# BEP32_12nutzen.net
KiCad netlist of a schematic drawn in EAGLE
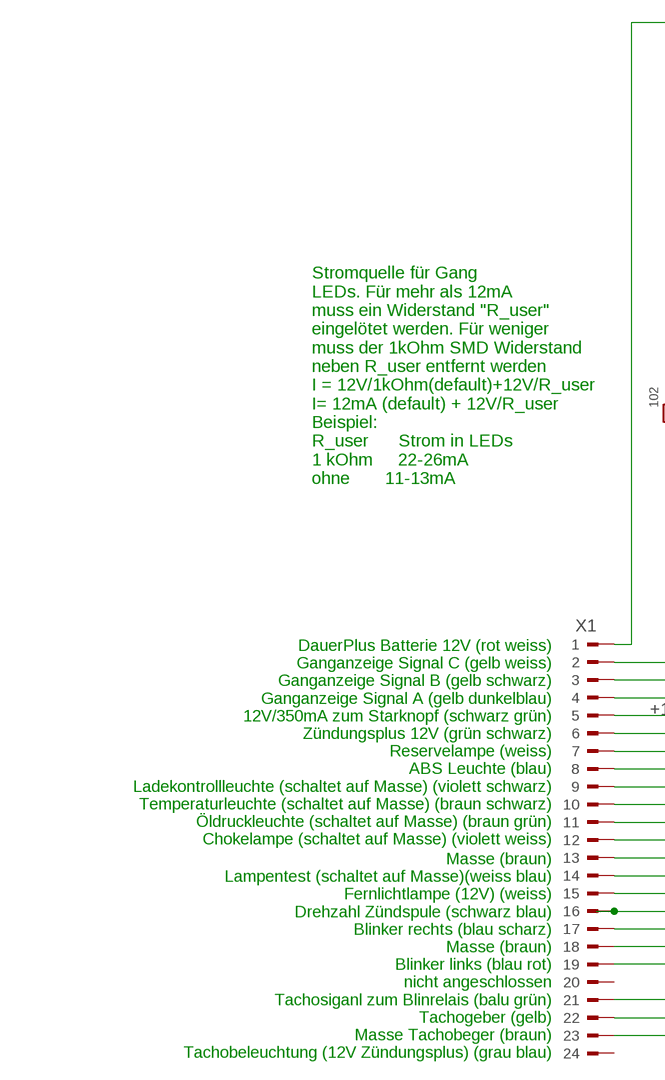
[diagram p0: schematic, sheet 1, part 1 of 2]
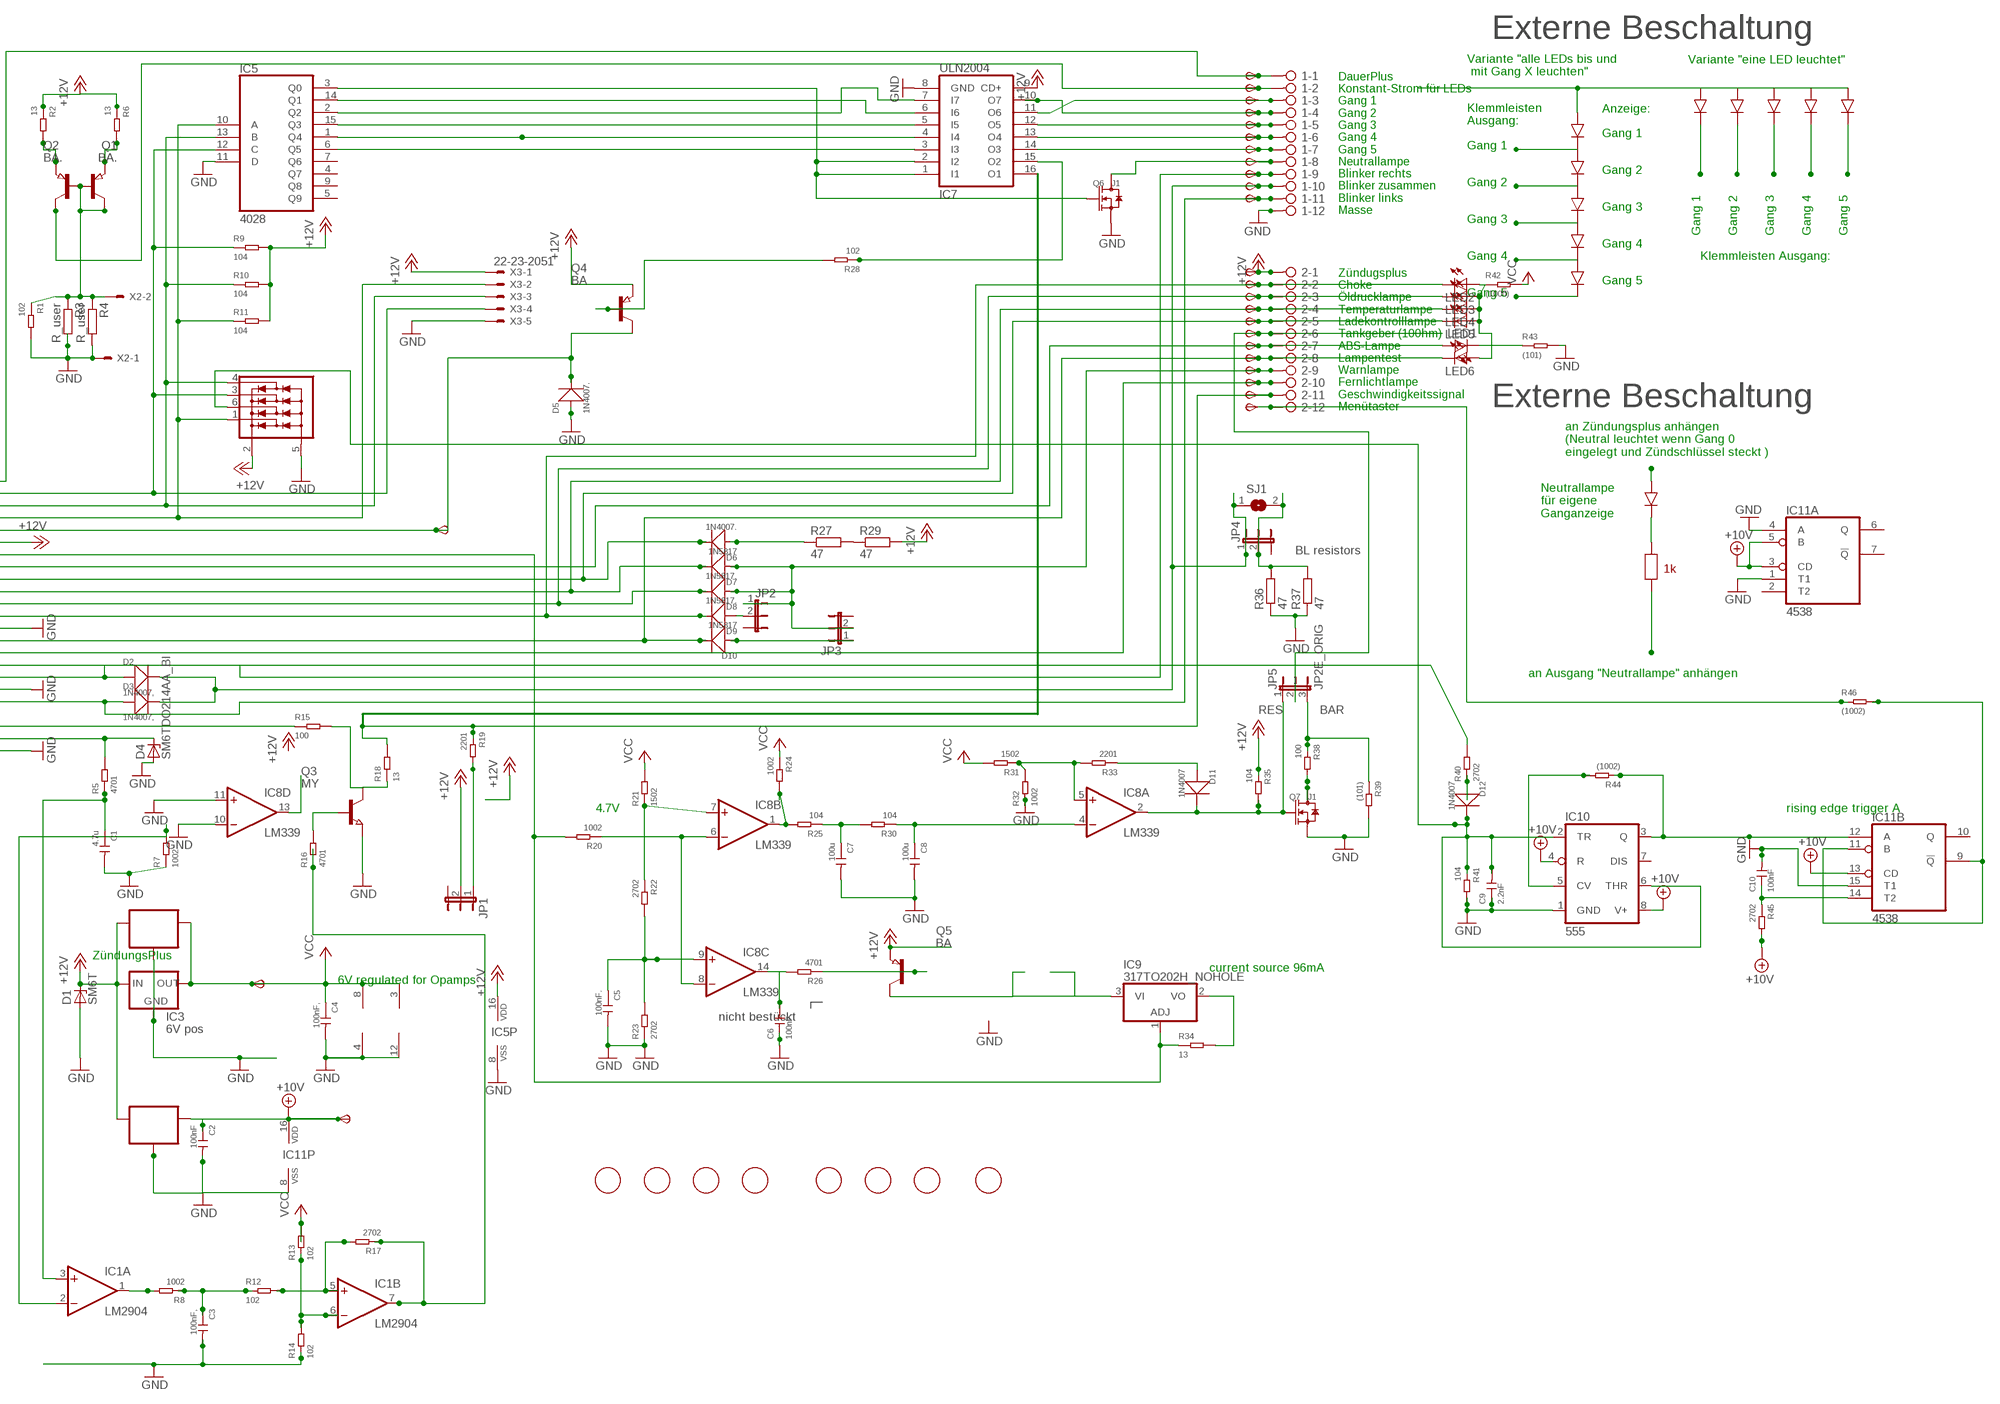
[diagram p1: schematic, sheet 1, part 2 of 2]
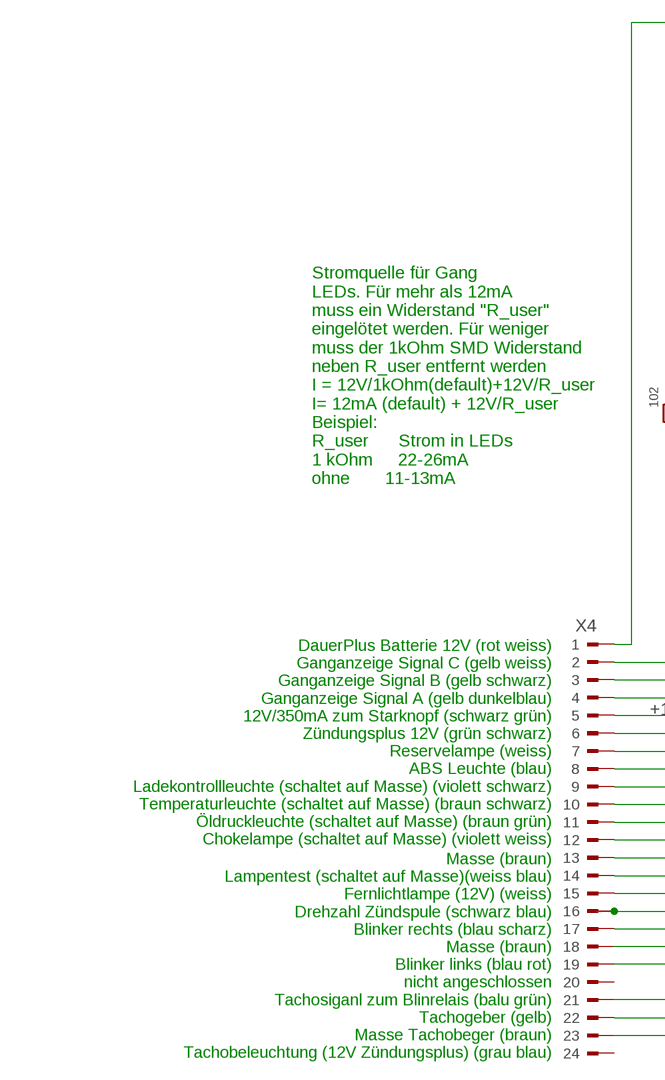
[diagram p2: schematic, sheet 2, part 1 of 2]
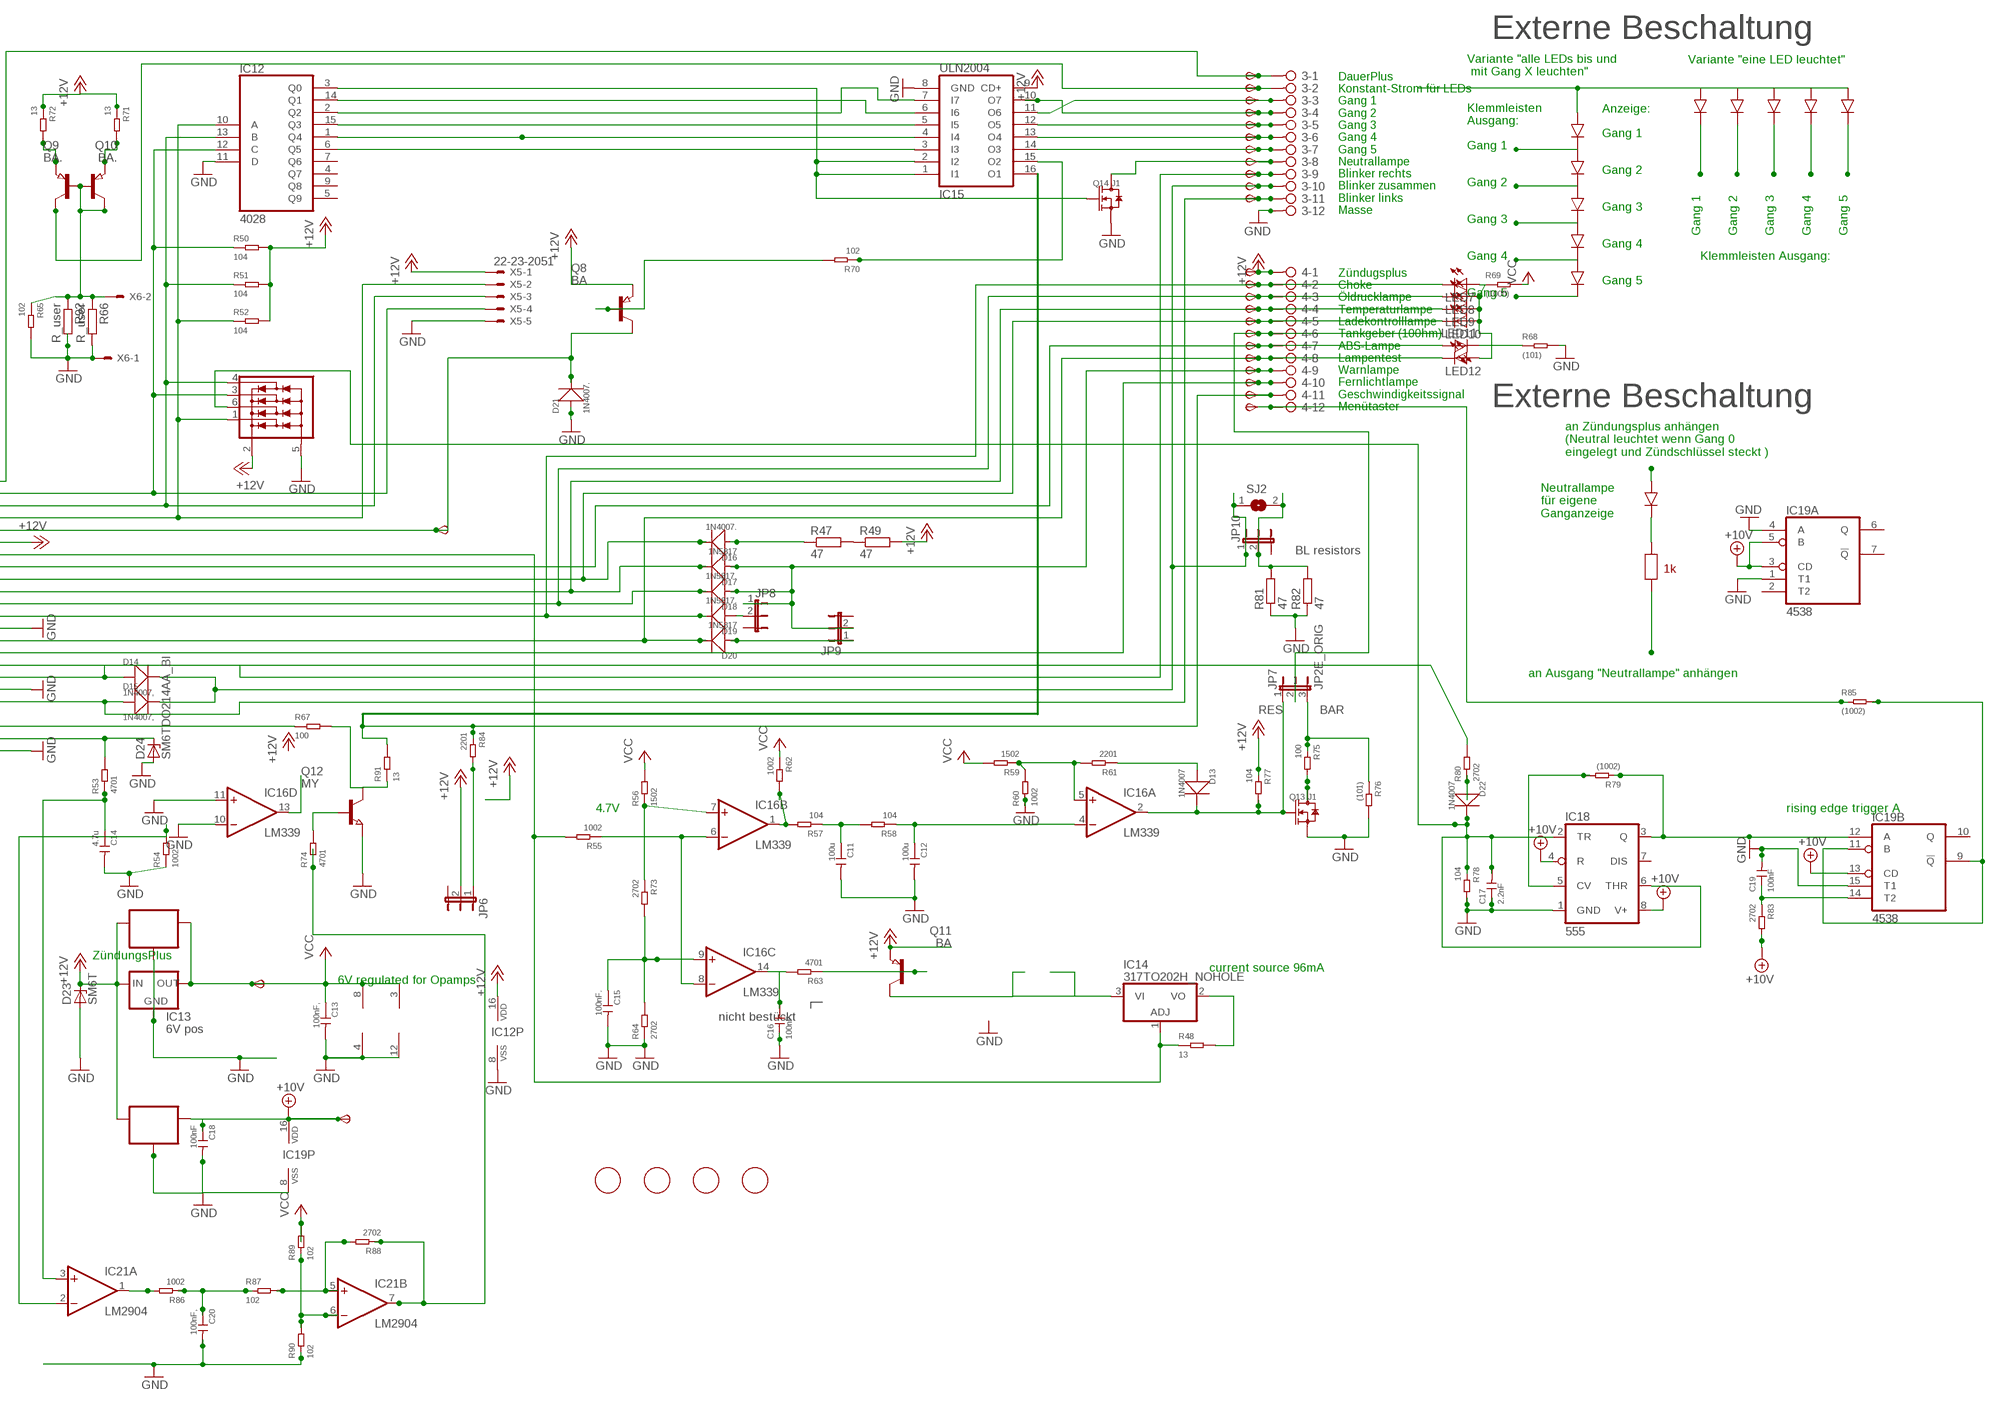
[diagram p3: schematic, sheet 2, part 2 of 2]
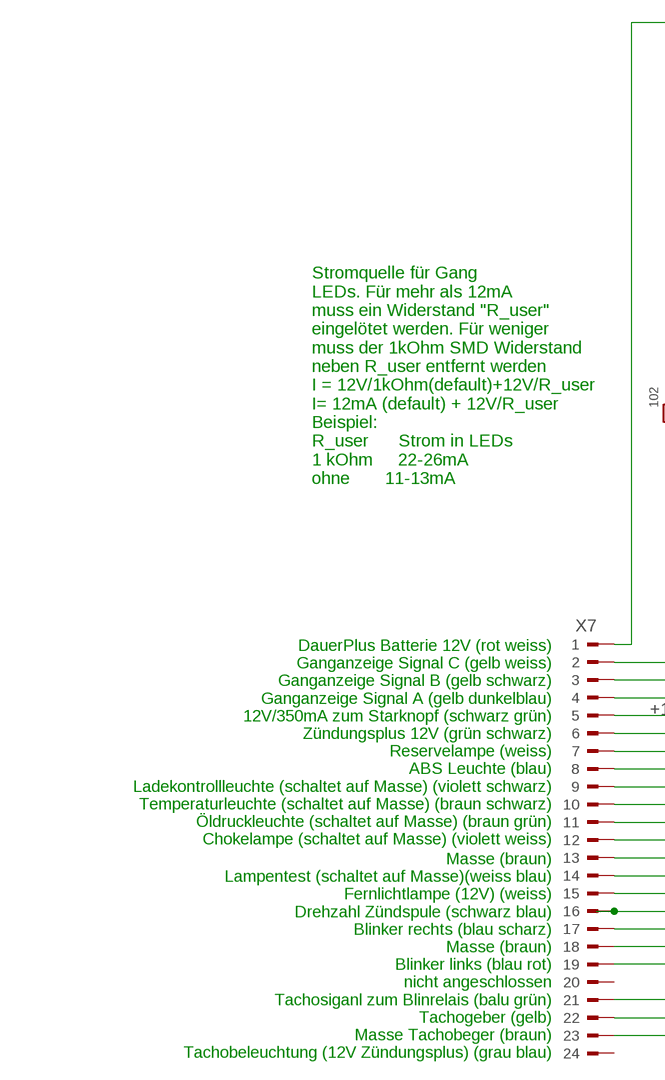
[diagram p4: schematic, sheet 3, part 1 of 2]
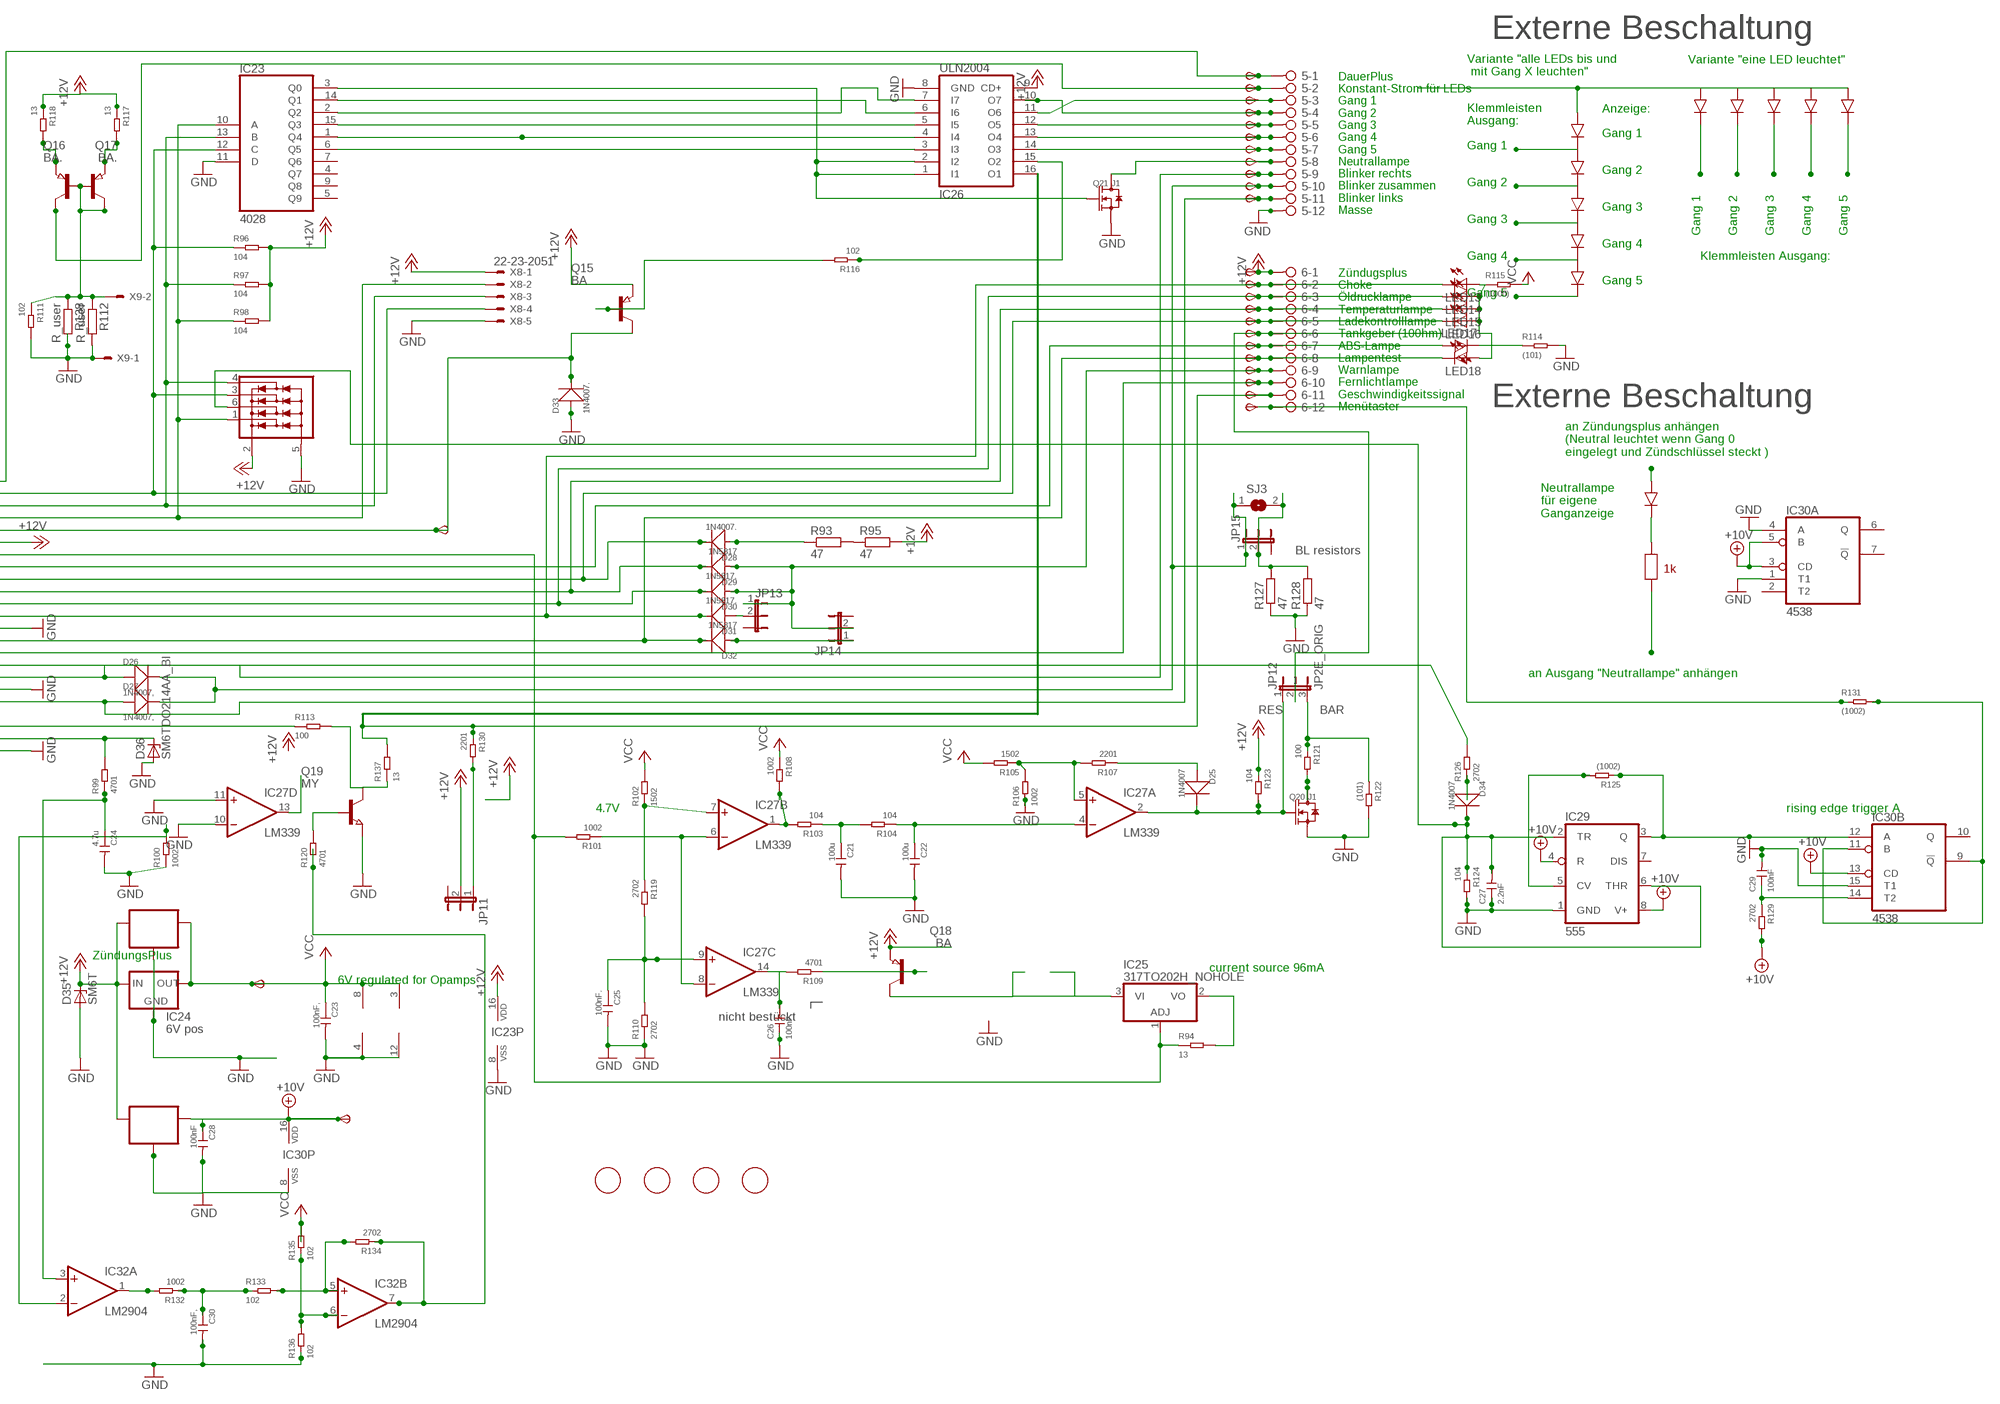
[diagram p5: schematic, sheet 3, part 2 of 2]
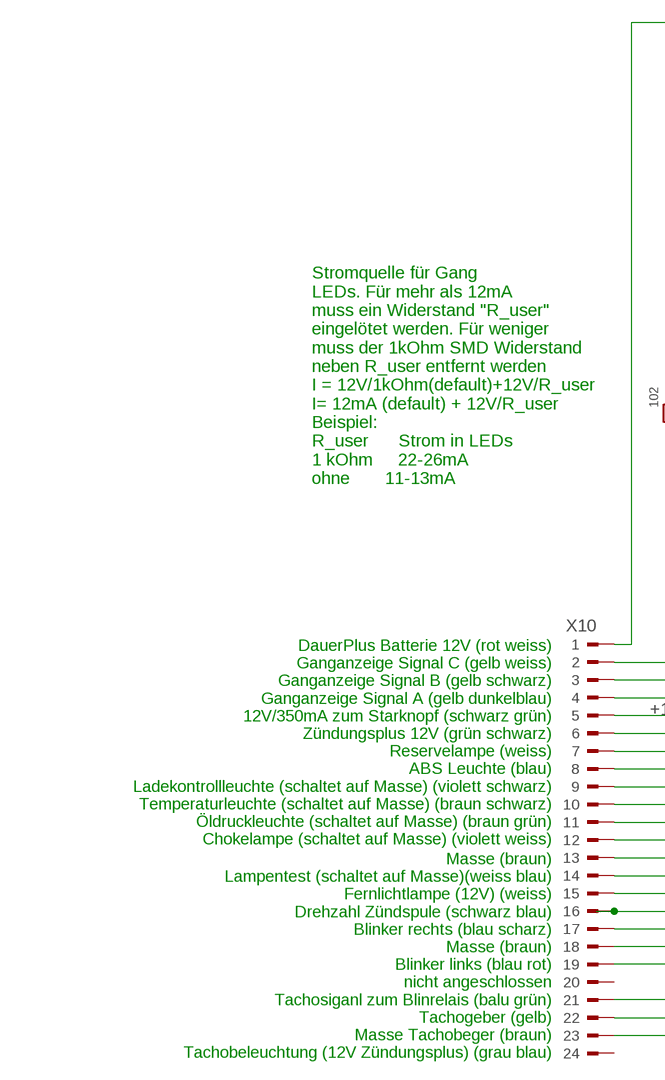
[diagram p6: schematic, sheet 4, part 1 of 2]
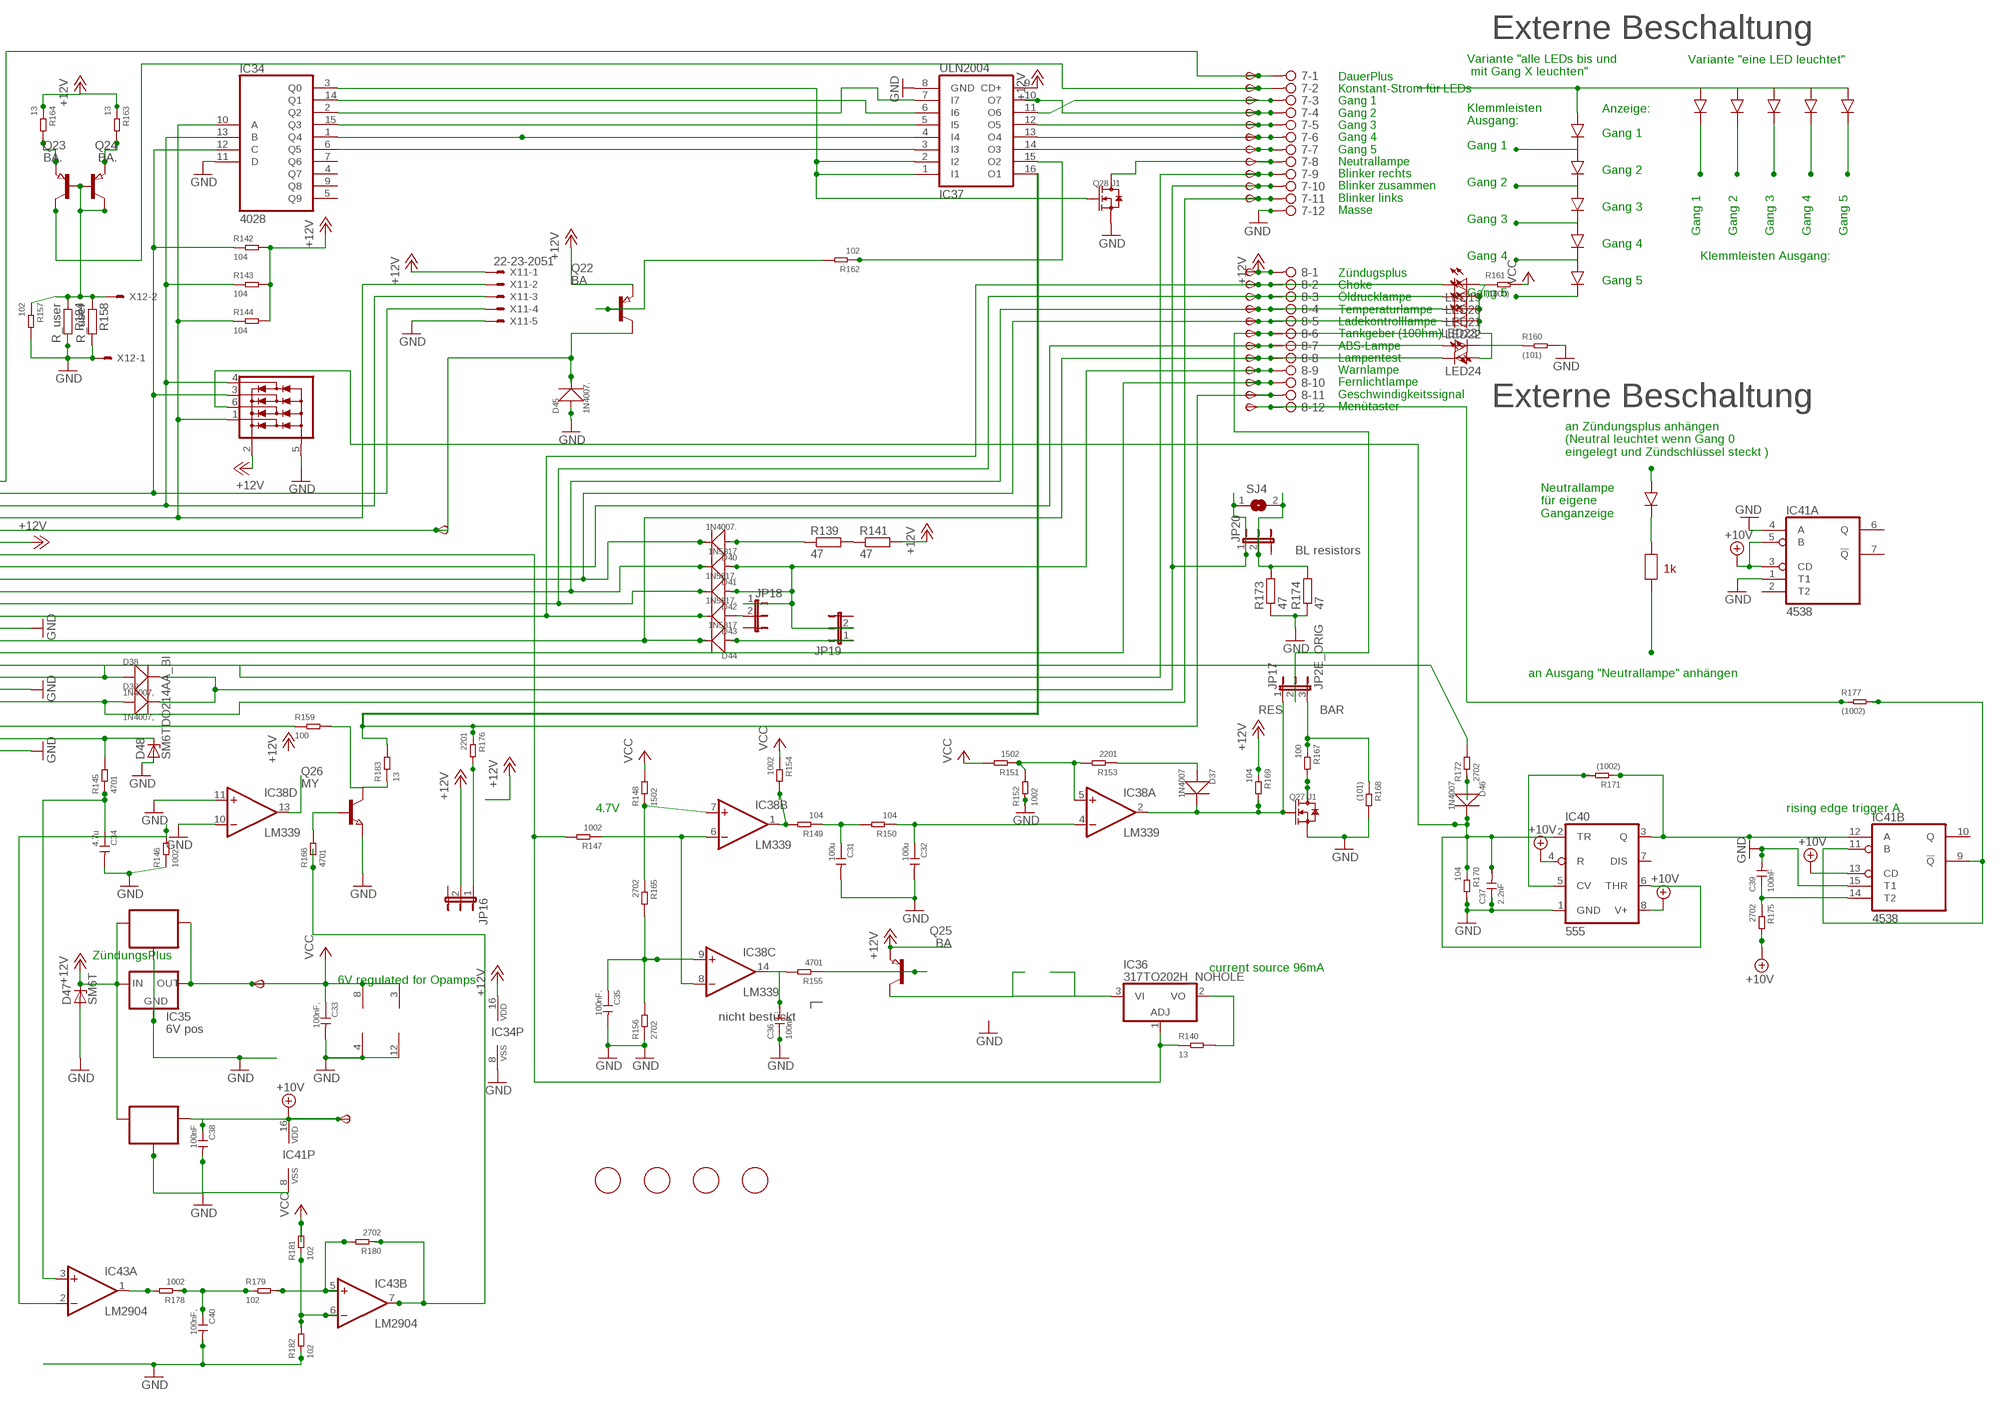
[diagram p7: schematic, sheet 4, part 2 of 2]
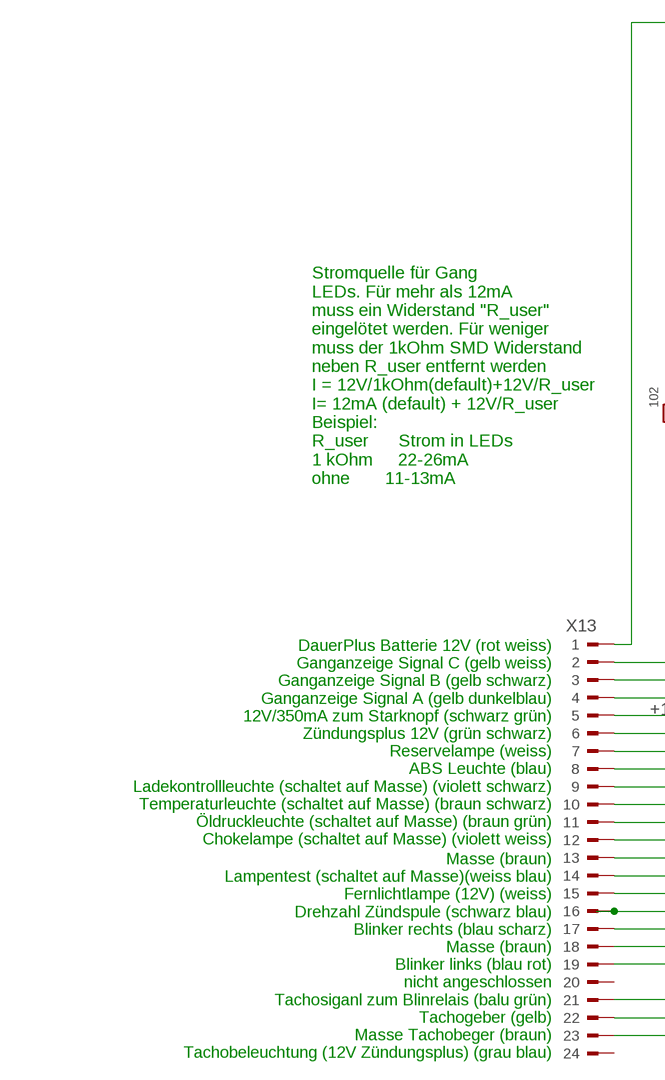
[diagram p8: schematic, sheet 5, part 1 of 2]
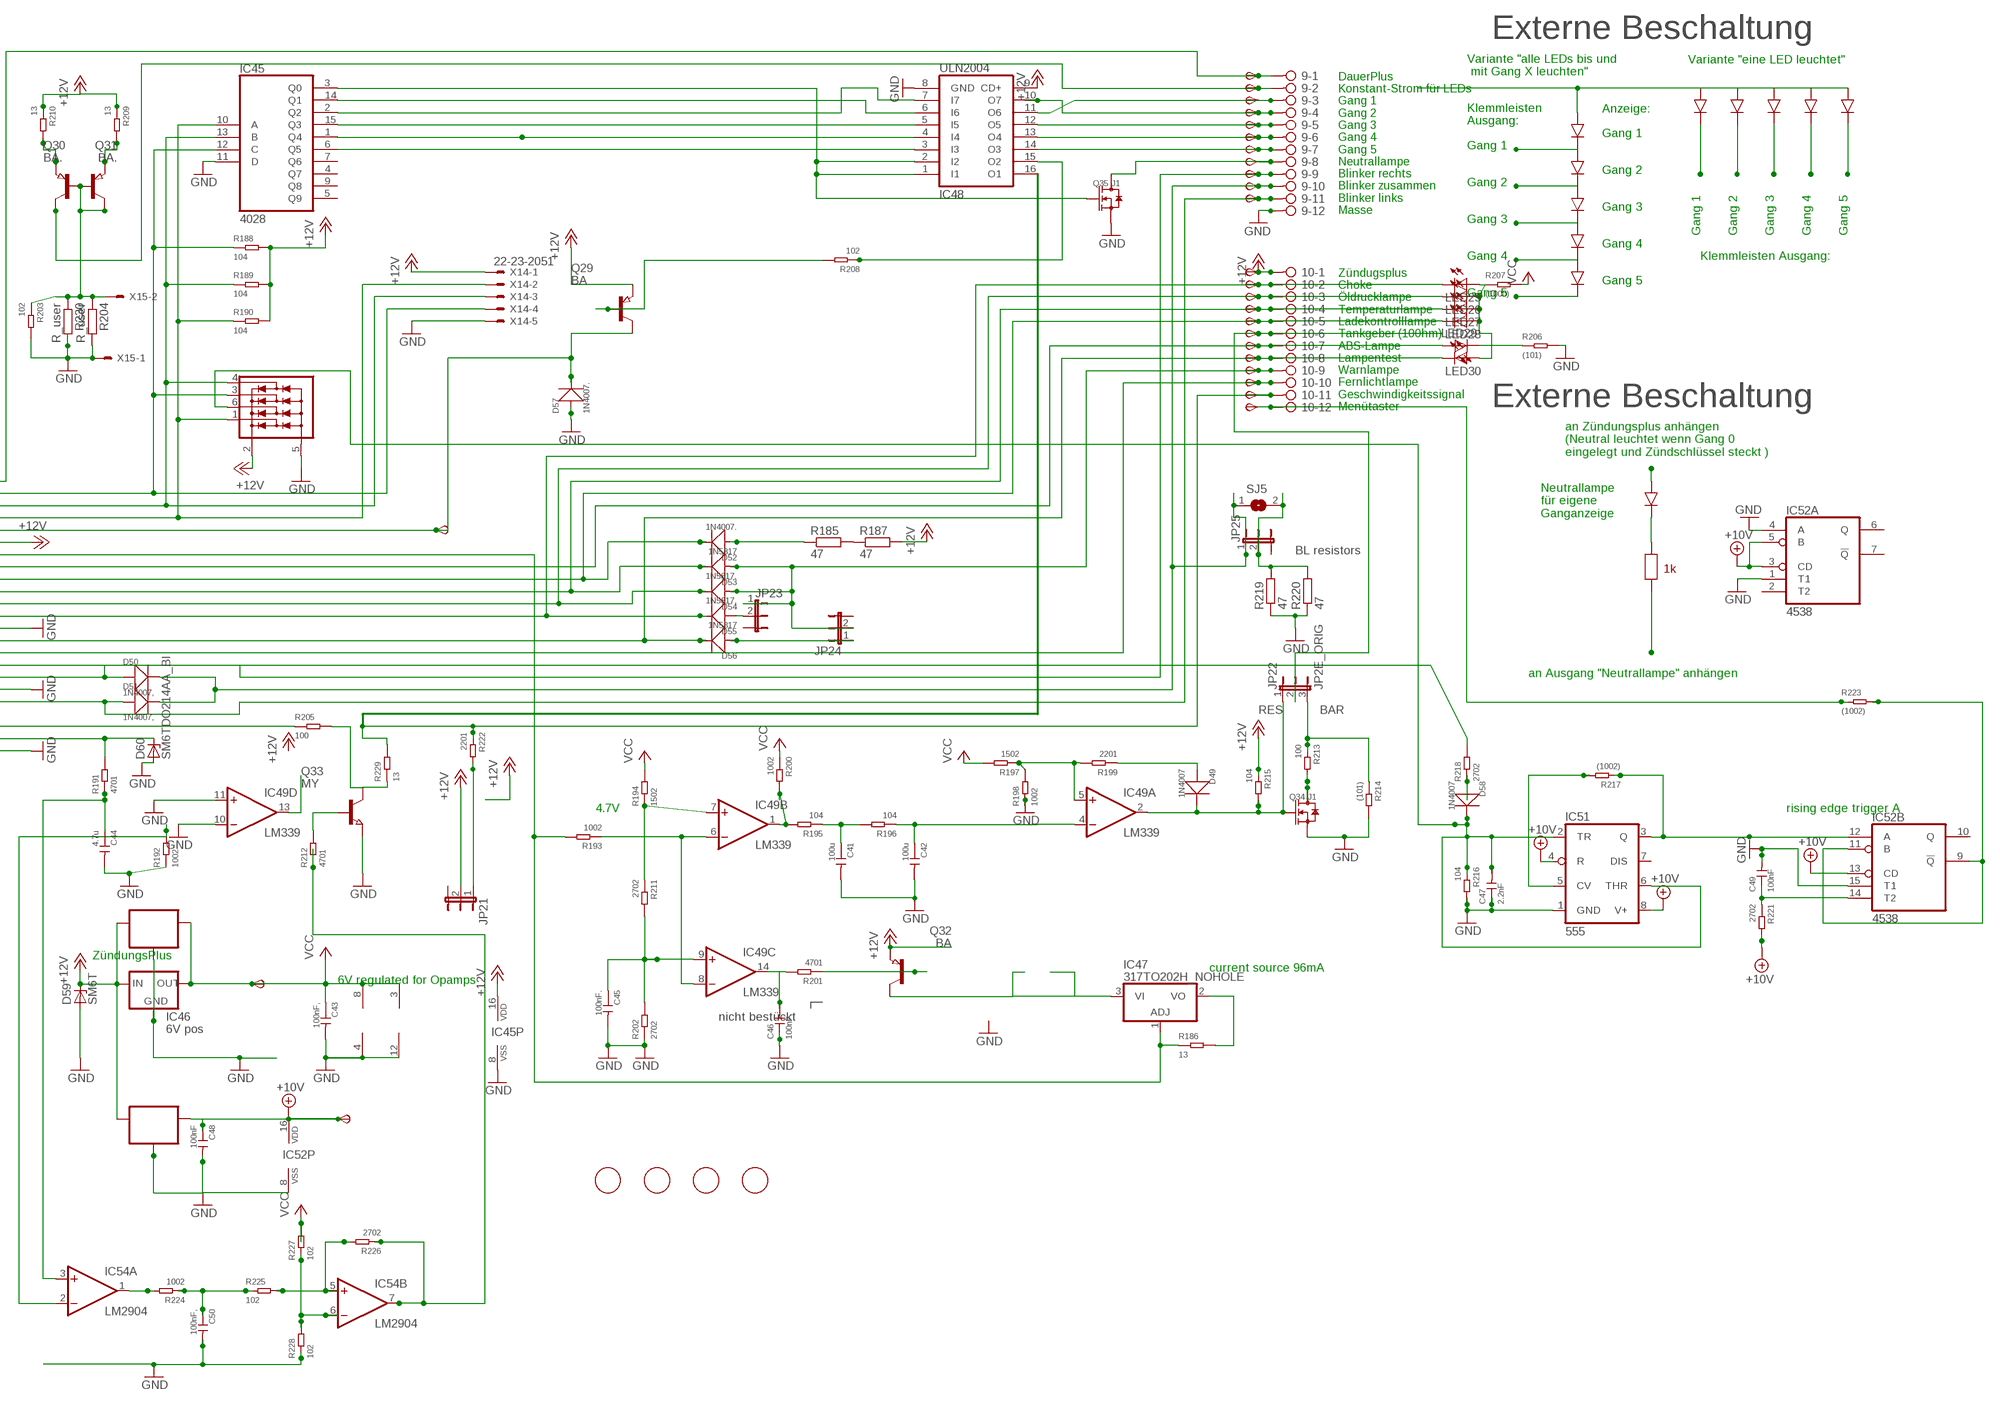
[diagram p9: schematic, sheet 5, part 2 of 2]
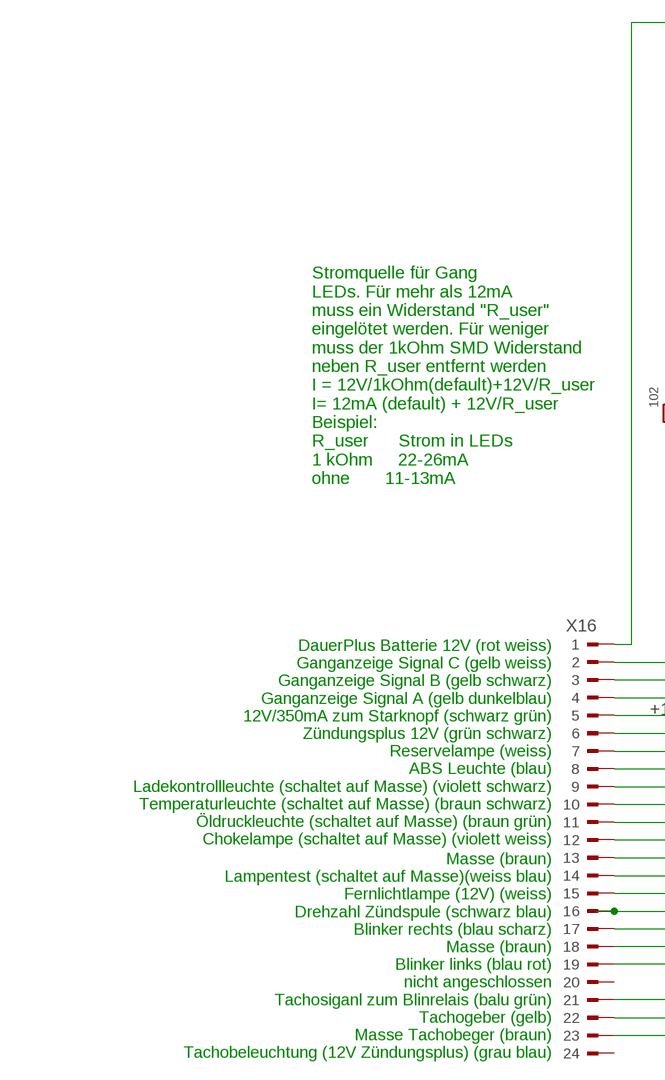
[diagram p10: schematic, sheet 6, part 1 of 2]
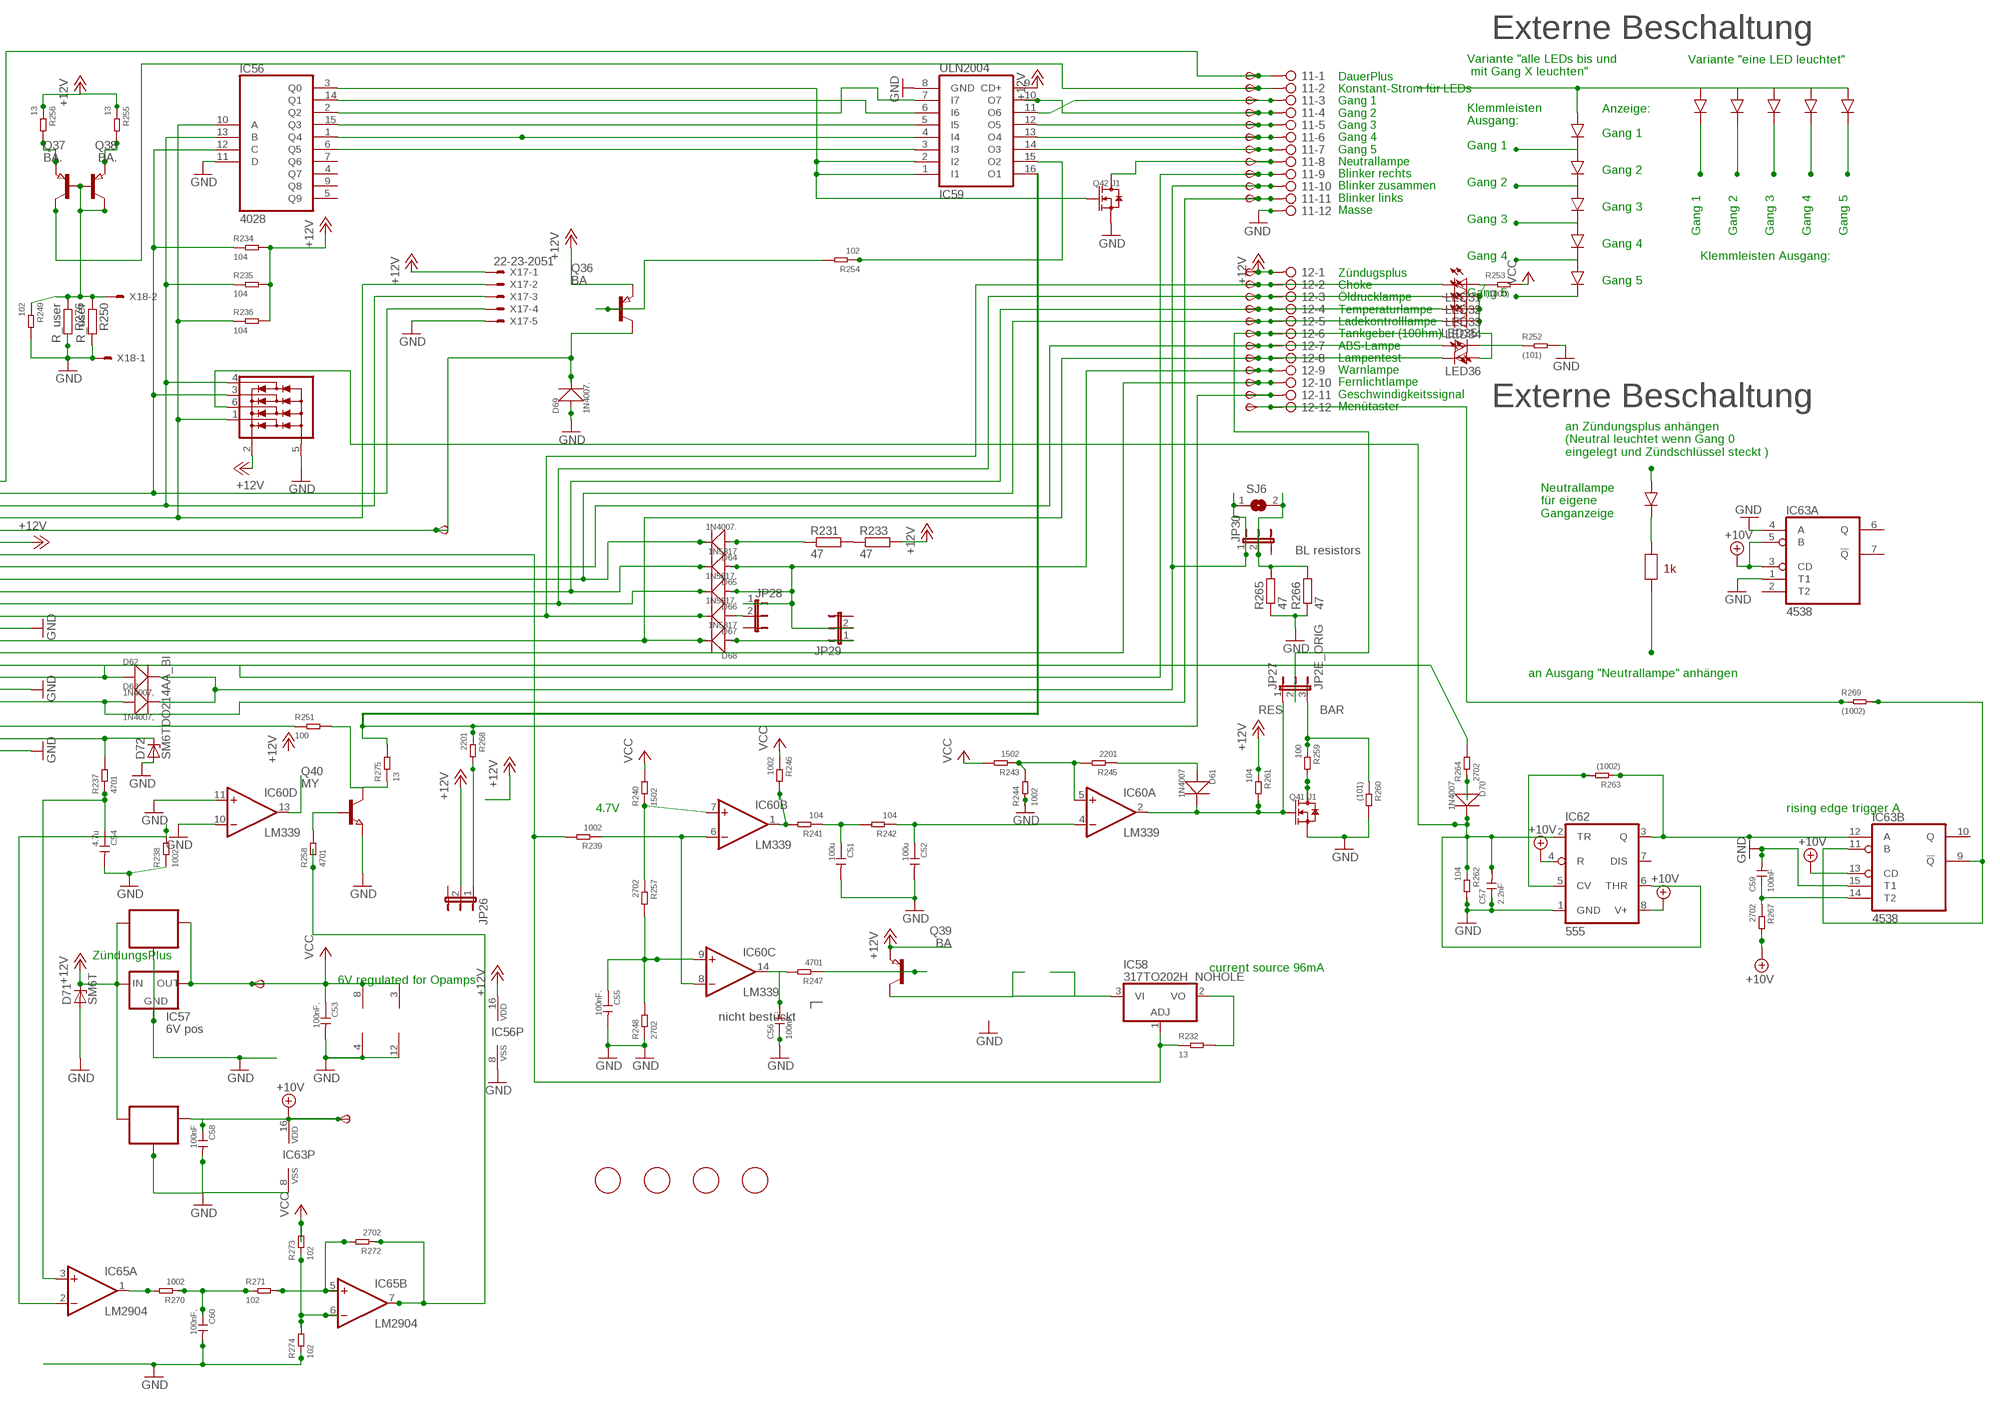
[diagram p11: schematic, sheet 6, part 2 of 2]
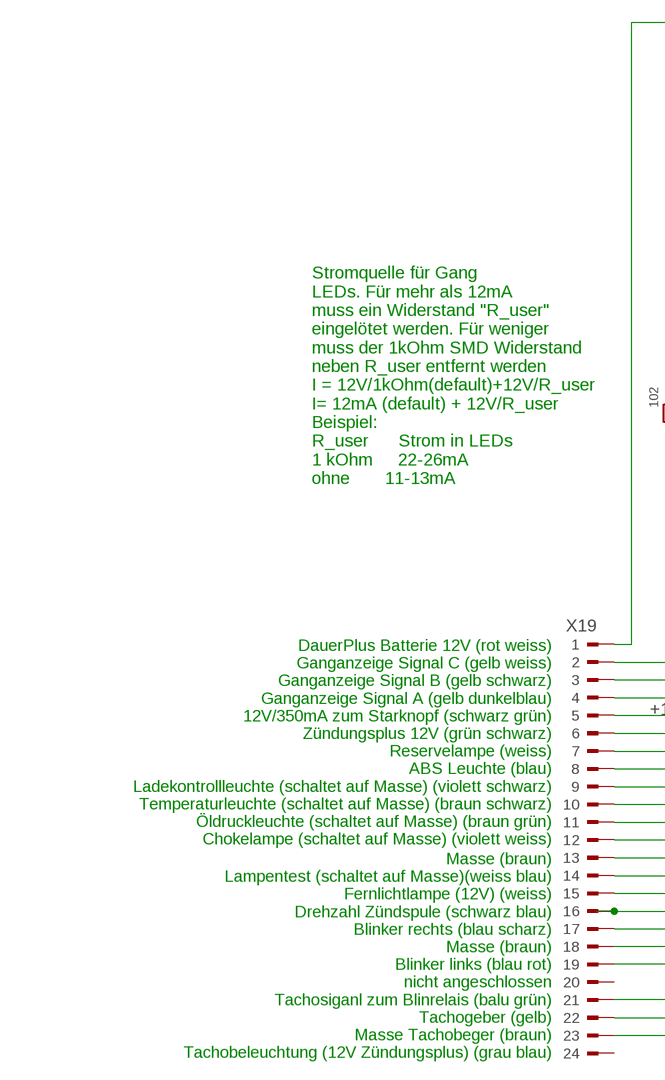
[diagram p12: schematic, sheet 7, part 1 of 2]
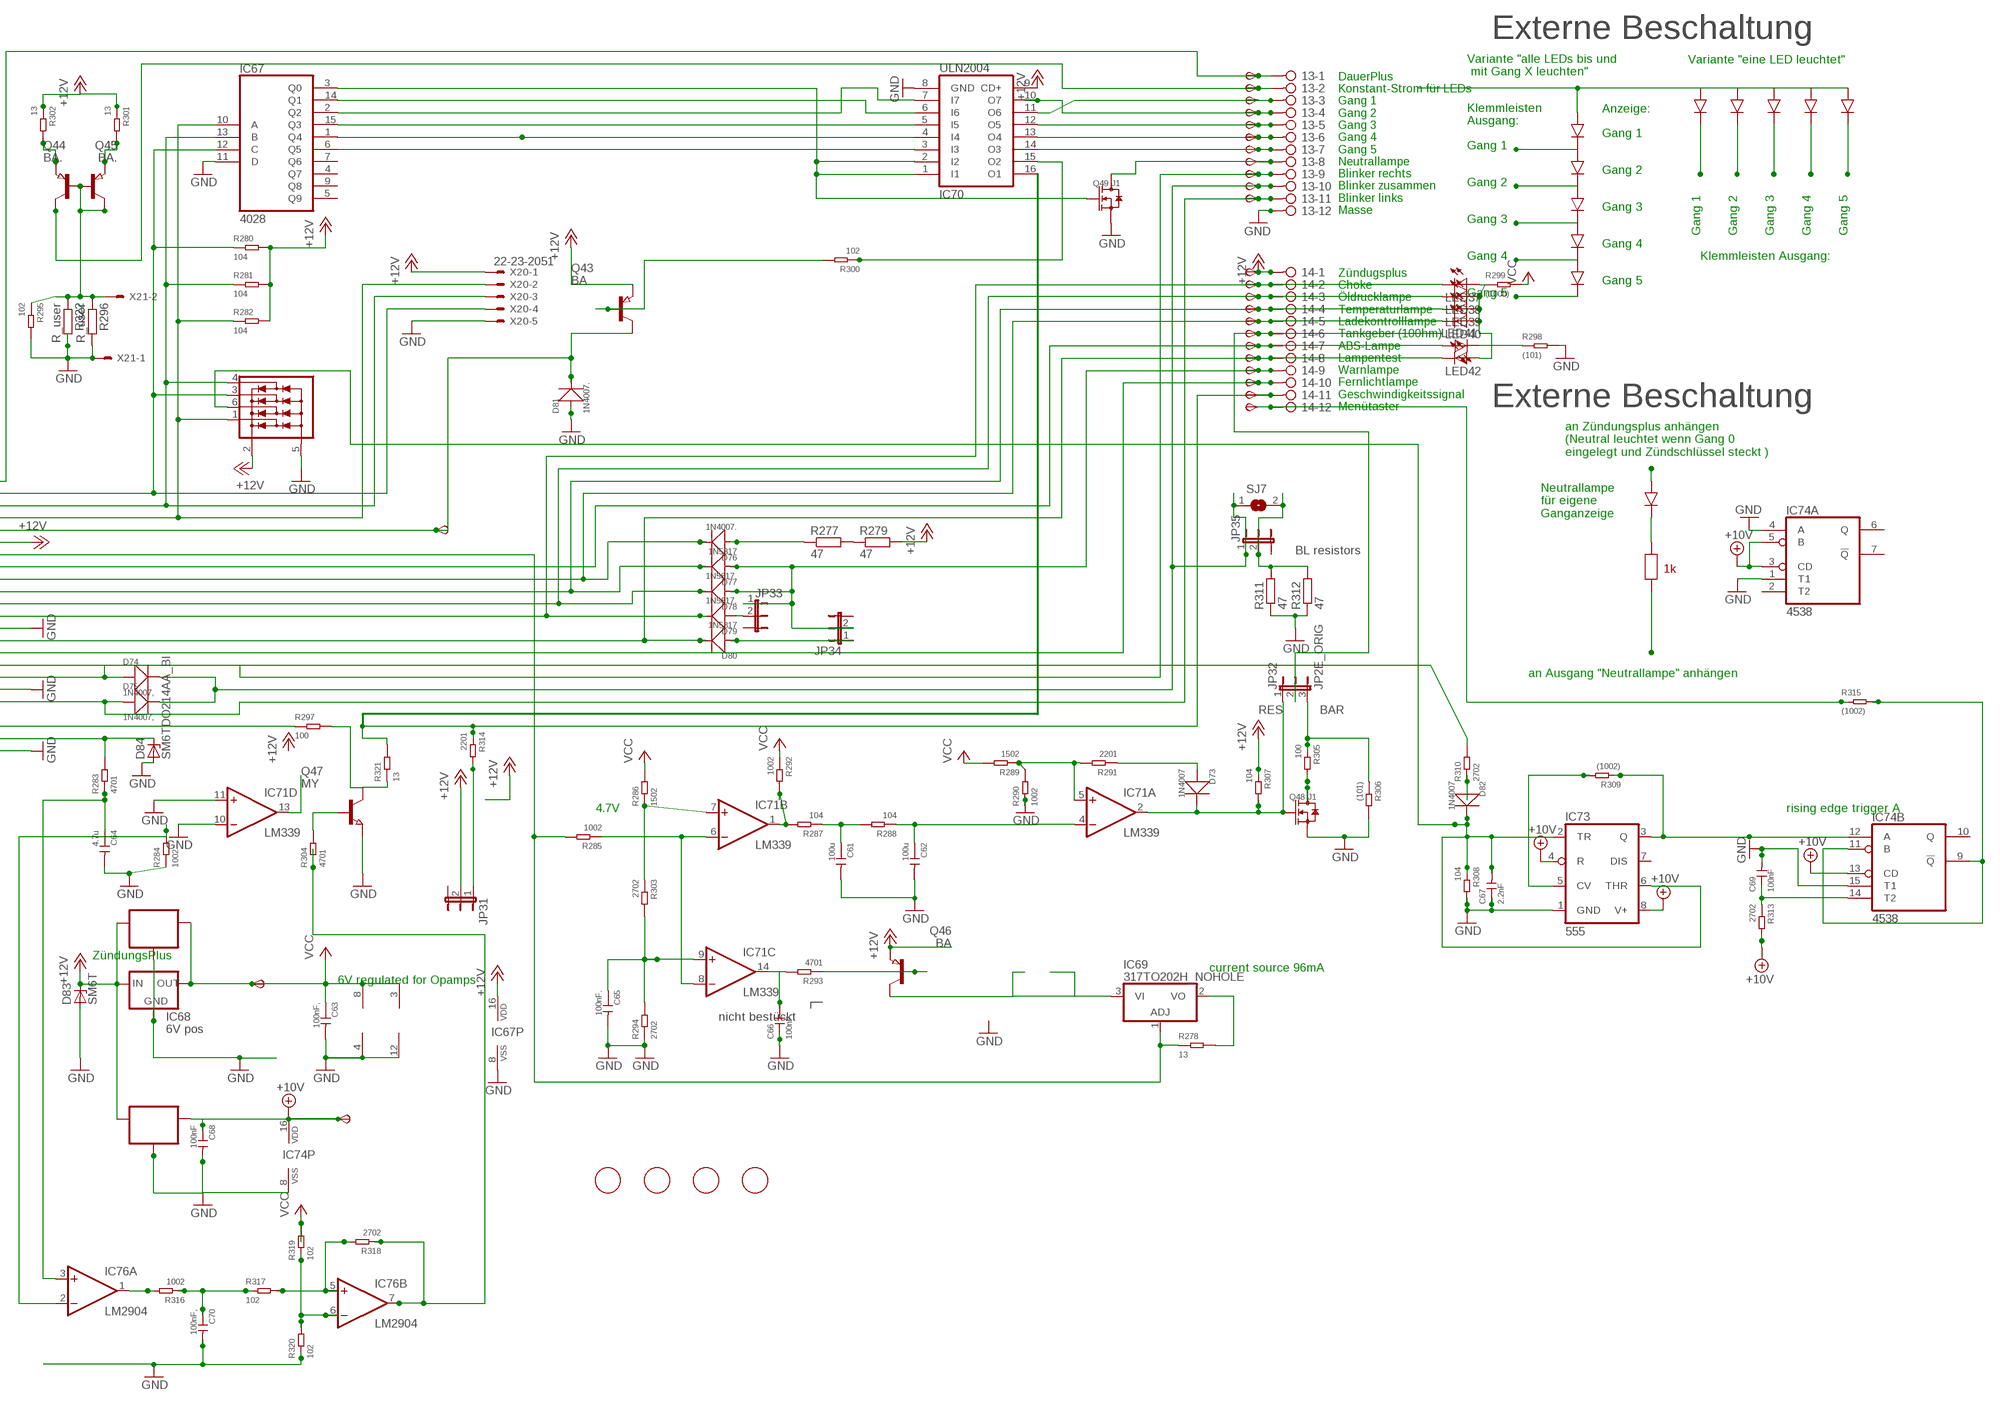
[diagram p13: schematic, sheet 7, part 2 of 2]
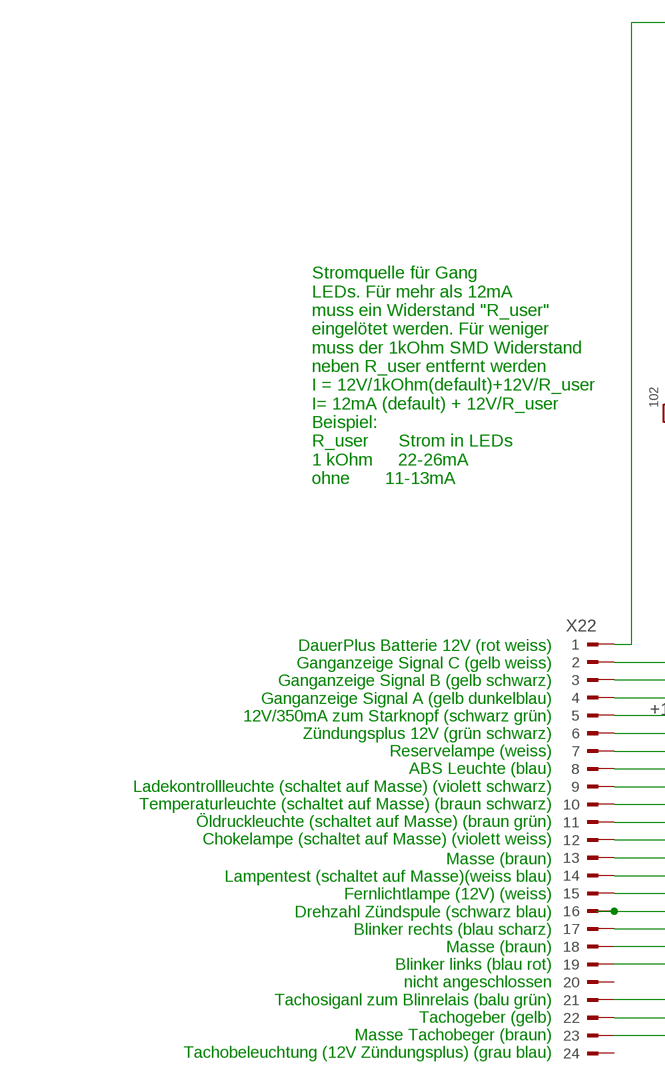
[diagram p14: schematic, sheet 8, part 1 of 2]
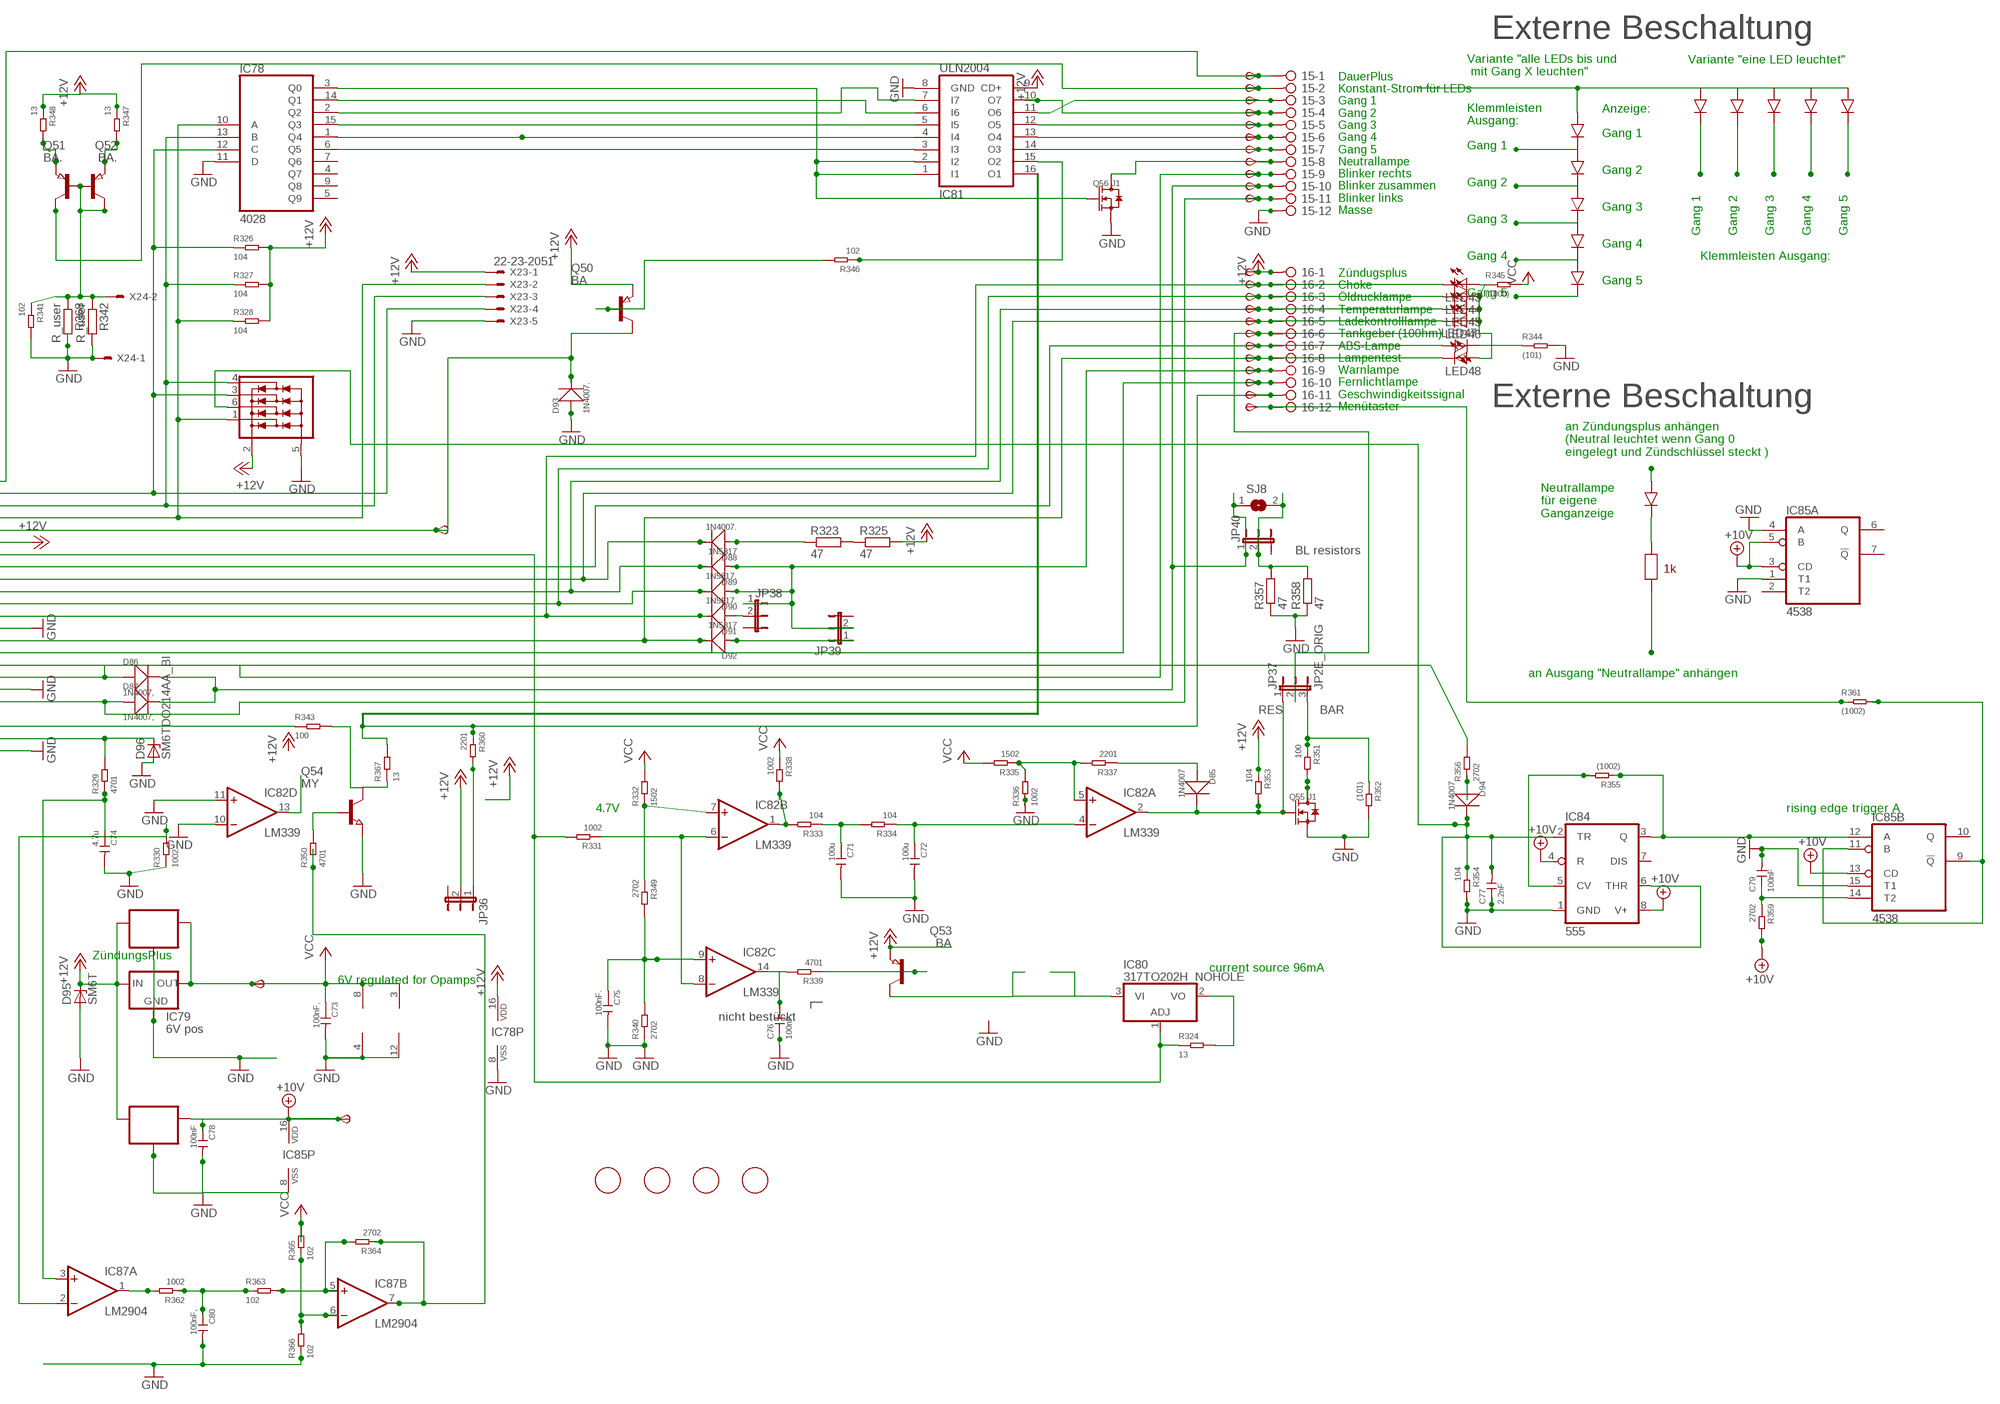
[diagram p15: schematic, sheet 8, part 2 of 2]
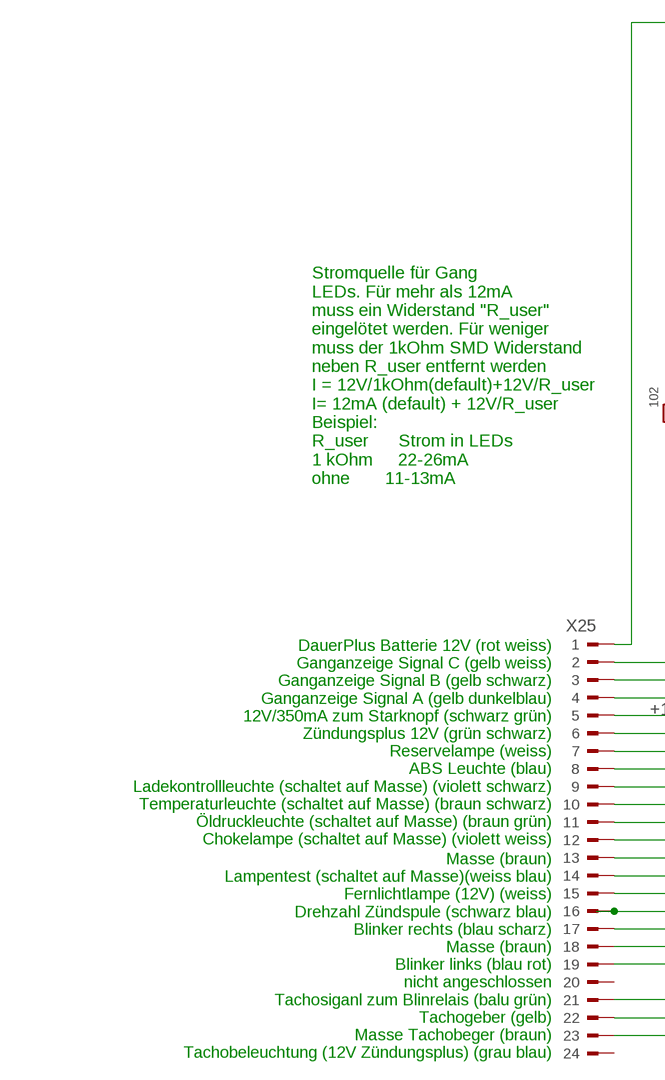
[diagram p16: schematic, sheet 9, part 1 of 2]
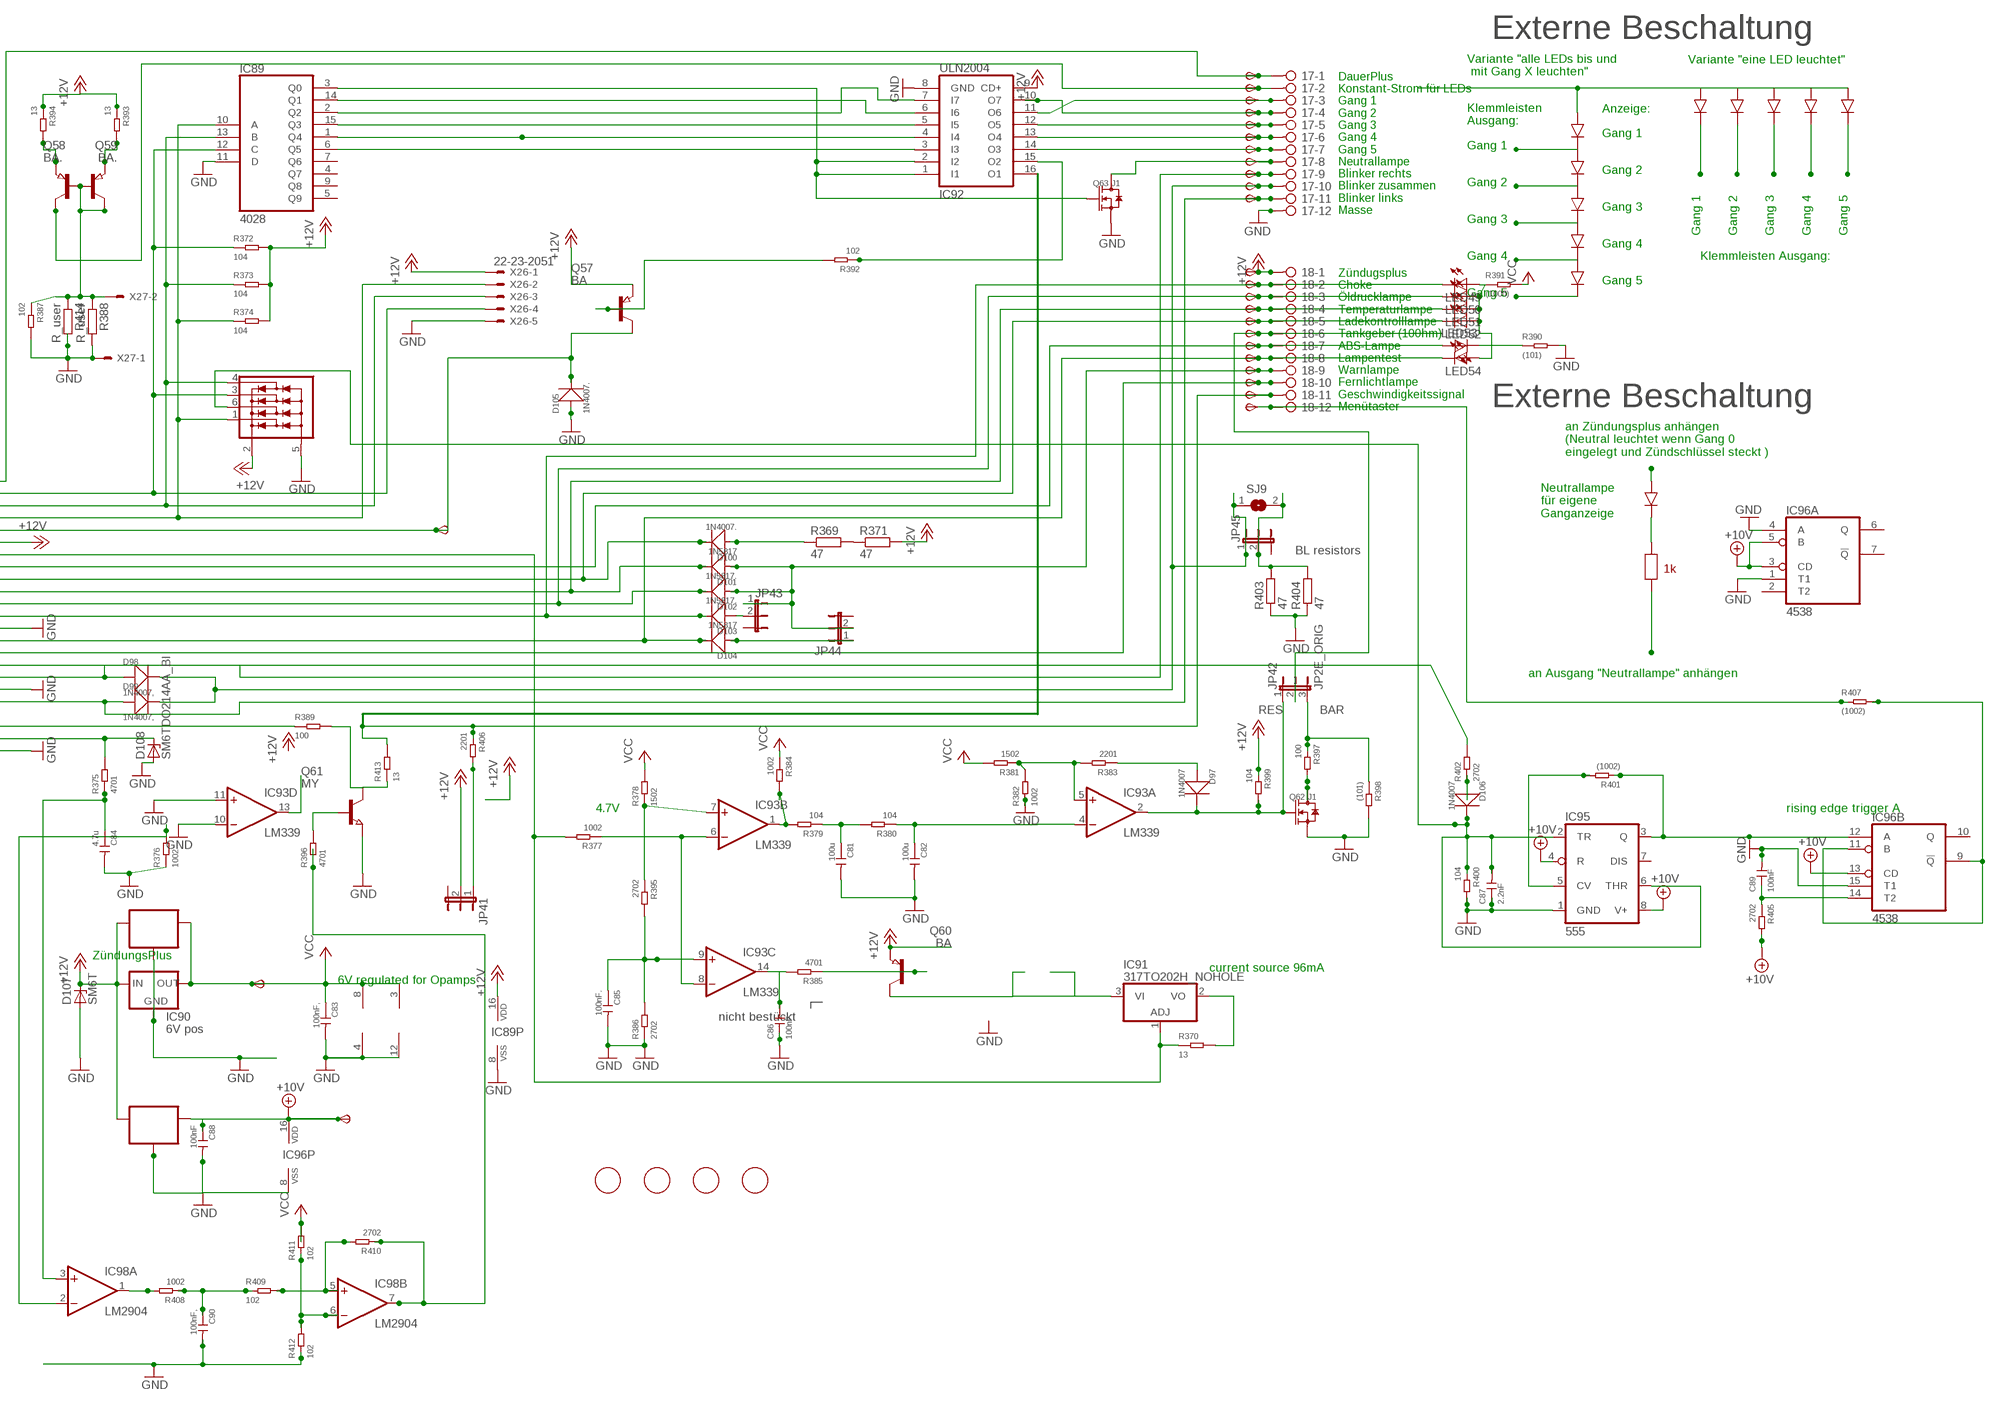
[diagram p17: schematic, sheet 9, part 2 of 2]
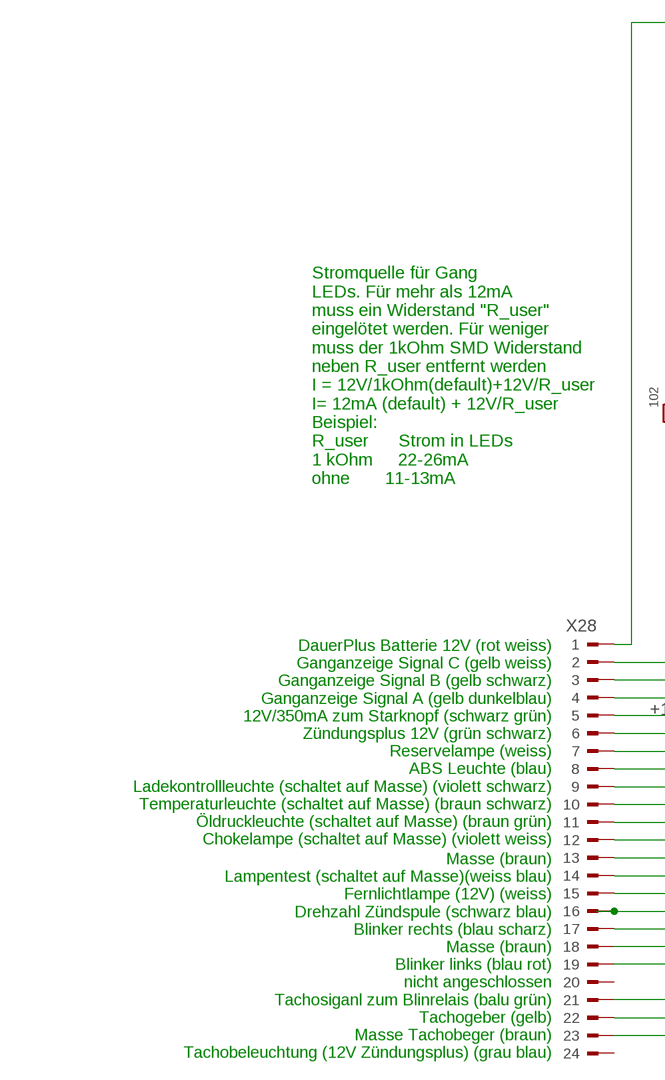
[diagram p18: schematic, sheet 10, part 1 of 2]
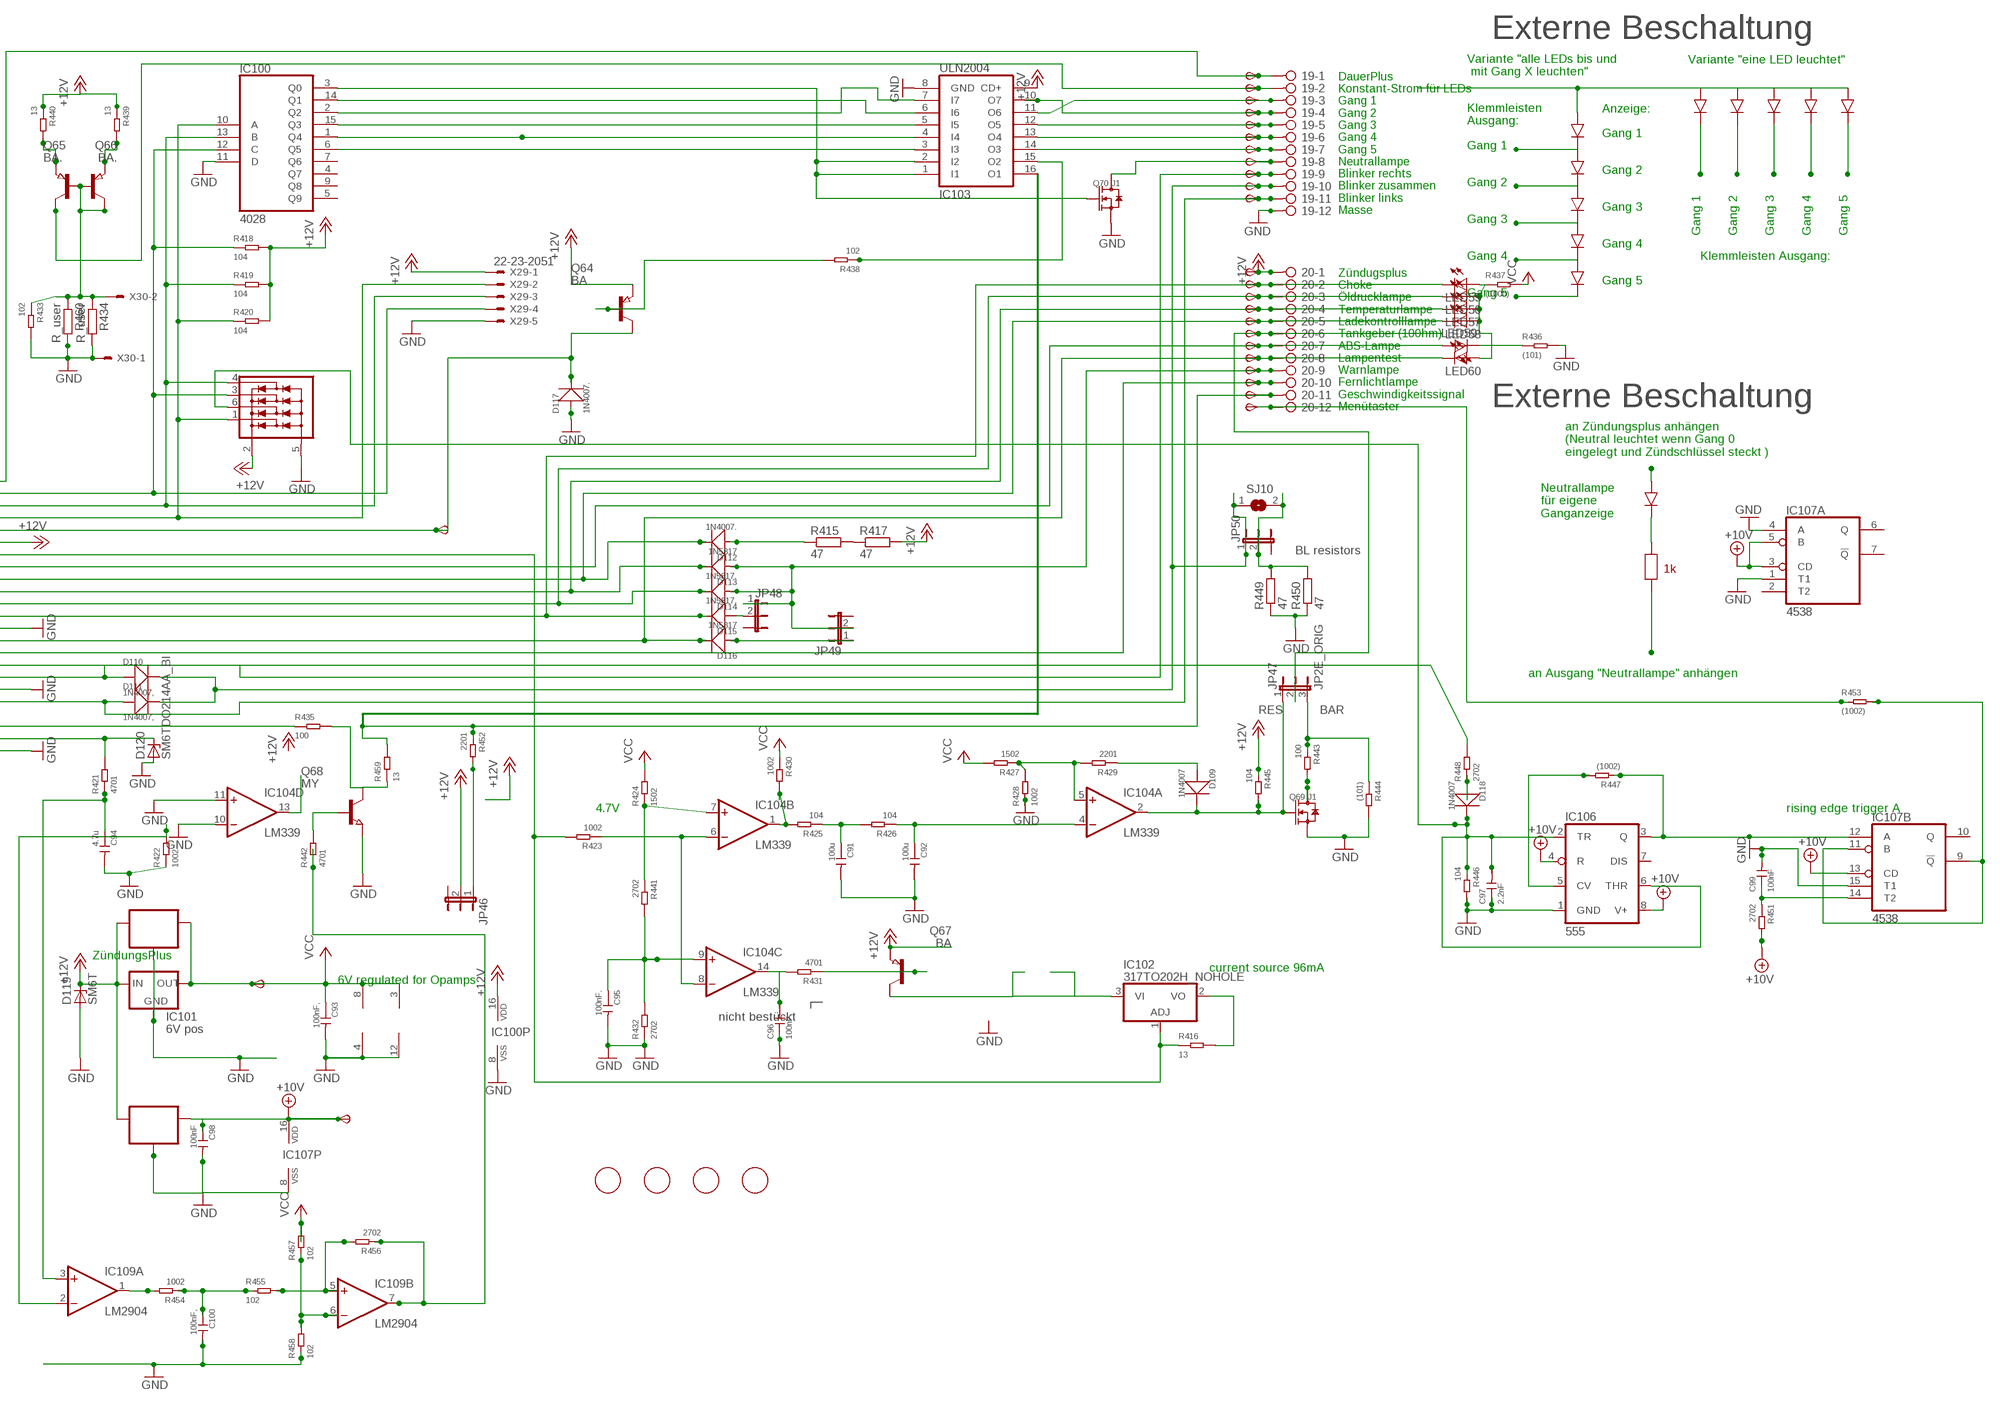
[diagram p19: schematic, sheet 10, part 2 of 2]
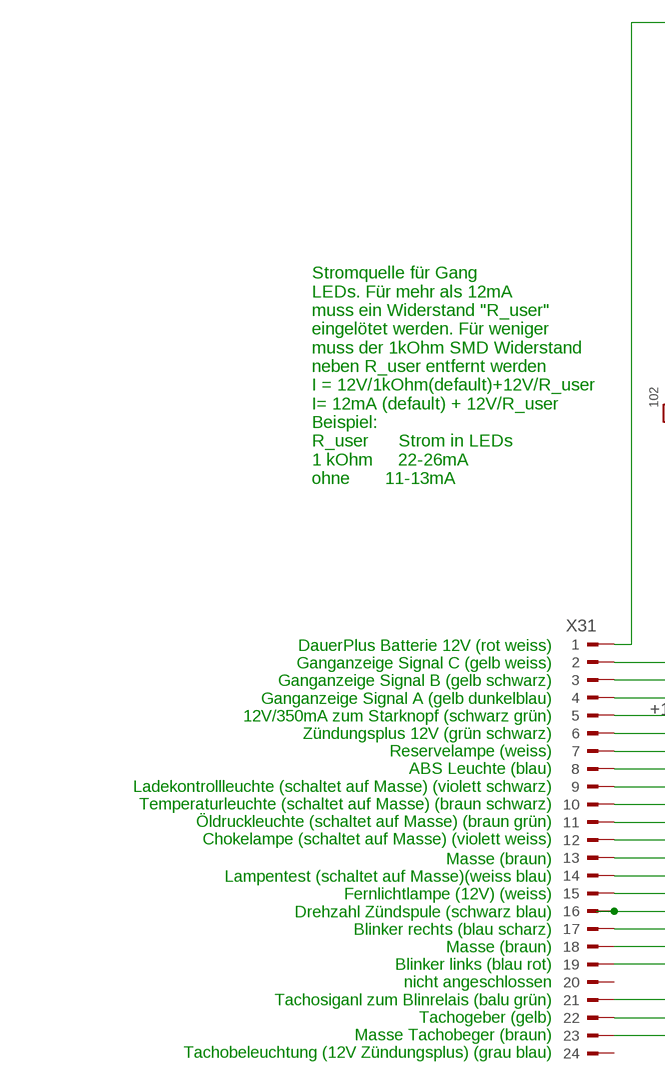
[diagram p20: schematic, sheet 11, part 1 of 2]
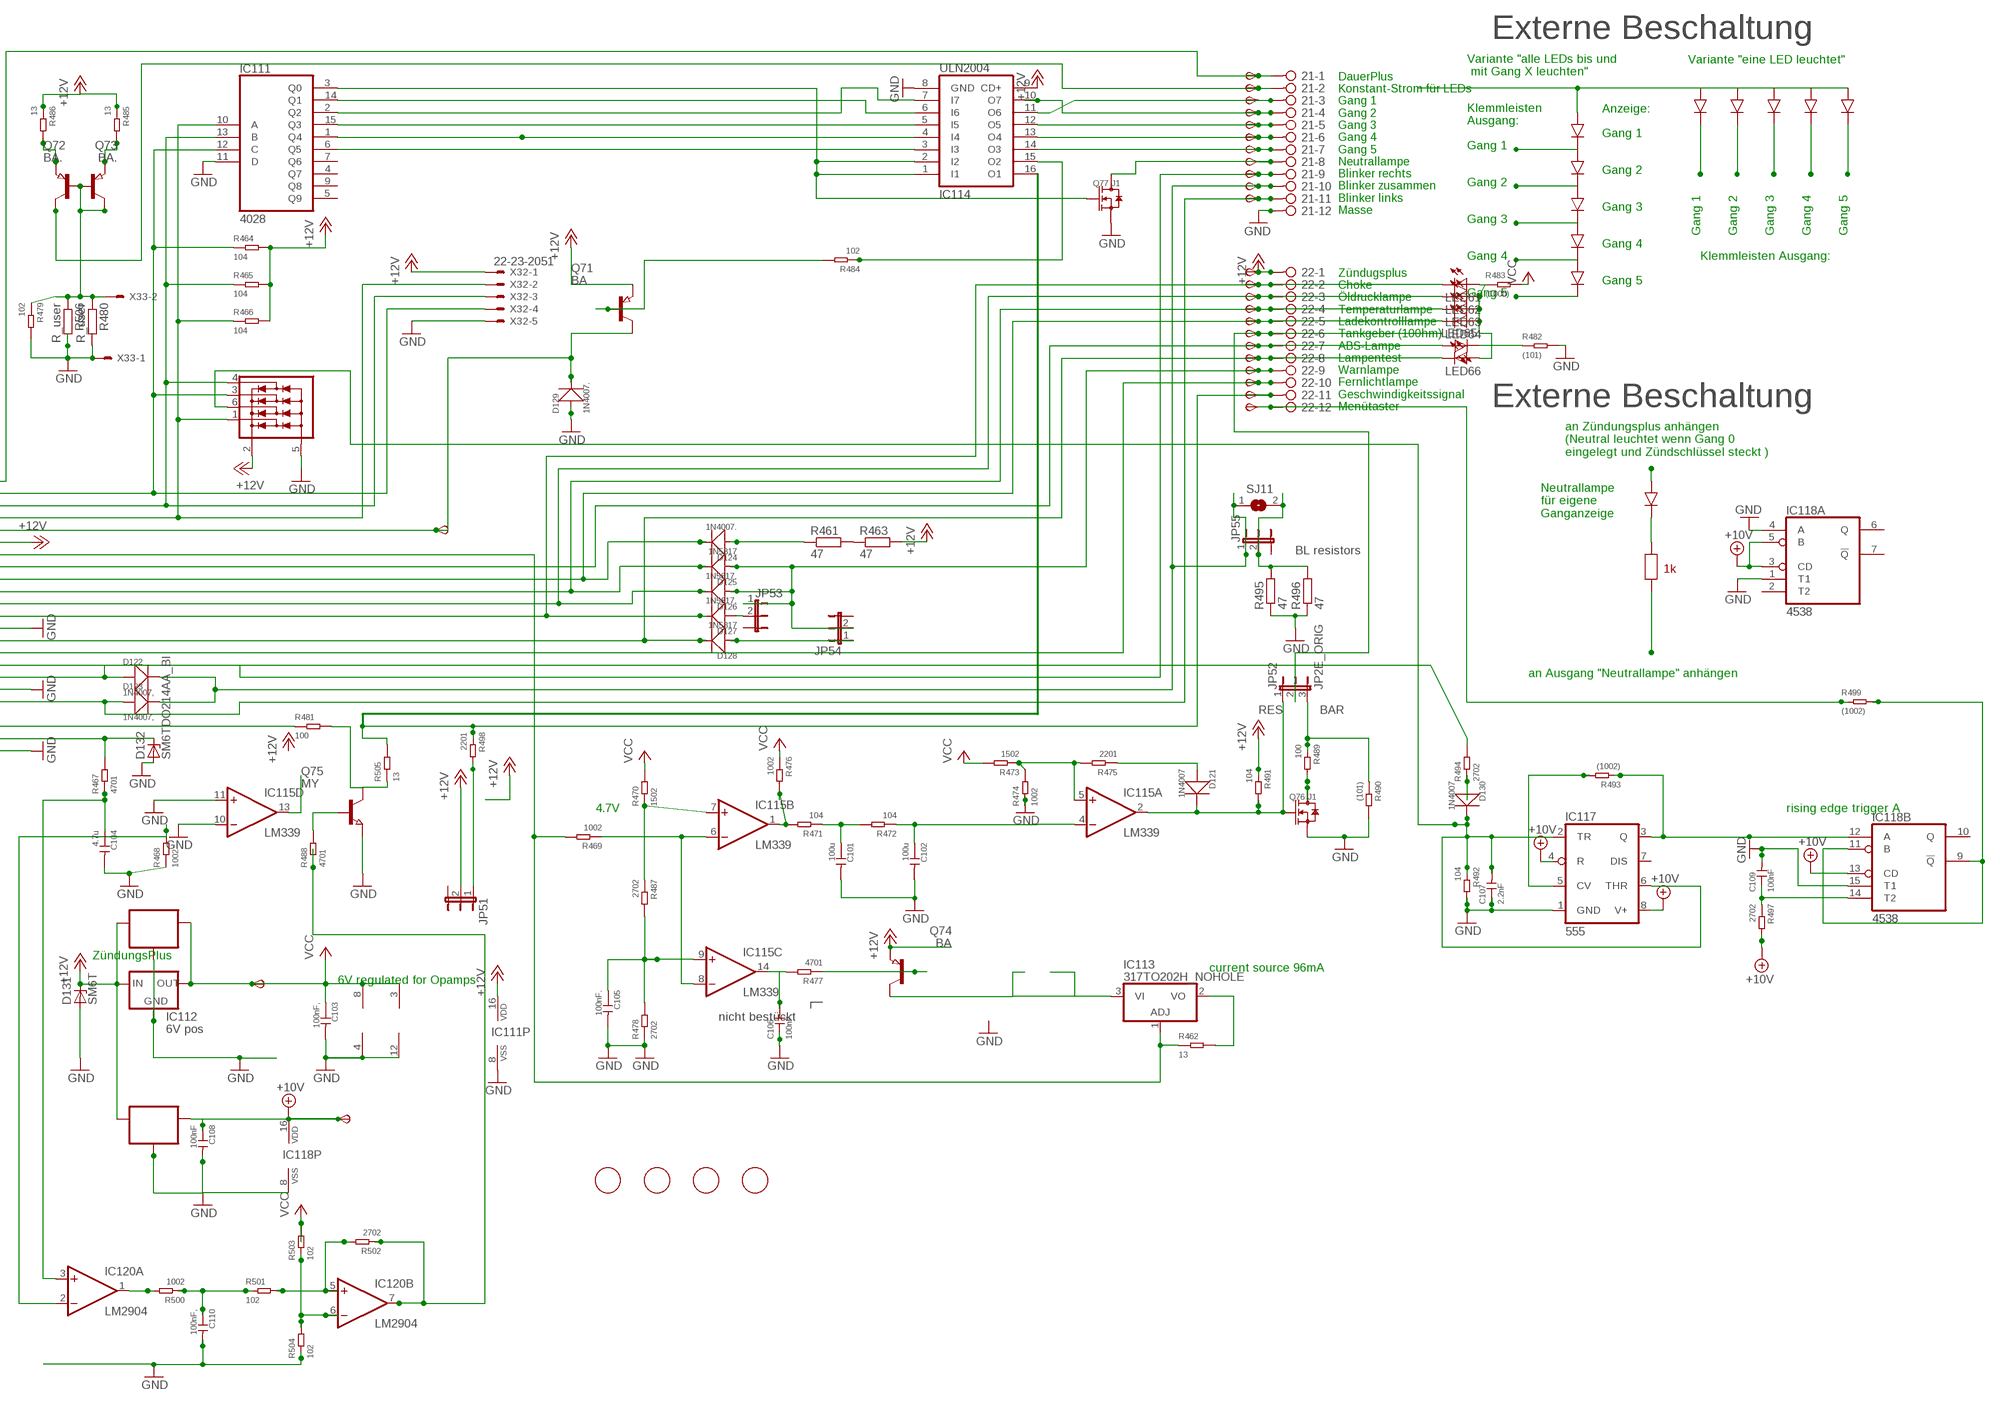
[diagram p21: schematic, sheet 11, part 2 of 2]
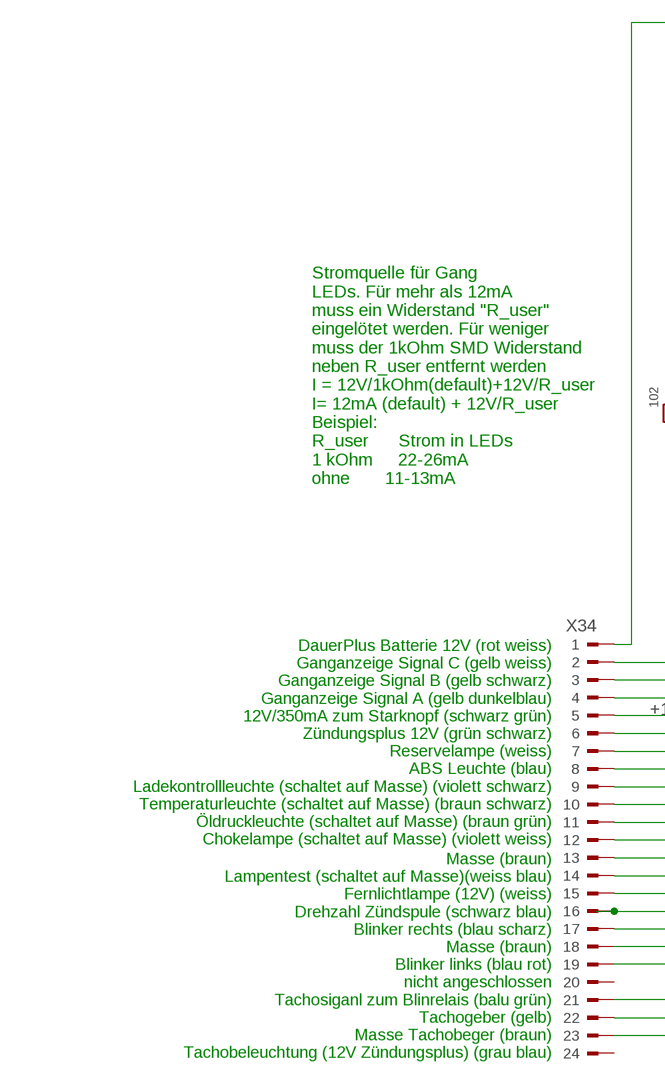
[diagram p22: schematic, sheet 12, part 1 of 2]
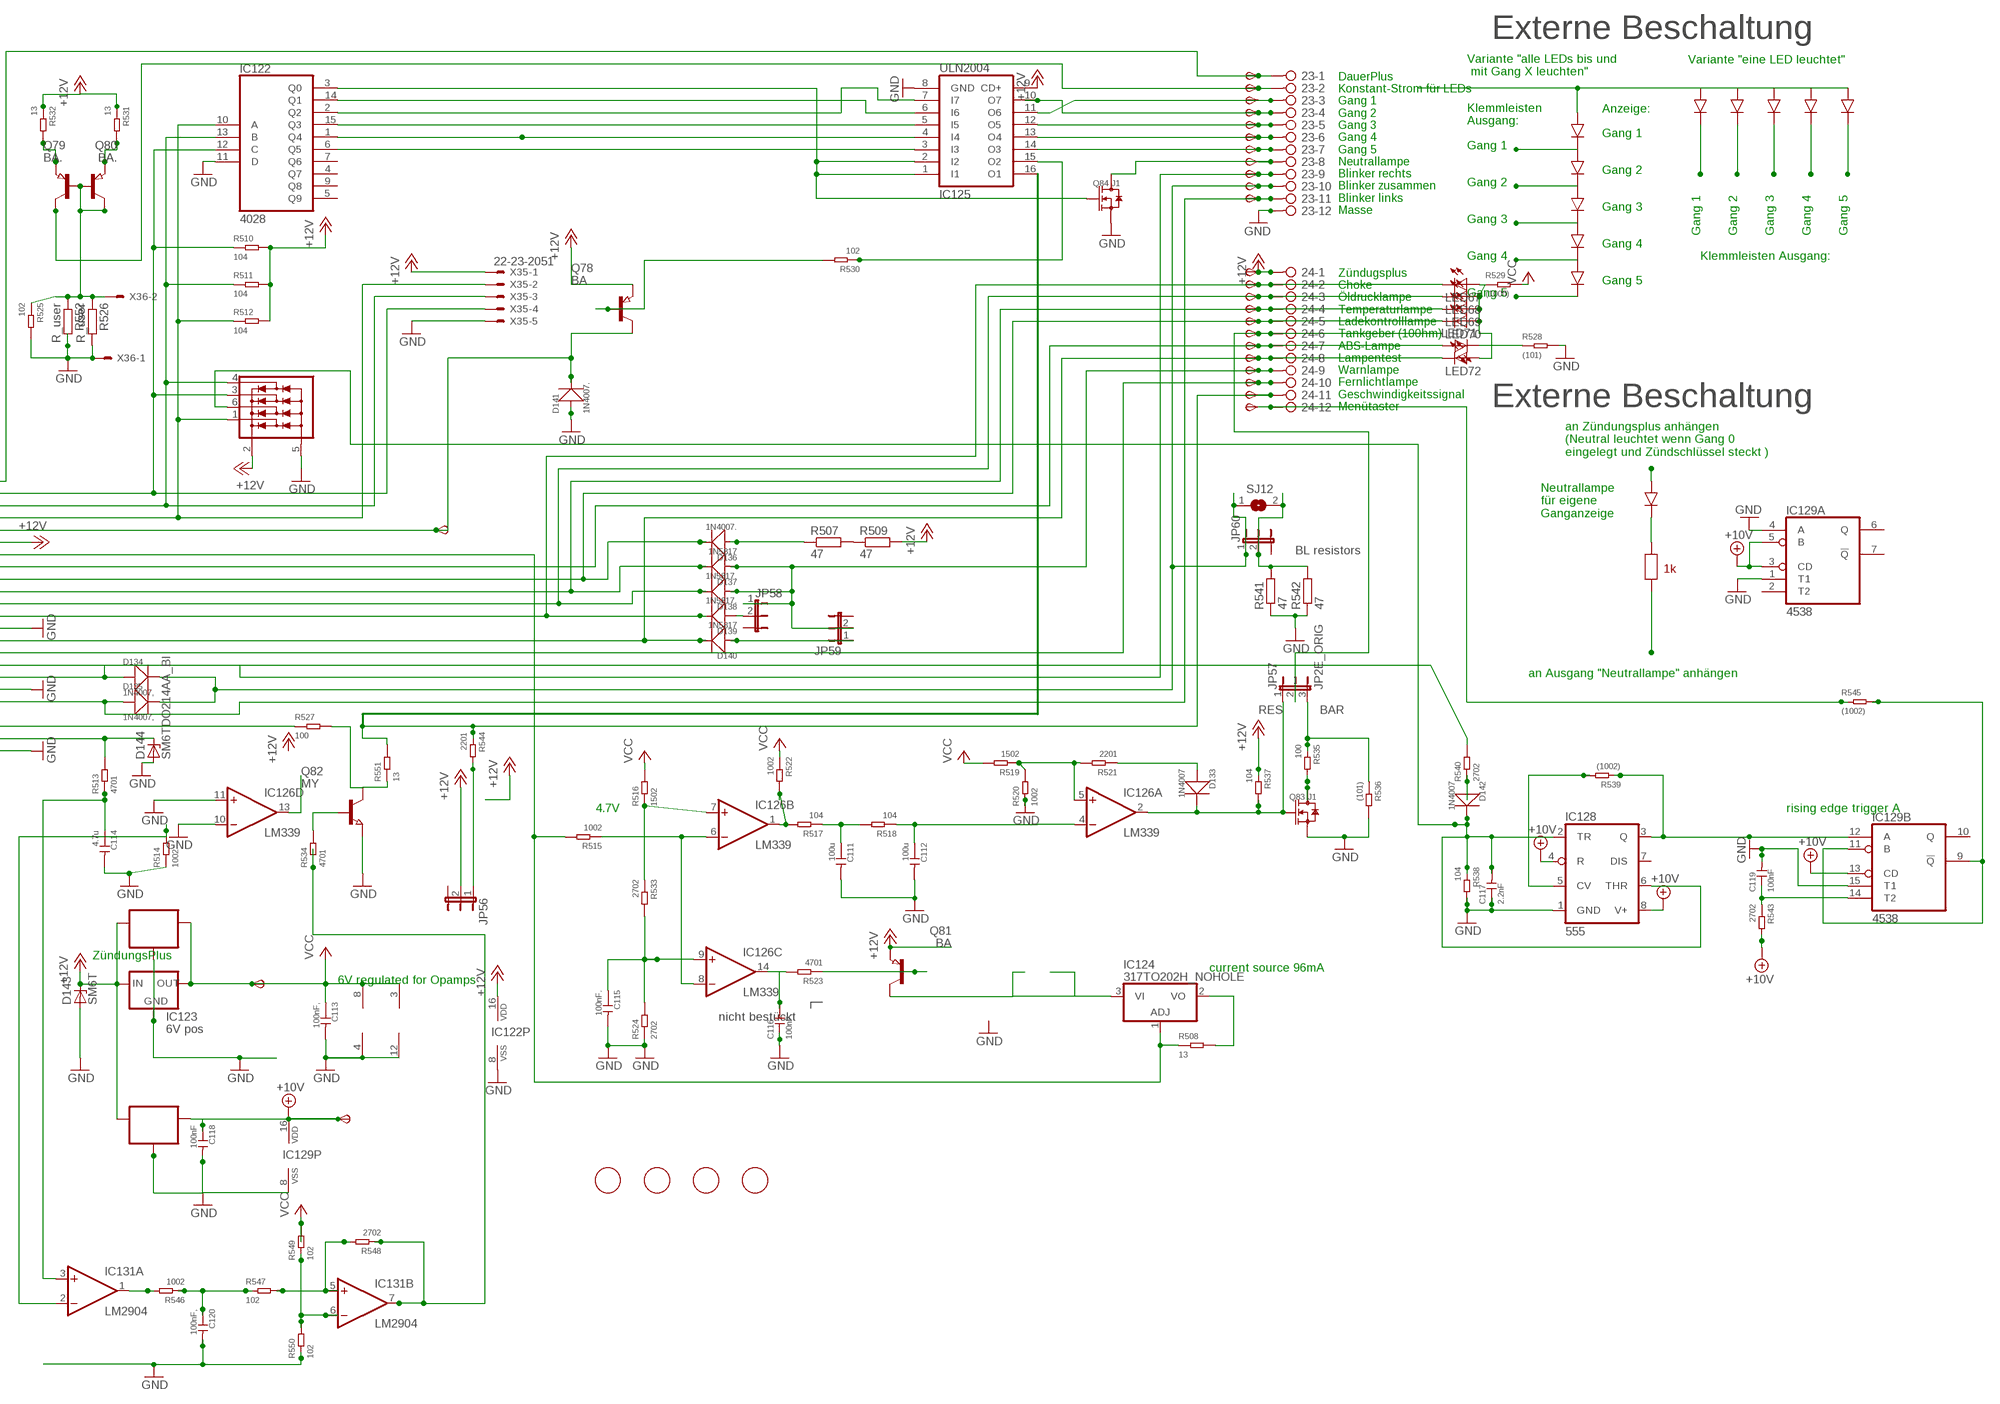
[diagram p23: schematic, sheet 12, part 2 of 2]

(export (version "E")
  (design (tool "Eeschema 10.0.6"))
  (components
    (comp (ref "6V11")
      (value "TPSB2.0")
      (footprint "eagle-import:B2.0")
      (libsource (lib "eagle-import") (part "TPSB2.0"))
    )
    (comp (ref "10V11")
      (value "TPSB2.0")
      (footprint "eagle-import:B2.0")
      (libsource (lib "eagle-import") (part "TPSB2.0"))
    )
    (comp (ref "23")
      (value "2081-1132")
      (footprint "eagle-import:12-PIN")
      (libsource (lib "eagle-import") (part "2081-1132"))
    )
    (comp (ref "24")
      (value "2081-1132")
      (footprint "eagle-import:12-PIN")
      (libsource (lib "eagle-import") (part "2081-1132"))
    )
    (comp (ref "C111")
      (value "100u")
      (footprint "eagle-import:C1206")
      (fields (field (name "MPN") "GRM31CR60J107ME39L"))
      (libsource (lib "eagle-import") (part "CERAMIC-100UF-6.3V-20%-X5R(1206)"))
    )
    (comp (ref "C112")
      (value "100u")
      (footprint "eagle-import:C1206")
      (fields (field (name "MPN") "GRM31CR60J107ME39L"))
      (libsource (lib "eagle-import") (part "CERAMIC-100UF-6.3V-20%-X5R(1206)"))
    )
    (comp (ref "C113")
      (value "100nF,")
      (footprint "eagle-import:C0805")
      (fields (field (name "MPN") "CC0805KRX7R9BB104"))
      (libsource (lib "eagle-import") (part "CERAMIC-100NF-50V-10%-X7R(0805)"))
    )
    (comp (ref "C114")
      (value "4.7u")
      (footprint "eagle-import:C0805")
      (fields (field (name "MPN") "CC0805KKX5R8BB475"))
      (libsource (lib "eagle-import") (part "CERAMIC-4.7UF-25V-10%-X5R(0805)"))
    )
    (comp (ref "C115")
      (value "100nF.")
      (footprint "eagle-import:C0805")
      (fields (field (name "MPN") "CC0805KRX7R9BB104"))
      (libsource (lib "eagle-import") (part "CERAMIC-100NF-50V-10%-X7R(0805)"))
    )
    (comp (ref "C116")
      (value "100nF.")
      (footprint "eagle-import:C0805")
      (fields (field (name "MPN") "CC0805KRX7R9BB104"))
      (libsource (lib "eagle-import") (part "CERAMIC-100NF-50V-10%-X7R(0805)"))
    )
    (comp (ref "C117")
      (value "2.2nF")
      (footprint "eagle-import:C0805")
      (fields (field (name "MPN") "CC0805KRX7R9BB104"))
      (libsource (lib "eagle-import") (part "CERAMIC-100NF-50V-10%-X7R(0805)"))
    )
    (comp (ref "C118")
      (value "100nF")
      (footprint "eagle-import:C0805")
      (fields (field (name "MPN") "CC0805KRX7R9BB104"))
      (libsource (lib "eagle-import") (part "CERAMIC-100NF-50V-10%-X7R(0805)"))
    )
    (comp (ref "C119")
      (value "100nF")
      (footprint "eagle-import:C0805")
      (fields (field (name "MPN") "CC0805KRX7R9BB104"))
      (libsource (lib "eagle-import") (part "CERAMIC-100NF-50V-10%-X7R(0805)"))
    )
    (comp (ref "C120")
      (value "100nF,")
      (footprint "eagle-import:C0805")
      (fields (field (name "MPN") "CC0805KRX7R9BB104"))
      (libsource (lib "eagle-import") (part "CERAMIC-100NF-50V-10%-X7R(0805)"))
    )
    (comp (ref "D133")
      (value "1N4007")
      (footprint "eagle-import:DO-214AC")
      (libsource (lib "eagle-import") (part "DIODE-GEN-PURPOSE-1KV-1A(DO-214AC)"))
    )
    (comp (ref "D134")
      (value "1N4007,")
      (footprint "eagle-import:DO-214AC")
      (fields (field (name "MPN") "1N4007"))
      (libsource (lib "eagle-import") (part "DIODE-GEN-PURPOSE-1KV-1A(DO-214AC)"))
    )
    (comp (ref "D135")
      (value "1N4007,")
      (footprint "eagle-import:DO-214AC")
      (fields (field (name "MPN") "1N4007"))
      (libsource (lib "eagle-import") (part "DIODE-GEN-PURPOSE-1KV-1A(DO-214AC)"))
    )
    (comp (ref "D136")
      (value "1N4007.")
      (footprint "eagle-import:DO-214AC")
      (fields (field (name "MPN") "1N4007"))
      (libsource (lib "eagle-import") (part "DIODE-GEN-PURPOSE-1KV-1A(DO-214AC)"))
    )
    (comp (ref "D137")
      (value "1N5817")
      (footprint "eagle-import:DO-214AC_SLIM")
      (libsource (lib "eagle-import") (part "DIODE-GEN-PURPOSE-1KV-1A(DO-214AC)DO-214AC/1206"))
    )
    (comp (ref "D138")
      (value "1N5817.")
      (footprint "eagle-import:DO-214AC_SLIM")
      (libsource (lib "eagle-import") (part "DIODE-GEN-PURPOSE-1KV-1A(DO-214AC)DO-214AC/1206"))
    )
    (comp (ref "D139")
      (value "1N5817.")
      (footprint "eagle-import:DO-214AC_SLIM")
      (libsource (lib "eagle-import") (part "DIODE-GEN-PURPOSE-1KV-1A(DO-214AC)DO-214AC/1206"))
    )
    (comp (ref "D140")
      (value "1N5817")
      (footprint "eagle-import:DO-214AC_SLIM")
      (libsource (lib "eagle-import") (part "DIODE-GEN-PURPOSE-1KV-1A(DO-214AC)DO-214AC/1206"))
    )
    (comp (ref "D141")
      (value "1N4007.")
      (footprint "eagle-import:DO-214AC")
      (fields (field (name "MPN") "1N4007"))
      (libsource (lib "eagle-import") (part "DIODE-GEN-PURPOSE-1KV-1A(DO-214AC)"))
    )
    (comp (ref "D142")
      (value "1N4007")
      (footprint "eagle-import:DO-214AC")
      (libsource (lib "eagle-import") (part "DIODE-GEN-PURPOSE-1KV-1A(DO-214AC)"))
    )
    (comp (ref "D143")
      (value "SM6T")
      (footprint "eagle-import:DO214AA")
      (libsource (lib "eagle-import") (part "SM6T"))
    )
    (comp (ref "D144")
      (value "SM6TDO214AA_BI")
      (footprint "eagle-import:DO214AA_BI")
      (libsource (lib "eagle-import") (part "SM6TDO214AA_BI"))
    )
    (comp (ref "FID45")
      (value "FIDUCIAL")
      (footprint "eagle-import:FIDUCIAL_1MM")
      (libsource (lib "eagle-import") (part "FIDUCIAL"))
    )
    (comp (ref "FID46")
      (value "FIDUCIAL")
      (footprint "eagle-import:FIDUCIAL_1MM")
      (libsource (lib "eagle-import") (part "FIDUCIAL"))
    )
    (comp (ref "FID47")
      (value "FIDUCIAL")
      (footprint "eagle-import:FIDUCIAL_1MM")
      (libsource (lib "eagle-import") (part "FIDUCIAL"))
    )
    (comp (ref "FID48")
      (value "FIDUCIAL")
      (footprint "eagle-import:FIDUCIAL_1MM")
      (libsource (lib "eagle-import") (part "FIDUCIAL"))
    )
    (comp (ref "IC122")
      (value "4028")
      (footprint "eagle-import:SO16")
      (libsource (lib "eagle-import") (part "4028D"))
    )
    (comp (ref "IC123")
      (value "6V pos")
      (footprint "eagle-import:78LXX")
      (libsource (lib "eagle-import") (part "v-reg_78LXX"))
    )
    (comp (ref "IC124")
      (value "317TO202H_NOHOLE")
      (footprint "eagle-import:TO220H_NOHOLE")
      (libsource (lib "eagle-import") (part "317TO202H_NOHOLE"))
    )
    (comp (ref "IC125")
      (value "ULN2004")
      (footprint "eagle-import:SO16")
      (libsource (lib "eagle-import") (part "ULN2004AD"))
    )
    (comp (ref "IC126")
      (value "LM339")
      (footprint "eagle-import:SO14")
      (libsource (lib "eagle-import") (part "LM339D"))
    )
    (comp (ref "IC127")
      (value "78L06")
      (footprint "eagle-import:SOT89_ROUND")
      (libsource (lib "eagle-import") (part "78LXXSOT89_ROUND"))
    )
    (comp (ref "IC128")
      (value "555")
      (footprint "eagle-import:SO08")
      (libsource (lib "eagle-import") (part "555DNE"))
    )
    (comp (ref "IC129")
      (value "4538")
      (footprint "eagle-import:SO16")
      (libsource (lib "eagle-import") (part "4538D"))
    )
    (comp (ref "IC130")
      (value "78L10")
      (footprint "eagle-import:SOT89_ROUND")
      (libsource (lib "eagle-import") (part "78LXXSOT89_ROUND"))
    )
    (comp (ref "IC131")
      (value "LM2904")
      (footprint "eagle-import:SO08")
      (libsource (lib "eagle-import") (part "LM358D"))
    )
    (comp (ref "IC132")
      (value "NUP4304SOT457_R")
      (footprint "eagle-import:SOT457R_PHILIPS")
      (libsource (lib "eagle-import") (part "NUP4304SOT457_R"))
    )
    (comp (ref "JP56")
      (value "JP2EJP2_SMALLPADS")
      (footprint "eagle-import:JP2_SMALLPADS")
      (libsource (lib "eagle-import") (part "JP2EJP2_SMALLPADS"))
    )
    (comp (ref "JP57")
      (value "JP2E_ORIG")
      (footprint "eagle-import:JP2_ORIG_SMALLPADS")
      (libsource (lib "eagle-import") (part "JP2E_ORIG"))
    )
    (comp (ref "JP58")
      (value "JP2EJP2_SMALLPADS")
      (footprint "eagle-import:JP2_SMALLPADS")
      (libsource (lib "eagle-import") (part "JP2EJP2_SMALLPADS"))
    )
    (comp (ref "JP59")
      (value "JP2EJP2_SMALLPADS")
      (footprint "eagle-import:JP2_SMALLPADS")
      (libsource (lib "eagle-import") (part "JP2EJP2_SMALLPADS"))
    )
    (comp (ref "JP60")
      (value "JP2EJP2_SMALLPADS")
      (footprint "eagle-import:JP2_SMALLPADS")
      (libsource (lib "eagle-import") (part "JP2EJP2_SMALLPADS"))
    )
    (comp (ref "LED67")
      (value "LEDLD260")
      (footprint "eagle-import:LD260")
      (libsource (lib "eagle-import") (part "LEDLD260"))
    )
    (comp (ref "LED68")
      (value "LEDLD260")
      (footprint "eagle-import:LD260")
      (libsource (lib "eagle-import") (part "LEDLD260"))
    )
    (comp (ref "LED69")
      (value "LEDLD260")
      (footprint "eagle-import:LD260")
      (libsource (lib "eagle-import") (part "LEDLD260"))
    )
    (comp (ref "LED70")
      (value "LEDLD260")
      (footprint "eagle-import:LD260")
      (libsource (lib "eagle-import") (part "LEDLD260"))
    )
    (comp (ref "LED71")
      (value "LEDLD260")
      (footprint "eagle-import:LD260")
      (libsource (lib "eagle-import") (part "LEDLD260"))
    )
    (comp (ref "LED72")
      (value "LEDLD260")
      (footprint "eagle-import:LD260")
      (libsource (lib "eagle-import") (part "LEDLD260"))
    )
    (comp (ref "Q78")
      (value "BA")
      (footprint "eagle-import:SOT89")
      (libsource (lib "eagle-import") (part "PNP-TRANSISTOR_SOT89"))
    )
    (comp (ref "Q79")
      (value "BA.")
      (footprint "eagle-import:SOT89")
      (libsource (lib "eagle-import") (part "PNP-TRANSISTOR_SOT89"))
    )
    (comp (ref "Q80")
      (value "BA.")
      (footprint "eagle-import:SOT89")
      (libsource (lib "eagle-import") (part "PNP-TRANSISTOR_SOT89"))
    )
    (comp (ref "Q81")
      (value "BA")
      (footprint "eagle-import:SOT89")
      (libsource (lib "eagle-import") (part "PNP-TRANSISTOR_SOT89"))
    )
    (comp (ref "Q82")
      (value "MY")
      (footprint "eagle-import:SOT89")
      (libsource (lib "eagle-import") (part "NPN-TRANSISTOR_SOT89"))
    )
    (comp (ref "Q83")
      (value "J1")
      (footprint "eagle-import:SOT-23")
      (fields (field (name "MPN") "BSS138W-7-F"))
      (libsource (lib "eagle-import") (part "SMD-MOSFET-N-CH-50V-200MA-BSS138W-7-F(SOT-23)"))
    )
    (comp (ref "Q84")
      (value "J1")
      (footprint "eagle-import:SOT-23")
      (fields (field (name "MPN") "BSS138W-7-F"))
      (libsource (lib "eagle-import") (part "SMD-MOSFET-N-CH-50V-200MA-BSS138W-7-F(SOT-23)"))
    )
    (comp (ref "R507")
      (value "47")
      (footprint "eagle-import:V235_17_1MM")
      (libsource (lib "eagle-import") (part "R-EU_V235/17_1MM"))
    )
    (comp (ref "R508")
      (value "13")
      (footprint "eagle-import:R1206")
      (fields (field (name "MPN") "RC1206JR-0713RL"))
      (libsource (lib "eagle-import") (part "SMD-RES-13R-5%-1/4W(1206)"))
    )
    (comp (ref "R509")
      (value "47")
      (footprint "eagle-import:V235_17_1MM")
      (libsource (lib "eagle-import") (part "R-EU_V235/17_1MM"))
    )
    (comp (ref "R510")
      (value "104")
      (footprint "eagle-import:R0805")
      (fields (field (name "MPN") "RC0805FR-0710KL"))
      (libsource (lib "eagle-import") (part "SMD-RES-10K-1%-1/8W(0805)"))
    )
    (comp (ref "R511")
      (value "104")
      (footprint "eagle-import:R0805")
      (fields (field (name "MPN") "RC0805FR-0710KL"))
      (libsource (lib "eagle-import") (part "SMD-RES-10K-1%-1/8W(0805)"))
    )
    (comp (ref "R512")
      (value "104")
      (footprint "eagle-import:R0805")
      (fields (field (name "MPN") "RC0805FR-0710KL"))
      (libsource (lib "eagle-import") (part "SMD-RES-10K-1%-1/8W(0805)"))
    )
    (comp (ref "R513")
      (value "4701")
      (footprint "eagle-import:R0805")
      (fields (field (name "MPN") "RC0805JR-074K7L"))
      (libsource (lib "eagle-import") (part "SMD-RES-4.7K-5%-1/8W(0805)"))
    )
    (comp (ref "R514")
      (value "1002")
      (footprint "eagle-import:R0805")
      (fields (field (name "MPN") "RC0805FR-0710KL"))
      (libsource (lib "eagle-import") (part "SMD-RES-10K-1%-1/8W(0805)"))
    )
    (comp (ref "R515")
      (value "1002")
      (footprint "eagle-import:R0805")
      (fields (field (name "MPN") "RC0805FR-0710KL"))
      (libsource (lib "eagle-import") (part "SMD-RES-10K-1%-1/8W(0805)"))
    )
    (comp (ref "R516")
      (value "1502")
      (footprint "eagle-import:R0805")
      (fields (field (name "MPN") "RC0805FR-0710KL"))
      (libsource (lib "eagle-import") (part "SMD-RES-10K-1%-1/8W(0805)"))
    )
    (comp (ref "R517")
      (value "104")
      (footprint "eagle-import:R0805")
      (fields (field (name "MPN") "RC0805FR-0710KL"))
      (libsource (lib "eagle-import") (part "SMD-RES-10K-1%-1/8W(0805)"))
    )
    (comp (ref "R518")
      (value "104")
      (footprint "eagle-import:R0805")
      (fields (field (name "MPN") "RC0805FR-0710KL"))
      (libsource (lib "eagle-import") (part "SMD-RES-10K-1%-1/8W(0805)"))
    )
    (comp (ref "R519")
      (value "1502")
      (footprint "eagle-import:R0805")
      (fields (field (name "MPN") "RC0805FR-0710KL"))
      (libsource (lib "eagle-import") (part "SMD-RES-10K-1%-1/8W(0805)"))
    )
    (comp (ref "R520")
      (value "1002")
      (footprint "eagle-import:R0805")
      (fields (field (name "MPN") "RC0805FR-0710KL"))
      (libsource (lib "eagle-import") (part "SMD-RES-10K-1%-1/8W(0805)"))
    )
    (comp (ref "R521")
      (value "2201")
      (footprint "eagle-import:R0805")
      (fields (field (name "MPN") "RC0805JR-072K2L"))
      (libsource (lib "eagle-import") (part "SMD-RES-2.2K-5%-1/8W(0805)"))
    )
    (comp (ref "R522")
      (value "1002")
      (footprint "eagle-import:R0805")
      (fields (field (name "MPN") "RC0805FR-0710KL"))
      (libsource (lib "eagle-import") (part "SMD-RES-10K-1%-1/8W(0805)"))
    )
    (comp (ref "R523")
      (value "4701")
      (footprint "eagle-import:R0805")
      (fields (field (name "MPN") "RC0805JR-074K7L"))
      (libsource (lib "eagle-import") (part "SMD-RES-4.7K-5%-1/8W(0805)"))
    )
    (comp (ref "R524")
      (value "2702")
      (footprint "eagle-import:R0805")
      (fields (field (name "MPN") "RC0805JR-074K7L"))
      (libsource (lib "eagle-import") (part "SMD-RES-4.7K-5%-1/8W(0805)"))
    )
    (comp (ref "R525")
      (value "102")
      (footprint "eagle-import:R0805")
      (fields (field (name "MPN") "RC0805JR-071KL"))
      (libsource (lib "eagle-import") (part "SMD-RES-1K-5%-1/8W(0805)"))
    )
    (comp (ref "R526")
      (value "R_user")
      (footprint "eagle-import:R0805")
      (libsource (lib "eagle-import") (part "R-EU_R0805"))
    )
    (comp (ref "R527")
      (value "100")
      (footprint "eagle-import:R0805")
      (fields (field (name "MPN") "RC0805JR-07220RL"))
      (libsource (lib "eagle-import") (part "SMD-RES-220R-5%-1/8W(0805)"))
    )
    (comp (ref "R528")
      (value "(101)")
      (footprint "eagle-import:R0805")
      (fields (field (name "MPN") "RC0805JR-07100RL"))
      (libsource (lib "eagle-import") (part "SMD-RES-100R-5%-1/8W(0805)"))
    )
    (comp (ref "R529")
      (value "(1000)")
      (footprint "eagle-import:R0805")
      (fields (field (name "MPN") "RC0805JR-07100RL"))
      (libsource (lib "eagle-import") (part "SMD-RES-100R-5%-1/8W(0805)"))
    )
    (comp (ref "R530")
      (value "102")
      (footprint "eagle-import:R0805")
      (fields (field (name "MPN") "RC0805JR-071KL"))
      (libsource (lib "eagle-import") (part "SMD-RES-1K-5%-1/8W(0805)"))
    )
    (comp (ref "R531")
      (value "13")
      (footprint "eagle-import:R1206")
      (fields (field (name "MPN") "RC1206JR-0713RL"))
      (libsource (lib "eagle-import") (part "SMD-RES-13R-5%-1/4W(1206)"))
    )
    (comp (ref "R532")
      (value "13")
      (footprint "eagle-import:R1206")
      (fields (field (name "MPN") "RC1206JR-0713RL"))
      (libsource (lib "eagle-import") (part "SMD-RES-13R-5%-1/4W(1206)"))
    )
    (comp (ref "R533")
      (value "2702")
      (footprint "eagle-import:R0805")
      (fields (field (name "MPN") "RC0805JR-074K7L"))
      (libsource (lib "eagle-import") (part "SMD-RES-4.7K-5%-1/8W(0805)"))
    )
    (comp (ref "R534")
      (value "4701")
      (footprint "eagle-import:R0805")
      (fields (field (name "MPN") "RC0805JR-074K7L"))
      (libsource (lib "eagle-import") (part "SMD-RES-4.7K-5%-1/8W(0805)"))
    )
    (comp (ref "R535")
      (value "100")
      (footprint "eagle-import:R0805")
      (fields (field (name "MPN") "RC0805JR-072K2L"))
      (libsource (lib "eagle-import") (part "SMD-RES-2.2K-5%-1/8W(0805)"))
    )
    (comp (ref "R536")
      (value "(101)")
      (footprint "eagle-import:R0805")
      (fields (field (name "MPN") "RC0805JR-072K2L"))
      (libsource (lib "eagle-import") (part "SMD-RES-2.2K-5%-1/8W(0805)"))
    )
    (comp (ref "R537")
      (value "104")
      (footprint "eagle-import:R0805")
      (fields (field (name "MPN") "RC0805FR-0710KL"))
      (libsource (lib "eagle-import") (part "SMD-RES-10K-1%-1/8W(0805)"))
    )
    (comp (ref "R538")
      (value "104")
      (footprint "eagle-import:R0805")
      (fields (field (name "MPN") "RC0805FR-0710KL"))
      (libsource (lib "eagle-import") (part "SMD-RES-10K-1%-1/8W(0805)"))
    )
    (comp (ref "R539")
      (value "(1002)")
      (footprint "eagle-import:R0805")
      (fields (field (name "MPN") "RC0805FR-0710KL"))
      (libsource (lib "eagle-import") (part "SMD-RES-10K-1%-1/8W(0805)"))
    )
    (comp (ref "R540")
      (value "2702")
      (footprint "eagle-import:R0805")
      (fields (field (name "MPN") "RC0805FR-0710KL"))
      (libsource (lib "eagle-import") (part "SMD-RES-10K-1%-1/8W(0805)"))
    )
    (comp (ref "R541")
      (value "47")
      (footprint "eagle-import:V235_17_1MM")
      (libsource (lib "eagle-import") (part "R-EU_V235/17_1MM"))
    )
    (comp (ref "R542")
      (value "47")
      (footprint "eagle-import:V235_17_1MM")
      (libsource (lib "eagle-import") (part "R-EU_V235/17_1MM"))
    )
    (comp (ref "R543")
      (value "2702")
      (footprint "eagle-import:R0805")
      (fields (field (name "MPN") "RC0805JR-074K7L"))
      (libsource (lib "eagle-import") (part "SMD-RES-4.7K-5%-1/8W(0805)"))
    )
    (comp (ref "R544")
      (value "2201")
      (footprint "eagle-import:R0805")
      (fields (field (name "MPN") "RC0805JR-072K2L"))
      (libsource (lib "eagle-import") (part "SMD-RES-2.2K-5%-1/8W(0805)"))
    )
    (comp (ref "R545")
      (value "(1002)")
      (footprint "eagle-import:R0805")
      (fields (field (name "MPN") "RC0805JR-074K7L"))
      (libsource (lib "eagle-import") (part "SMD-RES-4.7K-5%-1/8W(0805)"))
    )
    (comp (ref "R546")
      (value "1002")
      (footprint "eagle-import:R0805")
      (fields (field (name "MPN") "RC0805FR-0710KL"))
      (libsource (lib "eagle-import") (part "SMD-RES-10K-1%-1/8W(0805)"))
    )
    (comp (ref "R547")
      (value "102")
      (footprint "eagle-import:R0805")
      (fields (field (name "MPN") "RC0805JR-071KL"))
      (libsource (lib "eagle-import") (part "SMD-RES-1K-5%-1/8W(0805)"))
    )
    (comp (ref "R548")
      (value "2702")
      (footprint "eagle-import:R0805")
      (fields (field (name "MPN") "RC0805JR-074K7L"))
      (libsource (lib "eagle-import") (part "SMD-RES-4.7K-5%-1/8W(0805)"))
    )
    (comp (ref "R549")
      (value "102")
      (footprint "eagle-import:R0805")
      (fields (field (name "MPN") "RC0805JR-071KL"))
      (libsource (lib "eagle-import") (part "SMD-RES-1K-5%-1/8W(0805)"))
    )
    (comp (ref "R550")
      (value "102")
      (footprint "eagle-import:R0805")
      (fields (field (name "MPN") "RC0805JR-071KL"))
      (libsource (lib "eagle-import") (part "SMD-RES-1K-5%-1/8W(0805)"))
    )
    (comp (ref "R551")
      (value "13")
      (footprint "eagle-import:R1206")
      (fields (field (name "MPN") "RC1206JR-0713RL"))
      (libsource (lib "eagle-import") (part "SMD-RES-13R-5%-1/4W(1206)"))
    )
    (comp (ref "R552")
      (value "R_user")
      (footprint "eagle-import:R0805")
      (libsource (lib "eagle-import") (part "R-EU_R0805"))
    )
    (comp (ref "SJ12")
      (value "SJ")
      (footprint "eagle-import:SJ")
      (libsource (lib "eagle-import") (part "SJ"))
    )
    (comp (ref "START11")
      (value "TPSB2.0")
      (footprint "eagle-import:B2.0")
      (libsource (lib "eagle-import") (part "TPSB2.0"))
    )
    (comp (ref "TP254")
      (value "TPSB2.0")
      (footprint "eagle-import:B2.0")
      (libsource (lib "eagle-import") (part "TPSB2.0"))
    )
    (comp (ref "TP255")
      (value "TPSB2.0")
      (footprint "eagle-import:B2.0")
      (libsource (lib "eagle-import") (part "TPSB2.0"))
    )
    (comp (ref "TP256")
      (value "TPSB2.0")
      (footprint "eagle-import:B2.0")
      (libsource (lib "eagle-import") (part "TPSB2.0"))
    )
    (comp (ref "TP257")
      (value "TPSB2.0")
      (footprint "eagle-import:B2.0")
      (libsource (lib "eagle-import") (part "TPSB2.0"))
    )
    (comp (ref "TP258")
      (value "TPSB2.0")
      (footprint "eagle-import:B2.0")
      (libsource (lib "eagle-import") (part "TPSB2.0"))
    )
    (comp (ref "TP259")
      (value "TPSB2.0")
      (footprint "eagle-import:B2.0")
      (libsource (lib "eagle-import") (part "TPSB2.0"))
    )
    (comp (ref "TP260")
      (value "TPSB2.0")
      (footprint "eagle-import:B2.0")
      (libsource (lib "eagle-import") (part "TPSB2.0"))
    )
    (comp (ref "TP261")
      (value "TPSB2.0")
      (footprint "eagle-import:B2.0")
      (libsource (lib "eagle-import") (part "TPSB2.0"))
    )
    (comp (ref "TP262")
      (value "TPSB2.0")
      (footprint "eagle-import:B2.0")
      (libsource (lib "eagle-import") (part "TPSB2.0"))
    )
    (comp (ref "TP263")
      (value "TPSB2.0")
      (footprint "eagle-import:B2.0")
      (libsource (lib "eagle-import") (part "TPSB2.0"))
    )
    (comp (ref "TP264")
      (value "TPSB2.0")
      (footprint "eagle-import:B2.0")
      (libsource (lib "eagle-import") (part "TPSB2.0"))
    )
    (comp (ref "TP265")
      (value "TPSB2.0")
      (footprint "eagle-import:B2.0")
      (libsource (lib "eagle-import") (part "TPSB2.0"))
    )
    (comp (ref "TP266")
      (value "TPSB2.0")
      (footprint "eagle-import:B2.0")
      (libsource (lib "eagle-import") (part "TPSB2.0"))
    )
    (comp (ref "TP267")
      (value "TPSB2.0")
      (footprint "eagle-import:B2.0")
      (libsource (lib "eagle-import") (part "TPSB2.0"))
    )
    (comp (ref "TP268")
      (value "TPSB2.0")
      (footprint "eagle-import:B2.0")
      (libsource (lib "eagle-import") (part "TPSB2.0"))
    )
    (comp (ref "TP269")
      (value "TPSB2.0")
      (footprint "eagle-import:B2.0")
      (libsource (lib "eagle-import") (part "TPSB2.0"))
    )
    (comp (ref "TP270")
      (value "TPSB2.0")
      (footprint "eagle-import:B2.0")
      (libsource (lib "eagle-import") (part "TPSB2.0"))
    )
    (comp (ref "TP271")
      (value "TPSB2.0")
      (footprint "eagle-import:B2.0")
      (libsource (lib "eagle-import") (part "TPSB2.0"))
    )
    (comp (ref "TP272")
      (value "TPSB1,27")
      (footprint "eagle-import:B1,27")
      (libsource (lib "eagle-import") (part "TPSB1,27"))
    )
    (comp (ref "TP273")
      (value "TPSB2.0")
      (footprint "eagle-import:B2.0")
      (libsource (lib "eagle-import") (part "TPSB2.0"))
    )
    (comp (ref "TP274")
      (value "TPSB2.0")
      (footprint "eagle-import:B2.0")
      (libsource (lib "eagle-import") (part "TPSB2.0"))
    )
    (comp (ref "TP275")
      (value "TPSB2.0")
      (footprint "eagle-import:B2.0")
      (libsource (lib "eagle-import") (part "TPSB2.0"))
    )
    (comp (ref "TP276")
      (value "TPSB2.0")
      (footprint "eagle-import:B2.0")
      (libsource (lib "eagle-import") (part "TPSB2.0"))
    )
    (comp (ref "X34")
      (value "CON_BMWV2")
      (footprint "eagle-import:24-PIN_V2")
      (libsource (lib "eagle-import") (part "CON_BMWV2"))
    )
    (comp (ref "X35")
      (value "22-23-2051")
      (footprint "eagle-import:22-23-2051")
      (fields (field (name "MF") "MOLEX"))
      (libsource (lib "eagle-import") (part "22-23-2051"))
    )
    (comp (ref "X36")
      (value "22-23-2021")
      (footprint "eagle-import:22-23-2021")
      (fields (field (name "MF") "MOLEX"))
      (libsource (lib "eagle-import") (part "22-23-2021"))
    )
    (comp (ref "6V3")
      (value "TPSB2.0")
      (footprint "eagle-import:B2.0")
      (libsource (lib "eagle-import") (part "TPSB2.0"))
    )
    (comp (ref "7")
      (value "2081-1132")
      (footprint "eagle-import:12-PIN")
      (libsource (lib "eagle-import") (part "2081-1132"))
    )
    (comp (ref "8")
      (value "2081-1132")
      (footprint "eagle-import:12-PIN")
      (libsource (lib "eagle-import") (part "2081-1132"))
    )
    (comp (ref "10V3")
      (value "TPSB2.0")
      (footprint "eagle-import:B2.0")
      (libsource (lib "eagle-import") (part "TPSB2.0"))
    )
    (comp (ref "C31")
      (value "100u")
      (footprint "eagle-import:C1206")
      (fields (field (name "MPN") "GRM31CR60J107ME39L"))
      (libsource (lib "eagle-import") (part "CERAMIC-100UF-6.3V-20%-X5R(1206)"))
    )
    (comp (ref "C32")
      (value "100u")
      (footprint "eagle-import:C1206")
      (fields (field (name "MPN") "GRM31CR60J107ME39L"))
      (libsource (lib "eagle-import") (part "CERAMIC-100UF-6.3V-20%-X5R(1206)"))
    )
    (comp (ref "C33")
      (value "100nF,")
      (footprint "eagle-import:C0805")
      (fields (field (name "MPN") "CC0805KRX7R9BB104"))
      (libsource (lib "eagle-import") (part "CERAMIC-100NF-50V-10%-X7R(0805)"))
    )
    (comp (ref "C34")
      (value "4.7u")
      (footprint "eagle-import:C0805")
      (fields (field (name "MPN") "CC0805KKX5R8BB475"))
      (libsource (lib "eagle-import") (part "CERAMIC-4.7UF-25V-10%-X5R(0805)"))
    )
    (comp (ref "C35")
      (value "100nF.")
      (footprint "eagle-import:C0805")
      (fields (field (name "MPN") "CC0805KRX7R9BB104"))
      (libsource (lib "eagle-import") (part "CERAMIC-100NF-50V-10%-X7R(0805)"))
    )
    (comp (ref "C36")
      (value "100nF.")
      (footprint "eagle-import:C0805")
      (fields (field (name "MPN") "CC0805KRX7R9BB104"))
      (libsource (lib "eagle-import") (part "CERAMIC-100NF-50V-10%-X7R(0805)"))
    )
    (comp (ref "C37")
      (value "2.2nF")
      (footprint "eagle-import:C0805")
      (fields (field (name "MPN") "CC0805KRX7R9BB104"))
      (libsource (lib "eagle-import") (part "CERAMIC-100NF-50V-10%-X7R(0805)"))
    )
    (comp (ref "C38")
      (value "100nF")
      (footprint "eagle-import:C0805")
      (fields (field (name "MPN") "CC0805KRX7R9BB104"))
      (libsource (lib "eagle-import") (part "CERAMIC-100NF-50V-10%-X7R(0805)"))
    )
    (comp (ref "C39")
      (value "100nF")
      (footprint "eagle-import:C0805")
      (fields (field (name "MPN") "CC0805KRX7R9BB104"))
      (libsource (lib "eagle-import") (part "CERAMIC-100NF-50V-10%-X7R(0805)"))
    )
    (comp (ref "C40")
      (value "100nF,")
      (footprint "eagle-import:C0805")
      (fields (field (name "MPN") "CC0805KRX7R9BB104"))
      (libsource (lib "eagle-import") (part "CERAMIC-100NF-50V-10%-X7R(0805)"))
    )
    (comp (ref "D37")
      (value "1N4007")
      (footprint "eagle-import:DO-214AC")
      (libsource (lib "eagle-import") (part "DIODE-GEN-PURPOSE-1KV-1A(DO-214AC)"))
    )
    (comp (ref "D38")
      (value "1N4007,")
      (footprint "eagle-import:DO-214AC")
      (fields (field (name "MPN") "1N4007"))
      (libsource (lib "eagle-import") (part "DIODE-GEN-PURPOSE-1KV-1A(DO-214AC)"))
    )
    (comp (ref "D39")
      (value "1N4007,")
      (footprint "eagle-import:DO-214AC")
      (fields (field (name "MPN") "1N4007"))
      (libsource (lib "eagle-import") (part "DIODE-GEN-PURPOSE-1KV-1A(DO-214AC)"))
    )
    (comp (ref "D40")
      (value "1N4007.")
      (footprint "eagle-import:DO-214AC")
      (fields (field (name "MPN") "1N4007"))
      (libsource (lib "eagle-import") (part "DIODE-GEN-PURPOSE-1KV-1A(DO-214AC)"))
    )
    (comp (ref "D41")
      (value "1N5817")
      (footprint "eagle-import:DO-214AC_SLIM")
      (libsource (lib "eagle-import") (part "DIODE-GEN-PURPOSE-1KV-1A(DO-214AC)DO-214AC/1206"))
    )
    (comp (ref "D42")
      (value "1N5817.")
      (footprint "eagle-import:DO-214AC_SLIM")
      (libsource (lib "eagle-import") (part "DIODE-GEN-PURPOSE-1KV-1A(DO-214AC)DO-214AC/1206"))
    )
    (comp (ref "D43")
      (value "1N5817.")
      (footprint "eagle-import:DO-214AC_SLIM")
      (libsource (lib "eagle-import") (part "DIODE-GEN-PURPOSE-1KV-1A(DO-214AC)DO-214AC/1206"))
    )
    (comp (ref "D44")
      (value "1N5817")
      (footprint "eagle-import:DO-214AC_SLIM")
      (libsource (lib "eagle-import") (part "DIODE-GEN-PURPOSE-1KV-1A(DO-214AC)DO-214AC/1206"))
    )
    (comp (ref "D45")
      (value "1N4007.")
      (footprint "eagle-import:DO-214AC")
      (fields (field (name "MPN") "1N4007"))
      (libsource (lib "eagle-import") (part "DIODE-GEN-PURPOSE-1KV-1A(DO-214AC)"))
    )
    (comp (ref "D46")
      (value "1N4007")
      (footprint "eagle-import:DO-214AC")
      (libsource (lib "eagle-import") (part "DIODE-GEN-PURPOSE-1KV-1A(DO-214AC)"))
    )
    (comp (ref "D47")
      (value "SM6T")
      (footprint "eagle-import:DO214AA")
      (libsource (lib "eagle-import") (part "SM6T"))
    )
    (comp (ref "D48")
      (value "SM6TDO214AA_BI")
      (footprint "eagle-import:DO214AA_BI")
      (libsource (lib "eagle-import") (part "SM6TDO214AA_BI"))
    )
    (comp (ref "FID13")
      (value "FIDUCIAL")
      (footprint "eagle-import:FIDUCIAL_1MM")
      (libsource (lib "eagle-import") (part "FIDUCIAL"))
    )
    (comp (ref "FID14")
      (value "FIDUCIAL")
      (footprint "eagle-import:FIDUCIAL_1MM")
      (libsource (lib "eagle-import") (part "FIDUCIAL"))
    )
    (comp (ref "FID15")
      (value "FIDUCIAL")
      (footprint "eagle-import:FIDUCIAL_1MM")
      (libsource (lib "eagle-import") (part "FIDUCIAL"))
    )
    (comp (ref "FID16")
      (value "FIDUCIAL")
      (footprint "eagle-import:FIDUCIAL_1MM")
      (libsource (lib "eagle-import") (part "FIDUCIAL"))
    )
    (comp (ref "IC34")
      (value "4028")
      (footprint "eagle-import:SO16")
      (libsource (lib "eagle-import") (part "4028D"))
    )
    (comp (ref "IC35")
      (value "6V pos")
      (footprint "eagle-import:78LXX")
      (libsource (lib "eagle-import") (part "v-reg_78LXX"))
    )
    (comp (ref "IC36")
      (value "317TO202H_NOHOLE")
      (footprint "eagle-import:TO220H_NOHOLE")
      (libsource (lib "eagle-import") (part "317TO202H_NOHOLE"))
    )
    (comp (ref "IC37")
      (value "ULN2004")
      (footprint "eagle-import:SO16")
      (libsource (lib "eagle-import") (part "ULN2004AD"))
    )
    (comp (ref "IC38")
      (value "LM339")
      (footprint "eagle-import:SO14")
      (libsource (lib "eagle-import") (part "LM339D"))
    )
    (comp (ref "IC39")
      (value "78L06")
      (footprint "eagle-import:SOT89_ROUND")
      (libsource (lib "eagle-import") (part "78LXXSOT89_ROUND"))
    )
    (comp (ref "IC40")
      (value "555")
      (footprint "eagle-import:SO08")
      (libsource (lib "eagle-import") (part "555DNE"))
    )
    (comp (ref "IC41")
      (value "4538")
      (footprint "eagle-import:SO16")
      (libsource (lib "eagle-import") (part "4538D"))
    )
    (comp (ref "IC42")
      (value "78L10")
      (footprint "eagle-import:SOT89_ROUND")
      (libsource (lib "eagle-import") (part "78LXXSOT89_ROUND"))
    )
    (comp (ref "IC43")
      (value "LM2904")
      (footprint "eagle-import:SO08")
      (libsource (lib "eagle-import") (part "LM358D"))
    )
    (comp (ref "IC44")
      (value "NUP4304SOT457_R")
      (footprint "eagle-import:SOT457R_PHILIPS")
      (libsource (lib "eagle-import") (part "NUP4304SOT457_R"))
    )
    (comp (ref "JP16")
      (value "JP2EJP2_SMALLPADS")
      (footprint "eagle-import:JP2_SMALLPADS")
      (libsource (lib "eagle-import") (part "JP2EJP2_SMALLPADS"))
    )
    (comp (ref "JP17")
      (value "JP2E_ORIG")
      (footprint "eagle-import:JP2_ORIG_SMALLPADS")
      (libsource (lib "eagle-import") (part "JP2E_ORIG"))
    )
    (comp (ref "JP18")
      (value "JP2EJP2_SMALLPADS")
      (footprint "eagle-import:JP2_SMALLPADS")
      (libsource (lib "eagle-import") (part "JP2EJP2_SMALLPADS"))
    )
    (comp (ref "JP19")
      (value "JP2EJP2_SMALLPADS")
      (footprint "eagle-import:JP2_SMALLPADS")
      (libsource (lib "eagle-import") (part "JP2EJP2_SMALLPADS"))
    )
    (comp (ref "JP20")
      (value "JP2EJP2_SMALLPADS")
      (footprint "eagle-import:JP2_SMALLPADS")
      (libsource (lib "eagle-import") (part "JP2EJP2_SMALLPADS"))
    )
    (comp (ref "LED19")
      (value "LEDLD260")
      (footprint "eagle-import:LD260")
      (libsource (lib "eagle-import") (part "LEDLD260"))
    )
    (comp (ref "LED20")
      (value "LEDLD260")
      (footprint "eagle-import:LD260")
      (libsource (lib "eagle-import") (part "LEDLD260"))
    )
    (comp (ref "LED21")
      (value "LEDLD260")
      (footprint "eagle-import:LD260")
      (libsource (lib "eagle-import") (part "LEDLD260"))
    )
    (comp (ref "LED22")
      (value "LEDLD260")
      (footprint "eagle-import:LD260")
      (libsource (lib "eagle-import") (part "LEDLD260"))
    )
    (comp (ref "LED23")
      (value "LEDLD260")
      (footprint "eagle-import:LD260")
      (libsource (lib "eagle-import") (part "LEDLD260"))
    )
    (comp (ref "LED24")
      (value "LEDLD260")
      (footprint "eagle-import:LD260")
      (libsource (lib "eagle-import") (part "LEDLD260"))
    )
    (comp (ref "Q22")
      (value "BA")
      (footprint "eagle-import:SOT89")
      (libsource (lib "eagle-import") (part "PNP-TRANSISTOR_SOT89"))
    )
    (comp (ref "Q23")
      (value "BA.")
      (footprint "eagle-import:SOT89")
      (libsource (lib "eagle-import") (part "PNP-TRANSISTOR_SOT89"))
    )
    (comp (ref "Q24")
      (value "BA.")
      (footprint "eagle-import:SOT89")
      (libsource (lib "eagle-import") (part "PNP-TRANSISTOR_SOT89"))
    )
    (comp (ref "Q25")
      (value "BA")
      (footprint "eagle-import:SOT89")
      (libsource (lib "eagle-import") (part "PNP-TRANSISTOR_SOT89"))
    )
    (comp (ref "Q26")
      (value "MY")
      (footprint "eagle-import:SOT89")
      (libsource (lib "eagle-import") (part "NPN-TRANSISTOR_SOT89"))
    )
    (comp (ref "Q27")
      (value "J1")
      (footprint "eagle-import:SOT-23")
      (fields (field (name "MPN") "BSS138W-7-F"))
      (libsource (lib "eagle-import") (part "SMD-MOSFET-N-CH-50V-200MA-BSS138W-7-F(SOT-23)"))
    )
    (comp (ref "Q28")
      (value "J1")
      (footprint "eagle-import:SOT-23")
      (fields (field (name "MPN") "BSS138W-7-F"))
      (libsource (lib "eagle-import") (part "SMD-MOSFET-N-CH-50V-200MA-BSS138W-7-F(SOT-23)"))
    )
    (comp (ref "R139")
      (value "47")
      (footprint "eagle-import:V235_17_1MM")
      (libsource (lib "eagle-import") (part "R-EU_V235/17_1MM"))
    )
    (comp (ref "R140")
      (value "13")
      (footprint "eagle-import:R1206")
      (fields (field (name "MPN") "RC1206JR-0713RL"))
      (libsource (lib "eagle-import") (part "SMD-RES-13R-5%-1/4W(1206)"))
    )
    (comp (ref "R141")
      (value "47")
      (footprint "eagle-import:V235_17_1MM")
      (libsource (lib "eagle-import") (part "R-EU_V235/17_1MM"))
    )
    (comp (ref "R142")
      (value "104")
      (footprint "eagle-import:R0805")
      (fields (field (name "MPN") "RC0805FR-0710KL"))
      (libsource (lib "eagle-import") (part "SMD-RES-10K-1%-1/8W(0805)"))
    )
    (comp (ref "R143")
      (value "104")
      (footprint "eagle-import:R0805")
      (fields (field (name "MPN") "RC0805FR-0710KL"))
      (libsource (lib "eagle-import") (part "SMD-RES-10K-1%-1/8W(0805)"))
    )
    (comp (ref "R144")
      (value "104")
      (footprint "eagle-import:R0805")
      (fields (field (name "MPN") "RC0805FR-0710KL"))
      (libsource (lib "eagle-import") (part "SMD-RES-10K-1%-1/8W(0805)"))
    )
    (comp (ref "R145")
      (value "4701")
      (footprint "eagle-import:R0805")
      (fields (field (name "MPN") "RC0805JR-074K7L"))
      (libsource (lib "eagle-import") (part "SMD-RES-4.7K-5%-1/8W(0805)"))
    )
    (comp (ref "R146")
      (value "1002")
      (footprint "eagle-import:R0805")
      (fields (field (name "MPN") "RC0805FR-0710KL"))
      (libsource (lib "eagle-import") (part "SMD-RES-10K-1%-1/8W(0805)"))
    )
    (comp (ref "R147")
      (value "1002")
      (footprint "eagle-import:R0805")
      (fields (field (name "MPN") "RC0805FR-0710KL"))
      (libsource (lib "eagle-import") (part "SMD-RES-10K-1%-1/8W(0805)"))
    )
    (comp (ref "R148")
      (value "1502")
      (footprint "eagle-import:R0805")
      (fields (field (name "MPN") "RC0805FR-0710KL"))
      (libsource (lib "eagle-import") (part "SMD-RES-10K-1%-1/8W(0805)"))
    )
    (comp (ref "R149")
      (value "104")
      (footprint "eagle-import:R0805")
      (fields (field (name "MPN") "RC0805FR-0710KL"))
      (libsource (lib "eagle-import") (part "SMD-RES-10K-1%-1/8W(0805)"))
    )
    (comp (ref "R150")
      (value "104")
      (footprint "eagle-import:R0805")
      (fields (field (name "MPN") "RC0805FR-0710KL"))
      (libsource (lib "eagle-import") (part "SMD-RES-10K-1%-1/8W(0805)"))
    )
    (comp (ref "R151")
      (value "1502")
      (footprint "eagle-import:R0805")
      (fields (field (name "MPN") "RC0805FR-0710KL"))
      (libsource (lib "eagle-import") (part "SMD-RES-10K-1%-1/8W(0805)"))
    )
    (comp (ref "R152")
      (value "1002")
      (footprint "eagle-import:R0805")
      (fields (field (name "MPN") "RC0805FR-0710KL"))
      (libsource (lib "eagle-import") (part "SMD-RES-10K-1%-1/8W(0805)"))
    )
    (comp (ref "R153")
      (value "2201")
      (footprint "eagle-import:R0805")
      (fields (field (name "MPN") "RC0805JR-072K2L"))
      (libsource (lib "eagle-import") (part "SMD-RES-2.2K-5%-1/8W(0805)"))
    )
    (comp (ref "R154")
      (value "1002")
      (footprint "eagle-import:R0805")
      (fields (field (name "MPN") "RC0805FR-0710KL"))
      (libsource (lib "eagle-import") (part "SMD-RES-10K-1%-1/8W(0805)"))
    )
    (comp (ref "R155")
      (value "4701")
      (footprint "eagle-import:R0805")
      (fields (field (name "MPN") "RC0805JR-074K7L"))
      (libsource (lib "eagle-import") (part "SMD-RES-4.7K-5%-1/8W(0805)"))
    )
    (comp (ref "R156")
      (value "2702")
      (footprint "eagle-import:R0805")
      (fields (field (name "MPN") "RC0805JR-074K7L"))
      (libsource (lib "eagle-import") (part "SMD-RES-4.7K-5%-1/8W(0805)"))
    )
    (comp (ref "R157")
      (value "102")
      (footprint "eagle-import:R0805")
      (fields (field (name "MPN") "RC0805JR-071KL"))
      (libsource (lib "eagle-import") (part "SMD-RES-1K-5%-1/8W(0805)"))
    )
    (comp (ref "R158")
      (value "R_user")
      (footprint "eagle-import:R0805")
      (libsource (lib "eagle-import") (part "R-EU_R0805"))
    )
    (comp (ref "R159")
      (value "100")
      (footprint "eagle-import:R0805")
      (fields (field (name "MPN") "RC0805JR-07220RL"))
      (libsource (lib "eagle-import") (part "SMD-RES-220R-5%-1/8W(0805)"))
    )
    (comp (ref "R160")
      (value "(101)")
      (footprint "eagle-import:R0805")
      (fields (field (name "MPN") "RC0805JR-07100RL"))
      (libsource (lib "eagle-import") (part "SMD-RES-100R-5%-1/8W(0805)"))
    )
    (comp (ref "R161")
      (value "(1000)")
      (footprint "eagle-import:R0805")
      (fields (field (name "MPN") "RC0805JR-07100RL"))
      (libsource (lib "eagle-import") (part "SMD-RES-100R-5%-1/8W(0805)"))
    )
    (comp (ref "R162")
      (value "102")
      (footprint "eagle-import:R0805")
      (fields (field (name "MPN") "RC0805JR-071KL"))
      (libsource (lib "eagle-import") (part "SMD-RES-1K-5%-1/8W(0805)"))
    )
    (comp (ref "R163")
      (value "13")
      (footprint "eagle-import:R1206")
      (fields (field (name "MPN") "RC1206JR-0713RL"))
      (libsource (lib "eagle-import") (part "SMD-RES-13R-5%-1/4W(1206)"))
    )
    (comp (ref "R164")
      (value "13")
      (footprint "eagle-import:R1206")
      (fields (field (name "MPN") "RC1206JR-0713RL"))
      (libsource (lib "eagle-import") (part "SMD-RES-13R-5%-1/4W(1206)"))
    )
    (comp (ref "R165")
      (value "2702")
      (footprint "eagle-import:R0805")
      (fields (field (name "MPN") "RC0805JR-074K7L"))
      (libsource (lib "eagle-import") (part "SMD-RES-4.7K-5%-1/8W(0805)"))
    )
    (comp (ref "R166")
      (value "4701")
      (footprint "eagle-import:R0805")
      (fields (field (name "MPN") "RC0805JR-074K7L"))
      (libsource (lib "eagle-import") (part "SMD-RES-4.7K-5%-1/8W(0805)"))
    )
    (comp (ref "R167")
      (value "100")
      (footprint "eagle-import:R0805")
      (fields (field (name "MPN") "RC0805JR-072K2L"))
      (libsource (lib "eagle-import") (part "SMD-RES-2.2K-5%-1/8W(0805)"))
    )
    (comp (ref "R168")
      (value "(101)")
      (footprint "eagle-import:R0805")
      (fields (field (name "MPN") "RC0805JR-072K2L"))
      (libsource (lib "eagle-import") (part "SMD-RES-2.2K-5%-1/8W(0805)"))
    )
    (comp (ref "R169")
      (value "104")
      (footprint "eagle-import:R0805")
      (fields (field (name "MPN") "RC0805FR-0710KL"))
      (libsource (lib "eagle-import") (part "SMD-RES-10K-1%-1/8W(0805)"))
    )
    (comp (ref "R170")
      (value "104")
      (footprint "eagle-import:R0805")
      (fields (field (name "MPN") "RC0805FR-0710KL"))
      (libsource (lib "eagle-import") (part "SMD-RES-10K-1%-1/8W(0805)"))
    )
    (comp (ref "R171")
      (value "(1002)")
      (footprint "eagle-import:R0805")
      (fields (field (name "MPN") "RC0805FR-0710KL"))
      (libsource (lib "eagle-import") (part "SMD-RES-10K-1%-1/8W(0805)"))
    )
    (comp (ref "R172")
      (value "2702")
      (footprint "eagle-import:R0805")
      (fields (field (name "MPN") "RC0805FR-0710KL"))
      (libsource (lib "eagle-import") (part "SMD-RES-10K-1%-1/8W(0805)"))
    )
    (comp (ref "R173")
      (value "47")
      (footprint "eagle-import:V235_17_1MM")
      (libsource (lib "eagle-import") (part "R-EU_V235/17_1MM"))
    )
    (comp (ref "R174")
      (value "47")
      (footprint "eagle-import:V235_17_1MM")
      (libsource (lib "eagle-import") (part "R-EU_V235/17_1MM"))
    )
    (comp (ref "R175")
      (value "2702")
      (footprint "eagle-import:R0805")
      (fields (field (name "MPN") "RC0805JR-074K7L"))
      (libsource (lib "eagle-import") (part "SMD-RES-4.7K-5%-1/8W(0805)"))
    )
    (comp (ref "R176")
      (value "2201")
      (footprint "eagle-import:R0805")
      (fields (field (name "MPN") "RC0805JR-072K2L"))
      (libsource (lib "eagle-import") (part "SMD-RES-2.2K-5%-1/8W(0805)"))
    )
    (comp (ref "R177")
      (value "(1002)")
      (footprint "eagle-import:R0805")
      (fields (field (name "MPN") "RC0805JR-074K7L"))
      (libsource (lib "eagle-import") (part "SMD-RES-4.7K-5%-1/8W(0805)"))
    )
    (comp (ref "R178")
      (value "1002")
      (footprint "eagle-import:R0805")
      (fields (field (name "MPN") "RC0805FR-0710KL"))
      (libsource (lib "eagle-import") (part "SMD-RES-10K-1%-1/8W(0805)"))
    )
    (comp (ref "R179")
      (value "102")
      (footprint "eagle-import:R0805")
      (fields (field (name "MPN") "RC0805JR-071KL"))
      (libsource (lib "eagle-import") (part "SMD-RES-1K-5%-1/8W(0805)"))
    )
    (comp (ref "R180")
      (value "2702")
      (footprint "eagle-import:R0805")
      (fields (field (name "MPN") "RC0805JR-074K7L"))
      (libsource (lib "eagle-import") (part "SMD-RES-4.7K-5%-1/8W(0805)"))
    )
    (comp (ref "R181")
      (value "102")
      (footprint "eagle-import:R0805")
      (fields (field (name "MPN") "RC0805JR-071KL"))
      (libsource (lib "eagle-import") (part "SMD-RES-1K-5%-1/8W(0805)"))
    )
    (comp (ref "R182")
      (value "102")
      (footprint "eagle-import:R0805")
      (fields (field (name "MPN") "RC0805JR-071KL"))
      (libsource (lib "eagle-import") (part "SMD-RES-1K-5%-1/8W(0805)"))
    )
    (comp (ref "R183")
      (value "13")
      (footprint "eagle-import:R1206")
      (fields (field (name "MPN") "RC1206JR-0713RL"))
      (libsource (lib "eagle-import") (part "SMD-RES-13R-5%-1/4W(1206)"))
    )
    (comp (ref "R184")
      (value "R_user")
      (footprint "eagle-import:R0805")
      (libsource (lib "eagle-import") (part "R-EU_R0805"))
    )
    (comp (ref "SJ4") (value "SJ") (footprint "eagle-import:SJ") (libsource (lib "eagle-import") (part "SJ")))
    (comp (ref "START3")
      (value "TPSB2.0")
      (footprint "eagle-import:B2.0")
      (libsource (lib "eagle-import") (part "TPSB2.0"))
    )
    (comp (ref "TP70")
      (value "TPSB2.0")
      (footprint "eagle-import:B2.0")
      (libsource (lib "eagle-import") (part "TPSB2.0"))
    )
    (comp (ref "TP71")
      (value "TPSB2.0")
      (footprint "eagle-import:B2.0")
      (libsource (lib "eagle-import") (part "TPSB2.0"))
    )
    (comp (ref "TP72")
      (value "TPSB2.0")
      (footprint "eagle-import:B2.0")
      (libsource (lib "eagle-import") (part "TPSB2.0"))
    )
    (comp (ref "TP73")
      (value "TPSB2.0")
      (footprint "eagle-import:B2.0")
      (libsource (lib "eagle-import") (part "TPSB2.0"))
    )
    (comp (ref "TP74")
      (value "TPSB2.0")
      (footprint "eagle-import:B2.0")
      (libsource (lib "eagle-import") (part "TPSB2.0"))
    )
    (comp (ref "TP75")
      (value "TPSB2.0")
      (footprint "eagle-import:B2.0")
      (libsource (lib "eagle-import") (part "TPSB2.0"))
    )
    (comp (ref "TP76")
      (value "TPSB2.0")
      (footprint "eagle-import:B2.0")
      (libsource (lib "eagle-import") (part "TPSB2.0"))
    )
    (comp (ref "TP77")
      (value "TPSB2.0")
      (footprint "eagle-import:B2.0")
      (libsource (lib "eagle-import") (part "TPSB2.0"))
    )
    (comp (ref "TP78")
      (value "TPSB2.0")
      (footprint "eagle-import:B2.0")
      (libsource (lib "eagle-import") (part "TPSB2.0"))
    )
    (comp (ref "TP79")
      (value "TPSB2.0")
      (footprint "eagle-import:B2.0")
      (libsource (lib "eagle-import") (part "TPSB2.0"))
    )
    (comp (ref "TP80")
      (value "TPSB2.0")
      (footprint "eagle-import:B2.0")
      (libsource (lib "eagle-import") (part "TPSB2.0"))
    )
    (comp (ref "TP81")
      (value "TPSB2.0")
      (footprint "eagle-import:B2.0")
      (libsource (lib "eagle-import") (part "TPSB2.0"))
    )
    (comp (ref "TP82")
      (value "TPSB2.0")
      (footprint "eagle-import:B2.0")
      (libsource (lib "eagle-import") (part "TPSB2.0"))
    )
    (comp (ref "TP83")
      (value "TPSB2.0")
      (footprint "eagle-import:B2.0")
      (libsource (lib "eagle-import") (part "TPSB2.0"))
    )
    (comp (ref "TP84")
      (value "TPSB2.0")
      (footprint "eagle-import:B2.0")
      (libsource (lib "eagle-import") (part "TPSB2.0"))
    )
    (comp (ref "TP85")
      (value "TPSB2.0")
      (footprint "eagle-import:B2.0")
      (libsource (lib "eagle-import") (part "TPSB2.0"))
    )
    (comp (ref "TP86")
      (value "TPSB2.0")
      (footprint "eagle-import:B2.0")
      (libsource (lib "eagle-import") (part "TPSB2.0"))
    )
    (comp (ref "TP87")
      (value "TPSB2.0")
      (footprint "eagle-import:B2.0")
      (libsource (lib "eagle-import") (part "TPSB2.0"))
    )
    (comp (ref "TP88")
      (value "TPSB1,27")
      (footprint "eagle-import:B1,27")
      (libsource (lib "eagle-import") (part "TPSB1,27"))
    )
    (comp (ref "TP89")
      (value "TPSB2.0")
      (footprint "eagle-import:B2.0")
      (libsource (lib "eagle-import") (part "TPSB2.0"))
    )
    (comp (ref "TP90")
      (value "TPSB2.0")
      (footprint "eagle-import:B2.0")
      (libsource (lib "eagle-import") (part "TPSB2.0"))
    )
    (comp (ref "TP91")
      (value "TPSB2.0")
      (footprint "eagle-import:B2.0")
      (libsource (lib "eagle-import") (part "TPSB2.0"))
    )
    (comp (ref "TP92")
      (value "TPSB2.0")
      (footprint "eagle-import:B2.0")
      (libsource (lib "eagle-import") (part "TPSB2.0"))
    )
    (comp (ref "X10")
      (value "CON_BMWV2")
      (footprint "eagle-import:24-PIN_V2")
      (libsource (lib "eagle-import") (part "CON_BMWV2"))
    )
    (comp (ref "X11")
      (value "22-23-2051")
      (footprint "eagle-import:22-23-2051")
      (fields (field (name "MF") "MOLEX"))
      (libsource (lib "eagle-import") (part "22-23-2051"))
    )
    (comp (ref "X12")
      (value "22-23-2021")
      (footprint "eagle-import:22-23-2021")
      (fields (field (name "MF") "MOLEX"))
      (libsource (lib "eagle-import") (part "22-23-2021"))
    )
    (comp (ref "6V8")
      (value "TPSB2.0")
      (footprint "eagle-import:B2.0")
      (libsource (lib "eagle-import") (part "TPSB2.0"))
    )
    (comp (ref "10V8")
      (value "TPSB2.0")
      (footprint "eagle-import:B2.0")
      (libsource (lib "eagle-import") (part "TPSB2.0"))
    )
    (comp (ref "17")
      (value "2081-1132")
      (footprint "eagle-import:12-PIN")
      (libsource (lib "eagle-import") (part "2081-1132"))
    )
    (comp (ref "18")
      (value "2081-1132")
      (footprint "eagle-import:12-PIN")
      (libsource (lib "eagle-import") (part "2081-1132"))
    )
    (comp (ref "C81")
      (value "100u")
      (footprint "eagle-import:C1206")
      (fields (field (name "MPN") "GRM31CR60J107ME39L"))
      (libsource (lib "eagle-import") (part "CERAMIC-100UF-6.3V-20%-X5R(1206)"))
    )
    (comp (ref "C82")
      (value "100u")
      (footprint "eagle-import:C1206")
      (fields (field (name "MPN") "GRM31CR60J107ME39L"))
      (libsource (lib "eagle-import") (part "CERAMIC-100UF-6.3V-20%-X5R(1206)"))
    )
    (comp (ref "C83")
      (value "100nF,")
      (footprint "eagle-import:C0805")
      (fields (field (name "MPN") "CC0805KRX7R9BB104"))
      (libsource (lib "eagle-import") (part "CERAMIC-100NF-50V-10%-X7R(0805)"))
    )
    (comp (ref "C84")
      (value "4.7u")
      (footprint "eagle-import:C0805")
      (fields (field (name "MPN") "CC0805KKX5R8BB475"))
      (libsource (lib "eagle-import") (part "CERAMIC-4.7UF-25V-10%-X5R(0805)"))
    )
    (comp (ref "C85")
      (value "100nF.")
      (footprint "eagle-import:C0805")
      (fields (field (name "MPN") "CC0805KRX7R9BB104"))
      (libsource (lib "eagle-import") (part "CERAMIC-100NF-50V-10%-X7R(0805)"))
    )
    (comp (ref "C86")
      (value "100nF.")
      (footprint "eagle-import:C0805")
      (fields (field (name "MPN") "CC0805KRX7R9BB104"))
      (libsource (lib "eagle-import") (part "CERAMIC-100NF-50V-10%-X7R(0805)"))
    )
    (comp (ref "C87")
      (value "2.2nF")
      (footprint "eagle-import:C0805")
      (fields (field (name "MPN") "CC0805KRX7R9BB104"))
      (libsource (lib "eagle-import") (part "CERAMIC-100NF-50V-10%-X7R(0805)"))
    )
    (comp (ref "C88")
      (value "100nF")
      (footprint "eagle-import:C0805")
      (fields (field (name "MPN") "CC0805KRX7R9BB104"))
      (libsource (lib "eagle-import") (part "CERAMIC-100NF-50V-10%-X7R(0805)"))
    )
    (comp (ref "C89")
      (value "100nF")
      (footprint "eagle-import:C0805")
      (fields (field (name "MPN") "CC0805KRX7R9BB104"))
      (libsource (lib "eagle-import") (part "CERAMIC-100NF-50V-10%-X7R(0805)"))
    )
    (comp (ref "C90")
      (value "100nF,")
      (footprint "eagle-import:C0805")
      (fields (field (name "MPN") "CC0805KRX7R9BB104"))
      (libsource (lib "eagle-import") (part "CERAMIC-100NF-50V-10%-X7R(0805)"))
    )
    (comp (ref "D97")
      (value "1N4007")
      (footprint "eagle-import:DO-214AC")
      (libsource (lib "eagle-import") (part "DIODE-GEN-PURPOSE-1KV-1A(DO-214AC)"))
    )
    (comp (ref "D98")
      (value "1N4007,")
      (footprint "eagle-import:DO-214AC")
      (fields (field (name "MPN") "1N4007"))
      (libsource (lib "eagle-import") (part "DIODE-GEN-PURPOSE-1KV-1A(DO-214AC)"))
    )
    (comp (ref "D99")
      (value "1N4007,")
      (footprint "eagle-import:DO-214AC")
      (fields (field (name "MPN") "1N4007"))
      (libsource (lib "eagle-import") (part "DIODE-GEN-PURPOSE-1KV-1A(DO-214AC)"))
    )
    (comp (ref "D100")
      (value "1N4007.")
      (footprint "eagle-import:DO-214AC")
      (fields (field (name "MPN") "1N4007"))
      (libsource (lib "eagle-import") (part "DIODE-GEN-PURPOSE-1KV-1A(DO-214AC)"))
    )
    (comp (ref "D101")
      (value "1N5817")
      (footprint "eagle-import:DO-214AC_SLIM")
      (libsource (lib "eagle-import") (part "DIODE-GEN-PURPOSE-1KV-1A(DO-214AC)DO-214AC/1206"))
    )
    (comp (ref "D102")
      (value "1N5817.")
      (footprint "eagle-import:DO-214AC_SLIM")
      (libsource (lib "eagle-import") (part "DIODE-GEN-PURPOSE-1KV-1A(DO-214AC)DO-214AC/1206"))
    )
    (comp (ref "D103")
      (value "1N5817.")
      (footprint "eagle-import:DO-214AC_SLIM")
      (libsource (lib "eagle-import") (part "DIODE-GEN-PURPOSE-1KV-1A(DO-214AC)DO-214AC/1206"))
    )
    (comp (ref "D104")
      (value "1N5817")
      (footprint "eagle-import:DO-214AC_SLIM")
      (libsource (lib "eagle-import") (part "DIODE-GEN-PURPOSE-1KV-1A(DO-214AC)DO-214AC/1206"))
    )
    (comp (ref "D105")
      (value "1N4007.")
      (footprint "eagle-import:DO-214AC")
      (fields (field (name "MPN") "1N4007"))
      (libsource (lib "eagle-import") (part "DIODE-GEN-PURPOSE-1KV-1A(DO-214AC)"))
    )
    (comp (ref "D106")
      (value "1N4007")
      (footprint "eagle-import:DO-214AC")
      (libsource (lib "eagle-import") (part "DIODE-GEN-PURPOSE-1KV-1A(DO-214AC)"))
    )
    (comp (ref "D107")
      (value "SM6T")
      (footprint "eagle-import:DO214AA")
      (libsource (lib "eagle-import") (part "SM6T"))
    )
    (comp (ref "D108")
      (value "SM6TDO214AA_BI")
      (footprint "eagle-import:DO214AA_BI")
      (libsource (lib "eagle-import") (part "SM6TDO214AA_BI"))
    )
    (comp (ref "FID33")
      (value "FIDUCIAL")
      (footprint "eagle-import:FIDUCIAL_1MM")
      (libsource (lib "eagle-import") (part "FIDUCIAL"))
    )
    (comp (ref "FID34")
      (value "FIDUCIAL")
      (footprint "eagle-import:FIDUCIAL_1MM")
      (libsource (lib "eagle-import") (part "FIDUCIAL"))
    )
    (comp (ref "FID35")
      (value "FIDUCIAL")
      (footprint "eagle-import:FIDUCIAL_1MM")
      (libsource (lib "eagle-import") (part "FIDUCIAL"))
    )
    (comp (ref "FID36")
      (value "FIDUCIAL")
      (footprint "eagle-import:FIDUCIAL_1MM")
      (libsource (lib "eagle-import") (part "FIDUCIAL"))
    )
    (comp (ref "IC89")
      (value "4028")
      (footprint "eagle-import:SO16")
      (libsource (lib "eagle-import") (part "4028D"))
    )
    (comp (ref "IC90")
      (value "6V pos")
      (footprint "eagle-import:78LXX")
      (libsource (lib "eagle-import") (part "v-reg_78LXX"))
    )
    (comp (ref "IC91")
      (value "317TO202H_NOHOLE")
      (footprint "eagle-import:TO220H_NOHOLE")
      (libsource (lib "eagle-import") (part "317TO202H_NOHOLE"))
    )
    (comp (ref "IC92")
      (value "ULN2004")
      (footprint "eagle-import:SO16")
      (libsource (lib "eagle-import") (part "ULN2004AD"))
    )
    (comp (ref "IC93")
      (value "LM339")
      (footprint "eagle-import:SO14")
      (libsource (lib "eagle-import") (part "LM339D"))
    )
    (comp (ref "IC94")
      (value "78L06")
      (footprint "eagle-import:SOT89_ROUND")
      (libsource (lib "eagle-import") (part "78LXXSOT89_ROUND"))
    )
    (comp (ref "IC95")
      (value "555")
      (footprint "eagle-import:SO08")
      (libsource (lib "eagle-import") (part "555DNE"))
    )
    (comp (ref "IC96")
      (value "4538")
      (footprint "eagle-import:SO16")
      (libsource (lib "eagle-import") (part "4538D"))
    )
    (comp (ref "IC97")
      (value "78L10")
      (footprint "eagle-import:SOT89_ROUND")
      (libsource (lib "eagle-import") (part "78LXXSOT89_ROUND"))
    )
    (comp (ref "IC98")
      (value "LM2904")
      (footprint "eagle-import:SO08")
      (libsource (lib "eagle-import") (part "LM358D"))
    )
    (comp (ref "IC99")
      (value "NUP4304SOT457_R")
      (footprint "eagle-import:SOT457R_PHILIPS")
      (libsource (lib "eagle-import") (part "NUP4304SOT457_R"))
    )
    (comp (ref "JP41")
      (value "JP2EJP2_SMALLPADS")
      (footprint "eagle-import:JP2_SMALLPADS")
      (libsource (lib "eagle-import") (part "JP2EJP2_SMALLPADS"))
    )
    (comp (ref "JP42")
      (value "JP2E_ORIG")
      (footprint "eagle-import:JP2_ORIG_SMALLPADS")
      (libsource (lib "eagle-import") (part "JP2E_ORIG"))
    )
    (comp (ref "JP43")
      (value "JP2EJP2_SMALLPADS")
      (footprint "eagle-import:JP2_SMALLPADS")
      (libsource (lib "eagle-import") (part "JP2EJP2_SMALLPADS"))
    )
    (comp (ref "JP44")
      (value "JP2EJP2_SMALLPADS")
      (footprint "eagle-import:JP2_SMALLPADS")
      (libsource (lib "eagle-import") (part "JP2EJP2_SMALLPADS"))
    )
    (comp (ref "JP45")
      (value "JP2EJP2_SMALLPADS")
      (footprint "eagle-import:JP2_SMALLPADS")
      (libsource (lib "eagle-import") (part "JP2EJP2_SMALLPADS"))
    )
    (comp (ref "LED49")
      (value "LEDLD260")
      (footprint "eagle-import:LD260")
      (libsource (lib "eagle-import") (part "LEDLD260"))
    )
    (comp (ref "LED50")
      (value "LEDLD260")
      (footprint "eagle-import:LD260")
      (libsource (lib "eagle-import") (part "LEDLD260"))
    )
    (comp (ref "LED51")
      (value "LEDLD260")
      (footprint "eagle-import:LD260")
      (libsource (lib "eagle-import") (part "LEDLD260"))
    )
    (comp (ref "LED52")
      (value "LEDLD260")
      (footprint "eagle-import:LD260")
      (libsource (lib "eagle-import") (part "LEDLD260"))
    )
    (comp (ref "LED53")
      (value "LEDLD260")
      (footprint "eagle-import:LD260")
      (libsource (lib "eagle-import") (part "LEDLD260"))
    )
    (comp (ref "LED54")
      (value "LEDLD260")
      (footprint "eagle-import:LD260")
      (libsource (lib "eagle-import") (part "LEDLD260"))
    )
    (comp (ref "Q57")
      (value "BA")
      (footprint "eagle-import:SOT89")
      (libsource (lib "eagle-import") (part "PNP-TRANSISTOR_SOT89"))
    )
    (comp (ref "Q58")
      (value "BA.")
      (footprint "eagle-import:SOT89")
      (libsource (lib "eagle-import") (part "PNP-TRANSISTOR_SOT89"))
    )
    (comp (ref "Q59")
      (value "BA.")
      (footprint "eagle-import:SOT89")
      (libsource (lib "eagle-import") (part "PNP-TRANSISTOR_SOT89"))
    )
    (comp (ref "Q60")
      (value "BA")
      (footprint "eagle-import:SOT89")
      (libsource (lib "eagle-import") (part "PNP-TRANSISTOR_SOT89"))
    )
    (comp (ref "Q61")
      (value "MY")
      (footprint "eagle-import:SOT89")
      (libsource (lib "eagle-import") (part "NPN-TRANSISTOR_SOT89"))
    )
    (comp (ref "Q62")
      (value "J1")
      (footprint "eagle-import:SOT-23")
      (fields (field (name "MPN") "BSS138W-7-F"))
      (libsource (lib "eagle-import") (part "SMD-MOSFET-N-CH-50V-200MA-BSS138W-7-F(SOT-23)"))
    )
    (comp (ref "Q63")
      (value "J1")
      (footprint "eagle-import:SOT-23")
      (fields (field (name "MPN") "BSS138W-7-F"))
      (libsource (lib "eagle-import") (part "SMD-MOSFET-N-CH-50V-200MA-BSS138W-7-F(SOT-23)"))
    )
    (comp (ref "R369")
      (value "47")
      (footprint "eagle-import:V235_17_1MM")
      (libsource (lib "eagle-import") (part "R-EU_V235/17_1MM"))
    )
    (comp (ref "R370")
      (value "13")
      (footprint "eagle-import:R1206")
      (fields (field (name "MPN") "RC1206JR-0713RL"))
      (libsource (lib "eagle-import") (part "SMD-RES-13R-5%-1/4W(1206)"))
    )
    (comp (ref "R371")
      (value "47")
      (footprint "eagle-import:V235_17_1MM")
      (libsource (lib "eagle-import") (part "R-EU_V235/17_1MM"))
    )
    (comp (ref "R372")
      (value "104")
      (footprint "eagle-import:R0805")
      (fields (field (name "MPN") "RC0805FR-0710KL"))
      (libsource (lib "eagle-import") (part "SMD-RES-10K-1%-1/8W(0805)"))
    )
    (comp (ref "R373")
      (value "104")
      (footprint "eagle-import:R0805")
      (fields (field (name "MPN") "RC0805FR-0710KL"))
      (libsource (lib "eagle-import") (part "SMD-RES-10K-1%-1/8W(0805)"))
    )
    (comp (ref "R374")
      (value "104")
      (footprint "eagle-import:R0805")
      (fields (field (name "MPN") "RC0805FR-0710KL"))
      (libsource (lib "eagle-import") (part "SMD-RES-10K-1%-1/8W(0805)"))
    )
    (comp (ref "R375")
      (value "4701")
      (footprint "eagle-import:R0805")
      (fields (field (name "MPN") "RC0805JR-074K7L"))
      (libsource (lib "eagle-import") (part "SMD-RES-4.7K-5%-1/8W(0805)"))
    )
    (comp (ref "R376")
      (value "1002")
      (footprint "eagle-import:R0805")
      (fields (field (name "MPN") "RC0805FR-0710KL"))
      (libsource (lib "eagle-import") (part "SMD-RES-10K-1%-1/8W(0805)"))
    )
    (comp (ref "R377")
      (value "1002")
      (footprint "eagle-import:R0805")
      (fields (field (name "MPN") "RC0805FR-0710KL"))
      (libsource (lib "eagle-import") (part "SMD-RES-10K-1%-1/8W(0805)"))
    )
    (comp (ref "R378")
      (value "1502")
      (footprint "eagle-import:R0805")
      (fields (field (name "MPN") "RC0805FR-0710KL"))
      (libsource (lib "eagle-import") (part "SMD-RES-10K-1%-1/8W(0805)"))
    )
    (comp (ref "R379")
      (value "104")
      (footprint "eagle-import:R0805")
      (fields (field (name "MPN") "RC0805FR-0710KL"))
      (libsource (lib "eagle-import") (part "SMD-RES-10K-1%-1/8W(0805)"))
    )
    (comp (ref "R380")
      (value "104")
      (footprint "eagle-import:R0805")
      (fields (field (name "MPN") "RC0805FR-0710KL"))
      (libsource (lib "eagle-import") (part "SMD-RES-10K-1%-1/8W(0805)"))
    )
    (comp (ref "R381")
      (value "1502")
      (footprint "eagle-import:R0805")
      (fields (field (name "MPN") "RC0805FR-0710KL"))
      (libsource (lib "eagle-import") (part "SMD-RES-10K-1%-1/8W(0805)"))
    )
    (comp (ref "R382")
      (value "1002")
      (footprint "eagle-import:R0805")
      (fields (field (name "MPN") "RC0805FR-0710KL"))
      (libsource (lib "eagle-import") (part "SMD-RES-10K-1%-1/8W(0805)"))
    )
    (comp (ref "R383")
      (value "2201")
      (footprint "eagle-import:R0805")
      (fields (field (name "MPN") "RC0805JR-072K2L"))
      (libsource (lib "eagle-import") (part "SMD-RES-2.2K-5%-1/8W(0805)"))
    )
    (comp (ref "R384")
      (value "1002")
      (footprint "eagle-import:R0805")
      (fields (field (name "MPN") "RC0805FR-0710KL"))
      (libsource (lib "eagle-import") (part "SMD-RES-10K-1%-1/8W(0805)"))
    )
    (comp (ref "R385")
      (value "4701")
      (footprint "eagle-import:R0805")
      (fields (field (name "MPN") "RC0805JR-074K7L"))
      (libsource (lib "eagle-import") (part "SMD-RES-4.7K-5%-1/8W(0805)"))
    )
    (comp (ref "R386")
      (value "2702")
      (footprint "eagle-import:R0805")
      (fields (field (name "MPN") "RC0805JR-074K7L"))
      (libsource (lib "eagle-import") (part "SMD-RES-4.7K-5%-1/8W(0805)"))
    )
    (comp (ref "R387")
      (value "102")
      (footprint "eagle-import:R0805")
      (fields (field (name "MPN") "RC0805JR-071KL"))
      (libsource (lib "eagle-import") (part "SMD-RES-1K-5%-1/8W(0805)"))
    )
    (comp (ref "R388")
      (value "R_user")
      (footprint "eagle-import:R0805")
      (libsource (lib "eagle-import") (part "R-EU_R0805"))
    )
    (comp (ref "R389")
      (value "100")
      (footprint "eagle-import:R0805")
      (fields (field (name "MPN") "RC0805JR-07220RL"))
      (libsource (lib "eagle-import") (part "SMD-RES-220R-5%-1/8W(0805)"))
    )
    (comp (ref "R390")
      (value "(101)")
      (footprint "eagle-import:R0805")
      (fields (field (name "MPN") "RC0805JR-07100RL"))
      (libsource (lib "eagle-import") (part "SMD-RES-100R-5%-1/8W(0805)"))
    )
    (comp (ref "R391")
      (value "(1000)")
      (footprint "eagle-import:R0805")
      (fields (field (name "MPN") "RC0805JR-07100RL"))
      (libsource (lib "eagle-import") (part "SMD-RES-100R-5%-1/8W(0805)"))
    )
    (comp (ref "R392")
      (value "102")
      (footprint "eagle-import:R0805")
      (fields (field (name "MPN") "RC0805JR-071KL"))
      (libsource (lib "eagle-import") (part "SMD-RES-1K-5%-1/8W(0805)"))
    )
    (comp (ref "R393")
      (value "13")
      (footprint "eagle-import:R1206")
      (fields (field (name "MPN") "RC1206JR-0713RL"))
      (libsource (lib "eagle-import") (part "SMD-RES-13R-5%-1/4W(1206)"))
    )
    (comp (ref "R394")
      (value "13")
      (footprint "eagle-import:R1206")
      (fields (field (name "MPN") "RC1206JR-0713RL"))
      (libsource (lib "eagle-import") (part "SMD-RES-13R-5%-1/4W(1206)"))
    )
    (comp (ref "R395")
      (value "2702")
      (footprint "eagle-import:R0805")
      (fields (field (name "MPN") "RC0805JR-074K7L"))
      (libsource (lib "eagle-import") (part "SMD-RES-4.7K-5%-1/8W(0805)"))
    )
    (comp (ref "R396")
      (value "4701")
      (footprint "eagle-import:R0805")
      (fields (field (name "MPN") "RC0805JR-074K7L"))
      (libsource (lib "eagle-import") (part "SMD-RES-4.7K-5%-1/8W(0805)"))
    )
    (comp (ref "R397")
      (value "100")
      (footprint "eagle-import:R0805")
      (fields (field (name "MPN") "RC0805JR-072K2L"))
      (libsource (lib "eagle-import") (part "SMD-RES-2.2K-5%-1/8W(0805)"))
    )
    (comp (ref "R398")
      (value "(101)")
      (footprint "eagle-import:R0805")
      (fields (field (name "MPN") "RC0805JR-072K2L"))
      (libsource (lib "eagle-import") (part "SMD-RES-2.2K-5%-1/8W(0805)"))
    )
    (comp (ref "R399")
      (value "104")
      (footprint "eagle-import:R0805")
      (fields (field (name "MPN") "RC0805FR-0710KL"))
      (libsource (lib "eagle-import") (part "SMD-RES-10K-1%-1/8W(0805)"))
    )
    (comp (ref "R400")
      (value "104")
      (footprint "eagle-import:R0805")
      (fields (field (name "MPN") "RC0805FR-0710KL"))
      (libsource (lib "eagle-import") (part "SMD-RES-10K-1%-1/8W(0805)"))
    )
    (comp (ref "R401")
      (value "(1002)")
      (footprint "eagle-import:R0805")
      (fields (field (name "MPN") "RC0805FR-0710KL"))
      (libsource (lib "eagle-import") (part "SMD-RES-10K-1%-1/8W(0805)"))
    )
    (comp (ref "R402")
      (value "2702")
      (footprint "eagle-import:R0805")
      (fields (field (name "MPN") "RC0805FR-0710KL"))
      (libsource (lib "eagle-import") (part "SMD-RES-10K-1%-1/8W(0805)"))
    )
    (comp (ref "R403")
      (value "47")
      (footprint "eagle-import:V235_17_1MM")
      (libsource (lib "eagle-import") (part "R-EU_V235/17_1MM"))
    )
    (comp (ref "R404")
      (value "47")
      (footprint "eagle-import:V235_17_1MM")
      (libsource (lib "eagle-import") (part "R-EU_V235/17_1MM"))
    )
    (comp (ref "R405")
      (value "2702")
      (footprint "eagle-import:R0805")
      (fields (field (name "MPN") "RC0805JR-074K7L"))
      (libsource (lib "eagle-import") (part "SMD-RES-4.7K-5%-1/8W(0805)"))
    )
    (comp (ref "R406")
      (value "2201")
      (footprint "eagle-import:R0805")
      (fields (field (name "MPN") "RC0805JR-072K2L"))
      (libsource (lib "eagle-import") (part "SMD-RES-2.2K-5%-1/8W(0805)"))
    )
    (comp (ref "R407")
      (value "(1002)")
      (footprint "eagle-import:R0805")
      (fields (field (name "MPN") "RC0805JR-074K7L"))
      (libsource (lib "eagle-import") (part "SMD-RES-4.7K-5%-1/8W(0805)"))
    )
    (comp (ref "R408")
      (value "1002")
      (footprint "eagle-import:R0805")
      (fields (field (name "MPN") "RC0805FR-0710KL"))
      (libsource (lib "eagle-import") (part "SMD-RES-10K-1%-1/8W(0805)"))
    )
    (comp (ref "R409")
      (value "102")
      (footprint "eagle-import:R0805")
      (fields (field (name "MPN") "RC0805JR-071KL"))
      (libsource (lib "eagle-import") (part "SMD-RES-1K-5%-1/8W(0805)"))
    )
    (comp (ref "R410")
      (value "2702")
      (footprint "eagle-import:R0805")
      (fields (field (name "MPN") "RC0805JR-074K7L"))
      (libsource (lib "eagle-import") (part "SMD-RES-4.7K-5%-1/8W(0805)"))
    )
    (comp (ref "R411")
      (value "102")
      (footprint "eagle-import:R0805")
      (fields (field (name "MPN") "RC0805JR-071KL"))
      (libsource (lib "eagle-import") (part "SMD-RES-1K-5%-1/8W(0805)"))
    )
    (comp (ref "R412")
      (value "102")
      (footprint "eagle-import:R0805")
      (fields (field (name "MPN") "RC0805JR-071KL"))
      (libsource (lib "eagle-import") (part "SMD-RES-1K-5%-1/8W(0805)"))
    )
    (comp (ref "R413")
      (value "13")
      (footprint "eagle-import:R1206")
      (fields (field (name "MPN") "RC1206JR-0713RL"))
      (libsource (lib "eagle-import") (part "SMD-RES-13R-5%-1/4W(1206)"))
    )
    (comp (ref "R414")
      (value "R_user")
      (footprint "eagle-import:R0805")
      (libsource (lib "eagle-import") (part "R-EU_R0805"))
    )
    (comp (ref "SJ9") (value "SJ") (footprint "eagle-import:SJ") (libsource (lib "eagle-import") (part "SJ")))
    (comp (ref "START8")
      (value "TPSB2.0")
      (footprint "eagle-import:B2.0")
      (libsource (lib "eagle-import") (part "TPSB2.0"))
    )
    (comp (ref "TP185")
      (value "TPSB2.0")
      (footprint "eagle-import:B2.0")
      (libsource (lib "eagle-import") (part "TPSB2.0"))
    )
    (comp (ref "TP186")
      (value "TPSB2.0")
      (footprint "eagle-import:B2.0")
      (libsource (lib "eagle-import") (part "TPSB2.0"))
    )
    (comp (ref "TP187")
      (value "TPSB2.0")
      (footprint "eagle-import:B2.0")
      (libsource (lib "eagle-import") (part "TPSB2.0"))
    )
    (comp (ref "TP188")
      (value "TPSB2.0")
      (footprint "eagle-import:B2.0")
      (libsource (lib "eagle-import") (part "TPSB2.0"))
    )
    (comp (ref "TP189")
      (value "TPSB2.0")
      (footprint "eagle-import:B2.0")
      (libsource (lib "eagle-import") (part "TPSB2.0"))
    )
    (comp (ref "TP190")
      (value "TPSB2.0")
      (footprint "eagle-import:B2.0")
      (libsource (lib "eagle-import") (part "TPSB2.0"))
    )
    (comp (ref "TP191")
      (value "TPSB2.0")
      (footprint "eagle-import:B2.0")
      (libsource (lib "eagle-import") (part "TPSB2.0"))
    )
    (comp (ref "TP192")
      (value "TPSB2.0")
      (footprint "eagle-import:B2.0")
      (libsource (lib "eagle-import") (part "TPSB2.0"))
    )
    (comp (ref "TP193")
      (value "TPSB2.0")
      (footprint "eagle-import:B2.0")
      (libsource (lib "eagle-import") (part "TPSB2.0"))
    )
    (comp (ref "TP194")
      (value "TPSB2.0")
      (footprint "eagle-import:B2.0")
      (libsource (lib "eagle-import") (part "TPSB2.0"))
    )
    (comp (ref "TP195")
      (value "TPSB2.0")
      (footprint "eagle-import:B2.0")
      (libsource (lib "eagle-import") (part "TPSB2.0"))
    )
    (comp (ref "TP196")
      (value "TPSB2.0")
      (footprint "eagle-import:B2.0")
      (libsource (lib "eagle-import") (part "TPSB2.0"))
    )
    (comp (ref "TP197")
      (value "TPSB2.0")
      (footprint "eagle-import:B2.0")
      (libsource (lib "eagle-import") (part "TPSB2.0"))
    )
    (comp (ref "TP198")
      (value "TPSB2.0")
      (footprint "eagle-import:B2.0")
      (libsource (lib "eagle-import") (part "TPSB2.0"))
    )
    (comp (ref "TP199")
      (value "TPSB2.0")
      (footprint "eagle-import:B2.0")
      (libsource (lib "eagle-import") (part "TPSB2.0"))
    )
    (comp (ref "TP200")
      (value "TPSB2.0")
      (footprint "eagle-import:B2.0")
      (libsource (lib "eagle-import") (part "TPSB2.0"))
    )
    (comp (ref "TP201")
      (value "TPSB2.0")
      (footprint "eagle-import:B2.0")
      (libsource (lib "eagle-import") (part "TPSB2.0"))
    )
    (comp (ref "TP202")
      (value "TPSB2.0")
      (footprint "eagle-import:B2.0")
      (libsource (lib "eagle-import") (part "TPSB2.0"))
    )
    (comp (ref "TP203")
      (value "TPSB1,27")
      (footprint "eagle-import:B1,27")
      (libsource (lib "eagle-import") (part "TPSB1,27"))
    )
    (comp (ref "TP204")
      (value "TPSB2.0")
      (footprint "eagle-import:B2.0")
      (libsource (lib "eagle-import") (part "TPSB2.0"))
    )
    (comp (ref "TP205")
      (value "TPSB2.0")
      (footprint "eagle-import:B2.0")
      (libsource (lib "eagle-import") (part "TPSB2.0"))
    )
    (comp (ref "TP206")
      (value "TPSB2.0")
      (footprint "eagle-import:B2.0")
      (libsource (lib "eagle-import") (part "TPSB2.0"))
    )
    (comp (ref "TP207")
      (value "TPSB2.0")
      (footprint "eagle-import:B2.0")
      (libsource (lib "eagle-import") (part "TPSB2.0"))
    )
    (comp (ref "X25")
      (value "CON_BMWV2")
      (footprint "eagle-import:24-PIN_V2")
      (libsource (lib "eagle-import") (part "CON_BMWV2"))
    )
    (comp (ref "X26")
      (value "22-23-2051")
      (footprint "eagle-import:22-23-2051")
      (fields (field (name "MF") "MOLEX"))
      (libsource (lib "eagle-import") (part "22-23-2051"))
    )
    (comp (ref "X27")
      (value "22-23-2021")
      (footprint "eagle-import:22-23-2021")
      (fields (field (name "MF") "MOLEX"))
      (libsource (lib "eagle-import") (part "22-23-2021"))
    )
    (comp (ref "6V9")
      (value "TPSB2.0")
      (footprint "eagle-import:B2.0")
      (libsource (lib "eagle-import") (part "TPSB2.0"))
    )
    (comp (ref "10V9")
      (value "TPSB2.0")
      (footprint "eagle-import:B2.0")
      (libsource (lib "eagle-import") (part "TPSB2.0"))
    )
    (comp (ref "19")
      (value "2081-1132")
      (footprint "eagle-import:12-PIN")
      (libsource (lib "eagle-import") (part "2081-1132"))
    )
    (comp (ref "20")
      (value "2081-1132")
      (footprint "eagle-import:12-PIN")
      (libsource (lib "eagle-import") (part "2081-1132"))
    )
    (comp (ref "C91")
      (value "100u")
      (footprint "eagle-import:C1206")
      (fields (field (name "MPN") "GRM31CR60J107ME39L"))
      (libsource (lib "eagle-import") (part "CERAMIC-100UF-6.3V-20%-X5R(1206)"))
    )
    (comp (ref "C92")
      (value "100u")
      (footprint "eagle-import:C1206")
      (fields (field (name "MPN") "GRM31CR60J107ME39L"))
      (libsource (lib "eagle-import") (part "CERAMIC-100UF-6.3V-20%-X5R(1206)"))
    )
    (comp (ref "C93")
      (value "100nF,")
      (footprint "eagle-import:C0805")
      (fields (field (name "MPN") "CC0805KRX7R9BB104"))
      (libsource (lib "eagle-import") (part "CERAMIC-100NF-50V-10%-X7R(0805)"))
    )
    (comp (ref "C94")
      (value "4.7u")
      (footprint "eagle-import:C0805")
      (fields (field (name "MPN") "CC0805KKX5R8BB475"))
      (libsource (lib "eagle-import") (part "CERAMIC-4.7UF-25V-10%-X5R(0805)"))
    )
    (comp (ref "C95")
      (value "100nF.")
      (footprint "eagle-import:C0805")
      (fields (field (name "MPN") "CC0805KRX7R9BB104"))
      (libsource (lib "eagle-import") (part "CERAMIC-100NF-50V-10%-X7R(0805)"))
    )
    (comp (ref "C96")
      (value "100nF.")
      (footprint "eagle-import:C0805")
      (fields (field (name "MPN") "CC0805KRX7R9BB104"))
      (libsource (lib "eagle-import") (part "CERAMIC-100NF-50V-10%-X7R(0805)"))
    )
    (comp (ref "C97")
      (value "2.2nF")
      (footprint "eagle-import:C0805")
      (fields (field (name "MPN") "CC0805KRX7R9BB104"))
      (libsource (lib "eagle-import") (part "CERAMIC-100NF-50V-10%-X7R(0805)"))
    )
    (comp (ref "C98")
      (value "100nF")
      (footprint "eagle-import:C0805")
      (fields (field (name "MPN") "CC0805KRX7R9BB104"))
      (libsource (lib "eagle-import") (part "CERAMIC-100NF-50V-10%-X7R(0805)"))
    )
    (comp (ref "C99")
      (value "100nF")
      (footprint "eagle-import:C0805")
      (fields (field (name "MPN") "CC0805KRX7R9BB104"))
      (libsource (lib "eagle-import") (part "CERAMIC-100NF-50V-10%-X7R(0805)"))
    )
    (comp (ref "C100")
      (value "100nF,")
      (footprint "eagle-import:C0805")
      (fields (field (name "MPN") "CC0805KRX7R9BB104"))
      (libsource (lib "eagle-import") (part "CERAMIC-100NF-50V-10%-X7R(0805)"))
    )
    (comp (ref "D109")
      (value "1N4007")
      (footprint "eagle-import:DO-214AC")
      (libsource (lib "eagle-import") (part "DIODE-GEN-PURPOSE-1KV-1A(DO-214AC)"))
    )
    (comp (ref "D110")
      (value "1N4007,")
      (footprint "eagle-import:DO-214AC")
      (fields (field (name "MPN") "1N4007"))
      (libsource (lib "eagle-import") (part "DIODE-GEN-PURPOSE-1KV-1A(DO-214AC)"))
    )
    (comp (ref "D111")
      (value "1N4007,")
      (footprint "eagle-import:DO-214AC")
      (fields (field (name "MPN") "1N4007"))
      (libsource (lib "eagle-import") (part "DIODE-GEN-PURPOSE-1KV-1A(DO-214AC)"))
    )
    (comp (ref "D112")
      (value "1N4007.")
      (footprint "eagle-import:DO-214AC")
      (fields (field (name "MPN") "1N4007"))
      (libsource (lib "eagle-import") (part "DIODE-GEN-PURPOSE-1KV-1A(DO-214AC)"))
    )
    (comp (ref "D113")
      (value "1N5817")
      (footprint "eagle-import:DO-214AC_SLIM")
      (libsource (lib "eagle-import") (part "DIODE-GEN-PURPOSE-1KV-1A(DO-214AC)DO-214AC/1206"))
    )
    (comp (ref "D114")
      (value "1N5817.")
      (footprint "eagle-import:DO-214AC_SLIM")
      (libsource (lib "eagle-import") (part "DIODE-GEN-PURPOSE-1KV-1A(DO-214AC)DO-214AC/1206"))
    )
    (comp (ref "D115")
      (value "1N5817.")
      (footprint "eagle-import:DO-214AC_SLIM")
      (libsource (lib "eagle-import") (part "DIODE-GEN-PURPOSE-1KV-1A(DO-214AC)DO-214AC/1206"))
    )
    (comp (ref "D116")
      (value "1N5817")
      (footprint "eagle-import:DO-214AC_SLIM")
      (libsource (lib "eagle-import") (part "DIODE-GEN-PURPOSE-1KV-1A(DO-214AC)DO-214AC/1206"))
    )
    (comp (ref "D117")
      (value "1N4007.")
      (footprint "eagle-import:DO-214AC")
      (fields (field (name "MPN") "1N4007"))
      (libsource (lib "eagle-import") (part "DIODE-GEN-PURPOSE-1KV-1A(DO-214AC)"))
    )
    (comp (ref "D118")
      (value "1N4007")
      (footprint "eagle-import:DO-214AC")
      (libsource (lib "eagle-import") (part "DIODE-GEN-PURPOSE-1KV-1A(DO-214AC)"))
    )
    (comp (ref "D119")
      (value "SM6T")
      (footprint "eagle-import:DO214AA")
      (libsource (lib "eagle-import") (part "SM6T"))
    )
    (comp (ref "D120")
      (value "SM6TDO214AA_BI")
      (footprint "eagle-import:DO214AA_BI")
      (libsource (lib "eagle-import") (part "SM6TDO214AA_BI"))
    )
    (comp (ref "FID37")
      (value "FIDUCIAL")
      (footprint "eagle-import:FIDUCIAL_1MM")
      (libsource (lib "eagle-import") (part "FIDUCIAL"))
    )
    (comp (ref "FID38")
      (value "FIDUCIAL")
      (footprint "eagle-import:FIDUCIAL_1MM")
      (libsource (lib "eagle-import") (part "FIDUCIAL"))
    )
    (comp (ref "FID39")
      (value "FIDUCIAL")
      (footprint "eagle-import:FIDUCIAL_1MM")
      (libsource (lib "eagle-import") (part "FIDUCIAL"))
    )
    (comp (ref "FID40")
      (value "FIDUCIAL")
      (footprint "eagle-import:FIDUCIAL_1MM")
      (libsource (lib "eagle-import") (part "FIDUCIAL"))
    )
    (comp (ref "IC100")
      (value "4028")
      (footprint "eagle-import:SO16")
      (libsource (lib "eagle-import") (part "4028D"))
    )
    (comp (ref "IC101")
      (value "6V pos")
      (footprint "eagle-import:78LXX")
      (libsource (lib "eagle-import") (part "v-reg_78LXX"))
    )
    (comp (ref "IC102")
      (value "317TO202H_NOHOLE")
      (footprint "eagle-import:TO220H_NOHOLE")
      (libsource (lib "eagle-import") (part "317TO202H_NOHOLE"))
    )
    (comp (ref "IC103")
      (value "ULN2004")
      (footprint "eagle-import:SO16")
      (libsource (lib "eagle-import") (part "ULN2004AD"))
    )
    (comp (ref "IC104")
      (value "LM339")
      (footprint "eagle-import:SO14")
      (libsource (lib "eagle-import") (part "LM339D"))
    )
    (comp (ref "IC105")
      (value "78L06")
      (footprint "eagle-import:SOT89_ROUND")
      (libsource (lib "eagle-import") (part "78LXXSOT89_ROUND"))
    )
    (comp (ref "IC106")
      (value "555")
      (footprint "eagle-import:SO08")
      (libsource (lib "eagle-import") (part "555DNE"))
    )
    (comp (ref "IC107")
      (value "4538")
      (footprint "eagle-import:SO16")
      (libsource (lib "eagle-import") (part "4538D"))
    )
    (comp (ref "IC108")
      (value "78L10")
      (footprint "eagle-import:SOT89_ROUND")
      (libsource (lib "eagle-import") (part "78LXXSOT89_ROUND"))
    )
    (comp (ref "IC109")
      (value "LM2904")
      (footprint "eagle-import:SO08")
      (libsource (lib "eagle-import") (part "LM358D"))
    )
    (comp (ref "IC110")
      (value "NUP4304SOT457_R")
      (footprint "eagle-import:SOT457R_PHILIPS")
      (libsource (lib "eagle-import") (part "NUP4304SOT457_R"))
    )
    (comp (ref "JP46")
      (value "JP2EJP2_SMALLPADS")
      (footprint "eagle-import:JP2_SMALLPADS")
      (libsource (lib "eagle-import") (part "JP2EJP2_SMALLPADS"))
    )
    (comp (ref "JP47")
      (value "JP2E_ORIG")
      (footprint "eagle-import:JP2_ORIG_SMALLPADS")
      (libsource (lib "eagle-import") (part "JP2E_ORIG"))
    )
    (comp (ref "JP48")
      (value "JP2EJP2_SMALLPADS")
      (footprint "eagle-import:JP2_SMALLPADS")
      (libsource (lib "eagle-import") (part "JP2EJP2_SMALLPADS"))
    )
    (comp (ref "JP49")
      (value "JP2EJP2_SMALLPADS")
      (footprint "eagle-import:JP2_SMALLPADS")
      (libsource (lib "eagle-import") (part "JP2EJP2_SMALLPADS"))
    )
    (comp (ref "JP50")
      (value "JP2EJP2_SMALLPADS")
      (footprint "eagle-import:JP2_SMALLPADS")
      (libsource (lib "eagle-import") (part "JP2EJP2_SMALLPADS"))
    )
    (comp (ref "LED55")
      (value "LEDLD260")
      (footprint "eagle-import:LD260")
      (libsource (lib "eagle-import") (part "LEDLD260"))
    )
    (comp (ref "LED56")
      (value "LEDLD260")
      (footprint "eagle-import:LD260")
      (libsource (lib "eagle-import") (part "LEDLD260"))
    )
    (comp (ref "LED57")
      (value "LEDLD260")
      (footprint "eagle-import:LD260")
      (libsource (lib "eagle-import") (part "LEDLD260"))
    )
    (comp (ref "LED58")
      (value "LEDLD260")
      (footprint "eagle-import:LD260")
      (libsource (lib "eagle-import") (part "LEDLD260"))
    )
    (comp (ref "LED59")
      (value "LEDLD260")
      (footprint "eagle-import:LD260")
      (libsource (lib "eagle-import") (part "LEDLD260"))
    )
    (comp (ref "LED60")
      (value "LEDLD260")
      (footprint "eagle-import:LD260")
      (libsource (lib "eagle-import") (part "LEDLD260"))
    )
    (comp (ref "Q64")
      (value "BA")
      (footprint "eagle-import:SOT89")
      (libsource (lib "eagle-import") (part "PNP-TRANSISTOR_SOT89"))
    )
    (comp (ref "Q65")
      (value "BA.")
      (footprint "eagle-import:SOT89")
      (libsource (lib "eagle-import") (part "PNP-TRANSISTOR_SOT89"))
    )
    (comp (ref "Q66")
      (value "BA.")
      (footprint "eagle-import:SOT89")
      (libsource (lib "eagle-import") (part "PNP-TRANSISTOR_SOT89"))
    )
    (comp (ref "Q67")
      (value "BA")
      (footprint "eagle-import:SOT89")
      (libsource (lib "eagle-import") (part "PNP-TRANSISTOR_SOT89"))
    )
    (comp (ref "Q68")
      (value "MY")
      (footprint "eagle-import:SOT89")
      (libsource (lib "eagle-import") (part "NPN-TRANSISTOR_SOT89"))
    )
    (comp (ref "Q69")
      (value "J1")
      (footprint "eagle-import:SOT-23")
      (fields (field (name "MPN") "BSS138W-7-F"))
      (libsource (lib "eagle-import") (part "SMD-MOSFET-N-CH-50V-200MA-BSS138W-7-F(SOT-23)"))
    )
    (comp (ref "Q70")
      (value "J1")
      (footprint "eagle-import:SOT-23")
      (fields (field (name "MPN") "BSS138W-7-F"))
      (libsource (lib "eagle-import") (part "SMD-MOSFET-N-CH-50V-200MA-BSS138W-7-F(SOT-23)"))
    )
    (comp (ref "R415")
      (value "47")
      (footprint "eagle-import:V235_17_1MM")
      (libsource (lib "eagle-import") (part "R-EU_V235/17_1MM"))
    )
    (comp (ref "R416")
      (value "13")
      (footprint "eagle-import:R1206")
      (fields (field (name "MPN") "RC1206JR-0713RL"))
      (libsource (lib "eagle-import") (part "SMD-RES-13R-5%-1/4W(1206)"))
    )
    (comp (ref "R417")
      (value "47")
      (footprint "eagle-import:V235_17_1MM")
      (libsource (lib "eagle-import") (part "R-EU_V235/17_1MM"))
    )
    (comp (ref "R418")
      (value "104")
      (footprint "eagle-import:R0805")
      (fields (field (name "MPN") "RC0805FR-0710KL"))
      (libsource (lib "eagle-import") (part "SMD-RES-10K-1%-1/8W(0805)"))
    )
    (comp (ref "R419")
      (value "104")
      (footprint "eagle-import:R0805")
      (fields (field (name "MPN") "RC0805FR-0710KL"))
      (libsource (lib "eagle-import") (part "SMD-RES-10K-1%-1/8W(0805)"))
    )
    (comp (ref "R420")
      (value "104")
      (footprint "eagle-import:R0805")
      (fields (field (name "MPN") "RC0805FR-0710KL"))
      (libsource (lib "eagle-import") (part "SMD-RES-10K-1%-1/8W(0805)"))
    )
    (comp (ref "R421")
      (value "4701")
      (footprint "eagle-import:R0805")
      (fields (field (name "MPN") "RC0805JR-074K7L"))
      (libsource (lib "eagle-import") (part "SMD-RES-4.7K-5%-1/8W(0805)"))
    )
    (comp (ref "R422")
      (value "1002")
      (footprint "eagle-import:R0805")
      (fields (field (name "MPN") "RC0805FR-0710KL"))
      (libsource (lib "eagle-import") (part "SMD-RES-10K-1%-1/8W(0805)"))
    )
    (comp (ref "R423")
      (value "1002")
      (footprint "eagle-import:R0805")
      (fields (field (name "MPN") "RC0805FR-0710KL"))
      (libsource (lib "eagle-import") (part "SMD-RES-10K-1%-1/8W(0805)"))
    )
    (comp (ref "R424")
      (value "1502")
      (footprint "eagle-import:R0805")
      (fields (field (name "MPN") "RC0805FR-0710KL"))
      (libsource (lib "eagle-import") (part "SMD-RES-10K-1%-1/8W(0805)"))
    )
    (comp (ref "R425")
      (value "104")
      (footprint "eagle-import:R0805")
      (fields (field (name "MPN") "RC0805FR-0710KL"))
      (libsource (lib "eagle-import") (part "SMD-RES-10K-1%-1/8W(0805)"))
    )
    (comp (ref "R426")
      (value "104")
      (footprint "eagle-import:R0805")
      (fields (field (name "MPN") "RC0805FR-0710KL"))
      (libsource (lib "eagle-import") (part "SMD-RES-10K-1%-1/8W(0805)"))
    )
    (comp (ref "R427")
      (value "1502")
      (footprint "eagle-import:R0805")
      (fields (field (name "MPN") "RC0805FR-0710KL"))
      (libsource (lib "eagle-import") (part "SMD-RES-10K-1%-1/8W(0805)"))
    )
    (comp (ref "R428")
      (value "1002")
      (footprint "eagle-import:R0805")
      (fields (field (name "MPN") "RC0805FR-0710KL"))
      (libsource (lib "eagle-import") (part "SMD-RES-10K-1%-1/8W(0805)"))
    )
    (comp (ref "R429")
      (value "2201")
      (footprint "eagle-import:R0805")
      (fields (field (name "MPN") "RC0805JR-072K2L"))
      (libsource (lib "eagle-import") (part "SMD-RES-2.2K-5%-1/8W(0805)"))
    )
    (comp (ref "R430")
      (value "1002")
      (footprint "eagle-import:R0805")
      (fields (field (name "MPN") "RC0805FR-0710KL"))
      (libsource (lib "eagle-import") (part "SMD-RES-10K-1%-1/8W(0805)"))
    )
    (comp (ref "R431")
      (value "4701")
      (footprint "eagle-import:R0805")
      (fields (field (name "MPN") "RC0805JR-074K7L"))
      (libsource (lib "eagle-import") (part "SMD-RES-4.7K-5%-1/8W(0805)"))
    )
    (comp (ref "R432")
      (value "2702")
      (footprint "eagle-import:R0805")
      (fields (field (name "MPN") "RC0805JR-074K7L"))
      (libsource (lib "eagle-import") (part "SMD-RES-4.7K-5%-1/8W(0805)"))
    )
    (comp (ref "R433")
      (value "102")
      (footprint "eagle-import:R0805")
      (fields (field (name "MPN") "RC0805JR-071KL"))
      (libsource (lib "eagle-import") (part "SMD-RES-1K-5%-1/8W(0805)"))
    )
    (comp (ref "R434")
      (value "R_user")
      (footprint "eagle-import:R0805")
      (libsource (lib "eagle-import") (part "R-EU_R0805"))
    )
    (comp (ref "R435")
      (value "100")
      (footprint "eagle-import:R0805")
      (fields (field (name "MPN") "RC0805JR-07220RL"))
      (libsource (lib "eagle-import") (part "SMD-RES-220R-5%-1/8W(0805)"))
    )
    (comp (ref "R436")
      (value "(101)")
      (footprint "eagle-import:R0805")
      (fields (field (name "MPN") "RC0805JR-07100RL"))
      (libsource (lib "eagle-import") (part "SMD-RES-100R-5%-1/8W(0805)"))
    )
    (comp (ref "R437")
      (value "(1000)")
      (footprint "eagle-import:R0805")
      (fields (field (name "MPN") "RC0805JR-07100RL"))
      (libsource (lib "eagle-import") (part "SMD-RES-100R-5%-1/8W(0805)"))
    )
    (comp (ref "R438")
      (value "102")
      (footprint "eagle-import:R0805")
      (fields (field (name "MPN") "RC0805JR-071KL"))
      (libsource (lib "eagle-import") (part "SMD-RES-1K-5%-1/8W(0805)"))
    )
    (comp (ref "R439")
      (value "13")
      (footprint "eagle-import:R1206")
      (fields (field (name "MPN") "RC1206JR-0713RL"))
      (libsource (lib "eagle-import") (part "SMD-RES-13R-5%-1/4W(1206)"))
    )
    (comp (ref "R440")
      (value "13")
      (footprint "eagle-import:R1206")
      (fields (field (name "MPN") "RC1206JR-0713RL"))
      (libsource (lib "eagle-import") (part "SMD-RES-13R-5%-1/4W(1206)"))
    )
    (comp (ref "R441")
      (value "2702")
      (footprint "eagle-import:R0805")
      (fields (field (name "MPN") "RC0805JR-074K7L"))
      (libsource (lib "eagle-import") (part "SMD-RES-4.7K-5%-1/8W(0805)"))
    )
    (comp (ref "R442")
      (value "4701")
      (footprint "eagle-import:R0805")
      (fields (field (name "MPN") "RC0805JR-074K7L"))
      (libsource (lib "eagle-import") (part "SMD-RES-4.7K-5%-1/8W(0805)"))
    )
    (comp (ref "R443")
      (value "100")
      (footprint "eagle-import:R0805")
      (fields (field (name "MPN") "RC0805JR-072K2L"))
      (libsource (lib "eagle-import") (part "SMD-RES-2.2K-5%-1/8W(0805)"))
    )
    (comp (ref "R444")
      (value "(101)")
      (footprint "eagle-import:R0805")
      (fields (field (name "MPN") "RC0805JR-072K2L"))
      (libsource (lib "eagle-import") (part "SMD-RES-2.2K-5%-1/8W(0805)"))
    )
    (comp (ref "R445")
      (value "104")
      (footprint "eagle-import:R0805")
      (fields (field (name "MPN") "RC0805FR-0710KL"))
      (libsource (lib "eagle-import") (part "SMD-RES-10K-1%-1/8W(0805)"))
    )
    (comp (ref "R446")
      (value "104")
      (footprint "eagle-import:R0805")
      (fields (field (name "MPN") "RC0805FR-0710KL"))
      (libsource (lib "eagle-import") (part "SMD-RES-10K-1%-1/8W(0805)"))
    )
    (comp (ref "R447")
      (value "(1002)")
      (footprint "eagle-import:R0805")
      (fields (field (name "MPN") "RC0805FR-0710KL"))
      (libsource (lib "eagle-import") (part "SMD-RES-10K-1%-1/8W(0805)"))
    )
    (comp (ref "R448")
      (value "2702")
      (footprint "eagle-import:R0805")
      (fields (field (name "MPN") "RC0805FR-0710KL"))
      (libsource (lib "eagle-import") (part "SMD-RES-10K-1%-1/8W(0805)"))
    )
    (comp (ref "R449")
      (value "47")
      (footprint "eagle-import:V235_17_1MM")
      (libsource (lib "eagle-import") (part "R-EU_V235/17_1MM"))
    )
    (comp (ref "R450")
      (value "47")
      (footprint "eagle-import:V235_17_1MM")
      (libsource (lib "eagle-import") (part "R-EU_V235/17_1MM"))
    )
    (comp (ref "R451")
      (value "2702")
      (footprint "eagle-import:R0805")
      (fields (field (name "MPN") "RC0805JR-074K7L"))
      (libsource (lib "eagle-import") (part "SMD-RES-4.7K-5%-1/8W(0805)"))
    )
    (comp (ref "R452")
      (value "2201")
      (footprint "eagle-import:R0805")
      (fields (field (name "MPN") "RC0805JR-072K2L"))
      (libsource (lib "eagle-import") (part "SMD-RES-2.2K-5%-1/8W(0805)"))
    )
    (comp (ref "R453")
      (value "(1002)")
      (footprint "eagle-import:R0805")
      (fields (field (name "MPN") "RC0805JR-074K7L"))
      (libsource (lib "eagle-import") (part "SMD-RES-4.7K-5%-1/8W(0805)"))
    )
    (comp (ref "R454")
      (value "1002")
      (footprint "eagle-import:R0805")
      (fields (field (name "MPN") "RC0805FR-0710KL"))
      (libsource (lib "eagle-import") (part "SMD-RES-10K-1%-1/8W(0805)"))
    )
    (comp (ref "R455")
      (value "102")
      (footprint "eagle-import:R0805")
      (fields (field (name "MPN") "RC0805JR-071KL"))
      (libsource (lib "eagle-import") (part "SMD-RES-1K-5%-1/8W(0805)"))
    )
    (comp (ref "R456")
      (value "2702")
      (footprint "eagle-import:R0805")
      (fields (field (name "MPN") "RC0805JR-074K7L"))
      (libsource (lib "eagle-import") (part "SMD-RES-4.7K-5%-1/8W(0805)"))
    )
    (comp (ref "R457")
      (value "102")
      (footprint "eagle-import:R0805")
      (fields (field (name "MPN") "RC0805JR-071KL"))
      (libsource (lib "eagle-import") (part "SMD-RES-1K-5%-1/8W(0805)"))
    )
    (comp (ref "R458")
      (value "102")
      (footprint "eagle-import:R0805")
      (fields (field (name "MPN") "RC0805JR-071KL"))
      (libsource (lib "eagle-import") (part "SMD-RES-1K-5%-1/8W(0805)"))
    )
    (comp (ref "R459")
      (value "13")
      (footprint "eagle-import:R1206")
      (fields (field (name "MPN") "RC1206JR-0713RL"))
      (libsource (lib "eagle-import") (part "SMD-RES-13R-5%-1/4W(1206)"))
    )
    (comp (ref "R460")
      (value "R_user")
      (footprint "eagle-import:R0805")
      (libsource (lib "eagle-import") (part "R-EU_R0805"))
    )
    (comp (ref "SJ10")
      (value "SJ")
      (footprint "eagle-import:SJ")
      (libsource (lib "eagle-import") (part "SJ"))
    )
    (comp (ref "START9")
      (value "TPSB2.0")
      (footprint "eagle-import:B2.0")
      (libsource (lib "eagle-import") (part "TPSB2.0"))
    )
    (comp (ref "TP208")
      (value "TPSB2.0")
      (footprint "eagle-import:B2.0")
      (libsource (lib "eagle-import") (part "TPSB2.0"))
    )
    (comp (ref "TP209")
      (value "TPSB2.0")
      (footprint "eagle-import:B2.0")
      (libsource (lib "eagle-import") (part "TPSB2.0"))
    )
    (comp (ref "TP210")
      (value "TPSB2.0")
      (footprint "eagle-import:B2.0")
      (libsource (lib "eagle-import") (part "TPSB2.0"))
    )
    (comp (ref "TP211")
      (value "TPSB2.0")
      (footprint "eagle-import:B2.0")
      (libsource (lib "eagle-import") (part "TPSB2.0"))
    )
    (comp (ref "TP212")
      (value "TPSB2.0")
      (footprint "eagle-import:B2.0")
      (libsource (lib "eagle-import") (part "TPSB2.0"))
    )
    (comp (ref "TP213")
      (value "TPSB2.0")
      (footprint "eagle-import:B2.0")
      (libsource (lib "eagle-import") (part "TPSB2.0"))
    )
    (comp (ref "TP214")
      (value "TPSB2.0")
      (footprint "eagle-import:B2.0")
      (libsource (lib "eagle-import") (part "TPSB2.0"))
    )
    (comp (ref "TP215")
      (value "TPSB2.0")
      (footprint "eagle-import:B2.0")
      (libsource (lib "eagle-import") (part "TPSB2.0"))
    )
    (comp (ref "TP216")
      (value "TPSB2.0")
      (footprint "eagle-import:B2.0")
      (libsource (lib "eagle-import") (part "TPSB2.0"))
    )
    (comp (ref "TP217")
      (value "TPSB2.0")
      (footprint "eagle-import:B2.0")
      (libsource (lib "eagle-import") (part "TPSB2.0"))
    )
    (comp (ref "TP218")
      (value "TPSB2.0")
      (footprint "eagle-import:B2.0")
      (libsource (lib "eagle-import") (part "TPSB2.0"))
    )
    (comp (ref "TP219")
      (value "TPSB2.0")
      (footprint "eagle-import:B2.0")
      (libsource (lib "eagle-import") (part "TPSB2.0"))
    )
    (comp (ref "TP220")
      (value "TPSB2.0")
      (footprint "eagle-import:B2.0")
      (libsource (lib "eagle-import") (part "TPSB2.0"))
    )
    (comp (ref "TP221")
      (value "TPSB2.0")
      (footprint "eagle-import:B2.0")
      (libsource (lib "eagle-import") (part "TPSB2.0"))
    )
    (comp (ref "TP222")
      (value "TPSB2.0")
      (footprint "eagle-import:B2.0")
      (libsource (lib "eagle-import") (part "TPSB2.0"))
    )
    (comp (ref "TP223")
      (value "TPSB2.0")
      (footprint "eagle-import:B2.0")
      (libsource (lib "eagle-import") (part "TPSB2.0"))
    )
    (comp (ref "TP224")
      (value "TPSB2.0")
      (footprint "eagle-import:B2.0")
      (libsource (lib "eagle-import") (part "TPSB2.0"))
    )
    (comp (ref "TP225")
      (value "TPSB2.0")
      (footprint "eagle-import:B2.0")
      (libsource (lib "eagle-import") (part "TPSB2.0"))
    )
    (comp (ref "TP226")
      (value "TPSB1,27")
      (footprint "eagle-import:B1,27")
      (libsource (lib "eagle-import") (part "TPSB1,27"))
    )
    (comp (ref "TP227")
      (value "TPSB2.0")
      (footprint "eagle-import:B2.0")
      (libsource (lib "eagle-import") (part "TPSB2.0"))
    )
    (comp (ref "TP228")
      (value "TPSB2.0")
      (footprint "eagle-import:B2.0")
      (libsource (lib "eagle-import") (part "TPSB2.0"))
    )
    (comp (ref "TP229")
      (value "TPSB2.0")
      (footprint "eagle-import:B2.0")
      (libsource (lib "eagle-import") (part "TPSB2.0"))
    )
    (comp (ref "TP230")
      (value "TPSB2.0")
      (footprint "eagle-import:B2.0")
      (libsource (lib "eagle-import") (part "TPSB2.0"))
    )
    (comp (ref "X28")
      (value "CON_BMWV2")
      (footprint "eagle-import:24-PIN_V2")
      (libsource (lib "eagle-import") (part "CON_BMWV2"))
    )
    (comp (ref "X29")
      (value "22-23-2051")
      (footprint "eagle-import:22-23-2051")
      (fields (field (name "MF") "MOLEX"))
      (libsource (lib "eagle-import") (part "22-23-2051"))
    )
    (comp (ref "X30")
      (value "22-23-2021")
      (footprint "eagle-import:22-23-2021")
      (fields (field (name "MF") "MOLEX"))
      (libsource (lib "eagle-import") (part "22-23-2021"))
    )
    (comp (ref "6V6")
      (value "TPSB2.0")
      (footprint "eagle-import:B2.0")
      (libsource (lib "eagle-import") (part "TPSB2.0"))
    )
    (comp (ref "10V6")
      (value "TPSB2.0")
      (footprint "eagle-import:B2.0")
      (libsource (lib "eagle-import") (part "TPSB2.0"))
    )
    (comp (ref "13")
      (value "2081-1132")
      (footprint "eagle-import:12-PIN")
      (libsource (lib "eagle-import") (part "2081-1132"))
    )
    (comp (ref "14")
      (value "2081-1132")
      (footprint "eagle-import:12-PIN")
      (libsource (lib "eagle-import") (part "2081-1132"))
    )
    (comp (ref "C61")
      (value "100u")
      (footprint "eagle-import:C1206")
      (fields (field (name "MPN") "GRM31CR60J107ME39L"))
      (libsource (lib "eagle-import") (part "CERAMIC-100UF-6.3V-20%-X5R(1206)"))
    )
    (comp (ref "C62")
      (value "100u")
      (footprint "eagle-import:C1206")
      (fields (field (name "MPN") "GRM31CR60J107ME39L"))
      (libsource (lib "eagle-import") (part "CERAMIC-100UF-6.3V-20%-X5R(1206)"))
    )
    (comp (ref "C63")
      (value "100nF,")
      (footprint "eagle-import:C0805")
      (fields (field (name "MPN") "CC0805KRX7R9BB104"))
      (libsource (lib "eagle-import") (part "CERAMIC-100NF-50V-10%-X7R(0805)"))
    )
    (comp (ref "C64")
      (value "4.7u")
      (footprint "eagle-import:C0805")
      (fields (field (name "MPN") "CC0805KKX5R8BB475"))
      (libsource (lib "eagle-import") (part "CERAMIC-4.7UF-25V-10%-X5R(0805)"))
    )
    (comp (ref "C65")
      (value "100nF.")
      (footprint "eagle-import:C0805")
      (fields (field (name "MPN") "CC0805KRX7R9BB104"))
      (libsource (lib "eagle-import") (part "CERAMIC-100NF-50V-10%-X7R(0805)"))
    )
    (comp (ref "C66")
      (value "100nF.")
      (footprint "eagle-import:C0805")
      (fields (field (name "MPN") "CC0805KRX7R9BB104"))
      (libsource (lib "eagle-import") (part "CERAMIC-100NF-50V-10%-X7R(0805)"))
    )
    (comp (ref "C67")
      (value "2.2nF")
      (footprint "eagle-import:C0805")
      (fields (field (name "MPN") "CC0805KRX7R9BB104"))
      (libsource (lib "eagle-import") (part "CERAMIC-100NF-50V-10%-X7R(0805)"))
    )
    (comp (ref "C68")
      (value "100nF")
      (footprint "eagle-import:C0805")
      (fields (field (name "MPN") "CC0805KRX7R9BB104"))
      (libsource (lib "eagle-import") (part "CERAMIC-100NF-50V-10%-X7R(0805)"))
    )
    (comp (ref "C69")
      (value "100nF")
      (footprint "eagle-import:C0805")
      (fields (field (name "MPN") "CC0805KRX7R9BB104"))
      (libsource (lib "eagle-import") (part "CERAMIC-100NF-50V-10%-X7R(0805)"))
    )
    (comp (ref "C70")
      (value "100nF,")
      (footprint "eagle-import:C0805")
      (fields (field (name "MPN") "CC0805KRX7R9BB104"))
      (libsource (lib "eagle-import") (part "CERAMIC-100NF-50V-10%-X7R(0805)"))
    )
    (comp (ref "D73")
      (value "1N4007")
      (footprint "eagle-import:DO-214AC")
      (libsource (lib "eagle-import") (part "DIODE-GEN-PURPOSE-1KV-1A(DO-214AC)"))
    )
    (comp (ref "D74")
      (value "1N4007,")
      (footprint "eagle-import:DO-214AC")
      (fields (field (name "MPN") "1N4007"))
      (libsource (lib "eagle-import") (part "DIODE-GEN-PURPOSE-1KV-1A(DO-214AC)"))
    )
    (comp (ref "D75")
      (value "1N4007,")
      (footprint "eagle-import:DO-214AC")
      (fields (field (name "MPN") "1N4007"))
      (libsource (lib "eagle-import") (part "DIODE-GEN-PURPOSE-1KV-1A(DO-214AC)"))
    )
    (comp (ref "D76")
      (value "1N4007.")
      (footprint "eagle-import:DO-214AC")
      (fields (field (name "MPN") "1N4007"))
      (libsource (lib "eagle-import") (part "DIODE-GEN-PURPOSE-1KV-1A(DO-214AC)"))
    )
    (comp (ref "D77")
      (value "1N5817")
      (footprint "eagle-import:DO-214AC_SLIM")
      (libsource (lib "eagle-import") (part "DIODE-GEN-PURPOSE-1KV-1A(DO-214AC)DO-214AC/1206"))
    )
    (comp (ref "D78")
      (value "1N5817.")
      (footprint "eagle-import:DO-214AC_SLIM")
      (libsource (lib "eagle-import") (part "DIODE-GEN-PURPOSE-1KV-1A(DO-214AC)DO-214AC/1206"))
    )
    (comp (ref "D79")
      (value "1N5817.")
      (footprint "eagle-import:DO-214AC_SLIM")
      (libsource (lib "eagle-import") (part "DIODE-GEN-PURPOSE-1KV-1A(DO-214AC)DO-214AC/1206"))
    )
    (comp (ref "D80")
      (value "1N5817")
      (footprint "eagle-import:DO-214AC_SLIM")
      (libsource (lib "eagle-import") (part "DIODE-GEN-PURPOSE-1KV-1A(DO-214AC)DO-214AC/1206"))
    )
    (comp (ref "D81")
      (value "1N4007.")
      (footprint "eagle-import:DO-214AC")
      (fields (field (name "MPN") "1N4007"))
      (libsource (lib "eagle-import") (part "DIODE-GEN-PURPOSE-1KV-1A(DO-214AC)"))
    )
    (comp (ref "D82")
      (value "1N4007")
      (footprint "eagle-import:DO-214AC")
      (libsource (lib "eagle-import") (part "DIODE-GEN-PURPOSE-1KV-1A(DO-214AC)"))
    )
    (comp (ref "D83")
      (value "SM6T")
      (footprint "eagle-import:DO214AA")
      (libsource (lib "eagle-import") (part "SM6T"))
    )
    (comp (ref "D84")
      (value "SM6TDO214AA_BI")
      (footprint "eagle-import:DO214AA_BI")
      (libsource (lib "eagle-import") (part "SM6TDO214AA_BI"))
    )
    (comp (ref "FID25")
      (value "FIDUCIAL")
      (footprint "eagle-import:FIDUCIAL_1MM")
      (libsource (lib "eagle-import") (part "FIDUCIAL"))
    )
    (comp (ref "FID26")
      (value "FIDUCIAL")
      (footprint "eagle-import:FIDUCIAL_1MM")
      (libsource (lib "eagle-import") (part "FIDUCIAL"))
    )
    (comp (ref "FID27")
      (value "FIDUCIAL")
      (footprint "eagle-import:FIDUCIAL_1MM")
      (libsource (lib "eagle-import") (part "FIDUCIAL"))
    )
    (comp (ref "FID28")
      (value "FIDUCIAL")
      (footprint "eagle-import:FIDUCIAL_1MM")
      (libsource (lib "eagle-import") (part "FIDUCIAL"))
    )
    (comp (ref "IC67")
      (value "4028")
      (footprint "eagle-import:SO16")
      (libsource (lib "eagle-import") (part "4028D"))
    )
    (comp (ref "IC68")
      (value "6V pos")
      (footprint "eagle-import:78LXX")
      (libsource (lib "eagle-import") (part "v-reg_78LXX"))
    )
    (comp (ref "IC69")
      (value "317TO202H_NOHOLE")
      (footprint "eagle-import:TO220H_NOHOLE")
      (libsource (lib "eagle-import") (part "317TO202H_NOHOLE"))
    )
    (comp (ref "IC70")
      (value "ULN2004")
      (footprint "eagle-import:SO16")
      (libsource (lib "eagle-import") (part "ULN2004AD"))
    )
    (comp (ref "IC71")
      (value "LM339")
      (footprint "eagle-import:SO14")
      (libsource (lib "eagle-import") (part "LM339D"))
    )
    (comp (ref "IC72")
      (value "78L06")
      (footprint "eagle-import:SOT89_ROUND")
      (libsource (lib "eagle-import") (part "78LXXSOT89_ROUND"))
    )
    (comp (ref "IC73")
      (value "555")
      (footprint "eagle-import:SO08")
      (libsource (lib "eagle-import") (part "555DNE"))
    )
    (comp (ref "IC74")
      (value "4538")
      (footprint "eagle-import:SO16")
      (libsource (lib "eagle-import") (part "4538D"))
    )
    (comp (ref "IC75")
      (value "78L10")
      (footprint "eagle-import:SOT89_ROUND")
      (libsource (lib "eagle-import") (part "78LXXSOT89_ROUND"))
    )
    (comp (ref "IC76")
      (value "LM2904")
      (footprint "eagle-import:SO08")
      (libsource (lib "eagle-import") (part "LM358D"))
    )
    (comp (ref "IC77")
      (value "NUP4304SOT457_R")
      (footprint "eagle-import:SOT457R_PHILIPS")
      (libsource (lib "eagle-import") (part "NUP4304SOT457_R"))
    )
    (comp (ref "JP31")
      (value "JP2EJP2_SMALLPADS")
      (footprint "eagle-import:JP2_SMALLPADS")
      (libsource (lib "eagle-import") (part "JP2EJP2_SMALLPADS"))
    )
    (comp (ref "JP32")
      (value "JP2E_ORIG")
      (footprint "eagle-import:JP2_ORIG_SMALLPADS")
      (libsource (lib "eagle-import") (part "JP2E_ORIG"))
    )
    (comp (ref "JP33")
      (value "JP2EJP2_SMALLPADS")
      (footprint "eagle-import:JP2_SMALLPADS")
      (libsource (lib "eagle-import") (part "JP2EJP2_SMALLPADS"))
    )
    (comp (ref "JP34")
      (value "JP2EJP2_SMALLPADS")
      (footprint "eagle-import:JP2_SMALLPADS")
      (libsource (lib "eagle-import") (part "JP2EJP2_SMALLPADS"))
    )
    (comp (ref "JP35")
      (value "JP2EJP2_SMALLPADS")
      (footprint "eagle-import:JP2_SMALLPADS")
      (libsource (lib "eagle-import") (part "JP2EJP2_SMALLPADS"))
    )
    (comp (ref "LED37")
      (value "LEDLD260")
      (footprint "eagle-import:LD260")
      (libsource (lib "eagle-import") (part "LEDLD260"))
    )
    (comp (ref "LED38")
      (value "LEDLD260")
      (footprint "eagle-import:LD260")
      (libsource (lib "eagle-import") (part "LEDLD260"))
    )
    (comp (ref "LED39")
      (value "LEDLD260")
      (footprint "eagle-import:LD260")
      (libsource (lib "eagle-import") (part "LEDLD260"))
    )
    (comp (ref "LED40")
      (value "LEDLD260")
      (footprint "eagle-import:LD260")
      (libsource (lib "eagle-import") (part "LEDLD260"))
    )
    (comp (ref "LED41")
      (value "LEDLD260")
      (footprint "eagle-import:LD260")
      (libsource (lib "eagle-import") (part "LEDLD260"))
    )
    (comp (ref "LED42")
      (value "LEDLD260")
      (footprint "eagle-import:LD260")
      (libsource (lib "eagle-import") (part "LEDLD260"))
    )
    (comp (ref "Q43")
      (value "BA")
      (footprint "eagle-import:SOT89")
      (libsource (lib "eagle-import") (part "PNP-TRANSISTOR_SOT89"))
    )
    (comp (ref "Q44")
      (value "BA.")
      (footprint "eagle-import:SOT89")
      (libsource (lib "eagle-import") (part "PNP-TRANSISTOR_SOT89"))
    )
    (comp (ref "Q45")
      (value "BA.")
      (footprint "eagle-import:SOT89")
      (libsource (lib "eagle-import") (part "PNP-TRANSISTOR_SOT89"))
    )
    (comp (ref "Q46")
      (value "BA")
      (footprint "eagle-import:SOT89")
      (libsource (lib "eagle-import") (part "PNP-TRANSISTOR_SOT89"))
    )
    (comp (ref "Q47")
      (value "MY")
      (footprint "eagle-import:SOT89")
      (libsource (lib "eagle-import") (part "NPN-TRANSISTOR_SOT89"))
    )
    (comp (ref "Q48")
      (value "J1")
      (footprint "eagle-import:SOT-23")
      (fields (field (name "MPN") "BSS138W-7-F"))
      (libsource (lib "eagle-import") (part "SMD-MOSFET-N-CH-50V-200MA-BSS138W-7-F(SOT-23)"))
    )
    (comp (ref "Q49")
      (value "J1")
      (footprint "eagle-import:SOT-23")
      (fields (field (name "MPN") "BSS138W-7-F"))
      (libsource (lib "eagle-import") (part "SMD-MOSFET-N-CH-50V-200MA-BSS138W-7-F(SOT-23)"))
    )
    (comp (ref "R277")
      (value "47")
      (footprint "eagle-import:V235_17_1MM")
      (libsource (lib "eagle-import") (part "R-EU_V235/17_1MM"))
    )
    (comp (ref "R278")
      (value "13")
      (footprint "eagle-import:R1206")
      (fields (field (name "MPN") "RC1206JR-0713RL"))
      (libsource (lib "eagle-import") (part "SMD-RES-13R-5%-1/4W(1206)"))
    )
    (comp (ref "R279")
      (value "47")
      (footprint "eagle-import:V235_17_1MM")
      (libsource (lib "eagle-import") (part "R-EU_V235/17_1MM"))
    )
    (comp (ref "R280")
      (value "104")
      (footprint "eagle-import:R0805")
      (fields (field (name "MPN") "RC0805FR-0710KL"))
      (libsource (lib "eagle-import") (part "SMD-RES-10K-1%-1/8W(0805)"))
    )
    (comp (ref "R281")
      (value "104")
      (footprint "eagle-import:R0805")
      (fields (field (name "MPN") "RC0805FR-0710KL"))
      (libsource (lib "eagle-import") (part "SMD-RES-10K-1%-1/8W(0805)"))
    )
    (comp (ref "R282")
      (value "104")
      (footprint "eagle-import:R0805")
      (fields (field (name "MPN") "RC0805FR-0710KL"))
      (libsource (lib "eagle-import") (part "SMD-RES-10K-1%-1/8W(0805)"))
    )
    (comp (ref "R283")
      (value "4701")
      (footprint "eagle-import:R0805")
      (fields (field (name "MPN") "RC0805JR-074K7L"))
      (libsource (lib "eagle-import") (part "SMD-RES-4.7K-5%-1/8W(0805)"))
    )
    (comp (ref "R284")
      (value "1002")
      (footprint "eagle-import:R0805")
      (fields (field (name "MPN") "RC0805FR-0710KL"))
      (libsource (lib "eagle-import") (part "SMD-RES-10K-1%-1/8W(0805)"))
    )
    (comp (ref "R285")
      (value "1002")
      (footprint "eagle-import:R0805")
      (fields (field (name "MPN") "RC0805FR-0710KL"))
      (libsource (lib "eagle-import") (part "SMD-RES-10K-1%-1/8W(0805)"))
    )
    (comp (ref "R286")
      (value "1502")
      (footprint "eagle-import:R0805")
      (fields (field (name "MPN") "RC0805FR-0710KL"))
      (libsource (lib "eagle-import") (part "SMD-RES-10K-1%-1/8W(0805)"))
    )
    (comp (ref "R287")
      (value "104")
      (footprint "eagle-import:R0805")
      (fields (field (name "MPN") "RC0805FR-0710KL"))
      (libsource (lib "eagle-import") (part "SMD-RES-10K-1%-1/8W(0805)"))
    )
    (comp (ref "R288")
      (value "104")
      (footprint "eagle-import:R0805")
      (fields (field (name "MPN") "RC0805FR-0710KL"))
      (libsource (lib "eagle-import") (part "SMD-RES-10K-1%-1/8W(0805)"))
    )
    (comp (ref "R289")
      (value "1502")
      (footprint "eagle-import:R0805")
      (fields (field (name "MPN") "RC0805FR-0710KL"))
      (libsource (lib "eagle-import") (part "SMD-RES-10K-1%-1/8W(0805)"))
    )
    (comp (ref "R290")
      (value "1002")
      (footprint "eagle-import:R0805")
      (fields (field (name "MPN") "RC0805FR-0710KL"))
      (libsource (lib "eagle-import") (part "SMD-RES-10K-1%-1/8W(0805)"))
    )
    (comp (ref "R291")
      (value "2201")
      (footprint "eagle-import:R0805")
      (fields (field (name "MPN") "RC0805JR-072K2L"))
      (libsource (lib "eagle-import") (part "SMD-RES-2.2K-5%-1/8W(0805)"))
    )
    (comp (ref "R292")
      (value "1002")
      (footprint "eagle-import:R0805")
      (fields (field (name "MPN") "RC0805FR-0710KL"))
      (libsource (lib "eagle-import") (part "SMD-RES-10K-1%-1/8W(0805)"))
    )
    (comp (ref "R293")
      (value "4701")
      (footprint "eagle-import:R0805")
      (fields (field (name "MPN") "RC0805JR-074K7L"))
      (libsource (lib "eagle-import") (part "SMD-RES-4.7K-5%-1/8W(0805)"))
    )
    (comp (ref "R294")
      (value "2702")
      (footprint "eagle-import:R0805")
      (fields (field (name "MPN") "RC0805JR-074K7L"))
      (libsource (lib "eagle-import") (part "SMD-RES-4.7K-5%-1/8W(0805)"))
    )
    (comp (ref "R295")
      (value "102")
      (footprint "eagle-import:R0805")
      (fields (field (name "MPN") "RC0805JR-071KL"))
      (libsource (lib "eagle-import") (part "SMD-RES-1K-5%-1/8W(0805)"))
    )
    (comp (ref "R296")
      (value "R_user")
      (footprint "eagle-import:R0805")
      (libsource (lib "eagle-import") (part "R-EU_R0805"))
    )
    (comp (ref "R297")
      (value "100")
      (footprint "eagle-import:R0805")
      (fields (field (name "MPN") "RC0805JR-07220RL"))
      (libsource (lib "eagle-import") (part "SMD-RES-220R-5%-1/8W(0805)"))
    )
    (comp (ref "R298")
      (value "(101)")
      (footprint "eagle-import:R0805")
      (fields (field (name "MPN") "RC0805JR-07100RL"))
      (libsource (lib "eagle-import") (part "SMD-RES-100R-5%-1/8W(0805)"))
    )
    (comp (ref "R299")
      (value "(1000)")
      (footprint "eagle-import:R0805")
      (fields (field (name "MPN") "RC0805JR-07100RL"))
      (libsource (lib "eagle-import") (part "SMD-RES-100R-5%-1/8W(0805)"))
    )
    (comp (ref "R300")
      (value "102")
      (footprint "eagle-import:R0805")
      (fields (field (name "MPN") "RC0805JR-071KL"))
      (libsource (lib "eagle-import") (part "SMD-RES-1K-5%-1/8W(0805)"))
    )
    (comp (ref "R301")
      (value "13")
      (footprint "eagle-import:R1206")
      (fields (field (name "MPN") "RC1206JR-0713RL"))
      (libsource (lib "eagle-import") (part "SMD-RES-13R-5%-1/4W(1206)"))
    )
    (comp (ref "R302")
      (value "13")
      (footprint "eagle-import:R1206")
      (fields (field (name "MPN") "RC1206JR-0713RL"))
      (libsource (lib "eagle-import") (part "SMD-RES-13R-5%-1/4W(1206)"))
    )
    (comp (ref "R303")
      (value "2702")
      (footprint "eagle-import:R0805")
      (fields (field (name "MPN") "RC0805JR-074K7L"))
      (libsource (lib "eagle-import") (part "SMD-RES-4.7K-5%-1/8W(0805)"))
    )
    (comp (ref "R304")
      (value "4701")
      (footprint "eagle-import:R0805")
      (fields (field (name "MPN") "RC0805JR-074K7L"))
      (libsource (lib "eagle-import") (part "SMD-RES-4.7K-5%-1/8W(0805)"))
    )
    (comp (ref "R305")
      (value "100")
      (footprint "eagle-import:R0805")
      (fields (field (name "MPN") "RC0805JR-072K2L"))
      (libsource (lib "eagle-import") (part "SMD-RES-2.2K-5%-1/8W(0805)"))
    )
    (comp (ref "R306")
      (value "(101)")
      (footprint "eagle-import:R0805")
      (fields (field (name "MPN") "RC0805JR-072K2L"))
      (libsource (lib "eagle-import") (part "SMD-RES-2.2K-5%-1/8W(0805)"))
    )
    (comp (ref "R307")
      (value "104")
      (footprint "eagle-import:R0805")
      (fields (field (name "MPN") "RC0805FR-0710KL"))
      (libsource (lib "eagle-import") (part "SMD-RES-10K-1%-1/8W(0805)"))
    )
    (comp (ref "R308")
      (value "104")
      (footprint "eagle-import:R0805")
      (fields (field (name "MPN") "RC0805FR-0710KL"))
      (libsource (lib "eagle-import") (part "SMD-RES-10K-1%-1/8W(0805)"))
    )
    (comp (ref "R309")
      (value "(1002)")
      (footprint "eagle-import:R0805")
      (fields (field (name "MPN") "RC0805FR-0710KL"))
      (libsource (lib "eagle-import") (part "SMD-RES-10K-1%-1/8W(0805)"))
    )
    (comp (ref "R310")
      (value "2702")
      (footprint "eagle-import:R0805")
      (fields (field (name "MPN") "RC0805FR-0710KL"))
      (libsource (lib "eagle-import") (part "SMD-RES-10K-1%-1/8W(0805)"))
    )
    (comp (ref "R311")
      (value "47")
      (footprint "eagle-import:V235_17_1MM")
      (libsource (lib "eagle-import") (part "R-EU_V235/17_1MM"))
    )
    (comp (ref "R312")
      (value "47")
      (footprint "eagle-import:V235_17_1MM")
      (libsource (lib "eagle-import") (part "R-EU_V235/17_1MM"))
    )
    (comp (ref "R313")
      (value "2702")
      (footprint "eagle-import:R0805")
      (fields (field (name "MPN") "RC0805JR-074K7L"))
      (libsource (lib "eagle-import") (part "SMD-RES-4.7K-5%-1/8W(0805)"))
    )
    (comp (ref "R314")
      (value "2201")
      (footprint "eagle-import:R0805")
      (fields (field (name "MPN") "RC0805JR-072K2L"))
      (libsource (lib "eagle-import") (part "SMD-RES-2.2K-5%-1/8W(0805)"))
    )
    (comp (ref "R315")
      (value "(1002)")
      (footprint "eagle-import:R0805")
      (fields (field (name "MPN") "RC0805JR-074K7L"))
      (libsource (lib "eagle-import") (part "SMD-RES-4.7K-5%-1/8W(0805)"))
    )
    (comp (ref "R316")
      (value "1002")
      (footprint "eagle-import:R0805")
      (fields (field (name "MPN") "RC0805FR-0710KL"))
      (libsource (lib "eagle-import") (part "SMD-RES-10K-1%-1/8W(0805)"))
    )
    (comp (ref "R317")
      (value "102")
      (footprint "eagle-import:R0805")
      (fields (field (name "MPN") "RC0805JR-071KL"))
      (libsource (lib "eagle-import") (part "SMD-RES-1K-5%-1/8W(0805)"))
    )
    (comp (ref "R318")
      (value "2702")
      (footprint "eagle-import:R0805")
      (fields (field (name "MPN") "RC0805JR-074K7L"))
      (libsource (lib "eagle-import") (part "SMD-RES-4.7K-5%-1/8W(0805)"))
    )
    (comp (ref "R319")
      (value "102")
      (footprint "eagle-import:R0805")
      (fields (field (name "MPN") "RC0805JR-071KL"))
      (libsource (lib "eagle-import") (part "SMD-RES-1K-5%-1/8W(0805)"))
    )
    (comp (ref "R320")
      (value "102")
      (footprint "eagle-import:R0805")
      (fields (field (name "MPN") "RC0805JR-071KL"))
      (libsource (lib "eagle-import") (part "SMD-RES-1K-5%-1/8W(0805)"))
    )
    (comp (ref "R321")
      (value "13")
      (footprint "eagle-import:R1206")
      (fields (field (name "MPN") "RC1206JR-0713RL"))
      (libsource (lib "eagle-import") (part "SMD-RES-13R-5%-1/4W(1206)"))
    )
    (comp (ref "R322")
      (value "R_user")
      (footprint "eagle-import:R0805")
      (libsource (lib "eagle-import") (part "R-EU_R0805"))
    )
    (comp (ref "SJ7") (value "SJ") (footprint "eagle-import:SJ") (libsource (lib "eagle-import") (part "SJ")))
    (comp (ref "START6")
      (value "TPSB2.0")
      (footprint "eagle-import:B2.0")
      (libsource (lib "eagle-import") (part "TPSB2.0"))
    )
    (comp (ref "TP139")
      (value "TPSB2.0")
      (footprint "eagle-import:B2.0")
      (libsource (lib "eagle-import") (part "TPSB2.0"))
    )
    (comp (ref "TP140")
      (value "TPSB2.0")
      (footprint "eagle-import:B2.0")
      (libsource (lib "eagle-import") (part "TPSB2.0"))
    )
    (comp (ref "TP141")
      (value "TPSB2.0")
      (footprint "eagle-import:B2.0")
      (libsource (lib "eagle-import") (part "TPSB2.0"))
    )
    (comp (ref "TP142")
      (value "TPSB2.0")
      (footprint "eagle-import:B2.0")
      (libsource (lib "eagle-import") (part "TPSB2.0"))
    )
    (comp (ref "TP143")
      (value "TPSB2.0")
      (footprint "eagle-import:B2.0")
      (libsource (lib "eagle-import") (part "TPSB2.0"))
    )
    (comp (ref "TP144")
      (value "TPSB2.0")
      (footprint "eagle-import:B2.0")
      (libsource (lib "eagle-import") (part "TPSB2.0"))
    )
    (comp (ref "TP145")
      (value "TPSB2.0")
      (footprint "eagle-import:B2.0")
      (libsource (lib "eagle-import") (part "TPSB2.0"))
    )
    (comp (ref "TP146")
      (value "TPSB2.0")
      (footprint "eagle-import:B2.0")
      (libsource (lib "eagle-import") (part "TPSB2.0"))
    )
    (comp (ref "TP147")
      (value "TPSB2.0")
      (footprint "eagle-import:B2.0")
      (libsource (lib "eagle-import") (part "TPSB2.0"))
    )
    (comp (ref "TP148")
      (value "TPSB2.0")
      (footprint "eagle-import:B2.0")
      (libsource (lib "eagle-import") (part "TPSB2.0"))
    )
    (comp (ref "TP149")
      (value "TPSB2.0")
      (footprint "eagle-import:B2.0")
      (libsource (lib "eagle-import") (part "TPSB2.0"))
    )
    (comp (ref "TP150")
      (value "TPSB2.0")
      (footprint "eagle-import:B2.0")
      (libsource (lib "eagle-import") (part "TPSB2.0"))
    )
    (comp (ref "TP151")
      (value "TPSB2.0")
      (footprint "eagle-import:B2.0")
      (libsource (lib "eagle-import") (part "TPSB2.0"))
    )
    (comp (ref "TP152")
      (value "TPSB2.0")
      (footprint "eagle-import:B2.0")
      (libsource (lib "eagle-import") (part "TPSB2.0"))
    )
    (comp (ref "TP153")
      (value "TPSB2.0")
      (footprint "eagle-import:B2.0")
      (libsource (lib "eagle-import") (part "TPSB2.0"))
    )
    (comp (ref "TP154")
      (value "TPSB2.0")
      (footprint "eagle-import:B2.0")
      (libsource (lib "eagle-import") (part "TPSB2.0"))
    )
    (comp (ref "TP155")
      (value "TPSB2.0")
      (footprint "eagle-import:B2.0")
      (libsource (lib "eagle-import") (part "TPSB2.0"))
    )
    (comp (ref "TP156")
      (value "TPSB2.0")
      (footprint "eagle-import:B2.0")
      (libsource (lib "eagle-import") (part "TPSB2.0"))
    )
    (comp (ref "TP157")
      (value "TPSB1,27")
      (footprint "eagle-import:B1,27")
      (libsource (lib "eagle-import") (part "TPSB1,27"))
    )
    (comp (ref "TP158")
      (value "TPSB2.0")
      (footprint "eagle-import:B2.0")
      (libsource (lib "eagle-import") (part "TPSB2.0"))
    )
    (comp (ref "TP159")
      (value "TPSB2.0")
      (footprint "eagle-import:B2.0")
      (libsource (lib "eagle-import") (part "TPSB2.0"))
    )
    (comp (ref "TP160")
      (value "TPSB2.0")
      (footprint "eagle-import:B2.0")
      (libsource (lib "eagle-import") (part "TPSB2.0"))
    )
    (comp (ref "TP161")
      (value "TPSB2.0")
      (footprint "eagle-import:B2.0")
      (libsource (lib "eagle-import") (part "TPSB2.0"))
    )
    (comp (ref "X19")
      (value "CON_BMWV2")
      (footprint "eagle-import:24-PIN_V2")
      (libsource (lib "eagle-import") (part "CON_BMWV2"))
    )
    (comp (ref "X20")
      (value "22-23-2051")
      (footprint "eagle-import:22-23-2051")
      (fields (field (name "MF") "MOLEX"))
      (libsource (lib "eagle-import") (part "22-23-2051"))
    )
    (comp (ref "X21")
      (value "22-23-2021")
      (footprint "eagle-import:22-23-2021")
      (fields (field (name "MF") "MOLEX"))
      (libsource (lib "eagle-import") (part "22-23-2021"))
    )
    (comp (ref "1")
      (value "2081-1132")
      (footprint "eagle-import:12-PIN")
      (libsource (lib "eagle-import") (part "2081-1132"))
    )
    (comp (ref "2")
      (value "2081-1132")
      (footprint "eagle-import:12-PIN")
      (libsource (lib "eagle-import") (part "2081-1132"))
    )
    (comp (ref "6V")
      (value "TPSB2.0")
      (footprint "eagle-import:B2.0")
      (libsource (lib "eagle-import") (part "TPSB2.0"))
    )
    (comp (ref "10V")
      (value "TPSB2.0")
      (footprint "eagle-import:B2.0")
      (libsource (lib "eagle-import") (part "TPSB2.0"))
    )
    (comp (ref "C1")
      (value "4.7u")
      (footprint "eagle-import:C0805")
      (fields (field (name "MPN") "CC0805KKX5R8BB475"))
      (libsource (lib "eagle-import") (part "CERAMIC-4.7UF-25V-10%-X5R(0805)"))
    )
    (comp (ref "C2")
      (value "100nF")
      (footprint "eagle-import:C0805")
      (fields (field (name "MPN") "CC0805KRX7R9BB104"))
      (libsource (lib "eagle-import") (part "CERAMIC-100NF-50V-10%-X7R(0805)"))
    )
    (comp (ref "C3")
      (value "100nF,")
      (footprint "eagle-import:C0805")
      (fields (field (name "MPN") "CC0805KRX7R9BB104"))
      (libsource (lib "eagle-import") (part "CERAMIC-100NF-50V-10%-X7R(0805)"))
    )
    (comp (ref "C4")
      (value "100nF,")
      (footprint "eagle-import:C0805")
      (fields (field (name "MPN") "CC0805KRX7R9BB104"))
      (libsource (lib "eagle-import") (part "CERAMIC-100NF-50V-10%-X7R(0805)"))
    )
    (comp (ref "C5")
      (value "100nF.")
      (footprint "eagle-import:C0805")
      (fields (field (name "MPN") "CC0805KRX7R9BB104"))
      (libsource (lib "eagle-import") (part "CERAMIC-100NF-50V-10%-X7R(0805)"))
    )
    (comp (ref "C6")
      (value "100nF.")
      (footprint "eagle-import:C0805")
      (fields (field (name "MPN") "CC0805KRX7R9BB104"))
      (libsource (lib "eagle-import") (part "CERAMIC-100NF-50V-10%-X7R(0805)"))
    )
    (comp (ref "C7")
      (value "100u")
      (footprint "eagle-import:C1206")
      (fields (field (name "MPN") "GRM31CR60J107ME39L"))
      (libsource (lib "eagle-import") (part "CERAMIC-100UF-6.3V-20%-X5R(1206)"))
    )
    (comp (ref "C8")
      (value "100u")
      (footprint "eagle-import:C1206")
      (fields (field (name "MPN") "GRM31CR60J107ME39L"))
      (libsource (lib "eagle-import") (part "CERAMIC-100UF-6.3V-20%-X5R(1206)"))
    )
    (comp (ref "C9")
      (value "2.2nF")
      (footprint "eagle-import:C0805")
      (fields (field (name "MPN") "CC0805KRX7R9BB104"))
      (libsource (lib "eagle-import") (part "CERAMIC-100NF-50V-10%-X7R(0805)"))
    )
    (comp (ref "C10")
      (value "100nF")
      (footprint "eagle-import:C0805")
      (fields (field (name "MPN") "CC0805KRX7R9BB104"))
      (libsource (lib "eagle-import") (part "CERAMIC-100NF-50V-10%-X7R(0805)"))
    )
    (comp (ref "D1")
      (value "SM6T")
      (footprint "eagle-import:DO214AA")
      (libsource (lib "eagle-import") (part "SM6T"))
    )
    (comp (ref "D2")
      (value "1N4007,")
      (footprint "eagle-import:DO-214AC")
      (fields (field (name "MPN") "1N4007"))
      (libsource (lib "eagle-import") (part "DIODE-GEN-PURPOSE-1KV-1A(DO-214AC)"))
    )
    (comp (ref "D3")
      (value "1N4007,")
      (footprint "eagle-import:DO-214AC")
      (fields (field (name "MPN") "1N4007"))
      (libsource (lib "eagle-import") (part "DIODE-GEN-PURPOSE-1KV-1A(DO-214AC)"))
    )
    (comp (ref "D4")
      (value "SM6TDO214AA_BI")
      (footprint "eagle-import:DO214AA_BI")
      (libsource (lib "eagle-import") (part "SM6TDO214AA_BI"))
    )
    (comp (ref "D5")
      (value "1N4007.")
      (footprint "eagle-import:DO-214AC")
      (fields (field (name "MPN") "1N4007"))
      (libsource (lib "eagle-import") (part "DIODE-GEN-PURPOSE-1KV-1A(DO-214AC)"))
    )
    (comp (ref "D6")
      (value "1N4007.")
      (footprint "eagle-import:DO-214AC")
      (fields (field (name "MPN") "1N4007"))
      (libsource (lib "eagle-import") (part "DIODE-GEN-PURPOSE-1KV-1A(DO-214AC)"))
    )
    (comp (ref "D7")
      (value "1N5817")
      (footprint "eagle-import:DO-214AC_SLIM")
      (libsource (lib "eagle-import") (part "DIODE-GEN-PURPOSE-1KV-1A(DO-214AC)DO-214AC/1206"))
    )
    (comp (ref "D8")
      (value "1N5817.")
      (footprint "eagle-import:DO-214AC_SLIM")
      (libsource (lib "eagle-import") (part "DIODE-GEN-PURPOSE-1KV-1A(DO-214AC)DO-214AC/1206"))
    )
    (comp (ref "D9")
      (value "1N5817.")
      (footprint "eagle-import:DO-214AC_SLIM")
      (libsource (lib "eagle-import") (part "DIODE-GEN-PURPOSE-1KV-1A(DO-214AC)DO-214AC/1206"))
    )
    (comp (ref "D10")
      (value "1N5817")
      (footprint "eagle-import:DO-214AC_SLIM")
      (libsource (lib "eagle-import") (part "DIODE-GEN-PURPOSE-1KV-1A(DO-214AC)DO-214AC/1206"))
    )
    (comp (ref "D11")
      (value "1N4007")
      (footprint "eagle-import:DO-214AC")
      (libsource (lib "eagle-import") (part "DIODE-GEN-PURPOSE-1KV-1A(DO-214AC)"))
    )
    (comp (ref "D12")
      (value "1N4007")
      (footprint "eagle-import:DO-214AC")
      (libsource (lib "eagle-import") (part "DIODE-GEN-PURPOSE-1KV-1A(DO-214AC)"))
    )
    (comp (ref "FID1")
      (value "FIDUCIAL")
      (footprint "eagle-import:FIDUCIAL_1MM")
      (libsource (lib "eagle-import") (part "FIDUCIAL"))
    )
    (comp (ref "FID2")
      (value "FIDUCIAL")
      (footprint "eagle-import:FIDUCIAL_1MM")
      (libsource (lib "eagle-import") (part "FIDUCIAL"))
    )
    (comp (ref "FID3")
      (value "FIDUCIAL")
      (footprint "eagle-import:FIDUCIAL_1MM")
      (libsource (lib "eagle-import") (part "FIDUCIAL"))
    )
    (comp (ref "FID4")
      (value "FIDUCIAL")
      (footprint "eagle-import:FIDUCIAL_1MM")
      (libsource (lib "eagle-import") (part "FIDUCIAL"))
    )
    (comp (ref "FID49")
      (value "FIDUCIAL")
      (footprint "eagle-import:FIDUCIAL_1MM")
      (libsource (lib "eagle-import") (part "FIDUCIAL"))
    )
    (comp (ref "FID50")
      (value "FIDUCIAL")
      (footprint "eagle-import:FIDUCIAL_1MM")
      (libsource (lib "eagle-import") (part "FIDUCIAL"))
    )
    (comp (ref "FID51")
      (value "FIDUCIAL")
      (footprint "eagle-import:FIDUCIAL_1MM")
      (libsource (lib "eagle-import") (part "FIDUCIAL"))
    )
    (comp (ref "FID52")
      (value "FIDUCIAL")
      (footprint "eagle-import:FIDUCIAL_1MM")
      (libsource (lib "eagle-import") (part "FIDUCIAL"))
    )
    (comp (ref "IC1")
      (value "LM2904")
      (footprint "eagle-import:SO08")
      (libsource (lib "eagle-import") (part "LM358D"))
    )
    (comp (ref "IC2")
      (value "78L06")
      (footprint "eagle-import:SOT89_ROUND")
      (libsource (lib "eagle-import") (part "78LXXSOT89_ROUND"))
    )
    (comp (ref "IC3")
      (value "6V pos")
      (footprint "eagle-import:78LXX")
      (libsource (lib "eagle-import") (part "v-reg_78LXX"))
    )
    (comp (ref "IC4")
      (value "78L10")
      (footprint "eagle-import:SOT89_ROUND")
      (libsource (lib "eagle-import") (part "78LXXSOT89_ROUND"))
    )
    (comp (ref "IC5")
      (value "4028")
      (footprint "eagle-import:SO16")
      (libsource (lib "eagle-import") (part "4028D"))
    )
    (comp (ref "IC6")
      (value "NUP4304SOT457_R")
      (footprint "eagle-import:SOT457R_PHILIPS")
      (libsource (lib "eagle-import") (part "NUP4304SOT457_R"))
    )
    (comp (ref "IC7")
      (value "ULN2004")
      (footprint "eagle-import:SO16")
      (libsource (lib "eagle-import") (part "ULN2004AD"))
    )
    (comp (ref "IC8")
      (value "LM339")
      (footprint "eagle-import:SO14")
      (libsource (lib "eagle-import") (part "LM339D"))
    )
    (comp (ref "IC9")
      (value "317TO202H_NOHOLE")
      (footprint "eagle-import:TO220H_NOHOLE")
      (libsource (lib "eagle-import") (part "317TO202H_NOHOLE"))
    )
    (comp (ref "IC10")
      (value "555")
      (footprint "eagle-import:SO08")
      (libsource (lib "eagle-import") (part "555DNE"))
    )
    (comp (ref "IC11")
      (value "4538")
      (footprint "eagle-import:SO16")
      (libsource (lib "eagle-import") (part "4538D"))
    )
    (comp (ref "JP1")
      (value "JP2EJP2_SMALLPADS")
      (footprint "eagle-import:JP2_SMALLPADS")
      (libsource (lib "eagle-import") (part "JP2EJP2_SMALLPADS"))
    )
    (comp (ref "JP2")
      (value "JP2EJP2_SMALLPADS")
      (footprint "eagle-import:JP2_SMALLPADS")
      (libsource (lib "eagle-import") (part "JP2EJP2_SMALLPADS"))
    )
    (comp (ref "JP3")
      (value "JP2EJP2_SMALLPADS")
      (footprint "eagle-import:JP2_SMALLPADS")
      (libsource (lib "eagle-import") (part "JP2EJP2_SMALLPADS"))
    )
    (comp (ref "JP4")
      (value "JP2EJP2_SMALLPADS")
      (footprint "eagle-import:JP2_SMALLPADS")
      (libsource (lib "eagle-import") (part "JP2EJP2_SMALLPADS"))
    )
    (comp (ref "JP5")
      (value "JP2E_ORIG")
      (footprint "eagle-import:JP2_ORIG_SMALLPADS")
      (libsource (lib "eagle-import") (part "JP2E_ORIG"))
    )
    (comp (ref "LED1")
      (value "LEDLD260")
      (footprint "eagle-import:LD260")
      (libsource (lib "eagle-import") (part "LEDLD260"))
    )
    (comp (ref "LED2")
      (value "LEDLD260")
      (footprint "eagle-import:LD260")
      (libsource (lib "eagle-import") (part "LEDLD260"))
    )
    (comp (ref "LED3")
      (value "LEDLD260")
      (footprint "eagle-import:LD260")
      (libsource (lib "eagle-import") (part "LEDLD260"))
    )
    (comp (ref "LED4")
      (value "LEDLD260")
      (footprint "eagle-import:LD260")
      (libsource (lib "eagle-import") (part "LEDLD260"))
    )
    (comp (ref "LED5")
      (value "LEDLD260")
      (footprint "eagle-import:LD260")
      (libsource (lib "eagle-import") (part "LEDLD260"))
    )
    (comp (ref "LED6")
      (value "LEDLD260")
      (footprint "eagle-import:LD260")
      (libsource (lib "eagle-import") (part "LEDLD260"))
    )
    (comp (ref "Q1")
      (value "BA.")
      (footprint "eagle-import:SOT89")
      (libsource (lib "eagle-import") (part "PNP-TRANSISTOR_SOT89"))
    )
    (comp (ref "Q2")
      (value "BA.")
      (footprint "eagle-import:SOT89")
      (libsource (lib "eagle-import") (part "PNP-TRANSISTOR_SOT89"))
    )
    (comp (ref "Q3")
      (value "MY")
      (footprint "eagle-import:SOT89")
      (libsource (lib "eagle-import") (part "NPN-TRANSISTOR_SOT89"))
    )
    (comp (ref "Q4")
      (value "BA")
      (footprint "eagle-import:SOT89")
      (libsource (lib "eagle-import") (part "PNP-TRANSISTOR_SOT89"))
    )
    (comp (ref "Q5")
      (value "BA")
      (footprint "eagle-import:SOT89")
      (libsource (lib "eagle-import") (part "PNP-TRANSISTOR_SOT89"))
    )
    (comp (ref "Q6")
      (value "J1")
      (footprint "eagle-import:SOT-23")
      (fields (field (name "MPN") "BSS138W-7-F"))
      (libsource (lib "eagle-import") (part "SMD-MOSFET-N-CH-50V-200MA-BSS138W-7-F(SOT-23)"))
    )
    (comp (ref "Q7")
      (value "J1")
      (footprint "eagle-import:SOT-23")
      (fields (field (name "MPN") "BSS138W-7-F"))
      (libsource (lib "eagle-import") (part "SMD-MOSFET-N-CH-50V-200MA-BSS138W-7-F(SOT-23)"))
    )
    (comp (ref "R1")
      (value "102")
      (footprint "eagle-import:R0805")
      (fields (field (name "MPN") "RC0805JR-071KL"))
      (libsource (lib "eagle-import") (part "SMD-RES-1K-5%-1/8W(0805)"))
    )
    (comp (ref "R2")
      (value "13")
      (footprint "eagle-import:R1206")
      (fields (field (name "MPN") "RC1206JR-0713RL"))
      (libsource (lib "eagle-import") (part "SMD-RES-13R-5%-1/4W(1206)"))
    )
    (comp (ref "R3")
      (value "R_user")
      (footprint "eagle-import:R0805")
      (libsource (lib "eagle-import") (part "R-EU_R0805"))
    )
    (comp (ref "R4")
      (value "R_user")
      (footprint "eagle-import:R0805")
      (libsource (lib "eagle-import") (part "R-EU_R0805"))
    )
    (comp (ref "R5")
      (value "4701")
      (footprint "eagle-import:R0805")
      (fields (field (name "MPN") "RC0805JR-074K7L"))
      (libsource (lib "eagle-import") (part "SMD-RES-4.7K-5%-1/8W(0805)"))
    )
    (comp (ref "R6")
      (value "13")
      (footprint "eagle-import:R1206")
      (fields (field (name "MPN") "RC1206JR-0713RL"))
      (libsource (lib "eagle-import") (part "SMD-RES-13R-5%-1/4W(1206)"))
    )
    (comp (ref "R7")
      (value "1002")
      (footprint "eagle-import:R0805")
      (fields (field (name "MPN") "RC0805FR-0710KL"))
      (libsource (lib "eagle-import") (part "SMD-RES-10K-1%-1/8W(0805)"))
    )
    (comp (ref "R8")
      (value "1002")
      (footprint "eagle-import:R0805")
      (fields (field (name "MPN") "RC0805FR-0710KL"))
      (libsource (lib "eagle-import") (part "SMD-RES-10K-1%-1/8W(0805)"))
    )
    (comp (ref "R9")
      (value "104")
      (footprint "eagle-import:R0805")
      (fields (field (name "MPN") "RC0805FR-0710KL"))
      (libsource (lib "eagle-import") (part "SMD-RES-10K-1%-1/8W(0805)"))
    )
    (comp (ref "R10")
      (value "104")
      (footprint "eagle-import:R0805")
      (fields (field (name "MPN") "RC0805FR-0710KL"))
      (libsource (lib "eagle-import") (part "SMD-RES-10K-1%-1/8W(0805)"))
    )
    (comp (ref "R11")
      (value "104")
      (footprint "eagle-import:R0805")
      (fields (field (name "MPN") "RC0805FR-0710KL"))
      (libsource (lib "eagle-import") (part "SMD-RES-10K-1%-1/8W(0805)"))
    )
    (comp (ref "R12")
      (value "102")
      (footprint "eagle-import:R0805")
      (fields (field (name "MPN") "RC0805JR-071KL"))
      (libsource (lib "eagle-import") (part "SMD-RES-1K-5%-1/8W(0805)"))
    )
    (comp (ref "R13")
      (value "102")
      (footprint "eagle-import:R0805")
      (fields (field (name "MPN") "RC0805JR-071KL"))
      (libsource (lib "eagle-import") (part "SMD-RES-1K-5%-1/8W(0805)"))
    )
    (comp (ref "R14")
      (value "102")
      (footprint "eagle-import:R0805")
      (fields (field (name "MPN") "RC0805JR-071KL"))
      (libsource (lib "eagle-import") (part "SMD-RES-1K-5%-1/8W(0805)"))
    )
    (comp (ref "R15")
      (value "100")
      (footprint "eagle-import:R0805")
      (fields (field (name "MPN") "RC0805JR-07220RL"))
      (libsource (lib "eagle-import") (part "SMD-RES-220R-5%-1/8W(0805)"))
    )
    (comp (ref "R16")
      (value "4701")
      (footprint "eagle-import:R0805")
      (fields (field (name "MPN") "RC0805JR-074K7L"))
      (libsource (lib "eagle-import") (part "SMD-RES-4.7K-5%-1/8W(0805)"))
    )
    (comp (ref "R17")
      (value "2702")
      (footprint "eagle-import:R0805")
      (fields (field (name "MPN") "RC0805JR-074K7L"))
      (libsource (lib "eagle-import") (part "SMD-RES-4.7K-5%-1/8W(0805)"))
    )
    (comp (ref "R18")
      (value "13")
      (footprint "eagle-import:R1206")
      (fields (field (name "MPN") "RC1206JR-0713RL"))
      (libsource (lib "eagle-import") (part "SMD-RES-13R-5%-1/4W(1206)"))
    )
    (comp (ref "R19")
      (value "2201")
      (footprint "eagle-import:R0805")
      (fields (field (name "MPN") "RC0805JR-072K2L"))
      (libsource (lib "eagle-import") (part "SMD-RES-2.2K-5%-1/8W(0805)"))
    )
    (comp (ref "R20")
      (value "1002")
      (footprint "eagle-import:R0805")
      (fields (field (name "MPN") "RC0805FR-0710KL"))
      (libsource (lib "eagle-import") (part "SMD-RES-10K-1%-1/8W(0805)"))
    )
    (comp (ref "R21")
      (value "1502")
      (footprint "eagle-import:R0805")
      (fields (field (name "MPN") "RC0805FR-0710KL"))
      (libsource (lib "eagle-import") (part "SMD-RES-10K-1%-1/8W(0805)"))
    )
    (comp (ref "R22")
      (value "2702")
      (footprint "eagle-import:R0805")
      (fields (field (name "MPN") "RC0805JR-074K7L"))
      (libsource (lib "eagle-import") (part "SMD-RES-4.7K-5%-1/8W(0805)"))
    )
    (comp (ref "R23")
      (value "2702")
      (footprint "eagle-import:R0805")
      (fields (field (name "MPN") "RC0805JR-074K7L"))
      (libsource (lib "eagle-import") (part "SMD-RES-4.7K-5%-1/8W(0805)"))
    )
    (comp (ref "R24")
      (value "1002")
      (footprint "eagle-import:R0805")
      (fields (field (name "MPN") "RC0805FR-0710KL"))
      (libsource (lib "eagle-import") (part "SMD-RES-10K-1%-1/8W(0805)"))
    )
    (comp (ref "R25")
      (value "104")
      (footprint "eagle-import:R0805")
      (fields (field (name "MPN") "RC0805FR-0710KL"))
      (libsource (lib "eagle-import") (part "SMD-RES-10K-1%-1/8W(0805)"))
    )
    (comp (ref "R26")
      (value "4701")
      (footprint "eagle-import:R0805")
      (fields (field (name "MPN") "RC0805JR-074K7L"))
      (libsource (lib "eagle-import") (part "SMD-RES-4.7K-5%-1/8W(0805)"))
    )
    (comp (ref "R27")
      (value "47")
      (footprint "eagle-import:V235_17_1MM")
      (libsource (lib "eagle-import") (part "R-EU_V235/17_1MM"))
    )
    (comp (ref "R28")
      (value "102")
      (footprint "eagle-import:R0805")
      (fields (field (name "MPN") "RC0805JR-071KL"))
      (libsource (lib "eagle-import") (part "SMD-RES-1K-5%-1/8W(0805)"))
    )
    (comp (ref "R29")
      (value "47")
      (footprint "eagle-import:V235_17_1MM")
      (libsource (lib "eagle-import") (part "R-EU_V235/17_1MM"))
    )
    (comp (ref "R30")
      (value "104")
      (footprint "eagle-import:R0805")
      (fields (field (name "MPN") "RC0805FR-0710KL"))
      (libsource (lib "eagle-import") (part "SMD-RES-10K-1%-1/8W(0805)"))
    )
    (comp (ref "R31")
      (value "1502")
      (footprint "eagle-import:R0805")
      (fields (field (name "MPN") "RC0805FR-0710KL"))
      (libsource (lib "eagle-import") (part "SMD-RES-10K-1%-1/8W(0805)"))
    )
    (comp (ref "R32")
      (value "1002")
      (footprint "eagle-import:R0805")
      (fields (field (name "MPN") "RC0805FR-0710KL"))
      (libsource (lib "eagle-import") (part "SMD-RES-10K-1%-1/8W(0805)"))
    )
    (comp (ref "R33")
      (value "2201")
      (footprint "eagle-import:R0805")
      (fields (field (name "MPN") "RC0805JR-072K2L"))
      (libsource (lib "eagle-import") (part "SMD-RES-2.2K-5%-1/8W(0805)"))
    )
    (comp (ref "R34")
      (value "13")
      (footprint "eagle-import:R1206")
      (fields (field (name "MPN") "RC1206JR-0713RL"))
      (libsource (lib "eagle-import") (part "SMD-RES-13R-5%-1/4W(1206)"))
    )
    (comp (ref "R35")
      (value "104")
      (footprint "eagle-import:R0805")
      (fields (field (name "MPN") "RC0805FR-0710KL"))
      (libsource (lib "eagle-import") (part "SMD-RES-10K-1%-1/8W(0805)"))
    )
    (comp (ref "R36")
      (value "47")
      (footprint "eagle-import:V235_17_1MM")
      (libsource (lib "eagle-import") (part "R-EU_V235/17_1MM"))
    )
    (comp (ref "R37")
      (value "47")
      (footprint "eagle-import:V235_17_1MM")
      (libsource (lib "eagle-import") (part "R-EU_V235/17_1MM"))
    )
    (comp (ref "R38")
      (value "100")
      (footprint "eagle-import:R0805")
      (fields (field (name "MPN") "RC0805JR-072K2L"))
      (libsource (lib "eagle-import") (part "SMD-RES-2.2K-5%-1/8W(0805)"))
    )
    (comp (ref "R39")
      (value "(101)")
      (footprint "eagle-import:R0805")
      (fields (field (name "MPN") "RC0805JR-072K2L"))
      (libsource (lib "eagle-import") (part "SMD-RES-2.2K-5%-1/8W(0805)"))
    )
    (comp (ref "R40")
      (value "2702")
      (footprint "eagle-import:R0805")
      (fields (field (name "MPN") "RC0805FR-0710KL"))
      (libsource (lib "eagle-import") (part "SMD-RES-10K-1%-1/8W(0805)"))
    )
    (comp (ref "R41")
      (value "104")
      (footprint "eagle-import:R0805")
      (fields (field (name "MPN") "RC0805FR-0710KL"))
      (libsource (lib "eagle-import") (part "SMD-RES-10K-1%-1/8W(0805)"))
    )
    (comp (ref "R42")
      (value "(1000)")
      (footprint "eagle-import:R0805")
      (fields (field (name "MPN") "RC0805JR-07100RL"))
      (libsource (lib "eagle-import") (part "SMD-RES-100R-5%-1/8W(0805)"))
    )
    (comp (ref "R43")
      (value "(101)")
      (footprint "eagle-import:R0805")
      (fields (field (name "MPN") "RC0805JR-07100RL"))
      (libsource (lib "eagle-import") (part "SMD-RES-100R-5%-1/8W(0805)"))
    )
    (comp (ref "R44")
      (value "(1002)")
      (footprint "eagle-import:R0805")
      (fields (field (name "MPN") "RC0805FR-0710KL"))
      (libsource (lib "eagle-import") (part "SMD-RES-10K-1%-1/8W(0805)"))
    )
    (comp (ref "R45")
      (value "2702")
      (footprint "eagle-import:R0805")
      (fields (field (name "MPN") "RC0805JR-074K7L"))
      (libsource (lib "eagle-import") (part "SMD-RES-4.7K-5%-1/8W(0805)"))
    )
    (comp (ref "R46")
      (value "(1002)")
      (footprint "eagle-import:R0805")
      (fields (field (name "MPN") "RC0805JR-074K7L"))
      (libsource (lib "eagle-import") (part "SMD-RES-4.7K-5%-1/8W(0805)"))
    )
    (comp (ref "SJ1") (value "SJ") (footprint "eagle-import:SJ") (libsource (lib "eagle-import") (part "SJ")))
    (comp (ref "START")
      (value "TPSB2.0")
      (footprint "eagle-import:B2.0")
      (libsource (lib "eagle-import") (part "TPSB2.0"))
    )
    (comp (ref "TP1")
      (value "TPSB2.0")
      (footprint "eagle-import:B2.0")
      (libsource (lib "eagle-import") (part "TPSB2.0"))
    )
    (comp (ref "TP2")
      (value "TPSB2.0")
      (footprint "eagle-import:B2.0")
      (libsource (lib "eagle-import") (part "TPSB2.0"))
    )
    (comp (ref "TP3")
      (value "TPSB2.0")
      (footprint "eagle-import:B2.0")
      (libsource (lib "eagle-import") (part "TPSB2.0"))
    )
    (comp (ref "TP4")
      (value "TPSB2.0")
      (footprint "eagle-import:B2.0")
      (libsource (lib "eagle-import") (part "TPSB2.0"))
    )
    (comp (ref "TP5")
      (value "TPSB2.0")
      (footprint "eagle-import:B2.0")
      (libsource (lib "eagle-import") (part "TPSB2.0"))
    )
    (comp (ref "TP6")
      (value "TPSB2.0")
      (footprint "eagle-import:B2.0")
      (libsource (lib "eagle-import") (part "TPSB2.0"))
    )
    (comp (ref "TP7")
      (value "TPSB2.0")
      (footprint "eagle-import:B2.0")
      (libsource (lib "eagle-import") (part "TPSB2.0"))
    )
    (comp (ref "TP8")
      (value "TPSB2.0")
      (footprint "eagle-import:B2.0")
      (libsource (lib "eagle-import") (part "TPSB2.0"))
    )
    (comp (ref "TP9")
      (value "TPSB2.0")
      (footprint "eagle-import:B2.0")
      (libsource (lib "eagle-import") (part "TPSB2.0"))
    )
    (comp (ref "TP10")
      (value "TPSB2.0")
      (footprint "eagle-import:B2.0")
      (libsource (lib "eagle-import") (part "TPSB2.0"))
    )
    (comp (ref "TP11")
      (value "TPSB2.0")
      (footprint "eagle-import:B2.0")
      (libsource (lib "eagle-import") (part "TPSB2.0"))
    )
    (comp (ref "TP12")
      (value "TPSB2.0")
      (footprint "eagle-import:B2.0")
      (libsource (lib "eagle-import") (part "TPSB2.0"))
    )
    (comp (ref "TP13")
      (value "TPSB2.0")
      (footprint "eagle-import:B2.0")
      (libsource (lib "eagle-import") (part "TPSB2.0"))
    )
    (comp (ref "TP16")
      (value "TPSB2.0")
      (footprint "eagle-import:B2.0")
      (libsource (lib "eagle-import") (part "TPSB2.0"))
    )
    (comp (ref "TP17")
      (value "TPSB2.0")
      (footprint "eagle-import:B2.0")
      (libsource (lib "eagle-import") (part "TPSB2.0"))
    )
    (comp (ref "TP18")
      (value "TPSB2.0")
      (footprint "eagle-import:B2.0")
      (libsource (lib "eagle-import") (part "TPSB2.0"))
    )
    (comp (ref "TP19")
      (value "TPSB2.0")
      (footprint "eagle-import:B2.0")
      (libsource (lib "eagle-import") (part "TPSB2.0"))
    )
    (comp (ref "TP21")
      (value "TPSB2.0")
      (footprint "eagle-import:B2.0")
      (libsource (lib "eagle-import") (part "TPSB2.0"))
    )
    (comp (ref "TP22")
      (value "TPSB2.0")
      (footprint "eagle-import:B2.0")
      (libsource (lib "eagle-import") (part "TPSB2.0"))
    )
    (comp (ref "TP23")
      (value "TPSB2.0")
      (footprint "eagle-import:B2.0")
      (libsource (lib "eagle-import") (part "TPSB2.0"))
    )
    (comp (ref "TP24")
      (value "TPSB1,27")
      (footprint "eagle-import:B1,27")
      (libsource (lib "eagle-import") (part "TPSB1,27"))
    )
    (comp (ref "TP25")
      (value "TPSB2.0")
      (footprint "eagle-import:B2.0")
      (libsource (lib "eagle-import") (part "TPSB2.0"))
    )
    (comp (ref "TP26")
      (value "TPSB2.0")
      (footprint "eagle-import:B2.0")
      (libsource (lib "eagle-import") (part "TPSB2.0"))
    )
    (comp (ref "X1")
      (value "CON_BMWV2")
      (footprint "eagle-import:24-PIN_V2")
      (libsource (lib "eagle-import") (part "CON_BMWV2"))
    )
    (comp (ref "X2")
      (value "22-23-2021")
      (footprint "eagle-import:22-23-2021")
      (fields (field (name "MF") "MOLEX"))
      (libsource (lib "eagle-import") (part "22-23-2021"))
    )
    (comp (ref "X3")
      (value "22-23-2051")
      (footprint "eagle-import:22-23-2051")
      (fields (field (name "MF") "MOLEX"))
      (libsource (lib "eagle-import") (part "22-23-2051"))
    )
    (comp (ref "3")
      (value "2081-1132")
      (footprint "eagle-import:12-PIN")
      (libsource (lib "eagle-import") (part "2081-1132"))
    )
    (comp (ref "4")
      (value "2081-1132")
      (footprint "eagle-import:12-PIN")
      (libsource (lib "eagle-import") (part "2081-1132"))
    )
    (comp (ref "6V1")
      (value "TPSB2.0")
      (footprint "eagle-import:B2.0")
      (libsource (lib "eagle-import") (part "TPSB2.0"))
    )
    (comp (ref "10V1")
      (value "TPSB2.0")
      (footprint "eagle-import:B2.0")
      (libsource (lib "eagle-import") (part "TPSB2.0"))
    )
    (comp (ref "C11")
      (value "100u")
      (footprint "eagle-import:C1206")
      (fields (field (name "MPN") "GRM31CR60J107ME39L"))
      (libsource (lib "eagle-import") (part "CERAMIC-100UF-6.3V-20%-X5R(1206)"))
    )
    (comp (ref "C12")
      (value "100u")
      (footprint "eagle-import:C1206")
      (fields (field (name "MPN") "GRM31CR60J107ME39L"))
      (libsource (lib "eagle-import") (part "CERAMIC-100UF-6.3V-20%-X5R(1206)"))
    )
    (comp (ref "C13")
      (value "100nF,")
      (footprint "eagle-import:C0805")
      (fields (field (name "MPN") "CC0805KRX7R9BB104"))
      (libsource (lib "eagle-import") (part "CERAMIC-100NF-50V-10%-X7R(0805)"))
    )
    (comp (ref "C14")
      (value "4.7u")
      (footprint "eagle-import:C0805")
      (fields (field (name "MPN") "CC0805KKX5R8BB475"))
      (libsource (lib "eagle-import") (part "CERAMIC-4.7UF-25V-10%-X5R(0805)"))
    )
    (comp (ref "C15")
      (value "100nF.")
      (footprint "eagle-import:C0805")
      (fields (field (name "MPN") "CC0805KRX7R9BB104"))
      (libsource (lib "eagle-import") (part "CERAMIC-100NF-50V-10%-X7R(0805)"))
    )
    (comp (ref "C16")
      (value "100nF.")
      (footprint "eagle-import:C0805")
      (fields (field (name "MPN") "CC0805KRX7R9BB104"))
      (libsource (lib "eagle-import") (part "CERAMIC-100NF-50V-10%-X7R(0805)"))
    )
    (comp (ref "C17")
      (value "2.2nF")
      (footprint "eagle-import:C0805")
      (fields (field (name "MPN") "CC0805KRX7R9BB104"))
      (libsource (lib "eagle-import") (part "CERAMIC-100NF-50V-10%-X7R(0805)"))
    )
    (comp (ref "C18")
      (value "100nF")
      (footprint "eagle-import:C0805")
      (fields (field (name "MPN") "CC0805KRX7R9BB104"))
      (libsource (lib "eagle-import") (part "CERAMIC-100NF-50V-10%-X7R(0805)"))
    )
    (comp (ref "C19")
      (value "100nF")
      (footprint "eagle-import:C0805")
      (fields (field (name "MPN") "CC0805KRX7R9BB104"))
      (libsource (lib "eagle-import") (part "CERAMIC-100NF-50V-10%-X7R(0805)"))
    )
    (comp (ref "C20")
      (value "100nF,")
      (footprint "eagle-import:C0805")
      (fields (field (name "MPN") "CC0805KRX7R9BB104"))
      (libsource (lib "eagle-import") (part "CERAMIC-100NF-50V-10%-X7R(0805)"))
    )
    (comp (ref "D13")
      (value "1N4007")
      (footprint "eagle-import:DO-214AC")
      (libsource (lib "eagle-import") (part "DIODE-GEN-PURPOSE-1KV-1A(DO-214AC)"))
    )
    (comp (ref "D14")
      (value "1N4007,")
      (footprint "eagle-import:DO-214AC")
      (fields (field (name "MPN") "1N4007"))
      (libsource (lib "eagle-import") (part "DIODE-GEN-PURPOSE-1KV-1A(DO-214AC)"))
    )
    (comp (ref "D15")
      (value "1N4007,")
      (footprint "eagle-import:DO-214AC")
      (fields (field (name "MPN") "1N4007"))
      (libsource (lib "eagle-import") (part "DIODE-GEN-PURPOSE-1KV-1A(DO-214AC)"))
    )
    (comp (ref "D16")
      (value "1N4007.")
      (footprint "eagle-import:DO-214AC")
      (fields (field (name "MPN") "1N4007"))
      (libsource (lib "eagle-import") (part "DIODE-GEN-PURPOSE-1KV-1A(DO-214AC)"))
    )
    (comp (ref "D17")
      (value "1N5817")
      (footprint "eagle-import:DO-214AC_SLIM")
      (libsource (lib "eagle-import") (part "DIODE-GEN-PURPOSE-1KV-1A(DO-214AC)DO-214AC/1206"))
    )
    (comp (ref "D18")
      (value "1N5817.")
      (footprint "eagle-import:DO-214AC_SLIM")
      (libsource (lib "eagle-import") (part "DIODE-GEN-PURPOSE-1KV-1A(DO-214AC)DO-214AC/1206"))
    )
    (comp (ref "D19")
      (value "1N5817.")
      (footprint "eagle-import:DO-214AC_SLIM")
      (libsource (lib "eagle-import") (part "DIODE-GEN-PURPOSE-1KV-1A(DO-214AC)DO-214AC/1206"))
    )
    (comp (ref "D20")
      (value "1N5817")
      (footprint "eagle-import:DO-214AC_SLIM")
      (libsource (lib "eagle-import") (part "DIODE-GEN-PURPOSE-1KV-1A(DO-214AC)DO-214AC/1206"))
    )
    (comp (ref "D21")
      (value "1N4007.")
      (footprint "eagle-import:DO-214AC")
      (fields (field (name "MPN") "1N4007"))
      (libsource (lib "eagle-import") (part "DIODE-GEN-PURPOSE-1KV-1A(DO-214AC)"))
    )
    (comp (ref "D22")
      (value "1N4007")
      (footprint "eagle-import:DO-214AC")
      (libsource (lib "eagle-import") (part "DIODE-GEN-PURPOSE-1KV-1A(DO-214AC)"))
    )
    (comp (ref "D23")
      (value "SM6T")
      (footprint "eagle-import:DO214AA")
      (libsource (lib "eagle-import") (part "SM6T"))
    )
    (comp (ref "D24")
      (value "SM6TDO214AA_BI")
      (footprint "eagle-import:DO214AA_BI")
      (libsource (lib "eagle-import") (part "SM6TDO214AA_BI"))
    )
    (comp (ref "FID5")
      (value "FIDUCIAL")
      (footprint "eagle-import:FIDUCIAL_1MM")
      (libsource (lib "eagle-import") (part "FIDUCIAL"))
    )
    (comp (ref "FID6")
      (value "FIDUCIAL")
      (footprint "eagle-import:FIDUCIAL_1MM")
      (libsource (lib "eagle-import") (part "FIDUCIAL"))
    )
    (comp (ref "FID7")
      (value "FIDUCIAL")
      (footprint "eagle-import:FIDUCIAL_1MM")
      (libsource (lib "eagle-import") (part "FIDUCIAL"))
    )
    (comp (ref "FID8")
      (value "FIDUCIAL")
      (footprint "eagle-import:FIDUCIAL_1MM")
      (libsource (lib "eagle-import") (part "FIDUCIAL"))
    )
    (comp (ref "IC12")
      (value "4028")
      (footprint "eagle-import:SO16")
      (libsource (lib "eagle-import") (part "4028D"))
    )
    (comp (ref "IC13")
      (value "6V pos")
      (footprint "eagle-import:78LXX")
      (libsource (lib "eagle-import") (part "v-reg_78LXX"))
    )
    (comp (ref "IC14")
      (value "317TO202H_NOHOLE")
      (footprint "eagle-import:TO220H_NOHOLE")
      (libsource (lib "eagle-import") (part "317TO202H_NOHOLE"))
    )
    (comp (ref "IC15")
      (value "ULN2004")
      (footprint "eagle-import:SO16")
      (libsource (lib "eagle-import") (part "ULN2004AD"))
    )
    (comp (ref "IC16")
      (value "LM339")
      (footprint "eagle-import:SO14")
      (libsource (lib "eagle-import") (part "LM339D"))
    )
    (comp (ref "IC17")
      (value "78L06")
      (footprint "eagle-import:SOT89_ROUND")
      (libsource (lib "eagle-import") (part "78LXXSOT89_ROUND"))
    )
    (comp (ref "IC18")
      (value "555")
      (footprint "eagle-import:SO08")
      (libsource (lib "eagle-import") (part "555DNE"))
    )
    (comp (ref "IC19")
      (value "4538")
      (footprint "eagle-import:SO16")
      (libsource (lib "eagle-import") (part "4538D"))
    )
    (comp (ref "IC20")
      (value "78L10")
      (footprint "eagle-import:SOT89_ROUND")
      (libsource (lib "eagle-import") (part "78LXXSOT89_ROUND"))
    )
    (comp (ref "IC21")
      (value "LM2904")
      (footprint "eagle-import:SO08")
      (libsource (lib "eagle-import") (part "LM358D"))
    )
    (comp (ref "IC22")
      (value "NUP4304SOT457_R")
      (footprint "eagle-import:SOT457R_PHILIPS")
      (libsource (lib "eagle-import") (part "NUP4304SOT457_R"))
    )
    (comp (ref "JP6")
      (value "JP2EJP2_SMALLPADS")
      (footprint "eagle-import:JP2_SMALLPADS")
      (libsource (lib "eagle-import") (part "JP2EJP2_SMALLPADS"))
    )
    (comp (ref "JP7")
      (value "JP2E_ORIG")
      (footprint "eagle-import:JP2_ORIG_SMALLPADS")
      (libsource (lib "eagle-import") (part "JP2E_ORIG"))
    )
    (comp (ref "JP8")
      (value "JP2EJP2_SMALLPADS")
      (footprint "eagle-import:JP2_SMALLPADS")
      (libsource (lib "eagle-import") (part "JP2EJP2_SMALLPADS"))
    )
    (comp (ref "JP9")
      (value "JP2EJP2_SMALLPADS")
      (footprint "eagle-import:JP2_SMALLPADS")
      (libsource (lib "eagle-import") (part "JP2EJP2_SMALLPADS"))
    )
    (comp (ref "JP10")
      (value "JP2EJP2_SMALLPADS")
      (footprint "eagle-import:JP2_SMALLPADS")
      (libsource (lib "eagle-import") (part "JP2EJP2_SMALLPADS"))
    )
    (comp (ref "LED7")
      (value "LEDLD260")
      (footprint "eagle-import:LD260")
      (libsource (lib "eagle-import") (part "LEDLD260"))
    )
    (comp (ref "LED8")
      (value "LEDLD260")
      (footprint "eagle-import:LD260")
      (libsource (lib "eagle-import") (part "LEDLD260"))
    )
    (comp (ref "LED9")
      (value "LEDLD260")
      (footprint "eagle-import:LD260")
      (libsource (lib "eagle-import") (part "LEDLD260"))
    )
    (comp (ref "LED10")
      (value "LEDLD260")
      (footprint "eagle-import:LD260")
      (libsource (lib "eagle-import") (part "LEDLD260"))
    )
    (comp (ref "LED11")
      (value "LEDLD260")
      (footprint "eagle-import:LD260")
      (libsource (lib "eagle-import") (part "LEDLD260"))
    )
    (comp (ref "LED12")
      (value "LEDLD260")
      (footprint "eagle-import:LD260")
      (libsource (lib "eagle-import") (part "LEDLD260"))
    )
    (comp (ref "Q8")
      (value "BA")
      (footprint "eagle-import:SOT89")
      (libsource (lib "eagle-import") (part "PNP-TRANSISTOR_SOT89"))
    )
    (comp (ref "Q9")
      (value "BA.")
      (footprint "eagle-import:SOT89")
      (libsource (lib "eagle-import") (part "PNP-TRANSISTOR_SOT89"))
    )
    (comp (ref "Q10")
      (value "BA.")
      (footprint "eagle-import:SOT89")
      (libsource (lib "eagle-import") (part "PNP-TRANSISTOR_SOT89"))
    )
    (comp (ref "Q11")
      (value "BA")
      (footprint "eagle-import:SOT89")
      (libsource (lib "eagle-import") (part "PNP-TRANSISTOR_SOT89"))
    )
    (comp (ref "Q12")
      (value "MY")
      (footprint "eagle-import:SOT89")
      (libsource (lib "eagle-import") (part "NPN-TRANSISTOR_SOT89"))
    )
    (comp (ref "Q13")
      (value "J1")
      (footprint "eagle-import:SOT-23")
      (fields (field (name "MPN") "BSS138W-7-F"))
      (libsource (lib "eagle-import") (part "SMD-MOSFET-N-CH-50V-200MA-BSS138W-7-F(SOT-23)"))
    )
    (comp (ref "Q14")
      (value "J1")
      (footprint "eagle-import:SOT-23")
      (fields (field (name "MPN") "BSS138W-7-F"))
      (libsource (lib "eagle-import") (part "SMD-MOSFET-N-CH-50V-200MA-BSS138W-7-F(SOT-23)"))
    )
    (comp (ref "R47")
      (value "47")
      (footprint "eagle-import:V235_17_1MM")
      (libsource (lib "eagle-import") (part "R-EU_V235/17_1MM"))
    )
    (comp (ref "R48")
      (value "13")
      (footprint "eagle-import:R1206")
      (fields (field (name "MPN") "RC1206JR-0713RL"))
      (libsource (lib "eagle-import") (part "SMD-RES-13R-5%-1/4W(1206)"))
    )
    (comp (ref "R49")
      (value "47")
      (footprint "eagle-import:V235_17_1MM")
      (libsource (lib "eagle-import") (part "R-EU_V235/17_1MM"))
    )
    (comp (ref "R50")
      (value "104")
      (footprint "eagle-import:R0805")
      (fields (field (name "MPN") "RC0805FR-0710KL"))
      (libsource (lib "eagle-import") (part "SMD-RES-10K-1%-1/8W(0805)"))
    )
    (comp (ref "R51")
      (value "104")
      (footprint "eagle-import:R0805")
      (fields (field (name "MPN") "RC0805FR-0710KL"))
      (libsource (lib "eagle-import") (part "SMD-RES-10K-1%-1/8W(0805)"))
    )
    (comp (ref "R52")
      (value "104")
      (footprint "eagle-import:R0805")
      (fields (field (name "MPN") "RC0805FR-0710KL"))
      (libsource (lib "eagle-import") (part "SMD-RES-10K-1%-1/8W(0805)"))
    )
    (comp (ref "R53")
      (value "4701")
      (footprint "eagle-import:R0805")
      (fields (field (name "MPN") "RC0805JR-074K7L"))
      (libsource (lib "eagle-import") (part "SMD-RES-4.7K-5%-1/8W(0805)"))
    )
    (comp (ref "R54")
      (value "1002")
      (footprint "eagle-import:R0805")
      (fields (field (name "MPN") "RC0805FR-0710KL"))
      (libsource (lib "eagle-import") (part "SMD-RES-10K-1%-1/8W(0805)"))
    )
    (comp (ref "R55")
      (value "1002")
      (footprint "eagle-import:R0805")
      (fields (field (name "MPN") "RC0805FR-0710KL"))
      (libsource (lib "eagle-import") (part "SMD-RES-10K-1%-1/8W(0805)"))
    )
    (comp (ref "R56")
      (value "1502")
      (footprint "eagle-import:R0805")
      (fields (field (name "MPN") "RC0805FR-0710KL"))
      (libsource (lib "eagle-import") (part "SMD-RES-10K-1%-1/8W(0805)"))
    )
    (comp (ref "R57")
      (value "104")
      (footprint "eagle-import:R0805")
      (fields (field (name "MPN") "RC0805FR-0710KL"))
      (libsource (lib "eagle-import") (part "SMD-RES-10K-1%-1/8W(0805)"))
    )
    (comp (ref "R58")
      (value "104")
      (footprint "eagle-import:R0805")
      (fields (field (name "MPN") "RC0805FR-0710KL"))
      (libsource (lib "eagle-import") (part "SMD-RES-10K-1%-1/8W(0805)"))
    )
    (comp (ref "R59")
      (value "1502")
      (footprint "eagle-import:R0805")
      (fields (field (name "MPN") "RC0805FR-0710KL"))
      (libsource (lib "eagle-import") (part "SMD-RES-10K-1%-1/8W(0805)"))
    )
    (comp (ref "R60")
      (value "1002")
      (footprint "eagle-import:R0805")
      (fields (field (name "MPN") "RC0805FR-0710KL"))
      (libsource (lib "eagle-import") (part "SMD-RES-10K-1%-1/8W(0805)"))
    )
    (comp (ref "R61")
      (value "2201")
      (footprint "eagle-import:R0805")
      (fields (field (name "MPN") "RC0805JR-072K2L"))
      (libsource (lib "eagle-import") (part "SMD-RES-2.2K-5%-1/8W(0805)"))
    )
    (comp (ref "R62")
      (value "1002")
      (footprint "eagle-import:R0805")
      (fields (field (name "MPN") "RC0805FR-0710KL"))
      (libsource (lib "eagle-import") (part "SMD-RES-10K-1%-1/8W(0805)"))
    )
    (comp (ref "R63")
      (value "4701")
      (footprint "eagle-import:R0805")
      (fields (field (name "MPN") "RC0805JR-074K7L"))
      (libsource (lib "eagle-import") (part "SMD-RES-4.7K-5%-1/8W(0805)"))
    )
    (comp (ref "R64")
      (value "2702")
      (footprint "eagle-import:R0805")
      (fields (field (name "MPN") "RC0805JR-074K7L"))
      (libsource (lib "eagle-import") (part "SMD-RES-4.7K-5%-1/8W(0805)"))
    )
    (comp (ref "R65")
      (value "102")
      (footprint "eagle-import:R0805")
      (fields (field (name "MPN") "RC0805JR-071KL"))
      (libsource (lib "eagle-import") (part "SMD-RES-1K-5%-1/8W(0805)"))
    )
    (comp (ref "R66")
      (value "R_user")
      (footprint "eagle-import:R0805")
      (libsource (lib "eagle-import") (part "R-EU_R0805"))
    )
    (comp (ref "R67")
      (value "100")
      (footprint "eagle-import:R0805")
      (fields (field (name "MPN") "RC0805JR-07220RL"))
      (libsource (lib "eagle-import") (part "SMD-RES-220R-5%-1/8W(0805)"))
    )
    (comp (ref "R68")
      (value "(101)")
      (footprint "eagle-import:R0805")
      (fields (field (name "MPN") "RC0805JR-07100RL"))
      (libsource (lib "eagle-import") (part "SMD-RES-100R-5%-1/8W(0805)"))
    )
    (comp (ref "R69")
      (value "(1000)")
      (footprint "eagle-import:R0805")
      (fields (field (name "MPN") "RC0805JR-07100RL"))
      (libsource (lib "eagle-import") (part "SMD-RES-100R-5%-1/8W(0805)"))
    )
    (comp (ref "R70")
      (value "102")
      (footprint "eagle-import:R0805")
      (fields (field (name "MPN") "RC0805JR-071KL"))
      (libsource (lib "eagle-import") (part "SMD-RES-1K-5%-1/8W(0805)"))
    )
    (comp (ref "R71")
      (value "13")
      (footprint "eagle-import:R1206")
      (fields (field (name "MPN") "RC1206JR-0713RL"))
      (libsource (lib "eagle-import") (part "SMD-RES-13R-5%-1/4W(1206)"))
    )
    (comp (ref "R72")
      (value "13")
      (footprint "eagle-import:R1206")
      (fields (field (name "MPN") "RC1206JR-0713RL"))
      (libsource (lib "eagle-import") (part "SMD-RES-13R-5%-1/4W(1206)"))
    )
    (comp (ref "R73")
      (value "2702")
      (footprint "eagle-import:R0805")
      (fields (field (name "MPN") "RC0805JR-074K7L"))
      (libsource (lib "eagle-import") (part "SMD-RES-4.7K-5%-1/8W(0805)"))
    )
    (comp (ref "R74")
      (value "4701")
      (footprint "eagle-import:R0805")
      (fields (field (name "MPN") "RC0805JR-074K7L"))
      (libsource (lib "eagle-import") (part "SMD-RES-4.7K-5%-1/8W(0805)"))
    )
    (comp (ref "R75")
      (value "100")
      (footprint "eagle-import:R0805")
      (fields (field (name "MPN") "RC0805JR-072K2L"))
      (libsource (lib "eagle-import") (part "SMD-RES-2.2K-5%-1/8W(0805)"))
    )
    (comp (ref "R76")
      (value "(101)")
      (footprint "eagle-import:R0805")
      (fields (field (name "MPN") "RC0805JR-072K2L"))
      (libsource (lib "eagle-import") (part "SMD-RES-2.2K-5%-1/8W(0805)"))
    )
    (comp (ref "R77")
      (value "104")
      (footprint "eagle-import:R0805")
      (fields (field (name "MPN") "RC0805FR-0710KL"))
      (libsource (lib "eagle-import") (part "SMD-RES-10K-1%-1/8W(0805)"))
    )
    (comp (ref "R78")
      (value "104")
      (footprint "eagle-import:R0805")
      (fields (field (name "MPN") "RC0805FR-0710KL"))
      (libsource (lib "eagle-import") (part "SMD-RES-10K-1%-1/8W(0805)"))
    )
    (comp (ref "R79")
      (value "(1002)")
      (footprint "eagle-import:R0805")
      (fields (field (name "MPN") "RC0805FR-0710KL"))
      (libsource (lib "eagle-import") (part "SMD-RES-10K-1%-1/8W(0805)"))
    )
    (comp (ref "R80")
      (value "2702")
      (footprint "eagle-import:R0805")
      (fields (field (name "MPN") "RC0805FR-0710KL"))
      (libsource (lib "eagle-import") (part "SMD-RES-10K-1%-1/8W(0805)"))
    )
    (comp (ref "R81")
      (value "47")
      (footprint "eagle-import:V235_17_1MM")
      (libsource (lib "eagle-import") (part "R-EU_V235/17_1MM"))
    )
    (comp (ref "R82")
      (value "47")
      (footprint "eagle-import:V235_17_1MM")
      (libsource (lib "eagle-import") (part "R-EU_V235/17_1MM"))
    )
    (comp (ref "R83")
      (value "2702")
      (footprint "eagle-import:R0805")
      (fields (field (name "MPN") "RC0805JR-074K7L"))
      (libsource (lib "eagle-import") (part "SMD-RES-4.7K-5%-1/8W(0805)"))
    )
    (comp (ref "R84")
      (value "2201")
      (footprint "eagle-import:R0805")
      (fields (field (name "MPN") "RC0805JR-072K2L"))
      (libsource (lib "eagle-import") (part "SMD-RES-2.2K-5%-1/8W(0805)"))
    )
    (comp (ref "R85")
      (value "(1002)")
      (footprint "eagle-import:R0805")
      (fields (field (name "MPN") "RC0805JR-074K7L"))
      (libsource (lib "eagle-import") (part "SMD-RES-4.7K-5%-1/8W(0805)"))
    )
    (comp (ref "R86")
      (value "1002")
      (footprint "eagle-import:R0805")
      (fields (field (name "MPN") "RC0805FR-0710KL"))
      (libsource (lib "eagle-import") (part "SMD-RES-10K-1%-1/8W(0805)"))
    )
    (comp (ref "R87")
      (value "102")
      (footprint "eagle-import:R0805")
      (fields (field (name "MPN") "RC0805JR-071KL"))
      (libsource (lib "eagle-import") (part "SMD-RES-1K-5%-1/8W(0805)"))
    )
    (comp (ref "R88")
      (value "2702")
      (footprint "eagle-import:R0805")
      (fields (field (name "MPN") "RC0805JR-074K7L"))
      (libsource (lib "eagle-import") (part "SMD-RES-4.7K-5%-1/8W(0805)"))
    )
    (comp (ref "R89")
      (value "102")
      (footprint "eagle-import:R0805")
      (fields (field (name "MPN") "RC0805JR-071KL"))
      (libsource (lib "eagle-import") (part "SMD-RES-1K-5%-1/8W(0805)"))
    )
    (comp (ref "R90")
      (value "102")
      (footprint "eagle-import:R0805")
      (fields (field (name "MPN") "RC0805JR-071KL"))
      (libsource (lib "eagle-import") (part "SMD-RES-1K-5%-1/8W(0805)"))
    )
    (comp (ref "R91")
      (value "13")
      (footprint "eagle-import:R1206")
      (fields (field (name "MPN") "RC1206JR-0713RL"))
      (libsource (lib "eagle-import") (part "SMD-RES-13R-5%-1/4W(1206)"))
    )
    (comp (ref "R92")
      (value "R_user")
      (footprint "eagle-import:R0805")
      (libsource (lib "eagle-import") (part "R-EU_R0805"))
    )
    (comp (ref "SJ2") (value "SJ") (footprint "eagle-import:SJ") (libsource (lib "eagle-import") (part "SJ")))
    (comp (ref "START1")
      (value "TPSB2.0")
      (footprint "eagle-import:B2.0")
      (libsource (lib "eagle-import") (part "TPSB2.0"))
    )
    (comp (ref "TP14")
      (value "TPSB2.0")
      (footprint "eagle-import:B2.0")
      (libsource (lib "eagle-import") (part "TPSB2.0"))
    )
    (comp (ref "TP15")
      (value "TPSB2.0")
      (footprint "eagle-import:B2.0")
      (libsource (lib "eagle-import") (part "TPSB2.0"))
    )
    (comp (ref "TP20")
      (value "TPSB2.0")
      (footprint "eagle-import:B2.0")
      (libsource (lib "eagle-import") (part "TPSB2.0"))
    )
    (comp (ref "TP27")
      (value "TPSB2.0")
      (footprint "eagle-import:B2.0")
      (libsource (lib "eagle-import") (part "TPSB2.0"))
    )
    (comp (ref "TP28")
      (value "TPSB2.0")
      (footprint "eagle-import:B2.0")
      (libsource (lib "eagle-import") (part "TPSB2.0"))
    )
    (comp (ref "TP29")
      (value "TPSB2.0")
      (footprint "eagle-import:B2.0")
      (libsource (lib "eagle-import") (part "TPSB2.0"))
    )
    (comp (ref "TP30")
      (value "TPSB2.0")
      (footprint "eagle-import:B2.0")
      (libsource (lib "eagle-import") (part "TPSB2.0"))
    )
    (comp (ref "TP31")
      (value "TPSB2.0")
      (footprint "eagle-import:B2.0")
      (libsource (lib "eagle-import") (part "TPSB2.0"))
    )
    (comp (ref "TP32")
      (value "TPSB2.0")
      (footprint "eagle-import:B2.0")
      (libsource (lib "eagle-import") (part "TPSB2.0"))
    )
    (comp (ref "TP33")
      (value "TPSB2.0")
      (footprint "eagle-import:B2.0")
      (libsource (lib "eagle-import") (part "TPSB2.0"))
    )
    (comp (ref "TP34")
      (value "TPSB2.0")
      (footprint "eagle-import:B2.0")
      (libsource (lib "eagle-import") (part "TPSB2.0"))
    )
    (comp (ref "TP35")
      (value "TPSB2.0")
      (footprint "eagle-import:B2.0")
      (libsource (lib "eagle-import") (part "TPSB2.0"))
    )
    (comp (ref "TP36")
      (value "TPSB2.0")
      (footprint "eagle-import:B2.0")
      (libsource (lib "eagle-import") (part "TPSB2.0"))
    )
    (comp (ref "TP37")
      (value "TPSB2.0")
      (footprint "eagle-import:B2.0")
      (libsource (lib "eagle-import") (part "TPSB2.0"))
    )
    (comp (ref "TP38")
      (value "TPSB2.0")
      (footprint "eagle-import:B2.0")
      (libsource (lib "eagle-import") (part "TPSB2.0"))
    )
    (comp (ref "TP39")
      (value "TPSB2.0")
      (footprint "eagle-import:B2.0")
      (libsource (lib "eagle-import") (part "TPSB2.0"))
    )
    (comp (ref "TP40")
      (value "TPSB2.0")
      (footprint "eagle-import:B2.0")
      (libsource (lib "eagle-import") (part "TPSB2.0"))
    )
    (comp (ref "TP41")
      (value "TPSB2.0")
      (footprint "eagle-import:B2.0")
      (libsource (lib "eagle-import") (part "TPSB2.0"))
    )
    (comp (ref "TP42")
      (value "TPSB1,27")
      (footprint "eagle-import:B1,27")
      (libsource (lib "eagle-import") (part "TPSB1,27"))
    )
    (comp (ref "TP43")
      (value "TPSB2.0")
      (footprint "eagle-import:B2.0")
      (libsource (lib "eagle-import") (part "TPSB2.0"))
    )
    (comp (ref "TP44")
      (value "TPSB2.0")
      (footprint "eagle-import:B2.0")
      (libsource (lib "eagle-import") (part "TPSB2.0"))
    )
    (comp (ref "TP45")
      (value "TPSB2.0")
      (footprint "eagle-import:B2.0")
      (libsource (lib "eagle-import") (part "TPSB2.0"))
    )
    (comp (ref "TP46")
      (value "TPSB2.0")
      (footprint "eagle-import:B2.0")
      (libsource (lib "eagle-import") (part "TPSB2.0"))
    )
    (comp (ref "X4")
      (value "CON_BMWV2")
      (footprint "eagle-import:24-PIN_V2")
      (libsource (lib "eagle-import") (part "CON_BMWV2"))
    )
    (comp (ref "X5")
      (value "22-23-2051")
      (footprint "eagle-import:22-23-2051")
      (fields (field (name "MF") "MOLEX"))
      (libsource (lib "eagle-import") (part "22-23-2051"))
    )
    (comp (ref "X6")
      (value "22-23-2021")
      (footprint "eagle-import:22-23-2021")
      (fields (field (name "MF") "MOLEX"))
      (libsource (lib "eagle-import") (part "22-23-2021"))
    )
    (comp (ref "5")
      (value "2081-1132")
      (footprint "eagle-import:12-PIN")
      (libsource (lib "eagle-import") (part "2081-1132"))
    )
    (comp (ref "6")
      (value "2081-1132")
      (footprint "eagle-import:12-PIN")
      (libsource (lib "eagle-import") (part "2081-1132"))
    )
    (comp (ref "6V2")
      (value "TPSB2.0")
      (footprint "eagle-import:B2.0")
      (libsource (lib "eagle-import") (part "TPSB2.0"))
    )
    (comp (ref "10V2")
      (value "TPSB2.0")
      (footprint "eagle-import:B2.0")
      (libsource (lib "eagle-import") (part "TPSB2.0"))
    )
    (comp (ref "C21")
      (value "100u")
      (footprint "eagle-import:C1206")
      (fields (field (name "MPN") "GRM31CR60J107ME39L"))
      (libsource (lib "eagle-import") (part "CERAMIC-100UF-6.3V-20%-X5R(1206)"))
    )
    (comp (ref "C22")
      (value "100u")
      (footprint "eagle-import:C1206")
      (fields (field (name "MPN") "GRM31CR60J107ME39L"))
      (libsource (lib "eagle-import") (part "CERAMIC-100UF-6.3V-20%-X5R(1206)"))
    )
    (comp (ref "C23")
      (value "100nF,")
      (footprint "eagle-import:C0805")
      (fields (field (name "MPN") "CC0805KRX7R9BB104"))
      (libsource (lib "eagle-import") (part "CERAMIC-100NF-50V-10%-X7R(0805)"))
    )
    (comp (ref "C24")
      (value "4.7u")
      (footprint "eagle-import:C0805")
      (fields (field (name "MPN") "CC0805KKX5R8BB475"))
      (libsource (lib "eagle-import") (part "CERAMIC-4.7UF-25V-10%-X5R(0805)"))
    )
    (comp (ref "C25")
      (value "100nF.")
      (footprint "eagle-import:C0805")
      (fields (field (name "MPN") "CC0805KRX7R9BB104"))
      (libsource (lib "eagle-import") (part "CERAMIC-100NF-50V-10%-X7R(0805)"))
    )
    (comp (ref "C26")
      (value "100nF.")
      (footprint "eagle-import:C0805")
      (fields (field (name "MPN") "CC0805KRX7R9BB104"))
      (libsource (lib "eagle-import") (part "CERAMIC-100NF-50V-10%-X7R(0805)"))
    )
    (comp (ref "C27")
      (value "2.2nF")
      (footprint "eagle-import:C0805")
      (fields (field (name "MPN") "CC0805KRX7R9BB104"))
      (libsource (lib "eagle-import") (part "CERAMIC-100NF-50V-10%-X7R(0805)"))
    )
    (comp (ref "C28")
      (value "100nF")
      (footprint "eagle-import:C0805")
      (fields (field (name "MPN") "CC0805KRX7R9BB104"))
      (libsource (lib "eagle-import") (part "CERAMIC-100NF-50V-10%-X7R(0805)"))
    )
    (comp (ref "C29")
      (value "100nF")
      (footprint "eagle-import:C0805")
      (fields (field (name "MPN") "CC0805KRX7R9BB104"))
      (libsource (lib "eagle-import") (part "CERAMIC-100NF-50V-10%-X7R(0805)"))
    )
    (comp (ref "C30")
      (value "100nF,")
      (footprint "eagle-import:C0805")
      (fields (field (name "MPN") "CC0805KRX7R9BB104"))
      (libsource (lib "eagle-import") (part "CERAMIC-100NF-50V-10%-X7R(0805)"))
    )
    (comp (ref "D25")
      (value "1N4007")
      (footprint "eagle-import:DO-214AC")
      (libsource (lib "eagle-import") (part "DIODE-GEN-PURPOSE-1KV-1A(DO-214AC)"))
    )
    (comp (ref "D26")
      (value "1N4007,")
      (footprint "eagle-import:DO-214AC")
      (fields (field (name "MPN") "1N4007"))
      (libsource (lib "eagle-import") (part "DIODE-GEN-PURPOSE-1KV-1A(DO-214AC)"))
    )
    (comp (ref "D27")
      (value "1N4007,")
      (footprint "eagle-import:DO-214AC")
      (fields (field (name "MPN") "1N4007"))
      (libsource (lib "eagle-import") (part "DIODE-GEN-PURPOSE-1KV-1A(DO-214AC)"))
    )
    (comp (ref "D28")
      (value "1N4007.")
      (footprint "eagle-import:DO-214AC")
      (fields (field (name "MPN") "1N4007"))
      (libsource (lib "eagle-import") (part "DIODE-GEN-PURPOSE-1KV-1A(DO-214AC)"))
    )
    (comp (ref "D29")
      (value "1N5817")
      (footprint "eagle-import:DO-214AC_SLIM")
      (libsource (lib "eagle-import") (part "DIODE-GEN-PURPOSE-1KV-1A(DO-214AC)DO-214AC/1206"))
    )
    (comp (ref "D30")
      (value "1N5817.")
      (footprint "eagle-import:DO-214AC_SLIM")
      (libsource (lib "eagle-import") (part "DIODE-GEN-PURPOSE-1KV-1A(DO-214AC)DO-214AC/1206"))
    )
    (comp (ref "D31")
      (value "1N5817.")
      (footprint "eagle-import:DO-214AC_SLIM")
      (libsource (lib "eagle-import") (part "DIODE-GEN-PURPOSE-1KV-1A(DO-214AC)DO-214AC/1206"))
    )
    (comp (ref "D32")
      (value "1N5817")
      (footprint "eagle-import:DO-214AC_SLIM")
      (libsource (lib "eagle-import") (part "DIODE-GEN-PURPOSE-1KV-1A(DO-214AC)DO-214AC/1206"))
    )
    (comp (ref "D33")
      (value "1N4007.")
      (footprint "eagle-import:DO-214AC")
      (fields (field (name "MPN") "1N4007"))
      (libsource (lib "eagle-import") (part "DIODE-GEN-PURPOSE-1KV-1A(DO-214AC)"))
    )
    (comp (ref "D34")
      (value "1N4007")
      (footprint "eagle-import:DO-214AC")
      (libsource (lib "eagle-import") (part "DIODE-GEN-PURPOSE-1KV-1A(DO-214AC)"))
    )
    (comp (ref "D35")
      (value "SM6T")
      (footprint "eagle-import:DO214AA")
      (libsource (lib "eagle-import") (part "SM6T"))
    )
    (comp (ref "D36")
      (value "SM6TDO214AA_BI")
      (footprint "eagle-import:DO214AA_BI")
      (libsource (lib "eagle-import") (part "SM6TDO214AA_BI"))
    )
    (comp (ref "FID9")
      (value "FIDUCIAL")
      (footprint "eagle-import:FIDUCIAL_1MM")
      (libsource (lib "eagle-import") (part "FIDUCIAL"))
    )
    (comp (ref "FID10")
      (value "FIDUCIAL")
      (footprint "eagle-import:FIDUCIAL_1MM")
      (libsource (lib "eagle-import") (part "FIDUCIAL"))
    )
    (comp (ref "FID11")
      (value "FIDUCIAL")
      (footprint "eagle-import:FIDUCIAL_1MM")
      (libsource (lib "eagle-import") (part "FIDUCIAL"))
    )
    (comp (ref "FID12")
      (value "FIDUCIAL")
      (footprint "eagle-import:FIDUCIAL_1MM")
      (libsource (lib "eagle-import") (part "FIDUCIAL"))
    )
    (comp (ref "IC23")
      (value "4028")
      (footprint "eagle-import:SO16")
      (libsource (lib "eagle-import") (part "4028D"))
    )
    (comp (ref "IC24")
      (value "6V pos")
      (footprint "eagle-import:78LXX")
      (libsource (lib "eagle-import") (part "v-reg_78LXX"))
    )
    (comp (ref "IC25")
      (value "317TO202H_NOHOLE")
      (footprint "eagle-import:TO220H_NOHOLE")
      (libsource (lib "eagle-import") (part "317TO202H_NOHOLE"))
    )
    (comp (ref "IC26")
      (value "ULN2004")
      (footprint "eagle-import:SO16")
      (libsource (lib "eagle-import") (part "ULN2004AD"))
    )
    (comp (ref "IC27")
      (value "LM339")
      (footprint "eagle-import:SO14")
      (libsource (lib "eagle-import") (part "LM339D"))
    )
    (comp (ref "IC28")
      (value "78L06")
      (footprint "eagle-import:SOT89_ROUND")
      (libsource (lib "eagle-import") (part "78LXXSOT89_ROUND"))
    )
    (comp (ref "IC29")
      (value "555")
      (footprint "eagle-import:SO08")
      (libsource (lib "eagle-import") (part "555DNE"))
    )
    (comp (ref "IC30")
      (value "4538")
      (footprint "eagle-import:SO16")
      (libsource (lib "eagle-import") (part "4538D"))
    )
    (comp (ref "IC31")
      (value "78L10")
      (footprint "eagle-import:SOT89_ROUND")
      (libsource (lib "eagle-import") (part "78LXXSOT89_ROUND"))
    )
    (comp (ref "IC32")
      (value "LM2904")
      (footprint "eagle-import:SO08")
      (libsource (lib "eagle-import") (part "LM358D"))
    )
    (comp (ref "IC33")
      (value "NUP4304SOT457_R")
      (footprint "eagle-import:SOT457R_PHILIPS")
      (libsource (lib "eagle-import") (part "NUP4304SOT457_R"))
    )
    (comp (ref "JP11")
      (value "JP2EJP2_SMALLPADS")
      (footprint "eagle-import:JP2_SMALLPADS")
      (libsource (lib "eagle-import") (part "JP2EJP2_SMALLPADS"))
    )
    (comp (ref "JP12")
      (value "JP2E_ORIG")
      (footprint "eagle-import:JP2_ORIG_SMALLPADS")
      (libsource (lib "eagle-import") (part "JP2E_ORIG"))
    )
    (comp (ref "JP13")
      (value "JP2EJP2_SMALLPADS")
      (footprint "eagle-import:JP2_SMALLPADS")
      (libsource (lib "eagle-import") (part "JP2EJP2_SMALLPADS"))
    )
    (comp (ref "JP14")
      (value "JP2EJP2_SMALLPADS")
      (footprint "eagle-import:JP2_SMALLPADS")
      (libsource (lib "eagle-import") (part "JP2EJP2_SMALLPADS"))
    )
    (comp (ref "JP15")
      (value "JP2EJP2_SMALLPADS")
      (footprint "eagle-import:JP2_SMALLPADS")
      (libsource (lib "eagle-import") (part "JP2EJP2_SMALLPADS"))
    )
    (comp (ref "LED13")
      (value "LEDLD260")
      (footprint "eagle-import:LD260")
      (libsource (lib "eagle-import") (part "LEDLD260"))
    )
    (comp (ref "LED14")
      (value "LEDLD260")
      (footprint "eagle-import:LD260")
      (libsource (lib "eagle-import") (part "LEDLD260"))
    )
    (comp (ref "LED15")
      (value "LEDLD260")
      (footprint "eagle-import:LD260")
      (libsource (lib "eagle-import") (part "LEDLD260"))
    )
    (comp (ref "LED16")
      (value "LEDLD260")
      (footprint "eagle-import:LD260")
      (libsource (lib "eagle-import") (part "LEDLD260"))
    )
    (comp (ref "LED17")
      (value "LEDLD260")
      (footprint "eagle-import:LD260")
      (libsource (lib "eagle-import") (part "LEDLD260"))
    )
    (comp (ref "LED18")
      (value "LEDLD260")
      (footprint "eagle-import:LD260")
      (libsource (lib "eagle-import") (part "LEDLD260"))
    )
    (comp (ref "Q15")
      (value "BA")
      (footprint "eagle-import:SOT89")
      (libsource (lib "eagle-import") (part "PNP-TRANSISTOR_SOT89"))
    )
    (comp (ref "Q16")
      (value "BA.")
      (footprint "eagle-import:SOT89")
      (libsource (lib "eagle-import") (part "PNP-TRANSISTOR_SOT89"))
    )
    (comp (ref "Q17")
      (value "BA.")
      (footprint "eagle-import:SOT89")
      (libsource (lib "eagle-import") (part "PNP-TRANSISTOR_SOT89"))
    )
    (comp (ref "Q18")
      (value "BA")
      (footprint "eagle-import:SOT89")
      (libsource (lib "eagle-import") (part "PNP-TRANSISTOR_SOT89"))
    )
    (comp (ref "Q19")
      (value "MY")
      (footprint "eagle-import:SOT89")
      (libsource (lib "eagle-import") (part "NPN-TRANSISTOR_SOT89"))
    )
    (comp (ref "Q20")
      (value "J1")
      (footprint "eagle-import:SOT-23")
      (fields (field (name "MPN") "BSS138W-7-F"))
      (libsource (lib "eagle-import") (part "SMD-MOSFET-N-CH-50V-200MA-BSS138W-7-F(SOT-23)"))
    )
    (comp (ref "Q21")
      (value "J1")
      (footprint "eagle-import:SOT-23")
      (fields (field (name "MPN") "BSS138W-7-F"))
      (libsource (lib "eagle-import") (part "SMD-MOSFET-N-CH-50V-200MA-BSS138W-7-F(SOT-23)"))
    )
    (comp (ref "R93")
      (value "47")
      (footprint "eagle-import:V235_17_1MM")
      (libsource (lib "eagle-import") (part "R-EU_V235/17_1MM"))
    )
    (comp (ref "R94")
      (value "13")
      (footprint "eagle-import:R1206")
      (fields (field (name "MPN") "RC1206JR-0713RL"))
      (libsource (lib "eagle-import") (part "SMD-RES-13R-5%-1/4W(1206)"))
    )
    (comp (ref "R95")
      (value "47")
      (footprint "eagle-import:V235_17_1MM")
      (libsource (lib "eagle-import") (part "R-EU_V235/17_1MM"))
    )
    (comp (ref "R96")
      (value "104")
      (footprint "eagle-import:R0805")
      (fields (field (name "MPN") "RC0805FR-0710KL"))
      (libsource (lib "eagle-import") (part "SMD-RES-10K-1%-1/8W(0805)"))
    )
    (comp (ref "R97")
      (value "104")
      (footprint "eagle-import:R0805")
      (fields (field (name "MPN") "RC0805FR-0710KL"))
      (libsource (lib "eagle-import") (part "SMD-RES-10K-1%-1/8W(0805)"))
    )
    (comp (ref "R98")
      (value "104")
      (footprint "eagle-import:R0805")
      (fields (field (name "MPN") "RC0805FR-0710KL"))
      (libsource (lib "eagle-import") (part "SMD-RES-10K-1%-1/8W(0805)"))
    )
    (comp (ref "R99")
      (value "4701")
      (footprint "eagle-import:R0805")
      (fields (field (name "MPN") "RC0805JR-074K7L"))
      (libsource (lib "eagle-import") (part "SMD-RES-4.7K-5%-1/8W(0805)"))
    )
    (comp (ref "R100")
      (value "1002")
      (footprint "eagle-import:R0805")
      (fields (field (name "MPN") "RC0805FR-0710KL"))
      (libsource (lib "eagle-import") (part "SMD-RES-10K-1%-1/8W(0805)"))
    )
    (comp (ref "R101")
      (value "1002")
      (footprint "eagle-import:R0805")
      (fields (field (name "MPN") "RC0805FR-0710KL"))
      (libsource (lib "eagle-import") (part "SMD-RES-10K-1%-1/8W(0805)"))
    )
    (comp (ref "R102")
      (value "1502")
      (footprint "eagle-import:R0805")
      (fields (field (name "MPN") "RC0805FR-0710KL"))
      (libsource (lib "eagle-import") (part "SMD-RES-10K-1%-1/8W(0805)"))
    )
    (comp (ref "R103")
      (value "104")
      (footprint "eagle-import:R0805")
      (fields (field (name "MPN") "RC0805FR-0710KL"))
      (libsource (lib "eagle-import") (part "SMD-RES-10K-1%-1/8W(0805)"))
    )
    (comp (ref "R104")
      (value "104")
      (footprint "eagle-import:R0805")
      (fields (field (name "MPN") "RC0805FR-0710KL"))
      (libsource (lib "eagle-import") (part "SMD-RES-10K-1%-1/8W(0805)"))
    )
    (comp (ref "R105")
      (value "1502")
      (footprint "eagle-import:R0805")
      (fields (field (name "MPN") "RC0805FR-0710KL"))
      (libsource (lib "eagle-import") (part "SMD-RES-10K-1%-1/8W(0805)"))
    )
    (comp (ref "R106")
      (value "1002")
      (footprint "eagle-import:R0805")
      (fields (field (name "MPN") "RC0805FR-0710KL"))
      (libsource (lib "eagle-import") (part "SMD-RES-10K-1%-1/8W(0805)"))
    )
    (comp (ref "R107")
      (value "2201")
      (footprint "eagle-import:R0805")
      (fields (field (name "MPN") "RC0805JR-072K2L"))
      (libsource (lib "eagle-import") (part "SMD-RES-2.2K-5%-1/8W(0805)"))
    )
    (comp (ref "R108")
      (value "1002")
      (footprint "eagle-import:R0805")
      (fields (field (name "MPN") "RC0805FR-0710KL"))
      (libsource (lib "eagle-import") (part "SMD-RES-10K-1%-1/8W(0805)"))
    )
    (comp (ref "R109")
      (value "4701")
      (footprint "eagle-import:R0805")
      (fields (field (name "MPN") "RC0805JR-074K7L"))
      (libsource (lib "eagle-import") (part "SMD-RES-4.7K-5%-1/8W(0805)"))
    )
    (comp (ref "R110")
      (value "2702")
      (footprint "eagle-import:R0805")
      (fields (field (name "MPN") "RC0805JR-074K7L"))
      (libsource (lib "eagle-import") (part "SMD-RES-4.7K-5%-1/8W(0805)"))
    )
    (comp (ref "R111")
      (value "102")
      (footprint "eagle-import:R0805")
      (fields (field (name "MPN") "RC0805JR-071KL"))
      (libsource (lib "eagle-import") (part "SMD-RES-1K-5%-1/8W(0805)"))
    )
    (comp (ref "R112")
      (value "R_user")
      (footprint "eagle-import:R0805")
      (libsource (lib "eagle-import") (part "R-EU_R0805"))
    )
    (comp (ref "R113")
      (value "100")
      (footprint "eagle-import:R0805")
      (fields (field (name "MPN") "RC0805JR-07220RL"))
      (libsource (lib "eagle-import") (part "SMD-RES-220R-5%-1/8W(0805)"))
    )
    (comp (ref "R114")
      (value "(101)")
      (footprint "eagle-import:R0805")
      (fields (field (name "MPN") "RC0805JR-07100RL"))
      (libsource (lib "eagle-import") (part "SMD-RES-100R-5%-1/8W(0805)"))
    )
    (comp (ref "R115")
      (value "(1000)")
      (footprint "eagle-import:R0805")
      (fields (field (name "MPN") "RC0805JR-07100RL"))
      (libsource (lib "eagle-import") (part "SMD-RES-100R-5%-1/8W(0805)"))
    )
    (comp (ref "R116")
      (value "102")
      (footprint "eagle-import:R0805")
      (fields (field (name "MPN") "RC0805JR-071KL"))
      (libsource (lib "eagle-import") (part "SMD-RES-1K-5%-1/8W(0805)"))
    )
    (comp (ref "R117")
      (value "13")
      (footprint "eagle-import:R1206")
      (fields (field (name "MPN") "RC1206JR-0713RL"))
      (libsource (lib "eagle-import") (part "SMD-RES-13R-5%-1/4W(1206)"))
    )
    (comp (ref "R118")
      (value "13")
      (footprint "eagle-import:R1206")
      (fields (field (name "MPN") "RC1206JR-0713RL"))
      (libsource (lib "eagle-import") (part "SMD-RES-13R-5%-1/4W(1206)"))
    )
    (comp (ref "R119")
      (value "2702")
      (footprint "eagle-import:R0805")
      (fields (field (name "MPN") "RC0805JR-074K7L"))
      (libsource (lib "eagle-import") (part "SMD-RES-4.7K-5%-1/8W(0805)"))
    )
    (comp (ref "R120")
      (value "4701")
      (footprint "eagle-import:R0805")
      (fields (field (name "MPN") "RC0805JR-074K7L"))
      (libsource (lib "eagle-import") (part "SMD-RES-4.7K-5%-1/8W(0805)"))
    )
    (comp (ref "R121")
      (value "100")
      (footprint "eagle-import:R0805")
      (fields (field (name "MPN") "RC0805JR-072K2L"))
      (libsource (lib "eagle-import") (part "SMD-RES-2.2K-5%-1/8W(0805)"))
    )
    (comp (ref "R122")
      (value "(101)")
      (footprint "eagle-import:R0805")
      (fields (field (name "MPN") "RC0805JR-072K2L"))
      (libsource (lib "eagle-import") (part "SMD-RES-2.2K-5%-1/8W(0805)"))
    )
    (comp (ref "R123")
      (value "104")
      (footprint "eagle-import:R0805")
      (fields (field (name "MPN") "RC0805FR-0710KL"))
      (libsource (lib "eagle-import") (part "SMD-RES-10K-1%-1/8W(0805)"))
    )
    (comp (ref "R124")
      (value "104")
      (footprint "eagle-import:R0805")
      (fields (field (name "MPN") "RC0805FR-0710KL"))
      (libsource (lib "eagle-import") (part "SMD-RES-10K-1%-1/8W(0805)"))
    )
    (comp (ref "R125")
      (value "(1002)")
      (footprint "eagle-import:R0805")
      (fields (field (name "MPN") "RC0805FR-0710KL"))
      (libsource (lib "eagle-import") (part "SMD-RES-10K-1%-1/8W(0805)"))
    )
    (comp (ref "R126")
      (value "2702")
      (footprint "eagle-import:R0805")
      (fields (field (name "MPN") "RC0805FR-0710KL"))
      (libsource (lib "eagle-import") (part "SMD-RES-10K-1%-1/8W(0805)"))
    )
    (comp (ref "R127")
      (value "47")
      (footprint "eagle-import:V235_17_1MM")
      (libsource (lib "eagle-import") (part "R-EU_V235/17_1MM"))
    )
    (comp (ref "R128")
      (value "47")
      (footprint "eagle-import:V235_17_1MM")
      (libsource (lib "eagle-import") (part "R-EU_V235/17_1MM"))
    )
    (comp (ref "R129")
      (value "2702")
      (footprint "eagle-import:R0805")
      (fields (field (name "MPN") "RC0805JR-074K7L"))
      (libsource (lib "eagle-import") (part "SMD-RES-4.7K-5%-1/8W(0805)"))
    )
    (comp (ref "R130")
      (value "2201")
      (footprint "eagle-import:R0805")
      (fields (field (name "MPN") "RC0805JR-072K2L"))
      (libsource (lib "eagle-import") (part "SMD-RES-2.2K-5%-1/8W(0805)"))
    )
    (comp (ref "R131")
      (value "(1002)")
      (footprint "eagle-import:R0805")
      (fields (field (name "MPN") "RC0805JR-074K7L"))
      (libsource (lib "eagle-import") (part "SMD-RES-4.7K-5%-1/8W(0805)"))
    )
    (comp (ref "R132")
      (value "1002")
      (footprint "eagle-import:R0805")
      (fields (field (name "MPN") "RC0805FR-0710KL"))
      (libsource (lib "eagle-import") (part "SMD-RES-10K-1%-1/8W(0805)"))
    )
    (comp (ref "R133")
      (value "102")
      (footprint "eagle-import:R0805")
      (fields (field (name "MPN") "RC0805JR-071KL"))
      (libsource (lib "eagle-import") (part "SMD-RES-1K-5%-1/8W(0805)"))
    )
    (comp (ref "R134")
      (value "2702")
      (footprint "eagle-import:R0805")
      (fields (field (name "MPN") "RC0805JR-074K7L"))
      (libsource (lib "eagle-import") (part "SMD-RES-4.7K-5%-1/8W(0805)"))
    )
    (comp (ref "R135")
      (value "102")
      (footprint "eagle-import:R0805")
      (fields (field (name "MPN") "RC0805JR-071KL"))
      (libsource (lib "eagle-import") (part "SMD-RES-1K-5%-1/8W(0805)"))
    )
    (comp (ref "R136")
      (value "102")
      (footprint "eagle-import:R0805")
      (fields (field (name "MPN") "RC0805JR-071KL"))
      (libsource (lib "eagle-import") (part "SMD-RES-1K-5%-1/8W(0805)"))
    )
    (comp (ref "R137")
      (value "13")
      (footprint "eagle-import:R1206")
      (fields (field (name "MPN") "RC1206JR-0713RL"))
      (libsource (lib "eagle-import") (part "SMD-RES-13R-5%-1/4W(1206)"))
    )
    (comp (ref "R138")
      (value "R_user")
      (footprint "eagle-import:R0805")
      (libsource (lib "eagle-import") (part "R-EU_R0805"))
    )
    (comp (ref "SJ3") (value "SJ") (footprint "eagle-import:SJ") (libsource (lib "eagle-import") (part "SJ")))
    (comp (ref "START2")
      (value "TPSB2.0")
      (footprint "eagle-import:B2.0")
      (libsource (lib "eagle-import") (part "TPSB2.0"))
    )
    (comp (ref "TP47")
      (value "TPSB2.0")
      (footprint "eagle-import:B2.0")
      (libsource (lib "eagle-import") (part "TPSB2.0"))
    )
    (comp (ref "TP48")
      (value "TPSB2.0")
      (footprint "eagle-import:B2.0")
      (libsource (lib "eagle-import") (part "TPSB2.0"))
    )
    (comp (ref "TP49")
      (value "TPSB2.0")
      (footprint "eagle-import:B2.0")
      (libsource (lib "eagle-import") (part "TPSB2.0"))
    )
    (comp (ref "TP50")
      (value "TPSB2.0")
      (footprint "eagle-import:B2.0")
      (libsource (lib "eagle-import") (part "TPSB2.0"))
    )
    (comp (ref "TP51")
      (value "TPSB2.0")
      (footprint "eagle-import:B2.0")
      (libsource (lib "eagle-import") (part "TPSB2.0"))
    )
    (comp (ref "TP52")
      (value "TPSB2.0")
      (footprint "eagle-import:B2.0")
      (libsource (lib "eagle-import") (part "TPSB2.0"))
    )
    (comp (ref "TP53")
      (value "TPSB2.0")
      (footprint "eagle-import:B2.0")
      (libsource (lib "eagle-import") (part "TPSB2.0"))
    )
    (comp (ref "TP54")
      (value "TPSB2.0")
      (footprint "eagle-import:B2.0")
      (libsource (lib "eagle-import") (part "TPSB2.0"))
    )
    (comp (ref "TP55")
      (value "TPSB2.0")
      (footprint "eagle-import:B2.0")
      (libsource (lib "eagle-import") (part "TPSB2.0"))
    )
    (comp (ref "TP56")
      (value "TPSB2.0")
      (footprint "eagle-import:B2.0")
      (libsource (lib "eagle-import") (part "TPSB2.0"))
    )
    (comp (ref "TP57")
      (value "TPSB2.0")
      (footprint "eagle-import:B2.0")
      (libsource (lib "eagle-import") (part "TPSB2.0"))
    )
    (comp (ref "TP58")
      (value "TPSB2.0")
      (footprint "eagle-import:B2.0")
      (libsource (lib "eagle-import") (part "TPSB2.0"))
    )
    (comp (ref "TP59")
      (value "TPSB2.0")
      (footprint "eagle-import:B2.0")
      (libsource (lib "eagle-import") (part "TPSB2.0"))
    )
    (comp (ref "TP60")
      (value "TPSB2.0")
      (footprint "eagle-import:B2.0")
      (libsource (lib "eagle-import") (part "TPSB2.0"))
    )
    (comp (ref "TP61")
      (value "TPSB2.0")
      (footprint "eagle-import:B2.0")
      (libsource (lib "eagle-import") (part "TPSB2.0"))
    )
    (comp (ref "TP62")
      (value "TPSB2.0")
      (footprint "eagle-import:B2.0")
      (libsource (lib "eagle-import") (part "TPSB2.0"))
    )
    (comp (ref "TP63")
      (value "TPSB2.0")
      (footprint "eagle-import:B2.0")
      (libsource (lib "eagle-import") (part "TPSB2.0"))
    )
    (comp (ref "TP64")
      (value "TPSB2.0")
      (footprint "eagle-import:B2.0")
      (libsource (lib "eagle-import") (part "TPSB2.0"))
    )
    (comp (ref "TP65")
      (value "TPSB1,27")
      (footprint "eagle-import:B1,27")
      (libsource (lib "eagle-import") (part "TPSB1,27"))
    )
    (comp (ref "TP66")
      (value "TPSB2.0")
      (footprint "eagle-import:B2.0")
      (libsource (lib "eagle-import") (part "TPSB2.0"))
    )
    (comp (ref "TP67")
      (value "TPSB2.0")
      (footprint "eagle-import:B2.0")
      (libsource (lib "eagle-import") (part "TPSB2.0"))
    )
    (comp (ref "TP68")
      (value "TPSB2.0")
      (footprint "eagle-import:B2.0")
      (libsource (lib "eagle-import") (part "TPSB2.0"))
    )
    (comp (ref "TP69")
      (value "TPSB2.0")
      (footprint "eagle-import:B2.0")
      (libsource (lib "eagle-import") (part "TPSB2.0"))
    )
    (comp (ref "X7")
      (value "CON_BMWV2")
      (footprint "eagle-import:24-PIN_V2")
      (libsource (lib "eagle-import") (part "CON_BMWV2"))
    )
    (comp (ref "X8")
      (value "22-23-2051")
      (footprint "eagle-import:22-23-2051")
      (fields (field (name "MF") "MOLEX"))
      (libsource (lib "eagle-import") (part "22-23-2051"))
    )
    (comp (ref "X9")
      (value "22-23-2021")
      (footprint "eagle-import:22-23-2021")
      (fields (field (name "MF") "MOLEX"))
      (libsource (lib "eagle-import") (part "22-23-2021"))
    )
    (comp (ref "6V10")
      (value "TPSB2.0")
      (footprint "eagle-import:B2.0")
      (libsource (lib "eagle-import") (part "TPSB2.0"))
    )
    (comp (ref "10V10")
      (value "TPSB2.0")
      (footprint "eagle-import:B2.0")
      (libsource (lib "eagle-import") (part "TPSB2.0"))
    )
    (comp (ref "21")
      (value "2081-1132")
      (footprint "eagle-import:12-PIN")
      (libsource (lib "eagle-import") (part "2081-1132"))
    )
    (comp (ref "22")
      (value "2081-1132")
      (footprint "eagle-import:12-PIN")
      (libsource (lib "eagle-import") (part "2081-1132"))
    )
    (comp (ref "C101")
      (value "100u")
      (footprint "eagle-import:C1206")
      (fields (field (name "MPN") "GRM31CR60J107ME39L"))
      (libsource (lib "eagle-import") (part "CERAMIC-100UF-6.3V-20%-X5R(1206)"))
    )
    (comp (ref "C102")
      (value "100u")
      (footprint "eagle-import:C1206")
      (fields (field (name "MPN") "GRM31CR60J107ME39L"))
      (libsource (lib "eagle-import") (part "CERAMIC-100UF-6.3V-20%-X5R(1206)"))
    )
    (comp (ref "C103")
      (value "100nF,")
      (footprint "eagle-import:C0805")
      (fields (field (name "MPN") "CC0805KRX7R9BB104"))
      (libsource (lib "eagle-import") (part "CERAMIC-100NF-50V-10%-X7R(0805)"))
    )
    (comp (ref "C104")
      (value "4.7u")
      (footprint "eagle-import:C0805")
      (fields (field (name "MPN") "CC0805KKX5R8BB475"))
      (libsource (lib "eagle-import") (part "CERAMIC-4.7UF-25V-10%-X5R(0805)"))
    )
    (comp (ref "C105")
      (value "100nF.")
      (footprint "eagle-import:C0805")
      (fields (field (name "MPN") "CC0805KRX7R9BB104"))
      (libsource (lib "eagle-import") (part "CERAMIC-100NF-50V-10%-X7R(0805)"))
    )
    (comp (ref "C106")
      (value "100nF.")
      (footprint "eagle-import:C0805")
      (fields (field (name "MPN") "CC0805KRX7R9BB104"))
      (libsource (lib "eagle-import") (part "CERAMIC-100NF-50V-10%-X7R(0805)"))
    )
    (comp (ref "C107")
      (value "2.2nF")
      (footprint "eagle-import:C0805")
      (fields (field (name "MPN") "CC0805KRX7R9BB104"))
      (libsource (lib "eagle-import") (part "CERAMIC-100NF-50V-10%-X7R(0805)"))
    )
    (comp (ref "C108")
      (value "100nF")
      (footprint "eagle-import:C0805")
      (fields (field (name "MPN") "CC0805KRX7R9BB104"))
      (libsource (lib "eagle-import") (part "CERAMIC-100NF-50V-10%-X7R(0805)"))
    )
    (comp (ref "C109")
      (value "100nF")
      (footprint "eagle-import:C0805")
      (fields (field (name "MPN") "CC0805KRX7R9BB104"))
      (libsource (lib "eagle-import") (part "CERAMIC-100NF-50V-10%-X7R(0805)"))
    )
    (comp (ref "C110")
      (value "100nF,")
      (footprint "eagle-import:C0805")
      (fields (field (name "MPN") "CC0805KRX7R9BB104"))
      (libsource (lib "eagle-import") (part "CERAMIC-100NF-50V-10%-X7R(0805)"))
    )
    (comp (ref "D121")
      (value "1N4007")
      (footprint "eagle-import:DO-214AC")
      (libsource (lib "eagle-import") (part "DIODE-GEN-PURPOSE-1KV-1A(DO-214AC)"))
    )
    (comp (ref "D122")
      (value "1N4007,")
      (footprint "eagle-import:DO-214AC")
      (fields (field (name "MPN") "1N4007"))
      (libsource (lib "eagle-import") (part "DIODE-GEN-PURPOSE-1KV-1A(DO-214AC)"))
    )
    (comp (ref "D123")
      (value "1N4007,")
      (footprint "eagle-import:DO-214AC")
      (fields (field (name "MPN") "1N4007"))
      (libsource (lib "eagle-import") (part "DIODE-GEN-PURPOSE-1KV-1A(DO-214AC)"))
    )
    (comp (ref "D124")
      (value "1N4007.")
      (footprint "eagle-import:DO-214AC")
      (fields (field (name "MPN") "1N4007"))
      (libsource (lib "eagle-import") (part "DIODE-GEN-PURPOSE-1KV-1A(DO-214AC)"))
    )
    (comp (ref "D125")
      (value "1N5817")
      (footprint "eagle-import:DO-214AC_SLIM")
      (libsource (lib "eagle-import") (part "DIODE-GEN-PURPOSE-1KV-1A(DO-214AC)DO-214AC/1206"))
    )
    (comp (ref "D126")
      (value "1N5817.")
      (footprint "eagle-import:DO-214AC_SLIM")
      (libsource (lib "eagle-import") (part "DIODE-GEN-PURPOSE-1KV-1A(DO-214AC)DO-214AC/1206"))
    )
    (comp (ref "D127")
      (value "1N5817.")
      (footprint "eagle-import:DO-214AC_SLIM")
      (libsource (lib "eagle-import") (part "DIODE-GEN-PURPOSE-1KV-1A(DO-214AC)DO-214AC/1206"))
    )
    (comp (ref "D128")
      (value "1N5817")
      (footprint "eagle-import:DO-214AC_SLIM")
      (libsource (lib "eagle-import") (part "DIODE-GEN-PURPOSE-1KV-1A(DO-214AC)DO-214AC/1206"))
    )
    (comp (ref "D129")
      (value "1N4007.")
      (footprint "eagle-import:DO-214AC")
      (fields (field (name "MPN") "1N4007"))
      (libsource (lib "eagle-import") (part "DIODE-GEN-PURPOSE-1KV-1A(DO-214AC)"))
    )
    (comp (ref "D130")
      (value "1N4007")
      (footprint "eagle-import:DO-214AC")
      (libsource (lib "eagle-import") (part "DIODE-GEN-PURPOSE-1KV-1A(DO-214AC)"))
    )
    (comp (ref "D131")
      (value "SM6T")
      (footprint "eagle-import:DO214AA")
      (libsource (lib "eagle-import") (part "SM6T"))
    )
    (comp (ref "D132")
      (value "SM6TDO214AA_BI")
      (footprint "eagle-import:DO214AA_BI")
      (libsource (lib "eagle-import") (part "SM6TDO214AA_BI"))
    )
    (comp (ref "FID41")
      (value "FIDUCIAL")
      (footprint "eagle-import:FIDUCIAL_1MM")
      (libsource (lib "eagle-import") (part "FIDUCIAL"))
    )
    (comp (ref "FID42")
      (value "FIDUCIAL")
      (footprint "eagle-import:FIDUCIAL_1MM")
      (libsource (lib "eagle-import") (part "FIDUCIAL"))
    )
    (comp (ref "FID43")
      (value "FIDUCIAL")
      (footprint "eagle-import:FIDUCIAL_1MM")
      (libsource (lib "eagle-import") (part "FIDUCIAL"))
    )
    (comp (ref "FID44")
      (value "FIDUCIAL")
      (footprint "eagle-import:FIDUCIAL_1MM")
      (libsource (lib "eagle-import") (part "FIDUCIAL"))
    )
    (comp (ref "IC111")
      (value "4028")
      (footprint "eagle-import:SO16")
      (libsource (lib "eagle-import") (part "4028D"))
    )
    (comp (ref "IC112")
      (value "6V pos")
      (footprint "eagle-import:78LXX")
      (libsource (lib "eagle-import") (part "v-reg_78LXX"))
    )
    (comp (ref "IC113")
      (value "317TO202H_NOHOLE")
      (footprint "eagle-import:TO220H_NOHOLE")
      (libsource (lib "eagle-import") (part "317TO202H_NOHOLE"))
    )
    (comp (ref "IC114")
      (value "ULN2004")
      (footprint "eagle-import:SO16")
      (libsource (lib "eagle-import") (part "ULN2004AD"))
    )
    (comp (ref "IC115")
      (value "LM339")
      (footprint "eagle-import:SO14")
      (libsource (lib "eagle-import") (part "LM339D"))
    )
    (comp (ref "IC116")
      (value "78L06")
      (footprint "eagle-import:SOT89_ROUND")
      (libsource (lib "eagle-import") (part "78LXXSOT89_ROUND"))
    )
    (comp (ref "IC117")
      (value "555")
      (footprint "eagle-import:SO08")
      (libsource (lib "eagle-import") (part "555DNE"))
    )
    (comp (ref "IC118")
      (value "4538")
      (footprint "eagle-import:SO16")
      (libsource (lib "eagle-import") (part "4538D"))
    )
    (comp (ref "IC119")
      (value "78L10")
      (footprint "eagle-import:SOT89_ROUND")
      (libsource (lib "eagle-import") (part "78LXXSOT89_ROUND"))
    )
    (comp (ref "IC120")
      (value "LM2904")
      (footprint "eagle-import:SO08")
      (libsource (lib "eagle-import") (part "LM358D"))
    )
    (comp (ref "IC121")
      (value "NUP4304SOT457_R")
      (footprint "eagle-import:SOT457R_PHILIPS")
      (libsource (lib "eagle-import") (part "NUP4304SOT457_R"))
    )
    (comp (ref "JP51")
      (value "JP2EJP2_SMALLPADS")
      (footprint "eagle-import:JP2_SMALLPADS")
      (libsource (lib "eagle-import") (part "JP2EJP2_SMALLPADS"))
    )
    (comp (ref "JP52")
      (value "JP2E_ORIG")
      (footprint "eagle-import:JP2_ORIG_SMALLPADS")
      (libsource (lib "eagle-import") (part "JP2E_ORIG"))
    )
    (comp (ref "JP53")
      (value "JP2EJP2_SMALLPADS")
      (footprint "eagle-import:JP2_SMALLPADS")
      (libsource (lib "eagle-import") (part "JP2EJP2_SMALLPADS"))
    )
    (comp (ref "JP54")
      (value "JP2EJP2_SMALLPADS")
      (footprint "eagle-import:JP2_SMALLPADS")
      (libsource (lib "eagle-import") (part "JP2EJP2_SMALLPADS"))
    )
    (comp (ref "JP55")
      (value "JP2EJP2_SMALLPADS")
      (footprint "eagle-import:JP2_SMALLPADS")
      (libsource (lib "eagle-import") (part "JP2EJP2_SMALLPADS"))
    )
    (comp (ref "LED61")
      (value "LEDLD260")
      (footprint "eagle-import:LD260")
      (libsource (lib "eagle-import") (part "LEDLD260"))
    )
    (comp (ref "LED62")
      (value "LEDLD260")
      (footprint "eagle-import:LD260")
      (libsource (lib "eagle-import") (part "LEDLD260"))
    )
    (comp (ref "LED63")
      (value "LEDLD260")
      (footprint "eagle-import:LD260")
      (libsource (lib "eagle-import") (part "LEDLD260"))
    )
    (comp (ref "LED64")
      (value "LEDLD260")
      (footprint "eagle-import:LD260")
      (libsource (lib "eagle-import") (part "LEDLD260"))
    )
    (comp (ref "LED65")
      (value "LEDLD260")
      (footprint "eagle-import:LD260")
      (libsource (lib "eagle-import") (part "LEDLD260"))
    )
    (comp (ref "LED66")
      (value "LEDLD260")
      (footprint "eagle-import:LD260")
      (libsource (lib "eagle-import") (part "LEDLD260"))
    )
    (comp (ref "Q71")
      (value "BA")
      (footprint "eagle-import:SOT89")
      (libsource (lib "eagle-import") (part "PNP-TRANSISTOR_SOT89"))
    )
    (comp (ref "Q72")
      (value "BA.")
      (footprint "eagle-import:SOT89")
      (libsource (lib "eagle-import") (part "PNP-TRANSISTOR_SOT89"))
    )
    (comp (ref "Q73")
      (value "BA.")
      (footprint "eagle-import:SOT89")
      (libsource (lib "eagle-import") (part "PNP-TRANSISTOR_SOT89"))
    )
    (comp (ref "Q74")
      (value "BA")
      (footprint "eagle-import:SOT89")
      (libsource (lib "eagle-import") (part "PNP-TRANSISTOR_SOT89"))
    )
    (comp (ref "Q75")
      (value "MY")
      (footprint "eagle-import:SOT89")
      (libsource (lib "eagle-import") (part "NPN-TRANSISTOR_SOT89"))
    )
    (comp (ref "Q76")
      (value "J1")
      (footprint "eagle-import:SOT-23")
      (fields (field (name "MPN") "BSS138W-7-F"))
      (libsource (lib "eagle-import") (part "SMD-MOSFET-N-CH-50V-200MA-BSS138W-7-F(SOT-23)"))
    )
    (comp (ref "Q77")
      (value "J1")
      (footprint "eagle-import:SOT-23")
      (fields (field (name "MPN") "BSS138W-7-F"))
      (libsource (lib "eagle-import") (part "SMD-MOSFET-N-CH-50V-200MA-BSS138W-7-F(SOT-23)"))
    )
    (comp (ref "R461")
      (value "47")
      (footprint "eagle-import:V235_17_1MM")
      (libsource (lib "eagle-import") (part "R-EU_V235/17_1MM"))
    )
    (comp (ref "R462")
      (value "13")
      (footprint "eagle-import:R1206")
      (fields (field (name "MPN") "RC1206JR-0713RL"))
      (libsource (lib "eagle-import") (part "SMD-RES-13R-5%-1/4W(1206)"))
    )
    (comp (ref "R463")
      (value "47")
      (footprint "eagle-import:V235_17_1MM")
      (libsource (lib "eagle-import") (part "R-EU_V235/17_1MM"))
    )
    (comp (ref "R464")
      (value "104")
      (footprint "eagle-import:R0805")
      (fields (field (name "MPN") "RC0805FR-0710KL"))
      (libsource (lib "eagle-import") (part "SMD-RES-10K-1%-1/8W(0805)"))
    )
    (comp (ref "R465")
      (value "104")
      (footprint "eagle-import:R0805")
      (fields (field (name "MPN") "RC0805FR-0710KL"))
      (libsource (lib "eagle-import") (part "SMD-RES-10K-1%-1/8W(0805)"))
    )
    (comp (ref "R466")
      (value "104")
      (footprint "eagle-import:R0805")
      (fields (field (name "MPN") "RC0805FR-0710KL"))
      (libsource (lib "eagle-import") (part "SMD-RES-10K-1%-1/8W(0805)"))
    )
    (comp (ref "R467")
      (value "4701")
      (footprint "eagle-import:R0805")
      (fields (field (name "MPN") "RC0805JR-074K7L"))
      (libsource (lib "eagle-import") (part "SMD-RES-4.7K-5%-1/8W(0805)"))
    )
    (comp (ref "R468")
      (value "1002")
      (footprint "eagle-import:R0805")
      (fields (field (name "MPN") "RC0805FR-0710KL"))
      (libsource (lib "eagle-import") (part "SMD-RES-10K-1%-1/8W(0805)"))
    )
    (comp (ref "R469")
      (value "1002")
      (footprint "eagle-import:R0805")
      (fields (field (name "MPN") "RC0805FR-0710KL"))
      (libsource (lib "eagle-import") (part "SMD-RES-10K-1%-1/8W(0805)"))
    )
    (comp (ref "R470")
      (value "1502")
      (footprint "eagle-import:R0805")
      (fields (field (name "MPN") "RC0805FR-0710KL"))
      (libsource (lib "eagle-import") (part "SMD-RES-10K-1%-1/8W(0805)"))
    )
    (comp (ref "R471")
      (value "104")
      (footprint "eagle-import:R0805")
      (fields (field (name "MPN") "RC0805FR-0710KL"))
      (libsource (lib "eagle-import") (part "SMD-RES-10K-1%-1/8W(0805)"))
    )
    (comp (ref "R472")
      (value "104")
      (footprint "eagle-import:R0805")
      (fields (field (name "MPN") "RC0805FR-0710KL"))
      (libsource (lib "eagle-import") (part "SMD-RES-10K-1%-1/8W(0805)"))
    )
    (comp (ref "R473")
      (value "1502")
      (footprint "eagle-import:R0805")
      (fields (field (name "MPN") "RC0805FR-0710KL"))
      (libsource (lib "eagle-import") (part "SMD-RES-10K-1%-1/8W(0805)"))
    )
    (comp (ref "R474")
      (value "1002")
      (footprint "eagle-import:R0805")
      (fields (field (name "MPN") "RC0805FR-0710KL"))
      (libsource (lib "eagle-import") (part "SMD-RES-10K-1%-1/8W(0805)"))
    )
    (comp (ref "R475")
      (value "2201")
      (footprint "eagle-import:R0805")
      (fields (field (name "MPN") "RC0805JR-072K2L"))
      (libsource (lib "eagle-import") (part "SMD-RES-2.2K-5%-1/8W(0805)"))
    )
    (comp (ref "R476")
      (value "1002")
      (footprint "eagle-import:R0805")
      (fields (field (name "MPN") "RC0805FR-0710KL"))
      (libsource (lib "eagle-import") (part "SMD-RES-10K-1%-1/8W(0805)"))
    )
    (comp (ref "R477")
      (value "4701")
      (footprint "eagle-import:R0805")
      (fields (field (name "MPN") "RC0805JR-074K7L"))
      (libsource (lib "eagle-import") (part "SMD-RES-4.7K-5%-1/8W(0805)"))
    )
    (comp (ref "R478")
      (value "2702")
      (footprint "eagle-import:R0805")
      (fields (field (name "MPN") "RC0805JR-074K7L"))
      (libsource (lib "eagle-import") (part "SMD-RES-4.7K-5%-1/8W(0805)"))
    )
    (comp (ref "R479")
      (value "102")
      (footprint "eagle-import:R0805")
      (fields (field (name "MPN") "RC0805JR-071KL"))
      (libsource (lib "eagle-import") (part "SMD-RES-1K-5%-1/8W(0805)"))
    )
    (comp (ref "R480")
      (value "R_user")
      (footprint "eagle-import:R0805")
      (libsource (lib "eagle-import") (part "R-EU_R0805"))
    )
    (comp (ref "R481")
      (value "100")
      (footprint "eagle-import:R0805")
      (fields (field (name "MPN") "RC0805JR-07220RL"))
      (libsource (lib "eagle-import") (part "SMD-RES-220R-5%-1/8W(0805)"))
    )
    (comp (ref "R482")
      (value "(101)")
      (footprint "eagle-import:R0805")
      (fields (field (name "MPN") "RC0805JR-07100RL"))
      (libsource (lib "eagle-import") (part "SMD-RES-100R-5%-1/8W(0805)"))
    )
    (comp (ref "R483")
      (value "(1000)")
      (footprint "eagle-import:R0805")
      (fields (field (name "MPN") "RC0805JR-07100RL"))
      (libsource (lib "eagle-import") (part "SMD-RES-100R-5%-1/8W(0805)"))
    )
    (comp (ref "R484")
      (value "102")
      (footprint "eagle-import:R0805")
      (fields (field (name "MPN") "RC0805JR-071KL"))
      (libsource (lib "eagle-import") (part "SMD-RES-1K-5%-1/8W(0805)"))
    )
    (comp (ref "R485")
      (value "13")
      (footprint "eagle-import:R1206")
      (fields (field (name "MPN") "RC1206JR-0713RL"))
      (libsource (lib "eagle-import") (part "SMD-RES-13R-5%-1/4W(1206)"))
    )
    (comp (ref "R486")
      (value "13")
      (footprint "eagle-import:R1206")
      (fields (field (name "MPN") "RC1206JR-0713RL"))
      (libsource (lib "eagle-import") (part "SMD-RES-13R-5%-1/4W(1206)"))
    )
    (comp (ref "R487")
      (value "2702")
      (footprint "eagle-import:R0805")
      (fields (field (name "MPN") "RC0805JR-074K7L"))
      (libsource (lib "eagle-import") (part "SMD-RES-4.7K-5%-1/8W(0805)"))
    )
    (comp (ref "R488")
      (value "4701")
      (footprint "eagle-import:R0805")
      (fields (field (name "MPN") "RC0805JR-074K7L"))
      (libsource (lib "eagle-import") (part "SMD-RES-4.7K-5%-1/8W(0805)"))
    )
    (comp (ref "R489")
      (value "100")
      (footprint "eagle-import:R0805")
      (fields (field (name "MPN") "RC0805JR-072K2L"))
      (libsource (lib "eagle-import") (part "SMD-RES-2.2K-5%-1/8W(0805)"))
    )
    (comp (ref "R490")
      (value "(101)")
      (footprint "eagle-import:R0805")
      (fields (field (name "MPN") "RC0805JR-072K2L"))
      (libsource (lib "eagle-import") (part "SMD-RES-2.2K-5%-1/8W(0805)"))
    )
    (comp (ref "R491")
      (value "104")
      (footprint "eagle-import:R0805")
      (fields (field (name "MPN") "RC0805FR-0710KL"))
      (libsource (lib "eagle-import") (part "SMD-RES-10K-1%-1/8W(0805)"))
    )
    (comp (ref "R492")
      (value "104")
      (footprint "eagle-import:R0805")
      (fields (field (name "MPN") "RC0805FR-0710KL"))
      (libsource (lib "eagle-import") (part "SMD-RES-10K-1%-1/8W(0805)"))
    )
    (comp (ref "R493")
      (value "(1002)")
      (footprint "eagle-import:R0805")
      (fields (field (name "MPN") "RC0805FR-0710KL"))
      (libsource (lib "eagle-import") (part "SMD-RES-10K-1%-1/8W(0805)"))
    )
    (comp (ref "R494")
      (value "2702")
      (footprint "eagle-import:R0805")
      (fields (field (name "MPN") "RC0805FR-0710KL"))
      (libsource (lib "eagle-import") (part "SMD-RES-10K-1%-1/8W(0805)"))
    )
    (comp (ref "R495")
      (value "47")
      (footprint "eagle-import:V235_17_1MM")
      (libsource (lib "eagle-import") (part "R-EU_V235/17_1MM"))
    )
    (comp (ref "R496")
      (value "47")
      (footprint "eagle-import:V235_17_1MM")
      (libsource (lib "eagle-import") (part "R-EU_V235/17_1MM"))
    )
    (comp (ref "R497")
      (value "2702")
      (footprint "eagle-import:R0805")
      (fields (field (name "MPN") "RC0805JR-074K7L"))
      (libsource (lib "eagle-import") (part "SMD-RES-4.7K-5%-1/8W(0805)"))
    )
    (comp (ref "R498")
      (value "2201")
      (footprint "eagle-import:R0805")
      (fields (field (name "MPN") "RC0805JR-072K2L"))
      (libsource (lib "eagle-import") (part "SMD-RES-2.2K-5%-1/8W(0805)"))
    )
    (comp (ref "R499")
      (value "(1002)")
      (footprint "eagle-import:R0805")
      (fields (field (name "MPN") "RC0805JR-074K7L"))
      (libsource (lib "eagle-import") (part "SMD-RES-4.7K-5%-1/8W(0805)"))
    )
    (comp (ref "R500")
      (value "1002")
      (footprint "eagle-import:R0805")
      (fields (field (name "MPN") "RC0805FR-0710KL"))
      (libsource (lib "eagle-import") (part "SMD-RES-10K-1%-1/8W(0805)"))
    )
    (comp (ref "R501")
      (value "102")
      (footprint "eagle-import:R0805")
      (fields (field (name "MPN") "RC0805JR-071KL"))
      (libsource (lib "eagle-import") (part "SMD-RES-1K-5%-1/8W(0805)"))
    )
    (comp (ref "R502")
      (value "2702")
      (footprint "eagle-import:R0805")
      (fields (field (name "MPN") "RC0805JR-074K7L"))
      (libsource (lib "eagle-import") (part "SMD-RES-4.7K-5%-1/8W(0805)"))
    )
    (comp (ref "R503")
      (value "102")
      (footprint "eagle-import:R0805")
      (fields (field (name "MPN") "RC0805JR-071KL"))
      (libsource (lib "eagle-import") (part "SMD-RES-1K-5%-1/8W(0805)"))
    )
    (comp (ref "R504")
      (value "102")
      (footprint "eagle-import:R0805")
      (fields (field (name "MPN") "RC0805JR-071KL"))
      (libsource (lib "eagle-import") (part "SMD-RES-1K-5%-1/8W(0805)"))
    )
    (comp (ref "R505")
      (value "13")
      (footprint "eagle-import:R1206")
      (fields (field (name "MPN") "RC1206JR-0713RL"))
      (libsource (lib "eagle-import") (part "SMD-RES-13R-5%-1/4W(1206)"))
    )
    (comp (ref "R506")
      (value "R_user")
      (footprint "eagle-import:R0805")
      (libsource (lib "eagle-import") (part "R-EU_R0805"))
    )
    (comp (ref "SJ11")
      (value "SJ")
      (footprint "eagle-import:SJ")
      (libsource (lib "eagle-import") (part "SJ"))
    )
    (comp (ref "START10")
      (value "TPSB2.0")
      (footprint "eagle-import:B2.0")
      (libsource (lib "eagle-import") (part "TPSB2.0"))
    )
    (comp (ref "TP231")
      (value "TPSB2.0")
      (footprint "eagle-import:B2.0")
      (libsource (lib "eagle-import") (part "TPSB2.0"))
    )
    (comp (ref "TP232")
      (value "TPSB2.0")
      (footprint "eagle-import:B2.0")
      (libsource (lib "eagle-import") (part "TPSB2.0"))
    )
    (comp (ref "TP233")
      (value "TPSB2.0")
      (footprint "eagle-import:B2.0")
      (libsource (lib "eagle-import") (part "TPSB2.0"))
    )
    (comp (ref "TP234")
      (value "TPSB2.0")
      (footprint "eagle-import:B2.0")
      (libsource (lib "eagle-import") (part "TPSB2.0"))
    )
    (comp (ref "TP235")
      (value "TPSB2.0")
      (footprint "eagle-import:B2.0")
      (libsource (lib "eagle-import") (part "TPSB2.0"))
    )
    (comp (ref "TP236")
      (value "TPSB2.0")
      (footprint "eagle-import:B2.0")
      (libsource (lib "eagle-import") (part "TPSB2.0"))
    )
    (comp (ref "TP237")
      (value "TPSB2.0")
      (footprint "eagle-import:B2.0")
      (libsource (lib "eagle-import") (part "TPSB2.0"))
    )
    (comp (ref "TP238")
      (value "TPSB2.0")
      (footprint "eagle-import:B2.0")
      (libsource (lib "eagle-import") (part "TPSB2.0"))
    )
    (comp (ref "TP239")
      (value "TPSB2.0")
      (footprint "eagle-import:B2.0")
      (libsource (lib "eagle-import") (part "TPSB2.0"))
    )
    (comp (ref "TP240")
      (value "TPSB2.0")
      (footprint "eagle-import:B2.0")
      (libsource (lib "eagle-import") (part "TPSB2.0"))
    )
    (comp (ref "TP241")
      (value "TPSB2.0")
      (footprint "eagle-import:B2.0")
      (libsource (lib "eagle-import") (part "TPSB2.0"))
    )
    (comp (ref "TP242")
      (value "TPSB2.0")
      (footprint "eagle-import:B2.0")
      (libsource (lib "eagle-import") (part "TPSB2.0"))
    )
    (comp (ref "TP243")
      (value "TPSB2.0")
      (footprint "eagle-import:B2.0")
      (libsource (lib "eagle-import") (part "TPSB2.0"))
    )
    (comp (ref "TP244")
      (value "TPSB2.0")
      (footprint "eagle-import:B2.0")
      (libsource (lib "eagle-import") (part "TPSB2.0"))
    )
    (comp (ref "TP245")
      (value "TPSB2.0")
      (footprint "eagle-import:B2.0")
      (libsource (lib "eagle-import") (part "TPSB2.0"))
    )
    (comp (ref "TP246")
      (value "TPSB2.0")
      (footprint "eagle-import:B2.0")
      (libsource (lib "eagle-import") (part "TPSB2.0"))
    )
    (comp (ref "TP247")
      (value "TPSB2.0")
      (footprint "eagle-import:B2.0")
      (libsource (lib "eagle-import") (part "TPSB2.0"))
    )
    (comp (ref "TP248")
      (value "TPSB2.0")
      (footprint "eagle-import:B2.0")
      (libsource (lib "eagle-import") (part "TPSB2.0"))
    )
    (comp (ref "TP249")
      (value "TPSB1,27")
      (footprint "eagle-import:B1,27")
      (libsource (lib "eagle-import") (part "TPSB1,27"))
    )
    (comp (ref "TP250")
      (value "TPSB2.0")
      (footprint "eagle-import:B2.0")
      (libsource (lib "eagle-import") (part "TPSB2.0"))
    )
    (comp (ref "TP251")
      (value "TPSB2.0")
      (footprint "eagle-import:B2.0")
      (libsource (lib "eagle-import") (part "TPSB2.0"))
    )
    (comp (ref "TP252")
      (value "TPSB2.0")
      (footprint "eagle-import:B2.0")
      (libsource (lib "eagle-import") (part "TPSB2.0"))
    )
    (comp (ref "TP253")
      (value "TPSB2.0")
      (footprint "eagle-import:B2.0")
      (libsource (lib "eagle-import") (part "TPSB2.0"))
    )
    (comp (ref "X31")
      (value "CON_BMWV2")
      (footprint "eagle-import:24-PIN_V2")
      (libsource (lib "eagle-import") (part "CON_BMWV2"))
    )
    (comp (ref "X32")
      (value "22-23-2051")
      (footprint "eagle-import:22-23-2051")
      (fields (field (name "MF") "MOLEX"))
      (libsource (lib "eagle-import") (part "22-23-2051"))
    )
    (comp (ref "X33")
      (value "22-23-2021")
      (footprint "eagle-import:22-23-2021")
      (fields (field (name "MF") "MOLEX"))
      (libsource (lib "eagle-import") (part "22-23-2021"))
    )
    (comp (ref "6V4")
      (value "TPSB2.0")
      (footprint "eagle-import:B2.0")
      (libsource (lib "eagle-import") (part "TPSB2.0"))
    )
    (comp (ref "9")
      (value "2081-1132")
      (footprint "eagle-import:12-PIN")
      (libsource (lib "eagle-import") (part "2081-1132"))
    )
    (comp (ref "10")
      (value "2081-1132")
      (footprint "eagle-import:12-PIN")
      (libsource (lib "eagle-import") (part "2081-1132"))
    )
    (comp (ref "10V4")
      (value "TPSB2.0")
      (footprint "eagle-import:B2.0")
      (libsource (lib "eagle-import") (part "TPSB2.0"))
    )
    (comp (ref "C41")
      (value "100u")
      (footprint "eagle-import:C1206")
      (fields (field (name "MPN") "GRM31CR60J107ME39L"))
      (libsource (lib "eagle-import") (part "CERAMIC-100UF-6.3V-20%-X5R(1206)"))
    )
    (comp (ref "C42")
      (value "100u")
      (footprint "eagle-import:C1206")
      (fields (field (name "MPN") "GRM31CR60J107ME39L"))
      (libsource (lib "eagle-import") (part "CERAMIC-100UF-6.3V-20%-X5R(1206)"))
    )
    (comp (ref "C43")
      (value "100nF,")
      (footprint "eagle-import:C0805")
      (fields (field (name "MPN") "CC0805KRX7R9BB104"))
      (libsource (lib "eagle-import") (part "CERAMIC-100NF-50V-10%-X7R(0805)"))
    )
    (comp (ref "C44")
      (value "4.7u")
      (footprint "eagle-import:C0805")
      (fields (field (name "MPN") "CC0805KKX5R8BB475"))
      (libsource (lib "eagle-import") (part "CERAMIC-4.7UF-25V-10%-X5R(0805)"))
    )
    (comp (ref "C45")
      (value "100nF.")
      (footprint "eagle-import:C0805")
      (fields (field (name "MPN") "CC0805KRX7R9BB104"))
      (libsource (lib "eagle-import") (part "CERAMIC-100NF-50V-10%-X7R(0805)"))
    )
    (comp (ref "C46")
      (value "100nF.")
      (footprint "eagle-import:C0805")
      (fields (field (name "MPN") "CC0805KRX7R9BB104"))
      (libsource (lib "eagle-import") (part "CERAMIC-100NF-50V-10%-X7R(0805)"))
    )
    (comp (ref "C47")
      (value "2.2nF")
      (footprint "eagle-import:C0805")
      (fields (field (name "MPN") "CC0805KRX7R9BB104"))
      (libsource (lib "eagle-import") (part "CERAMIC-100NF-50V-10%-X7R(0805)"))
    )
    (comp (ref "C48")
      (value "100nF")
      (footprint "eagle-import:C0805")
      (fields (field (name "MPN") "CC0805KRX7R9BB104"))
      (libsource (lib "eagle-import") (part "CERAMIC-100NF-50V-10%-X7R(0805)"))
    )
    (comp (ref "C49")
      (value "100nF")
      (footprint "eagle-import:C0805")
      (fields (field (name "MPN") "CC0805KRX7R9BB104"))
      (libsource (lib "eagle-import") (part "CERAMIC-100NF-50V-10%-X7R(0805)"))
    )
    (comp (ref "C50")
      (value "100nF,")
      (footprint "eagle-import:C0805")
      (fields (field (name "MPN") "CC0805KRX7R9BB104"))
      (libsource (lib "eagle-import") (part "CERAMIC-100NF-50V-10%-X7R(0805)"))
    )
    (comp (ref "D49")
      (value "1N4007")
      (footprint "eagle-import:DO-214AC")
      (libsource (lib "eagle-import") (part "DIODE-GEN-PURPOSE-1KV-1A(DO-214AC)"))
    )
    (comp (ref "D50")
      (value "1N4007,")
      (footprint "eagle-import:DO-214AC")
      (fields (field (name "MPN") "1N4007"))
      (libsource (lib "eagle-import") (part "DIODE-GEN-PURPOSE-1KV-1A(DO-214AC)"))
    )
    (comp (ref "D51")
      (value "1N4007,")
      (footprint "eagle-import:DO-214AC")
      (fields (field (name "MPN") "1N4007"))
      (libsource (lib "eagle-import") (part "DIODE-GEN-PURPOSE-1KV-1A(DO-214AC)"))
    )
    (comp (ref "D52")
      (value "1N4007.")
      (footprint "eagle-import:DO-214AC")
      (fields (field (name "MPN") "1N4007"))
      (libsource (lib "eagle-import") (part "DIODE-GEN-PURPOSE-1KV-1A(DO-214AC)"))
    )
    (comp (ref "D53")
      (value "1N5817")
      (footprint "eagle-import:DO-214AC_SLIM")
      (libsource (lib "eagle-import") (part "DIODE-GEN-PURPOSE-1KV-1A(DO-214AC)DO-214AC/1206"))
    )
    (comp (ref "D54")
      (value "1N5817.")
      (footprint "eagle-import:DO-214AC_SLIM")
      (libsource (lib "eagle-import") (part "DIODE-GEN-PURPOSE-1KV-1A(DO-214AC)DO-214AC/1206"))
    )
    (comp (ref "D55")
      (value "1N5817.")
      (footprint "eagle-import:DO-214AC_SLIM")
      (libsource (lib "eagle-import") (part "DIODE-GEN-PURPOSE-1KV-1A(DO-214AC)DO-214AC/1206"))
    )
    (comp (ref "D56")
      (value "1N5817")
      (footprint "eagle-import:DO-214AC_SLIM")
      (libsource (lib "eagle-import") (part "DIODE-GEN-PURPOSE-1KV-1A(DO-214AC)DO-214AC/1206"))
    )
    (comp (ref "D57")
      (value "1N4007.")
      (footprint "eagle-import:DO-214AC")
      (fields (field (name "MPN") "1N4007"))
      (libsource (lib "eagle-import") (part "DIODE-GEN-PURPOSE-1KV-1A(DO-214AC)"))
    )
    (comp (ref "D58")
      (value "1N4007")
      (footprint "eagle-import:DO-214AC")
      (libsource (lib "eagle-import") (part "DIODE-GEN-PURPOSE-1KV-1A(DO-214AC)"))
    )
    (comp (ref "D59")
      (value "SM6T")
      (footprint "eagle-import:DO214AA")
      (libsource (lib "eagle-import") (part "SM6T"))
    )
    (comp (ref "D60")
      (value "SM6TDO214AA_BI")
      (footprint "eagle-import:DO214AA_BI")
      (libsource (lib "eagle-import") (part "SM6TDO214AA_BI"))
    )
    (comp (ref "FID17")
      (value "FIDUCIAL")
      (footprint "eagle-import:FIDUCIAL_1MM")
      (libsource (lib "eagle-import") (part "FIDUCIAL"))
    )
    (comp (ref "FID18")
      (value "FIDUCIAL")
      (footprint "eagle-import:FIDUCIAL_1MM")
      (libsource (lib "eagle-import") (part "FIDUCIAL"))
    )
    (comp (ref "FID19")
      (value "FIDUCIAL")
      (footprint "eagle-import:FIDUCIAL_1MM")
      (libsource (lib "eagle-import") (part "FIDUCIAL"))
    )
    (comp (ref "FID20")
      (value "FIDUCIAL")
      (footprint "eagle-import:FIDUCIAL_1MM")
      (libsource (lib "eagle-import") (part "FIDUCIAL"))
    )
    (comp (ref "IC45")
      (value "4028")
      (footprint "eagle-import:SO16")
      (libsource (lib "eagle-import") (part "4028D"))
    )
    (comp (ref "IC46")
      (value "6V pos")
      (footprint "eagle-import:78LXX")
      (libsource (lib "eagle-import") (part "v-reg_78LXX"))
    )
    (comp (ref "IC47")
      (value "317TO202H_NOHOLE")
      (footprint "eagle-import:TO220H_NOHOLE")
      (libsource (lib "eagle-import") (part "317TO202H_NOHOLE"))
    )
    (comp (ref "IC48")
      (value "ULN2004")
      (footprint "eagle-import:SO16")
      (libsource (lib "eagle-import") (part "ULN2004AD"))
    )
    (comp (ref "IC49")
      (value "LM339")
      (footprint "eagle-import:SO14")
      (libsource (lib "eagle-import") (part "LM339D"))
    )
    (comp (ref "IC50")
      (value "78L06")
      (footprint "eagle-import:SOT89_ROUND")
      (libsource (lib "eagle-import") (part "78LXXSOT89_ROUND"))
    )
    (comp (ref "IC51")
      (value "555")
      (footprint "eagle-import:SO08")
      (libsource (lib "eagle-import") (part "555DNE"))
    )
    (comp (ref "IC52")
      (value "4538")
      (footprint "eagle-import:SO16")
      (libsource (lib "eagle-import") (part "4538D"))
    )
    (comp (ref "IC53")
      (value "78L10")
      (footprint "eagle-import:SOT89_ROUND")
      (libsource (lib "eagle-import") (part "78LXXSOT89_ROUND"))
    )
    (comp (ref "IC54")
      (value "LM2904")
      (footprint "eagle-import:SO08")
      (libsource (lib "eagle-import") (part "LM358D"))
    )
    (comp (ref "IC55")
      (value "NUP4304SOT457_R")
      (footprint "eagle-import:SOT457R_PHILIPS")
      (libsource (lib "eagle-import") (part "NUP4304SOT457_R"))
    )
    (comp (ref "JP21")
      (value "JP2EJP2_SMALLPADS")
      (footprint "eagle-import:JP2_SMALLPADS")
      (libsource (lib "eagle-import") (part "JP2EJP2_SMALLPADS"))
    )
    (comp (ref "JP22")
      (value "JP2E_ORIG")
      (footprint "eagle-import:JP2_ORIG_SMALLPADS")
      (libsource (lib "eagle-import") (part "JP2E_ORIG"))
    )
    (comp (ref "JP23")
      (value "JP2EJP2_SMALLPADS")
      (footprint "eagle-import:JP2_SMALLPADS")
      (libsource (lib "eagle-import") (part "JP2EJP2_SMALLPADS"))
    )
    (comp (ref "JP24")
      (value "JP2EJP2_SMALLPADS")
      (footprint "eagle-import:JP2_SMALLPADS")
      (libsource (lib "eagle-import") (part "JP2EJP2_SMALLPADS"))
    )
    (comp (ref "JP25")
      (value "JP2EJP2_SMALLPADS")
      (footprint "eagle-import:JP2_SMALLPADS")
      (libsource (lib "eagle-import") (part "JP2EJP2_SMALLPADS"))
    )
    (comp (ref "LED25")
      (value "LEDLD260")
      (footprint "eagle-import:LD260")
      (libsource (lib "eagle-import") (part "LEDLD260"))
    )
    (comp (ref "LED26")
      (value "LEDLD260")
      (footprint "eagle-import:LD260")
      (libsource (lib "eagle-import") (part "LEDLD260"))
    )
    (comp (ref "LED27")
      (value "LEDLD260")
      (footprint "eagle-import:LD260")
      (libsource (lib "eagle-import") (part "LEDLD260"))
    )
    (comp (ref "LED28")
      (value "LEDLD260")
      (footprint "eagle-import:LD260")
      (libsource (lib "eagle-import") (part "LEDLD260"))
    )
    (comp (ref "LED29")
      (value "LEDLD260")
      (footprint "eagle-import:LD260")
      (libsource (lib "eagle-import") (part "LEDLD260"))
    )
    (comp (ref "LED30")
      (value "LEDLD260")
      (footprint "eagle-import:LD260")
      (libsource (lib "eagle-import") (part "LEDLD260"))
    )
    (comp (ref "Q29")
      (value "BA")
      (footprint "eagle-import:SOT89")
      (libsource (lib "eagle-import") (part "PNP-TRANSISTOR_SOT89"))
    )
    (comp (ref "Q30")
      (value "BA.")
      (footprint "eagle-import:SOT89")
      (libsource (lib "eagle-import") (part "PNP-TRANSISTOR_SOT89"))
    )
    (comp (ref "Q31")
      (value "BA.")
      (footprint "eagle-import:SOT89")
      (libsource (lib "eagle-import") (part "PNP-TRANSISTOR_SOT89"))
    )
    (comp (ref "Q32")
      (value "BA")
      (footprint "eagle-import:SOT89")
      (libsource (lib "eagle-import") (part "PNP-TRANSISTOR_SOT89"))
    )
    (comp (ref "Q33")
      (value "MY")
      (footprint "eagle-import:SOT89")
      (libsource (lib "eagle-import") (part "NPN-TRANSISTOR_SOT89"))
    )
    (comp (ref "Q34")
      (value "J1")
      (footprint "eagle-import:SOT-23")
      (fields (field (name "MPN") "BSS138W-7-F"))
      (libsource (lib "eagle-import") (part "SMD-MOSFET-N-CH-50V-200MA-BSS138W-7-F(SOT-23)"))
    )
    (comp (ref "Q35")
      (value "J1")
      (footprint "eagle-import:SOT-23")
      (fields (field (name "MPN") "BSS138W-7-F"))
      (libsource (lib "eagle-import") (part "SMD-MOSFET-N-CH-50V-200MA-BSS138W-7-F(SOT-23)"))
    )
    (comp (ref "R185")
      (value "47")
      (footprint "eagle-import:V235_17_1MM")
      (libsource (lib "eagle-import") (part "R-EU_V235/17_1MM"))
    )
    (comp (ref "R186")
      (value "13")
      (footprint "eagle-import:R1206")
      (fields (field (name "MPN") "RC1206JR-0713RL"))
      (libsource (lib "eagle-import") (part "SMD-RES-13R-5%-1/4W(1206)"))
    )
    (comp (ref "R187")
      (value "47")
      (footprint "eagle-import:V235_17_1MM")
      (libsource (lib "eagle-import") (part "R-EU_V235/17_1MM"))
    )
    (comp (ref "R188")
      (value "104")
      (footprint "eagle-import:R0805")
      (fields (field (name "MPN") "RC0805FR-0710KL"))
      (libsource (lib "eagle-import") (part "SMD-RES-10K-1%-1/8W(0805)"))
    )
    (comp (ref "R189")
      (value "104")
      (footprint "eagle-import:R0805")
      (fields (field (name "MPN") "RC0805FR-0710KL"))
      (libsource (lib "eagle-import") (part "SMD-RES-10K-1%-1/8W(0805)"))
    )
    (comp (ref "R190")
      (value "104")
      (footprint "eagle-import:R0805")
      (fields (field (name "MPN") "RC0805FR-0710KL"))
      (libsource (lib "eagle-import") (part "SMD-RES-10K-1%-1/8W(0805)"))
    )
    (comp (ref "R191")
      (value "4701")
      (footprint "eagle-import:R0805")
      (fields (field (name "MPN") "RC0805JR-074K7L"))
      (libsource (lib "eagle-import") (part "SMD-RES-4.7K-5%-1/8W(0805)"))
    )
    (comp (ref "R192")
      (value "1002")
      (footprint "eagle-import:R0805")
      (fields (field (name "MPN") "RC0805FR-0710KL"))
      (libsource (lib "eagle-import") (part "SMD-RES-10K-1%-1/8W(0805)"))
    )
    (comp (ref "R193")
      (value "1002")
      (footprint "eagle-import:R0805")
      (fields (field (name "MPN") "RC0805FR-0710KL"))
      (libsource (lib "eagle-import") (part "SMD-RES-10K-1%-1/8W(0805)"))
    )
    (comp (ref "R194")
      (value "1502")
      (footprint "eagle-import:R0805")
      (fields (field (name "MPN") "RC0805FR-0710KL"))
      (libsource (lib "eagle-import") (part "SMD-RES-10K-1%-1/8W(0805)"))
    )
    (comp (ref "R195")
      (value "104")
      (footprint "eagle-import:R0805")
      (fields (field (name "MPN") "RC0805FR-0710KL"))
      (libsource (lib "eagle-import") (part "SMD-RES-10K-1%-1/8W(0805)"))
    )
    (comp (ref "R196")
      (value "104")
      (footprint "eagle-import:R0805")
      (fields (field (name "MPN") "RC0805FR-0710KL"))
      (libsource (lib "eagle-import") (part "SMD-RES-10K-1%-1/8W(0805)"))
    )
    (comp (ref "R197")
      (value "1502")
      (footprint "eagle-import:R0805")
      (fields (field (name "MPN") "RC0805FR-0710KL"))
      (libsource (lib "eagle-import") (part "SMD-RES-10K-1%-1/8W(0805)"))
    )
    (comp (ref "R198")
      (value "1002")
      (footprint "eagle-import:R0805")
      (fields (field (name "MPN") "RC0805FR-0710KL"))
      (libsource (lib "eagle-import") (part "SMD-RES-10K-1%-1/8W(0805)"))
    )
    (comp (ref "R199")
      (value "2201")
      (footprint "eagle-import:R0805")
      (fields (field (name "MPN") "RC0805JR-072K2L"))
      (libsource (lib "eagle-import") (part "SMD-RES-2.2K-5%-1/8W(0805)"))
    )
    (comp (ref "R200")
      (value "1002")
      (footprint "eagle-import:R0805")
      (fields (field (name "MPN") "RC0805FR-0710KL"))
      (libsource (lib "eagle-import") (part "SMD-RES-10K-1%-1/8W(0805)"))
    )
    (comp (ref "R201")
      (value "4701")
      (footprint "eagle-import:R0805")
      (fields (field (name "MPN") "RC0805JR-074K7L"))
      (libsource (lib "eagle-import") (part "SMD-RES-4.7K-5%-1/8W(0805)"))
    )
    (comp (ref "R202")
      (value "2702")
      (footprint "eagle-import:R0805")
      (fields (field (name "MPN") "RC0805JR-074K7L"))
      (libsource (lib "eagle-import") (part "SMD-RES-4.7K-5%-1/8W(0805)"))
    )
    (comp (ref "R203")
      (value "102")
      (footprint "eagle-import:R0805")
      (fields (field (name "MPN") "RC0805JR-071KL"))
      (libsource (lib "eagle-import") (part "SMD-RES-1K-5%-1/8W(0805)"))
    )
    (comp (ref "R204")
      (value "R_user")
      (footprint "eagle-import:R0805")
      (libsource (lib "eagle-import") (part "R-EU_R0805"))
    )
    (comp (ref "R205")
      (value "100")
      (footprint "eagle-import:R0805")
      (fields (field (name "MPN") "RC0805JR-07220RL"))
      (libsource (lib "eagle-import") (part "SMD-RES-220R-5%-1/8W(0805)"))
    )
    (comp (ref "R206")
      (value "(101)")
      (footprint "eagle-import:R0805")
      (fields (field (name "MPN") "RC0805JR-07100RL"))
      (libsource (lib "eagle-import") (part "SMD-RES-100R-5%-1/8W(0805)"))
    )
    (comp (ref "R207")
      (value "(1000)")
      (footprint "eagle-import:R0805")
      (fields (field (name "MPN") "RC0805JR-07100RL"))
      (libsource (lib "eagle-import") (part "SMD-RES-100R-5%-1/8W(0805)"))
    )
    (comp (ref "R208")
      (value "102")
      (footprint "eagle-import:R0805")
      (fields (field (name "MPN") "RC0805JR-071KL"))
      (libsource (lib "eagle-import") (part "SMD-RES-1K-5%-1/8W(0805)"))
    )
    (comp (ref "R209")
      (value "13")
      (footprint "eagle-import:R1206")
      (fields (field (name "MPN") "RC1206JR-0713RL"))
      (libsource (lib "eagle-import") (part "SMD-RES-13R-5%-1/4W(1206)"))
    )
    (comp (ref "R210")
      (value "13")
      (footprint "eagle-import:R1206")
      (fields (field (name "MPN") "RC1206JR-0713RL"))
      (libsource (lib "eagle-import") (part "SMD-RES-13R-5%-1/4W(1206)"))
    )
    (comp (ref "R211")
      (value "2702")
      (footprint "eagle-import:R0805")
      (fields (field (name "MPN") "RC0805JR-074K7L"))
      (libsource (lib "eagle-import") (part "SMD-RES-4.7K-5%-1/8W(0805)"))
    )
    (comp (ref "R212")
      (value "4701")
      (footprint "eagle-import:R0805")
      (fields (field (name "MPN") "RC0805JR-074K7L"))
      (libsource (lib "eagle-import") (part "SMD-RES-4.7K-5%-1/8W(0805)"))
    )
    (comp (ref "R213")
      (value "100")
      (footprint "eagle-import:R0805")
      (fields (field (name "MPN") "RC0805JR-072K2L"))
      (libsource (lib "eagle-import") (part "SMD-RES-2.2K-5%-1/8W(0805)"))
    )
    (comp (ref "R214")
      (value "(101)")
      (footprint "eagle-import:R0805")
      (fields (field (name "MPN") "RC0805JR-072K2L"))
      (libsource (lib "eagle-import") (part "SMD-RES-2.2K-5%-1/8W(0805)"))
    )
    (comp (ref "R215")
      (value "104")
      (footprint "eagle-import:R0805")
      (fields (field (name "MPN") "RC0805FR-0710KL"))
      (libsource (lib "eagle-import") (part "SMD-RES-10K-1%-1/8W(0805)"))
    )
    (comp (ref "R216")
      (value "104")
      (footprint "eagle-import:R0805")
      (fields (field (name "MPN") "RC0805FR-0710KL"))
      (libsource (lib "eagle-import") (part "SMD-RES-10K-1%-1/8W(0805)"))
    )
    (comp (ref "R217")
      (value "(1002)")
      (footprint "eagle-import:R0805")
      (fields (field (name "MPN") "RC0805FR-0710KL"))
      (libsource (lib "eagle-import") (part "SMD-RES-10K-1%-1/8W(0805)"))
    )
    (comp (ref "R218")
      (value "2702")
      (footprint "eagle-import:R0805")
      (fields (field (name "MPN") "RC0805FR-0710KL"))
      (libsource (lib "eagle-import") (part "SMD-RES-10K-1%-1/8W(0805)"))
    )
    (comp (ref "R219")
      (value "47")
      (footprint "eagle-import:V235_17_1MM")
      (libsource (lib "eagle-import") (part "R-EU_V235/17_1MM"))
    )
    (comp (ref "R220")
      (value "47")
      (footprint "eagle-import:V235_17_1MM")
      (libsource (lib "eagle-import") (part "R-EU_V235/17_1MM"))
    )
    (comp (ref "R221")
      (value "2702")
      (footprint "eagle-import:R0805")
      (fields (field (name "MPN") "RC0805JR-074K7L"))
      (libsource (lib "eagle-import") (part "SMD-RES-4.7K-5%-1/8W(0805)"))
    )
    (comp (ref "R222")
      (value "2201")
      (footprint "eagle-import:R0805")
      (fields (field (name "MPN") "RC0805JR-072K2L"))
      (libsource (lib "eagle-import") (part "SMD-RES-2.2K-5%-1/8W(0805)"))
    )
    (comp (ref "R223")
      (value "(1002)")
      (footprint "eagle-import:R0805")
      (fields (field (name "MPN") "RC0805JR-074K7L"))
      (libsource (lib "eagle-import") (part "SMD-RES-4.7K-5%-1/8W(0805)"))
    )
    (comp (ref "R224")
      (value "1002")
      (footprint "eagle-import:R0805")
      (fields (field (name "MPN") "RC0805FR-0710KL"))
      (libsource (lib "eagle-import") (part "SMD-RES-10K-1%-1/8W(0805)"))
    )
    (comp (ref "R225")
      (value "102")
      (footprint "eagle-import:R0805")
      (fields (field (name "MPN") "RC0805JR-071KL"))
      (libsource (lib "eagle-import") (part "SMD-RES-1K-5%-1/8W(0805)"))
    )
    (comp (ref "R226")
      (value "2702")
      (footprint "eagle-import:R0805")
      (fields (field (name "MPN") "RC0805JR-074K7L"))
      (libsource (lib "eagle-import") (part "SMD-RES-4.7K-5%-1/8W(0805)"))
    )
    (comp (ref "R227")
      (value "102")
      (footprint "eagle-import:R0805")
      (fields (field (name "MPN") "RC0805JR-071KL"))
      (libsource (lib "eagle-import") (part "SMD-RES-1K-5%-1/8W(0805)"))
    )
    (comp (ref "R228")
      (value "102")
      (footprint "eagle-import:R0805")
      (fields (field (name "MPN") "RC0805JR-071KL"))
      (libsource (lib "eagle-import") (part "SMD-RES-1K-5%-1/8W(0805)"))
    )
    (comp (ref "R229")
      (value "13")
      (footprint "eagle-import:R1206")
      (fields (field (name "MPN") "RC1206JR-0713RL"))
      (libsource (lib "eagle-import") (part "SMD-RES-13R-5%-1/4W(1206)"))
    )
    (comp (ref "R230")
      (value "R_user")
      (footprint "eagle-import:R0805")
      (libsource (lib "eagle-import") (part "R-EU_R0805"))
    )
    (comp (ref "SJ5") (value "SJ") (footprint "eagle-import:SJ") (libsource (lib "eagle-import") (part "SJ")))
    (comp (ref "START4")
      (value "TPSB2.0")
      (footprint "eagle-import:B2.0")
      (libsource (lib "eagle-import") (part "TPSB2.0"))
    )
    (comp (ref "TP93")
      (value "TPSB2.0")
      (footprint "eagle-import:B2.0")
      (libsource (lib "eagle-import") (part "TPSB2.0"))
    )
    (comp (ref "TP94")
      (value "TPSB2.0")
      (footprint "eagle-import:B2.0")
      (libsource (lib "eagle-import") (part "TPSB2.0"))
    )
    (comp (ref "TP95")
      (value "TPSB2.0")
      (footprint "eagle-import:B2.0")
      (libsource (lib "eagle-import") (part "TPSB2.0"))
    )
    (comp (ref "TP96")
      (value "TPSB2.0")
      (footprint "eagle-import:B2.0")
      (libsource (lib "eagle-import") (part "TPSB2.0"))
    )
    (comp (ref "TP97")
      (value "TPSB2.0")
      (footprint "eagle-import:B2.0")
      (libsource (lib "eagle-import") (part "TPSB2.0"))
    )
    (comp (ref "TP98")
      (value "TPSB2.0")
      (footprint "eagle-import:B2.0")
      (libsource (lib "eagle-import") (part "TPSB2.0"))
    )
    (comp (ref "TP99")
      (value "TPSB2.0")
      (footprint "eagle-import:B2.0")
      (libsource (lib "eagle-import") (part "TPSB2.0"))
    )
    (comp (ref "TP100")
      (value "TPSB2.0")
      (footprint "eagle-import:B2.0")
      (libsource (lib "eagle-import") (part "TPSB2.0"))
    )
    (comp (ref "TP101")
      (value "TPSB2.0")
      (footprint "eagle-import:B2.0")
      (libsource (lib "eagle-import") (part "TPSB2.0"))
    )
    (comp (ref "TP102")
      (value "TPSB2.0")
      (footprint "eagle-import:B2.0")
      (libsource (lib "eagle-import") (part "TPSB2.0"))
    )
    (comp (ref "TP103")
      (value "TPSB2.0")
      (footprint "eagle-import:B2.0")
      (libsource (lib "eagle-import") (part "TPSB2.0"))
    )
    (comp (ref "TP104")
      (value "TPSB2.0")
      (footprint "eagle-import:B2.0")
      (libsource (lib "eagle-import") (part "TPSB2.0"))
    )
    (comp (ref "TP105")
      (value "TPSB2.0")
      (footprint "eagle-import:B2.0")
      (libsource (lib "eagle-import") (part "TPSB2.0"))
    )
    (comp (ref "TP106")
      (value "TPSB2.0")
      (footprint "eagle-import:B2.0")
      (libsource (lib "eagle-import") (part "TPSB2.0"))
    )
    (comp (ref "TP107")
      (value "TPSB2.0")
      (footprint "eagle-import:B2.0")
      (libsource (lib "eagle-import") (part "TPSB2.0"))
    )
    (comp (ref "TP108")
      (value "TPSB2.0")
      (footprint "eagle-import:B2.0")
      (libsource (lib "eagle-import") (part "TPSB2.0"))
    )
    (comp (ref "TP109")
      (value "TPSB2.0")
      (footprint "eagle-import:B2.0")
      (libsource (lib "eagle-import") (part "TPSB2.0"))
    )
    (comp (ref "TP110")
      (value "TPSB2.0")
      (footprint "eagle-import:B2.0")
      (libsource (lib "eagle-import") (part "TPSB2.0"))
    )
    (comp (ref "TP111")
      (value "TPSB1,27")
      (footprint "eagle-import:B1,27")
      (libsource (lib "eagle-import") (part "TPSB1,27"))
    )
    (comp (ref "TP112")
      (value "TPSB2.0")
      (footprint "eagle-import:B2.0")
      (libsource (lib "eagle-import") (part "TPSB2.0"))
    )
    (comp (ref "TP113")
      (value "TPSB2.0")
      (footprint "eagle-import:B2.0")
      (libsource (lib "eagle-import") (part "TPSB2.0"))
    )
    (comp (ref "TP114")
      (value "TPSB2.0")
      (footprint "eagle-import:B2.0")
      (libsource (lib "eagle-import") (part "TPSB2.0"))
    )
    (comp (ref "TP115")
      (value "TPSB2.0")
      (footprint "eagle-import:B2.0")
      (libsource (lib "eagle-import") (part "TPSB2.0"))
    )
    (comp (ref "X13")
      (value "CON_BMWV2")
      (footprint "eagle-import:24-PIN_V2")
      (libsource (lib "eagle-import") (part "CON_BMWV2"))
    )
    (comp (ref "X14")
      (value "22-23-2051")
      (footprint "eagle-import:22-23-2051")
      (fields (field (name "MF") "MOLEX"))
      (libsource (lib "eagle-import") (part "22-23-2051"))
    )
    (comp (ref "X15")
      (value "22-23-2021")
      (footprint "eagle-import:22-23-2021")
      (fields (field (name "MF") "MOLEX"))
      (libsource (lib "eagle-import") (part "22-23-2021"))
    )
    (comp (ref "6V7")
      (value "TPSB2.0")
      (footprint "eagle-import:B2.0")
      (libsource (lib "eagle-import") (part "TPSB2.0"))
    )
    (comp (ref "10V7")
      (value "TPSB2.0")
      (footprint "eagle-import:B2.0")
      (libsource (lib "eagle-import") (part "TPSB2.0"))
    )
    (comp (ref "15")
      (value "2081-1132")
      (footprint "eagle-import:12-PIN")
      (libsource (lib "eagle-import") (part "2081-1132"))
    )
    (comp (ref "16")
      (value "2081-1132")
      (footprint "eagle-import:12-PIN")
      (libsource (lib "eagle-import") (part "2081-1132"))
    )
    (comp (ref "C71")
      (value "100u")
      (footprint "eagle-import:C1206")
      (fields (field (name "MPN") "GRM31CR60J107ME39L"))
      (libsource (lib "eagle-import") (part "CERAMIC-100UF-6.3V-20%-X5R(1206)"))
    )
    (comp (ref "C72")
      (value "100u")
      (footprint "eagle-import:C1206")
      (fields (field (name "MPN") "GRM31CR60J107ME39L"))
      (libsource (lib "eagle-import") (part "CERAMIC-100UF-6.3V-20%-X5R(1206)"))
    )
    (comp (ref "C73")
      (value "100nF,")
      (footprint "eagle-import:C0805")
      (fields (field (name "MPN") "CC0805KRX7R9BB104"))
      (libsource (lib "eagle-import") (part "CERAMIC-100NF-50V-10%-X7R(0805)"))
    )
    (comp (ref "C74")
      (value "4.7u")
      (footprint "eagle-import:C0805")
      (fields (field (name "MPN") "CC0805KKX5R8BB475"))
      (libsource (lib "eagle-import") (part "CERAMIC-4.7UF-25V-10%-X5R(0805)"))
    )
    (comp (ref "C75")
      (value "100nF.")
      (footprint "eagle-import:C0805")
      (fields (field (name "MPN") "CC0805KRX7R9BB104"))
      (libsource (lib "eagle-import") (part "CERAMIC-100NF-50V-10%-X7R(0805)"))
    )
    (comp (ref "C76")
      (value "100nF.")
      (footprint "eagle-import:C0805")
      (fields (field (name "MPN") "CC0805KRX7R9BB104"))
      (libsource (lib "eagle-import") (part "CERAMIC-100NF-50V-10%-X7R(0805)"))
    )
    (comp (ref "C77")
      (value "2.2nF")
      (footprint "eagle-import:C0805")
      (fields (field (name "MPN") "CC0805KRX7R9BB104"))
      (libsource (lib "eagle-import") (part "CERAMIC-100NF-50V-10%-X7R(0805)"))
    )
    (comp (ref "C78")
      (value "100nF")
      (footprint "eagle-import:C0805")
      (fields (field (name "MPN") "CC0805KRX7R9BB104"))
      (libsource (lib "eagle-import") (part "CERAMIC-100NF-50V-10%-X7R(0805)"))
    )
    (comp (ref "C79")
      (value "100nF")
      (footprint "eagle-import:C0805")
      (fields (field (name "MPN") "CC0805KRX7R9BB104"))
      (libsource (lib "eagle-import") (part "CERAMIC-100NF-50V-10%-X7R(0805)"))
    )
    (comp (ref "C80")
      (value "100nF,")
      (footprint "eagle-import:C0805")
      (fields (field (name "MPN") "CC0805KRX7R9BB104"))
      (libsource (lib "eagle-import") (part "CERAMIC-100NF-50V-10%-X7R(0805)"))
    )
    (comp (ref "D85")
      (value "1N4007")
      (footprint "eagle-import:DO-214AC")
      (libsource (lib "eagle-import") (part "DIODE-GEN-PURPOSE-1KV-1A(DO-214AC)"))
    )
    (comp (ref "D86")
      (value "1N4007,")
      (footprint "eagle-import:DO-214AC")
      (fields (field (name "MPN") "1N4007"))
      (libsource (lib "eagle-import") (part "DIODE-GEN-PURPOSE-1KV-1A(DO-214AC)"))
    )
    (comp (ref "D87")
      (value "1N4007,")
      (footprint "eagle-import:DO-214AC")
      (fields (field (name "MPN") "1N4007"))
      (libsource (lib "eagle-import") (part "DIODE-GEN-PURPOSE-1KV-1A(DO-214AC)"))
    )
    (comp (ref "D88")
      (value "1N4007.")
      (footprint "eagle-import:DO-214AC")
      (fields (field (name "MPN") "1N4007"))
      (libsource (lib "eagle-import") (part "DIODE-GEN-PURPOSE-1KV-1A(DO-214AC)"))
    )
    (comp (ref "D89")
      (value "1N5817")
      (footprint "eagle-import:DO-214AC_SLIM")
      (libsource (lib "eagle-import") (part "DIODE-GEN-PURPOSE-1KV-1A(DO-214AC)DO-214AC/1206"))
    )
    (comp (ref "D90")
      (value "1N5817.")
      (footprint "eagle-import:DO-214AC_SLIM")
      (libsource (lib "eagle-import") (part "DIODE-GEN-PURPOSE-1KV-1A(DO-214AC)DO-214AC/1206"))
    )
    (comp (ref "D91")
      (value "1N5817.")
      (footprint "eagle-import:DO-214AC_SLIM")
      (libsource (lib "eagle-import") (part "DIODE-GEN-PURPOSE-1KV-1A(DO-214AC)DO-214AC/1206"))
    )
    (comp (ref "D92")
      (value "1N5817")
      (footprint "eagle-import:DO-214AC_SLIM")
      (libsource (lib "eagle-import") (part "DIODE-GEN-PURPOSE-1KV-1A(DO-214AC)DO-214AC/1206"))
    )
    (comp (ref "D93")
      (value "1N4007.")
      (footprint "eagle-import:DO-214AC")
      (fields (field (name "MPN") "1N4007"))
      (libsource (lib "eagle-import") (part "DIODE-GEN-PURPOSE-1KV-1A(DO-214AC)"))
    )
    (comp (ref "D94")
      (value "1N4007")
      (footprint "eagle-import:DO-214AC")
      (libsource (lib "eagle-import") (part "DIODE-GEN-PURPOSE-1KV-1A(DO-214AC)"))
    )
    (comp (ref "D95")
      (value "SM6T")
      (footprint "eagle-import:DO214AA")
      (libsource (lib "eagle-import") (part "SM6T"))
    )
    (comp (ref "D96")
      (value "SM6TDO214AA_BI")
      (footprint "eagle-import:DO214AA_BI")
      (libsource (lib "eagle-import") (part "SM6TDO214AA_BI"))
    )
    (comp (ref "FID29")
      (value "FIDUCIAL")
      (footprint "eagle-import:FIDUCIAL_1MM")
      (libsource (lib "eagle-import") (part "FIDUCIAL"))
    )
    (comp (ref "FID30")
      (value "FIDUCIAL")
      (footprint "eagle-import:FIDUCIAL_1MM")
      (libsource (lib "eagle-import") (part "FIDUCIAL"))
    )
    (comp (ref "FID31")
      (value "FIDUCIAL")
      (footprint "eagle-import:FIDUCIAL_1MM")
      (libsource (lib "eagle-import") (part "FIDUCIAL"))
    )
    (comp (ref "FID32")
      (value "FIDUCIAL")
      (footprint "eagle-import:FIDUCIAL_1MM")
      (libsource (lib "eagle-import") (part "FIDUCIAL"))
    )
    (comp (ref "IC78")
      (value "4028")
      (footprint "eagle-import:SO16")
      (libsource (lib "eagle-import") (part "4028D"))
    )
    (comp (ref "IC79")
      (value "6V pos")
      (footprint "eagle-import:78LXX")
      (libsource (lib "eagle-import") (part "v-reg_78LXX"))
    )
    (comp (ref "IC80")
      (value "317TO202H_NOHOLE")
      (footprint "eagle-import:TO220H_NOHOLE")
      (libsource (lib "eagle-import") (part "317TO202H_NOHOLE"))
    )
    (comp (ref "IC81")
      (value "ULN2004")
      (footprint "eagle-import:SO16")
      (libsource (lib "eagle-import") (part "ULN2004AD"))
    )
    (comp (ref "IC82")
      (value "LM339")
      (footprint "eagle-import:SO14")
      (libsource (lib "eagle-import") (part "LM339D"))
    )
    (comp (ref "IC83")
      (value "78L06")
      (footprint "eagle-import:SOT89_ROUND")
      (libsource (lib "eagle-import") (part "78LXXSOT89_ROUND"))
    )
    (comp (ref "IC84")
      (value "555")
      (footprint "eagle-import:SO08")
      (libsource (lib "eagle-import") (part "555DNE"))
    )
    (comp (ref "IC85")
      (value "4538")
      (footprint "eagle-import:SO16")
      (libsource (lib "eagle-import") (part "4538D"))
    )
    (comp (ref "IC86")
      (value "78L10")
      (footprint "eagle-import:SOT89_ROUND")
      (libsource (lib "eagle-import") (part "78LXXSOT89_ROUND"))
    )
    (comp (ref "IC87")
      (value "LM2904")
      (footprint "eagle-import:SO08")
      (libsource (lib "eagle-import") (part "LM358D"))
    )
    (comp (ref "IC88")
      (value "NUP4304SOT457_R")
      (footprint "eagle-import:SOT457R_PHILIPS")
      (libsource (lib "eagle-import") (part "NUP4304SOT457_R"))
    )
    (comp (ref "JP36")
      (value "JP2EJP2_SMALLPADS")
      (footprint "eagle-import:JP2_SMALLPADS")
      (libsource (lib "eagle-import") (part "JP2EJP2_SMALLPADS"))
    )
    (comp (ref "JP37")
      (value "JP2E_ORIG")
      (footprint "eagle-import:JP2_ORIG_SMALLPADS")
      (libsource (lib "eagle-import") (part "JP2E_ORIG"))
    )
    (comp (ref "JP38")
      (value "JP2EJP2_SMALLPADS")
      (footprint "eagle-import:JP2_SMALLPADS")
      (libsource (lib "eagle-import") (part "JP2EJP2_SMALLPADS"))
    )
    (comp (ref "JP39")
      (value "JP2EJP2_SMALLPADS")
      (footprint "eagle-import:JP2_SMALLPADS")
      (libsource (lib "eagle-import") (part "JP2EJP2_SMALLPADS"))
    )
    (comp (ref "JP40")
      (value "JP2EJP2_SMALLPADS")
      (footprint "eagle-import:JP2_SMALLPADS")
      (libsource (lib "eagle-import") (part "JP2EJP2_SMALLPADS"))
    )
    (comp (ref "LED43")
      (value "LEDLD260")
      (footprint "eagle-import:LD260")
      (libsource (lib "eagle-import") (part "LEDLD260"))
    )
    (comp (ref "LED44")
      (value "LEDLD260")
      (footprint "eagle-import:LD260")
      (libsource (lib "eagle-import") (part "LEDLD260"))
    )
    (comp (ref "LED45")
      (value "LEDLD260")
      (footprint "eagle-import:LD260")
      (libsource (lib "eagle-import") (part "LEDLD260"))
    )
    (comp (ref "LED46")
      (value "LEDLD260")
      (footprint "eagle-import:LD260")
      (libsource (lib "eagle-import") (part "LEDLD260"))
    )
    (comp (ref "LED47")
      (value "LEDLD260")
      (footprint "eagle-import:LD260")
      (libsource (lib "eagle-import") (part "LEDLD260"))
    )
    (comp (ref "LED48")
      (value "LEDLD260")
      (footprint "eagle-import:LD260")
      (libsource (lib "eagle-import") (part "LEDLD260"))
    )
    (comp (ref "Q50")
      (value "BA")
      (footprint "eagle-import:SOT89")
      (libsource (lib "eagle-import") (part "PNP-TRANSISTOR_SOT89"))
    )
    (comp (ref "Q51")
      (value "BA.")
      (footprint "eagle-import:SOT89")
      (libsource (lib "eagle-import") (part "PNP-TRANSISTOR_SOT89"))
    )
    (comp (ref "Q52")
      (value "BA.")
      (footprint "eagle-import:SOT89")
      (libsource (lib "eagle-import") (part "PNP-TRANSISTOR_SOT89"))
    )
    (comp (ref "Q53")
      (value "BA")
      (footprint "eagle-import:SOT89")
      (libsource (lib "eagle-import") (part "PNP-TRANSISTOR_SOT89"))
    )
    (comp (ref "Q54")
      (value "MY")
      (footprint "eagle-import:SOT89")
      (libsource (lib "eagle-import") (part "NPN-TRANSISTOR_SOT89"))
    )
    (comp (ref "Q55")
      (value "J1")
      (footprint "eagle-import:SOT-23")
      (fields (field (name "MPN") "BSS138W-7-F"))
      (libsource (lib "eagle-import") (part "SMD-MOSFET-N-CH-50V-200MA-BSS138W-7-F(SOT-23)"))
    )
    (comp (ref "Q56")
      (value "J1")
      (footprint "eagle-import:SOT-23")
      (fields (field (name "MPN") "BSS138W-7-F"))
      (libsource (lib "eagle-import") (part "SMD-MOSFET-N-CH-50V-200MA-BSS138W-7-F(SOT-23)"))
    )
    (comp (ref "R323")
      (value "47")
      (footprint "eagle-import:V235_17_1MM")
      (libsource (lib "eagle-import") (part "R-EU_V235/17_1MM"))
    )
    (comp (ref "R324")
      (value "13")
      (footprint "eagle-import:R1206")
      (fields (field (name "MPN") "RC1206JR-0713RL"))
      (libsource (lib "eagle-import") (part "SMD-RES-13R-5%-1/4W(1206)"))
    )
    (comp (ref "R325")
      (value "47")
      (footprint "eagle-import:V235_17_1MM")
      (libsource (lib "eagle-import") (part "R-EU_V235/17_1MM"))
    )
    (comp (ref "R326")
      (value "104")
      (footprint "eagle-import:R0805")
      (fields (field (name "MPN") "RC0805FR-0710KL"))
      (libsource (lib "eagle-import") (part "SMD-RES-10K-1%-1/8W(0805)"))
    )
    (comp (ref "R327")
      (value "104")
      (footprint "eagle-import:R0805")
      (fields (field (name "MPN") "RC0805FR-0710KL"))
      (libsource (lib "eagle-import") (part "SMD-RES-10K-1%-1/8W(0805)"))
    )
    (comp (ref "R328")
      (value "104")
      (footprint "eagle-import:R0805")
      (fields (field (name "MPN") "RC0805FR-0710KL"))
      (libsource (lib "eagle-import") (part "SMD-RES-10K-1%-1/8W(0805)"))
    )
    (comp (ref "R329")
      (value "4701")
      (footprint "eagle-import:R0805")
      (fields (field (name "MPN") "RC0805JR-074K7L"))
      (libsource (lib "eagle-import") (part "SMD-RES-4.7K-5%-1/8W(0805)"))
    )
    (comp (ref "R330")
      (value "1002")
      (footprint "eagle-import:R0805")
      (fields (field (name "MPN") "RC0805FR-0710KL"))
      (libsource (lib "eagle-import") (part "SMD-RES-10K-1%-1/8W(0805)"))
    )
    (comp (ref "R331")
      (value "1002")
      (footprint "eagle-import:R0805")
      (fields (field (name "MPN") "RC0805FR-0710KL"))
      (libsource (lib "eagle-import") (part "SMD-RES-10K-1%-1/8W(0805)"))
    )
    (comp (ref "R332")
      (value "1502")
      (footprint "eagle-import:R0805")
      (fields (field (name "MPN") "RC0805FR-0710KL"))
      (libsource (lib "eagle-import") (part "SMD-RES-10K-1%-1/8W(0805)"))
    )
    (comp (ref "R333")
      (value "104")
      (footprint "eagle-import:R0805")
      (fields (field (name "MPN") "RC0805FR-0710KL"))
      (libsource (lib "eagle-import") (part "SMD-RES-10K-1%-1/8W(0805)"))
    )
    (comp (ref "R334")
      (value "104")
      (footprint "eagle-import:R0805")
      (fields (field (name "MPN") "RC0805FR-0710KL"))
      (libsource (lib "eagle-import") (part "SMD-RES-10K-1%-1/8W(0805)"))
    )
    (comp (ref "R335")
      (value "1502")
      (footprint "eagle-import:R0805")
      (fields (field (name "MPN") "RC0805FR-0710KL"))
      (libsource (lib "eagle-import") (part "SMD-RES-10K-1%-1/8W(0805)"))
    )
    (comp (ref "R336")
      (value "1002")
      (footprint "eagle-import:R0805")
      (fields (field (name "MPN") "RC0805FR-0710KL"))
      (libsource (lib "eagle-import") (part "SMD-RES-10K-1%-1/8W(0805)"))
    )
    (comp (ref "R337")
      (value "2201")
      (footprint "eagle-import:R0805")
      (fields (field (name "MPN") "RC0805JR-072K2L"))
      (libsource (lib "eagle-import") (part "SMD-RES-2.2K-5%-1/8W(0805)"))
    )
    (comp (ref "R338")
      (value "1002")
      (footprint "eagle-import:R0805")
      (fields (field (name "MPN") "RC0805FR-0710KL"))
      (libsource (lib "eagle-import") (part "SMD-RES-10K-1%-1/8W(0805)"))
    )
    (comp (ref "R339")
      (value "4701")
      (footprint "eagle-import:R0805")
      (fields (field (name "MPN") "RC0805JR-074K7L"))
      (libsource (lib "eagle-import") (part "SMD-RES-4.7K-5%-1/8W(0805)"))
    )
    (comp (ref "R340")
      (value "2702")
      (footprint "eagle-import:R0805")
      (fields (field (name "MPN") "RC0805JR-074K7L"))
      (libsource (lib "eagle-import") (part "SMD-RES-4.7K-5%-1/8W(0805)"))
    )
    (comp (ref "R341")
      (value "102")
      (footprint "eagle-import:R0805")
      (fields (field (name "MPN") "RC0805JR-071KL"))
      (libsource (lib "eagle-import") (part "SMD-RES-1K-5%-1/8W(0805)"))
    )
    (comp (ref "R342")
      (value "R_user")
      (footprint "eagle-import:R0805")
      (libsource (lib "eagle-import") (part "R-EU_R0805"))
    )
    (comp (ref "R343")
      (value "100")
      (footprint "eagle-import:R0805")
      (fields (field (name "MPN") "RC0805JR-07220RL"))
      (libsource (lib "eagle-import") (part "SMD-RES-220R-5%-1/8W(0805)"))
    )
    (comp (ref "R344")
      (value "(101)")
      (footprint "eagle-import:R0805")
      (fields (field (name "MPN") "RC0805JR-07100RL"))
      (libsource (lib "eagle-import") (part "SMD-RES-100R-5%-1/8W(0805)"))
    )
    (comp (ref "R345")
      (value "(1000)")
      (footprint "eagle-import:R0805")
      (fields (field (name "MPN") "RC0805JR-07100RL"))
      (libsource (lib "eagle-import") (part "SMD-RES-100R-5%-1/8W(0805)"))
    )
    (comp (ref "R346")
      (value "102")
      (footprint "eagle-import:R0805")
      (fields (field (name "MPN") "RC0805JR-071KL"))
      (libsource (lib "eagle-import") (part "SMD-RES-1K-5%-1/8W(0805)"))
    )
    (comp (ref "R347")
      (value "13")
      (footprint "eagle-import:R1206")
      (fields (field (name "MPN") "RC1206JR-0713RL"))
      (libsource (lib "eagle-import") (part "SMD-RES-13R-5%-1/4W(1206)"))
    )
    (comp (ref "R348")
      (value "13")
      (footprint "eagle-import:R1206")
      (fields (field (name "MPN") "RC1206JR-0713RL"))
      (libsource (lib "eagle-import") (part "SMD-RES-13R-5%-1/4W(1206)"))
    )
    (comp (ref "R349")
      (value "2702")
      (footprint "eagle-import:R0805")
      (fields (field (name "MPN") "RC0805JR-074K7L"))
      (libsource (lib "eagle-import") (part "SMD-RES-4.7K-5%-1/8W(0805)"))
    )
    (comp (ref "R350")
      (value "4701")
      (footprint "eagle-import:R0805")
      (fields (field (name "MPN") "RC0805JR-074K7L"))
      (libsource (lib "eagle-import") (part "SMD-RES-4.7K-5%-1/8W(0805)"))
    )
    (comp (ref "R351")
      (value "100")
      (footprint "eagle-import:R0805")
      (fields (field (name "MPN") "RC0805JR-072K2L"))
      (libsource (lib "eagle-import") (part "SMD-RES-2.2K-5%-1/8W(0805)"))
    )
    (comp (ref "R352")
      (value "(101)")
      (footprint "eagle-import:R0805")
      (fields (field (name "MPN") "RC0805JR-072K2L"))
      (libsource (lib "eagle-import") (part "SMD-RES-2.2K-5%-1/8W(0805)"))
    )
    (comp (ref "R353")
      (value "104")
      (footprint "eagle-import:R0805")
      (fields (field (name "MPN") "RC0805FR-0710KL"))
      (libsource (lib "eagle-import") (part "SMD-RES-10K-1%-1/8W(0805)"))
    )
    (comp (ref "R354")
      (value "104")
      (footprint "eagle-import:R0805")
      (fields (field (name "MPN") "RC0805FR-0710KL"))
      (libsource (lib "eagle-import") (part "SMD-RES-10K-1%-1/8W(0805)"))
    )
    (comp (ref "R355")
      (value "(1002)")
      (footprint "eagle-import:R0805")
      (fields (field (name "MPN") "RC0805FR-0710KL"))
      (libsource (lib "eagle-import") (part "SMD-RES-10K-1%-1/8W(0805)"))
    )
    (comp (ref "R356")
      (value "2702")
      (footprint "eagle-import:R0805")
      (fields (field (name "MPN") "RC0805FR-0710KL"))
      (libsource (lib "eagle-import") (part "SMD-RES-10K-1%-1/8W(0805)"))
    )
    (comp (ref "R357")
      (value "47")
      (footprint "eagle-import:V235_17_1MM")
      (libsource (lib "eagle-import") (part "R-EU_V235/17_1MM"))
    )
    (comp (ref "R358")
      (value "47")
      (footprint "eagle-import:V235_17_1MM")
      (libsource (lib "eagle-import") (part "R-EU_V235/17_1MM"))
    )
    (comp (ref "R359")
      (value "2702")
      (footprint "eagle-import:R0805")
      (fields (field (name "MPN") "RC0805JR-074K7L"))
      (libsource (lib "eagle-import") (part "SMD-RES-4.7K-5%-1/8W(0805)"))
    )
    (comp (ref "R360")
      (value "2201")
      (footprint "eagle-import:R0805")
      (fields (field (name "MPN") "RC0805JR-072K2L"))
      (libsource (lib "eagle-import") (part "SMD-RES-2.2K-5%-1/8W(0805)"))
    )
    (comp (ref "R361")
      (value "(1002)")
      (footprint "eagle-import:R0805")
      (fields (field (name "MPN") "RC0805JR-074K7L"))
      (libsource (lib "eagle-import") (part "SMD-RES-4.7K-5%-1/8W(0805)"))
    )
    (comp (ref "R362")
      (value "1002")
      (footprint "eagle-import:R0805")
      (fields (field (name "MPN") "RC0805FR-0710KL"))
      (libsource (lib "eagle-import") (part "SMD-RES-10K-1%-1/8W(0805)"))
    )
    (comp (ref "R363")
      (value "102")
      (footprint "eagle-import:R0805")
      (fields (field (name "MPN") "RC0805JR-071KL"))
      (libsource (lib "eagle-import") (part "SMD-RES-1K-5%-1/8W(0805)"))
    )
    (comp (ref "R364")
      (value "2702")
      (footprint "eagle-import:R0805")
      (fields (field (name "MPN") "RC0805JR-074K7L"))
      (libsource (lib "eagle-import") (part "SMD-RES-4.7K-5%-1/8W(0805)"))
    )
    (comp (ref "R365")
      (value "102")
      (footprint "eagle-import:R0805")
      (fields (field (name "MPN") "RC0805JR-071KL"))
      (libsource (lib "eagle-import") (part "SMD-RES-1K-5%-1/8W(0805)"))
    )
    (comp (ref "R366")
      (value "102")
      (footprint "eagle-import:R0805")
      (fields (field (name "MPN") "RC0805JR-071KL"))
      (libsource (lib "eagle-import") (part "SMD-RES-1K-5%-1/8W(0805)"))
    )
    (comp (ref "R367")
      (value "13")
      (footprint "eagle-import:R1206")
      (fields (field (name "MPN") "RC1206JR-0713RL"))
      (libsource (lib "eagle-import") (part "SMD-RES-13R-5%-1/4W(1206)"))
    )
    (comp (ref "R368")
      (value "R_user")
      (footprint "eagle-import:R0805")
      (libsource (lib "eagle-import") (part "R-EU_R0805"))
    )
    (comp (ref "SJ8") (value "SJ") (footprint "eagle-import:SJ") (libsource (lib "eagle-import") (part "SJ")))
    (comp (ref "START7")
      (value "TPSB2.0")
      (footprint "eagle-import:B2.0")
      (libsource (lib "eagle-import") (part "TPSB2.0"))
    )
    (comp (ref "TP162")
      (value "TPSB2.0")
      (footprint "eagle-import:B2.0")
      (libsource (lib "eagle-import") (part "TPSB2.0"))
    )
    (comp (ref "TP163")
      (value "TPSB2.0")
      (footprint "eagle-import:B2.0")
      (libsource (lib "eagle-import") (part "TPSB2.0"))
    )
    (comp (ref "TP164")
      (value "TPSB2.0")
      (footprint "eagle-import:B2.0")
      (libsource (lib "eagle-import") (part "TPSB2.0"))
    )
    (comp (ref "TP165")
      (value "TPSB2.0")
      (footprint "eagle-import:B2.0")
      (libsource (lib "eagle-import") (part "TPSB2.0"))
    )
    (comp (ref "TP166")
      (value "TPSB2.0")
      (footprint "eagle-import:B2.0")
      (libsource (lib "eagle-import") (part "TPSB2.0"))
    )
    (comp (ref "TP167")
      (value "TPSB2.0")
      (footprint "eagle-import:B2.0")
      (libsource (lib "eagle-import") (part "TPSB2.0"))
    )
    (comp (ref "TP168")
      (value "TPSB2.0")
      (footprint "eagle-import:B2.0")
      (libsource (lib "eagle-import") (part "TPSB2.0"))
    )
    (comp (ref "TP169")
      (value "TPSB2.0")
      (footprint "eagle-import:B2.0")
      (libsource (lib "eagle-import") (part "TPSB2.0"))
    )
    (comp (ref "TP170")
      (value "TPSB2.0")
      (footprint "eagle-import:B2.0")
      (libsource (lib "eagle-import") (part "TPSB2.0"))
    )
    (comp (ref "TP171")
      (value "TPSB2.0")
      (footprint "eagle-import:B2.0")
      (libsource (lib "eagle-import") (part "TPSB2.0"))
    )
    (comp (ref "TP172")
      (value "TPSB2.0")
      (footprint "eagle-import:B2.0")
      (libsource (lib "eagle-import") (part "TPSB2.0"))
    )
    (comp (ref "TP173")
      (value "TPSB2.0")
      (footprint "eagle-import:B2.0")
      (libsource (lib "eagle-import") (part "TPSB2.0"))
    )
    (comp (ref "TP174")
      (value "TPSB2.0")
      (footprint "eagle-import:B2.0")
      (libsource (lib "eagle-import") (part "TPSB2.0"))
    )
    (comp (ref "TP175")
      (value "TPSB2.0")
      (footprint "eagle-import:B2.0")
      (libsource (lib "eagle-import") (part "TPSB2.0"))
    )
    (comp (ref "TP176")
      (value "TPSB2.0")
      (footprint "eagle-import:B2.0")
      (libsource (lib "eagle-import") (part "TPSB2.0"))
    )
    (comp (ref "TP177")
      (value "TPSB2.0")
      (footprint "eagle-import:B2.0")
      (libsource (lib "eagle-import") (part "TPSB2.0"))
    )
    (comp (ref "TP178")
      (value "TPSB2.0")
      (footprint "eagle-import:B2.0")
      (libsource (lib "eagle-import") (part "TPSB2.0"))
    )
    (comp (ref "TP179")
      (value "TPSB2.0")
      (footprint "eagle-import:B2.0")
      (libsource (lib "eagle-import") (part "TPSB2.0"))
    )
    (comp (ref "TP180")
      (value "TPSB1,27")
      (footprint "eagle-import:B1,27")
      (libsource (lib "eagle-import") (part "TPSB1,27"))
    )
    (comp (ref "TP181")
      (value "TPSB2.0")
      (footprint "eagle-import:B2.0")
      (libsource (lib "eagle-import") (part "TPSB2.0"))
    )
    (comp (ref "TP182")
      (value "TPSB2.0")
      (footprint "eagle-import:B2.0")
      (libsource (lib "eagle-import") (part "TPSB2.0"))
    )
    (comp (ref "TP183")
      (value "TPSB2.0")
      (footprint "eagle-import:B2.0")
      (libsource (lib "eagle-import") (part "TPSB2.0"))
    )
    (comp (ref "TP184")
      (value "TPSB2.0")
      (footprint "eagle-import:B2.0")
      (libsource (lib "eagle-import") (part "TPSB2.0"))
    )
    (comp (ref "X22")
      (value "CON_BMWV2")
      (footprint "eagle-import:24-PIN_V2")
      (libsource (lib "eagle-import") (part "CON_BMWV2"))
    )
    (comp (ref "X23")
      (value "22-23-2051")
      (footprint "eagle-import:22-23-2051")
      (fields (field (name "MF") "MOLEX"))
      (libsource (lib "eagle-import") (part "22-23-2051"))
    )
    (comp (ref "X24")
      (value "22-23-2021")
      (footprint "eagle-import:22-23-2021")
      (fields (field (name "MF") "MOLEX"))
      (libsource (lib "eagle-import") (part "22-23-2021"))
    )
    (comp (ref "6V5")
      (value "TPSB2.0")
      (footprint "eagle-import:B2.0")
      (libsource (lib "eagle-import") (part "TPSB2.0"))
    )
    (comp (ref "10V5")
      (value "TPSB2.0")
      (footprint "eagle-import:B2.0")
      (libsource (lib "eagle-import") (part "TPSB2.0"))
    )
    (comp (ref "11")
      (value "2081-1132")
      (footprint "eagle-import:12-PIN")
      (libsource (lib "eagle-import") (part "2081-1132"))
    )
    (comp (ref "12")
      (value "2081-1132")
      (footprint "eagle-import:12-PIN")
      (libsource (lib "eagle-import") (part "2081-1132"))
    )
    (comp (ref "C51")
      (value "100u")
      (footprint "eagle-import:C1206")
      (fields (field (name "MPN") "GRM31CR60J107ME39L"))
      (libsource (lib "eagle-import") (part "CERAMIC-100UF-6.3V-20%-X5R(1206)"))
    )
    (comp (ref "C52")
      (value "100u")
      (footprint "eagle-import:C1206")
      (fields (field (name "MPN") "GRM31CR60J107ME39L"))
      (libsource (lib "eagle-import") (part "CERAMIC-100UF-6.3V-20%-X5R(1206)"))
    )
    (comp (ref "C53")
      (value "100nF,")
      (footprint "eagle-import:C0805")
      (fields (field (name "MPN") "CC0805KRX7R9BB104"))
      (libsource (lib "eagle-import") (part "CERAMIC-100NF-50V-10%-X7R(0805)"))
    )
    (comp (ref "C54")
      (value "4.7u")
      (footprint "eagle-import:C0805")
      (fields (field (name "MPN") "CC0805KKX5R8BB475"))
      (libsource (lib "eagle-import") (part "CERAMIC-4.7UF-25V-10%-X5R(0805)"))
    )
    (comp (ref "C55")
      (value "100nF.")
      (footprint "eagle-import:C0805")
      (fields (field (name "MPN") "CC0805KRX7R9BB104"))
      (libsource (lib "eagle-import") (part "CERAMIC-100NF-50V-10%-X7R(0805)"))
    )
    (comp (ref "C56")
      (value "100nF.")
      (footprint "eagle-import:C0805")
      (fields (field (name "MPN") "CC0805KRX7R9BB104"))
      (libsource (lib "eagle-import") (part "CERAMIC-100NF-50V-10%-X7R(0805)"))
    )
    (comp (ref "C57")
      (value "2.2nF")
      (footprint "eagle-import:C0805")
      (fields (field (name "MPN") "CC0805KRX7R9BB104"))
      (libsource (lib "eagle-import") (part "CERAMIC-100NF-50V-10%-X7R(0805)"))
    )
    (comp (ref "C58")
      (value "100nF")
      (footprint "eagle-import:C0805")
      (fields (field (name "MPN") "CC0805KRX7R9BB104"))
      (libsource (lib "eagle-import") (part "CERAMIC-100NF-50V-10%-X7R(0805)"))
    )
    (comp (ref "C59")
      (value "100nF")
      (footprint "eagle-import:C0805")
      (fields (field (name "MPN") "CC0805KRX7R9BB104"))
      (libsource (lib "eagle-import") (part "CERAMIC-100NF-50V-10%-X7R(0805)"))
    )
    (comp (ref "C60")
      (value "100nF,")
      (footprint "eagle-import:C0805")
      (fields (field (name "MPN") "CC0805KRX7R9BB104"))
      (libsource (lib "eagle-import") (part "CERAMIC-100NF-50V-10%-X7R(0805)"))
    )
    (comp (ref "D61")
      (value "1N4007")
      (footprint "eagle-import:DO-214AC")
      (libsource (lib "eagle-import") (part "DIODE-GEN-PURPOSE-1KV-1A(DO-214AC)"))
    )
    (comp (ref "D62")
      (value "1N4007,")
      (footprint "eagle-import:DO-214AC")
      (fields (field (name "MPN") "1N4007"))
      (libsource (lib "eagle-import") (part "DIODE-GEN-PURPOSE-1KV-1A(DO-214AC)"))
    )
    (comp (ref "D63")
      (value "1N4007,")
      (footprint "eagle-import:DO-214AC")
      (fields (field (name "MPN") "1N4007"))
      (libsource (lib "eagle-import") (part "DIODE-GEN-PURPOSE-1KV-1A(DO-214AC)"))
    )
    (comp (ref "D64")
      (value "1N4007.")
      (footprint "eagle-import:DO-214AC")
      (fields (field (name "MPN") "1N4007"))
      (libsource (lib "eagle-import") (part "DIODE-GEN-PURPOSE-1KV-1A(DO-214AC)"))
    )
    (comp (ref "D65")
      (value "1N5817")
      (footprint "eagle-import:DO-214AC_SLIM")
      (libsource (lib "eagle-import") (part "DIODE-GEN-PURPOSE-1KV-1A(DO-214AC)DO-214AC/1206"))
    )
    (comp (ref "D66")
      (value "1N5817.")
      (footprint "eagle-import:DO-214AC_SLIM")
      (libsource (lib "eagle-import") (part "DIODE-GEN-PURPOSE-1KV-1A(DO-214AC)DO-214AC/1206"))
    )
    (comp (ref "D67")
      (value "1N5817.")
      (footprint "eagle-import:DO-214AC_SLIM")
      (libsource (lib "eagle-import") (part "DIODE-GEN-PURPOSE-1KV-1A(DO-214AC)DO-214AC/1206"))
    )
    (comp (ref "D68")
      (value "1N5817")
      (footprint "eagle-import:DO-214AC_SLIM")
      (libsource (lib "eagle-import") (part "DIODE-GEN-PURPOSE-1KV-1A(DO-214AC)DO-214AC/1206"))
    )
    (comp (ref "D69")
      (value "1N4007.")
      (footprint "eagle-import:DO-214AC")
      (fields (field (name "MPN") "1N4007"))
      (libsource (lib "eagle-import") (part "DIODE-GEN-PURPOSE-1KV-1A(DO-214AC)"))
    )
    (comp (ref "D70")
      (value "1N4007")
      (footprint "eagle-import:DO-214AC")
      (libsource (lib "eagle-import") (part "DIODE-GEN-PURPOSE-1KV-1A(DO-214AC)"))
    )
    (comp (ref "D71")
      (value "SM6T")
      (footprint "eagle-import:DO214AA")
      (libsource (lib "eagle-import") (part "SM6T"))
    )
    (comp (ref "D72")
      (value "SM6TDO214AA_BI")
      (footprint "eagle-import:DO214AA_BI")
      (libsource (lib "eagle-import") (part "SM6TDO214AA_BI"))
    )
    (comp (ref "FID21")
      (value "FIDUCIAL")
      (footprint "eagle-import:FIDUCIAL_1MM")
      (libsource (lib "eagle-import") (part "FIDUCIAL"))
    )
    (comp (ref "FID22")
      (value "FIDUCIAL")
      (footprint "eagle-import:FIDUCIAL_1MM")
      (libsource (lib "eagle-import") (part "FIDUCIAL"))
    )
    (comp (ref "FID23")
      (value "FIDUCIAL")
      (footprint "eagle-import:FIDUCIAL_1MM")
      (libsource (lib "eagle-import") (part "FIDUCIAL"))
    )
    (comp (ref "FID24")
      (value "FIDUCIAL")
      (footprint "eagle-import:FIDUCIAL_1MM")
      (libsource (lib "eagle-import") (part "FIDUCIAL"))
    )
    (comp (ref "IC56")
      (value "4028")
      (footprint "eagle-import:SO16")
      (libsource (lib "eagle-import") (part "4028D"))
    )
    (comp (ref "IC57")
      (value "6V pos")
      (footprint "eagle-import:78LXX")
      (libsource (lib "eagle-import") (part "v-reg_78LXX"))
    )
    (comp (ref "IC58")
      (value "317TO202H_NOHOLE")
      (footprint "eagle-import:TO220H_NOHOLE")
      (libsource (lib "eagle-import") (part "317TO202H_NOHOLE"))
    )
    (comp (ref "IC59")
      (value "ULN2004")
      (footprint "eagle-import:SO16")
      (libsource (lib "eagle-import") (part "ULN2004AD"))
    )
    (comp (ref "IC60")
      (value "LM339")
      (footprint "eagle-import:SO14")
      (libsource (lib "eagle-import") (part "LM339D"))
    )
    (comp (ref "IC61")
      (value "78L06")
      (footprint "eagle-import:SOT89_ROUND")
      (libsource (lib "eagle-import") (part "78LXXSOT89_ROUND"))
    )
    (comp (ref "IC62")
      (value "555")
      (footprint "eagle-import:SO08")
      (libsource (lib "eagle-import") (part "555DNE"))
    )
    (comp (ref "IC63")
      (value "4538")
      (footprint "eagle-import:SO16")
      (libsource (lib "eagle-import") (part "4538D"))
    )
    (comp (ref "IC64")
      (value "78L10")
      (footprint "eagle-import:SOT89_ROUND")
      (libsource (lib "eagle-import") (part "78LXXSOT89_ROUND"))
    )
    (comp (ref "IC65")
      (value "LM2904")
      (footprint "eagle-import:SO08")
      (libsource (lib "eagle-import") (part "LM358D"))
    )
    (comp (ref "IC66")
      (value "NUP4304SOT457_R")
      (footprint "eagle-import:SOT457R_PHILIPS")
      (libsource (lib "eagle-import") (part "NUP4304SOT457_R"))
    )
    (comp (ref "JP26")
      (value "JP2EJP2_SMALLPADS")
      (footprint "eagle-import:JP2_SMALLPADS")
      (libsource (lib "eagle-import") (part "JP2EJP2_SMALLPADS"))
    )
    (comp (ref "JP27")
      (value "JP2E_ORIG")
      (footprint "eagle-import:JP2_ORIG_SMALLPADS")
      (libsource (lib "eagle-import") (part "JP2E_ORIG"))
    )
    (comp (ref "JP28")
      (value "JP2EJP2_SMALLPADS")
      (footprint "eagle-import:JP2_SMALLPADS")
      (libsource (lib "eagle-import") (part "JP2EJP2_SMALLPADS"))
    )
    (comp (ref "JP29")
      (value "JP2EJP2_SMALLPADS")
      (footprint "eagle-import:JP2_SMALLPADS")
      (libsource (lib "eagle-import") (part "JP2EJP2_SMALLPADS"))
    )
    (comp (ref "JP30")
      (value "JP2EJP2_SMALLPADS")
      (footprint "eagle-import:JP2_SMALLPADS")
      (libsource (lib "eagle-import") (part "JP2EJP2_SMALLPADS"))
    )
    (comp (ref "LED31")
      (value "LEDLD260")
      (footprint "eagle-import:LD260")
      (libsource (lib "eagle-import") (part "LEDLD260"))
    )
    (comp (ref "LED32")
      (value "LEDLD260")
      (footprint "eagle-import:LD260")
      (libsource (lib "eagle-import") (part "LEDLD260"))
    )
    (comp (ref "LED33")
      (value "LEDLD260")
      (footprint "eagle-import:LD260")
      (libsource (lib "eagle-import") (part "LEDLD260"))
    )
    (comp (ref "LED34")
      (value "LEDLD260")
      (footprint "eagle-import:LD260")
      (libsource (lib "eagle-import") (part "LEDLD260"))
    )
    (comp (ref "LED35")
      (value "LEDLD260")
      (footprint "eagle-import:LD260")
      (libsource (lib "eagle-import") (part "LEDLD260"))
    )
    (comp (ref "LED36")
      (value "LEDLD260")
      (footprint "eagle-import:LD260")
      (libsource (lib "eagle-import") (part "LEDLD260"))
    )
    (comp (ref "Q36")
      (value "BA")
      (footprint "eagle-import:SOT89")
      (libsource (lib "eagle-import") (part "PNP-TRANSISTOR_SOT89"))
    )
    (comp (ref "Q37")
      (value "BA.")
      (footprint "eagle-import:SOT89")
      (libsource (lib "eagle-import") (part "PNP-TRANSISTOR_SOT89"))
    )
    (comp (ref "Q38")
      (value "BA.")
      (footprint "eagle-import:SOT89")
      (libsource (lib "eagle-import") (part "PNP-TRANSISTOR_SOT89"))
    )
    (comp (ref "Q39")
      (value "BA")
      (footprint "eagle-import:SOT89")
      (libsource (lib "eagle-import") (part "PNP-TRANSISTOR_SOT89"))
    )
    (comp (ref "Q40")
      (value "MY")
      (footprint "eagle-import:SOT89")
      (libsource (lib "eagle-import") (part "NPN-TRANSISTOR_SOT89"))
    )
    (comp (ref "Q41")
      (value "J1")
      (footprint "eagle-import:SOT-23")
      (fields (field (name "MPN") "BSS138W-7-F"))
      (libsource (lib "eagle-import") (part "SMD-MOSFET-N-CH-50V-200MA-BSS138W-7-F(SOT-23)"))
    )
    (comp (ref "Q42")
      (value "J1")
      (footprint "eagle-import:SOT-23")
      (fields (field (name "MPN") "BSS138W-7-F"))
      (libsource (lib "eagle-import") (part "SMD-MOSFET-N-CH-50V-200MA-BSS138W-7-F(SOT-23)"))
    )
    (comp (ref "R231")
      (value "47")
      (footprint "eagle-import:V235_17_1MM")
      (libsource (lib "eagle-import") (part "R-EU_V235/17_1MM"))
    )
    (comp (ref "R232")
      (value "13")
      (footprint "eagle-import:R1206")
      (fields (field (name "MPN") "RC1206JR-0713RL"))
      (libsource (lib "eagle-import") (part "SMD-RES-13R-5%-1/4W(1206)"))
    )
    (comp (ref "R233")
      (value "47")
      (footprint "eagle-import:V235_17_1MM")
      (libsource (lib "eagle-import") (part "R-EU_V235/17_1MM"))
    )
    (comp (ref "R234")
      (value "104")
      (footprint "eagle-import:R0805")
      (fields (field (name "MPN") "RC0805FR-0710KL"))
      (libsource (lib "eagle-import") (part "SMD-RES-10K-1%-1/8W(0805)"))
    )
    (comp (ref "R235")
      (value "104")
      (footprint "eagle-import:R0805")
      (fields (field (name "MPN") "RC0805FR-0710KL"))
      (libsource (lib "eagle-import") (part "SMD-RES-10K-1%-1/8W(0805)"))
    )
    (comp (ref "R236")
      (value "104")
      (footprint "eagle-import:R0805")
      (fields (field (name "MPN") "RC0805FR-0710KL"))
      (libsource (lib "eagle-import") (part "SMD-RES-10K-1%-1/8W(0805)"))
    )
    (comp (ref "R237")
      (value "4701")
      (footprint "eagle-import:R0805")
      (fields (field (name "MPN") "RC0805JR-074K7L"))
      (libsource (lib "eagle-import") (part "SMD-RES-4.7K-5%-1/8W(0805)"))
    )
    (comp (ref "R238")
      (value "1002")
      (footprint "eagle-import:R0805")
      (fields (field (name "MPN") "RC0805FR-0710KL"))
      (libsource (lib "eagle-import") (part "SMD-RES-10K-1%-1/8W(0805)"))
    )
    (comp (ref "R239")
      (value "1002")
      (footprint "eagle-import:R0805")
      (fields (field (name "MPN") "RC0805FR-0710KL"))
      (libsource (lib "eagle-import") (part "SMD-RES-10K-1%-1/8W(0805)"))
    )
    (comp (ref "R240")
      (value "1502")
      (footprint "eagle-import:R0805")
      (fields (field (name "MPN") "RC0805FR-0710KL"))
      (libsource (lib "eagle-import") (part "SMD-RES-10K-1%-1/8W(0805)"))
    )
    (comp (ref "R241")
      (value "104")
      (footprint "eagle-import:R0805")
      (fields (field (name "MPN") "RC0805FR-0710KL"))
      (libsource (lib "eagle-import") (part "SMD-RES-10K-1%-1/8W(0805)"))
    )
    (comp (ref "R242")
      (value "104")
      (footprint "eagle-import:R0805")
      (fields (field (name "MPN") "RC0805FR-0710KL"))
      (libsource (lib "eagle-import") (part "SMD-RES-10K-1%-1/8W(0805)"))
    )
    (comp (ref "R243")
      (value "1502")
      (footprint "eagle-import:R0805")
      (fields (field (name "MPN") "RC0805FR-0710KL"))
      (libsource (lib "eagle-import") (part "SMD-RES-10K-1%-1/8W(0805)"))
    )
    (comp (ref "R244")
      (value "1002")
      (footprint "eagle-import:R0805")
      (fields (field (name "MPN") "RC0805FR-0710KL"))
      (libsource (lib "eagle-import") (part "SMD-RES-10K-1%-1/8W(0805)"))
    )
    (comp (ref "R245")
      (value "2201")
      (footprint "eagle-import:R0805")
      (fields (field (name "MPN") "RC0805JR-072K2L"))
      (libsource (lib "eagle-import") (part "SMD-RES-2.2K-5%-1/8W(0805)"))
    )
    (comp (ref "R246")
      (value "1002")
      (footprint "eagle-import:R0805")
      (fields (field (name "MPN") "RC0805FR-0710KL"))
      (libsource (lib "eagle-import") (part "SMD-RES-10K-1%-1/8W(0805)"))
    )
    (comp (ref "R247")
      (value "4701")
      (footprint "eagle-import:R0805")
      (fields (field (name "MPN") "RC0805JR-074K7L"))
      (libsource (lib "eagle-import") (part "SMD-RES-4.7K-5%-1/8W(0805)"))
    )
    (comp (ref "R248")
      (value "2702")
      (footprint "eagle-import:R0805")
      (fields (field (name "MPN") "RC0805JR-074K7L"))
      (libsource (lib "eagle-import") (part "SMD-RES-4.7K-5%-1/8W(0805)"))
    )
    (comp (ref "R249")
      (value "102")
      (footprint "eagle-import:R0805")
      (fields (field (name "MPN") "RC0805JR-071KL"))
      (libsource (lib "eagle-import") (part "SMD-RES-1K-5%-1/8W(0805)"))
    )
    (comp (ref "R250")
      (value "R_user")
      (footprint "eagle-import:R0805")
      (libsource (lib "eagle-import") (part "R-EU_R0805"))
    )
    (comp (ref "R251")
      (value "100")
      (footprint "eagle-import:R0805")
      (fields (field (name "MPN") "RC0805JR-07220RL"))
      (libsource (lib "eagle-import") (part "SMD-RES-220R-5%-1/8W(0805)"))
    )
    (comp (ref "R252")
      (value "(101)")
      (footprint "eagle-import:R0805")
      (fields (field (name "MPN") "RC0805JR-07100RL"))
      (libsource (lib "eagle-import") (part "SMD-RES-100R-5%-1/8W(0805)"))
    )
    (comp (ref "R253")
      (value "(1000)")
      (footprint "eagle-import:R0805")
      (fields (field (name "MPN") "RC0805JR-07100RL"))
      (libsource (lib "eagle-import") (part "SMD-RES-100R-5%-1/8W(0805)"))
    )
    (comp (ref "R254")
      (value "102")
      (footprint "eagle-import:R0805")
      (fields (field (name "MPN") "RC0805JR-071KL"))
      (libsource (lib "eagle-import") (part "SMD-RES-1K-5%-1/8W(0805)"))
    )
    (comp (ref "R255")
      (value "13")
      (footprint "eagle-import:R1206")
      (fields (field (name "MPN") "RC1206JR-0713RL"))
      (libsource (lib "eagle-import") (part "SMD-RES-13R-5%-1/4W(1206)"))
    )
    (comp (ref "R256")
      (value "13")
      (footprint "eagle-import:R1206")
      (fields (field (name "MPN") "RC1206JR-0713RL"))
      (libsource (lib "eagle-import") (part "SMD-RES-13R-5%-1/4W(1206)"))
    )
    (comp (ref "R257")
      (value "2702")
      (footprint "eagle-import:R0805")
      (fields (field (name "MPN") "RC0805JR-074K7L"))
      (libsource (lib "eagle-import") (part "SMD-RES-4.7K-5%-1/8W(0805)"))
    )
    (comp (ref "R258")
      (value "4701")
      (footprint "eagle-import:R0805")
      (fields (field (name "MPN") "RC0805JR-074K7L"))
      (libsource (lib "eagle-import") (part "SMD-RES-4.7K-5%-1/8W(0805)"))
    )
    (comp (ref "R259")
      (value "100")
      (footprint "eagle-import:R0805")
      (fields (field (name "MPN") "RC0805JR-072K2L"))
      (libsource (lib "eagle-import") (part "SMD-RES-2.2K-5%-1/8W(0805)"))
    )
    (comp (ref "R260")
      (value "(101)")
      (footprint "eagle-import:R0805")
      (fields (field (name "MPN") "RC0805JR-072K2L"))
      (libsource (lib "eagle-import") (part "SMD-RES-2.2K-5%-1/8W(0805)"))
    )
    (comp (ref "R261")
      (value "104")
      (footprint "eagle-import:R0805")
      (fields (field (name "MPN") "RC0805FR-0710KL"))
      (libsource (lib "eagle-import") (part "SMD-RES-10K-1%-1/8W(0805)"))
    )
    (comp (ref "R262")
      (value "104")
      (footprint "eagle-import:R0805")
      (fields (field (name "MPN") "RC0805FR-0710KL"))
      (libsource (lib "eagle-import") (part "SMD-RES-10K-1%-1/8W(0805)"))
    )
    (comp (ref "R263")
      (value "(1002)")
      (footprint "eagle-import:R0805")
      (fields (field (name "MPN") "RC0805FR-0710KL"))
      (libsource (lib "eagle-import") (part "SMD-RES-10K-1%-1/8W(0805)"))
    )
    (comp (ref "R264")
      (value "2702")
      (footprint "eagle-import:R0805")
      (fields (field (name "MPN") "RC0805FR-0710KL"))
      (libsource (lib "eagle-import") (part "SMD-RES-10K-1%-1/8W(0805)"))
    )
    (comp (ref "R265")
      (value "47")
      (footprint "eagle-import:V235_17_1MM")
      (libsource (lib "eagle-import") (part "R-EU_V235/17_1MM"))
    )
    (comp (ref "R266")
      (value "47")
      (footprint "eagle-import:V235_17_1MM")
      (libsource (lib "eagle-import") (part "R-EU_V235/17_1MM"))
    )
    (comp (ref "R267")
      (value "2702")
      (footprint "eagle-import:R0805")
      (fields (field (name "MPN") "RC0805JR-074K7L"))
      (libsource (lib "eagle-import") (part "SMD-RES-4.7K-5%-1/8W(0805)"))
    )
    (comp (ref "R268")
      (value "2201")
      (footprint "eagle-import:R0805")
      (fields (field (name "MPN") "RC0805JR-072K2L"))
      (libsource (lib "eagle-import") (part "SMD-RES-2.2K-5%-1/8W(0805)"))
    )
    (comp (ref "R269")
      (value "(1002)")
      (footprint "eagle-import:R0805")
      (fields (field (name "MPN") "RC0805JR-074K7L"))
      (libsource (lib "eagle-import") (part "SMD-RES-4.7K-5%-1/8W(0805)"))
    )
    (comp (ref "R270")
      (value "1002")
      (footprint "eagle-import:R0805")
      (fields (field (name "MPN") "RC0805FR-0710KL"))
      (libsource (lib "eagle-import") (part "SMD-RES-10K-1%-1/8W(0805)"))
    )
    (comp (ref "R271")
      (value "102")
      (footprint "eagle-import:R0805")
      (fields (field (name "MPN") "RC0805JR-071KL"))
      (libsource (lib "eagle-import") (part "SMD-RES-1K-5%-1/8W(0805)"))
    )
    (comp (ref "R272")
      (value "2702")
      (footprint "eagle-import:R0805")
      (fields (field (name "MPN") "RC0805JR-074K7L"))
      (libsource (lib "eagle-import") (part "SMD-RES-4.7K-5%-1/8W(0805)"))
    )
    (comp (ref "R273")
      (value "102")
      (footprint "eagle-import:R0805")
      (fields (field (name "MPN") "RC0805JR-071KL"))
      (libsource (lib "eagle-import") (part "SMD-RES-1K-5%-1/8W(0805)"))
    )
    (comp (ref "R274")
      (value "102")
      (footprint "eagle-import:R0805")
      (fields (field (name "MPN") "RC0805JR-071KL"))
      (libsource (lib "eagle-import") (part "SMD-RES-1K-5%-1/8W(0805)"))
    )
    (comp (ref "R275")
      (value "13")
      (footprint "eagle-import:R1206")
      (fields (field (name "MPN") "RC1206JR-0713RL"))
      (libsource (lib "eagle-import") (part "SMD-RES-13R-5%-1/4W(1206)"))
    )
    (comp (ref "R276")
      (value "R_user")
      (footprint "eagle-import:R0805")
      (libsource (lib "eagle-import") (part "R-EU_R0805"))
    )
    (comp (ref "SJ6") (value "SJ") (footprint "eagle-import:SJ") (libsource (lib "eagle-import") (part "SJ")))
    (comp (ref "START5")
      (value "TPSB2.0")
      (footprint "eagle-import:B2.0")
      (libsource (lib "eagle-import") (part "TPSB2.0"))
    )
    (comp (ref "TP116")
      (value "TPSB2.0")
      (footprint "eagle-import:B2.0")
      (libsource (lib "eagle-import") (part "TPSB2.0"))
    )
    (comp (ref "TP117")
      (value "TPSB2.0")
      (footprint "eagle-import:B2.0")
      (libsource (lib "eagle-import") (part "TPSB2.0"))
    )
    (comp (ref "TP118")
      (value "TPSB2.0")
      (footprint "eagle-import:B2.0")
      (libsource (lib "eagle-import") (part "TPSB2.0"))
    )
    (comp (ref "TP119")
      (value "TPSB2.0")
      (footprint "eagle-import:B2.0")
      (libsource (lib "eagle-import") (part "TPSB2.0"))
    )
    (comp (ref "TP120")
      (value "TPSB2.0")
      (footprint "eagle-import:B2.0")
      (libsource (lib "eagle-import") (part "TPSB2.0"))
    )
    (comp (ref "TP121")
      (value "TPSB2.0")
      (footprint "eagle-import:B2.0")
      (libsource (lib "eagle-import") (part "TPSB2.0"))
    )
    (comp (ref "TP122")
      (value "TPSB2.0")
      (footprint "eagle-import:B2.0")
      (libsource (lib "eagle-import") (part "TPSB2.0"))
    )
    (comp (ref "TP123")
      (value "TPSB2.0")
      (footprint "eagle-import:B2.0")
      (libsource (lib "eagle-import") (part "TPSB2.0"))
    )
    (comp (ref "TP124")
      (value "TPSB2.0")
      (footprint "eagle-import:B2.0")
      (libsource (lib "eagle-import") (part "TPSB2.0"))
    )
    (comp (ref "TP125")
      (value "TPSB2.0")
      (footprint "eagle-import:B2.0")
      (libsource (lib "eagle-import") (part "TPSB2.0"))
    )
    (comp (ref "TP126")
      (value "TPSB2.0")
      (footprint "eagle-import:B2.0")
      (libsource (lib "eagle-import") (part "TPSB2.0"))
    )
    (comp (ref "TP127")
      (value "TPSB2.0")
      (footprint "eagle-import:B2.0")
      (libsource (lib "eagle-import") (part "TPSB2.0"))
    )
    (comp (ref "TP128")
      (value "TPSB2.0")
      (footprint "eagle-import:B2.0")
      (libsource (lib "eagle-import") (part "TPSB2.0"))
    )
    (comp (ref "TP129")
      (value "TPSB2.0")
      (footprint "eagle-import:B2.0")
      (libsource (lib "eagle-import") (part "TPSB2.0"))
    )
    (comp (ref "TP130")
      (value "TPSB2.0")
      (footprint "eagle-import:B2.0")
      (libsource (lib "eagle-import") (part "TPSB2.0"))
    )
    (comp (ref "TP131")
      (value "TPSB2.0")
      (footprint "eagle-import:B2.0")
      (libsource (lib "eagle-import") (part "TPSB2.0"))
    )
    (comp (ref "TP132")
      (value "TPSB2.0")
      (footprint "eagle-import:B2.0")
      (libsource (lib "eagle-import") (part "TPSB2.0"))
    )
    (comp (ref "TP133")
      (value "TPSB2.0")
      (footprint "eagle-import:B2.0")
      (libsource (lib "eagle-import") (part "TPSB2.0"))
    )
    (comp (ref "TP134")
      (value "TPSB1,27")
      (footprint "eagle-import:B1,27")
      (libsource (lib "eagle-import") (part "TPSB1,27"))
    )
    (comp (ref "TP135")
      (value "TPSB2.0")
      (footprint "eagle-import:B2.0")
      (libsource (lib "eagle-import") (part "TPSB2.0"))
    )
    (comp (ref "TP136")
      (value "TPSB2.0")
      (footprint "eagle-import:B2.0")
      (libsource (lib "eagle-import") (part "TPSB2.0"))
    )
    (comp (ref "TP137")
      (value "TPSB2.0")
      (footprint "eagle-import:B2.0")
      (libsource (lib "eagle-import") (part "TPSB2.0"))
    )
    (comp (ref "TP138")
      (value "TPSB2.0")
      (footprint "eagle-import:B2.0")
      (libsource (lib "eagle-import") (part "TPSB2.0"))
    )
    (comp (ref "X16")
      (value "CON_BMWV2")
      (footprint "eagle-import:24-PIN_V2")
      (libsource (lib "eagle-import") (part "CON_BMWV2"))
    )
    (comp (ref "X17")
      (value "22-23-2051")
      (footprint "eagle-import:22-23-2051")
      (fields (field (name "MF") "MOLEX"))
      (libsource (lib "eagle-import") (part "22-23-2051"))
    )
    (comp (ref "X18")
      (value "22-23-2021")
      (footprint "eagle-import:22-23-2021")
      (fields (field (name "MF") "MOLEX"))
      (libsource (lib "eagle-import") (part "22-23-2021"))
    )
  )
  (nets
    (net (code "1") (name "+10V") (class "Default")
      (node (ref "10V") (pin "TP") (pinfunction "PP_TP") (pintype "input"))
      (node (ref "10V1") (pin "TP") (pinfunction "PP_TP") (pintype "input"))
      (node (ref "10V10") (pin "TP") (pinfunction "PP_TP") (pintype "input"))
      (node (ref "10V11") (pin "TP") (pinfunction "PP_TP") (pintype "input"))
      (node (ref "10V2") (pin "TP") (pinfunction "PP_TP") (pintype "input"))
      (node (ref "10V3") (pin "TP") (pinfunction "PP_TP") (pintype "input"))
      (node (ref "10V4") (pin "TP") (pinfunction "PP_TP") (pintype "input"))
      (node (ref "10V5") (pin "TP") (pinfunction "PP_TP") (pintype "input"))
      (node (ref "10V6") (pin "TP") (pinfunction "PP_TP") (pintype "input"))
      (node (ref "10V7") (pin "TP") (pinfunction "PP_TP") (pintype "input"))
      (node (ref "10V8") (pin "TP") (pinfunction "PP_TP") (pintype "input"))
      (node (ref "10V9") (pin "TP") (pinfunction "PP_TP") (pintype "input"))
      (node (ref "C108") (pin "1") (pinfunction "1_1") (pintype "passive"))
      (node (ref "C118") (pin "1") (pinfunction "1_1") (pintype "passive"))
      (node (ref "C18") (pin "1") (pinfunction "1_1") (pintype "passive"))
      (node (ref "C2") (pin "1") (pinfunction "1_1") (pintype "passive"))
      (node (ref "C28") (pin "1") (pinfunction "1_1") (pintype "passive"))
      (node (ref "C38") (pin "1") (pinfunction "1_1") (pintype "passive"))
      (node (ref "C48") (pin "1") (pinfunction "1_1") (pintype "passive"))
      (node (ref "C58") (pin "1") (pinfunction "1_1") (pintype "passive"))
      (node (ref "C68") (pin "1") (pinfunction "1_1") (pintype "passive"))
      (node (ref "C78") (pin "1") (pinfunction "1_1") (pintype "passive"))
      (node (ref "C88") (pin "1") (pinfunction "1_1") (pintype "passive"))
      (node (ref "C98") (pin "1") (pinfunction "1_1") (pintype "passive"))
      (node (ref "IC10") (pin "4") (pinfunction "R_4") (pintype "input"))
      (node (ref "IC10") (pin "8") (pinfunction "V+_8") (pintype "power_in"))
      (node (ref "IC106") (pin "4") (pinfunction "R_4") (pintype "input"))
      (node (ref "IC106") (pin "8") (pinfunction "V+_8") (pintype "power_in"))
      (node (ref "IC107") (pin "13") (pinfunction "CD_13") (pintype "input"))
      (node (ref "IC107") (pin "16") (pinfunction "VDD_16") (pintype "power_in"))
      (node (ref "IC107") (pin "3") (pinfunction "CD_3") (pintype "input"))
      (node (ref "IC107") (pin "5") (pinfunction "B_5") (pintype "input"))
      (node (ref "IC108") (pin "1") (pinfunction "OUT_1") (pintype "passive"))
      (node (ref "IC11") (pin "13") (pinfunction "CD_13") (pintype "input"))
      (node (ref "IC11") (pin "16") (pinfunction "VDD_16") (pintype "power_in"))
      (node (ref "IC11") (pin "3") (pinfunction "CD_3") (pintype "input"))
      (node (ref "IC11") (pin "5") (pinfunction "B_5") (pintype "input"))
      (node (ref "IC117") (pin "4") (pinfunction "R_4") (pintype "input"))
      (node (ref "IC117") (pin "8") (pinfunction "V+_8") (pintype "power_in"))
      (node (ref "IC118") (pin "13") (pinfunction "CD_13") (pintype "input"))
      (node (ref "IC118") (pin "16") (pinfunction "VDD_16") (pintype "power_in"))
      (node (ref "IC118") (pin "3") (pinfunction "CD_3") (pintype "input"))
      (node (ref "IC118") (pin "5") (pinfunction "B_5") (pintype "input"))
      (node (ref "IC119") (pin "1") (pinfunction "OUT_1") (pintype "passive"))
      (node (ref "IC128") (pin "4") (pinfunction "R_4") (pintype "input"))
      (node (ref "IC128") (pin "8") (pinfunction "V+_8") (pintype "power_in"))
      (node (ref "IC129") (pin "13") (pinfunction "CD_13") (pintype "input"))
      (node (ref "IC129") (pin "16") (pinfunction "VDD_16") (pintype "power_in"))
      (node (ref "IC129") (pin "3") (pinfunction "CD_3") (pintype "input"))
      (node (ref "IC129") (pin "5") (pinfunction "B_5") (pintype "input"))
      (node (ref "IC130") (pin "1") (pinfunction "OUT_1") (pintype "passive"))
      (node (ref "IC18") (pin "4") (pinfunction "R_4") (pintype "input"))
      (node (ref "IC18") (pin "8") (pinfunction "V+_8") (pintype "power_in"))
      (node (ref "IC19") (pin "13") (pinfunction "CD_13") (pintype "input"))
      (node (ref "IC19") (pin "16") (pinfunction "VDD_16") (pintype "power_in"))
      (node (ref "IC19") (pin "3") (pinfunction "CD_3") (pintype "input"))
      (node (ref "IC19") (pin "5") (pinfunction "B_5") (pintype "input"))
      (node (ref "IC20") (pin "1") (pinfunction "OUT_1") (pintype "passive"))
      (node (ref "IC29") (pin "4") (pinfunction "R_4") (pintype "input"))
      (node (ref "IC29") (pin "8") (pinfunction "V+_8") (pintype "power_in"))
      (node (ref "IC30") (pin "13") (pinfunction "CD_13") (pintype "input"))
      (node (ref "IC30") (pin "16") (pinfunction "VDD_16") (pintype "power_in"))
      (node (ref "IC30") (pin "3") (pinfunction "CD_3") (pintype "input"))
      (node (ref "IC30") (pin "5") (pinfunction "B_5") (pintype "input"))
      (node (ref "IC31") (pin "1") (pinfunction "OUT_1") (pintype "passive"))
      (node (ref "IC4") (pin "1") (pinfunction "OUT_1") (pintype "passive"))
      (node (ref "IC40") (pin "4") (pinfunction "R_4") (pintype "input"))
      (node (ref "IC40") (pin "8") (pinfunction "V+_8") (pintype "power_in"))
      (node (ref "IC41") (pin "13") (pinfunction "CD_13") (pintype "input"))
      (node (ref "IC41") (pin "16") (pinfunction "VDD_16") (pintype "power_in"))
      (node (ref "IC41") (pin "3") (pinfunction "CD_3") (pintype "input"))
      (node (ref "IC41") (pin "5") (pinfunction "B_5") (pintype "input"))
      (node (ref "IC42") (pin "1") (pinfunction "OUT_1") (pintype "passive"))
      (node (ref "IC51") (pin "4") (pinfunction "R_4") (pintype "input"))
      (node (ref "IC51") (pin "8") (pinfunction "V+_8") (pintype "power_in"))
      (node (ref "IC52") (pin "13") (pinfunction "CD_13") (pintype "input"))
      (node (ref "IC52") (pin "16") (pinfunction "VDD_16") (pintype "power_in"))
      (node (ref "IC52") (pin "3") (pinfunction "CD_3") (pintype "input"))
      (node (ref "IC52") (pin "5") (pinfunction "B_5") (pintype "input"))
      (node (ref "IC53") (pin "1") (pinfunction "OUT_1") (pintype "passive"))
      (node (ref "IC62") (pin "4") (pinfunction "R_4") (pintype "input"))
      (node (ref "IC62") (pin "8") (pinfunction "V+_8") (pintype "power_in"))
      (node (ref "IC63") (pin "13") (pinfunction "CD_13") (pintype "input"))
      (node (ref "IC63") (pin "16") (pinfunction "VDD_16") (pintype "power_in"))
      (node (ref "IC63") (pin "3") (pinfunction "CD_3") (pintype "input"))
      (node (ref "IC63") (pin "5") (pinfunction "B_5") (pintype "input"))
      (node (ref "IC64") (pin "1") (pinfunction "OUT_1") (pintype "passive"))
      (node (ref "IC73") (pin "4") (pinfunction "R_4") (pintype "input"))
      (node (ref "IC73") (pin "8") (pinfunction "V+_8") (pintype "power_in"))
      (node (ref "IC74") (pin "13") (pinfunction "CD_13") (pintype "input"))
      (node (ref "IC74") (pin "16") (pinfunction "VDD_16") (pintype "power_in"))
      (node (ref "IC74") (pin "3") (pinfunction "CD_3") (pintype "input"))
      (node (ref "IC74") (pin "5") (pinfunction "B_5") (pintype "input"))
      (node (ref "IC75") (pin "1") (pinfunction "OUT_1") (pintype "passive"))
      (node (ref "IC84") (pin "4") (pinfunction "R_4") (pintype "input"))
      (node (ref "IC84") (pin "8") (pinfunction "V+_8") (pintype "power_in"))
      (node (ref "IC85") (pin "13") (pinfunction "CD_13") (pintype "input"))
      (node (ref "IC85") (pin "16") (pinfunction "VDD_16") (pintype "power_in"))
      (node (ref "IC85") (pin "3") (pinfunction "CD_3") (pintype "input"))
      (node (ref "IC85") (pin "5") (pinfunction "B_5") (pintype "input"))
      (node (ref "IC86") (pin "1") (pinfunction "OUT_1") (pintype "passive"))
      (node (ref "IC95") (pin "4") (pinfunction "R_4") (pintype "input"))
      (node (ref "IC95") (pin "8") (pinfunction "V+_8") (pintype "power_in"))
      (node (ref "IC96") (pin "13") (pinfunction "CD_13") (pintype "input"))
      (node (ref "IC96") (pin "16") (pinfunction "VDD_16") (pintype "power_in"))
      (node (ref "IC96") (pin "3") (pinfunction "CD_3") (pintype "input"))
      (node (ref "IC96") (pin "5") (pinfunction "B_5") (pintype "input"))
      (node (ref "IC97") (pin "1") (pinfunction "OUT_1") (pintype "passive"))
      (node (ref "R129") (pin "2") (pinfunction "2_2") (pintype "passive"))
      (node (ref "R175") (pin "2") (pinfunction "2_2") (pintype "passive"))
      (node (ref "R221") (pin "2") (pinfunction "2_2") (pintype "passive"))
      (node (ref "R267") (pin "2") (pinfunction "2_2") (pintype "passive"))
      (node (ref "R313") (pin "2") (pinfunction "2_2") (pintype "passive"))
      (node (ref "R359") (pin "2") (pinfunction "2_2") (pintype "passive"))
      (node (ref "R405") (pin "2") (pinfunction "2_2") (pintype "passive"))
      (node (ref "R45") (pin "2") (pinfunction "2_2") (pintype "passive"))
      (node (ref "R451") (pin "2") (pinfunction "2_2") (pintype "passive"))
      (node (ref "R497") (pin "2") (pinfunction "2_2") (pintype "passive"))
      (node (ref "R543") (pin "2") (pinfunction "2_2") (pintype "passive"))
      (node (ref "R83") (pin "2") (pinfunction "2_2") (pintype "passive"))
    )
    (net (code "2") (name "+12V") (class "Default")
      (node (ref "10") (pin "1") (pinfunction "KL_1") (pintype "passive"))
      (node (ref "12") (pin "1") (pinfunction "KL_1") (pintype "passive"))
      (node (ref "14") (pin "1") (pinfunction "KL_1") (pintype "passive"))
      (node (ref "16") (pin "1") (pinfunction "KL_1") (pintype "passive"))
      (node (ref "18") (pin "1") (pinfunction "KL_1") (pintype "passive"))
      (node (ref "2") (pin "1") (pinfunction "KL_1") (pintype "passive"))
      (node (ref "20") (pin "1") (pinfunction "KL_1") (pintype "passive"))
      (node (ref "22") (pin "1") (pinfunction "KL_1") (pintype "passive"))
      (node (ref "24") (pin "1") (pinfunction "KL_1") (pintype "passive"))
      (node (ref "4") (pin "1") (pinfunction "KL_1") (pintype "passive"))
      (node (ref "6") (pin "1") (pinfunction "KL_1") (pintype "passive"))
      (node (ref "8") (pin "1") (pinfunction "KL_1") (pintype "passive"))
      (node (ref "D1") (pin "C") (pinfunction "C_C") (pintype "passive"))
      (node (ref "D107") (pin "C") (pinfunction "C_C") (pintype "passive"))
      (node (ref "D119") (pin "C") (pinfunction "C_C") (pintype "passive"))
      (node (ref "D131") (pin "C") (pinfunction "C_C") (pintype "passive"))
      (node (ref "D143") (pin "C") (pinfunction "C_C") (pintype "passive"))
      (node (ref "D23") (pin "C") (pinfunction "C_C") (pintype "passive"))
      (node (ref "D35") (pin "C") (pinfunction "C_C") (pintype "passive"))
      (node (ref "D47") (pin "C") (pinfunction "C_C") (pintype "passive"))
      (node (ref "D59") (pin "C") (pinfunction "C_C") (pintype "passive"))
      (node (ref "D71") (pin "C") (pinfunction "C_C") (pintype "passive"))
      (node (ref "D83") (pin "C") (pinfunction "C_C") (pintype "passive"))
      (node (ref "D95") (pin "C") (pinfunction "C_C") (pintype "passive"))
      (node (ref "IC100") (pin "16") (pinfunction "VDD_16") (pintype "power_in"))
      (node (ref "IC101") (pin "IN") (pinfunction "IN_IN") (pintype "input"))
      (node (ref "IC103") (pin "9") (pinfunction "CD+_9") (pintype "passive"))
      (node (ref "IC105") (pin "3") (pinfunction "IN_3") (pintype "input"))
      (node (ref "IC108") (pin "3") (pinfunction "IN_3") (pintype "input"))
      (node (ref "IC110") (pin "2") (pinfunction "V+_2") (pintype "passive"))
      (node (ref "IC111") (pin "16") (pinfunction "VDD_16") (pintype "power_in"))
      (node (ref "IC112") (pin "IN") (pinfunction "IN_IN") (pintype "input"))
      (node (ref "IC114") (pin "9") (pinfunction "CD+_9") (pintype "passive"))
      (node (ref "IC116") (pin "3") (pinfunction "IN_3") (pintype "input"))
      (node (ref "IC119") (pin "3") (pinfunction "IN_3") (pintype "input"))
      (node (ref "IC12") (pin "16") (pinfunction "VDD_16") (pintype "power_in"))
      (node (ref "IC121") (pin "2") (pinfunction "V+_2") (pintype "passive"))
      (node (ref "IC122") (pin "16") (pinfunction "VDD_16") (pintype "power_in"))
      (node (ref "IC123") (pin "IN") (pinfunction "IN_IN") (pintype "input"))
      (node (ref "IC125") (pin "9") (pinfunction "CD+_9") (pintype "passive"))
      (node (ref "IC127") (pin "3") (pinfunction "IN_3") (pintype "input"))
      (node (ref "IC13") (pin "IN") (pinfunction "IN_IN") (pintype "input"))
      (node (ref "IC130") (pin "3") (pinfunction "IN_3") (pintype "input"))
      (node (ref "IC132") (pin "2") (pinfunction "V+_2") (pintype "passive"))
      (node (ref "IC15") (pin "9") (pinfunction "CD+_9") (pintype "passive"))
      (node (ref "IC17") (pin "3") (pinfunction "IN_3") (pintype "input"))
      (node (ref "IC2") (pin "3") (pinfunction "IN_3") (pintype "input"))
      (node (ref "IC20") (pin "3") (pinfunction "IN_3") (pintype "input"))
      (node (ref "IC22") (pin "2") (pinfunction "V+_2") (pintype "passive"))
      (node (ref "IC23") (pin "16") (pinfunction "VDD_16") (pintype "power_in"))
      (node (ref "IC24") (pin "IN") (pinfunction "IN_IN") (pintype "input"))
      (node (ref "IC26") (pin "9") (pinfunction "CD+_9") (pintype "passive"))
      (node (ref "IC28") (pin "3") (pinfunction "IN_3") (pintype "input"))
      (node (ref "IC3") (pin "IN") (pinfunction "IN_IN") (pintype "input"))
      (node (ref "IC31") (pin "3") (pinfunction "IN_3") (pintype "input"))
      (node (ref "IC33") (pin "2") (pinfunction "V+_2") (pintype "passive"))
      (node (ref "IC34") (pin "16") (pinfunction "VDD_16") (pintype "power_in"))
      (node (ref "IC35") (pin "IN") (pinfunction "IN_IN") (pintype "input"))
      (node (ref "IC37") (pin "9") (pinfunction "CD+_9") (pintype "passive"))
      (node (ref "IC39") (pin "3") (pinfunction "IN_3") (pintype "input"))
      (node (ref "IC4") (pin "3") (pinfunction "IN_3") (pintype "input"))
      (node (ref "IC42") (pin "3") (pinfunction "IN_3") (pintype "input"))
      (node (ref "IC44") (pin "2") (pinfunction "V+_2") (pintype "passive"))
      (node (ref "IC45") (pin "16") (pinfunction "VDD_16") (pintype "power_in"))
      (node (ref "IC46") (pin "IN") (pinfunction "IN_IN") (pintype "input"))
      (node (ref "IC48") (pin "9") (pinfunction "CD+_9") (pintype "passive"))
      (node (ref "IC5") (pin "16") (pinfunction "VDD_16") (pintype "power_in"))
      (node (ref "IC50") (pin "3") (pinfunction "IN_3") (pintype "input"))
      (node (ref "IC53") (pin "3") (pinfunction "IN_3") (pintype "input"))
      (node (ref "IC55") (pin "2") (pinfunction "V+_2") (pintype "passive"))
      (node (ref "IC56") (pin "16") (pinfunction "VDD_16") (pintype "power_in"))
      (node (ref "IC57") (pin "IN") (pinfunction "IN_IN") (pintype "input"))
      (node (ref "IC59") (pin "9") (pinfunction "CD+_9") (pintype "passive"))
      (node (ref "IC6") (pin "2") (pinfunction "V+_2") (pintype "passive"))
      (node (ref "IC61") (pin "3") (pinfunction "IN_3") (pintype "input"))
      (node (ref "IC64") (pin "3") (pinfunction "IN_3") (pintype "input"))
      (node (ref "IC66") (pin "2") (pinfunction "V+_2") (pintype "passive"))
      (node (ref "IC67") (pin "16") (pinfunction "VDD_16") (pintype "power_in"))
      (node (ref "IC68") (pin "IN") (pinfunction "IN_IN") (pintype "input"))
      (node (ref "IC7") (pin "9") (pinfunction "CD+_9") (pintype "passive"))
      (node (ref "IC70") (pin "9") (pinfunction "CD+_9") (pintype "passive"))
      (node (ref "IC72") (pin "3") (pinfunction "IN_3") (pintype "input"))
      (node (ref "IC75") (pin "3") (pinfunction "IN_3") (pintype "input"))
      (node (ref "IC77") (pin "2") (pinfunction "V+_2") (pintype "passive"))
      (node (ref "IC78") (pin "16") (pinfunction "VDD_16") (pintype "power_in"))
      (node (ref "IC79") (pin "IN") (pinfunction "IN_IN") (pintype "input"))
      (node (ref "IC81") (pin "9") (pinfunction "CD+_9") (pintype "passive"))
      (node (ref "IC83") (pin "3") (pinfunction "IN_3") (pintype "input"))
      (node (ref "IC86") (pin "3") (pinfunction "IN_3") (pintype "input"))
      (node (ref "IC88") (pin "2") (pinfunction "V+_2") (pintype "passive"))
      (node (ref "IC89") (pin "16") (pinfunction "VDD_16") (pintype "power_in"))
      (node (ref "IC90") (pin "IN") (pinfunction "IN_IN") (pintype "input"))
      (node (ref "IC92") (pin "9") (pinfunction "CD+_9") (pintype "passive"))
      (node (ref "IC94") (pin "3") (pinfunction "IN_3") (pintype "input"))
      (node (ref "IC97") (pin "3") (pinfunction "IN_3") (pintype "input"))
      (node (ref "IC99") (pin "2") (pinfunction "V+_2") (pintype "passive"))
      (node (ref "JP1") (pin "2") (pinfunction "2_2") (pintype "passive"))
      (node (ref "JP11") (pin "2") (pinfunction "2_2") (pintype "passive"))
      (node (ref "JP16") (pin "2") (pinfunction "2_2") (pintype "passive"))
      (node (ref "JP21") (pin "2") (pinfunction "2_2") (pintype "passive"))
      (node (ref "JP26") (pin "2") (pinfunction "2_2") (pintype "passive"))
      (node (ref "JP31") (pin "2") (pinfunction "2_2") (pintype "passive"))
      (node (ref "JP36") (pin "2") (pinfunction "2_2") (pintype "passive"))
      (node (ref "JP41") (pin "2") (pinfunction "2_2") (pintype "passive"))
      (node (ref "JP46") (pin "2") (pinfunction "2_2") (pintype "passive"))
      (node (ref "JP51") (pin "2") (pinfunction "2_2") (pintype "passive"))
      (node (ref "JP56") (pin "2") (pinfunction "2_2") (pintype "passive"))
      (node (ref "JP6") (pin "2") (pinfunction "2_2") (pintype "passive"))
      (node (ref "Q11") (pin "3") (pinfunction "E_3") (pintype "passive"))
      (node (ref "Q15") (pin "3") (pinfunction "E_3") (pintype "passive"))
      (node (ref "Q18") (pin "3") (pinfunction "E_3") (pintype "passive"))
      (node (ref "Q22") (pin "3") (pinfunction "E_3") (pintype "passive"))
      (node (ref "Q25") (pin "3") (pinfunction "E_3") (pintype "passive"))
      (node (ref "Q29") (pin "3") (pinfunction "E_3") (pintype "passive"))
      (node (ref "Q32") (pin "3") (pinfunction "E_3") (pintype "passive"))
      (node (ref "Q36") (pin "3") (pinfunction "E_3") (pintype "passive"))
      (node (ref "Q39") (pin "3") (pinfunction "E_3") (pintype "passive"))
      (node (ref "Q4") (pin "3") (pinfunction "E_3") (pintype "passive"))
      (node (ref "Q43") (pin "3") (pinfunction "E_3") (pintype "passive"))
      (node (ref "Q46") (pin "3") (pinfunction "E_3") (pintype "passive"))
      (node (ref "Q5") (pin "3") (pinfunction "E_3") (pintype "passive"))
      (node (ref "Q50") (pin "3") (pinfunction "E_3") (pintype "passive"))
      (node (ref "Q53") (pin "3") (pinfunction "E_3") (pintype "passive"))
      (node (ref "Q57") (pin "3") (pinfunction "E_3") (pintype "passive"))
      (node (ref "Q60") (pin "3") (pinfunction "E_3") (pintype "passive"))
      (node (ref "Q64") (pin "3") (pinfunction "E_3") (pintype "passive"))
      (node (ref "Q67") (pin "3") (pinfunction "E_3") (pintype "passive"))
      (node (ref "Q71") (pin "3") (pinfunction "E_3") (pintype "passive"))
      (node (ref "Q74") (pin "3") (pinfunction "E_3") (pintype "passive"))
      (node (ref "Q78") (pin "3") (pinfunction "E_3") (pintype "passive"))
      (node (ref "Q8") (pin "3") (pinfunction "E_3") (pintype "passive"))
      (node (ref "Q81") (pin "3") (pinfunction "E_3") (pintype "passive"))
      (node (ref "R10") (pin "2") (pinfunction "2_2") (pintype "passive"))
      (node (ref "R11") (pin "2") (pinfunction "2_2") (pintype "passive"))
      (node (ref "R117") (pin "1") (pinfunction "1_1") (pintype "passive"))
      (node (ref "R118") (pin "1") (pinfunction "1_1") (pintype "passive"))
      (node (ref "R123") (pin "1") (pinfunction "1_1") (pintype "passive"))
      (node (ref "R141") (pin "2") (pinfunction "2_2") (pintype "passive"))
      (node (ref "R142") (pin "2") (pinfunction "2_2") (pintype "passive"))
      (node (ref "R143") (pin "2") (pinfunction "2_2") (pintype "passive"))
      (node (ref "R144") (pin "2") (pinfunction "2_2") (pintype "passive"))
      (node (ref "R163") (pin "1") (pinfunction "1_1") (pintype "passive"))
      (node (ref "R164") (pin "1") (pinfunction "1_1") (pintype "passive"))
      (node (ref "R169") (pin "1") (pinfunction "1_1") (pintype "passive"))
      (node (ref "R187") (pin "2") (pinfunction "2_2") (pintype "passive"))
      (node (ref "R188") (pin "2") (pinfunction "2_2") (pintype "passive"))
      (node (ref "R189") (pin "2") (pinfunction "2_2") (pintype "passive"))
      (node (ref "R190") (pin "2") (pinfunction "2_2") (pintype "passive"))
      (node (ref "R2") (pin "1") (pinfunction "1_1") (pintype "passive"))
      (node (ref "R209") (pin "1") (pinfunction "1_1") (pintype "passive"))
      (node (ref "R210") (pin "1") (pinfunction "1_1") (pintype "passive"))
      (node (ref "R215") (pin "1") (pinfunction "1_1") (pintype "passive"))
      (node (ref "R233") (pin "2") (pinfunction "2_2") (pintype "passive"))
      (node (ref "R234") (pin "2") (pinfunction "2_2") (pintype "passive"))
      (node (ref "R235") (pin "2") (pinfunction "2_2") (pintype "passive"))
      (node (ref "R236") (pin "2") (pinfunction "2_2") (pintype "passive"))
      (node (ref "R255") (pin "1") (pinfunction "1_1") (pintype "passive"))
      (node (ref "R256") (pin "1") (pinfunction "1_1") (pintype "passive"))
      (node (ref "R261") (pin "1") (pinfunction "1_1") (pintype "passive"))
      (node (ref "R279") (pin "2") (pinfunction "2_2") (pintype "passive"))
      (node (ref "R280") (pin "2") (pinfunction "2_2") (pintype "passive"))
      (node (ref "R281") (pin "2") (pinfunction "2_2") (pintype "passive"))
      (node (ref "R282") (pin "2") (pinfunction "2_2") (pintype "passive"))
      (node (ref "R29") (pin "2") (pinfunction "2_2") (pintype "passive"))
      (node (ref "R301") (pin "1") (pinfunction "1_1") (pintype "passive"))
      (node (ref "R302") (pin "1") (pinfunction "1_1") (pintype "passive"))
      (node (ref "R307") (pin "1") (pinfunction "1_1") (pintype "passive"))
      (node (ref "R325") (pin "2") (pinfunction "2_2") (pintype "passive"))
      (node (ref "R326") (pin "2") (pinfunction "2_2") (pintype "passive"))
      (node (ref "R327") (pin "2") (pinfunction "2_2") (pintype "passive"))
      (node (ref "R328") (pin "2") (pinfunction "2_2") (pintype "passive"))
      (node (ref "R347") (pin "1") (pinfunction "1_1") (pintype "passive"))
      (node (ref "R348") (pin "1") (pinfunction "1_1") (pintype "passive"))
      (node (ref "R35") (pin "1") (pinfunction "1_1") (pintype "passive"))
      (node (ref "R353") (pin "1") (pinfunction "1_1") (pintype "passive"))
      (node (ref "R371") (pin "2") (pinfunction "2_2") (pintype "passive"))
      (node (ref "R372") (pin "2") (pinfunction "2_2") (pintype "passive"))
      (node (ref "R373") (pin "2") (pinfunction "2_2") (pintype "passive"))
      (node (ref "R374") (pin "2") (pinfunction "2_2") (pintype "passive"))
      (node (ref "R393") (pin "1") (pinfunction "1_1") (pintype "passive"))
      (node (ref "R394") (pin "1") (pinfunction "1_1") (pintype "passive"))
      (node (ref "R399") (pin "1") (pinfunction "1_1") (pintype "passive"))
      (node (ref "R417") (pin "2") (pinfunction "2_2") (pintype "passive"))
      (node (ref "R418") (pin "2") (pinfunction "2_2") (pintype "passive"))
      (node (ref "R419") (pin "2") (pinfunction "2_2") (pintype "passive"))
      (node (ref "R420") (pin "2") (pinfunction "2_2") (pintype "passive"))
      (node (ref "R439") (pin "1") (pinfunction "1_1") (pintype "passive"))
      (node (ref "R440") (pin "1") (pinfunction "1_1") (pintype "passive"))
      (node (ref "R445") (pin "1") (pinfunction "1_1") (pintype "passive"))
      (node (ref "R463") (pin "2") (pinfunction "2_2") (pintype "passive"))
      (node (ref "R464") (pin "2") (pinfunction "2_2") (pintype "passive"))
      (node (ref "R465") (pin "2") (pinfunction "2_2") (pintype "passive"))
      (node (ref "R466") (pin "2") (pinfunction "2_2") (pintype "passive"))
      (node (ref "R485") (pin "1") (pinfunction "1_1") (pintype "passive"))
      (node (ref "R486") (pin "1") (pinfunction "1_1") (pintype "passive"))
      (node (ref "R49") (pin "2") (pinfunction "2_2") (pintype "passive"))
      (node (ref "R491") (pin "1") (pinfunction "1_1") (pintype "passive"))
      (node (ref "R50") (pin "2") (pinfunction "2_2") (pintype "passive"))
      (node (ref "R509") (pin "2") (pinfunction "2_2") (pintype "passive"))
      (node (ref "R51") (pin "2") (pinfunction "2_2") (pintype "passive"))
      (node (ref "R510") (pin "2") (pinfunction "2_2") (pintype "passive"))
      (node (ref "R511") (pin "2") (pinfunction "2_2") (pintype "passive"))
      (node (ref "R512") (pin "2") (pinfunction "2_2") (pintype "passive"))
      (node (ref "R52") (pin "2") (pinfunction "2_2") (pintype "passive"))
      (node (ref "R531") (pin "1") (pinfunction "1_1") (pintype "passive"))
      (node (ref "R532") (pin "1") (pinfunction "1_1") (pintype "passive"))
      (node (ref "R537") (pin "1") (pinfunction "1_1") (pintype "passive"))
      (node (ref "R6") (pin "1") (pinfunction "1_1") (pintype "passive"))
      (node (ref "R71") (pin "1") (pinfunction "1_1") (pintype "passive"))
      (node (ref "R72") (pin "1") (pinfunction "1_1") (pintype "passive"))
      (node (ref "R77") (pin "1") (pinfunction "1_1") (pintype "passive"))
      (node (ref "R9") (pin "2") (pinfunction "2_2") (pintype "passive"))
      (node (ref "R95") (pin "2") (pinfunction "2_2") (pintype "passive"))
      (node (ref "R96") (pin "2") (pinfunction "2_2") (pintype "passive"))
      (node (ref "R97") (pin "2") (pinfunction "2_2") (pintype "passive"))
      (node (ref "R98") (pin "2") (pinfunction "2_2") (pintype "passive"))
      (node (ref "TP114") (pin "TP") (pinfunction "PP_TP") (pintype "input"))
      (node (ref "TP12") (pin "TP") (pinfunction "PP_TP") (pintype "input"))
      (node (ref "TP137") (pin "TP") (pinfunction "PP_TP") (pintype "input"))
      (node (ref "TP160") (pin "TP") (pinfunction "PP_TP") (pintype "input"))
      (node (ref "TP183") (pin "TP") (pinfunction "PP_TP") (pintype "input"))
      (node (ref "TP206") (pin "TP") (pinfunction "PP_TP") (pintype "input"))
      (node (ref "TP229") (pin "TP") (pinfunction "PP_TP") (pintype "input"))
      (node (ref "TP252") (pin "TP") (pinfunction "PP_TP") (pintype "input"))
      (node (ref "TP275") (pin "TP") (pinfunction "PP_TP") (pintype "input"))
      (node (ref "TP45") (pin "TP") (pinfunction "PP_TP") (pintype "input"))
      (node (ref "TP68") (pin "TP") (pinfunction "PP_TP") (pintype "input"))
      (node (ref "TP91") (pin "TP") (pinfunction "PP_TP") (pintype "input"))
      (node (ref "X1") (pin "6") (pinfunction "6_6") (pintype "passive"))
      (node (ref "X10") (pin "6") (pinfunction "6_6") (pintype "passive"))
      (node (ref "X11") (pin "1") (pinfunction "S_1") (pintype "passive"))
      (node (ref "X13") (pin "6") (pinfunction "6_6") (pintype "passive"))
      (node (ref "X14") (pin "1") (pinfunction "S_1") (pintype "passive"))
      (node (ref "X16") (pin "6") (pinfunction "6_6") (pintype "passive"))
      (node (ref "X17") (pin "1") (pinfunction "S_1") (pintype "passive"))
      (node (ref "X19") (pin "6") (pinfunction "6_6") (pintype "passive"))
      (node (ref "X20") (pin "1") (pinfunction "S_1") (pintype "passive"))
      (node (ref "X22") (pin "6") (pinfunction "6_6") (pintype "passive"))
      (node (ref "X23") (pin "1") (pinfunction "S_1") (pintype "passive"))
      (node (ref "X25") (pin "6") (pinfunction "6_6") (pintype "passive"))
      (node (ref "X26") (pin "1") (pinfunction "S_1") (pintype "passive"))
      (node (ref "X28") (pin "6") (pinfunction "6_6") (pintype "passive"))
      (node (ref "X29") (pin "1") (pinfunction "S_1") (pintype "passive"))
      (node (ref "X3") (pin "1") (pinfunction "S_1") (pintype "passive"))
      (node (ref "X31") (pin "6") (pinfunction "6_6") (pintype "passive"))
      (node (ref "X32") (pin "1") (pinfunction "S_1") (pintype "passive"))
      (node (ref "X34") (pin "6") (pinfunction "6_6") (pintype "passive"))
      (node (ref "X35") (pin "1") (pinfunction "S_1") (pintype "passive"))
      (node (ref "X4") (pin "6") (pinfunction "6_6") (pintype "passive"))
      (node (ref "X5") (pin "1") (pinfunction "S_1") (pintype "passive"))
      (node (ref "X7") (pin "6") (pinfunction "6_6") (pintype "passive"))
      (node (ref "X8") (pin "1") (pinfunction "S_1") (pintype "passive"))
    )
    (net (code "3") (name "GND") (class "Default")
      (node (ref "1") (pin "12") (pinfunction "KL_12") (pintype "passive"))
      (node (ref "11") (pin "12") (pinfunction "KL_12") (pintype "passive"))
      (node (ref "13") (pin "12") (pinfunction "KL_12") (pintype "passive"))
      (node (ref "15") (pin "12") (pinfunction "KL_12") (pintype "passive"))
      (node (ref "17") (pin "12") (pinfunction "KL_12") (pintype "passive"))
      (node (ref "19") (pin "12") (pinfunction "KL_12") (pintype "passive"))
      (node (ref "21") (pin "12") (pinfunction "KL_12") (pintype "passive"))
      (node (ref "23") (pin "12") (pinfunction "KL_12") (pintype "passive"))
      (node (ref "3") (pin "12") (pinfunction "KL_12") (pintype "passive"))
      (node (ref "5") (pin "12") (pinfunction "KL_12") (pintype "passive"))
      (node (ref "7") (pin "12") (pinfunction "KL_12") (pintype "passive"))
      (node (ref "9") (pin "12") (pinfunction "KL_12") (pintype "passive"))
      (node (ref "C1") (pin "2") (pinfunction "2_2") (pintype "passive"))
      (node (ref "C10") (pin "2") (pinfunction "2_2") (pintype "passive"))
      (node (ref "C100") (pin "2") (pinfunction "2_2") (pintype "passive"))
      (node (ref "C101") (pin "2") (pinfunction "2_2") (pintype "passive"))
      (node (ref "C102") (pin "2") (pinfunction "2_2") (pintype "passive"))
      (node (ref "C103") (pin "2") (pinfunction "2_2") (pintype "passive"))
      (node (ref "C104") (pin "2") (pinfunction "2_2") (pintype "passive"))
      (node (ref "C105") (pin "2") (pinfunction "2_2") (pintype "passive"))
      (node (ref "C106") (pin "1") (pinfunction "1_1") (pintype "passive"))
      (node (ref "C107") (pin "1") (pinfunction "1_1") (pintype "passive"))
      (node (ref "C108") (pin "2") (pinfunction "2_2") (pintype "passive"))
      (node (ref "C109") (pin "2") (pinfunction "2_2") (pintype "passive"))
      (node (ref "C11") (pin "2") (pinfunction "2_2") (pintype "passive"))
      (node (ref "C110") (pin "2") (pinfunction "2_2") (pintype "passive"))
      (node (ref "C111") (pin "2") (pinfunction "2_2") (pintype "passive"))
      (node (ref "C112") (pin "2") (pinfunction "2_2") (pintype "passive"))
      (node (ref "C113") (pin "2") (pinfunction "2_2") (pintype "passive"))
      (node (ref "C114") (pin "2") (pinfunction "2_2") (pintype "passive"))
      (node (ref "C115") (pin "2") (pinfunction "2_2") (pintype "passive"))
      (node (ref "C116") (pin "1") (pinfunction "1_1") (pintype "passive"))
      (node (ref "C117") (pin "1") (pinfunction "1_1") (pintype "passive"))
      (node (ref "C118") (pin "2") (pinfunction "2_2") (pintype "passive"))
      (node (ref "C119") (pin "2") (pinfunction "2_2") (pintype "passive"))
      (node (ref "C12") (pin "2") (pinfunction "2_2") (pintype "passive"))
      (node (ref "C120") (pin "2") (pinfunction "2_2") (pintype "passive"))
      (node (ref "C13") (pin "2") (pinfunction "2_2") (pintype "passive"))
      (node (ref "C14") (pin "2") (pinfunction "2_2") (pintype "passive"))
      (node (ref "C15") (pin "2") (pinfunction "2_2") (pintype "passive"))
      (node (ref "C16") (pin "1") (pinfunction "1_1") (pintype "passive"))
      (node (ref "C17") (pin "1") (pinfunction "1_1") (pintype "passive"))
      (node (ref "C18") (pin "2") (pinfunction "2_2") (pintype "passive"))
      (node (ref "C19") (pin "2") (pinfunction "2_2") (pintype "passive"))
      (node (ref "C2") (pin "2") (pinfunction "2_2") (pintype "passive"))
      (node (ref "C20") (pin "2") (pinfunction "2_2") (pintype "passive"))
      (node (ref "C21") (pin "2") (pinfunction "2_2") (pintype "passive"))
      (node (ref "C22") (pin "2") (pinfunction "2_2") (pintype "passive"))
      (node (ref "C23") (pin "2") (pinfunction "2_2") (pintype "passive"))
      (node (ref "C24") (pin "2") (pinfunction "2_2") (pintype "passive"))
      (node (ref "C25") (pin "2") (pinfunction "2_2") (pintype "passive"))
      (node (ref "C26") (pin "1") (pinfunction "1_1") (pintype "passive"))
      (node (ref "C27") (pin "1") (pinfunction "1_1") (pintype "passive"))
      (node (ref "C28") (pin "2") (pinfunction "2_2") (pintype "passive"))
      (node (ref "C29") (pin "2") (pinfunction "2_2") (pintype "passive"))
      (node (ref "C3") (pin "2") (pinfunction "2_2") (pintype "passive"))
      (node (ref "C30") (pin "2") (pinfunction "2_2") (pintype "passive"))
      (node (ref "C31") (pin "2") (pinfunction "2_2") (pintype "passive"))
      (node (ref "C32") (pin "2") (pinfunction "2_2") (pintype "passive"))
      (node (ref "C33") (pin "2") (pinfunction "2_2") (pintype "passive"))
      (node (ref "C34") (pin "2") (pinfunction "2_2") (pintype "passive"))
      (node (ref "C35") (pin "2") (pinfunction "2_2") (pintype "passive"))
      (node (ref "C36") (pin "1") (pinfunction "1_1") (pintype "passive"))
      (node (ref "C37") (pin "1") (pinfunction "1_1") (pintype "passive"))
      (node (ref "C38") (pin "2") (pinfunction "2_2") (pintype "passive"))
      (node (ref "C39") (pin "2") (pinfunction "2_2") (pintype "passive"))
      (node (ref "C4") (pin "2") (pinfunction "2_2") (pintype "passive"))
      (node (ref "C40") (pin "2") (pinfunction "2_2") (pintype "passive"))
      (node (ref "C41") (pin "2") (pinfunction "2_2") (pintype "passive"))
      (node (ref "C42") (pin "2") (pinfunction "2_2") (pintype "passive"))
      (node (ref "C43") (pin "2") (pinfunction "2_2") (pintype "passive"))
      (node (ref "C44") (pin "2") (pinfunction "2_2") (pintype "passive"))
      (node (ref "C45") (pin "2") (pinfunction "2_2") (pintype "passive"))
      (node (ref "C46") (pin "1") (pinfunction "1_1") (pintype "passive"))
      (node (ref "C47") (pin "1") (pinfunction "1_1") (pintype "passive"))
      (node (ref "C48") (pin "2") (pinfunction "2_2") (pintype "passive"))
      (node (ref "C49") (pin "2") (pinfunction "2_2") (pintype "passive"))
      (node (ref "C5") (pin "2") (pinfunction "2_2") (pintype "passive"))
      (node (ref "C50") (pin "2") (pinfunction "2_2") (pintype "passive"))
      (node (ref "C51") (pin "2") (pinfunction "2_2") (pintype "passive"))
      (node (ref "C52") (pin "2") (pinfunction "2_2") (pintype "passive"))
      (node (ref "C53") (pin "2") (pinfunction "2_2") (pintype "passive"))
      (node (ref "C54") (pin "2") (pinfunction "2_2") (pintype "passive"))
      (node (ref "C55") (pin "2") (pinfunction "2_2") (pintype "passive"))
      (node (ref "C56") (pin "1") (pinfunction "1_1") (pintype "passive"))
      (node (ref "C57") (pin "1") (pinfunction "1_1") (pintype "passive"))
      (node (ref "C58") (pin "2") (pinfunction "2_2") (pintype "passive"))
      (node (ref "C59") (pin "2") (pinfunction "2_2") (pintype "passive"))
      (node (ref "C6") (pin "1") (pinfunction "1_1") (pintype "passive"))
      (node (ref "C60") (pin "2") (pinfunction "2_2") (pintype "passive"))
      (node (ref "C61") (pin "2") (pinfunction "2_2") (pintype "passive"))
      (node (ref "C62") (pin "2") (pinfunction "2_2") (pintype "passive"))
      (node (ref "C63") (pin "2") (pinfunction "2_2") (pintype "passive"))
      (node (ref "C64") (pin "2") (pinfunction "2_2") (pintype "passive"))
      (node (ref "C65") (pin "2") (pinfunction "2_2") (pintype "passive"))
      (node (ref "C66") (pin "1") (pinfunction "1_1") (pintype "passive"))
      (node (ref "C67") (pin "1") (pinfunction "1_1") (pintype "passive"))
      (node (ref "C68") (pin "2") (pinfunction "2_2") (pintype "passive"))
      (node (ref "C69") (pin "2") (pinfunction "2_2") (pintype "passive"))
      (node (ref "C7") (pin "2") (pinfunction "2_2") (pintype "passive"))
      (node (ref "C70") (pin "2") (pinfunction "2_2") (pintype "passive"))
      (node (ref "C71") (pin "2") (pinfunction "2_2") (pintype "passive"))
      (node (ref "C72") (pin "2") (pinfunction "2_2") (pintype "passive"))
      (node (ref "C73") (pin "2") (pinfunction "2_2") (pintype "passive"))
      (node (ref "C74") (pin "2") (pinfunction "2_2") (pintype "passive"))
      (node (ref "C75") (pin "2") (pinfunction "2_2") (pintype "passive"))
      (node (ref "C76") (pin "1") (pinfunction "1_1") (pintype "passive"))
      (node (ref "C77") (pin "1") (pinfunction "1_1") (pintype "passive"))
      (node (ref "C78") (pin "2") (pinfunction "2_2") (pintype "passive"))
      (node (ref "C79") (pin "2") (pinfunction "2_2") (pintype "passive"))
      (node (ref "C8") (pin "2") (pinfunction "2_2") (pintype "passive"))
      (node (ref "C80") (pin "2") (pinfunction "2_2") (pintype "passive"))
      (node (ref "C81") (pin "2") (pinfunction "2_2") (pintype "passive"))
      (node (ref "C82") (pin "2") (pinfunction "2_2") (pintype "passive"))
      (node (ref "C83") (pin "2") (pinfunction "2_2") (pintype "passive"))
      (node (ref "C84") (pin "2") (pinfunction "2_2") (pintype "passive"))
      (node (ref "C85") (pin "2") (pinfunction "2_2") (pintype "passive"))
      (node (ref "C86") (pin "1") (pinfunction "1_1") (pintype "passive"))
      (node (ref "C87") (pin "1") (pinfunction "1_1") (pintype "passive"))
      (node (ref "C88") (pin "2") (pinfunction "2_2") (pintype "passive"))
      (node (ref "C89") (pin "2") (pinfunction "2_2") (pintype "passive"))
      (node (ref "C9") (pin "1") (pinfunction "1_1") (pintype "passive"))
      (node (ref "C90") (pin "2") (pinfunction "2_2") (pintype "passive"))
      (node (ref "C91") (pin "2") (pinfunction "2_2") (pintype "passive"))
      (node (ref "C92") (pin "2") (pinfunction "2_2") (pintype "passive"))
      (node (ref "C93") (pin "2") (pinfunction "2_2") (pintype "passive"))
      (node (ref "C94") (pin "2") (pinfunction "2_2") (pintype "passive"))
      (node (ref "C95") (pin "2") (pinfunction "2_2") (pintype "passive"))
      (node (ref "C96") (pin "1") (pinfunction "1_1") (pintype "passive"))
      (node (ref "C97") (pin "1") (pinfunction "1_1") (pintype "passive"))
      (node (ref "C98") (pin "2") (pinfunction "2_2") (pintype "passive"))
      (node (ref "C99") (pin "2") (pinfunction "2_2") (pintype "passive"))
      (node (ref "D1") (pin "A") (pinfunction "A_A") (pintype "passive"))
      (node (ref "D105") (pin "1") (pinfunction "+_1") (pintype "passive"))
      (node (ref "D107") (pin "A") (pinfunction "A_A") (pintype "passive"))
      (node (ref "D108") (pin "A") (pinfunction "A_A") (pintype "passive"))
      (node (ref "D117") (pin "1") (pinfunction "+_1") (pintype "passive"))
      (node (ref "D119") (pin "A") (pinfunction "A_A") (pintype "passive"))
      (node (ref "D120") (pin "A") (pinfunction "A_A") (pintype "passive"))
      (node (ref "D129") (pin "1") (pinfunction "+_1") (pintype "passive"))
      (node (ref "D131") (pin "A") (pinfunction "A_A") (pintype "passive"))
      (node (ref "D132") (pin "A") (pinfunction "A_A") (pintype "passive"))
      (node (ref "D141") (pin "1") (pinfunction "+_1") (pintype "passive"))
      (node (ref "D143") (pin "A") (pinfunction "A_A") (pintype "passive"))
      (node (ref "D144") (pin "A") (pinfunction "A_A") (pintype "passive"))
      (node (ref "D21") (pin "1") (pinfunction "+_1") (pintype "passive"))
      (node (ref "D23") (pin "A") (pinfunction "A_A") (pintype "passive"))
      (node (ref "D24") (pin "A") (pinfunction "A_A") (pintype "passive"))
      (node (ref "D33") (pin "1") (pinfunction "+_1") (pintype "passive"))
      (node (ref "D35") (pin "A") (pinfunction "A_A") (pintype "passive"))
      (node (ref "D36") (pin "A") (pinfunction "A_A") (pintype "passive"))
      (node (ref "D4") (pin "A") (pinfunction "A_A") (pintype "passive"))
      (node (ref "D45") (pin "1") (pinfunction "+_1") (pintype "passive"))
      (node (ref "D47") (pin "A") (pinfunction "A_A") (pintype "passive"))
      (node (ref "D48") (pin "A") (pinfunction "A_A") (pintype "passive"))
      (node (ref "D5") (pin "1") (pinfunction "+_1") (pintype "passive"))
      (node (ref "D57") (pin "1") (pinfunction "+_1") (pintype "passive"))
      (node (ref "D59") (pin "A") (pinfunction "A_A") (pintype "passive"))
      (node (ref "D60") (pin "A") (pinfunction "A_A") (pintype "passive"))
      (node (ref "D69") (pin "1") (pinfunction "+_1") (pintype "passive"))
      (node (ref "D71") (pin "A") (pinfunction "A_A") (pintype "passive"))
      (node (ref "D72") (pin "A") (pinfunction "A_A") (pintype "passive"))
      (node (ref "D81") (pin "1") (pinfunction "+_1") (pintype "passive"))
      (node (ref "D83") (pin "A") (pinfunction "A_A") (pintype "passive"))
      (node (ref "D84") (pin "A") (pinfunction "A_A") (pintype "passive"))
      (node (ref "D93") (pin "1") (pinfunction "+_1") (pintype "passive"))
      (node (ref "D95") (pin "A") (pinfunction "A_A") (pintype "passive"))
      (node (ref "D96") (pin "A") (pinfunction "A_A") (pintype "passive"))
      (node (ref "IC1") (pin "4") (pinfunction "V-_4") (pintype "power_in"))
      (node (ref "IC10") (pin "1") (pinfunction "GND_1") (pintype "power_in"))
      (node (ref "IC100") (pin "11") (pinfunction "D_11") (pintype "input"))
      (node (ref "IC100") (pin "8") (pinfunction "VSS_8") (pintype "power_in"))
      (node (ref "IC101") (pin "GND") (pinfunction "GND_GND") (pintype "input"))
      (node (ref "IC103") (pin "8") (pinfunction "GND_8") (pintype "power_in"))
      (node (ref "IC104") (pin "10") (pinfunction "-IN_10") (pintype "input"))
      (node (ref "IC104") (pin "11") (pinfunction "+IN_11") (pintype "input"))
      (node (ref "IC104") (pin "12") (pinfunction "GND_12") (pintype "power_in"))
      (node (ref "IC105") (pin "2") (pinfunction "GND_2") (pintype "input"))
      (node (ref "IC105") (pin "2@1") (pinfunction "GND_2@1") (pintype "input"))
      (node (ref "IC106") (pin "1") (pinfunction "GND_1") (pintype "power_in"))
      (node (ref "IC107") (pin "1") (pinfunction "T1_1") (pintype "input"))
      (node (ref "IC107") (pin "15") (pinfunction "T1_15") (pintype "input"))
      (node (ref "IC107") (pin "4") (pinfunction "A_4") (pintype "input"))
      (node (ref "IC107") (pin "8") (pinfunction "VSS_8") (pintype "power_in"))
      (node (ref "IC108") (pin "2") (pinfunction "GND_2") (pintype "input"))
      (node (ref "IC108") (pin "2@1") (pinfunction "GND_2@1") (pintype "input"))
      (node (ref "IC109") (pin "4") (pinfunction "V-_4") (pintype "power_in"))
      (node (ref "IC11") (pin "1") (pinfunction "T1_1") (pintype "input"))
      (node (ref "IC11") (pin "15") (pinfunction "T1_15") (pintype "input"))
      (node (ref "IC11") (pin "4") (pinfunction "A_4") (pintype "input"))
      (node (ref "IC11") (pin "8") (pinfunction "VSS_8") (pintype "power_in"))
      (node (ref "IC110") (pin "5") (pinfunction "V-_5") (pintype "passive"))
      (node (ref "IC111") (pin "11") (pinfunction "D_11") (pintype "input"))
      (node (ref "IC111") (pin "8") (pinfunction "VSS_8") (pintype "power_in"))
      (node (ref "IC112") (pin "GND") (pinfunction "GND_GND") (pintype "input"))
      (node (ref "IC114") (pin "8") (pinfunction "GND_8") (pintype "power_in"))
      (node (ref "IC115") (pin "10") (pinfunction "-IN_10") (pintype "input"))
      (node (ref "IC115") (pin "11") (pinfunction "+IN_11") (pintype "input"))
      (node (ref "IC115") (pin "12") (pinfunction "GND_12") (pintype "power_in"))
      (node (ref "IC116") (pin "2") (pinfunction "GND_2") (pintype "input"))
      (node (ref "IC116") (pin "2@1") (pinfunction "GND_2@1") (pintype "input"))
      (node (ref "IC117") (pin "1") (pinfunction "GND_1") (pintype "power_in"))
      (node (ref "IC118") (pin "1") (pinfunction "T1_1") (pintype "input"))
      (node (ref "IC118") (pin "15") (pinfunction "T1_15") (pintype "input"))
      (node (ref "IC118") (pin "4") (pinfunction "A_4") (pintype "input"))
      (node (ref "IC118") (pin "8") (pinfunction "VSS_8") (pintype "power_in"))
      (node (ref "IC119") (pin "2") (pinfunction "GND_2") (pintype "input"))
      (node (ref "IC119") (pin "2@1") (pinfunction "GND_2@1") (pintype "input"))
      (node (ref "IC12") (pin "11") (pinfunction "D_11") (pintype "input"))
      (node (ref "IC12") (pin "8") (pinfunction "VSS_8") (pintype "power_in"))
      (node (ref "IC120") (pin "4") (pinfunction "V-_4") (pintype "power_in"))
      (node (ref "IC121") (pin "5") (pinfunction "V-_5") (pintype "passive"))
      (node (ref "IC122") (pin "11") (pinfunction "D_11") (pintype "input"))
      (node (ref "IC122") (pin "8") (pinfunction "VSS_8") (pintype "power_in"))
      (node (ref "IC123") (pin "GND") (pinfunction "GND_GND") (pintype "input"))
      (node (ref "IC125") (pin "8") (pinfunction "GND_8") (pintype "power_in"))
      (node (ref "IC126") (pin "10") (pinfunction "-IN_10") (pintype "input"))
      (node (ref "IC126") (pin "11") (pinfunction "+IN_11") (pintype "input"))
      (node (ref "IC126") (pin "12") (pinfunction "GND_12") (pintype "power_in"))
      (node (ref "IC127") (pin "2") (pinfunction "GND_2") (pintype "input"))
      (node (ref "IC127") (pin "2@1") (pinfunction "GND_2@1") (pintype "input"))
      (node (ref "IC128") (pin "1") (pinfunction "GND_1") (pintype "power_in"))
      (node (ref "IC129") (pin "1") (pinfunction "T1_1") (pintype "input"))
      (node (ref "IC129") (pin "15") (pinfunction "T1_15") (pintype "input"))
      (node (ref "IC129") (pin "4") (pinfunction "A_4") (pintype "input"))
      (node (ref "IC129") (pin "8") (pinfunction "VSS_8") (pintype "power_in"))
      (node (ref "IC13") (pin "GND") (pinfunction "GND_GND") (pintype "input"))
      (node (ref "IC130") (pin "2") (pinfunction "GND_2") (pintype "input"))
      (node (ref "IC130") (pin "2@1") (pinfunction "GND_2@1") (pintype "input"))
      (node (ref "IC131") (pin "4") (pinfunction "V-_4") (pintype "power_in"))
      (node (ref "IC132") (pin "5") (pinfunction "V-_5") (pintype "passive"))
      (node (ref "IC15") (pin "8") (pinfunction "GND_8") (pintype "power_in"))
      (node (ref "IC16") (pin "10") (pinfunction "-IN_10") (pintype "input"))
      (node (ref "IC16") (pin "11") (pinfunction "+IN_11") (pintype "input"))
      (node (ref "IC16") (pin "12") (pinfunction "GND_12") (pintype "power_in"))
      (node (ref "IC17") (pin "2") (pinfunction "GND_2") (pintype "input"))
      (node (ref "IC17") (pin "2@1") (pinfunction "GND_2@1") (pintype "input"))
      (node (ref "IC18") (pin "1") (pinfunction "GND_1") (pintype "power_in"))
      (node (ref "IC19") (pin "1") (pinfunction "T1_1") (pintype "input"))
      (node (ref "IC19") (pin "15") (pinfunction "T1_15") (pintype "input"))
      (node (ref "IC19") (pin "4") (pinfunction "A_4") (pintype "input"))
      (node (ref "IC19") (pin "8") (pinfunction "VSS_8") (pintype "power_in"))
      (node (ref "IC2") (pin "2") (pinfunction "GND_2") (pintype "input"))
      (node (ref "IC2") (pin "2@1") (pinfunction "GND_2@1") (pintype "input"))
      (node (ref "IC20") (pin "2") (pinfunction "GND_2") (pintype "input"))
      (node (ref "IC20") (pin "2@1") (pinfunction "GND_2@1") (pintype "input"))
      (node (ref "IC21") (pin "4") (pinfunction "V-_4") (pintype "power_in"))
      (node (ref "IC22") (pin "5") (pinfunction "V-_5") (pintype "passive"))
      (node (ref "IC23") (pin "11") (pinfunction "D_11") (pintype "input"))
      (node (ref "IC23") (pin "8") (pinfunction "VSS_8") (pintype "power_in"))
      (node (ref "IC24") (pin "GND") (pinfunction "GND_GND") (pintype "input"))
      (node (ref "IC26") (pin "8") (pinfunction "GND_8") (pintype "power_in"))
      (node (ref "IC27") (pin "10") (pinfunction "-IN_10") (pintype "input"))
      (node (ref "IC27") (pin "11") (pinfunction "+IN_11") (pintype "input"))
      (node (ref "IC27") (pin "12") (pinfunction "GND_12") (pintype "power_in"))
      (node (ref "IC28") (pin "2") (pinfunction "GND_2") (pintype "input"))
      (node (ref "IC28") (pin "2@1") (pinfunction "GND_2@1") (pintype "input"))
      (node (ref "IC29") (pin "1") (pinfunction "GND_1") (pintype "power_in"))
      (node (ref "IC3") (pin "GND") (pinfunction "GND_GND") (pintype "input"))
      (node (ref "IC30") (pin "1") (pinfunction "T1_1") (pintype "input"))
      (node (ref "IC30") (pin "15") (pinfunction "T1_15") (pintype "input"))
      (node (ref "IC30") (pin "4") (pinfunction "A_4") (pintype "input"))
      (node (ref "IC30") (pin "8") (pinfunction "VSS_8") (pintype "power_in"))
      (node (ref "IC31") (pin "2") (pinfunction "GND_2") (pintype "input"))
      (node (ref "IC31") (pin "2@1") (pinfunction "GND_2@1") (pintype "input"))
      (node (ref "IC32") (pin "4") (pinfunction "V-_4") (pintype "power_in"))
      (node (ref "IC33") (pin "5") (pinfunction "V-_5") (pintype "passive"))
      (node (ref "IC34") (pin "11") (pinfunction "D_11") (pintype "input"))
      (node (ref "IC34") (pin "8") (pinfunction "VSS_8") (pintype "power_in"))
      (node (ref "IC35") (pin "GND") (pinfunction "GND_GND") (pintype "input"))
      (node (ref "IC37") (pin "8") (pinfunction "GND_8") (pintype "power_in"))
      (node (ref "IC38") (pin "10") (pinfunction "-IN_10") (pintype "input"))
      (node (ref "IC38") (pin "11") (pinfunction "+IN_11") (pintype "input"))
      (node (ref "IC38") (pin "12") (pinfunction "GND_12") (pintype "power_in"))
      (node (ref "IC39") (pin "2") (pinfunction "GND_2") (pintype "input"))
      (node (ref "IC39") (pin "2@1") (pinfunction "GND_2@1") (pintype "input"))
      (node (ref "IC4") (pin "2") (pinfunction "GND_2") (pintype "input"))
      (node (ref "IC4") (pin "2@1") (pinfunction "GND_2@1") (pintype "input"))
      (node (ref "IC40") (pin "1") (pinfunction "GND_1") (pintype "power_in"))
      (node (ref "IC41") (pin "1") (pinfunction "T1_1") (pintype "input"))
      (node (ref "IC41") (pin "15") (pinfunction "T1_15") (pintype "input"))
      (node (ref "IC41") (pin "4") (pinfunction "A_4") (pintype "input"))
      (node (ref "IC41") (pin "8") (pinfunction "VSS_8") (pintype "power_in"))
      (node (ref "IC42") (pin "2") (pinfunction "GND_2") (pintype "input"))
      (node (ref "IC42") (pin "2@1") (pinfunction "GND_2@1") (pintype "input"))
      (node (ref "IC43") (pin "4") (pinfunction "V-_4") (pintype "power_in"))
      (node (ref "IC44") (pin "5") (pinfunction "V-_5") (pintype "passive"))
      (node (ref "IC45") (pin "11") (pinfunction "D_11") (pintype "input"))
      (node (ref "IC45") (pin "8") (pinfunction "VSS_8") (pintype "power_in"))
      (node (ref "IC46") (pin "GND") (pinfunction "GND_GND") (pintype "input"))
      (node (ref "IC48") (pin "8") (pinfunction "GND_8") (pintype "power_in"))
      (node (ref "IC49") (pin "10") (pinfunction "-IN_10") (pintype "input"))
      (node (ref "IC49") (pin "11") (pinfunction "+IN_11") (pintype "input"))
      (node (ref "IC49") (pin "12") (pinfunction "GND_12") (pintype "power_in"))
      (node (ref "IC5") (pin "11") (pinfunction "D_11") (pintype "input"))
      (node (ref "IC5") (pin "8") (pinfunction "VSS_8") (pintype "power_in"))
      (node (ref "IC50") (pin "2") (pinfunction "GND_2") (pintype "input"))
      (node (ref "IC50") (pin "2@1") (pinfunction "GND_2@1") (pintype "input"))
      (node (ref "IC51") (pin "1") (pinfunction "GND_1") (pintype "power_in"))
      (node (ref "IC52") (pin "1") (pinfunction "T1_1") (pintype "input"))
      (node (ref "IC52") (pin "15") (pinfunction "T1_15") (pintype "input"))
      (node (ref "IC52") (pin "4") (pinfunction "A_4") (pintype "input"))
      (node (ref "IC52") (pin "8") (pinfunction "VSS_8") (pintype "power_in"))
      (node (ref "IC53") (pin "2") (pinfunction "GND_2") (pintype "input"))
      (node (ref "IC53") (pin "2@1") (pinfunction "GND_2@1") (pintype "input"))
      (node (ref "IC54") (pin "4") (pinfunction "V-_4") (pintype "power_in"))
      (node (ref "IC55") (pin "5") (pinfunction "V-_5") (pintype "passive"))
      (node (ref "IC56") (pin "11") (pinfunction "D_11") (pintype "input"))
      (node (ref "IC56") (pin "8") (pinfunction "VSS_8") (pintype "power_in"))
      (node (ref "IC57") (pin "GND") (pinfunction "GND_GND") (pintype "input"))
      (node (ref "IC59") (pin "8") (pinfunction "GND_8") (pintype "power_in"))
      (node (ref "IC6") (pin "5") (pinfunction "V-_5") (pintype "passive"))
      (node (ref "IC60") (pin "10") (pinfunction "-IN_10") (pintype "input"))
      (node (ref "IC60") (pin "11") (pinfunction "+IN_11") (pintype "input"))
      (node (ref "IC60") (pin "12") (pinfunction "GND_12") (pintype "power_in"))
      (node (ref "IC61") (pin "2") (pinfunction "GND_2") (pintype "input"))
      (node (ref "IC61") (pin "2@1") (pinfunction "GND_2@1") (pintype "input"))
      (node (ref "IC62") (pin "1") (pinfunction "GND_1") (pintype "power_in"))
      (node (ref "IC63") (pin "1") (pinfunction "T1_1") (pintype "input"))
      (node (ref "IC63") (pin "15") (pinfunction "T1_15") (pintype "input"))
      (node (ref "IC63") (pin "4") (pinfunction "A_4") (pintype "input"))
      (node (ref "IC63") (pin "8") (pinfunction "VSS_8") (pintype "power_in"))
      (node (ref "IC64") (pin "2") (pinfunction "GND_2") (pintype "input"))
      (node (ref "IC64") (pin "2@1") (pinfunction "GND_2@1") (pintype "input"))
      (node (ref "IC65") (pin "4") (pinfunction "V-_4") (pintype "power_in"))
      (node (ref "IC66") (pin "5") (pinfunction "V-_5") (pintype "passive"))
      (node (ref "IC67") (pin "11") (pinfunction "D_11") (pintype "input"))
      (node (ref "IC67") (pin "8") (pinfunction "VSS_8") (pintype "power_in"))
      (node (ref "IC68") (pin "GND") (pinfunction "GND_GND") (pintype "input"))
      (node (ref "IC7") (pin "8") (pinfunction "GND_8") (pintype "power_in"))
      (node (ref "IC70") (pin "8") (pinfunction "GND_8") (pintype "power_in"))
      (node (ref "IC71") (pin "10") (pinfunction "-IN_10") (pintype "input"))
      (node (ref "IC71") (pin "11") (pinfunction "+IN_11") (pintype "input"))
      (node (ref "IC71") (pin "12") (pinfunction "GND_12") (pintype "power_in"))
      (node (ref "IC72") (pin "2") (pinfunction "GND_2") (pintype "input"))
      (node (ref "IC72") (pin "2@1") (pinfunction "GND_2@1") (pintype "input"))
      (node (ref "IC73") (pin "1") (pinfunction "GND_1") (pintype "power_in"))
      (node (ref "IC74") (pin "1") (pinfunction "T1_1") (pintype "input"))
      (node (ref "IC74") (pin "15") (pinfunction "T1_15") (pintype "input"))
      (node (ref "IC74") (pin "4") (pinfunction "A_4") (pintype "input"))
      (node (ref "IC74") (pin "8") (pinfunction "VSS_8") (pintype "power_in"))
      (node (ref "IC75") (pin "2") (pinfunction "GND_2") (pintype "input"))
      (node (ref "IC75") (pin "2@1") (pinfunction "GND_2@1") (pintype "input"))
      (node (ref "IC76") (pin "4") (pinfunction "V-_4") (pintype "power_in"))
      (node (ref "IC77") (pin "5") (pinfunction "V-_5") (pintype "passive"))
      (node (ref "IC78") (pin "11") (pinfunction "D_11") (pintype "input"))
      (node (ref "IC78") (pin "8") (pinfunction "VSS_8") (pintype "power_in"))
      (node (ref "IC79") (pin "GND") (pinfunction "GND_GND") (pintype "input"))
      (node (ref "IC8") (pin "10") (pinfunction "-IN_10") (pintype "input"))
      (node (ref "IC8") (pin "11") (pinfunction "+IN_11") (pintype "input"))
      (node (ref "IC8") (pin "12") (pinfunction "GND_12") (pintype "power_in"))
      (node (ref "IC81") (pin "8") (pinfunction "GND_8") (pintype "power_in"))
      (node (ref "IC82") (pin "10") (pinfunction "-IN_10") (pintype "input"))
      (node (ref "IC82") (pin "11") (pinfunction "+IN_11") (pintype "input"))
      (node (ref "IC82") (pin "12") (pinfunction "GND_12") (pintype "power_in"))
      (node (ref "IC83") (pin "2") (pinfunction "GND_2") (pintype "input"))
      (node (ref "IC83") (pin "2@1") (pinfunction "GND_2@1") (pintype "input"))
      (node (ref "IC84") (pin "1") (pinfunction "GND_1") (pintype "power_in"))
      (node (ref "IC85") (pin "1") (pinfunction "T1_1") (pintype "input"))
      (node (ref "IC85") (pin "15") (pinfunction "T1_15") (pintype "input"))
      (node (ref "IC85") (pin "4") (pinfunction "A_4") (pintype "input"))
      (node (ref "IC85") (pin "8") (pinfunction "VSS_8") (pintype "power_in"))
      (node (ref "IC86") (pin "2") (pinfunction "GND_2") (pintype "input"))
      (node (ref "IC86") (pin "2@1") (pinfunction "GND_2@1") (pintype "input"))
      (node (ref "IC87") (pin "4") (pinfunction "V-_4") (pintype "power_in"))
      (node (ref "IC88") (pin "5") (pinfunction "V-_5") (pintype "passive"))
      (node (ref "IC89") (pin "11") (pinfunction "D_11") (pintype "input"))
      (node (ref "IC89") (pin "8") (pinfunction "VSS_8") (pintype "power_in"))
      (node (ref "IC90") (pin "GND") (pinfunction "GND_GND") (pintype "input"))
      (node (ref "IC92") (pin "8") (pinfunction "GND_8") (pintype "power_in"))
      (node (ref "IC93") (pin "10") (pinfunction "-IN_10") (pintype "input"))
      (node (ref "IC93") (pin "11") (pinfunction "+IN_11") (pintype "input"))
      (node (ref "IC93") (pin "12") (pinfunction "GND_12") (pintype "power_in"))
      (node (ref "IC94") (pin "2") (pinfunction "GND_2") (pintype "input"))
      (node (ref "IC94") (pin "2@1") (pinfunction "GND_2@1") (pintype "input"))
      (node (ref "IC95") (pin "1") (pinfunction "GND_1") (pintype "power_in"))
      (node (ref "IC96") (pin "1") (pinfunction "T1_1") (pintype "input"))
      (node (ref "IC96") (pin "15") (pinfunction "T1_15") (pintype "input"))
      (node (ref "IC96") (pin "4") (pinfunction "A_4") (pintype "input"))
      (node (ref "IC96") (pin "8") (pinfunction "VSS_8") (pintype "power_in"))
      (node (ref "IC97") (pin "2") (pinfunction "GND_2") (pintype "input"))
      (node (ref "IC97") (pin "2@1") (pinfunction "GND_2@1") (pintype "input"))
      (node (ref "IC98") (pin "4") (pinfunction "V-_4") (pintype "power_in"))
      (node (ref "IC99") (pin "5") (pinfunction "V-_5") (pintype "passive"))
      (node (ref "Q12") (pin "3") (pinfunction "E_3") (pintype "passive"))
      (node (ref "Q13") (pin "2") (pinfunction "S_2") (pintype "passive"))
      (node (ref "Q14") (pin "2") (pinfunction "S_2") (pintype "passive"))
      (node (ref "Q19") (pin "3") (pinfunction "E_3") (pintype "passive"))
      (node (ref "Q20") (pin "2") (pinfunction "S_2") (pintype "passive"))
      (node (ref "Q21") (pin "2") (pinfunction "S_2") (pintype "passive"))
      (node (ref "Q26") (pin "3") (pinfunction "E_3") (pintype "passive"))
      (node (ref "Q27") (pin "2") (pinfunction "S_2") (pintype "passive"))
      (node (ref "Q28") (pin "2") (pinfunction "S_2") (pintype "passive"))
      (node (ref "Q3") (pin "3") (pinfunction "E_3") (pintype "passive"))
      (node (ref "Q33") (pin "3") (pinfunction "E_3") (pintype "passive"))
      (node (ref "Q34") (pin "2") (pinfunction "S_2") (pintype "passive"))
      (node (ref "Q35") (pin "2") (pinfunction "S_2") (pintype "passive"))
      (node (ref "Q40") (pin "3") (pinfunction "E_3") (pintype "passive"))
      (node (ref "Q41") (pin "2") (pinfunction "S_2") (pintype "passive"))
      (node (ref "Q42") (pin "2") (pinfunction "S_2") (pintype "passive"))
      (node (ref "Q47") (pin "3") (pinfunction "E_3") (pintype "passive"))
      (node (ref "Q48") (pin "2") (pinfunction "S_2") (pintype "passive"))
      (node (ref "Q49") (pin "2") (pinfunction "S_2") (pintype "passive"))
      (node (ref "Q54") (pin "3") (pinfunction "E_3") (pintype "passive"))
      (node (ref "Q55") (pin "2") (pinfunction "S_2") (pintype "passive"))
      (node (ref "Q56") (pin "2") (pinfunction "S_2") (pintype "passive"))
      (node (ref "Q6") (pin "2") (pinfunction "S_2") (pintype "passive"))
      (node (ref "Q61") (pin "3") (pinfunction "E_3") (pintype "passive"))
      (node (ref "Q62") (pin "2") (pinfunction "S_2") (pintype "passive"))
      (node (ref "Q63") (pin "2") (pinfunction "S_2") (pintype "passive"))
      (node (ref "Q68") (pin "3") (pinfunction "E_3") (pintype "passive"))
      (node (ref "Q69") (pin "2") (pinfunction "S_2") (pintype "passive"))
      (node (ref "Q7") (pin "2") (pinfunction "S_2") (pintype "passive"))
      (node (ref "Q70") (pin "2") (pinfunction "S_2") (pintype "passive"))
      (node (ref "Q75") (pin "3") (pinfunction "E_3") (pintype "passive"))
      (node (ref "Q76") (pin "2") (pinfunction "S_2") (pintype "passive"))
      (node (ref "Q77") (pin "2") (pinfunction "S_2") (pintype "passive"))
      (node (ref "Q82") (pin "3") (pinfunction "E_3") (pintype "passive"))
      (node (ref "Q83") (pin "2") (pinfunction "S_2") (pintype "passive"))
      (node (ref "Q84") (pin "2") (pinfunction "S_2") (pintype "passive"))
      (node (ref "R1") (pin "2") (pinfunction "2_2") (pintype "passive"))
      (node (ref "R100") (pin "1") (pinfunction "1_1") (pintype "passive"))
      (node (ref "R106") (pin "1") (pinfunction "1_1") (pintype "passive"))
      (node (ref "R110") (pin "1") (pinfunction "1_1") (pintype "passive"))
      (node (ref "R111") (pin "2") (pinfunction "2_2") (pintype "passive"))
      (node (ref "R112") (pin "2") (pinfunction "2_2") (pintype "passive"))
      (node (ref "R114") (pin "2") (pinfunction "2_2") (pintype "passive"))
      (node (ref "R122") (pin "2") (pinfunction "2_2") (pintype "passive"))
      (node (ref "R124") (pin "2") (pinfunction "2_2") (pintype "passive"))
      (node (ref "R127") (pin "1") (pinfunction "1_1") (pintype "passive"))
      (node (ref "R128") (pin "1") (pinfunction "1_1") (pintype "passive"))
      (node (ref "R136") (pin "1") (pinfunction "1_1") (pintype "passive"))
      (node (ref "R138") (pin "2") (pinfunction "2_2") (pintype "passive"))
      (node (ref "R14") (pin "1") (pinfunction "1_1") (pintype "passive"))
      (node (ref "R146") (pin "1") (pinfunction "1_1") (pintype "passive"))
      (node (ref "R152") (pin "1") (pinfunction "1_1") (pintype "passive"))
      (node (ref "R156") (pin "1") (pinfunction "1_1") (pintype "passive"))
      (node (ref "R157") (pin "2") (pinfunction "2_2") (pintype "passive"))
      (node (ref "R158") (pin "2") (pinfunction "2_2") (pintype "passive"))
      (node (ref "R160") (pin "2") (pinfunction "2_2") (pintype "passive"))
      (node (ref "R168") (pin "2") (pinfunction "2_2") (pintype "passive"))
      (node (ref "R170") (pin "2") (pinfunction "2_2") (pintype "passive"))
      (node (ref "R173") (pin "1") (pinfunction "1_1") (pintype "passive"))
      (node (ref "R174") (pin "1") (pinfunction "1_1") (pintype "passive"))
      (node (ref "R182") (pin "1") (pinfunction "1_1") (pintype "passive"))
      (node (ref "R184") (pin "2") (pinfunction "2_2") (pintype "passive"))
      (node (ref "R192") (pin "1") (pinfunction "1_1") (pintype "passive"))
      (node (ref "R198") (pin "1") (pinfunction "1_1") (pintype "passive"))
      (node (ref "R202") (pin "1") (pinfunction "1_1") (pintype "passive"))
      (node (ref "R203") (pin "2") (pinfunction "2_2") (pintype "passive"))
      (node (ref "R204") (pin "2") (pinfunction "2_2") (pintype "passive"))
      (node (ref "R206") (pin "2") (pinfunction "2_2") (pintype "passive"))
      (node (ref "R214") (pin "2") (pinfunction "2_2") (pintype "passive"))
      (node (ref "R216") (pin "2") (pinfunction "2_2") (pintype "passive"))
      (node (ref "R219") (pin "1") (pinfunction "1_1") (pintype "passive"))
      (node (ref "R220") (pin "1") (pinfunction "1_1") (pintype "passive"))
      (node (ref "R228") (pin "1") (pinfunction "1_1") (pintype "passive"))
      (node (ref "R23") (pin "1") (pinfunction "1_1") (pintype "passive"))
      (node (ref "R230") (pin "2") (pinfunction "2_2") (pintype "passive"))
      (node (ref "R238") (pin "1") (pinfunction "1_1") (pintype "passive"))
      (node (ref "R244") (pin "1") (pinfunction "1_1") (pintype "passive"))
      (node (ref "R248") (pin "1") (pinfunction "1_1") (pintype "passive"))
      (node (ref "R249") (pin "2") (pinfunction "2_2") (pintype "passive"))
      (node (ref "R250") (pin "2") (pinfunction "2_2") (pintype "passive"))
      (node (ref "R252") (pin "2") (pinfunction "2_2") (pintype "passive"))
      (node (ref "R260") (pin "2") (pinfunction "2_2") (pintype "passive"))
      (node (ref "R262") (pin "2") (pinfunction "2_2") (pintype "passive"))
      (node (ref "R265") (pin "1") (pinfunction "1_1") (pintype "passive"))
      (node (ref "R266") (pin "1") (pinfunction "1_1") (pintype "passive"))
      (node (ref "R274") (pin "1") (pinfunction "1_1") (pintype "passive"))
      (node (ref "R276") (pin "2") (pinfunction "2_2") (pintype "passive"))
      (node (ref "R284") (pin "1") (pinfunction "1_1") (pintype "passive"))
      (node (ref "R290") (pin "1") (pinfunction "1_1") (pintype "passive"))
      (node (ref "R294") (pin "1") (pinfunction "1_1") (pintype "passive"))
      (node (ref "R295") (pin "2") (pinfunction "2_2") (pintype "passive"))
      (node (ref "R296") (pin "2") (pinfunction "2_2") (pintype "passive"))
      (node (ref "R298") (pin "2") (pinfunction "2_2") (pintype "passive"))
      (node (ref "R3") (pin "2") (pinfunction "2_2") (pintype "passive"))
      (node (ref "R306") (pin "2") (pinfunction "2_2") (pintype "passive"))
      (node (ref "R308") (pin "2") (pinfunction "2_2") (pintype "passive"))
      (node (ref "R311") (pin "1") (pinfunction "1_1") (pintype "passive"))
      (node (ref "R312") (pin "1") (pinfunction "1_1") (pintype "passive"))
      (node (ref "R32") (pin "1") (pinfunction "1_1") (pintype "passive"))
      (node (ref "R320") (pin "1") (pinfunction "1_1") (pintype "passive"))
      (node (ref "R322") (pin "2") (pinfunction "2_2") (pintype "passive"))
      (node (ref "R330") (pin "1") (pinfunction "1_1") (pintype "passive"))
      (node (ref "R336") (pin "1") (pinfunction "1_1") (pintype "passive"))
      (node (ref "R340") (pin "1") (pinfunction "1_1") (pintype "passive"))
      (node (ref "R341") (pin "2") (pinfunction "2_2") (pintype "passive"))
      (node (ref "R342") (pin "2") (pinfunction "2_2") (pintype "passive"))
      (node (ref "R344") (pin "2") (pinfunction "2_2") (pintype "passive"))
      (node (ref "R352") (pin "2") (pinfunction "2_2") (pintype "passive"))
      (node (ref "R354") (pin "2") (pinfunction "2_2") (pintype "passive"))
      (node (ref "R357") (pin "1") (pinfunction "1_1") (pintype "passive"))
      (node (ref "R358") (pin "1") (pinfunction "1_1") (pintype "passive"))
      (node (ref "R36") (pin "1") (pinfunction "1_1") (pintype "passive"))
      (node (ref "R366") (pin "1") (pinfunction "1_1") (pintype "passive"))
      (node (ref "R368") (pin "2") (pinfunction "2_2") (pintype "passive"))
      (node (ref "R37") (pin "1") (pinfunction "1_1") (pintype "passive"))
      (node (ref "R376") (pin "1") (pinfunction "1_1") (pintype "passive"))
      (node (ref "R382") (pin "1") (pinfunction "1_1") (pintype "passive"))
      (node (ref "R386") (pin "1") (pinfunction "1_1") (pintype "passive"))
      (node (ref "R387") (pin "2") (pinfunction "2_2") (pintype "passive"))
      (node (ref "R388") (pin "2") (pinfunction "2_2") (pintype "passive"))
      (node (ref "R39") (pin "2") (pinfunction "2_2") (pintype "passive"))
      (node (ref "R390") (pin "2") (pinfunction "2_2") (pintype "passive"))
      (node (ref "R398") (pin "2") (pinfunction "2_2") (pintype "passive"))
      (node (ref "R4") (pin "2") (pinfunction "2_2") (pintype "passive"))
      (node (ref "R400") (pin "2") (pinfunction "2_2") (pintype "passive"))
      (node (ref "R403") (pin "1") (pinfunction "1_1") (pintype "passive"))
      (node (ref "R404") (pin "1") (pinfunction "1_1") (pintype "passive"))
      (node (ref "R41") (pin "2") (pinfunction "2_2") (pintype "passive"))
      (node (ref "R412") (pin "1") (pinfunction "1_1") (pintype "passive"))
      (node (ref "R414") (pin "2") (pinfunction "2_2") (pintype "passive"))
      (node (ref "R422") (pin "1") (pinfunction "1_1") (pintype "passive"))
      (node (ref "R428") (pin "1") (pinfunction "1_1") (pintype "passive"))
      (node (ref "R43") (pin "2") (pinfunction "2_2") (pintype "passive"))
      (node (ref "R432") (pin "1") (pinfunction "1_1") (pintype "passive"))
      (node (ref "R433") (pin "2") (pinfunction "2_2") (pintype "passive"))
      (node (ref "R434") (pin "2") (pinfunction "2_2") (pintype "passive"))
      (node (ref "R436") (pin "2") (pinfunction "2_2") (pintype "passive"))
      (node (ref "R444") (pin "2") (pinfunction "2_2") (pintype "passive"))
      (node (ref "R446") (pin "2") (pinfunction "2_2") (pintype "passive"))
      (node (ref "R449") (pin "1") (pinfunction "1_1") (pintype "passive"))
      (node (ref "R450") (pin "1") (pinfunction "1_1") (pintype "passive"))
      (node (ref "R458") (pin "1") (pinfunction "1_1") (pintype "passive"))
      (node (ref "R460") (pin "2") (pinfunction "2_2") (pintype "passive"))
      (node (ref "R468") (pin "1") (pinfunction "1_1") (pintype "passive"))
      (node (ref "R474") (pin "1") (pinfunction "1_1") (pintype "passive"))
      (node (ref "R478") (pin "1") (pinfunction "1_1") (pintype "passive"))
      (node (ref "R479") (pin "2") (pinfunction "2_2") (pintype "passive"))
      (node (ref "R480") (pin "2") (pinfunction "2_2") (pintype "passive"))
      (node (ref "R482") (pin "2") (pinfunction "2_2") (pintype "passive"))
      (node (ref "R490") (pin "2") (pinfunction "2_2") (pintype "passive"))
      (node (ref "R492") (pin "2") (pinfunction "2_2") (pintype "passive"))
      (node (ref "R495") (pin "1") (pinfunction "1_1") (pintype "passive"))
      (node (ref "R496") (pin "1") (pinfunction "1_1") (pintype "passive"))
      (node (ref "R504") (pin "1") (pinfunction "1_1") (pintype "passive"))
      (node (ref "R506") (pin "2") (pinfunction "2_2") (pintype "passive"))
      (node (ref "R514") (pin "1") (pinfunction "1_1") (pintype "passive"))
      (node (ref "R520") (pin "1") (pinfunction "1_1") (pintype "passive"))
      (node (ref "R524") (pin "1") (pinfunction "1_1") (pintype "passive"))
      (node (ref "R525") (pin "2") (pinfunction "2_2") (pintype "passive"))
      (node (ref "R526") (pin "2") (pinfunction "2_2") (pintype "passive"))
      (node (ref "R528") (pin "2") (pinfunction "2_2") (pintype "passive"))
      (node (ref "R536") (pin "2") (pinfunction "2_2") (pintype "passive"))
      (node (ref "R538") (pin "2") (pinfunction "2_2") (pintype "passive"))
      (node (ref "R54") (pin "1") (pinfunction "1_1") (pintype "passive"))
      (node (ref "R541") (pin "1") (pinfunction "1_1") (pintype "passive"))
      (node (ref "R542") (pin "1") (pinfunction "1_1") (pintype "passive"))
      (node (ref "R550") (pin "1") (pinfunction "1_1") (pintype "passive"))
      (node (ref "R552") (pin "2") (pinfunction "2_2") (pintype "passive"))
      (node (ref "R60") (pin "1") (pinfunction "1_1") (pintype "passive"))
      (node (ref "R64") (pin "1") (pinfunction "1_1") (pintype "passive"))
      (node (ref "R65") (pin "2") (pinfunction "2_2") (pintype "passive"))
      (node (ref "R66") (pin "2") (pinfunction "2_2") (pintype "passive"))
      (node (ref "R68") (pin "2") (pinfunction "2_2") (pintype "passive"))
      (node (ref "R7") (pin "1") (pinfunction "1_1") (pintype "passive"))
      (node (ref "R76") (pin "2") (pinfunction "2_2") (pintype "passive"))
      (node (ref "R78") (pin "2") (pinfunction "2_2") (pintype "passive"))
      (node (ref "R81") (pin "1") (pinfunction "1_1") (pintype "passive"))
      (node (ref "R82") (pin "1") (pinfunction "1_1") (pintype "passive"))
      (node (ref "R90") (pin "1") (pinfunction "1_1") (pintype "passive"))
      (node (ref "R92") (pin "2") (pinfunction "2_2") (pintype "passive"))
      (node (ref "X1") (pin "13") (pinfunction "13_13") (pintype "passive"))
      (node (ref "X1") (pin "18") (pinfunction "18_18") (pintype "passive"))
      (node (ref "X1") (pin "23") (pinfunction "23_23") (pintype "passive"))
      (node (ref "X10") (pin "13") (pinfunction "13_13") (pintype "passive"))
      (node (ref "X10") (pin "18") (pinfunction "18_18") (pintype "passive"))
      (node (ref "X10") (pin "23") (pinfunction "23_23") (pintype "passive"))
      (node (ref "X11") (pin "5") (pinfunction "S_5") (pintype "passive"))
      (node (ref "X12") (pin "1") (pinfunction "S_1") (pintype "passive"))
      (node (ref "X13") (pin "13") (pinfunction "13_13") (pintype "passive"))
      (node (ref "X13") (pin "18") (pinfunction "18_18") (pintype "passive"))
      (node (ref "X13") (pin "23") (pinfunction "23_23") (pintype "passive"))
      (node (ref "X14") (pin "5") (pinfunction "S_5") (pintype "passive"))
      (node (ref "X15") (pin "1") (pinfunction "S_1") (pintype "passive"))
      (node (ref "X16") (pin "13") (pinfunction "13_13") (pintype "passive"))
      (node (ref "X16") (pin "18") (pinfunction "18_18") (pintype "passive"))
      (node (ref "X16") (pin "23") (pinfunction "23_23") (pintype "passive"))
      (node (ref "X17") (pin "5") (pinfunction "S_5") (pintype "passive"))
      (node (ref "X18") (pin "1") (pinfunction "S_1") (pintype "passive"))
      (node (ref "X19") (pin "13") (pinfunction "13_13") (pintype "passive"))
      (node (ref "X19") (pin "18") (pinfunction "18_18") (pintype "passive"))
      (node (ref "X19") (pin "23") (pinfunction "23_23") (pintype "passive"))
      (node (ref "X2") (pin "1") (pinfunction "S_1") (pintype "passive"))
      (node (ref "X20") (pin "5") (pinfunction "S_5") (pintype "passive"))
      (node (ref "X21") (pin "1") (pinfunction "S_1") (pintype "passive"))
      (node (ref "X22") (pin "13") (pinfunction "13_13") (pintype "passive"))
      (node (ref "X22") (pin "18") (pinfunction "18_18") (pintype "passive"))
      (node (ref "X22") (pin "23") (pinfunction "23_23") (pintype "passive"))
      (node (ref "X23") (pin "5") (pinfunction "S_5") (pintype "passive"))
      (node (ref "X24") (pin "1") (pinfunction "S_1") (pintype "passive"))
      (node (ref "X25") (pin "13") (pinfunction "13_13") (pintype "passive"))
      (node (ref "X25") (pin "18") (pinfunction "18_18") (pintype "passive"))
      (node (ref "X25") (pin "23") (pinfunction "23_23") (pintype "passive"))
      (node (ref "X26") (pin "5") (pinfunction "S_5") (pintype "passive"))
      (node (ref "X27") (pin "1") (pinfunction "S_1") (pintype "passive"))
      (node (ref "X28") (pin "13") (pinfunction "13_13") (pintype "passive"))
      (node (ref "X28") (pin "18") (pinfunction "18_18") (pintype "passive"))
      (node (ref "X28") (pin "23") (pinfunction "23_23") (pintype "passive"))
      (node (ref "X29") (pin "5") (pinfunction "S_5") (pintype "passive"))
      (node (ref "X3") (pin "5") (pinfunction "S_5") (pintype "passive"))
      (node (ref "X30") (pin "1") (pinfunction "S_1") (pintype "passive"))
      (node (ref "X31") (pin "13") (pinfunction "13_13") (pintype "passive"))
      (node (ref "X31") (pin "18") (pinfunction "18_18") (pintype "passive"))
      (node (ref "X31") (pin "23") (pinfunction "23_23") (pintype "passive"))
      (node (ref "X32") (pin "5") (pinfunction "S_5") (pintype "passive"))
      (node (ref "X33") (pin "1") (pinfunction "S_1") (pintype "passive"))
      (node (ref "X34") (pin "13") (pinfunction "13_13") (pintype "passive"))
      (node (ref "X34") (pin "18") (pinfunction "18_18") (pintype "passive"))
      (node (ref "X34") (pin "23") (pinfunction "23_23") (pintype "passive"))
      (node (ref "X35") (pin "5") (pinfunction "S_5") (pintype "passive"))
      (node (ref "X36") (pin "1") (pinfunction "S_1") (pintype "passive"))
      (node (ref "X4") (pin "13") (pinfunction "13_13") (pintype "passive"))
      (node (ref "X4") (pin "18") (pinfunction "18_18") (pintype "passive"))
      (node (ref "X4") (pin "23") (pinfunction "23_23") (pintype "passive"))
      (node (ref "X5") (pin "5") (pinfunction "S_5") (pintype "passive"))
      (node (ref "X6") (pin "1") (pinfunction "S_1") (pintype "passive"))
      (node (ref "X7") (pin "13") (pinfunction "13_13") (pintype "passive"))
      (node (ref "X7") (pin "18") (pinfunction "18_18") (pintype "passive"))
      (node (ref "X7") (pin "23") (pinfunction "23_23") (pintype "passive"))
      (node (ref "X8") (pin "5") (pinfunction "S_5") (pintype "passive"))
      (node (ref "X9") (pin "1") (pinfunction "S_1") (pintype "passive"))
    )
    (net (code "4") (name "Net-(1A-KL)") (class "Default")
      (node (ref "1") (pin "1") (pinfunction "KL_1") (pintype "passive"))
      (node (ref "TP1") (pin "TP") (pinfunction "PP_TP") (pintype "input"))
      (node (ref "X1") (pin "1") (pinfunction "1_1") (pintype "passive"))
    )
    (net (code "5") (name "Net-(1B-KL)") (class "Default")
      (node (ref "1") (pin "10") (pinfunction "KL_10") (pintype "passive"))
      (node (ref "D2") (pin "2") (pinfunction "-_2") (pintype "passive"))
      (node (ref "D3") (pin "2") (pinfunction "-_2") (pintype "passive"))
      (node (ref "JP4") (pin "1") (pinfunction "1_1") (pintype "passive"))
      (node (ref "SJ1") (pin "1") (pinfunction "1_1") (pintype "passive"))
      (node (ref "TP10") (pin "TP") (pinfunction "PP_TP") (pintype "input"))
    )
    (net (code "6") (name "Net-(1C-KL)") (class "Default")
      (node (ref "1") (pin "11") (pinfunction "KL_11") (pintype "passive"))
      (node (ref "D3") (pin "1") (pinfunction "+_1") (pintype "passive"))
      (node (ref "TP11") (pin "TP") (pinfunction "PP_TP") (pintype "input"))
      (node (ref "X1") (pin "19") (pinfunction "19_19") (pintype "passive"))
    )
    (net (code "7") (name "Net-(1E-KL)") (class "Default")
      (node (ref "1") (pin "2") (pinfunction "KL_2") (pintype "passive"))
      (node (ref "Q1") (pin "2") (pinfunction "C_2") (pintype "passive"))
      (node (ref "TP2") (pin "TP") (pinfunction "PP_TP") (pintype "input"))
    )
    (net (code "8") (name "Net-(1F-KL)") (class "Default")
      (node (ref "1") (pin "3") (pinfunction "KL_3") (pintype "passive"))
      (node (ref "IC7") (pin "11") (pinfunction "O6_11") (pintype "open_collector"))
      (node (ref "TP3") (pin "TP") (pinfunction "PP_TP") (pintype "input"))
    )
    (net (code "9") (name "Net-(1G-KL)") (class "Default")
      (node (ref "1") (pin "4") (pinfunction "KL_4") (pintype "passive"))
      (node (ref "IC7") (pin "10") (pinfunction "O7_10") (pintype "open_collector"))
      (node (ref "TP4") (pin "TP") (pinfunction "PP_TP") (pintype "input"))
    )
    (net (code "10") (name "Net-(1H-KL)") (class "Default")
      (node (ref "1") (pin "5") (pinfunction "KL_5") (pintype "passive"))
      (node (ref "IC7") (pin "12") (pinfunction "O5_12") (pintype "open_collector"))
      (node (ref "TP5") (pin "TP") (pinfunction "PP_TP") (pintype "input"))
    )
    (net (code "11") (name "Net-(1I-KL)") (class "Default")
      (node (ref "1") (pin "6") (pinfunction "KL_6") (pintype "passive"))
      (node (ref "IC7") (pin "13") (pinfunction "O4_13") (pintype "open_collector"))
      (node (ref "TP6") (pin "TP") (pinfunction "PP_TP") (pintype "input"))
    )
    (net (code "12") (name "Net-(1J-KL)") (class "Default")
      (node (ref "1") (pin "7") (pinfunction "KL_7") (pintype "passive"))
      (node (ref "IC7") (pin "14") (pinfunction "O3_14") (pintype "open_collector"))
      (node (ref "TP7") (pin "TP") (pinfunction "PP_TP") (pintype "input"))
    )
    (net (code "13") (name "Net-(1K-KL)") (class "Default")
      (node (ref "1") (pin "8") (pinfunction "KL_8") (pintype "passive"))
      (node (ref "Q6") (pin "3") (pinfunction "D_3") (pintype "passive"))
      (node (ref "TP8") (pin "TP") (pinfunction "PP_TP") (pintype "input"))
    )
    (net (code "14") (name "Net-(1L-KL)") (class "Default")
      (node (ref "1") (pin "9") (pinfunction "KL_9") (pintype "passive"))
      (node (ref "D2") (pin "1") (pinfunction "+_1") (pintype "passive"))
      (node (ref "TP9") (pin "TP") (pinfunction "PP_TP") (pintype "input"))
      (node (ref "X1") (pin "17") (pinfunction "17_17") (pintype "passive"))
    )
    (net (code "15") (name "Net-(2B-KL)") (class "Default")
      (node (ref "2") (pin "10") (pinfunction "KL_10") (pintype "passive"))
      (node (ref "TP25") (pin "TP") (pinfunction "PP_TP") (pintype "input"))
      (node (ref "X1") (pin "15") (pinfunction "15_15") (pintype "passive"))
    )
    (net (code "16") (name "Net-(2C-KL)") (class "Default")
      (node (ref "2") (pin "11") (pinfunction "KL_11") (pintype "passive"))
      (node (ref "IC7") (pin "16") (pinfunction "O1_16") (pintype "open_collector"))
      (node (ref "R18") (pin "2") (pinfunction "2_2") (pintype "passive"))
      (node (ref "R19") (pin "1") (pinfunction "1_1") (pintype "passive"))
      (node (ref "TP26") (pin "TP") (pinfunction "PP_TP") (pintype "input"))
    )
    (net (code "17") (name "Net-(2D-KL)") (class "Default")
      (node (ref "2") (pin "12") (pinfunction "KL_12") (pintype "passive"))
      (node (ref "R46") (pin "1") (pinfunction "1_1") (pintype "passive"))
      (node (ref "TP13") (pin "TP") (pinfunction "PP_TP") (pintype "input"))
    )
    (net (code "18") (name "Net-(2E-KL)") (class "Default")
      (node (ref "2") (pin "2") (pinfunction "KL_2") (pintype "passive"))
      (node (ref "D9") (pin "2") (pinfunction "-_2") (pintype "passive"))
      (node (ref "LED2") (pin "K") (pinfunction "C_K") (pintype "passive"))
      (node (ref "TP16") (pin "TP") (pinfunction "PP_TP") (pintype "input"))
      (node (ref "X1") (pin "12") (pinfunction "12_12") (pintype "passive"))
    )
    (net (code "19") (name "Net-(2F-KL)") (class "Default")
      (node (ref "2") (pin "3") (pinfunction "KL_3") (pintype "passive"))
      (node (ref "D8") (pin "2") (pinfunction "-_2") (pintype "passive"))
      (node (ref "LED3") (pin "K") (pinfunction "C_K") (pintype "passive"))
      (node (ref "TP17") (pin "TP") (pinfunction "PP_TP") (pintype "input"))
      (node (ref "X1") (pin "11") (pinfunction "11_11") (pintype "passive"))
    )
    (net (code "20") (name "Net-(2G-KL)") (class "Default")
      (node (ref "2") (pin "4") (pinfunction "KL_4") (pintype "passive"))
      (node (ref "D7") (pin "2") (pinfunction "-_2") (pintype "passive"))
      (node (ref "LED4") (pin "K") (pinfunction "C_K") (pintype "passive"))
      (node (ref "TP18") (pin "TP") (pinfunction "PP_TP") (pintype "input"))
      (node (ref "X1") (pin "10") (pinfunction "10_10") (pintype "passive"))
    )
    (net (code "21") (name "Net-(2H-KL)") (class "Default")
      (node (ref "2") (pin "5") (pinfunction "KL_5") (pintype "passive"))
      (node (ref "D6") (pin "2") (pinfunction "-_2") (pintype "passive"))
      (node (ref "LED5") (pin "K") (pinfunction "C_K") (pintype "passive"))
      (node (ref "TP19") (pin "TP") (pinfunction "PP_TP") (pintype "input"))
      (node (ref "X1") (pin "9") (pinfunction "9_9") (pintype "passive"))
    )
    (net (code "22") (name "Net-(2I-KL)") (class "Default")
      (node (ref "2") (pin "6") (pinfunction "KL_6") (pintype "passive"))
      (node (ref "JP5") (pin "2") (pinfunction "2_2") (pintype "passive"))
      (node (ref "TP21") (pin "TP") (pinfunction "PP_TP") (pintype "input"))
    )
    (net (code "23") (name "Net-(2J-KL)") (class "Default")
      (node (ref "2") (pin "7") (pinfunction "KL_7") (pintype "passive"))
      (node (ref "LED1") (pin "A") (pinfunction "A_A") (pintype "passive"))
      (node (ref "TP22") (pin "TP") (pinfunction "PP_TP") (pintype "input"))
      (node (ref "X1") (pin "8") (pinfunction "8_8") (pintype "passive"))
    )
    (net (code "24") (name "Net-(2K-KL)") (class "Default")
      (node (ref "2") (pin "8") (pinfunction "KL_8") (pintype "passive"))
      (node (ref "D10") (pin "2") (pinfunction "-_2") (pintype "passive"))
      (node (ref "LED6") (pin "K") (pinfunction "C_K") (pintype "passive"))
      (node (ref "TP23") (pin "TP") (pinfunction "PP_TP") (pintype "input"))
      (node (ref "X1") (pin "14") (pinfunction "14_14") (pintype "passive"))
    )
    (net (code "25") (name "Net-(2L-KL)") (class "Default")
      (node (ref "2") (pin "9") (pinfunction "KL_9") (pintype "passive"))
      (node (ref "D7") (pin "1") (pinfunction "+_1") (pintype "passive"))
      (node (ref "D8") (pin "1") (pinfunction "+_1") (pintype "passive"))
      (node (ref "JP2") (pin "1") (pinfunction "1_1") (pintype "passive"))
      (node (ref "JP3") (pin "2") (pinfunction "2_2") (pintype "passive"))
      (node (ref "TP24") (pin "TP") (pinfunction "PP_TP") (pintype "input"))
    )
    (net (code "26") (name "Net-(3A-KL)") (class "Default")
      (node (ref "3") (pin "1") (pinfunction "KL_1") (pintype "passive"))
      (node (ref "TP14") (pin "TP") (pinfunction "PP_TP") (pintype "input"))
      (node (ref "X4") (pin "1") (pinfunction "1_1") (pintype "passive"))
    )
    (net (code "27") (name "Net-(3B-KL)") (class "Default")
      (node (ref "3") (pin "10") (pinfunction "KL_10") (pintype "passive"))
      (node (ref "D14") (pin "2") (pinfunction "-_2") (pintype "passive"))
      (node (ref "D15") (pin "2") (pinfunction "-_2") (pintype "passive"))
      (node (ref "JP10") (pin "1") (pinfunction "1_1") (pintype "passive"))
      (node (ref "SJ2") (pin "1") (pinfunction "1_1") (pintype "passive"))
      (node (ref "TP33") (pin "TP") (pinfunction "PP_TP") (pintype "input"))
    )
    (net (code "28") (name "Net-(3C-KL)") (class "Default")
      (node (ref "3") (pin "11") (pinfunction "KL_11") (pintype "passive"))
      (node (ref "D15") (pin "1") (pinfunction "+_1") (pintype "passive"))
      (node (ref "TP34") (pin "TP") (pinfunction "PP_TP") (pintype "input"))
      (node (ref "X4") (pin "19") (pinfunction "19_19") (pintype "passive"))
    )
    (net (code "29") (name "Net-(3E-KL)") (class "Default")
      (node (ref "3") (pin "2") (pinfunction "KL_2") (pintype "passive"))
      (node (ref "Q10") (pin "2") (pinfunction "C_2") (pintype "passive"))
      (node (ref "TP15") (pin "TP") (pinfunction "PP_TP") (pintype "input"))
    )
    (net (code "30") (name "Net-(3F-KL)") (class "Default")
      (node (ref "3") (pin "3") (pinfunction "KL_3") (pintype "passive"))
      (node (ref "IC15") (pin "11") (pinfunction "O6_11") (pintype "open_collector"))
      (node (ref "TP20") (pin "TP") (pinfunction "PP_TP") (pintype "input"))
    )
    (net (code "31") (name "Net-(3G-KL)") (class "Default")
      (node (ref "3") (pin "4") (pinfunction "KL_4") (pintype "passive"))
      (node (ref "IC15") (pin "10") (pinfunction "O7_10") (pintype "open_collector"))
      (node (ref "TP27") (pin "TP") (pinfunction "PP_TP") (pintype "input"))
    )
    (net (code "32") (name "Net-(3H-KL)") (class "Default")
      (node (ref "3") (pin "5") (pinfunction "KL_5") (pintype "passive"))
      (node (ref "IC15") (pin "12") (pinfunction "O5_12") (pintype "open_collector"))
      (node (ref "TP28") (pin "TP") (pinfunction "PP_TP") (pintype "input"))
    )
    (net (code "33") (name "Net-(3I-KL)") (class "Default")
      (node (ref "3") (pin "6") (pinfunction "KL_6") (pintype "passive"))
      (node (ref "IC15") (pin "13") (pinfunction "O4_13") (pintype "open_collector"))
      (node (ref "TP29") (pin "TP") (pinfunction "PP_TP") (pintype "input"))
    )
    (net (code "34") (name "Net-(3J-KL)") (class "Default")
      (node (ref "3") (pin "7") (pinfunction "KL_7") (pintype "passive"))
      (node (ref "IC15") (pin "14") (pinfunction "O3_14") (pintype "open_collector"))
      (node (ref "TP30") (pin "TP") (pinfunction "PP_TP") (pintype "input"))
    )
    (net (code "35") (name "Net-(3K-KL)") (class "Default")
      (node (ref "3") (pin "8") (pinfunction "KL_8") (pintype "passive"))
      (node (ref "Q14") (pin "3") (pinfunction "D_3") (pintype "passive"))
      (node (ref "TP31") (pin "TP") (pinfunction "PP_TP") (pintype "input"))
    )
    (net (code "36") (name "Net-(3L-KL)") (class "Default")
      (node (ref "3") (pin "9") (pinfunction "KL_9") (pintype "passive"))
      (node (ref "D14") (pin "1") (pinfunction "+_1") (pintype "passive"))
      (node (ref "TP32") (pin "TP") (pinfunction "PP_TP") (pintype "input"))
      (node (ref "X4") (pin "17") (pinfunction "17_17") (pintype "passive"))
    )
    (net (code "37") (name "Net-(4B-KL)") (class "Default")
      (node (ref "4") (pin "10") (pinfunction "KL_10") (pintype "passive"))
      (node (ref "TP43") (pin "TP") (pinfunction "PP_TP") (pintype "input"))
      (node (ref "X4") (pin "15") (pinfunction "15_15") (pintype "passive"))
    )
    (net (code "38") (name "Net-(4C-KL)") (class "Default")
      (node (ref "4") (pin "11") (pinfunction "KL_11") (pintype "passive"))
      (node (ref "IC15") (pin "16") (pinfunction "O1_16") (pintype "open_collector"))
      (node (ref "R84") (pin "1") (pinfunction "1_1") (pintype "passive"))
      (node (ref "R91") (pin "2") (pinfunction "2_2") (pintype "passive"))
      (node (ref "TP44") (pin "TP") (pinfunction "PP_TP") (pintype "input"))
    )
    (net (code "39") (name "Net-(4D-KL)") (class "Default")
      (node (ref "4") (pin "12") (pinfunction "KL_12") (pintype "passive"))
      (node (ref "R85") (pin "1") (pinfunction "1_1") (pintype "passive"))
      (node (ref "TP46") (pin "TP") (pinfunction "PP_TP") (pintype "input"))
    )
    (net (code "40") (name "Net-(4E-KL)") (class "Default")
      (node (ref "4") (pin "2") (pinfunction "KL_2") (pintype "passive"))
      (node (ref "D19") (pin "2") (pinfunction "-_2") (pintype "passive"))
      (node (ref "LED7") (pin "K") (pinfunction "C_K") (pintype "passive"))
      (node (ref "TP35") (pin "TP") (pinfunction "PP_TP") (pintype "input"))
      (node (ref "X4") (pin "12") (pinfunction "12_12") (pintype "passive"))
    )
    (net (code "41") (name "Net-(4F-KL)") (class "Default")
      (node (ref "4") (pin "3") (pinfunction "KL_3") (pintype "passive"))
      (node (ref "D18") (pin "2") (pinfunction "-_2") (pintype "passive"))
      (node (ref "LED8") (pin "K") (pinfunction "C_K") (pintype "passive"))
      (node (ref "TP36") (pin "TP") (pinfunction "PP_TP") (pintype "input"))
      (node (ref "X4") (pin "11") (pinfunction "11_11") (pintype "passive"))
    )
    (net (code "42") (name "Net-(4G-KL)") (class "Default")
      (node (ref "4") (pin "4") (pinfunction "KL_4") (pintype "passive"))
      (node (ref "D17") (pin "2") (pinfunction "-_2") (pintype "passive"))
      (node (ref "LED9") (pin "K") (pinfunction "C_K") (pintype "passive"))
      (node (ref "TP37") (pin "TP") (pinfunction "PP_TP") (pintype "input"))
      (node (ref "X4") (pin "10") (pinfunction "10_10") (pintype "passive"))
    )
    (net (code "43") (name "Net-(4H-KL)") (class "Default")
      (node (ref "4") (pin "5") (pinfunction "KL_5") (pintype "passive"))
      (node (ref "D16") (pin "2") (pinfunction "-_2") (pintype "passive"))
      (node (ref "LED10") (pin "K") (pinfunction "C_K") (pintype "passive"))
      (node (ref "TP38") (pin "TP") (pinfunction "PP_TP") (pintype "input"))
      (node (ref "X4") (pin "9") (pinfunction "9_9") (pintype "passive"))
    )
    (net (code "44") (name "Net-(4I-KL)") (class "Default")
      (node (ref "4") (pin "6") (pinfunction "KL_6") (pintype "passive"))
      (node (ref "JP7") (pin "2") (pinfunction "2_2") (pintype "passive"))
      (node (ref "TP39") (pin "TP") (pinfunction "PP_TP") (pintype "input"))
    )
    (net (code "45") (name "Net-(4J-KL)") (class "Default")
      (node (ref "4") (pin "7") (pinfunction "KL_7") (pintype "passive"))
      (node (ref "LED11") (pin "A") (pinfunction "A_A") (pintype "passive"))
      (node (ref "TP40") (pin "TP") (pinfunction "PP_TP") (pintype "input"))
      (node (ref "X4") (pin "8") (pinfunction "8_8") (pintype "passive"))
    )
    (net (code "46") (name "Net-(4K-KL)") (class "Default")
      (node (ref "4") (pin "8") (pinfunction "KL_8") (pintype "passive"))
      (node (ref "D20") (pin "2") (pinfunction "-_2") (pintype "passive"))
      (node (ref "LED12") (pin "K") (pinfunction "C_K") (pintype "passive"))
      (node (ref "TP41") (pin "TP") (pinfunction "PP_TP") (pintype "input"))
      (node (ref "X4") (pin "14") (pinfunction "14_14") (pintype "passive"))
    )
    (net (code "47") (name "Net-(4L-KL)") (class "Default")
      (node (ref "4") (pin "9") (pinfunction "KL_9") (pintype "passive"))
      (node (ref "D17") (pin "1") (pinfunction "+_1") (pintype "passive"))
      (node (ref "D18") (pin "1") (pinfunction "+_1") (pintype "passive"))
      (node (ref "JP8") (pin "1") (pinfunction "1_1") (pintype "passive"))
      (node (ref "JP9") (pin "2") (pinfunction "2_2") (pintype "passive"))
      (node (ref "TP42") (pin "TP") (pinfunction "PP_TP") (pintype "input"))
    )
    (net (code "48") (name "Net-(5A-KL)") (class "Default")
      (node (ref "5") (pin "1") (pinfunction "KL_1") (pintype "passive"))
      (node (ref "TP47") (pin "TP") (pinfunction "PP_TP") (pintype "input"))
      (node (ref "X7") (pin "1") (pinfunction "1_1") (pintype "passive"))
    )
    (net (code "49") (name "Net-(5B-KL)") (class "Default")
      (node (ref "5") (pin "10") (pinfunction "KL_10") (pintype "passive"))
      (node (ref "D26") (pin "2") (pinfunction "-_2") (pintype "passive"))
      (node (ref "D27") (pin "2") (pinfunction "-_2") (pintype "passive"))
      (node (ref "JP15") (pin "1") (pinfunction "1_1") (pintype "passive"))
      (node (ref "SJ3") (pin "1") (pinfunction "1_1") (pintype "passive"))
      (node (ref "TP56") (pin "TP") (pinfunction "PP_TP") (pintype "input"))
    )
    (net (code "50") (name "Net-(5C-KL)") (class "Default")
      (node (ref "5") (pin "11") (pinfunction "KL_11") (pintype "passive"))
      (node (ref "D27") (pin "1") (pinfunction "+_1") (pintype "passive"))
      (node (ref "TP57") (pin "TP") (pinfunction "PP_TP") (pintype "input"))
      (node (ref "X7") (pin "19") (pinfunction "19_19") (pintype "passive"))
    )
    (net (code "51") (name "Net-(5E-KL)") (class "Default")
      (node (ref "5") (pin "2") (pinfunction "KL_2") (pintype "passive"))
      (node (ref "Q17") (pin "2") (pinfunction "C_2") (pintype "passive"))
      (node (ref "TP48") (pin "TP") (pinfunction "PP_TP") (pintype "input"))
    )
    (net (code "52") (name "Net-(5F-KL)") (class "Default")
      (node (ref "5") (pin "3") (pinfunction "KL_3") (pintype "passive"))
      (node (ref "IC26") (pin "11") (pinfunction "O6_11") (pintype "open_collector"))
      (node (ref "TP49") (pin "TP") (pinfunction "PP_TP") (pintype "input"))
    )
    (net (code "53") (name "Net-(5G-KL)") (class "Default")
      (node (ref "5") (pin "4") (pinfunction "KL_4") (pintype "passive"))
      (node (ref "IC26") (pin "10") (pinfunction "O7_10") (pintype "open_collector"))
      (node (ref "TP50") (pin "TP") (pinfunction "PP_TP") (pintype "input"))
    )
    (net (code "54") (name "Net-(5H-KL)") (class "Default")
      (node (ref "5") (pin "5") (pinfunction "KL_5") (pintype "passive"))
      (node (ref "IC26") (pin "12") (pinfunction "O5_12") (pintype "open_collector"))
      (node (ref "TP51") (pin "TP") (pinfunction "PP_TP") (pintype "input"))
    )
    (net (code "55") (name "Net-(5I-KL)") (class "Default")
      (node (ref "5") (pin "6") (pinfunction "KL_6") (pintype "passive"))
      (node (ref "IC26") (pin "13") (pinfunction "O4_13") (pintype "open_collector"))
      (node (ref "TP52") (pin "TP") (pinfunction "PP_TP") (pintype "input"))
    )
    (net (code "56") (name "Net-(5J-KL)") (class "Default")
      (node (ref "5") (pin "7") (pinfunction "KL_7") (pintype "passive"))
      (node (ref "IC26") (pin "14") (pinfunction "O3_14") (pintype "open_collector"))
      (node (ref "TP53") (pin "TP") (pinfunction "PP_TP") (pintype "input"))
    )
    (net (code "57") (name "Net-(5K-KL)") (class "Default")
      (node (ref "5") (pin "8") (pinfunction "KL_8") (pintype "passive"))
      (node (ref "Q21") (pin "3") (pinfunction "D_3") (pintype "passive"))
      (node (ref "TP54") (pin "TP") (pinfunction "PP_TP") (pintype "input"))
    )
    (net (code "58") (name "Net-(5L-KL)") (class "Default")
      (node (ref "5") (pin "9") (pinfunction "KL_9") (pintype "passive"))
      (node (ref "D26") (pin "1") (pinfunction "+_1") (pintype "passive"))
      (node (ref "TP55") (pin "TP") (pinfunction "PP_TP") (pintype "input"))
      (node (ref "X7") (pin "17") (pinfunction "17_17") (pintype "passive"))
    )
    (net (code "59") (name "Net-(6B-KL)") (class "Default")
      (node (ref "6") (pin "10") (pinfunction "KL_10") (pintype "passive"))
      (node (ref "TP66") (pin "TP") (pinfunction "PP_TP") (pintype "input"))
      (node (ref "X7") (pin "15") (pinfunction "15_15") (pintype "passive"))
    )
    (net (code "60") (name "Net-(6C-KL)") (class "Default")
      (node (ref "6") (pin "11") (pinfunction "KL_11") (pintype "passive"))
      (node (ref "IC26") (pin "16") (pinfunction "O1_16") (pintype "open_collector"))
      (node (ref "R130") (pin "1") (pinfunction "1_1") (pintype "passive"))
      (node (ref "R137") (pin "2") (pinfunction "2_2") (pintype "passive"))
      (node (ref "TP67") (pin "TP") (pinfunction "PP_TP") (pintype "input"))
    )
    (net (code "61") (name "Net-(6D-KL)") (class "Default")
      (node (ref "6") (pin "12") (pinfunction "KL_12") (pintype "passive"))
      (node (ref "R131") (pin "1") (pinfunction "1_1") (pintype "passive"))
      (node (ref "TP69") (pin "TP") (pinfunction "PP_TP") (pintype "input"))
    )
    (net (code "62") (name "Net-(6E-KL)") (class "Default")
      (node (ref "6") (pin "2") (pinfunction "KL_2") (pintype "passive"))
      (node (ref "D31") (pin "2") (pinfunction "-_2") (pintype "passive"))
      (node (ref "LED13") (pin "K") (pinfunction "C_K") (pintype "passive"))
      (node (ref "TP58") (pin "TP") (pinfunction "PP_TP") (pintype "input"))
      (node (ref "X7") (pin "12") (pinfunction "12_12") (pintype "passive"))
    )
    (net (code "63") (name "Net-(6F-KL)") (class "Default")
      (node (ref "6") (pin "3") (pinfunction "KL_3") (pintype "passive"))
      (node (ref "D30") (pin "2") (pinfunction "-_2") (pintype "passive"))
      (node (ref "LED14") (pin "K") (pinfunction "C_K") (pintype "passive"))
      (node (ref "TP59") (pin "TP") (pinfunction "PP_TP") (pintype "input"))
      (node (ref "X7") (pin "11") (pinfunction "11_11") (pintype "passive"))
    )
    (net (code "64") (name "Net-(6G-KL)") (class "Default")
      (node (ref "6") (pin "4") (pinfunction "KL_4") (pintype "passive"))
      (node (ref "D29") (pin "2") (pinfunction "-_2") (pintype "passive"))
      (node (ref "LED15") (pin "K") (pinfunction "C_K") (pintype "passive"))
      (node (ref "TP60") (pin "TP") (pinfunction "PP_TP") (pintype "input"))
      (node (ref "X7") (pin "10") (pinfunction "10_10") (pintype "passive"))
    )
    (net (code "65") (name "Net-(6H-KL)") (class "Default")
      (node (ref "6") (pin "5") (pinfunction "KL_5") (pintype "passive"))
      (node (ref "D28") (pin "2") (pinfunction "-_2") (pintype "passive"))
      (node (ref "LED16") (pin "K") (pinfunction "C_K") (pintype "passive"))
      (node (ref "TP61") (pin "TP") (pinfunction "PP_TP") (pintype "input"))
      (node (ref "X7") (pin "9") (pinfunction "9_9") (pintype "passive"))
    )
    (net (code "66") (name "Net-(6I-KL)") (class "Default")
      (node (ref "6") (pin "6") (pinfunction "KL_6") (pintype "passive"))
      (node (ref "JP12") (pin "2") (pinfunction "2_2") (pintype "passive"))
      (node (ref "TP62") (pin "TP") (pinfunction "PP_TP") (pintype "input"))
    )
    (net (code "67") (name "Net-(6J-KL)") (class "Default")
      (node (ref "6") (pin "7") (pinfunction "KL_7") (pintype "passive"))
      (node (ref "LED17") (pin "A") (pinfunction "A_A") (pintype "passive"))
      (node (ref "TP63") (pin "TP") (pinfunction "PP_TP") (pintype "input"))
      (node (ref "X7") (pin "8") (pinfunction "8_8") (pintype "passive"))
    )
    (net (code "68") (name "Net-(6K-KL)") (class "Default")
      (node (ref "6") (pin "8") (pinfunction "KL_8") (pintype "passive"))
      (node (ref "D32") (pin "2") (pinfunction "-_2") (pintype "passive"))
      (node (ref "LED18") (pin "K") (pinfunction "C_K") (pintype "passive"))
      (node (ref "TP64") (pin "TP") (pinfunction "PP_TP") (pintype "input"))
      (node (ref "X7") (pin "14") (pinfunction "14_14") (pintype "passive"))
    )
    (net (code "69") (name "Net-(6L-KL)") (class "Default")
      (node (ref "6") (pin "9") (pinfunction "KL_9") (pintype "passive"))
      (node (ref "D29") (pin "1") (pinfunction "+_1") (pintype "passive"))
      (node (ref "D30") (pin "1") (pinfunction "+_1") (pintype "passive"))
      (node (ref "JP13") (pin "1") (pinfunction "1_1") (pintype "passive"))
      (node (ref "JP14") (pin "2") (pinfunction "2_2") (pintype "passive"))
      (node (ref "TP65") (pin "TP") (pinfunction "PP_TP") (pintype "input"))
    )
    (net (code "70") (name "Net-(7A-KL)") (class "Default")
      (node (ref "7") (pin "1") (pinfunction "KL_1") (pintype "passive"))
      (node (ref "TP70") (pin "TP") (pinfunction "PP_TP") (pintype "input"))
      (node (ref "X10") (pin "1") (pinfunction "1_1") (pintype "passive"))
    )
    (net (code "71") (name "Net-(7B-KL)") (class "Default")
      (node (ref "7") (pin "10") (pinfunction "KL_10") (pintype "passive"))
      (node (ref "D38") (pin "2") (pinfunction "-_2") (pintype "passive"))
      (node (ref "D39") (pin "2") (pinfunction "-_2") (pintype "passive"))
      (node (ref "JP20") (pin "1") (pinfunction "1_1") (pintype "passive"))
      (node (ref "SJ4") (pin "1") (pinfunction "1_1") (pintype "passive"))
      (node (ref "TP79") (pin "TP") (pinfunction "PP_TP") (pintype "input"))
    )
    (net (code "72") (name "Net-(7C-KL)") (class "Default")
      (node (ref "7") (pin "11") (pinfunction "KL_11") (pintype "passive"))
      (node (ref "D39") (pin "1") (pinfunction "+_1") (pintype "passive"))
      (node (ref "TP80") (pin "TP") (pinfunction "PP_TP") (pintype "input"))
      (node (ref "X10") (pin "19") (pinfunction "19_19") (pintype "passive"))
    )
    (net (code "73") (name "Net-(7E-KL)") (class "Default")
      (node (ref "7") (pin "2") (pinfunction "KL_2") (pintype "passive"))
      (node (ref "Q24") (pin "2") (pinfunction "C_2") (pintype "passive"))
      (node (ref "TP71") (pin "TP") (pinfunction "PP_TP") (pintype "input"))
    )
    (net (code "74") (name "Net-(7F-KL)") (class "Default")
      (node (ref "7") (pin "3") (pinfunction "KL_3") (pintype "passive"))
      (node (ref "IC37") (pin "11") (pinfunction "O6_11") (pintype "open_collector"))
      (node (ref "TP72") (pin "TP") (pinfunction "PP_TP") (pintype "input"))
    )
    (net (code "75") (name "Net-(7G-KL)") (class "Default")
      (node (ref "7") (pin "4") (pinfunction "KL_4") (pintype "passive"))
      (node (ref "IC37") (pin "10") (pinfunction "O7_10") (pintype "open_collector"))
      (node (ref "TP73") (pin "TP") (pinfunction "PP_TP") (pintype "input"))
    )
    (net (code "76") (name "Net-(7H-KL)") (class "Default")
      (node (ref "7") (pin "5") (pinfunction "KL_5") (pintype "passive"))
      (node (ref "IC37") (pin "12") (pinfunction "O5_12") (pintype "open_collector"))
      (node (ref "TP74") (pin "TP") (pinfunction "PP_TP") (pintype "input"))
    )
    (net (code "77") (name "Net-(7I-KL)") (class "Default")
      (node (ref "7") (pin "6") (pinfunction "KL_6") (pintype "passive"))
      (node (ref "IC37") (pin "13") (pinfunction "O4_13") (pintype "open_collector"))
      (node (ref "TP75") (pin "TP") (pinfunction "PP_TP") (pintype "input"))
    )
    (net (code "78") (name "Net-(7J-KL)") (class "Default")
      (node (ref "7") (pin "7") (pinfunction "KL_7") (pintype "passive"))
      (node (ref "IC37") (pin "14") (pinfunction "O3_14") (pintype "open_collector"))
      (node (ref "TP76") (pin "TP") (pinfunction "PP_TP") (pintype "input"))
    )
    (net (code "79") (name "Net-(7K-KL)") (class "Default")
      (node (ref "7") (pin "8") (pinfunction "KL_8") (pintype "passive"))
      (node (ref "Q28") (pin "3") (pinfunction "D_3") (pintype "passive"))
      (node (ref "TP77") (pin "TP") (pinfunction "PP_TP") (pintype "input"))
    )
    (net (code "80") (name "Net-(7L-KL)") (class "Default")
      (node (ref "7") (pin "9") (pinfunction "KL_9") (pintype "passive"))
      (node (ref "D38") (pin "1") (pinfunction "+_1") (pintype "passive"))
      (node (ref "TP78") (pin "TP") (pinfunction "PP_TP") (pintype "input"))
      (node (ref "X10") (pin "17") (pinfunction "17_17") (pintype "passive"))
    )
    (net (code "81") (name "Net-(8B-KL)") (class "Default")
      (node (ref "8") (pin "10") (pinfunction "KL_10") (pintype "passive"))
      (node (ref "TP89") (pin "TP") (pinfunction "PP_TP") (pintype "input"))
      (node (ref "X10") (pin "15") (pinfunction "15_15") (pintype "passive"))
    )
    (net (code "82") (name "Net-(8C-KL)") (class "Default")
      (node (ref "8") (pin "11") (pinfunction "KL_11") (pintype "passive"))
      (node (ref "IC37") (pin "16") (pinfunction "O1_16") (pintype "open_collector"))
      (node (ref "R176") (pin "1") (pinfunction "1_1") (pintype "passive"))
      (node (ref "R183") (pin "2") (pinfunction "2_2") (pintype "passive"))
      (node (ref "TP90") (pin "TP") (pinfunction "PP_TP") (pintype "input"))
    )
    (net (code "83") (name "Net-(8D-KL)") (class "Default")
      (node (ref "8") (pin "12") (pinfunction "KL_12") (pintype "passive"))
      (node (ref "R177") (pin "1") (pinfunction "1_1") (pintype "passive"))
      (node (ref "TP92") (pin "TP") (pinfunction "PP_TP") (pintype "input"))
    )
    (net (code "84") (name "Net-(8E-KL)") (class "Default")
      (node (ref "8") (pin "2") (pinfunction "KL_2") (pintype "passive"))
      (node (ref "D43") (pin "2") (pinfunction "-_2") (pintype "passive"))
      (node (ref "LED19") (pin "K") (pinfunction "C_K") (pintype "passive"))
      (node (ref "TP81") (pin "TP") (pinfunction "PP_TP") (pintype "input"))
      (node (ref "X10") (pin "12") (pinfunction "12_12") (pintype "passive"))
    )
    (net (code "85") (name "Net-(8F-KL)") (class "Default")
      (node (ref "8") (pin "3") (pinfunction "KL_3") (pintype "passive"))
      (node (ref "D42") (pin "2") (pinfunction "-_2") (pintype "passive"))
      (node (ref "LED20") (pin "K") (pinfunction "C_K") (pintype "passive"))
      (node (ref "TP82") (pin "TP") (pinfunction "PP_TP") (pintype "input"))
      (node (ref "X10") (pin "11") (pinfunction "11_11") (pintype "passive"))
    )
    (net (code "86") (name "Net-(8G-KL)") (class "Default")
      (node (ref "8") (pin "4") (pinfunction "KL_4") (pintype "passive"))
      (node (ref "D41") (pin "2") (pinfunction "-_2") (pintype "passive"))
      (node (ref "LED21") (pin "K") (pinfunction "C_K") (pintype "passive"))
      (node (ref "TP83") (pin "TP") (pinfunction "PP_TP") (pintype "input"))
      (node (ref "X10") (pin "10") (pinfunction "10_10") (pintype "passive"))
    )
    (net (code "87") (name "Net-(8H-KL)") (class "Default")
      (node (ref "8") (pin "5") (pinfunction "KL_5") (pintype "passive"))
      (node (ref "D40") (pin "2") (pinfunction "-_2") (pintype "passive"))
      (node (ref "LED22") (pin "K") (pinfunction "C_K") (pintype "passive"))
      (node (ref "TP84") (pin "TP") (pinfunction "PP_TP") (pintype "input"))
      (node (ref "X10") (pin "9") (pinfunction "9_9") (pintype "passive"))
    )
    (net (code "88") (name "Net-(8I-KL)") (class "Default")
      (node (ref "8") (pin "6") (pinfunction "KL_6") (pintype "passive"))
      (node (ref "JP17") (pin "2") (pinfunction "2_2") (pintype "passive"))
      (node (ref "TP85") (pin "TP") (pinfunction "PP_TP") (pintype "input"))
    )
    (net (code "89") (name "Net-(8J-KL)") (class "Default")
      (node (ref "8") (pin "7") (pinfunction "KL_7") (pintype "passive"))
      (node (ref "LED23") (pin "A") (pinfunction "A_A") (pintype "passive"))
      (node (ref "TP86") (pin "TP") (pinfunction "PP_TP") (pintype "input"))
      (node (ref "X10") (pin "8") (pinfunction "8_8") (pintype "passive"))
    )
    (net (code "90") (name "Net-(8K-KL)") (class "Default")
      (node (ref "8") (pin "8") (pinfunction "KL_8") (pintype "passive"))
      (node (ref "D44") (pin "2") (pinfunction "-_2") (pintype "passive"))
      (node (ref "LED24") (pin "K") (pinfunction "C_K") (pintype "passive"))
      (node (ref "TP87") (pin "TP") (pinfunction "PP_TP") (pintype "input"))
      (node (ref "X10") (pin "14") (pinfunction "14_14") (pintype "passive"))
    )
    (net (code "91") (name "Net-(8L-KL)") (class "Default")
      (node (ref "8") (pin "9") (pinfunction "KL_9") (pintype "passive"))
      (node (ref "D41") (pin "1") (pinfunction "+_1") (pintype "passive"))
      (node (ref "D42") (pin "1") (pinfunction "+_1") (pintype "passive"))
      (node (ref "JP18") (pin "1") (pinfunction "1_1") (pintype "passive"))
      (node (ref "JP19") (pin "2") (pinfunction "2_2") (pintype "passive"))
      (node (ref "TP88") (pin "TP") (pinfunction "PP_TP") (pintype "input"))
    )
    (net (code "92") (name "Net-(9A-KL)") (class "Default")
      (node (ref "9") (pin "1") (pinfunction "KL_1") (pintype "passive"))
      (node (ref "TP93") (pin "TP") (pinfunction "PP_TP") (pintype "input"))
      (node (ref "X13") (pin "1") (pinfunction "1_1") (pintype "passive"))
    )
    (net (code "93") (name "Net-(9B-KL)") (class "Default")
      (node (ref "9") (pin "10") (pinfunction "KL_10") (pintype "passive"))
      (node (ref "D50") (pin "2") (pinfunction "-_2") (pintype "passive"))
      (node (ref "D51") (pin "2") (pinfunction "-_2") (pintype "passive"))
      (node (ref "JP25") (pin "1") (pinfunction "1_1") (pintype "passive"))
      (node (ref "SJ5") (pin "1") (pinfunction "1_1") (pintype "passive"))
      (node (ref "TP102") (pin "TP") (pinfunction "PP_TP") (pintype "input"))
    )
    (net (code "94") (name "Net-(9C-KL)") (class "Default")
      (node (ref "9") (pin "11") (pinfunction "KL_11") (pintype "passive"))
      (node (ref "D51") (pin "1") (pinfunction "+_1") (pintype "passive"))
      (node (ref "TP103") (pin "TP") (pinfunction "PP_TP") (pintype "input"))
      (node (ref "X13") (pin "19") (pinfunction "19_19") (pintype "passive"))
    )
    (net (code "95") (name "Net-(9E-KL)") (class "Default")
      (node (ref "9") (pin "2") (pinfunction "KL_2") (pintype "passive"))
      (node (ref "Q31") (pin "2") (pinfunction "C_2") (pintype "passive"))
      (node (ref "TP94") (pin "TP") (pinfunction "PP_TP") (pintype "input"))
    )
    (net (code "96") (name "Net-(9F-KL)") (class "Default")
      (node (ref "9") (pin "3") (pinfunction "KL_3") (pintype "passive"))
      (node (ref "IC48") (pin "11") (pinfunction "O6_11") (pintype "open_collector"))
      (node (ref "TP95") (pin "TP") (pinfunction "PP_TP") (pintype "input"))
    )
    (net (code "97") (name "Net-(9G-KL)") (class "Default")
      (node (ref "9") (pin "4") (pinfunction "KL_4") (pintype "passive"))
      (node (ref "IC48") (pin "10") (pinfunction "O7_10") (pintype "open_collector"))
      (node (ref "TP96") (pin "TP") (pinfunction "PP_TP") (pintype "input"))
    )
    (net (code "98") (name "Net-(9H-KL)") (class "Default")
      (node (ref "9") (pin "5") (pinfunction "KL_5") (pintype "passive"))
      (node (ref "IC48") (pin "12") (pinfunction "O5_12") (pintype "open_collector"))
      (node (ref "TP97") (pin "TP") (pinfunction "PP_TP") (pintype "input"))
    )
    (net (code "99") (name "Net-(9I-KL)") (class "Default")
      (node (ref "9") (pin "6") (pinfunction "KL_6") (pintype "passive"))
      (node (ref "IC48") (pin "13") (pinfunction "O4_13") (pintype "open_collector"))
      (node (ref "TP98") (pin "TP") (pinfunction "PP_TP") (pintype "input"))
    )
    (net (code "100") (name "Net-(9J-KL)") (class "Default")
      (node (ref "9") (pin "7") (pinfunction "KL_7") (pintype "passive"))
      (node (ref "IC48") (pin "14") (pinfunction "O3_14") (pintype "open_collector"))
      (node (ref "TP99") (pin "TP") (pinfunction "PP_TP") (pintype "input"))
    )
    (net (code "101") (name "Net-(9K-KL)") (class "Default")
      (node (ref "9") (pin "8") (pinfunction "KL_8") (pintype "passive"))
      (node (ref "Q35") (pin "3") (pinfunction "D_3") (pintype "passive"))
      (node (ref "TP100") (pin "TP") (pinfunction "PP_TP") (pintype "input"))
    )
    (net (code "102") (name "Net-(9L-KL)") (class "Default")
      (node (ref "9") (pin "9") (pinfunction "KL_9") (pintype "passive"))
      (node (ref "D50") (pin "1") (pinfunction "+_1") (pintype "passive"))
      (node (ref "TP101") (pin "TP") (pinfunction "PP_TP") (pintype "input"))
      (node (ref "X13") (pin "17") (pinfunction "17_17") (pintype "passive"))
    )
    (net (code "103") (name "Net-(10B-KL)") (class "Default")
      (node (ref "10") (pin "10") (pinfunction "KL_10") (pintype "passive"))
      (node (ref "TP112") (pin "TP") (pinfunction "PP_TP") (pintype "input"))
      (node (ref "X13") (pin "15") (pinfunction "15_15") (pintype "passive"))
    )
    (net (code "104") (name "Net-(10C-KL)") (class "Default")
      (node (ref "10") (pin "11") (pinfunction "KL_11") (pintype "passive"))
      (node (ref "IC48") (pin "16") (pinfunction "O1_16") (pintype "open_collector"))
      (node (ref "R222") (pin "1") (pinfunction "1_1") (pintype "passive"))
      (node (ref "R229") (pin "2") (pinfunction "2_2") (pintype "passive"))
      (node (ref "TP113") (pin "TP") (pinfunction "PP_TP") (pintype "input"))
    )
    (net (code "105") (name "Net-(10D-KL)") (class "Default")
      (node (ref "10") (pin "12") (pinfunction "KL_12") (pintype "passive"))
      (node (ref "R223") (pin "1") (pinfunction "1_1") (pintype "passive"))
      (node (ref "TP115") (pin "TP") (pinfunction "PP_TP") (pintype "input"))
    )
    (net (code "106") (name "Net-(10E-KL)") (class "Default")
      (node (ref "10") (pin "2") (pinfunction "KL_2") (pintype "passive"))
      (node (ref "D55") (pin "2") (pinfunction "-_2") (pintype "passive"))
      (node (ref "LED25") (pin "K") (pinfunction "C_K") (pintype "passive"))
      (node (ref "TP104") (pin "TP") (pinfunction "PP_TP") (pintype "input"))
      (node (ref "X13") (pin "12") (pinfunction "12_12") (pintype "passive"))
    )
    (net (code "107") (name "Net-(10F-KL)") (class "Default")
      (node (ref "10") (pin "3") (pinfunction "KL_3") (pintype "passive"))
      (node (ref "D54") (pin "2") (pinfunction "-_2") (pintype "passive"))
      (node (ref "LED26") (pin "K") (pinfunction "C_K") (pintype "passive"))
      (node (ref "TP105") (pin "TP") (pinfunction "PP_TP") (pintype "input"))
      (node (ref "X13") (pin "11") (pinfunction "11_11") (pintype "passive"))
    )
    (net (code "108") (name "Net-(10G-KL)") (class "Default")
      (node (ref "10") (pin "4") (pinfunction "KL_4") (pintype "passive"))
      (node (ref "D53") (pin "2") (pinfunction "-_2") (pintype "passive"))
      (node (ref "LED27") (pin "K") (pinfunction "C_K") (pintype "passive"))
      (node (ref "TP106") (pin "TP") (pinfunction "PP_TP") (pintype "input"))
      (node (ref "X13") (pin "10") (pinfunction "10_10") (pintype "passive"))
    )
    (net (code "109") (name "Net-(10H-KL)") (class "Default")
      (node (ref "10") (pin "5") (pinfunction "KL_5") (pintype "passive"))
      (node (ref "D52") (pin "2") (pinfunction "-_2") (pintype "passive"))
      (node (ref "LED28") (pin "K") (pinfunction "C_K") (pintype "passive"))
      (node (ref "TP107") (pin "TP") (pinfunction "PP_TP") (pintype "input"))
      (node (ref "X13") (pin "9") (pinfunction "9_9") (pintype "passive"))
    )
    (net (code "110") (name "Net-(10I-KL)") (class "Default")
      (node (ref "10") (pin "6") (pinfunction "KL_6") (pintype "passive"))
      (node (ref "JP22") (pin "2") (pinfunction "2_2") (pintype "passive"))
      (node (ref "TP108") (pin "TP") (pinfunction "PP_TP") (pintype "input"))
    )
    (net (code "111") (name "Net-(10J-KL)") (class "Default")
      (node (ref "10") (pin "7") (pinfunction "KL_7") (pintype "passive"))
      (node (ref "LED29") (pin "A") (pinfunction "A_A") (pintype "passive"))
      (node (ref "TP109") (pin "TP") (pinfunction "PP_TP") (pintype "input"))
      (node (ref "X13") (pin "8") (pinfunction "8_8") (pintype "passive"))
    )
    (net (code "112") (name "Net-(10K-KL)") (class "Default")
      (node (ref "10") (pin "8") (pinfunction "KL_8") (pintype "passive"))
      (node (ref "D56") (pin "2") (pinfunction "-_2") (pintype "passive"))
      (node (ref "LED30") (pin "K") (pinfunction "C_K") (pintype "passive"))
      (node (ref "TP110") (pin "TP") (pinfunction "PP_TP") (pintype "input"))
      (node (ref "X13") (pin "14") (pinfunction "14_14") (pintype "passive"))
    )
    (net (code "113") (name "Net-(10L-KL)") (class "Default")
      (node (ref "10") (pin "9") (pinfunction "KL_9") (pintype "passive"))
      (node (ref "D53") (pin "1") (pinfunction "+_1") (pintype "passive"))
      (node (ref "D54") (pin "1") (pinfunction "+_1") (pintype "passive"))
      (node (ref "JP23") (pin "1") (pinfunction "1_1") (pintype "passive"))
      (node (ref "JP24") (pin "2") (pinfunction "2_2") (pintype "passive"))
      (node (ref "TP111") (pin "TP") (pinfunction "PP_TP") (pintype "input"))
    )
    (net (code "114") (name "Net-(11A-KL)") (class "Default")
      (node (ref "11") (pin "1") (pinfunction "KL_1") (pintype "passive"))
      (node (ref "TP116") (pin "TP") (pinfunction "PP_TP") (pintype "input"))
      (node (ref "X16") (pin "1") (pinfunction "1_1") (pintype "passive"))
    )
    (net (code "115") (name "Net-(11B-KL)") (class "Default")
      (node (ref "11") (pin "10") (pinfunction "KL_10") (pintype "passive"))
      (node (ref "D62") (pin "2") (pinfunction "-_2") (pintype "passive"))
      (node (ref "D63") (pin "2") (pinfunction "-_2") (pintype "passive"))
      (node (ref "JP30") (pin "1") (pinfunction "1_1") (pintype "passive"))
      (node (ref "SJ6") (pin "1") (pinfunction "1_1") (pintype "passive"))
      (node (ref "TP125") (pin "TP") (pinfunction "PP_TP") (pintype "input"))
    )
    (net (code "116") (name "Net-(11C-KL)") (class "Default")
      (node (ref "11") (pin "11") (pinfunction "KL_11") (pintype "passive"))
      (node (ref "D63") (pin "1") (pinfunction "+_1") (pintype "passive"))
      (node (ref "TP126") (pin "TP") (pinfunction "PP_TP") (pintype "input"))
      (node (ref "X16") (pin "19") (pinfunction "19_19") (pintype "passive"))
    )
    (net (code "117") (name "Net-(11E-KL)") (class "Default")
      (node (ref "11") (pin "2") (pinfunction "KL_2") (pintype "passive"))
      (node (ref "Q38") (pin "2") (pinfunction "C_2") (pintype "passive"))
      (node (ref "TP117") (pin "TP") (pinfunction "PP_TP") (pintype "input"))
    )
    (net (code "118") (name "Net-(11F-KL)") (class "Default")
      (node (ref "11") (pin "3") (pinfunction "KL_3") (pintype "passive"))
      (node (ref "IC59") (pin "11") (pinfunction "O6_11") (pintype "open_collector"))
      (node (ref "TP118") (pin "TP") (pinfunction "PP_TP") (pintype "input"))
    )
    (net (code "119") (name "Net-(11G-KL)") (class "Default")
      (node (ref "11") (pin "4") (pinfunction "KL_4") (pintype "passive"))
      (node (ref "IC59") (pin "10") (pinfunction "O7_10") (pintype "open_collector"))
      (node (ref "TP119") (pin "TP") (pinfunction "PP_TP") (pintype "input"))
    )
    (net (code "120") (name "Net-(11H-KL)") (class "Default")
      (node (ref "11") (pin "5") (pinfunction "KL_5") (pintype "passive"))
      (node (ref "IC59") (pin "12") (pinfunction "O5_12") (pintype "open_collector"))
      (node (ref "TP120") (pin "TP") (pinfunction "PP_TP") (pintype "input"))
    )
    (net (code "121") (name "Net-(11I-KL)") (class "Default")
      (node (ref "11") (pin "6") (pinfunction "KL_6") (pintype "passive"))
      (node (ref "IC59") (pin "13") (pinfunction "O4_13") (pintype "open_collector"))
      (node (ref "TP121") (pin "TP") (pinfunction "PP_TP") (pintype "input"))
    )
    (net (code "122") (name "Net-(11J-KL)") (class "Default")
      (node (ref "11") (pin "7") (pinfunction "KL_7") (pintype "passive"))
      (node (ref "IC59") (pin "14") (pinfunction "O3_14") (pintype "open_collector"))
      (node (ref "TP122") (pin "TP") (pinfunction "PP_TP") (pintype "input"))
    )
    (net (code "123") (name "Net-(11K-KL)") (class "Default")
      (node (ref "11") (pin "8") (pinfunction "KL_8") (pintype "passive"))
      (node (ref "Q42") (pin "3") (pinfunction "D_3") (pintype "passive"))
      (node (ref "TP123") (pin "TP") (pinfunction "PP_TP") (pintype "input"))
    )
    (net (code "124") (name "Net-(11L-KL)") (class "Default")
      (node (ref "11") (pin "9") (pinfunction "KL_9") (pintype "passive"))
      (node (ref "D62") (pin "1") (pinfunction "+_1") (pintype "passive"))
      (node (ref "TP124") (pin "TP") (pinfunction "PP_TP") (pintype "input"))
      (node (ref "X16") (pin "17") (pinfunction "17_17") (pintype "passive"))
    )
    (net (code "125") (name "Net-(12B-KL)") (class "Default")
      (node (ref "12") (pin "10") (pinfunction "KL_10") (pintype "passive"))
      (node (ref "TP135") (pin "TP") (pinfunction "PP_TP") (pintype "input"))
      (node (ref "X16") (pin "15") (pinfunction "15_15") (pintype "passive"))
    )
    (net (code "126") (name "Net-(12C-KL)") (class "Default")
      (node (ref "12") (pin "11") (pinfunction "KL_11") (pintype "passive"))
      (node (ref "IC59") (pin "16") (pinfunction "O1_16") (pintype "open_collector"))
      (node (ref "R268") (pin "1") (pinfunction "1_1") (pintype "passive"))
      (node (ref "R275") (pin "2") (pinfunction "2_2") (pintype "passive"))
      (node (ref "TP136") (pin "TP") (pinfunction "PP_TP") (pintype "input"))
    )
    (net (code "127") (name "Net-(12D-KL)") (class "Default")
      (node (ref "12") (pin "12") (pinfunction "KL_12") (pintype "passive"))
      (node (ref "R269") (pin "1") (pinfunction "1_1") (pintype "passive"))
      (node (ref "TP138") (pin "TP") (pinfunction "PP_TP") (pintype "input"))
    )
    (net (code "128") (name "Net-(12E-KL)") (class "Default")
      (node (ref "12") (pin "2") (pinfunction "KL_2") (pintype "passive"))
      (node (ref "D67") (pin "2") (pinfunction "-_2") (pintype "passive"))
      (node (ref "LED31") (pin "K") (pinfunction "C_K") (pintype "passive"))
      (node (ref "TP127") (pin "TP") (pinfunction "PP_TP") (pintype "input"))
      (node (ref "X16") (pin "12") (pinfunction "12_12") (pintype "passive"))
    )
    (net (code "129") (name "Net-(12F-KL)") (class "Default")
      (node (ref "12") (pin "3") (pinfunction "KL_3") (pintype "passive"))
      (node (ref "D66") (pin "2") (pinfunction "-_2") (pintype "passive"))
      (node (ref "LED32") (pin "K") (pinfunction "C_K") (pintype "passive"))
      (node (ref "TP128") (pin "TP") (pinfunction "PP_TP") (pintype "input"))
      (node (ref "X16") (pin "11") (pinfunction "11_11") (pintype "passive"))
    )
    (net (code "130") (name "Net-(12G-KL)") (class "Default")
      (node (ref "12") (pin "4") (pinfunction "KL_4") (pintype "passive"))
      (node (ref "D65") (pin "2") (pinfunction "-_2") (pintype "passive"))
      (node (ref "LED33") (pin "K") (pinfunction "C_K") (pintype "passive"))
      (node (ref "TP129") (pin "TP") (pinfunction "PP_TP") (pintype "input"))
      (node (ref "X16") (pin "10") (pinfunction "10_10") (pintype "passive"))
    )
    (net (code "131") (name "Net-(12H-KL)") (class "Default")
      (node (ref "12") (pin "5") (pinfunction "KL_5") (pintype "passive"))
      (node (ref "D64") (pin "2") (pinfunction "-_2") (pintype "passive"))
      (node (ref "LED34") (pin "K") (pinfunction "C_K") (pintype "passive"))
      (node (ref "TP130") (pin "TP") (pinfunction "PP_TP") (pintype "input"))
      (node (ref "X16") (pin "9") (pinfunction "9_9") (pintype "passive"))
    )
    (net (code "132") (name "Net-(12I-KL)") (class "Default")
      (node (ref "12") (pin "6") (pinfunction "KL_6") (pintype "passive"))
      (node (ref "JP27") (pin "2") (pinfunction "2_2") (pintype "passive"))
      (node (ref "TP131") (pin "TP") (pinfunction "PP_TP") (pintype "input"))
    )
    (net (code "133") (name "Net-(12J-KL)") (class "Default")
      (node (ref "12") (pin "7") (pinfunction "KL_7") (pintype "passive"))
      (node (ref "LED35") (pin "A") (pinfunction "A_A") (pintype "passive"))
      (node (ref "TP132") (pin "TP") (pinfunction "PP_TP") (pintype "input"))
      (node (ref "X16") (pin "8") (pinfunction "8_8") (pintype "passive"))
    )
    (net (code "134") (name "Net-(12K-KL)") (class "Default")
      (node (ref "12") (pin "8") (pinfunction "KL_8") (pintype "passive"))
      (node (ref "D68") (pin "2") (pinfunction "-_2") (pintype "passive"))
      (node (ref "LED36") (pin "K") (pinfunction "C_K") (pintype "passive"))
      (node (ref "TP133") (pin "TP") (pinfunction "PP_TP") (pintype "input"))
      (node (ref "X16") (pin "14") (pinfunction "14_14") (pintype "passive"))
    )
    (net (code "135") (name "Net-(12L-KL)") (class "Default")
      (node (ref "12") (pin "9") (pinfunction "KL_9") (pintype "passive"))
      (node (ref "D65") (pin "1") (pinfunction "+_1") (pintype "passive"))
      (node (ref "D66") (pin "1") (pinfunction "+_1") (pintype "passive"))
      (node (ref "JP28") (pin "1") (pinfunction "1_1") (pintype "passive"))
      (node (ref "JP29") (pin "2") (pinfunction "2_2") (pintype "passive"))
      (node (ref "TP134") (pin "TP") (pinfunction "PP_TP") (pintype "input"))
    )
    (net (code "136") (name "Net-(13A-KL)") (class "Default")
      (node (ref "13") (pin "1") (pinfunction "KL_1") (pintype "passive"))
      (node (ref "TP139") (pin "TP") (pinfunction "PP_TP") (pintype "input"))
      (node (ref "X19") (pin "1") (pinfunction "1_1") (pintype "passive"))
    )
    (net (code "137") (name "Net-(13B-KL)") (class "Default")
      (node (ref "13") (pin "10") (pinfunction "KL_10") (pintype "passive"))
      (node (ref "D74") (pin "2") (pinfunction "-_2") (pintype "passive"))
      (node (ref "D75") (pin "2") (pinfunction "-_2") (pintype "passive"))
      (node (ref "JP35") (pin "1") (pinfunction "1_1") (pintype "passive"))
      (node (ref "SJ7") (pin "1") (pinfunction "1_1") (pintype "passive"))
      (node (ref "TP148") (pin "TP") (pinfunction "PP_TP") (pintype "input"))
    )
    (net (code "138") (name "Net-(13C-KL)") (class "Default")
      (node (ref "13") (pin "11") (pinfunction "KL_11") (pintype "passive"))
      (node (ref "D75") (pin "1") (pinfunction "+_1") (pintype "passive"))
      (node (ref "TP149") (pin "TP") (pinfunction "PP_TP") (pintype "input"))
      (node (ref "X19") (pin "19") (pinfunction "19_19") (pintype "passive"))
    )
    (net (code "139") (name "Net-(13E-KL)") (class "Default")
      (node (ref "13") (pin "2") (pinfunction "KL_2") (pintype "passive"))
      (node (ref "Q45") (pin "2") (pinfunction "C_2") (pintype "passive"))
      (node (ref "TP140") (pin "TP") (pinfunction "PP_TP") (pintype "input"))
    )
    (net (code "140") (name "Net-(13F-KL)") (class "Default")
      (node (ref "13") (pin "3") (pinfunction "KL_3") (pintype "passive"))
      (node (ref "IC70") (pin "11") (pinfunction "O6_11") (pintype "open_collector"))
      (node (ref "TP141") (pin "TP") (pinfunction "PP_TP") (pintype "input"))
    )
    (net (code "141") (name "Net-(13G-KL)") (class "Default")
      (node (ref "13") (pin "4") (pinfunction "KL_4") (pintype "passive"))
      (node (ref "IC70") (pin "10") (pinfunction "O7_10") (pintype "open_collector"))
      (node (ref "TP142") (pin "TP") (pinfunction "PP_TP") (pintype "input"))
    )
    (net (code "142") (name "Net-(13H-KL)") (class "Default")
      (node (ref "13") (pin "5") (pinfunction "KL_5") (pintype "passive"))
      (node (ref "IC70") (pin "12") (pinfunction "O5_12") (pintype "open_collector"))
      (node (ref "TP143") (pin "TP") (pinfunction "PP_TP") (pintype "input"))
    )
    (net (code "143") (name "Net-(13I-KL)") (class "Default")
      (node (ref "13") (pin "6") (pinfunction "KL_6") (pintype "passive"))
      (node (ref "IC70") (pin "13") (pinfunction "O4_13") (pintype "open_collector"))
      (node (ref "TP144") (pin "TP") (pinfunction "PP_TP") (pintype "input"))
    )
    (net (code "144") (name "Net-(13J-KL)") (class "Default")
      (node (ref "13") (pin "7") (pinfunction "KL_7") (pintype "passive"))
      (node (ref "IC70") (pin "14") (pinfunction "O3_14") (pintype "open_collector"))
      (node (ref "TP145") (pin "TP") (pinfunction "PP_TP") (pintype "input"))
    )
    (net (code "145") (name "Net-(13K-KL)") (class "Default")
      (node (ref "13") (pin "8") (pinfunction "KL_8") (pintype "passive"))
      (node (ref "Q49") (pin "3") (pinfunction "D_3") (pintype "passive"))
      (node (ref "TP146") (pin "TP") (pinfunction "PP_TP") (pintype "input"))
    )
    (net (code "146") (name "Net-(13L-KL)") (class "Default")
      (node (ref "13") (pin "9") (pinfunction "KL_9") (pintype "passive"))
      (node (ref "D74") (pin "1") (pinfunction "+_1") (pintype "passive"))
      (node (ref "TP147") (pin "TP") (pinfunction "PP_TP") (pintype "input"))
      (node (ref "X19") (pin "17") (pinfunction "17_17") (pintype "passive"))
    )
    (net (code "147") (name "Net-(14B-KL)") (class "Default")
      (node (ref "14") (pin "10") (pinfunction "KL_10") (pintype "passive"))
      (node (ref "TP158") (pin "TP") (pinfunction "PP_TP") (pintype "input"))
      (node (ref "X19") (pin "15") (pinfunction "15_15") (pintype "passive"))
    )
    (net (code "148") (name "Net-(14C-KL)") (class "Default")
      (node (ref "14") (pin "11") (pinfunction "KL_11") (pintype "passive"))
      (node (ref "IC70") (pin "16") (pinfunction "O1_16") (pintype "open_collector"))
      (node (ref "R314") (pin "1") (pinfunction "1_1") (pintype "passive"))
      (node (ref "R321") (pin "2") (pinfunction "2_2") (pintype "passive"))
      (node (ref "TP159") (pin "TP") (pinfunction "PP_TP") (pintype "input"))
    )
    (net (code "149") (name "Net-(14D-KL)") (class "Default")
      (node (ref "14") (pin "12") (pinfunction "KL_12") (pintype "passive"))
      (node (ref "R315") (pin "1") (pinfunction "1_1") (pintype "passive"))
      (node (ref "TP161") (pin "TP") (pinfunction "PP_TP") (pintype "input"))
    )
    (net (code "150") (name "Net-(14E-KL)") (class "Default")
      (node (ref "14") (pin "2") (pinfunction "KL_2") (pintype "passive"))
      (node (ref "D79") (pin "2") (pinfunction "-_2") (pintype "passive"))
      (node (ref "LED37") (pin "K") (pinfunction "C_K") (pintype "passive"))
      (node (ref "TP150") (pin "TP") (pinfunction "PP_TP") (pintype "input"))
      (node (ref "X19") (pin "12") (pinfunction "12_12") (pintype "passive"))
    )
    (net (code "151") (name "Net-(14F-KL)") (class "Default")
      (node (ref "14") (pin "3") (pinfunction "KL_3") (pintype "passive"))
      (node (ref "D78") (pin "2") (pinfunction "-_2") (pintype "passive"))
      (node (ref "LED38") (pin "K") (pinfunction "C_K") (pintype "passive"))
      (node (ref "TP151") (pin "TP") (pinfunction "PP_TP") (pintype "input"))
      (node (ref "X19") (pin "11") (pinfunction "11_11") (pintype "passive"))
    )
    (net (code "152") (name "Net-(14G-KL)") (class "Default")
      (node (ref "14") (pin "4") (pinfunction "KL_4") (pintype "passive"))
      (node (ref "D77") (pin "2") (pinfunction "-_2") (pintype "passive"))
      (node (ref "LED39") (pin "K") (pinfunction "C_K") (pintype "passive"))
      (node (ref "TP152") (pin "TP") (pinfunction "PP_TP") (pintype "input"))
      (node (ref "X19") (pin "10") (pinfunction "10_10") (pintype "passive"))
    )
    (net (code "153") (name "Net-(14H-KL)") (class "Default")
      (node (ref "14") (pin "5") (pinfunction "KL_5") (pintype "passive"))
      (node (ref "D76") (pin "2") (pinfunction "-_2") (pintype "passive"))
      (node (ref "LED40") (pin "K") (pinfunction "C_K") (pintype "passive"))
      (node (ref "TP153") (pin "TP") (pinfunction "PP_TP") (pintype "input"))
      (node (ref "X19") (pin "9") (pinfunction "9_9") (pintype "passive"))
    )
    (net (code "154") (name "Net-(14I-KL)") (class "Default")
      (node (ref "14") (pin "6") (pinfunction "KL_6") (pintype "passive"))
      (node (ref "JP32") (pin "2") (pinfunction "2_2") (pintype "passive"))
      (node (ref "TP154") (pin "TP") (pinfunction "PP_TP") (pintype "input"))
    )
    (net (code "155") (name "Net-(14J-KL)") (class "Default")
      (node (ref "14") (pin "7") (pinfunction "KL_7") (pintype "passive"))
      (node (ref "LED41") (pin "A") (pinfunction "A_A") (pintype "passive"))
      (node (ref "TP155") (pin "TP") (pinfunction "PP_TP") (pintype "input"))
      (node (ref "X19") (pin "8") (pinfunction "8_8") (pintype "passive"))
    )
    (net (code "156") (name "Net-(14K-KL)") (class "Default")
      (node (ref "14") (pin "8") (pinfunction "KL_8") (pintype "passive"))
      (node (ref "D80") (pin "2") (pinfunction "-_2") (pintype "passive"))
      (node (ref "LED42") (pin "K") (pinfunction "C_K") (pintype "passive"))
      (node (ref "TP156") (pin "TP") (pinfunction "PP_TP") (pintype "input"))
      (node (ref "X19") (pin "14") (pinfunction "14_14") (pintype "passive"))
    )
    (net (code "157") (name "Net-(14L-KL)") (class "Default")
      (node (ref "14") (pin "9") (pinfunction "KL_9") (pintype "passive"))
      (node (ref "D77") (pin "1") (pinfunction "+_1") (pintype "passive"))
      (node (ref "D78") (pin "1") (pinfunction "+_1") (pintype "passive"))
      (node (ref "JP33") (pin "1") (pinfunction "1_1") (pintype "passive"))
      (node (ref "JP34") (pin "2") (pinfunction "2_2") (pintype "passive"))
      (node (ref "TP157") (pin "TP") (pinfunction "PP_TP") (pintype "input"))
    )
    (net (code "158") (name "Net-(15A-KL)") (class "Default")
      (node (ref "15") (pin "1") (pinfunction "KL_1") (pintype "passive"))
      (node (ref "TP162") (pin "TP") (pinfunction "PP_TP") (pintype "input"))
      (node (ref "X22") (pin "1") (pinfunction "1_1") (pintype "passive"))
    )
    (net (code "159") (name "Net-(15B-KL)") (class "Default")
      (node (ref "15") (pin "10") (pinfunction "KL_10") (pintype "passive"))
      (node (ref "D86") (pin "2") (pinfunction "-_2") (pintype "passive"))
      (node (ref "D87") (pin "2") (pinfunction "-_2") (pintype "passive"))
      (node (ref "JP40") (pin "1") (pinfunction "1_1") (pintype "passive"))
      (node (ref "SJ8") (pin "1") (pinfunction "1_1") (pintype "passive"))
      (node (ref "TP171") (pin "TP") (pinfunction "PP_TP") (pintype "input"))
    )
    (net (code "160") (name "Net-(15C-KL)") (class "Default")
      (node (ref "15") (pin "11") (pinfunction "KL_11") (pintype "passive"))
      (node (ref "D87") (pin "1") (pinfunction "+_1") (pintype "passive"))
      (node (ref "TP172") (pin "TP") (pinfunction "PP_TP") (pintype "input"))
      (node (ref "X22") (pin "19") (pinfunction "19_19") (pintype "passive"))
    )
    (net (code "161") (name "Net-(15E-KL)") (class "Default")
      (node (ref "15") (pin "2") (pinfunction "KL_2") (pintype "passive"))
      (node (ref "Q52") (pin "2") (pinfunction "C_2") (pintype "passive"))
      (node (ref "TP163") (pin "TP") (pinfunction "PP_TP") (pintype "input"))
    )
    (net (code "162") (name "Net-(15F-KL)") (class "Default")
      (node (ref "15") (pin "3") (pinfunction "KL_3") (pintype "passive"))
      (node (ref "IC81") (pin "11") (pinfunction "O6_11") (pintype "open_collector"))
      (node (ref "TP164") (pin "TP") (pinfunction "PP_TP") (pintype "input"))
    )
    (net (code "163") (name "Net-(15G-KL)") (class "Default")
      (node (ref "15") (pin "4") (pinfunction "KL_4") (pintype "passive"))
      (node (ref "IC81") (pin "10") (pinfunction "O7_10") (pintype "open_collector"))
      (node (ref "TP165") (pin "TP") (pinfunction "PP_TP") (pintype "input"))
    )
    (net (code "164") (name "Net-(15H-KL)") (class "Default")
      (node (ref "15") (pin "5") (pinfunction "KL_5") (pintype "passive"))
      (node (ref "IC81") (pin "12") (pinfunction "O5_12") (pintype "open_collector"))
      (node (ref "TP166") (pin "TP") (pinfunction "PP_TP") (pintype "input"))
    )
    (net (code "165") (name "Net-(15I-KL)") (class "Default")
      (node (ref "15") (pin "6") (pinfunction "KL_6") (pintype "passive"))
      (node (ref "IC81") (pin "13") (pinfunction "O4_13") (pintype "open_collector"))
      (node (ref "TP167") (pin "TP") (pinfunction "PP_TP") (pintype "input"))
    )
    (net (code "166") (name "Net-(15J-KL)") (class "Default")
      (node (ref "15") (pin "7") (pinfunction "KL_7") (pintype "passive"))
      (node (ref "IC81") (pin "14") (pinfunction "O3_14") (pintype "open_collector"))
      (node (ref "TP168") (pin "TP") (pinfunction "PP_TP") (pintype "input"))
    )
    (net (code "167") (name "Net-(15K-KL)") (class "Default")
      (node (ref "15") (pin "8") (pinfunction "KL_8") (pintype "passive"))
      (node (ref "Q56") (pin "3") (pinfunction "D_3") (pintype "passive"))
      (node (ref "TP169") (pin "TP") (pinfunction "PP_TP") (pintype "input"))
    )
    (net (code "168") (name "Net-(15L-KL)") (class "Default")
      (node (ref "15") (pin "9") (pinfunction "KL_9") (pintype "passive"))
      (node (ref "D86") (pin "1") (pinfunction "+_1") (pintype "passive"))
      (node (ref "TP170") (pin "TP") (pinfunction "PP_TP") (pintype "input"))
      (node (ref "X22") (pin "17") (pinfunction "17_17") (pintype "passive"))
    )
    (net (code "169") (name "Net-(16B-KL)") (class "Default")
      (node (ref "16") (pin "10") (pinfunction "KL_10") (pintype "passive"))
      (node (ref "TP181") (pin "TP") (pinfunction "PP_TP") (pintype "input"))
      (node (ref "X22") (pin "15") (pinfunction "15_15") (pintype "passive"))
    )
    (net (code "170") (name "Net-(16C-KL)") (class "Default")
      (node (ref "16") (pin "11") (pinfunction "KL_11") (pintype "passive"))
      (node (ref "IC81") (pin "16") (pinfunction "O1_16") (pintype "open_collector"))
      (node (ref "R360") (pin "1") (pinfunction "1_1") (pintype "passive"))
      (node (ref "R367") (pin "2") (pinfunction "2_2") (pintype "passive"))
      (node (ref "TP182") (pin "TP") (pinfunction "PP_TP") (pintype "input"))
    )
    (net (code "171") (name "Net-(16D-KL)") (class "Default")
      (node (ref "16") (pin "12") (pinfunction "KL_12") (pintype "passive"))
      (node (ref "R361") (pin "1") (pinfunction "1_1") (pintype "passive"))
      (node (ref "TP184") (pin "TP") (pinfunction "PP_TP") (pintype "input"))
    )
    (net (code "172") (name "Net-(16E-KL)") (class "Default")
      (node (ref "16") (pin "2") (pinfunction "KL_2") (pintype "passive"))
      (node (ref "D91") (pin "2") (pinfunction "-_2") (pintype "passive"))
      (node (ref "LED43") (pin "K") (pinfunction "C_K") (pintype "passive"))
      (node (ref "TP173") (pin "TP") (pinfunction "PP_TP") (pintype "input"))
      (node (ref "X22") (pin "12") (pinfunction "12_12") (pintype "passive"))
    )
    (net (code "173") (name "Net-(16F-KL)") (class "Default")
      (node (ref "16") (pin "3") (pinfunction "KL_3") (pintype "passive"))
      (node (ref "D90") (pin "2") (pinfunction "-_2") (pintype "passive"))
      (node (ref "LED44") (pin "K") (pinfunction "C_K") (pintype "passive"))
      (node (ref "TP174") (pin "TP") (pinfunction "PP_TP") (pintype "input"))
      (node (ref "X22") (pin "11") (pinfunction "11_11") (pintype "passive"))
    )
    (net (code "174") (name "Net-(16G-KL)") (class "Default")
      (node (ref "16") (pin "4") (pinfunction "KL_4") (pintype "passive"))
      (node (ref "D89") (pin "2") (pinfunction "-_2") (pintype "passive"))
      (node (ref "LED45") (pin "K") (pinfunction "C_K") (pintype "passive"))
      (node (ref "TP175") (pin "TP") (pinfunction "PP_TP") (pintype "input"))
      (node (ref "X22") (pin "10") (pinfunction "10_10") (pintype "passive"))
    )
    (net (code "175") (name "Net-(16H-KL)") (class "Default")
      (node (ref "16") (pin "5") (pinfunction "KL_5") (pintype "passive"))
      (node (ref "D88") (pin "2") (pinfunction "-_2") (pintype "passive"))
      (node (ref "LED46") (pin "K") (pinfunction "C_K") (pintype "passive"))
      (node (ref "TP176") (pin "TP") (pinfunction "PP_TP") (pintype "input"))
      (node (ref "X22") (pin "9") (pinfunction "9_9") (pintype "passive"))
    )
    (net (code "176") (name "Net-(16I-KL)") (class "Default")
      (node (ref "16") (pin "6") (pinfunction "KL_6") (pintype "passive"))
      (node (ref "JP37") (pin "2") (pinfunction "2_2") (pintype "passive"))
      (node (ref "TP177") (pin "TP") (pinfunction "PP_TP") (pintype "input"))
    )
    (net (code "177") (name "Net-(16J-KL)") (class "Default")
      (node (ref "16") (pin "7") (pinfunction "KL_7") (pintype "passive"))
      (node (ref "LED47") (pin "A") (pinfunction "A_A") (pintype "passive"))
      (node (ref "TP178") (pin "TP") (pinfunction "PP_TP") (pintype "input"))
      (node (ref "X22") (pin "8") (pinfunction "8_8") (pintype "passive"))
    )
    (net (code "178") (name "Net-(16K-KL)") (class "Default")
      (node (ref "16") (pin "8") (pinfunction "KL_8") (pintype "passive"))
      (node (ref "D92") (pin "2") (pinfunction "-_2") (pintype "passive"))
      (node (ref "LED48") (pin "K") (pinfunction "C_K") (pintype "passive"))
      (node (ref "TP179") (pin "TP") (pinfunction "PP_TP") (pintype "input"))
      (node (ref "X22") (pin "14") (pinfunction "14_14") (pintype "passive"))
    )
    (net (code "179") (name "Net-(16L-KL)") (class "Default")
      (node (ref "16") (pin "9") (pinfunction "KL_9") (pintype "passive"))
      (node (ref "D89") (pin "1") (pinfunction "+_1") (pintype "passive"))
      (node (ref "D90") (pin "1") (pinfunction "+_1") (pintype "passive"))
      (node (ref "JP38") (pin "1") (pinfunction "1_1") (pintype "passive"))
      (node (ref "JP39") (pin "2") (pinfunction "2_2") (pintype "passive"))
      (node (ref "TP180") (pin "TP") (pinfunction "PP_TP") (pintype "input"))
    )
    (net (code "180") (name "Net-(17A-KL)") (class "Default")
      (node (ref "17") (pin "1") (pinfunction "KL_1") (pintype "passive"))
      (node (ref "TP185") (pin "TP") (pinfunction "PP_TP") (pintype "input"))
      (node (ref "X25") (pin "1") (pinfunction "1_1") (pintype "passive"))
    )
    (net (code "181") (name "Net-(17B-KL)") (class "Default")
      (node (ref "17") (pin "10") (pinfunction "KL_10") (pintype "passive"))
      (node (ref "D98") (pin "2") (pinfunction "-_2") (pintype "passive"))
      (node (ref "D99") (pin "2") (pinfunction "-_2") (pintype "passive"))
      (node (ref "JP45") (pin "1") (pinfunction "1_1") (pintype "passive"))
      (node (ref "SJ9") (pin "1") (pinfunction "1_1") (pintype "passive"))
      (node (ref "TP194") (pin "TP") (pinfunction "PP_TP") (pintype "input"))
    )
    (net (code "182") (name "Net-(17C-KL)") (class "Default")
      (node (ref "17") (pin "11") (pinfunction "KL_11") (pintype "passive"))
      (node (ref "D99") (pin "1") (pinfunction "+_1") (pintype "passive"))
      (node (ref "TP195") (pin "TP") (pinfunction "PP_TP") (pintype "input"))
      (node (ref "X25") (pin "19") (pinfunction "19_19") (pintype "passive"))
    )
    (net (code "183") (name "Net-(17E-KL)") (class "Default")
      (node (ref "17") (pin "2") (pinfunction "KL_2") (pintype "passive"))
      (node (ref "Q59") (pin "2") (pinfunction "C_2") (pintype "passive"))
      (node (ref "TP186") (pin "TP") (pinfunction "PP_TP") (pintype "input"))
    )
    (net (code "184") (name "Net-(17F-KL)") (class "Default")
      (node (ref "17") (pin "3") (pinfunction "KL_3") (pintype "passive"))
      (node (ref "IC92") (pin "11") (pinfunction "O6_11") (pintype "open_collector"))
      (node (ref "TP187") (pin "TP") (pinfunction "PP_TP") (pintype "input"))
    )
    (net (code "185") (name "Net-(17G-KL)") (class "Default")
      (node (ref "17") (pin "4") (pinfunction "KL_4") (pintype "passive"))
      (node (ref "IC92") (pin "10") (pinfunction "O7_10") (pintype "open_collector"))
      (node (ref "TP188") (pin "TP") (pinfunction "PP_TP") (pintype "input"))
    )
    (net (code "186") (name "Net-(17H-KL)") (class "Default")
      (node (ref "17") (pin "5") (pinfunction "KL_5") (pintype "passive"))
      (node (ref "IC92") (pin "12") (pinfunction "O5_12") (pintype "open_collector"))
      (node (ref "TP189") (pin "TP") (pinfunction "PP_TP") (pintype "input"))
    )
    (net (code "187") (name "Net-(17I-KL)") (class "Default")
      (node (ref "17") (pin "6") (pinfunction "KL_6") (pintype "passive"))
      (node (ref "IC92") (pin "13") (pinfunction "O4_13") (pintype "open_collector"))
      (node (ref "TP190") (pin "TP") (pinfunction "PP_TP") (pintype "input"))
    )
    (net (code "188") (name "Net-(17J-KL)") (class "Default")
      (node (ref "17") (pin "7") (pinfunction "KL_7") (pintype "passive"))
      (node (ref "IC92") (pin "14") (pinfunction "O3_14") (pintype "open_collector"))
      (node (ref "TP191") (pin "TP") (pinfunction "PP_TP") (pintype "input"))
    )
    (net (code "189") (name "Net-(17K-KL)") (class "Default")
      (node (ref "17") (pin "8") (pinfunction "KL_8") (pintype "passive"))
      (node (ref "Q63") (pin "3") (pinfunction "D_3") (pintype "passive"))
      (node (ref "TP192") (pin "TP") (pinfunction "PP_TP") (pintype "input"))
    )
    (net (code "190") (name "Net-(17L-KL)") (class "Default")
      (node (ref "17") (pin "9") (pinfunction "KL_9") (pintype "passive"))
      (node (ref "D98") (pin "1") (pinfunction "+_1") (pintype "passive"))
      (node (ref "TP193") (pin "TP") (pinfunction "PP_TP") (pintype "input"))
      (node (ref "X25") (pin "17") (pinfunction "17_17") (pintype "passive"))
    )
    (net (code "191") (name "Net-(18B-KL)") (class "Default")
      (node (ref "18") (pin "10") (pinfunction "KL_10") (pintype "passive"))
      (node (ref "TP204") (pin "TP") (pinfunction "PP_TP") (pintype "input"))
      (node (ref "X25") (pin "15") (pinfunction "15_15") (pintype "passive"))
    )
    (net (code "192") (name "Net-(18C-KL)") (class "Default")
      (node (ref "18") (pin "11") (pinfunction "KL_11") (pintype "passive"))
      (node (ref "IC92") (pin "16") (pinfunction "O1_16") (pintype "open_collector"))
      (node (ref "R406") (pin "1") (pinfunction "1_1") (pintype "passive"))
      (node (ref "R413") (pin "2") (pinfunction "2_2") (pintype "passive"))
      (node (ref "TP205") (pin "TP") (pinfunction "PP_TP") (pintype "input"))
    )
    (net (code "193") (name "Net-(18D-KL)") (class "Default")
      (node (ref "18") (pin "12") (pinfunction "KL_12") (pintype "passive"))
      (node (ref "R407") (pin "1") (pinfunction "1_1") (pintype "passive"))
      (node (ref "TP207") (pin "TP") (pinfunction "PP_TP") (pintype "input"))
    )
    (net (code "194") (name "Net-(18E-KL)") (class "Default")
      (node (ref "18") (pin "2") (pinfunction "KL_2") (pintype "passive"))
      (node (ref "D103") (pin "2") (pinfunction "-_2") (pintype "passive"))
      (node (ref "LED49") (pin "K") (pinfunction "C_K") (pintype "passive"))
      (node (ref "TP196") (pin "TP") (pinfunction "PP_TP") (pintype "input"))
      (node (ref "X25") (pin "12") (pinfunction "12_12") (pintype "passive"))
    )
    (net (code "195") (name "Net-(18F-KL)") (class "Default")
      (node (ref "18") (pin "3") (pinfunction "KL_3") (pintype "passive"))
      (node (ref "D102") (pin "2") (pinfunction "-_2") (pintype "passive"))
      (node (ref "LED50") (pin "K") (pinfunction "C_K") (pintype "passive"))
      (node (ref "TP197") (pin "TP") (pinfunction "PP_TP") (pintype "input"))
      (node (ref "X25") (pin "11") (pinfunction "11_11") (pintype "passive"))
    )
    (net (code "196") (name "Net-(18G-KL)") (class "Default")
      (node (ref "18") (pin "4") (pinfunction "KL_4") (pintype "passive"))
      (node (ref "D101") (pin "2") (pinfunction "-_2") (pintype "passive"))
      (node (ref "LED51") (pin "K") (pinfunction "C_K") (pintype "passive"))
      (node (ref "TP198") (pin "TP") (pinfunction "PP_TP") (pintype "input"))
      (node (ref "X25") (pin "10") (pinfunction "10_10") (pintype "passive"))
    )
    (net (code "197") (name "Net-(18H-KL)") (class "Default")
      (node (ref "18") (pin "5") (pinfunction "KL_5") (pintype "passive"))
      (node (ref "D100") (pin "2") (pinfunction "-_2") (pintype "passive"))
      (node (ref "LED52") (pin "K") (pinfunction "C_K") (pintype "passive"))
      (node (ref "TP199") (pin "TP") (pinfunction "PP_TP") (pintype "input"))
      (node (ref "X25") (pin "9") (pinfunction "9_9") (pintype "passive"))
    )
    (net (code "198") (name "Net-(18I-KL)") (class "Default")
      (node (ref "18") (pin "6") (pinfunction "KL_6") (pintype "passive"))
      (node (ref "JP42") (pin "2") (pinfunction "2_2") (pintype "passive"))
      (node (ref "TP200") (pin "TP") (pinfunction "PP_TP") (pintype "input"))
    )
    (net (code "199") (name "Net-(18J-KL)") (class "Default")
      (node (ref "18") (pin "7") (pinfunction "KL_7") (pintype "passive"))
      (node (ref "LED53") (pin "A") (pinfunction "A_A") (pintype "passive"))
      (node (ref "TP201") (pin "TP") (pinfunction "PP_TP") (pintype "input"))
      (node (ref "X25") (pin "8") (pinfunction "8_8") (pintype "passive"))
    )
    (net (code "200") (name "Net-(18K-KL)") (class "Default")
      (node (ref "18") (pin "8") (pinfunction "KL_8") (pintype "passive"))
      (node (ref "D104") (pin "2") (pinfunction "-_2") (pintype "passive"))
      (node (ref "LED54") (pin "K") (pinfunction "C_K") (pintype "passive"))
      (node (ref "TP202") (pin "TP") (pinfunction "PP_TP") (pintype "input"))
      (node (ref "X25") (pin "14") (pinfunction "14_14") (pintype "passive"))
    )
    (net (code "201") (name "Net-(18L-KL)") (class "Default")
      (node (ref "18") (pin "9") (pinfunction "KL_9") (pintype "passive"))
      (node (ref "D101") (pin "1") (pinfunction "+_1") (pintype "passive"))
      (node (ref "D102") (pin "1") (pinfunction "+_1") (pintype "passive"))
      (node (ref "JP43") (pin "1") (pinfunction "1_1") (pintype "passive"))
      (node (ref "JP44") (pin "2") (pinfunction "2_2") (pintype "passive"))
      (node (ref "TP203") (pin "TP") (pinfunction "PP_TP") (pintype "input"))
    )
    (net (code "202") (name "Net-(19A-KL)") (class "Default")
      (node (ref "19") (pin "1") (pinfunction "KL_1") (pintype "passive"))
      (node (ref "TP208") (pin "TP") (pinfunction "PP_TP") (pintype "input"))
      (node (ref "X28") (pin "1") (pinfunction "1_1") (pintype "passive"))
    )
    (net (code "203") (name "Net-(19B-KL)") (class "Default")
      (node (ref "19") (pin "10") (pinfunction "KL_10") (pintype "passive"))
      (node (ref "D110") (pin "2") (pinfunction "-_2") (pintype "passive"))
      (node (ref "D111") (pin "2") (pinfunction "-_2") (pintype "passive"))
      (node (ref "JP50") (pin "1") (pinfunction "1_1") (pintype "passive"))
      (node (ref "SJ10") (pin "1") (pinfunction "1_1") (pintype "passive"))
      (node (ref "TP217") (pin "TP") (pinfunction "PP_TP") (pintype "input"))
    )
    (net (code "204") (name "Net-(19C-KL)") (class "Default")
      (node (ref "19") (pin "11") (pinfunction "KL_11") (pintype "passive"))
      (node (ref "D111") (pin "1") (pinfunction "+_1") (pintype "passive"))
      (node (ref "TP218") (pin "TP") (pinfunction "PP_TP") (pintype "input"))
      (node (ref "X28") (pin "19") (pinfunction "19_19") (pintype "passive"))
    )
    (net (code "205") (name "Net-(19E-KL)") (class "Default")
      (node (ref "19") (pin "2") (pinfunction "KL_2") (pintype "passive"))
      (node (ref "Q66") (pin "2") (pinfunction "C_2") (pintype "passive"))
      (node (ref "TP209") (pin "TP") (pinfunction "PP_TP") (pintype "input"))
    )
    (net (code "206") (name "Net-(19F-KL)") (class "Default")
      (node (ref "19") (pin "3") (pinfunction "KL_3") (pintype "passive"))
      (node (ref "IC103") (pin "11") (pinfunction "O6_11") (pintype "open_collector"))
      (node (ref "TP210") (pin "TP") (pinfunction "PP_TP") (pintype "input"))
    )
    (net (code "207") (name "Net-(19G-KL)") (class "Default")
      (node (ref "19") (pin "4") (pinfunction "KL_4") (pintype "passive"))
      (node (ref "IC103") (pin "10") (pinfunction "O7_10") (pintype "open_collector"))
      (node (ref "TP211") (pin "TP") (pinfunction "PP_TP") (pintype "input"))
    )
    (net (code "208") (name "Net-(19H-KL)") (class "Default")
      (node (ref "19") (pin "5") (pinfunction "KL_5") (pintype "passive"))
      (node (ref "IC103") (pin "12") (pinfunction "O5_12") (pintype "open_collector"))
      (node (ref "TP212") (pin "TP") (pinfunction "PP_TP") (pintype "input"))
    )
    (net (code "209") (name "Net-(19I-KL)") (class "Default")
      (node (ref "19") (pin "6") (pinfunction "KL_6") (pintype "passive"))
      (node (ref "IC103") (pin "13") (pinfunction "O4_13") (pintype "open_collector"))
      (node (ref "TP213") (pin "TP") (pinfunction "PP_TP") (pintype "input"))
    )
    (net (code "210") (name "Net-(19J-KL)") (class "Default")
      (node (ref "19") (pin "7") (pinfunction "KL_7") (pintype "passive"))
      (node (ref "IC103") (pin "14") (pinfunction "O3_14") (pintype "open_collector"))
      (node (ref "TP214") (pin "TP") (pinfunction "PP_TP") (pintype "input"))
    )
    (net (code "211") (name "Net-(19K-KL)") (class "Default")
      (node (ref "19") (pin "8") (pinfunction "KL_8") (pintype "passive"))
      (node (ref "Q70") (pin "3") (pinfunction "D_3") (pintype "passive"))
      (node (ref "TP215") (pin "TP") (pinfunction "PP_TP") (pintype "input"))
    )
    (net (code "212") (name "Net-(19L-KL)") (class "Default")
      (node (ref "19") (pin "9") (pinfunction "KL_9") (pintype "passive"))
      (node (ref "D110") (pin "1") (pinfunction "+_1") (pintype "passive"))
      (node (ref "TP216") (pin "TP") (pinfunction "PP_TP") (pintype "input"))
      (node (ref "X28") (pin "17") (pinfunction "17_17") (pintype "passive"))
    )
    (net (code "213") (name "Net-(20B-KL)") (class "Default")
      (node (ref "20") (pin "10") (pinfunction "KL_10") (pintype "passive"))
      (node (ref "TP227") (pin "TP") (pinfunction "PP_TP") (pintype "input"))
      (node (ref "X28") (pin "15") (pinfunction "15_15") (pintype "passive"))
    )
    (net (code "214") (name "Net-(20C-KL)") (class "Default")
      (node (ref "20") (pin "11") (pinfunction "KL_11") (pintype "passive"))
      (node (ref "IC103") (pin "16") (pinfunction "O1_16") (pintype "open_collector"))
      (node (ref "R452") (pin "1") (pinfunction "1_1") (pintype "passive"))
      (node (ref "R459") (pin "2") (pinfunction "2_2") (pintype "passive"))
      (node (ref "TP228") (pin "TP") (pinfunction "PP_TP") (pintype "input"))
    )
    (net (code "215") (name "Net-(20D-KL)") (class "Default")
      (node (ref "20") (pin "12") (pinfunction "KL_12") (pintype "passive"))
      (node (ref "R453") (pin "1") (pinfunction "1_1") (pintype "passive"))
      (node (ref "TP230") (pin "TP") (pinfunction "PP_TP") (pintype "input"))
    )
    (net (code "216") (name "Net-(20E-KL)") (class "Default")
      (node (ref "20") (pin "2") (pinfunction "KL_2") (pintype "passive"))
      (node (ref "D115") (pin "2") (pinfunction "-_2") (pintype "passive"))
      (node (ref "LED55") (pin "K") (pinfunction "C_K") (pintype "passive"))
      (node (ref "TP219") (pin "TP") (pinfunction "PP_TP") (pintype "input"))
      (node (ref "X28") (pin "12") (pinfunction "12_12") (pintype "passive"))
    )
    (net (code "217") (name "Net-(20F-KL)") (class "Default")
      (node (ref "20") (pin "3") (pinfunction "KL_3") (pintype "passive"))
      (node (ref "D114") (pin "2") (pinfunction "-_2") (pintype "passive"))
      (node (ref "LED56") (pin "K") (pinfunction "C_K") (pintype "passive"))
      (node (ref "TP220") (pin "TP") (pinfunction "PP_TP") (pintype "input"))
      (node (ref "X28") (pin "11") (pinfunction "11_11") (pintype "passive"))
    )
    (net (code "218") (name "Net-(20G-KL)") (class "Default")
      (node (ref "20") (pin "4") (pinfunction "KL_4") (pintype "passive"))
      (node (ref "D113") (pin "2") (pinfunction "-_2") (pintype "passive"))
      (node (ref "LED57") (pin "K") (pinfunction "C_K") (pintype "passive"))
      (node (ref "TP221") (pin "TP") (pinfunction "PP_TP") (pintype "input"))
      (node (ref "X28") (pin "10") (pinfunction "10_10") (pintype "passive"))
    )
    (net (code "219") (name "Net-(20H-KL)") (class "Default")
      (node (ref "20") (pin "5") (pinfunction "KL_5") (pintype "passive"))
      (node (ref "D112") (pin "2") (pinfunction "-_2") (pintype "passive"))
      (node (ref "LED58") (pin "K") (pinfunction "C_K") (pintype "passive"))
      (node (ref "TP222") (pin "TP") (pinfunction "PP_TP") (pintype "input"))
      (node (ref "X28") (pin "9") (pinfunction "9_9") (pintype "passive"))
    )
    (net (code "220") (name "Net-(20I-KL)") (class "Default")
      (node (ref "20") (pin "6") (pinfunction "KL_6") (pintype "passive"))
      (node (ref "JP47") (pin "2") (pinfunction "2_2") (pintype "passive"))
      (node (ref "TP223") (pin "TP") (pinfunction "PP_TP") (pintype "input"))
    )
    (net (code "221") (name "Net-(20J-KL)") (class "Default")
      (node (ref "20") (pin "7") (pinfunction "KL_7") (pintype "passive"))
      (node (ref "LED59") (pin "A") (pinfunction "A_A") (pintype "passive"))
      (node (ref "TP224") (pin "TP") (pinfunction "PP_TP") (pintype "input"))
      (node (ref "X28") (pin "8") (pinfunction "8_8") (pintype "passive"))
    )
    (net (code "222") (name "Net-(20K-KL)") (class "Default")
      (node (ref "20") (pin "8") (pinfunction "KL_8") (pintype "passive"))
      (node (ref "D116") (pin "2") (pinfunction "-_2") (pintype "passive"))
      (node (ref "LED60") (pin "K") (pinfunction "C_K") (pintype "passive"))
      (node (ref "TP225") (pin "TP") (pinfunction "PP_TP") (pintype "input"))
      (node (ref "X28") (pin "14") (pinfunction "14_14") (pintype "passive"))
    )
    (net (code "223") (name "Net-(20L-KL)") (class "Default")
      (node (ref "20") (pin "9") (pinfunction "KL_9") (pintype "passive"))
      (node (ref "D113") (pin "1") (pinfunction "+_1") (pintype "passive"))
      (node (ref "D114") (pin "1") (pinfunction "+_1") (pintype "passive"))
      (node (ref "JP48") (pin "1") (pinfunction "1_1") (pintype "passive"))
      (node (ref "JP49") (pin "2") (pinfunction "2_2") (pintype "passive"))
      (node (ref "TP226") (pin "TP") (pinfunction "PP_TP") (pintype "input"))
    )
    (net (code "224") (name "Net-(21A-KL)") (class "Default")
      (node (ref "21") (pin "1") (pinfunction "KL_1") (pintype "passive"))
      (node (ref "TP231") (pin "TP") (pinfunction "PP_TP") (pintype "input"))
      (node (ref "X31") (pin "1") (pinfunction "1_1") (pintype "passive"))
    )
    (net (code "225") (name "Net-(21B-KL)") (class "Default")
      (node (ref "21") (pin "10") (pinfunction "KL_10") (pintype "passive"))
      (node (ref "D122") (pin "2") (pinfunction "-_2") (pintype "passive"))
      (node (ref "D123") (pin "2") (pinfunction "-_2") (pintype "passive"))
      (node (ref "JP55") (pin "1") (pinfunction "1_1") (pintype "passive"))
      (node (ref "SJ11") (pin "1") (pinfunction "1_1") (pintype "passive"))
      (node (ref "TP240") (pin "TP") (pinfunction "PP_TP") (pintype "input"))
    )
    (net (code "226") (name "Net-(21C-KL)") (class "Default")
      (node (ref "21") (pin "11") (pinfunction "KL_11") (pintype "passive"))
      (node (ref "D123") (pin "1") (pinfunction "+_1") (pintype "passive"))
      (node (ref "TP241") (pin "TP") (pinfunction "PP_TP") (pintype "input"))
      (node (ref "X31") (pin "19") (pinfunction "19_19") (pintype "passive"))
    )
    (net (code "227") (name "Net-(21E-KL)") (class "Default")
      (node (ref "21") (pin "2") (pinfunction "KL_2") (pintype "passive"))
      (node (ref "Q73") (pin "2") (pinfunction "C_2") (pintype "passive"))
      (node (ref "TP232") (pin "TP") (pinfunction "PP_TP") (pintype "input"))
    )
    (net (code "228") (name "Net-(21F-KL)") (class "Default")
      (node (ref "21") (pin "3") (pinfunction "KL_3") (pintype "passive"))
      (node (ref "IC114") (pin "11") (pinfunction "O6_11") (pintype "open_collector"))
      (node (ref "TP233") (pin "TP") (pinfunction "PP_TP") (pintype "input"))
    )
    (net (code "229") (name "Net-(21G-KL)") (class "Default")
      (node (ref "21") (pin "4") (pinfunction "KL_4") (pintype "passive"))
      (node (ref "IC114") (pin "10") (pinfunction "O7_10") (pintype "open_collector"))
      (node (ref "TP234") (pin "TP") (pinfunction "PP_TP") (pintype "input"))
    )
    (net (code "230") (name "Net-(21H-KL)") (class "Default")
      (node (ref "21") (pin "5") (pinfunction "KL_5") (pintype "passive"))
      (node (ref "IC114") (pin "12") (pinfunction "O5_12") (pintype "open_collector"))
      (node (ref "TP235") (pin "TP") (pinfunction "PP_TP") (pintype "input"))
    )
    (net (code "231") (name "Net-(21I-KL)") (class "Default")
      (node (ref "21") (pin "6") (pinfunction "KL_6") (pintype "passive"))
      (node (ref "IC114") (pin "13") (pinfunction "O4_13") (pintype "open_collector"))
      (node (ref "TP236") (pin "TP") (pinfunction "PP_TP") (pintype "input"))
    )
    (net (code "232") (name "Net-(21J-KL)") (class "Default")
      (node (ref "21") (pin "7") (pinfunction "KL_7") (pintype "passive"))
      (node (ref "IC114") (pin "14") (pinfunction "O3_14") (pintype "open_collector"))
      (node (ref "TP237") (pin "TP") (pinfunction "PP_TP") (pintype "input"))
    )
    (net (code "233") (name "Net-(21K-KL)") (class "Default")
      (node (ref "21") (pin "8") (pinfunction "KL_8") (pintype "passive"))
      (node (ref "Q77") (pin "3") (pinfunction "D_3") (pintype "passive"))
      (node (ref "TP238") (pin "TP") (pinfunction "PP_TP") (pintype "input"))
    )
    (net (code "234") (name "Net-(21L-KL)") (class "Default")
      (node (ref "21") (pin "9") (pinfunction "KL_9") (pintype "passive"))
      (node (ref "D122") (pin "1") (pinfunction "+_1") (pintype "passive"))
      (node (ref "TP239") (pin "TP") (pinfunction "PP_TP") (pintype "input"))
      (node (ref "X31") (pin "17") (pinfunction "17_17") (pintype "passive"))
    )
    (net (code "235") (name "Net-(22B-KL)") (class "Default")
      (node (ref "22") (pin "10") (pinfunction "KL_10") (pintype "passive"))
      (node (ref "TP250") (pin "TP") (pinfunction "PP_TP") (pintype "input"))
      (node (ref "X31") (pin "15") (pinfunction "15_15") (pintype "passive"))
    )
    (net (code "236") (name "Net-(22C-KL)") (class "Default")
      (node (ref "22") (pin "11") (pinfunction "KL_11") (pintype "passive"))
      (node (ref "IC114") (pin "16") (pinfunction "O1_16") (pintype "open_collector"))
      (node (ref "R498") (pin "1") (pinfunction "1_1") (pintype "passive"))
      (node (ref "R505") (pin "2") (pinfunction "2_2") (pintype "passive"))
      (node (ref "TP251") (pin "TP") (pinfunction "PP_TP") (pintype "input"))
    )
    (net (code "237") (name "Net-(22D-KL)") (class "Default")
      (node (ref "22") (pin "12") (pinfunction "KL_12") (pintype "passive"))
      (node (ref "R499") (pin "1") (pinfunction "1_1") (pintype "passive"))
      (node (ref "TP253") (pin "TP") (pinfunction "PP_TP") (pintype "input"))
    )
    (net (code "238") (name "Net-(22E-KL)") (class "Default")
      (node (ref "22") (pin "2") (pinfunction "KL_2") (pintype "passive"))
      (node (ref "D127") (pin "2") (pinfunction "-_2") (pintype "passive"))
      (node (ref "LED61") (pin "K") (pinfunction "C_K") (pintype "passive"))
      (node (ref "TP242") (pin "TP") (pinfunction "PP_TP") (pintype "input"))
      (node (ref "X31") (pin "12") (pinfunction "12_12") (pintype "passive"))
    )
    (net (code "239") (name "Net-(22F-KL)") (class "Default")
      (node (ref "22") (pin "3") (pinfunction "KL_3") (pintype "passive"))
      (node (ref "D126") (pin "2") (pinfunction "-_2") (pintype "passive"))
      (node (ref "LED62") (pin "K") (pinfunction "C_K") (pintype "passive"))
      (node (ref "TP243") (pin "TP") (pinfunction "PP_TP") (pintype "input"))
      (node (ref "X31") (pin "11") (pinfunction "11_11") (pintype "passive"))
    )
    (net (code "240") (name "Net-(22G-KL)") (class "Default")
      (node (ref "22") (pin "4") (pinfunction "KL_4") (pintype "passive"))
      (node (ref "D125") (pin "2") (pinfunction "-_2") (pintype "passive"))
      (node (ref "LED63") (pin "K") (pinfunction "C_K") (pintype "passive"))
      (node (ref "TP244") (pin "TP") (pinfunction "PP_TP") (pintype "input"))
      (node (ref "X31") (pin "10") (pinfunction "10_10") (pintype "passive"))
    )
    (net (code "241") (name "Net-(22H-KL)") (class "Default")
      (node (ref "22") (pin "5") (pinfunction "KL_5") (pintype "passive"))
      (node (ref "D124") (pin "2") (pinfunction "-_2") (pintype "passive"))
      (node (ref "LED64") (pin "K") (pinfunction "C_K") (pintype "passive"))
      (node (ref "TP245") (pin "TP") (pinfunction "PP_TP") (pintype "input"))
      (node (ref "X31") (pin "9") (pinfunction "9_9") (pintype "passive"))
    )
    (net (code "242") (name "Net-(22I-KL)") (class "Default")
      (node (ref "22") (pin "6") (pinfunction "KL_6") (pintype "passive"))
      (node (ref "JP52") (pin "2") (pinfunction "2_2") (pintype "passive"))
      (node (ref "TP246") (pin "TP") (pinfunction "PP_TP") (pintype "input"))
    )
    (net (code "243") (name "Net-(22J-KL)") (class "Default")
      (node (ref "22") (pin "7") (pinfunction "KL_7") (pintype "passive"))
      (node (ref "LED65") (pin "A") (pinfunction "A_A") (pintype "passive"))
      (node (ref "TP247") (pin "TP") (pinfunction "PP_TP") (pintype "input"))
      (node (ref "X31") (pin "8") (pinfunction "8_8") (pintype "passive"))
    )
    (net (code "244") (name "Net-(22K-KL)") (class "Default")
      (node (ref "22") (pin "8") (pinfunction "KL_8") (pintype "passive"))
      (node (ref "D128") (pin "2") (pinfunction "-_2") (pintype "passive"))
      (node (ref "LED66") (pin "K") (pinfunction "C_K") (pintype "passive"))
      (node (ref "TP248") (pin "TP") (pinfunction "PP_TP") (pintype "input"))
      (node (ref "X31") (pin "14") (pinfunction "14_14") (pintype "passive"))
    )
    (net (code "245") (name "Net-(22L-KL)") (class "Default")
      (node (ref "22") (pin "9") (pinfunction "KL_9") (pintype "passive"))
      (node (ref "D125") (pin "1") (pinfunction "+_1") (pintype "passive"))
      (node (ref "D126") (pin "1") (pinfunction "+_1") (pintype "passive"))
      (node (ref "JP53") (pin "1") (pinfunction "1_1") (pintype "passive"))
      (node (ref "JP54") (pin "2") (pinfunction "2_2") (pintype "passive"))
      (node (ref "TP249") (pin "TP") (pinfunction "PP_TP") (pintype "input"))
    )
    (net (code "246") (name "Net-(23A-KL)") (class "Default")
      (node (ref "23") (pin "1") (pinfunction "KL_1") (pintype "passive"))
      (node (ref "TP254") (pin "TP") (pinfunction "PP_TP") (pintype "input"))
      (node (ref "X34") (pin "1") (pinfunction "1_1") (pintype "passive"))
    )
    (net (code "247") (name "Net-(23B-KL)") (class "Default")
      (node (ref "23") (pin "10") (pinfunction "KL_10") (pintype "passive"))
      (node (ref "D134") (pin "2") (pinfunction "-_2") (pintype "passive"))
      (node (ref "D135") (pin "2") (pinfunction "-_2") (pintype "passive"))
      (node (ref "JP60") (pin "1") (pinfunction "1_1") (pintype "passive"))
      (node (ref "SJ12") (pin "1") (pinfunction "1_1") (pintype "passive"))
      (node (ref "TP263") (pin "TP") (pinfunction "PP_TP") (pintype "input"))
    )
    (net (code "248") (name "Net-(23C-KL)") (class "Default")
      (node (ref "23") (pin "11") (pinfunction "KL_11") (pintype "passive"))
      (node (ref "D135") (pin "1") (pinfunction "+_1") (pintype "passive"))
      (node (ref "TP264") (pin "TP") (pinfunction "PP_TP") (pintype "input"))
      (node (ref "X34") (pin "19") (pinfunction "19_19") (pintype "passive"))
    )
    (net (code "249") (name "Net-(23E-KL)") (class "Default")
      (node (ref "23") (pin "2") (pinfunction "KL_2") (pintype "passive"))
      (node (ref "Q80") (pin "2") (pinfunction "C_2") (pintype "passive"))
      (node (ref "TP255") (pin "TP") (pinfunction "PP_TP") (pintype "input"))
    )
    (net (code "250") (name "Net-(23F-KL)") (class "Default")
      (node (ref "23") (pin "3") (pinfunction "KL_3") (pintype "passive"))
      (node (ref "IC125") (pin "11") (pinfunction "O6_11") (pintype "open_collector"))
      (node (ref "TP256") (pin "TP") (pinfunction "PP_TP") (pintype "input"))
    )
    (net (code "251") (name "Net-(23G-KL)") (class "Default")
      (node (ref "23") (pin "4") (pinfunction "KL_4") (pintype "passive"))
      (node (ref "IC125") (pin "10") (pinfunction "O7_10") (pintype "open_collector"))
      (node (ref "TP257") (pin "TP") (pinfunction "PP_TP") (pintype "input"))
    )
    (net (code "252") (name "Net-(23H-KL)") (class "Default")
      (node (ref "23") (pin "5") (pinfunction "KL_5") (pintype "passive"))
      (node (ref "IC125") (pin "12") (pinfunction "O5_12") (pintype "open_collector"))
      (node (ref "TP258") (pin "TP") (pinfunction "PP_TP") (pintype "input"))
    )
    (net (code "253") (name "Net-(23I-KL)") (class "Default")
      (node (ref "23") (pin "6") (pinfunction "KL_6") (pintype "passive"))
      (node (ref "IC125") (pin "13") (pinfunction "O4_13") (pintype "open_collector"))
      (node (ref "TP259") (pin "TP") (pinfunction "PP_TP") (pintype "input"))
    )
    (net (code "254") (name "Net-(23J-KL)") (class "Default")
      (node (ref "23") (pin "7") (pinfunction "KL_7") (pintype "passive"))
      (node (ref "IC125") (pin "14") (pinfunction "O3_14") (pintype "open_collector"))
      (node (ref "TP260") (pin "TP") (pinfunction "PP_TP") (pintype "input"))
    )
    (net (code "255") (name "Net-(23K-KL)") (class "Default")
      (node (ref "23") (pin "8") (pinfunction "KL_8") (pintype "passive"))
      (node (ref "Q84") (pin "3") (pinfunction "D_3") (pintype "passive"))
      (node (ref "TP261") (pin "TP") (pinfunction "PP_TP") (pintype "input"))
    )
    (net (code "256") (name "Net-(23L-KL)") (class "Default")
      (node (ref "23") (pin "9") (pinfunction "KL_9") (pintype "passive"))
      (node (ref "D134") (pin "1") (pinfunction "+_1") (pintype "passive"))
      (node (ref "TP262") (pin "TP") (pinfunction "PP_TP") (pintype "input"))
      (node (ref "X34") (pin "17") (pinfunction "17_17") (pintype "passive"))
    )
    (net (code "257") (name "Net-(24B-KL)") (class "Default")
      (node (ref "24") (pin "10") (pinfunction "KL_10") (pintype "passive"))
      (node (ref "TP273") (pin "TP") (pinfunction "PP_TP") (pintype "input"))
      (node (ref "X34") (pin "15") (pinfunction "15_15") (pintype "passive"))
    )
    (net (code "258") (name "Net-(24C-KL)") (class "Default")
      (node (ref "24") (pin "11") (pinfunction "KL_11") (pintype "passive"))
      (node (ref "IC125") (pin "16") (pinfunction "O1_16") (pintype "open_collector"))
      (node (ref "R544") (pin "1") (pinfunction "1_1") (pintype "passive"))
      (node (ref "R551") (pin "2") (pinfunction "2_2") (pintype "passive"))
      (node (ref "TP274") (pin "TP") (pinfunction "PP_TP") (pintype "input"))
    )
    (net (code "259") (name "Net-(24D-KL)") (class "Default")
      (node (ref "24") (pin "12") (pinfunction "KL_12") (pintype "passive"))
      (node (ref "R545") (pin "1") (pinfunction "1_1") (pintype "passive"))
      (node (ref "TP276") (pin "TP") (pinfunction "PP_TP") (pintype "input"))
    )
    (net (code "260") (name "Net-(24E-KL)") (class "Default")
      (node (ref "24") (pin "2") (pinfunction "KL_2") (pintype "passive"))
      (node (ref "D139") (pin "2") (pinfunction "-_2") (pintype "passive"))
      (node (ref "LED67") (pin "K") (pinfunction "C_K") (pintype "passive"))
      (node (ref "TP265") (pin "TP") (pinfunction "PP_TP") (pintype "input"))
      (node (ref "X34") (pin "12") (pinfunction "12_12") (pintype "passive"))
    )
    (net (code "261") (name "Net-(24F-KL)") (class "Default")
      (node (ref "24") (pin "3") (pinfunction "KL_3") (pintype "passive"))
      (node (ref "D138") (pin "2") (pinfunction "-_2") (pintype "passive"))
      (node (ref "LED68") (pin "K") (pinfunction "C_K") (pintype "passive"))
      (node (ref "TP266") (pin "TP") (pinfunction "PP_TP") (pintype "input"))
      (node (ref "X34") (pin "11") (pinfunction "11_11") (pintype "passive"))
    )
    (net (code "262") (name "Net-(24G-KL)") (class "Default")
      (node (ref "24") (pin "4") (pinfunction "KL_4") (pintype "passive"))
      (node (ref "D137") (pin "2") (pinfunction "-_2") (pintype "passive"))
      (node (ref "LED69") (pin "K") (pinfunction "C_K") (pintype "passive"))
      (node (ref "TP267") (pin "TP") (pinfunction "PP_TP") (pintype "input"))
      (node (ref "X34") (pin "10") (pinfunction "10_10") (pintype "passive"))
    )
    (net (code "263") (name "Net-(24H-KL)") (class "Default")
      (node (ref "24") (pin "5") (pinfunction "KL_5") (pintype "passive"))
      (node (ref "D136") (pin "2") (pinfunction "-_2") (pintype "passive"))
      (node (ref "LED70") (pin "K") (pinfunction "C_K") (pintype "passive"))
      (node (ref "TP268") (pin "TP") (pinfunction "PP_TP") (pintype "input"))
      (node (ref "X34") (pin "9") (pinfunction "9_9") (pintype "passive"))
    )
    (net (code "264") (name "Net-(24I-KL)") (class "Default")
      (node (ref "24") (pin "6") (pinfunction "KL_6") (pintype "passive"))
      (node (ref "JP57") (pin "2") (pinfunction "2_2") (pintype "passive"))
      (node (ref "TP269") (pin "TP") (pinfunction "PP_TP") (pintype "input"))
    )
    (net (code "265") (name "Net-(24J-KL)") (class "Default")
      (node (ref "24") (pin "7") (pinfunction "KL_7") (pintype "passive"))
      (node (ref "LED71") (pin "A") (pinfunction "A_A") (pintype "passive"))
      (node (ref "TP270") (pin "TP") (pinfunction "PP_TP") (pintype "input"))
      (node (ref "X34") (pin "8") (pinfunction "8_8") (pintype "passive"))
    )
    (net (code "266") (name "Net-(24K-KL)") (class "Default")
      (node (ref "24") (pin "8") (pinfunction "KL_8") (pintype "passive"))
      (node (ref "D140") (pin "2") (pinfunction "-_2") (pintype "passive"))
      (node (ref "LED72") (pin "K") (pinfunction "C_K") (pintype "passive"))
      (node (ref "TP271") (pin "TP") (pinfunction "PP_TP") (pintype "input"))
      (node (ref "X34") (pin "14") (pinfunction "14_14") (pintype "passive"))
    )
    (net (code "267") (name "Net-(24L-KL)") (class "Default")
      (node (ref "24") (pin "9") (pinfunction "KL_9") (pintype "passive"))
      (node (ref "D137") (pin "1") (pinfunction "+_1") (pintype "passive"))
      (node (ref "D138") (pin "1") (pinfunction "+_1") (pintype "passive"))
      (node (ref "JP58") (pin "1") (pinfunction "1_1") (pintype "passive"))
      (node (ref "JP59") (pin "2") (pinfunction "2_2") (pintype "passive"))
      (node (ref "TP272") (pin "TP") (pinfunction "PP_TP") (pintype "input"))
    )
    (net (code "268") (name "Net-(C3-Pad1)") (class "Default")
      (node (ref "C3") (pin "1") (pinfunction "1_1") (pintype "passive"))
      (node (ref "R12") (pin "1") (pinfunction "1_1") (pintype "passive"))
      (node (ref "R8") (pin "1") (pinfunction "1_1") (pintype "passive"))
    )
    (net (code "269") (name "Net-(C7-Pad1)") (class "Default")
      (node (ref "C7") (pin "1") (pinfunction "1_1") (pintype "passive"))
      (node (ref "R25") (pin "1") (pinfunction "1_1") (pintype "passive"))
      (node (ref "R30") (pin "2") (pinfunction "2_2") (pintype "passive"))
    )
    (net (code "270") (name "Net-(C11-Pad1)") (class "Default")
      (node (ref "C11") (pin "1") (pinfunction "1_1") (pintype "passive"))
      (node (ref "R57") (pin "1") (pinfunction "1_1") (pintype "passive"))
      (node (ref "R58") (pin "2") (pinfunction "2_2") (pintype "passive"))
    )
    (net (code "271") (name "Net-(C20-Pad1)") (class "Default")
      (node (ref "C20") (pin "1") (pinfunction "1_1") (pintype "passive"))
      (node (ref "R86") (pin "1") (pinfunction "1_1") (pintype "passive"))
      (node (ref "R87") (pin "1") (pinfunction "1_1") (pintype "passive"))
    )
    (net (code "272") (name "Net-(C21-Pad1)") (class "Default")
      (node (ref "C21") (pin "1") (pinfunction "1_1") (pintype "passive"))
      (node (ref "R103") (pin "1") (pinfunction "1_1") (pintype "passive"))
      (node (ref "R104") (pin "2") (pinfunction "2_2") (pintype "passive"))
    )
    (net (code "273") (name "Net-(C30-Pad1)") (class "Default")
      (node (ref "C30") (pin "1") (pinfunction "1_1") (pintype "passive"))
      (node (ref "R132") (pin "1") (pinfunction "1_1") (pintype "passive"))
      (node (ref "R133") (pin "1") (pinfunction "1_1") (pintype "passive"))
    )
    (net (code "274") (name "Net-(C31-Pad1)") (class "Default")
      (node (ref "C31") (pin "1") (pinfunction "1_1") (pintype "passive"))
      (node (ref "R149") (pin "1") (pinfunction "1_1") (pintype "passive"))
      (node (ref "R150") (pin "2") (pinfunction "2_2") (pintype "passive"))
    )
    (net (code "275") (name "Net-(C40-Pad1)") (class "Default")
      (node (ref "C40") (pin "1") (pinfunction "1_1") (pintype "passive"))
      (node (ref "R178") (pin "1") (pinfunction "1_1") (pintype "passive"))
      (node (ref "R179") (pin "1") (pinfunction "1_1") (pintype "passive"))
    )
    (net (code "276") (name "Net-(C41-Pad1)") (class "Default")
      (node (ref "C41") (pin "1") (pinfunction "1_1") (pintype "passive"))
      (node (ref "R195") (pin "1") (pinfunction "1_1") (pintype "passive"))
      (node (ref "R196") (pin "2") (pinfunction "2_2") (pintype "passive"))
    )
    (net (code "277") (name "Net-(C50-Pad1)") (class "Default")
      (node (ref "C50") (pin "1") (pinfunction "1_1") (pintype "passive"))
      (node (ref "R224") (pin "1") (pinfunction "1_1") (pintype "passive"))
      (node (ref "R225") (pin "1") (pinfunction "1_1") (pintype "passive"))
    )
    (net (code "278") (name "Net-(C51-Pad1)") (class "Default")
      (node (ref "C51") (pin "1") (pinfunction "1_1") (pintype "passive"))
      (node (ref "R241") (pin "1") (pinfunction "1_1") (pintype "passive"))
      (node (ref "R242") (pin "2") (pinfunction "2_2") (pintype "passive"))
    )
    (net (code "279") (name "Net-(C60-Pad1)") (class "Default")
      (node (ref "C60") (pin "1") (pinfunction "1_1") (pintype "passive"))
      (node (ref "R270") (pin "1") (pinfunction "1_1") (pintype "passive"))
      (node (ref "R271") (pin "1") (pinfunction "1_1") (pintype "passive"))
    )
    (net (code "280") (name "Net-(C61-Pad1)") (class "Default")
      (node (ref "C61") (pin "1") (pinfunction "1_1") (pintype "passive"))
      (node (ref "R287") (pin "1") (pinfunction "1_1") (pintype "passive"))
      (node (ref "R288") (pin "2") (pinfunction "2_2") (pintype "passive"))
    )
    (net (code "281") (name "Net-(C70-Pad1)") (class "Default")
      (node (ref "C70") (pin "1") (pinfunction "1_1") (pintype "passive"))
      (node (ref "R316") (pin "1") (pinfunction "1_1") (pintype "passive"))
      (node (ref "R317") (pin "1") (pinfunction "1_1") (pintype "passive"))
    )
    (net (code "282") (name "Net-(C71-Pad1)") (class "Default")
      (node (ref "C71") (pin "1") (pinfunction "1_1") (pintype "passive"))
      (node (ref "R333") (pin "1") (pinfunction "1_1") (pintype "passive"))
      (node (ref "R334") (pin "2") (pinfunction "2_2") (pintype "passive"))
    )
    (net (code "283") (name "Net-(C80-Pad1)") (class "Default")
      (node (ref "C80") (pin "1") (pinfunction "1_1") (pintype "passive"))
      (node (ref "R362") (pin "1") (pinfunction "1_1") (pintype "passive"))
      (node (ref "R363") (pin "1") (pinfunction "1_1") (pintype "passive"))
    )
    (net (code "284") (name "Net-(C81-Pad1)") (class "Default")
      (node (ref "C81") (pin "1") (pinfunction "1_1") (pintype "passive"))
      (node (ref "R379") (pin "1") (pinfunction "1_1") (pintype "passive"))
      (node (ref "R380") (pin "2") (pinfunction "2_2") (pintype "passive"))
    )
    (net (code "285") (name "Net-(C90-Pad1)") (class "Default")
      (node (ref "C90") (pin "1") (pinfunction "1_1") (pintype "passive"))
      (node (ref "R408") (pin "1") (pinfunction "1_1") (pintype "passive"))
      (node (ref "R409") (pin "1") (pinfunction "1_1") (pintype "passive"))
    )
    (net (code "286") (name "Net-(C91-Pad1)") (class "Default")
      (node (ref "C91") (pin "1") (pinfunction "1_1") (pintype "passive"))
      (node (ref "R425") (pin "1") (pinfunction "1_1") (pintype "passive"))
      (node (ref "R426") (pin "2") (pinfunction "2_2") (pintype "passive"))
    )
    (net (code "287") (name "Net-(C100-Pad1)") (class "Default")
      (node (ref "C100") (pin "1") (pinfunction "1_1") (pintype "passive"))
      (node (ref "R454") (pin "1") (pinfunction "1_1") (pintype "passive"))
      (node (ref "R455") (pin "1") (pinfunction "1_1") (pintype "passive"))
    )
    (net (code "288") (name "Net-(C101-Pad1)") (class "Default")
      (node (ref "C101") (pin "1") (pinfunction "1_1") (pintype "passive"))
      (node (ref "R471") (pin "1") (pinfunction "1_1") (pintype "passive"))
      (node (ref "R472") (pin "2") (pinfunction "2_2") (pintype "passive"))
    )
    (net (code "289") (name "Net-(C110-Pad1)") (class "Default")
      (node (ref "C110") (pin "1") (pinfunction "1_1") (pintype "passive"))
      (node (ref "R500") (pin "1") (pinfunction "1_1") (pintype "passive"))
      (node (ref "R501") (pin "1") (pinfunction "1_1") (pintype "passive"))
    )
    (net (code "290") (name "Net-(C111-Pad1)") (class "Default")
      (node (ref "C111") (pin "1") (pinfunction "1_1") (pintype "passive"))
      (node (ref "R517") (pin "1") (pinfunction "1_1") (pintype "passive"))
      (node (ref "R518") (pin "2") (pinfunction "2_2") (pintype "passive"))
    )
    (net (code "291") (name "Net-(C120-Pad1)") (class "Default")
      (node (ref "C120") (pin "1") (pinfunction "1_1") (pintype "passive"))
      (node (ref "R546") (pin "1") (pinfunction "1_1") (pintype "passive"))
      (node (ref "R547") (pin "1") (pinfunction "1_1") (pintype "passive"))
    )
    (net (code "292") (name "Net-(D4-PadC)") (class "Default")
      (node (ref "D4") (pin "C") (pinfunction "C_C") (pintype "passive"))
      (node (ref "R5") (pin "2") (pinfunction "2_2") (pintype "passive"))
      (node (ref "X1") (pin "22") (pinfunction "22_22") (pintype "passive"))
    )
    (net (code "293") (name "Net-(D5--)") (class "Default")
      (node (ref "D5") (pin "2") (pinfunction "-_2") (pintype "passive"))
      (node (ref "Q4") (pin "2") (pinfunction "C_2") (pintype "passive"))
      (node (ref "START") (pin "TP") (pinfunction "PP_TP") (pintype "input"))
      (node (ref "X1") (pin "5") (pinfunction "5_5") (pintype "passive"))
    )
    (net (code "294") (name "Net-(D6-+)") (class "Default")
      (node (ref "D6") (pin "1") (pinfunction "+_1") (pintype "passive"))
      (node (ref "R27") (pin "1") (pinfunction "1_1") (pintype "passive"))
    )
    (net (code "295") (name "Net-(D9-+)") (class "Default")
      (node (ref "D9") (pin "1") (pinfunction "+_1") (pintype "passive"))
      (node (ref "JP2") (pin "2") (pinfunction "2_2") (pintype "passive"))
    )
    (net (code "296") (name "Net-(D10-+)") (class "Default")
      (node (ref "D10") (pin "1") (pinfunction "+_1") (pintype "passive"))
      (node (ref "JP3") (pin "1") (pinfunction "1_1") (pintype "passive"))
    )
    (net (code "297") (name "Net-(D11-+)") (class "Default")
      (node (ref "D11") (pin "1") (pinfunction "+_1") (pintype "passive"))
      (node (ref "R33") (pin "1") (pinfunction "1_1") (pintype "passive"))
    )
    (net (code "298") (name "Net-(D11--)") (class "Default")
      (node (ref "D11") (pin "2") (pinfunction "-_2") (pintype "passive"))
      (node (ref "IC8") (pin "2") (pinfunction "OUT_2") (pintype "open_collector"))
      (node (ref "JP5") (pin "1") (pinfunction "1_1") (pintype "passive"))
      (node (ref "Q7") (pin "1") (pinfunction "G_1") (pintype "passive"))
      (node (ref "R35") (pin "2") (pinfunction "2_2") (pintype "passive"))
    )
    (net (code "299") (name "Net-(D12-+)") (class "Default")
      (node (ref "D12") (pin "1") (pinfunction "+_1") (pintype "passive"))
      (node (ref "R40") (pin "1") (pinfunction "1_1") (pintype "passive"))
    )
    (net (code "300") (name "Net-(D12--)") (class "Default")
      (node (ref "C9") (pin "2") (pinfunction "2_2") (pintype "passive"))
      (node (ref "D12") (pin "2") (pinfunction "-_2") (pintype "passive"))
      (node (ref "IC10") (pin "2") (pinfunction "TR_2") (pintype "input"))
      (node (ref "IC10") (pin "6") (pinfunction "THR_6") (pintype "input"))
      (node (ref "IC6") (pin "6") (pinfunction "D2_6") (pintype "passive"))
      (node (ref "R41") (pin "1") (pinfunction "1_1") (pintype "passive"))
    )
    (net (code "301") (name "Net-(D13-+)") (class "Default")
      (node (ref "D13") (pin "1") (pinfunction "+_1") (pintype "passive"))
      (node (ref "R61") (pin "1") (pinfunction "1_1") (pintype "passive"))
    )
    (net (code "302") (name "Net-(D13--)") (class "Default")
      (node (ref "D13") (pin "2") (pinfunction "-_2") (pintype "passive"))
      (node (ref "IC16") (pin "2") (pinfunction "OUT_2") (pintype "open_collector"))
      (node (ref "JP7") (pin "1") (pinfunction "1_1") (pintype "passive"))
      (node (ref "Q13") (pin "1") (pinfunction "G_1") (pintype "passive"))
      (node (ref "R77") (pin "2") (pinfunction "2_2") (pintype "passive"))
    )
    (net (code "303") (name "Net-(D16-+)") (class "Default")
      (node (ref "D16") (pin "1") (pinfunction "+_1") (pintype "passive"))
      (node (ref "R47") (pin "1") (pinfunction "1_1") (pintype "passive"))
    )
    (net (code "304") (name "Net-(D19-+)") (class "Default")
      (node (ref "D19") (pin "1") (pinfunction "+_1") (pintype "passive"))
      (node (ref "JP8") (pin "2") (pinfunction "2_2") (pintype "passive"))
    )
    (net (code "305") (name "Net-(D20-+)") (class "Default")
      (node (ref "D20") (pin "1") (pinfunction "+_1") (pintype "passive"))
      (node (ref "JP9") (pin "1") (pinfunction "1_1") (pintype "passive"))
    )
    (net (code "306") (name "Net-(D21--)") (class "Default")
      (node (ref "D21") (pin "2") (pinfunction "-_2") (pintype "passive"))
      (node (ref "Q8") (pin "2") (pinfunction "C_2") (pintype "passive"))
      (node (ref "START1") (pin "TP") (pinfunction "PP_TP") (pintype "input"))
      (node (ref "X4") (pin "5") (pinfunction "5_5") (pintype "passive"))
    )
    (net (code "307") (name "Net-(D22-+)") (class "Default")
      (node (ref "D22") (pin "1") (pinfunction "+_1") (pintype "passive"))
      (node (ref "R80") (pin "1") (pinfunction "1_1") (pintype "passive"))
    )
    (net (code "308") (name "Net-(D22--)") (class "Default")
      (node (ref "C17") (pin "2") (pinfunction "2_2") (pintype "passive"))
      (node (ref "D22") (pin "2") (pinfunction "-_2") (pintype "passive"))
      (node (ref "IC18") (pin "2") (pinfunction "TR_2") (pintype "input"))
      (node (ref "IC18") (pin "6") (pinfunction "THR_6") (pintype "input"))
      (node (ref "IC22") (pin "6") (pinfunction "D2_6") (pintype "passive"))
      (node (ref "R78") (pin "1") (pinfunction "1_1") (pintype "passive"))
    )
    (net (code "309") (name "Net-(D24-PadC)") (class "Default")
      (node (ref "D24") (pin "C") (pinfunction "C_C") (pintype "passive"))
      (node (ref "R53") (pin "2") (pinfunction "2_2") (pintype "passive"))
      (node (ref "X4") (pin "22") (pinfunction "22_22") (pintype "passive"))
    )
    (net (code "310") (name "Net-(D25-+)") (class "Default")
      (node (ref "D25") (pin "1") (pinfunction "+_1") (pintype "passive"))
      (node (ref "R107") (pin "1") (pinfunction "1_1") (pintype "passive"))
    )
    (net (code "311") (name "Net-(D25--)") (class "Default")
      (node (ref "D25") (pin "2") (pinfunction "-_2") (pintype "passive"))
      (node (ref "IC27") (pin "2") (pinfunction "OUT_2") (pintype "open_collector"))
      (node (ref "JP12") (pin "1") (pinfunction "1_1") (pintype "passive"))
      (node (ref "Q20") (pin "1") (pinfunction "G_1") (pintype "passive"))
      (node (ref "R123") (pin "2") (pinfunction "2_2") (pintype "passive"))
    )
    (net (code "312") (name "Net-(D28-+)") (class "Default")
      (node (ref "D28") (pin "1") (pinfunction "+_1") (pintype "passive"))
      (node (ref "R93") (pin "1") (pinfunction "1_1") (pintype "passive"))
    )
    (net (code "313") (name "Net-(D31-+)") (class "Default")
      (node (ref "D31") (pin "1") (pinfunction "+_1") (pintype "passive"))
      (node (ref "JP13") (pin "2") (pinfunction "2_2") (pintype "passive"))
    )
    (net (code "314") (name "Net-(D32-+)") (class "Default")
      (node (ref "D32") (pin "1") (pinfunction "+_1") (pintype "passive"))
      (node (ref "JP14") (pin "1") (pinfunction "1_1") (pintype "passive"))
    )
    (net (code "315") (name "Net-(D33--)") (class "Default")
      (node (ref "D33") (pin "2") (pinfunction "-_2") (pintype "passive"))
      (node (ref "Q15") (pin "2") (pinfunction "C_2") (pintype "passive"))
      (node (ref "START2") (pin "TP") (pinfunction "PP_TP") (pintype "input"))
      (node (ref "X7") (pin "5") (pinfunction "5_5") (pintype "passive"))
    )
    (net (code "316") (name "Net-(D34-+)") (class "Default")
      (node (ref "D34") (pin "1") (pinfunction "+_1") (pintype "passive"))
      (node (ref "R126") (pin "1") (pinfunction "1_1") (pintype "passive"))
    )
    (net (code "317") (name "Net-(D34--)") (class "Default")
      (node (ref "C27") (pin "2") (pinfunction "2_2") (pintype "passive"))
      (node (ref "D34") (pin "2") (pinfunction "-_2") (pintype "passive"))
      (node (ref "IC29") (pin "2") (pinfunction "TR_2") (pintype "input"))
      (node (ref "IC29") (pin "6") (pinfunction "THR_6") (pintype "input"))
      (node (ref "IC33") (pin "6") (pinfunction "D2_6") (pintype "passive"))
      (node (ref "R124") (pin "1") (pinfunction "1_1") (pintype "passive"))
    )
    (net (code "318") (name "Net-(D36-PadC)") (class "Default")
      (node (ref "D36") (pin "C") (pinfunction "C_C") (pintype "passive"))
      (node (ref "R99") (pin "2") (pinfunction "2_2") (pintype "passive"))
      (node (ref "X7") (pin "22") (pinfunction "22_22") (pintype "passive"))
    )
    (net (code "319") (name "Net-(D37-+)") (class "Default")
      (node (ref "D37") (pin "1") (pinfunction "+_1") (pintype "passive"))
      (node (ref "R153") (pin "1") (pinfunction "1_1") (pintype "passive"))
    )
    (net (code "320") (name "Net-(D37--)") (class "Default")
      (node (ref "D37") (pin "2") (pinfunction "-_2") (pintype "passive"))
      (node (ref "IC38") (pin "2") (pinfunction "OUT_2") (pintype "open_collector"))
      (node (ref "JP17") (pin "1") (pinfunction "1_1") (pintype "passive"))
      (node (ref "Q27") (pin "1") (pinfunction "G_1") (pintype "passive"))
      (node (ref "R169") (pin "2") (pinfunction "2_2") (pintype "passive"))
    )
    (net (code "321") (name "Net-(D40-+)") (class "Default")
      (node (ref "D40") (pin "1") (pinfunction "+_1") (pintype "passive"))
      (node (ref "R139") (pin "1") (pinfunction "1_1") (pintype "passive"))
    )
    (net (code "322") (name "Net-(D43-+)") (class "Default")
      (node (ref "D43") (pin "1") (pinfunction "+_1") (pintype "passive"))
      (node (ref "JP18") (pin "2") (pinfunction "2_2") (pintype "passive"))
    )
    (net (code "323") (name "Net-(D44-+)") (class "Default")
      (node (ref "D44") (pin "1") (pinfunction "+_1") (pintype "passive"))
      (node (ref "JP19") (pin "1") (pinfunction "1_1") (pintype "passive"))
    )
    (net (code "324") (name "Net-(D45--)") (class "Default")
      (node (ref "D45") (pin "2") (pinfunction "-_2") (pintype "passive"))
      (node (ref "Q22") (pin "2") (pinfunction "C_2") (pintype "passive"))
      (node (ref "START3") (pin "TP") (pinfunction "PP_TP") (pintype "input"))
      (node (ref "X10") (pin "5") (pinfunction "5_5") (pintype "passive"))
    )
    (net (code "325") (name "Net-(D46-+)") (class "Default")
      (node (ref "D46") (pin "1") (pinfunction "+_1") (pintype "passive"))
      (node (ref "R172") (pin "1") (pinfunction "1_1") (pintype "passive"))
    )
    (net (code "326") (name "Net-(D46--)") (class "Default")
      (node (ref "C37") (pin "2") (pinfunction "2_2") (pintype "passive"))
      (node (ref "D46") (pin "2") (pinfunction "-_2") (pintype "passive"))
      (node (ref "IC40") (pin "2") (pinfunction "TR_2") (pintype "input"))
      (node (ref "IC40") (pin "6") (pinfunction "THR_6") (pintype "input"))
      (node (ref "IC44") (pin "6") (pinfunction "D2_6") (pintype "passive"))
      (node (ref "R170") (pin "1") (pinfunction "1_1") (pintype "passive"))
    )
    (net (code "327") (name "Net-(D48-PadC)") (class "Default")
      (node (ref "D48") (pin "C") (pinfunction "C_C") (pintype "passive"))
      (node (ref "R145") (pin "2") (pinfunction "2_2") (pintype "passive"))
      (node (ref "X10") (pin "22") (pinfunction "22_22") (pintype "passive"))
    )
    (net (code "328") (name "Net-(D49-+)") (class "Default")
      (node (ref "D49") (pin "1") (pinfunction "+_1") (pintype "passive"))
      (node (ref "R199") (pin "1") (pinfunction "1_1") (pintype "passive"))
    )
    (net (code "329") (name "Net-(D49--)") (class "Default")
      (node (ref "D49") (pin "2") (pinfunction "-_2") (pintype "passive"))
      (node (ref "IC49") (pin "2") (pinfunction "OUT_2") (pintype "open_collector"))
      (node (ref "JP22") (pin "1") (pinfunction "1_1") (pintype "passive"))
      (node (ref "Q34") (pin "1") (pinfunction "G_1") (pintype "passive"))
      (node (ref "R215") (pin "2") (pinfunction "2_2") (pintype "passive"))
    )
    (net (code "330") (name "Net-(D52-+)") (class "Default")
      (node (ref "D52") (pin "1") (pinfunction "+_1") (pintype "passive"))
      (node (ref "R185") (pin "1") (pinfunction "1_1") (pintype "passive"))
    )
    (net (code "331") (name "Net-(D55-+)") (class "Default")
      (node (ref "D55") (pin "1") (pinfunction "+_1") (pintype "passive"))
      (node (ref "JP23") (pin "2") (pinfunction "2_2") (pintype "passive"))
    )
    (net (code "332") (name "Net-(D56-+)") (class "Default")
      (node (ref "D56") (pin "1") (pinfunction "+_1") (pintype "passive"))
      (node (ref "JP24") (pin "1") (pinfunction "1_1") (pintype "passive"))
    )
    (net (code "333") (name "Net-(D57--)") (class "Default")
      (node (ref "D57") (pin "2") (pinfunction "-_2") (pintype "passive"))
      (node (ref "Q29") (pin "2") (pinfunction "C_2") (pintype "passive"))
      (node (ref "START4") (pin "TP") (pinfunction "PP_TP") (pintype "input"))
      (node (ref "X13") (pin "5") (pinfunction "5_5") (pintype "passive"))
    )
    (net (code "334") (name "Net-(D58-+)") (class "Default")
      (node (ref "D58") (pin "1") (pinfunction "+_1") (pintype "passive"))
      (node (ref "R218") (pin "1") (pinfunction "1_1") (pintype "passive"))
    )
    (net (code "335") (name "Net-(D58--)") (class "Default")
      (node (ref "C47") (pin "2") (pinfunction "2_2") (pintype "passive"))
      (node (ref "D58") (pin "2") (pinfunction "-_2") (pintype "passive"))
      (node (ref "IC51") (pin "2") (pinfunction "TR_2") (pintype "input"))
      (node (ref "IC51") (pin "6") (pinfunction "THR_6") (pintype "input"))
      (node (ref "IC55") (pin "6") (pinfunction "D2_6") (pintype "passive"))
      (node (ref "R216") (pin "1") (pinfunction "1_1") (pintype "passive"))
    )
    (net (code "336") (name "Net-(D60-PadC)") (class "Default")
      (node (ref "D60") (pin "C") (pinfunction "C_C") (pintype "passive"))
      (node (ref "R191") (pin "2") (pinfunction "2_2") (pintype "passive"))
      (node (ref "X13") (pin "22") (pinfunction "22_22") (pintype "passive"))
    )
    (net (code "337") (name "Net-(D61-+)") (class "Default")
      (node (ref "D61") (pin "1") (pinfunction "+_1") (pintype "passive"))
      (node (ref "R245") (pin "1") (pinfunction "1_1") (pintype "passive"))
    )
    (net (code "338") (name "Net-(D61--)") (class "Default")
      (node (ref "D61") (pin "2") (pinfunction "-_2") (pintype "passive"))
      (node (ref "IC60") (pin "2") (pinfunction "OUT_2") (pintype "open_collector"))
      (node (ref "JP27") (pin "1") (pinfunction "1_1") (pintype "passive"))
      (node (ref "Q41") (pin "1") (pinfunction "G_1") (pintype "passive"))
      (node (ref "R261") (pin "2") (pinfunction "2_2") (pintype "passive"))
    )
    (net (code "339") (name "Net-(D64-+)") (class "Default")
      (node (ref "D64") (pin "1") (pinfunction "+_1") (pintype "passive"))
      (node (ref "R231") (pin "1") (pinfunction "1_1") (pintype "passive"))
    )
    (net (code "340") (name "Net-(D67-+)") (class "Default")
      (node (ref "D67") (pin "1") (pinfunction "+_1") (pintype "passive"))
      (node (ref "JP28") (pin "2") (pinfunction "2_2") (pintype "passive"))
    )
    (net (code "341") (name "Net-(D68-+)") (class "Default")
      (node (ref "D68") (pin "1") (pinfunction "+_1") (pintype "passive"))
      (node (ref "JP29") (pin "1") (pinfunction "1_1") (pintype "passive"))
    )
    (net (code "342") (name "Net-(D69--)") (class "Default")
      (node (ref "D69") (pin "2") (pinfunction "-_2") (pintype "passive"))
      (node (ref "Q36") (pin "2") (pinfunction "C_2") (pintype "passive"))
      (node (ref "START5") (pin "TP") (pinfunction "PP_TP") (pintype "input"))
      (node (ref "X16") (pin "5") (pinfunction "5_5") (pintype "passive"))
    )
    (net (code "343") (name "Net-(D70-+)") (class "Default")
      (node (ref "D70") (pin "1") (pinfunction "+_1") (pintype "passive"))
      (node (ref "R264") (pin "1") (pinfunction "1_1") (pintype "passive"))
    )
    (net (code "344") (name "Net-(D70--)") (class "Default")
      (node (ref "C57") (pin "2") (pinfunction "2_2") (pintype "passive"))
      (node (ref "D70") (pin "2") (pinfunction "-_2") (pintype "passive"))
      (node (ref "IC62") (pin "2") (pinfunction "TR_2") (pintype "input"))
      (node (ref "IC62") (pin "6") (pinfunction "THR_6") (pintype "input"))
      (node (ref "IC66") (pin "6") (pinfunction "D2_6") (pintype "passive"))
      (node (ref "R262") (pin "1") (pinfunction "1_1") (pintype "passive"))
    )
    (net (code "345") (name "Net-(D72-PadC)") (class "Default")
      (node (ref "D72") (pin "C") (pinfunction "C_C") (pintype "passive"))
      (node (ref "R237") (pin "2") (pinfunction "2_2") (pintype "passive"))
      (node (ref "X16") (pin "22") (pinfunction "22_22") (pintype "passive"))
    )
    (net (code "346") (name "Net-(D73-+)") (class "Default")
      (node (ref "D73") (pin "1") (pinfunction "+_1") (pintype "passive"))
      (node (ref "R291") (pin "1") (pinfunction "1_1") (pintype "passive"))
    )
    (net (code "347") (name "Net-(D73--)") (class "Default")
      (node (ref "D73") (pin "2") (pinfunction "-_2") (pintype "passive"))
      (node (ref "IC71") (pin "2") (pinfunction "OUT_2") (pintype "open_collector"))
      (node (ref "JP32") (pin "1") (pinfunction "1_1") (pintype "passive"))
      (node (ref "Q48") (pin "1") (pinfunction "G_1") (pintype "passive"))
      (node (ref "R307") (pin "2") (pinfunction "2_2") (pintype "passive"))
    )
    (net (code "348") (name "Net-(D76-+)") (class "Default")
      (node (ref "D76") (pin "1") (pinfunction "+_1") (pintype "passive"))
      (node (ref "R277") (pin "1") (pinfunction "1_1") (pintype "passive"))
    )
    (net (code "349") (name "Net-(D79-+)") (class "Default")
      (node (ref "D79") (pin "1") (pinfunction "+_1") (pintype "passive"))
      (node (ref "JP33") (pin "2") (pinfunction "2_2") (pintype "passive"))
    )
    (net (code "350") (name "Net-(D80-+)") (class "Default")
      (node (ref "D80") (pin "1") (pinfunction "+_1") (pintype "passive"))
      (node (ref "JP34") (pin "1") (pinfunction "1_1") (pintype "passive"))
    )
    (net (code "351") (name "Net-(D81--)") (class "Default")
      (node (ref "D81") (pin "2") (pinfunction "-_2") (pintype "passive"))
      (node (ref "Q43") (pin "2") (pinfunction "C_2") (pintype "passive"))
      (node (ref "START6") (pin "TP") (pinfunction "PP_TP") (pintype "input"))
      (node (ref "X19") (pin "5") (pinfunction "5_5") (pintype "passive"))
    )
    (net (code "352") (name "Net-(D82-+)") (class "Default")
      (node (ref "D82") (pin "1") (pinfunction "+_1") (pintype "passive"))
      (node (ref "R310") (pin "1") (pinfunction "1_1") (pintype "passive"))
    )
    (net (code "353") (name "Net-(D82--)") (class "Default")
      (node (ref "C67") (pin "2") (pinfunction "2_2") (pintype "passive"))
      (node (ref "D82") (pin "2") (pinfunction "-_2") (pintype "passive"))
      (node (ref "IC73") (pin "2") (pinfunction "TR_2") (pintype "input"))
      (node (ref "IC73") (pin "6") (pinfunction "THR_6") (pintype "input"))
      (node (ref "IC77") (pin "6") (pinfunction "D2_6") (pintype "passive"))
      (node (ref "R308") (pin "1") (pinfunction "1_1") (pintype "passive"))
    )
    (net (code "354") (name "Net-(D84-PadC)") (class "Default")
      (node (ref "D84") (pin "C") (pinfunction "C_C") (pintype "passive"))
      (node (ref "R283") (pin "2") (pinfunction "2_2") (pintype "passive"))
      (node (ref "X19") (pin "22") (pinfunction "22_22") (pintype "passive"))
    )
    (net (code "355") (name "Net-(D85-+)") (class "Default")
      (node (ref "D85") (pin "1") (pinfunction "+_1") (pintype "passive"))
      (node (ref "R337") (pin "1") (pinfunction "1_1") (pintype "passive"))
    )
    (net (code "356") (name "Net-(D85--)") (class "Default")
      (node (ref "D85") (pin "2") (pinfunction "-_2") (pintype "passive"))
      (node (ref "IC82") (pin "2") (pinfunction "OUT_2") (pintype "open_collector"))
      (node (ref "JP37") (pin "1") (pinfunction "1_1") (pintype "passive"))
      (node (ref "Q55") (pin "1") (pinfunction "G_1") (pintype "passive"))
      (node (ref "R353") (pin "2") (pinfunction "2_2") (pintype "passive"))
    )
    (net (code "357") (name "Net-(D88-+)") (class "Default")
      (node (ref "D88") (pin "1") (pinfunction "+_1") (pintype "passive"))
      (node (ref "R323") (pin "1") (pinfunction "1_1") (pintype "passive"))
    )
    (net (code "358") (name "Net-(D91-+)") (class "Default")
      (node (ref "D91") (pin "1") (pinfunction "+_1") (pintype "passive"))
      (node (ref "JP38") (pin "2") (pinfunction "2_2") (pintype "passive"))
    )
    (net (code "359") (name "Net-(D92-+)") (class "Default")
      (node (ref "D92") (pin "1") (pinfunction "+_1") (pintype "passive"))
      (node (ref "JP39") (pin "1") (pinfunction "1_1") (pintype "passive"))
    )
    (net (code "360") (name "Net-(D93--)") (class "Default")
      (node (ref "D93") (pin "2") (pinfunction "-_2") (pintype "passive"))
      (node (ref "Q50") (pin "2") (pinfunction "C_2") (pintype "passive"))
      (node (ref "START7") (pin "TP") (pinfunction "PP_TP") (pintype "input"))
      (node (ref "X22") (pin "5") (pinfunction "5_5") (pintype "passive"))
    )
    (net (code "361") (name "Net-(D94-+)") (class "Default")
      (node (ref "D94") (pin "1") (pinfunction "+_1") (pintype "passive"))
      (node (ref "R356") (pin "1") (pinfunction "1_1") (pintype "passive"))
    )
    (net (code "362") (name "Net-(D94--)") (class "Default")
      (node (ref "C77") (pin "2") (pinfunction "2_2") (pintype "passive"))
      (node (ref "D94") (pin "2") (pinfunction "-_2") (pintype "passive"))
      (node (ref "IC84") (pin "2") (pinfunction "TR_2") (pintype "input"))
      (node (ref "IC84") (pin "6") (pinfunction "THR_6") (pintype "input"))
      (node (ref "IC88") (pin "6") (pinfunction "D2_6") (pintype "passive"))
      (node (ref "R354") (pin "1") (pinfunction "1_1") (pintype "passive"))
    )
    (net (code "363") (name "Net-(D96-PadC)") (class "Default")
      (node (ref "D96") (pin "C") (pinfunction "C_C") (pintype "passive"))
      (node (ref "R329") (pin "2") (pinfunction "2_2") (pintype "passive"))
      (node (ref "X22") (pin "22") (pinfunction "22_22") (pintype "passive"))
    )
    (net (code "364") (name "Net-(D97-+)") (class "Default")
      (node (ref "D97") (pin "1") (pinfunction "+_1") (pintype "passive"))
      (node (ref "R383") (pin "1") (pinfunction "1_1") (pintype "passive"))
    )
    (net (code "365") (name "Net-(D97--)") (class "Default")
      (node (ref "D97") (pin "2") (pinfunction "-_2") (pintype "passive"))
      (node (ref "IC93") (pin "2") (pinfunction "OUT_2") (pintype "open_collector"))
      (node (ref "JP42") (pin "1") (pinfunction "1_1") (pintype "passive"))
      (node (ref "Q62") (pin "1") (pinfunction "G_1") (pintype "passive"))
      (node (ref "R399") (pin "2") (pinfunction "2_2") (pintype "passive"))
    )
    (net (code "366") (name "Net-(D100-+)") (class "Default")
      (node (ref "D100") (pin "1") (pinfunction "+_1") (pintype "passive"))
      (node (ref "R369") (pin "1") (pinfunction "1_1") (pintype "passive"))
    )
    (net (code "367") (name "Net-(D103-+)") (class "Default")
      (node (ref "D103") (pin "1") (pinfunction "+_1") (pintype "passive"))
      (node (ref "JP43") (pin "2") (pinfunction "2_2") (pintype "passive"))
    )
    (net (code "368") (name "Net-(D104-+)") (class "Default")
      (node (ref "D104") (pin "1") (pinfunction "+_1") (pintype "passive"))
      (node (ref "JP44") (pin "1") (pinfunction "1_1") (pintype "passive"))
    )
    (net (code "369") (name "Net-(D105--)") (class "Default")
      (node (ref "D105") (pin "2") (pinfunction "-_2") (pintype "passive"))
      (node (ref "Q57") (pin "2") (pinfunction "C_2") (pintype "passive"))
      (node (ref "START8") (pin "TP") (pinfunction "PP_TP") (pintype "input"))
      (node (ref "X25") (pin "5") (pinfunction "5_5") (pintype "passive"))
    )
    (net (code "370") (name "Net-(D106-+)") (class "Default")
      (node (ref "D106") (pin "1") (pinfunction "+_1") (pintype "passive"))
      (node (ref "R402") (pin "1") (pinfunction "1_1") (pintype "passive"))
    )
    (net (code "371") (name "Net-(D106--)") (class "Default")
      (node (ref "C87") (pin "2") (pinfunction "2_2") (pintype "passive"))
      (node (ref "D106") (pin "2") (pinfunction "-_2") (pintype "passive"))
      (node (ref "IC95") (pin "2") (pinfunction "TR_2") (pintype "input"))
      (node (ref "IC95") (pin "6") (pinfunction "THR_6") (pintype "input"))
      (node (ref "IC99") (pin "6") (pinfunction "D2_6") (pintype "passive"))
      (node (ref "R400") (pin "1") (pinfunction "1_1") (pintype "passive"))
    )
    (net (code "372") (name "Net-(D108-PadC)") (class "Default")
      (node (ref "D108") (pin "C") (pinfunction "C_C") (pintype "passive"))
      (node (ref "R375") (pin "2") (pinfunction "2_2") (pintype "passive"))
      (node (ref "X25") (pin "22") (pinfunction "22_22") (pintype "passive"))
    )
    (net (code "373") (name "Net-(D109-+)") (class "Default")
      (node (ref "D109") (pin "1") (pinfunction "+_1") (pintype "passive"))
      (node (ref "R429") (pin "1") (pinfunction "1_1") (pintype "passive"))
    )
    (net (code "374") (name "Net-(D109--)") (class "Default")
      (node (ref "D109") (pin "2") (pinfunction "-_2") (pintype "passive"))
      (node (ref "IC104") (pin "2") (pinfunction "OUT_2") (pintype "open_collector"))
      (node (ref "JP47") (pin "1") (pinfunction "1_1") (pintype "passive"))
      (node (ref "Q69") (pin "1") (pinfunction "G_1") (pintype "passive"))
      (node (ref "R445") (pin "2") (pinfunction "2_2") (pintype "passive"))
    )
    (net (code "375") (name "Net-(D112-+)") (class "Default")
      (node (ref "D112") (pin "1") (pinfunction "+_1") (pintype "passive"))
      (node (ref "R415") (pin "1") (pinfunction "1_1") (pintype "passive"))
    )
    (net (code "376") (name "Net-(D115-+)") (class "Default")
      (node (ref "D115") (pin "1") (pinfunction "+_1") (pintype "passive"))
      (node (ref "JP48") (pin "2") (pinfunction "2_2") (pintype "passive"))
    )
    (net (code "377") (name "Net-(D116-+)") (class "Default")
      (node (ref "D116") (pin "1") (pinfunction "+_1") (pintype "passive"))
      (node (ref "JP49") (pin "1") (pinfunction "1_1") (pintype "passive"))
    )
    (net (code "378") (name "Net-(D117--)") (class "Default")
      (node (ref "D117") (pin "2") (pinfunction "-_2") (pintype "passive"))
      (node (ref "Q64") (pin "2") (pinfunction "C_2") (pintype "passive"))
      (node (ref "START9") (pin "TP") (pinfunction "PP_TP") (pintype "input"))
      (node (ref "X28") (pin "5") (pinfunction "5_5") (pintype "passive"))
    )
    (net (code "379") (name "Net-(D118-+)") (class "Default")
      (node (ref "D118") (pin "1") (pinfunction "+_1") (pintype "passive"))
      (node (ref "R448") (pin "1") (pinfunction "1_1") (pintype "passive"))
    )
    (net (code "380") (name "Net-(D118--)") (class "Default")
      (node (ref "C97") (pin "2") (pinfunction "2_2") (pintype "passive"))
      (node (ref "D118") (pin "2") (pinfunction "-_2") (pintype "passive"))
      (node (ref "IC106") (pin "2") (pinfunction "TR_2") (pintype "input"))
      (node (ref "IC106") (pin "6") (pinfunction "THR_6") (pintype "input"))
      (node (ref "IC110") (pin "6") (pinfunction "D2_6") (pintype "passive"))
      (node (ref "R446") (pin "1") (pinfunction "1_1") (pintype "passive"))
    )
    (net (code "381") (name "Net-(D120-PadC)") (class "Default")
      (node (ref "D120") (pin "C") (pinfunction "C_C") (pintype "passive"))
      (node (ref "R421") (pin "2") (pinfunction "2_2") (pintype "passive"))
      (node (ref "X28") (pin "22") (pinfunction "22_22") (pintype "passive"))
    )
    (net (code "382") (name "Net-(D121-+)") (class "Default")
      (node (ref "D121") (pin "1") (pinfunction "+_1") (pintype "passive"))
      (node (ref "R475") (pin "1") (pinfunction "1_1") (pintype "passive"))
    )
    (net (code "383") (name "Net-(D121--)") (class "Default")
      (node (ref "D121") (pin "2") (pinfunction "-_2") (pintype "passive"))
      (node (ref "IC115") (pin "2") (pinfunction "OUT_2") (pintype "open_collector"))
      (node (ref "JP52") (pin "1") (pinfunction "1_1") (pintype "passive"))
      (node (ref "Q76") (pin "1") (pinfunction "G_1") (pintype "passive"))
      (node (ref "R491") (pin "2") (pinfunction "2_2") (pintype "passive"))
    )
    (net (code "384") (name "Net-(D124-+)") (class "Default")
      (node (ref "D124") (pin "1") (pinfunction "+_1") (pintype "passive"))
      (node (ref "R461") (pin "1") (pinfunction "1_1") (pintype "passive"))
    )
    (net (code "385") (name "Net-(D127-+)") (class "Default")
      (node (ref "D127") (pin "1") (pinfunction "+_1") (pintype "passive"))
      (node (ref "JP53") (pin "2") (pinfunction "2_2") (pintype "passive"))
    )
    (net (code "386") (name "Net-(D128-+)") (class "Default")
      (node (ref "D128") (pin "1") (pinfunction "+_1") (pintype "passive"))
      (node (ref "JP54") (pin "1") (pinfunction "1_1") (pintype "passive"))
    )
    (net (code "387") (name "Net-(D129--)") (class "Default")
      (node (ref "D129") (pin "2") (pinfunction "-_2") (pintype "passive"))
      (node (ref "Q71") (pin "2") (pinfunction "C_2") (pintype "passive"))
      (node (ref "START10") (pin "TP") (pinfunction "PP_TP") (pintype "input"))
      (node (ref "X31") (pin "5") (pinfunction "5_5") (pintype "passive"))
    )
    (net (code "388") (name "Net-(D130-+)") (class "Default")
      (node (ref "D130") (pin "1") (pinfunction "+_1") (pintype "passive"))
      (node (ref "R494") (pin "1") (pinfunction "1_1") (pintype "passive"))
    )
    (net (code "389") (name "Net-(D130--)") (class "Default")
      (node (ref "C107") (pin "2") (pinfunction "2_2") (pintype "passive"))
      (node (ref "D130") (pin "2") (pinfunction "-_2") (pintype "passive"))
      (node (ref "IC117") (pin "2") (pinfunction "TR_2") (pintype "input"))
      (node (ref "IC117") (pin "6") (pinfunction "THR_6") (pintype "input"))
      (node (ref "IC121") (pin "6") (pinfunction "D2_6") (pintype "passive"))
      (node (ref "R492") (pin "1") (pinfunction "1_1") (pintype "passive"))
    )
    (net (code "390") (name "Net-(D132-PadC)") (class "Default")
      (node (ref "D132") (pin "C") (pinfunction "C_C") (pintype "passive"))
      (node (ref "R467") (pin "2") (pinfunction "2_2") (pintype "passive"))
      (node (ref "X31") (pin "22") (pinfunction "22_22") (pintype "passive"))
    )
    (net (code "391") (name "Net-(D133-+)") (class "Default")
      (node (ref "D133") (pin "1") (pinfunction "+_1") (pintype "passive"))
      (node (ref "R521") (pin "1") (pinfunction "1_1") (pintype "passive"))
    )
    (net (code "392") (name "Net-(D133--)") (class "Default")
      (node (ref "D133") (pin "2") (pinfunction "-_2") (pintype "passive"))
      (node (ref "IC126") (pin "2") (pinfunction "OUT_2") (pintype "open_collector"))
      (node (ref "JP57") (pin "1") (pinfunction "1_1") (pintype "passive"))
      (node (ref "Q83") (pin "1") (pinfunction "G_1") (pintype "passive"))
      (node (ref "R537") (pin "2") (pinfunction "2_2") (pintype "passive"))
    )
    (net (code "393") (name "Net-(D136-+)") (class "Default")
      (node (ref "D136") (pin "1") (pinfunction "+_1") (pintype "passive"))
      (node (ref "R507") (pin "1") (pinfunction "1_1") (pintype "passive"))
    )
    (net (code "394") (name "Net-(D139-+)") (class "Default")
      (node (ref "D139") (pin "1") (pinfunction "+_1") (pintype "passive"))
      (node (ref "JP58") (pin "2") (pinfunction "2_2") (pintype "passive"))
    )
    (net (code "395") (name "Net-(D140-+)") (class "Default")
      (node (ref "D140") (pin "1") (pinfunction "+_1") (pintype "passive"))
      (node (ref "JP59") (pin "1") (pinfunction "1_1") (pintype "passive"))
    )
    (net (code "396") (name "Net-(D141--)") (class "Default")
      (node (ref "D141") (pin "2") (pinfunction "-_2") (pintype "passive"))
      (node (ref "Q78") (pin "2") (pinfunction "C_2") (pintype "passive"))
      (node (ref "START11") (pin "TP") (pinfunction "PP_TP") (pintype "input"))
      (node (ref "X34") (pin "5") (pinfunction "5_5") (pintype "passive"))
    )
    (net (code "397") (name "Net-(D142-+)") (class "Default")
      (node (ref "D142") (pin "1") (pinfunction "+_1") (pintype "passive"))
      (node (ref "R540") (pin "1") (pinfunction "1_1") (pintype "passive"))
    )
    (net (code "398") (name "Net-(D142--)") (class "Default")
      (node (ref "C117") (pin "2") (pinfunction "2_2") (pintype "passive"))
      (node (ref "D142") (pin "2") (pinfunction "-_2") (pintype "passive"))
      (node (ref "IC128") (pin "2") (pinfunction "TR_2") (pintype "input"))
      (node (ref "IC128") (pin "6") (pinfunction "THR_6") (pintype "input"))
      (node (ref "IC132") (pin "6") (pinfunction "D2_6") (pintype "passive"))
      (node (ref "R538") (pin "1") (pinfunction "1_1") (pintype "passive"))
    )
    (net (code "399") (name "Net-(D144-PadC)") (class "Default")
      (node (ref "D144") (pin "C") (pinfunction "C_C") (pintype "passive"))
      (node (ref "R513") (pin "2") (pinfunction "2_2") (pintype "passive"))
      (node (ref "X34") (pin "22") (pinfunction "22_22") (pintype "passive"))
    )
    (net (code "400") (name "Net-(IC1A-+IN)") (class "Default")
      (node (ref "C1") (pin "1") (pinfunction "1_1") (pintype "passive"))
      (node (ref "IC1") (pin "3") (pinfunction "+IN_3") (pintype "input"))
      (node (ref "R5") (pin "1") (pinfunction "1_1") (pintype "passive"))
    )
    (net (code "401") (name "Net-(IC1A--IN)") (class "Default")
      (node (ref "IC1") (pin "2") (pinfunction "-IN_2") (pintype "input"))
      (node (ref "R7") (pin "2") (pinfunction "2_2") (pintype "passive"))
    )
    (net (code "402") (name "Net-(IC1A-OUT)") (class "Default")
      (node (ref "IC1") (pin "1") (pinfunction "OUT_1") (pintype "output"))
      (node (ref "R8") (pin "2") (pinfunction "2_2") (pintype "passive"))
    )
    (net (code "403") (name "Net-(IC1B-+IN)") (class "Default")
      (node (ref "IC1") (pin "5") (pinfunction "+IN_5") (pintype "input"))
      (node (ref "R12") (pin "2") (pinfunction "2_2") (pintype "passive"))
      (node (ref "R17") (pin "2") (pinfunction "2_2") (pintype "passive"))
    )
    (net (code "404") (name "Net-(IC1B--IN)") (class "Default")
      (node (ref "IC1") (pin "6") (pinfunction "-IN_6") (pintype "input"))
      (node (ref "R13") (pin "1") (pinfunction "1_1") (pintype "passive"))
      (node (ref "R14") (pin "2") (pinfunction "2_2") (pintype "passive"))
    )
    (net (code "405") (name "Net-(IC1B-OUT)") (class "Default")
      (node (ref "IC1") (pin "7") (pinfunction "OUT_7") (pintype "output"))
      (node (ref "R16") (pin "1") (pinfunction "1_1") (pintype "passive"))
      (node (ref "R17") (pin "1") (pinfunction "1_1") (pintype "passive"))
    )
    (net (code "406") (name "Net-(IC5A-A)") (class "Default")
      (node (ref "IC5") (pin "10") (pinfunction "A_10") (pintype "input"))
      (node (ref "IC6") (pin "1") (pinfunction "D1_1") (pintype "passive"))
      (node (ref "R11") (pin "1") (pinfunction "1_1") (pintype "passive"))
      (node (ref "X1") (pin "4") (pinfunction "4_4") (pintype "passive"))
      (node (ref "X3") (pin "2") (pinfunction "S_2") (pintype "passive"))
    )
    (net (code "407") (name "Net-(IC5A-B)") (class "Default")
      (node (ref "IC5") (pin "13") (pinfunction "B_13") (pintype "input"))
      (node (ref "IC6") (pin "4") (pinfunction "D4_4") (pintype "passive"))
      (node (ref "R10") (pin "1") (pinfunction "1_1") (pintype "passive"))
      (node (ref "X1") (pin "3") (pinfunction "3_3") (pintype "passive"))
      (node (ref "X3") (pin "3") (pinfunction "S_3") (pintype "passive"))
    )
    (net (code "408") (name "Net-(IC5A-C)") (class "Default")
      (node (ref "IC5") (pin "12") (pinfunction "C_12") (pintype "input"))
      (node (ref "IC6") (pin "3") (pinfunction "D3_3") (pintype "passive"))
      (node (ref "R9") (pin "1") (pinfunction "1_1") (pintype "passive"))
      (node (ref "X1") (pin "2") (pinfunction "2_2") (pintype "passive"))
      (node (ref "X3") (pin "4") (pinfunction "S_4") (pintype "passive"))
    )
    (net (code "409") (name "Net-(IC5A-Q0)") (class "Default")
      (node (ref "IC5") (pin "3") (pinfunction "Q0_3") (pintype "output"))
      (node (ref "IC7") (pin "1") (pinfunction "I1_1") (pintype "input"))
      (node (ref "IC7") (pin "2") (pinfunction "I2_2") (pintype "input"))
      (node (ref "Q6") (pin "1") (pinfunction "G_1") (pintype "passive"))
    )
    (net (code "410") (name "Net-(IC5A-Q1)") (class "Default")
      (node (ref "IC5") (pin "14") (pinfunction "Q1_14") (pintype "output"))
      (node (ref "IC7") (pin "6") (pinfunction "I6_6") (pintype "input"))
    )
    (net (code "411") (name "Net-(IC5A-Q2)") (class "Default")
      (node (ref "IC5") (pin "2") (pinfunction "Q2_2") (pintype "output"))
      (node (ref "IC7") (pin "7") (pinfunction "I7_7") (pintype "input"))
    )
    (net (code "412") (name "Net-(IC5A-Q3)") (class "Default")
      (node (ref "IC5") (pin "15") (pinfunction "Q3_15") (pintype "output"))
      (node (ref "IC7") (pin "5") (pinfunction "I5_5") (pintype "input"))
    )
    (net (code "413") (name "Net-(IC5A-Q4)") (class "Default")
      (node (ref "IC5") (pin "1") (pinfunction "Q4_1") (pintype "output"))
      (node (ref "IC7") (pin "4") (pinfunction "I4_4") (pintype "input"))
    )
    (net (code "414") (name "Net-(IC5A-Q5)") (class "Default")
      (node (ref "IC5") (pin "6") (pinfunction "Q5_6") (pintype "output"))
      (node (ref "IC7") (pin "3") (pinfunction "I3_3") (pintype "input"))
    )
    (net (code "415") (name "Net-(IC7-O2)") (class "Default")
      (node (ref "IC7") (pin "15") (pinfunction "O2_15") (pintype "open_collector"))
      (node (ref "R28") (pin "1") (pinfunction "1_1") (pintype "passive"))
    )
    (net (code "416") (name "Net-(IC8A-+IN)") (class "Default")
      (node (ref "IC8") (pin "5") (pinfunction "+IN_5") (pintype "input"))
      (node (ref "R31") (pin "1") (pinfunction "1_1") (pintype "passive"))
      (node (ref "R32") (pin "2") (pinfunction "2_2") (pintype "passive"))
      (node (ref "R33") (pin "2") (pinfunction "2_2") (pintype "passive"))
    )
    (net (code "417") (name "Net-(IC8A--IN)") (class "Default")
      (node (ref "C8") (pin "1") (pinfunction "1_1") (pintype "passive"))
      (node (ref "IC8") (pin "4") (pinfunction "-IN_4") (pintype "input"))
      (node (ref "R30") (pin "1") (pinfunction "1_1") (pintype "passive"))
    )
    (net (code "418") (name "Net-(IC8B-+IN)") (class "Default")
      (node (ref "IC8") (pin "7") (pinfunction "+IN_7") (pintype "input"))
      (node (ref "R21") (pin "1") (pinfunction "1_1") (pintype "passive"))
      (node (ref "R22") (pin "1") (pinfunction "1_1") (pintype "passive"))
    )
    (net (code "419") (name "Net-(IC8B--IN)") (class "Default")
      (node (ref "IC8") (pin "6") (pinfunction "-IN_6") (pintype "input"))
      (node (ref "IC8") (pin "8") (pinfunction "-IN_8") (pintype "input"))
      (node (ref "R20") (pin "1") (pinfunction "1_1") (pintype "passive"))
    )
    (net (code "420") (name "Net-(IC8B-OUT)") (class "Default")
      (node (ref "IC8") (pin "1") (pinfunction "OUT_1") (pintype "open_collector"))
      (node (ref "R24") (pin "2") (pinfunction "2_2") (pintype "passive"))
      (node (ref "R25") (pin "2") (pinfunction "2_2") (pintype "passive"))
    )
    (net (code "421") (name "Net-(IC8C-+IN)") (class "Default")
      (node (ref "C5") (pin "1") (pinfunction "1_1") (pintype "passive"))
      (node (ref "IC8") (pin "9") (pinfunction "+IN_9") (pintype "input"))
      (node (ref "R22") (pin "2") (pinfunction "2_2") (pintype "passive"))
      (node (ref "R23") (pin "2") (pinfunction "2_2") (pintype "passive"))
    )
    (net (code "422") (name "Net-(IC8C-OUT)") (class "Default")
      (node (ref "C6") (pin "2") (pinfunction "2_2") (pintype "passive"))
      (node (ref "IC8") (pin "14") (pinfunction "OUT_14") (pintype "open_collector"))
      (node (ref "R26") (pin "2") (pinfunction "2_2") (pintype "passive"))
    )
    (net (code "423") (name "Net-(IC9-ADJ)") (class "Default")
      (node (ref "IC9") (pin "1") (pinfunction "ADJ_1") (pintype "input"))
      (node (ref "R20") (pin "2") (pinfunction "2_2") (pintype "passive"))
      (node (ref "R34") (pin "1") (pinfunction "1_1") (pintype "passive"))
      (node (ref "X1") (pin "7") (pinfunction "7_7") (pintype "passive"))
    )
    (net (code "424") (name "Net-(IC9-VI)") (class "Default")
      (node (ref "IC9") (pin "3") (pinfunction "VI_3") (pintype "input"))
      (node (ref "Q5") (pin "2") (pinfunction "C_2") (pintype "passive"))
    )
    (net (code "425") (name "Net-(IC9-VO)") (class "Default")
      (node (ref "IC9") (pin "2") (pinfunction "VO_2") (pintype "passive"))
      (node (ref "R34") (pin "2") (pinfunction "2_2") (pintype "passive"))
    )
    (net (code "426") (name "Net-(IC10-CV)") (class "Default")
      (node (ref "IC10") (pin "5") (pinfunction "CV_5") (pintype "input"))
      (node (ref "R44") (pin "2") (pinfunction "2_2") (pintype "passive"))
    )
    (net (code "427") (name "Net-(IC10-Q)") (class "Default")
      (node (ref "IC10") (pin "3") (pinfunction "Q_3") (pintype "output"))
      (node (ref "IC11") (pin "12") (pinfunction "A_12") (pintype "input"))
      (node (ref "R44") (pin "1") (pinfunction "1_1") (pintype "passive"))
    )
    (net (code "428") (name "Net-(IC11B-B)") (class "Default")
      (node (ref "IC11") (pin "11") (pinfunction "B_11") (pintype "input"))
      (node (ref "IC11") (pin "9") (pinfunction "~{Q}_9") (pintype "output"))
      (node (ref "R46") (pin "2") (pinfunction "2_2") (pintype "passive"))
    )
    (net (code "429") (name "Net-(IC11B-T2)") (class "Default")
      (node (ref "C10") (pin "1") (pinfunction "1_1") (pintype "passive"))
      (node (ref "IC11") (pin "14") (pinfunction "T2_14") (pintype "input"))
      (node (ref "R45") (pin "1") (pinfunction "1_1") (pintype "passive"))
    )
    (net (code "430") (name "Net-(IC12A-A)") (class "Default")
      (node (ref "IC12") (pin "10") (pinfunction "A_10") (pintype "input"))
      (node (ref "IC22") (pin "1") (pinfunction "D1_1") (pintype "passive"))
      (node (ref "R52") (pin "1") (pinfunction "1_1") (pintype "passive"))
      (node (ref "X4") (pin "4") (pinfunction "4_4") (pintype "passive"))
      (node (ref "X5") (pin "2") (pinfunction "S_2") (pintype "passive"))
    )
    (net (code "431") (name "Net-(IC12A-B)") (class "Default")
      (node (ref "IC12") (pin "13") (pinfunction "B_13") (pintype "input"))
      (node (ref "IC22") (pin "4") (pinfunction "D4_4") (pintype "passive"))
      (node (ref "R51") (pin "1") (pinfunction "1_1") (pintype "passive"))
      (node (ref "X4") (pin "3") (pinfunction "3_3") (pintype "passive"))
      (node (ref "X5") (pin "3") (pinfunction "S_3") (pintype "passive"))
    )
    (net (code "432") (name "Net-(IC12A-C)") (class "Default")
      (node (ref "IC12") (pin "12") (pinfunction "C_12") (pintype "input"))
      (node (ref "IC22") (pin "3") (pinfunction "D3_3") (pintype "passive"))
      (node (ref "R50") (pin "1") (pinfunction "1_1") (pintype "passive"))
      (node (ref "X4") (pin "2") (pinfunction "2_2") (pintype "passive"))
      (node (ref "X5") (pin "4") (pinfunction "S_4") (pintype "passive"))
    )
    (net (code "433") (name "Net-(IC12A-Q0)") (class "Default")
      (node (ref "IC12") (pin "3") (pinfunction "Q0_3") (pintype "output"))
      (node (ref "IC15") (pin "1") (pinfunction "I1_1") (pintype "input"))
      (node (ref "IC15") (pin "2") (pinfunction "I2_2") (pintype "input"))
      (node (ref "Q14") (pin "1") (pinfunction "G_1") (pintype "passive"))
    )
    (net (code "434") (name "Net-(IC12A-Q1)") (class "Default")
      (node (ref "IC12") (pin "14") (pinfunction "Q1_14") (pintype "output"))
      (node (ref "IC15") (pin "6") (pinfunction "I6_6") (pintype "input"))
    )
    (net (code "435") (name "Net-(IC12A-Q2)") (class "Default")
      (node (ref "IC12") (pin "2") (pinfunction "Q2_2") (pintype "output"))
      (node (ref "IC15") (pin "7") (pinfunction "I7_7") (pintype "input"))
    )
    (net (code "436") (name "Net-(IC12A-Q3)") (class "Default")
      (node (ref "IC12") (pin "15") (pinfunction "Q3_15") (pintype "output"))
      (node (ref "IC15") (pin "5") (pinfunction "I5_5") (pintype "input"))
    )
    (net (code "437") (name "Net-(IC12A-Q4)") (class "Default")
      (node (ref "IC12") (pin "1") (pinfunction "Q4_1") (pintype "output"))
      (node (ref "IC15") (pin "4") (pinfunction "I4_4") (pintype "input"))
    )
    (net (code "438") (name "Net-(IC12A-Q5)") (class "Default")
      (node (ref "IC12") (pin "6") (pinfunction "Q5_6") (pintype "output"))
      (node (ref "IC15") (pin "3") (pinfunction "I3_3") (pintype "input"))
    )
    (net (code "439") (name "Net-(IC14-ADJ)") (class "Default")
      (node (ref "IC14") (pin "1") (pinfunction "ADJ_1") (pintype "input"))
      (node (ref "R48") (pin "1") (pinfunction "1_1") (pintype "passive"))
      (node (ref "R55") (pin "2") (pinfunction "2_2") (pintype "passive"))
      (node (ref "X4") (pin "7") (pinfunction "7_7") (pintype "passive"))
    )
    (net (code "440") (name "Net-(IC14-VI)") (class "Default")
      (node (ref "IC14") (pin "3") (pinfunction "VI_3") (pintype "input"))
      (node (ref "Q11") (pin "2") (pinfunction "C_2") (pintype "passive"))
    )
    (net (code "441") (name "Net-(IC14-VO)") (class "Default")
      (node (ref "IC14") (pin "2") (pinfunction "VO_2") (pintype "passive"))
      (node (ref "R48") (pin "2") (pinfunction "2_2") (pintype "passive"))
    )
    (net (code "442") (name "Net-(IC15-O2)") (class "Default")
      (node (ref "IC15") (pin "15") (pinfunction "O2_15") (pintype "open_collector"))
      (node (ref "R70") (pin "1") (pinfunction "1_1") (pintype "passive"))
    )
    (net (code "443") (name "Net-(IC16A-+IN)") (class "Default")
      (node (ref "IC16") (pin "5") (pinfunction "+IN_5") (pintype "input"))
      (node (ref "R59") (pin "1") (pinfunction "1_1") (pintype "passive"))
      (node (ref "R60") (pin "2") (pinfunction "2_2") (pintype "passive"))
      (node (ref "R61") (pin "2") (pinfunction "2_2") (pintype "passive"))
    )
    (net (code "444") (name "Net-(IC16A--IN)") (class "Default")
      (node (ref "C12") (pin "1") (pinfunction "1_1") (pintype "passive"))
      (node (ref "IC16") (pin "4") (pinfunction "-IN_4") (pintype "input"))
      (node (ref "R58") (pin "1") (pinfunction "1_1") (pintype "passive"))
    )
    (net (code "445") (name "Net-(IC16B-+IN)") (class "Default")
      (node (ref "IC16") (pin "7") (pinfunction "+IN_7") (pintype "input"))
      (node (ref "R56") (pin "1") (pinfunction "1_1") (pintype "passive"))
      (node (ref "R73") (pin "1") (pinfunction "1_1") (pintype "passive"))
    )
    (net (code "446") (name "Net-(IC16B--IN)") (class "Default")
      (node (ref "IC16") (pin "6") (pinfunction "-IN_6") (pintype "input"))
      (node (ref "IC16") (pin "8") (pinfunction "-IN_8") (pintype "input"))
      (node (ref "R55") (pin "1") (pinfunction "1_1") (pintype "passive"))
    )
    (net (code "447") (name "Net-(IC16B-OUT)") (class "Default")
      (node (ref "IC16") (pin "1") (pinfunction "OUT_1") (pintype "open_collector"))
      (node (ref "R57") (pin "2") (pinfunction "2_2") (pintype "passive"))
      (node (ref "R62") (pin "2") (pinfunction "2_2") (pintype "passive"))
    )
    (net (code "448") (name "Net-(IC16C-+IN)") (class "Default")
      (node (ref "C15") (pin "1") (pinfunction "1_1") (pintype "passive"))
      (node (ref "IC16") (pin "9") (pinfunction "+IN_9") (pintype "input"))
      (node (ref "R64") (pin "2") (pinfunction "2_2") (pintype "passive"))
      (node (ref "R73") (pin "2") (pinfunction "2_2") (pintype "passive"))
    )
    (net (code "449") (name "Net-(IC16C-OUT)") (class "Default")
      (node (ref "C16") (pin "2") (pinfunction "2_2") (pintype "passive"))
      (node (ref "IC16") (pin "14") (pinfunction "OUT_14") (pintype "open_collector"))
      (node (ref "R63") (pin "2") (pinfunction "2_2") (pintype "passive"))
    )
    (net (code "450") (name "Net-(IC18-CV)") (class "Default")
      (node (ref "IC18") (pin "5") (pinfunction "CV_5") (pintype "input"))
      (node (ref "R79") (pin "2") (pinfunction "2_2") (pintype "passive"))
    )
    (net (code "451") (name "Net-(IC18-Q)") (class "Default")
      (node (ref "IC18") (pin "3") (pinfunction "Q_3") (pintype "output"))
      (node (ref "IC19") (pin "12") (pinfunction "A_12") (pintype "input"))
      (node (ref "R79") (pin "1") (pinfunction "1_1") (pintype "passive"))
    )
    (net (code "452") (name "Net-(IC19B-B)") (class "Default")
      (node (ref "IC19") (pin "11") (pinfunction "B_11") (pintype "input"))
      (node (ref "IC19") (pin "9") (pinfunction "~{Q}_9") (pintype "output"))
      (node (ref "R85") (pin "2") (pinfunction "2_2") (pintype "passive"))
    )
    (net (code "453") (name "Net-(IC19B-T2)") (class "Default")
      (node (ref "C19") (pin "1") (pinfunction "1_1") (pintype "passive"))
      (node (ref "IC19") (pin "14") (pinfunction "T2_14") (pintype "input"))
      (node (ref "R83") (pin "1") (pinfunction "1_1") (pintype "passive"))
    )
    (net (code "454") (name "Net-(IC21A-+IN)") (class "Default")
      (node (ref "C14") (pin "1") (pinfunction "1_1") (pintype "passive"))
      (node (ref "IC21") (pin "3") (pinfunction "+IN_3") (pintype "input"))
      (node (ref "R53") (pin "1") (pinfunction "1_1") (pintype "passive"))
    )
    (net (code "455") (name "Net-(IC21A--IN)") (class "Default")
      (node (ref "IC21") (pin "2") (pinfunction "-IN_2") (pintype "input"))
      (node (ref "R54") (pin "2") (pinfunction "2_2") (pintype "passive"))
    )
    (net (code "456") (name "Net-(IC21A-OUT)") (class "Default")
      (node (ref "IC21") (pin "1") (pinfunction "OUT_1") (pintype "output"))
      (node (ref "R86") (pin "2") (pinfunction "2_2") (pintype "passive"))
    )
    (net (code "457") (name "Net-(IC21B-+IN)") (class "Default")
      (node (ref "IC21") (pin "5") (pinfunction "+IN_5") (pintype "input"))
      (node (ref "R87") (pin "2") (pinfunction "2_2") (pintype "passive"))
      (node (ref "R88") (pin "2") (pinfunction "2_2") (pintype "passive"))
    )
    (net (code "458") (name "Net-(IC21B--IN)") (class "Default")
      (node (ref "IC21") (pin "6") (pinfunction "-IN_6") (pintype "input"))
      (node (ref "R89") (pin "1") (pinfunction "1_1") (pintype "passive"))
      (node (ref "R90") (pin "2") (pinfunction "2_2") (pintype "passive"))
    )
    (net (code "459") (name "Net-(IC21B-OUT)") (class "Default")
      (node (ref "IC21") (pin "7") (pinfunction "OUT_7") (pintype "output"))
      (node (ref "R74") (pin "1") (pinfunction "1_1") (pintype "passive"))
      (node (ref "R88") (pin "1") (pinfunction "1_1") (pintype "passive"))
    )
    (net (code "460") (name "Net-(IC23A-A)") (class "Default")
      (node (ref "IC23") (pin "10") (pinfunction "A_10") (pintype "input"))
      (node (ref "IC33") (pin "1") (pinfunction "D1_1") (pintype "passive"))
      (node (ref "R98") (pin "1") (pinfunction "1_1") (pintype "passive"))
      (node (ref "X7") (pin "4") (pinfunction "4_4") (pintype "passive"))
      (node (ref "X8") (pin "2") (pinfunction "S_2") (pintype "passive"))
    )
    (net (code "461") (name "Net-(IC23A-B)") (class "Default")
      (node (ref "IC23") (pin "13") (pinfunction "B_13") (pintype "input"))
      (node (ref "IC33") (pin "4") (pinfunction "D4_4") (pintype "passive"))
      (node (ref "R97") (pin "1") (pinfunction "1_1") (pintype "passive"))
      (node (ref "X7") (pin "3") (pinfunction "3_3") (pintype "passive"))
      (node (ref "X8") (pin "3") (pinfunction "S_3") (pintype "passive"))
    )
    (net (code "462") (name "Net-(IC23A-C)") (class "Default")
      (node (ref "IC23") (pin "12") (pinfunction "C_12") (pintype "input"))
      (node (ref "IC33") (pin "3") (pinfunction "D3_3") (pintype "passive"))
      (node (ref "R96") (pin "1") (pinfunction "1_1") (pintype "passive"))
      (node (ref "X7") (pin "2") (pinfunction "2_2") (pintype "passive"))
      (node (ref "X8") (pin "4") (pinfunction "S_4") (pintype "passive"))
    )
    (net (code "463") (name "Net-(IC23A-Q0)") (class "Default")
      (node (ref "IC23") (pin "3") (pinfunction "Q0_3") (pintype "output"))
      (node (ref "IC26") (pin "1") (pinfunction "I1_1") (pintype "input"))
      (node (ref "IC26") (pin "2") (pinfunction "I2_2") (pintype "input"))
      (node (ref "Q21") (pin "1") (pinfunction "G_1") (pintype "passive"))
    )
    (net (code "464") (name "Net-(IC23A-Q1)") (class "Default")
      (node (ref "IC23") (pin "14") (pinfunction "Q1_14") (pintype "output"))
      (node (ref "IC26") (pin "6") (pinfunction "I6_6") (pintype "input"))
    )
    (net (code "465") (name "Net-(IC23A-Q2)") (class "Default")
      (node (ref "IC23") (pin "2") (pinfunction "Q2_2") (pintype "output"))
      (node (ref "IC26") (pin "7") (pinfunction "I7_7") (pintype "input"))
    )
    (net (code "466") (name "Net-(IC23A-Q3)") (class "Default")
      (node (ref "IC23") (pin "15") (pinfunction "Q3_15") (pintype "output"))
      (node (ref "IC26") (pin "5") (pinfunction "I5_5") (pintype "input"))
    )
    (net (code "467") (name "Net-(IC23A-Q4)") (class "Default")
      (node (ref "IC23") (pin "1") (pinfunction "Q4_1") (pintype "output"))
      (node (ref "IC26") (pin "4") (pinfunction "I4_4") (pintype "input"))
    )
    (net (code "468") (name "Net-(IC23A-Q5)") (class "Default")
      (node (ref "IC23") (pin "6") (pinfunction "Q5_6") (pintype "output"))
      (node (ref "IC26") (pin "3") (pinfunction "I3_3") (pintype "input"))
    )
    (net (code "469") (name "Net-(IC25-ADJ)") (class "Default")
      (node (ref "IC25") (pin "1") (pinfunction "ADJ_1") (pintype "input"))
      (node (ref "R101") (pin "2") (pinfunction "2_2") (pintype "passive"))
      (node (ref "R94") (pin "1") (pinfunction "1_1") (pintype "passive"))
      (node (ref "X7") (pin "7") (pinfunction "7_7") (pintype "passive"))
    )
    (net (code "470") (name "Net-(IC25-VI)") (class "Default")
      (node (ref "IC25") (pin "3") (pinfunction "VI_3") (pintype "input"))
      (node (ref "Q18") (pin "2") (pinfunction "C_2") (pintype "passive"))
    )
    (net (code "471") (name "Net-(IC25-VO)") (class "Default")
      (node (ref "IC25") (pin "2") (pinfunction "VO_2") (pintype "passive"))
      (node (ref "R94") (pin "2") (pinfunction "2_2") (pintype "passive"))
    )
    (net (code "472") (name "Net-(IC26-O2)") (class "Default")
      (node (ref "IC26") (pin "15") (pinfunction "O2_15") (pintype "open_collector"))
      (node (ref "R116") (pin "1") (pinfunction "1_1") (pintype "passive"))
    )
    (net (code "473") (name "Net-(IC27A-+IN)") (class "Default")
      (node (ref "IC27") (pin "5") (pinfunction "+IN_5") (pintype "input"))
      (node (ref "R105") (pin "1") (pinfunction "1_1") (pintype "passive"))
      (node (ref "R106") (pin "2") (pinfunction "2_2") (pintype "passive"))
      (node (ref "R107") (pin "2") (pinfunction "2_2") (pintype "passive"))
    )
    (net (code "474") (name "Net-(IC27A--IN)") (class "Default")
      (node (ref "C22") (pin "1") (pinfunction "1_1") (pintype "passive"))
      (node (ref "IC27") (pin "4") (pinfunction "-IN_4") (pintype "input"))
      (node (ref "R104") (pin "1") (pinfunction "1_1") (pintype "passive"))
    )
    (net (code "475") (name "Net-(IC27B-+IN)") (class "Default")
      (node (ref "IC27") (pin "7") (pinfunction "+IN_7") (pintype "input"))
      (node (ref "R102") (pin "1") (pinfunction "1_1") (pintype "passive"))
      (node (ref "R119") (pin "1") (pinfunction "1_1") (pintype "passive"))
    )
    (net (code "476") (name "Net-(IC27B--IN)") (class "Default")
      (node (ref "IC27") (pin "6") (pinfunction "-IN_6") (pintype "input"))
      (node (ref "IC27") (pin "8") (pinfunction "-IN_8") (pintype "input"))
      (node (ref "R101") (pin "1") (pinfunction "1_1") (pintype "passive"))
    )
    (net (code "477") (name "Net-(IC27B-OUT)") (class "Default")
      (node (ref "IC27") (pin "1") (pinfunction "OUT_1") (pintype "open_collector"))
      (node (ref "R103") (pin "2") (pinfunction "2_2") (pintype "passive"))
      (node (ref "R108") (pin "2") (pinfunction "2_2") (pintype "passive"))
    )
    (net (code "478") (name "Net-(IC27C-+IN)") (class "Default")
      (node (ref "C25") (pin "1") (pinfunction "1_1") (pintype "passive"))
      (node (ref "IC27") (pin "9") (pinfunction "+IN_9") (pintype "input"))
      (node (ref "R110") (pin "2") (pinfunction "2_2") (pintype "passive"))
      (node (ref "R119") (pin "2") (pinfunction "2_2") (pintype "passive"))
    )
    (net (code "479") (name "Net-(IC27C-OUT)") (class "Default")
      (node (ref "C26") (pin "2") (pinfunction "2_2") (pintype "passive"))
      (node (ref "IC27") (pin "14") (pinfunction "OUT_14") (pintype "open_collector"))
      (node (ref "R109") (pin "2") (pinfunction "2_2") (pintype "passive"))
    )
    (net (code "480") (name "Net-(IC29-CV)") (class "Default")
      (node (ref "IC29") (pin "5") (pinfunction "CV_5") (pintype "input"))
      (node (ref "R125") (pin "2") (pinfunction "2_2") (pintype "passive"))
    )
    (net (code "481") (name "Net-(IC29-Q)") (class "Default")
      (node (ref "IC29") (pin "3") (pinfunction "Q_3") (pintype "output"))
      (node (ref "IC30") (pin "12") (pinfunction "A_12") (pintype "input"))
      (node (ref "R125") (pin "1") (pinfunction "1_1") (pintype "passive"))
    )
    (net (code "482") (name "Net-(IC30B-B)") (class "Default")
      (node (ref "IC30") (pin "11") (pinfunction "B_11") (pintype "input"))
      (node (ref "IC30") (pin "9") (pinfunction "~{Q}_9") (pintype "output"))
      (node (ref "R131") (pin "2") (pinfunction "2_2") (pintype "passive"))
    )
    (net (code "483") (name "Net-(IC30B-T2)") (class "Default")
      (node (ref "C29") (pin "1") (pinfunction "1_1") (pintype "passive"))
      (node (ref "IC30") (pin "14") (pinfunction "T2_14") (pintype "input"))
      (node (ref "R129") (pin "1") (pinfunction "1_1") (pintype "passive"))
    )
    (net (code "484") (name "Net-(IC32A-+IN)") (class "Default")
      (node (ref "C24") (pin "1") (pinfunction "1_1") (pintype "passive"))
      (node (ref "IC32") (pin "3") (pinfunction "+IN_3") (pintype "input"))
      (node (ref "R99") (pin "1") (pinfunction "1_1") (pintype "passive"))
    )
    (net (code "485") (name "Net-(IC32A--IN)") (class "Default")
      (node (ref "IC32") (pin "2") (pinfunction "-IN_2") (pintype "input"))
      (node (ref "R100") (pin "2") (pinfunction "2_2") (pintype "passive"))
    )
    (net (code "486") (name "Net-(IC32A-OUT)") (class "Default")
      (node (ref "IC32") (pin "1") (pinfunction "OUT_1") (pintype "output"))
      (node (ref "R132") (pin "2") (pinfunction "2_2") (pintype "passive"))
    )
    (net (code "487") (name "Net-(IC32B-+IN)") (class "Default")
      (node (ref "IC32") (pin "5") (pinfunction "+IN_5") (pintype "input"))
      (node (ref "R133") (pin "2") (pinfunction "2_2") (pintype "passive"))
      (node (ref "R134") (pin "2") (pinfunction "2_2") (pintype "passive"))
    )
    (net (code "488") (name "Net-(IC32B--IN)") (class "Default")
      (node (ref "IC32") (pin "6") (pinfunction "-IN_6") (pintype "input"))
      (node (ref "R135") (pin "1") (pinfunction "1_1") (pintype "passive"))
      (node (ref "R136") (pin "2") (pinfunction "2_2") (pintype "passive"))
    )
    (net (code "489") (name "Net-(IC32B-OUT)") (class "Default")
      (node (ref "IC32") (pin "7") (pinfunction "OUT_7") (pintype "output"))
      (node (ref "R120") (pin "1") (pinfunction "1_1") (pintype "passive"))
      (node (ref "R134") (pin "1") (pinfunction "1_1") (pintype "passive"))
    )
    (net (code "490") (name "Net-(IC34A-A)") (class "Default")
      (node (ref "IC34") (pin "10") (pinfunction "A_10") (pintype "input"))
      (node (ref "IC44") (pin "1") (pinfunction "D1_1") (pintype "passive"))
      (node (ref "R144") (pin "1") (pinfunction "1_1") (pintype "passive"))
      (node (ref "X10") (pin "4") (pinfunction "4_4") (pintype "passive"))
      (node (ref "X11") (pin "2") (pinfunction "S_2") (pintype "passive"))
    )
    (net (code "491") (name "Net-(IC34A-B)") (class "Default")
      (node (ref "IC34") (pin "13") (pinfunction "B_13") (pintype "input"))
      (node (ref "IC44") (pin "4") (pinfunction "D4_4") (pintype "passive"))
      (node (ref "R143") (pin "1") (pinfunction "1_1") (pintype "passive"))
      (node (ref "X10") (pin "3") (pinfunction "3_3") (pintype "passive"))
      (node (ref "X11") (pin "3") (pinfunction "S_3") (pintype "passive"))
    )
    (net (code "492") (name "Net-(IC34A-C)") (class "Default")
      (node (ref "IC34") (pin "12") (pinfunction "C_12") (pintype "input"))
      (node (ref "IC44") (pin "3") (pinfunction "D3_3") (pintype "passive"))
      (node (ref "R142") (pin "1") (pinfunction "1_1") (pintype "passive"))
      (node (ref "X10") (pin "2") (pinfunction "2_2") (pintype "passive"))
      (node (ref "X11") (pin "4") (pinfunction "S_4") (pintype "passive"))
    )
    (net (code "493") (name "Net-(IC34A-Q0)") (class "Default")
      (node (ref "IC34") (pin "3") (pinfunction "Q0_3") (pintype "output"))
      (node (ref "IC37") (pin "1") (pinfunction "I1_1") (pintype "input"))
      (node (ref "IC37") (pin "2") (pinfunction "I2_2") (pintype "input"))
      (node (ref "Q28") (pin "1") (pinfunction "G_1") (pintype "passive"))
    )
    (net (code "494") (name "Net-(IC34A-Q1)") (class "Default")
      (node (ref "IC34") (pin "14") (pinfunction "Q1_14") (pintype "output"))
      (node (ref "IC37") (pin "6") (pinfunction "I6_6") (pintype "input"))
    )
    (net (code "495") (name "Net-(IC34A-Q2)") (class "Default")
      (node (ref "IC34") (pin "2") (pinfunction "Q2_2") (pintype "output"))
      (node (ref "IC37") (pin "7") (pinfunction "I7_7") (pintype "input"))
    )
    (net (code "496") (name "Net-(IC34A-Q3)") (class "Default")
      (node (ref "IC34") (pin "15") (pinfunction "Q3_15") (pintype "output"))
      (node (ref "IC37") (pin "5") (pinfunction "I5_5") (pintype "input"))
    )
    (net (code "497") (name "Net-(IC34A-Q4)") (class "Default")
      (node (ref "IC34") (pin "1") (pinfunction "Q4_1") (pintype "output"))
      (node (ref "IC37") (pin "4") (pinfunction "I4_4") (pintype "input"))
    )
    (net (code "498") (name "Net-(IC34A-Q5)") (class "Default")
      (node (ref "IC34") (pin "6") (pinfunction "Q5_6") (pintype "output"))
      (node (ref "IC37") (pin "3") (pinfunction "I3_3") (pintype "input"))
    )
    (net (code "499") (name "Net-(IC36-ADJ)") (class "Default")
      (node (ref "IC36") (pin "1") (pinfunction "ADJ_1") (pintype "input"))
      (node (ref "R140") (pin "1") (pinfunction "1_1") (pintype "passive"))
      (node (ref "R147") (pin "2") (pinfunction "2_2") (pintype "passive"))
      (node (ref "X10") (pin "7") (pinfunction "7_7") (pintype "passive"))
    )
    (net (code "500") (name "Net-(IC36-VI)") (class "Default")
      (node (ref "IC36") (pin "3") (pinfunction "VI_3") (pintype "input"))
      (node (ref "Q25") (pin "2") (pinfunction "C_2") (pintype "passive"))
    )
    (net (code "501") (name "Net-(IC36-VO)") (class "Default")
      (node (ref "IC36") (pin "2") (pinfunction "VO_2") (pintype "passive"))
      (node (ref "R140") (pin "2") (pinfunction "2_2") (pintype "passive"))
    )
    (net (code "502") (name "Net-(IC37-O2)") (class "Default")
      (node (ref "IC37") (pin "15") (pinfunction "O2_15") (pintype "open_collector"))
      (node (ref "R162") (pin "1") (pinfunction "1_1") (pintype "passive"))
    )
    (net (code "503") (name "Net-(IC38A-+IN)") (class "Default")
      (node (ref "IC38") (pin "5") (pinfunction "+IN_5") (pintype "input"))
      (node (ref "R151") (pin "1") (pinfunction "1_1") (pintype "passive"))
      (node (ref "R152") (pin "2") (pinfunction "2_2") (pintype "passive"))
      (node (ref "R153") (pin "2") (pinfunction "2_2") (pintype "passive"))
    )
    (net (code "504") (name "Net-(IC38A--IN)") (class "Default")
      (node (ref "C32") (pin "1") (pinfunction "1_1") (pintype "passive"))
      (node (ref "IC38") (pin "4") (pinfunction "-IN_4") (pintype "input"))
      (node (ref "R150") (pin "1") (pinfunction "1_1") (pintype "passive"))
    )
    (net (code "505") (name "Net-(IC38B-+IN)") (class "Default")
      (node (ref "IC38") (pin "7") (pinfunction "+IN_7") (pintype "input"))
      (node (ref "R148") (pin "1") (pinfunction "1_1") (pintype "passive"))
      (node (ref "R165") (pin "1") (pinfunction "1_1") (pintype "passive"))
    )
    (net (code "506") (name "Net-(IC38B--IN)") (class "Default")
      (node (ref "IC38") (pin "6") (pinfunction "-IN_6") (pintype "input"))
      (node (ref "IC38") (pin "8") (pinfunction "-IN_8") (pintype "input"))
      (node (ref "R147") (pin "1") (pinfunction "1_1") (pintype "passive"))
    )
    (net (code "507") (name "Net-(IC38B-OUT)") (class "Default")
      (node (ref "IC38") (pin "1") (pinfunction "OUT_1") (pintype "open_collector"))
      (node (ref "R149") (pin "2") (pinfunction "2_2") (pintype "passive"))
      (node (ref "R154") (pin "2") (pinfunction "2_2") (pintype "passive"))
    )
    (net (code "508") (name "Net-(IC38C-+IN)") (class "Default")
      (node (ref "C35") (pin "1") (pinfunction "1_1") (pintype "passive"))
      (node (ref "IC38") (pin "9") (pinfunction "+IN_9") (pintype "input"))
      (node (ref "R156") (pin "2") (pinfunction "2_2") (pintype "passive"))
      (node (ref "R165") (pin "2") (pinfunction "2_2") (pintype "passive"))
    )
    (net (code "509") (name "Net-(IC38C-OUT)") (class "Default")
      (node (ref "C36") (pin "2") (pinfunction "2_2") (pintype "passive"))
      (node (ref "IC38") (pin "14") (pinfunction "OUT_14") (pintype "open_collector"))
      (node (ref "R155") (pin "2") (pinfunction "2_2") (pintype "passive"))
    )
    (net (code "510") (name "Net-(IC40-CV)") (class "Default")
      (node (ref "IC40") (pin "5") (pinfunction "CV_5") (pintype "input"))
      (node (ref "R171") (pin "2") (pinfunction "2_2") (pintype "passive"))
    )
    (net (code "511") (name "Net-(IC40-Q)") (class "Default")
      (node (ref "IC40") (pin "3") (pinfunction "Q_3") (pintype "output"))
      (node (ref "IC41") (pin "12") (pinfunction "A_12") (pintype "input"))
      (node (ref "R171") (pin "1") (pinfunction "1_1") (pintype "passive"))
    )
    (net (code "512") (name "Net-(IC41B-B)") (class "Default")
      (node (ref "IC41") (pin "11") (pinfunction "B_11") (pintype "input"))
      (node (ref "IC41") (pin "9") (pinfunction "~{Q}_9") (pintype "output"))
      (node (ref "R177") (pin "2") (pinfunction "2_2") (pintype "passive"))
    )
    (net (code "513") (name "Net-(IC41B-T2)") (class "Default")
      (node (ref "C39") (pin "1") (pinfunction "1_1") (pintype "passive"))
      (node (ref "IC41") (pin "14") (pinfunction "T2_14") (pintype "input"))
      (node (ref "R175") (pin "1") (pinfunction "1_1") (pintype "passive"))
    )
    (net (code "514") (name "Net-(IC43A-+IN)") (class "Default")
      (node (ref "C34") (pin "1") (pinfunction "1_1") (pintype "passive"))
      (node (ref "IC43") (pin "3") (pinfunction "+IN_3") (pintype "input"))
      (node (ref "R145") (pin "1") (pinfunction "1_1") (pintype "passive"))
    )
    (net (code "515") (name "Net-(IC43A--IN)") (class "Default")
      (node (ref "IC43") (pin "2") (pinfunction "-IN_2") (pintype "input"))
      (node (ref "R146") (pin "2") (pinfunction "2_2") (pintype "passive"))
    )
    (net (code "516") (name "Net-(IC43A-OUT)") (class "Default")
      (node (ref "IC43") (pin "1") (pinfunction "OUT_1") (pintype "output"))
      (node (ref "R178") (pin "2") (pinfunction "2_2") (pintype "passive"))
    )
    (net (code "517") (name "Net-(IC43B-+IN)") (class "Default")
      (node (ref "IC43") (pin "5") (pinfunction "+IN_5") (pintype "input"))
      (node (ref "R179") (pin "2") (pinfunction "2_2") (pintype "passive"))
      (node (ref "R180") (pin "2") (pinfunction "2_2") (pintype "passive"))
    )
    (net (code "518") (name "Net-(IC43B--IN)") (class "Default")
      (node (ref "IC43") (pin "6") (pinfunction "-IN_6") (pintype "input"))
      (node (ref "R181") (pin "1") (pinfunction "1_1") (pintype "passive"))
      (node (ref "R182") (pin "2") (pinfunction "2_2") (pintype "passive"))
    )
    (net (code "519") (name "Net-(IC43B-OUT)") (class "Default")
      (node (ref "IC43") (pin "7") (pinfunction "OUT_7") (pintype "output"))
      (node (ref "R166") (pin "1") (pinfunction "1_1") (pintype "passive"))
      (node (ref "R180") (pin "1") (pinfunction "1_1") (pintype "passive"))
    )
    (net (code "520") (name "Net-(IC45A-A)") (class "Default")
      (node (ref "IC45") (pin "10") (pinfunction "A_10") (pintype "input"))
      (node (ref "IC55") (pin "1") (pinfunction "D1_1") (pintype "passive"))
      (node (ref "R190") (pin "1") (pinfunction "1_1") (pintype "passive"))
      (node (ref "X13") (pin "4") (pinfunction "4_4") (pintype "passive"))
      (node (ref "X14") (pin "2") (pinfunction "S_2") (pintype "passive"))
    )
    (net (code "521") (name "Net-(IC45A-B)") (class "Default")
      (node (ref "IC45") (pin "13") (pinfunction "B_13") (pintype "input"))
      (node (ref "IC55") (pin "4") (pinfunction "D4_4") (pintype "passive"))
      (node (ref "R189") (pin "1") (pinfunction "1_1") (pintype "passive"))
      (node (ref "X13") (pin "3") (pinfunction "3_3") (pintype "passive"))
      (node (ref "X14") (pin "3") (pinfunction "S_3") (pintype "passive"))
    )
    (net (code "522") (name "Net-(IC45A-C)") (class "Default")
      (node (ref "IC45") (pin "12") (pinfunction "C_12") (pintype "input"))
      (node (ref "IC55") (pin "3") (pinfunction "D3_3") (pintype "passive"))
      (node (ref "R188") (pin "1") (pinfunction "1_1") (pintype "passive"))
      (node (ref "X13") (pin "2") (pinfunction "2_2") (pintype "passive"))
      (node (ref "X14") (pin "4") (pinfunction "S_4") (pintype "passive"))
    )
    (net (code "523") (name "Net-(IC45A-Q0)") (class "Default")
      (node (ref "IC45") (pin "3") (pinfunction "Q0_3") (pintype "output"))
      (node (ref "IC48") (pin "1") (pinfunction "I1_1") (pintype "input"))
      (node (ref "IC48") (pin "2") (pinfunction "I2_2") (pintype "input"))
      (node (ref "Q35") (pin "1") (pinfunction "G_1") (pintype "passive"))
    )
    (net (code "524") (name "Net-(IC45A-Q1)") (class "Default")
      (node (ref "IC45") (pin "14") (pinfunction "Q1_14") (pintype "output"))
      (node (ref "IC48") (pin "6") (pinfunction "I6_6") (pintype "input"))
    )
    (net (code "525") (name "Net-(IC45A-Q2)") (class "Default")
      (node (ref "IC45") (pin "2") (pinfunction "Q2_2") (pintype "output"))
      (node (ref "IC48") (pin "7") (pinfunction "I7_7") (pintype "input"))
    )
    (net (code "526") (name "Net-(IC45A-Q3)") (class "Default")
      (node (ref "IC45") (pin "15") (pinfunction "Q3_15") (pintype "output"))
      (node (ref "IC48") (pin "5") (pinfunction "I5_5") (pintype "input"))
    )
    (net (code "527") (name "Net-(IC45A-Q4)") (class "Default")
      (node (ref "IC45") (pin "1") (pinfunction "Q4_1") (pintype "output"))
      (node (ref "IC48") (pin "4") (pinfunction "I4_4") (pintype "input"))
    )
    (net (code "528") (name "Net-(IC45A-Q5)") (class "Default")
      (node (ref "IC45") (pin "6") (pinfunction "Q5_6") (pintype "output"))
      (node (ref "IC48") (pin "3") (pinfunction "I3_3") (pintype "input"))
    )
    (net (code "529") (name "Net-(IC47-ADJ)") (class "Default")
      (node (ref "IC47") (pin "1") (pinfunction "ADJ_1") (pintype "input"))
      (node (ref "R186") (pin "1") (pinfunction "1_1") (pintype "passive"))
      (node (ref "R193") (pin "2") (pinfunction "2_2") (pintype "passive"))
      (node (ref "X13") (pin "7") (pinfunction "7_7") (pintype "passive"))
    )
    (net (code "530") (name "Net-(IC47-VI)") (class "Default")
      (node (ref "IC47") (pin "3") (pinfunction "VI_3") (pintype "input"))
      (node (ref "Q32") (pin "2") (pinfunction "C_2") (pintype "passive"))
    )
    (net (code "531") (name "Net-(IC47-VO)") (class "Default")
      (node (ref "IC47") (pin "2") (pinfunction "VO_2") (pintype "passive"))
      (node (ref "R186") (pin "2") (pinfunction "2_2") (pintype "passive"))
    )
    (net (code "532") (name "Net-(IC48-O2)") (class "Default")
      (node (ref "IC48") (pin "15") (pinfunction "O2_15") (pintype "open_collector"))
      (node (ref "R208") (pin "1") (pinfunction "1_1") (pintype "passive"))
    )
    (net (code "533") (name "Net-(IC49A-+IN)") (class "Default")
      (node (ref "IC49") (pin "5") (pinfunction "+IN_5") (pintype "input"))
      (node (ref "R197") (pin "1") (pinfunction "1_1") (pintype "passive"))
      (node (ref "R198") (pin "2") (pinfunction "2_2") (pintype "passive"))
      (node (ref "R199") (pin "2") (pinfunction "2_2") (pintype "passive"))
    )
    (net (code "534") (name "Net-(IC49A--IN)") (class "Default")
      (node (ref "C42") (pin "1") (pinfunction "1_1") (pintype "passive"))
      (node (ref "IC49") (pin "4") (pinfunction "-IN_4") (pintype "input"))
      (node (ref "R196") (pin "1") (pinfunction "1_1") (pintype "passive"))
    )
    (net (code "535") (name "Net-(IC49B-+IN)") (class "Default")
      (node (ref "IC49") (pin "7") (pinfunction "+IN_7") (pintype "input"))
      (node (ref "R194") (pin "1") (pinfunction "1_1") (pintype "passive"))
      (node (ref "R211") (pin "1") (pinfunction "1_1") (pintype "passive"))
    )
    (net (code "536") (name "Net-(IC49B--IN)") (class "Default")
      (node (ref "IC49") (pin "6") (pinfunction "-IN_6") (pintype "input"))
      (node (ref "IC49") (pin "8") (pinfunction "-IN_8") (pintype "input"))
      (node (ref "R193") (pin "1") (pinfunction "1_1") (pintype "passive"))
    )
    (net (code "537") (name "Net-(IC49B-OUT)") (class "Default")
      (node (ref "IC49") (pin "1") (pinfunction "OUT_1") (pintype "open_collector"))
      (node (ref "R195") (pin "2") (pinfunction "2_2") (pintype "passive"))
      (node (ref "R200") (pin "2") (pinfunction "2_2") (pintype "passive"))
    )
    (net (code "538") (name "Net-(IC49C-+IN)") (class "Default")
      (node (ref "C45") (pin "1") (pinfunction "1_1") (pintype "passive"))
      (node (ref "IC49") (pin "9") (pinfunction "+IN_9") (pintype "input"))
      (node (ref "R202") (pin "2") (pinfunction "2_2") (pintype "passive"))
      (node (ref "R211") (pin "2") (pinfunction "2_2") (pintype "passive"))
    )
    (net (code "539") (name "Net-(IC49C-OUT)") (class "Default")
      (node (ref "C46") (pin "2") (pinfunction "2_2") (pintype "passive"))
      (node (ref "IC49") (pin "14") (pinfunction "OUT_14") (pintype "open_collector"))
      (node (ref "R201") (pin "2") (pinfunction "2_2") (pintype "passive"))
    )
    (net (code "540") (name "Net-(IC51-CV)") (class "Default")
      (node (ref "IC51") (pin "5") (pinfunction "CV_5") (pintype "input"))
      (node (ref "R217") (pin "2") (pinfunction "2_2") (pintype "passive"))
    )
    (net (code "541") (name "Net-(IC51-Q)") (class "Default")
      (node (ref "IC51") (pin "3") (pinfunction "Q_3") (pintype "output"))
      (node (ref "IC52") (pin "12") (pinfunction "A_12") (pintype "input"))
      (node (ref "R217") (pin "1") (pinfunction "1_1") (pintype "passive"))
    )
    (net (code "542") (name "Net-(IC52B-B)") (class "Default")
      (node (ref "IC52") (pin "11") (pinfunction "B_11") (pintype "input"))
      (node (ref "IC52") (pin "9") (pinfunction "~{Q}_9") (pintype "output"))
      (node (ref "R223") (pin "2") (pinfunction "2_2") (pintype "passive"))
    )
    (net (code "543") (name "Net-(IC52B-T2)") (class "Default")
      (node (ref "C49") (pin "1") (pinfunction "1_1") (pintype "passive"))
      (node (ref "IC52") (pin "14") (pinfunction "T2_14") (pintype "input"))
      (node (ref "R221") (pin "1") (pinfunction "1_1") (pintype "passive"))
    )
    (net (code "544") (name "Net-(IC54A-+IN)") (class "Default")
      (node (ref "C44") (pin "1") (pinfunction "1_1") (pintype "passive"))
      (node (ref "IC54") (pin "3") (pinfunction "+IN_3") (pintype "input"))
      (node (ref "R191") (pin "1") (pinfunction "1_1") (pintype "passive"))
    )
    (net (code "545") (name "Net-(IC54A--IN)") (class "Default")
      (node (ref "IC54") (pin "2") (pinfunction "-IN_2") (pintype "input"))
      (node (ref "R192") (pin "2") (pinfunction "2_2") (pintype "passive"))
    )
    (net (code "546") (name "Net-(IC54A-OUT)") (class "Default")
      (node (ref "IC54") (pin "1") (pinfunction "OUT_1") (pintype "output"))
      (node (ref "R224") (pin "2") (pinfunction "2_2") (pintype "passive"))
    )
    (net (code "547") (name "Net-(IC54B-+IN)") (class "Default")
      (node (ref "IC54") (pin "5") (pinfunction "+IN_5") (pintype "input"))
      (node (ref "R225") (pin "2") (pinfunction "2_2") (pintype "passive"))
      (node (ref "R226") (pin "2") (pinfunction "2_2") (pintype "passive"))
    )
    (net (code "548") (name "Net-(IC54B--IN)") (class "Default")
      (node (ref "IC54") (pin "6") (pinfunction "-IN_6") (pintype "input"))
      (node (ref "R227") (pin "1") (pinfunction "1_1") (pintype "passive"))
      (node (ref "R228") (pin "2") (pinfunction "2_2") (pintype "passive"))
    )
    (net (code "549") (name "Net-(IC54B-OUT)") (class "Default")
      (node (ref "IC54") (pin "7") (pinfunction "OUT_7") (pintype "output"))
      (node (ref "R212") (pin "1") (pinfunction "1_1") (pintype "passive"))
      (node (ref "R226") (pin "1") (pinfunction "1_1") (pintype "passive"))
    )
    (net (code "550") (name "Net-(IC56A-A)") (class "Default")
      (node (ref "IC56") (pin "10") (pinfunction "A_10") (pintype "input"))
      (node (ref "IC66") (pin "1") (pinfunction "D1_1") (pintype "passive"))
      (node (ref "R236") (pin "1") (pinfunction "1_1") (pintype "passive"))
      (node (ref "X16") (pin "4") (pinfunction "4_4") (pintype "passive"))
      (node (ref "X17") (pin "2") (pinfunction "S_2") (pintype "passive"))
    )
    (net (code "551") (name "Net-(IC56A-B)") (class "Default")
      (node (ref "IC56") (pin "13") (pinfunction "B_13") (pintype "input"))
      (node (ref "IC66") (pin "4") (pinfunction "D4_4") (pintype "passive"))
      (node (ref "R235") (pin "1") (pinfunction "1_1") (pintype "passive"))
      (node (ref "X16") (pin "3") (pinfunction "3_3") (pintype "passive"))
      (node (ref "X17") (pin "3") (pinfunction "S_3") (pintype "passive"))
    )
    (net (code "552") (name "Net-(IC56A-C)") (class "Default")
      (node (ref "IC56") (pin "12") (pinfunction "C_12") (pintype "input"))
      (node (ref "IC66") (pin "3") (pinfunction "D3_3") (pintype "passive"))
      (node (ref "R234") (pin "1") (pinfunction "1_1") (pintype "passive"))
      (node (ref "X16") (pin "2") (pinfunction "2_2") (pintype "passive"))
      (node (ref "X17") (pin "4") (pinfunction "S_4") (pintype "passive"))
    )
    (net (code "553") (name "Net-(IC56A-Q0)") (class "Default")
      (node (ref "IC56") (pin "3") (pinfunction "Q0_3") (pintype "output"))
      (node (ref "IC59") (pin "1") (pinfunction "I1_1") (pintype "input"))
      (node (ref "IC59") (pin "2") (pinfunction "I2_2") (pintype "input"))
      (node (ref "Q42") (pin "1") (pinfunction "G_1") (pintype "passive"))
    )
    (net (code "554") (name "Net-(IC56A-Q1)") (class "Default")
      (node (ref "IC56") (pin "14") (pinfunction "Q1_14") (pintype "output"))
      (node (ref "IC59") (pin "6") (pinfunction "I6_6") (pintype "input"))
    )
    (net (code "555") (name "Net-(IC56A-Q2)") (class "Default")
      (node (ref "IC56") (pin "2") (pinfunction "Q2_2") (pintype "output"))
      (node (ref "IC59") (pin "7") (pinfunction "I7_7") (pintype "input"))
    )
    (net (code "556") (name "Net-(IC56A-Q3)") (class "Default")
      (node (ref "IC56") (pin "15") (pinfunction "Q3_15") (pintype "output"))
      (node (ref "IC59") (pin "5") (pinfunction "I5_5") (pintype "input"))
    )
    (net (code "557") (name "Net-(IC56A-Q4)") (class "Default")
      (node (ref "IC56") (pin "1") (pinfunction "Q4_1") (pintype "output"))
      (node (ref "IC59") (pin "4") (pinfunction "I4_4") (pintype "input"))
    )
    (net (code "558") (name "Net-(IC56A-Q5)") (class "Default")
      (node (ref "IC56") (pin "6") (pinfunction "Q5_6") (pintype "output"))
      (node (ref "IC59") (pin "3") (pinfunction "I3_3") (pintype "input"))
    )
    (net (code "559") (name "Net-(IC58-ADJ)") (class "Default")
      (node (ref "IC58") (pin "1") (pinfunction "ADJ_1") (pintype "input"))
      (node (ref "R232") (pin "1") (pinfunction "1_1") (pintype "passive"))
      (node (ref "R239") (pin "2") (pinfunction "2_2") (pintype "passive"))
      (node (ref "X16") (pin "7") (pinfunction "7_7") (pintype "passive"))
    )
    (net (code "560") (name "Net-(IC58-VI)") (class "Default")
      (node (ref "IC58") (pin "3") (pinfunction "VI_3") (pintype "input"))
      (node (ref "Q39") (pin "2") (pinfunction "C_2") (pintype "passive"))
    )
    (net (code "561") (name "Net-(IC58-VO)") (class "Default")
      (node (ref "IC58") (pin "2") (pinfunction "VO_2") (pintype "passive"))
      (node (ref "R232") (pin "2") (pinfunction "2_2") (pintype "passive"))
    )
    (net (code "562") (name "Net-(IC59-O2)") (class "Default")
      (node (ref "IC59") (pin "15") (pinfunction "O2_15") (pintype "open_collector"))
      (node (ref "R254") (pin "1") (pinfunction "1_1") (pintype "passive"))
    )
    (net (code "563") (name "Net-(IC60A-+IN)") (class "Default")
      (node (ref "IC60") (pin "5") (pinfunction "+IN_5") (pintype "input"))
      (node (ref "R243") (pin "1") (pinfunction "1_1") (pintype "passive"))
      (node (ref "R244") (pin "2") (pinfunction "2_2") (pintype "passive"))
      (node (ref "R245") (pin "2") (pinfunction "2_2") (pintype "passive"))
    )
    (net (code "564") (name "Net-(IC60A--IN)") (class "Default")
      (node (ref "C52") (pin "1") (pinfunction "1_1") (pintype "passive"))
      (node (ref "IC60") (pin "4") (pinfunction "-IN_4") (pintype "input"))
      (node (ref "R242") (pin "1") (pinfunction "1_1") (pintype "passive"))
    )
    (net (code "565") (name "Net-(IC60B-+IN)") (class "Default")
      (node (ref "IC60") (pin "7") (pinfunction "+IN_7") (pintype "input"))
      (node (ref "R240") (pin "1") (pinfunction "1_1") (pintype "passive"))
      (node (ref "R257") (pin "1") (pinfunction "1_1") (pintype "passive"))
    )
    (net (code "566") (name "Net-(IC60B--IN)") (class "Default")
      (node (ref "IC60") (pin "6") (pinfunction "-IN_6") (pintype "input"))
      (node (ref "IC60") (pin "8") (pinfunction "-IN_8") (pintype "input"))
      (node (ref "R239") (pin "1") (pinfunction "1_1") (pintype "passive"))
    )
    (net (code "567") (name "Net-(IC60B-OUT)") (class "Default")
      (node (ref "IC60") (pin "1") (pinfunction "OUT_1") (pintype "open_collector"))
      (node (ref "R241") (pin "2") (pinfunction "2_2") (pintype "passive"))
      (node (ref "R246") (pin "2") (pinfunction "2_2") (pintype "passive"))
    )
    (net (code "568") (name "Net-(IC60C-+IN)") (class "Default")
      (node (ref "C55") (pin "1") (pinfunction "1_1") (pintype "passive"))
      (node (ref "IC60") (pin "9") (pinfunction "+IN_9") (pintype "input"))
      (node (ref "R248") (pin "2") (pinfunction "2_2") (pintype "passive"))
      (node (ref "R257") (pin "2") (pinfunction "2_2") (pintype "passive"))
    )
    (net (code "569") (name "Net-(IC60C-OUT)") (class "Default")
      (node (ref "C56") (pin "2") (pinfunction "2_2") (pintype "passive"))
      (node (ref "IC60") (pin "14") (pinfunction "OUT_14") (pintype "open_collector"))
      (node (ref "R247") (pin "2") (pinfunction "2_2") (pintype "passive"))
    )
    (net (code "570") (name "Net-(IC62-CV)") (class "Default")
      (node (ref "IC62") (pin "5") (pinfunction "CV_5") (pintype "input"))
      (node (ref "R263") (pin "2") (pinfunction "2_2") (pintype "passive"))
    )
    (net (code "571") (name "Net-(IC62-Q)") (class "Default")
      (node (ref "IC62") (pin "3") (pinfunction "Q_3") (pintype "output"))
      (node (ref "IC63") (pin "12") (pinfunction "A_12") (pintype "input"))
      (node (ref "R263") (pin "1") (pinfunction "1_1") (pintype "passive"))
    )
    (net (code "572") (name "Net-(IC63B-B)") (class "Default")
      (node (ref "IC63") (pin "11") (pinfunction "B_11") (pintype "input"))
      (node (ref "IC63") (pin "9") (pinfunction "~{Q}_9") (pintype "output"))
      (node (ref "R269") (pin "2") (pinfunction "2_2") (pintype "passive"))
    )
    (net (code "573") (name "Net-(IC63B-T2)") (class "Default")
      (node (ref "C59") (pin "1") (pinfunction "1_1") (pintype "passive"))
      (node (ref "IC63") (pin "14") (pinfunction "T2_14") (pintype "input"))
      (node (ref "R267") (pin "1") (pinfunction "1_1") (pintype "passive"))
    )
    (net (code "574") (name "Net-(IC65A-+IN)") (class "Default")
      (node (ref "C54") (pin "1") (pinfunction "1_1") (pintype "passive"))
      (node (ref "IC65") (pin "3") (pinfunction "+IN_3") (pintype "input"))
      (node (ref "R237") (pin "1") (pinfunction "1_1") (pintype "passive"))
    )
    (net (code "575") (name "Net-(IC65A--IN)") (class "Default")
      (node (ref "IC65") (pin "2") (pinfunction "-IN_2") (pintype "input"))
      (node (ref "R238") (pin "2") (pinfunction "2_2") (pintype "passive"))
    )
    (net (code "576") (name "Net-(IC65A-OUT)") (class "Default")
      (node (ref "IC65") (pin "1") (pinfunction "OUT_1") (pintype "output"))
      (node (ref "R270") (pin "2") (pinfunction "2_2") (pintype "passive"))
    )
    (net (code "577") (name "Net-(IC65B-+IN)") (class "Default")
      (node (ref "IC65") (pin "5") (pinfunction "+IN_5") (pintype "input"))
      (node (ref "R271") (pin "2") (pinfunction "2_2") (pintype "passive"))
      (node (ref "R272") (pin "2") (pinfunction "2_2") (pintype "passive"))
    )
    (net (code "578") (name "Net-(IC65B--IN)") (class "Default")
      (node (ref "IC65") (pin "6") (pinfunction "-IN_6") (pintype "input"))
      (node (ref "R273") (pin "1") (pinfunction "1_1") (pintype "passive"))
      (node (ref "R274") (pin "2") (pinfunction "2_2") (pintype "passive"))
    )
    (net (code "579") (name "Net-(IC65B-OUT)") (class "Default")
      (node (ref "IC65") (pin "7") (pinfunction "OUT_7") (pintype "output"))
      (node (ref "R258") (pin "1") (pinfunction "1_1") (pintype "passive"))
      (node (ref "R272") (pin "1") (pinfunction "1_1") (pintype "passive"))
    )
    (net (code "580") (name "Net-(IC67A-A)") (class "Default")
      (node (ref "IC67") (pin "10") (pinfunction "A_10") (pintype "input"))
      (node (ref "IC77") (pin "1") (pinfunction "D1_1") (pintype "passive"))
      (node (ref "R282") (pin "1") (pinfunction "1_1") (pintype "passive"))
      (node (ref "X19") (pin "4") (pinfunction "4_4") (pintype "passive"))
      (node (ref "X20") (pin "2") (pinfunction "S_2") (pintype "passive"))
    )
    (net (code "581") (name "Net-(IC67A-B)") (class "Default")
      (node (ref "IC67") (pin "13") (pinfunction "B_13") (pintype "input"))
      (node (ref "IC77") (pin "4") (pinfunction "D4_4") (pintype "passive"))
      (node (ref "R281") (pin "1") (pinfunction "1_1") (pintype "passive"))
      (node (ref "X19") (pin "3") (pinfunction "3_3") (pintype "passive"))
      (node (ref "X20") (pin "3") (pinfunction "S_3") (pintype "passive"))
    )
    (net (code "582") (name "Net-(IC67A-C)") (class "Default")
      (node (ref "IC67") (pin "12") (pinfunction "C_12") (pintype "input"))
      (node (ref "IC77") (pin "3") (pinfunction "D3_3") (pintype "passive"))
      (node (ref "R280") (pin "1") (pinfunction "1_1") (pintype "passive"))
      (node (ref "X19") (pin "2") (pinfunction "2_2") (pintype "passive"))
      (node (ref "X20") (pin "4") (pinfunction "S_4") (pintype "passive"))
    )
    (net (code "583") (name "Net-(IC67A-Q0)") (class "Default")
      (node (ref "IC67") (pin "3") (pinfunction "Q0_3") (pintype "output"))
      (node (ref "IC70") (pin "1") (pinfunction "I1_1") (pintype "input"))
      (node (ref "IC70") (pin "2") (pinfunction "I2_2") (pintype "input"))
      (node (ref "Q49") (pin "1") (pinfunction "G_1") (pintype "passive"))
    )
    (net (code "584") (name "Net-(IC67A-Q1)") (class "Default")
      (node (ref "IC67") (pin "14") (pinfunction "Q1_14") (pintype "output"))
      (node (ref "IC70") (pin "6") (pinfunction "I6_6") (pintype "input"))
    )
    (net (code "585") (name "Net-(IC67A-Q2)") (class "Default")
      (node (ref "IC67") (pin "2") (pinfunction "Q2_2") (pintype "output"))
      (node (ref "IC70") (pin "7") (pinfunction "I7_7") (pintype "input"))
    )
    (net (code "586") (name "Net-(IC67A-Q3)") (class "Default")
      (node (ref "IC67") (pin "15") (pinfunction "Q3_15") (pintype "output"))
      (node (ref "IC70") (pin "5") (pinfunction "I5_5") (pintype "input"))
    )
    (net (code "587") (name "Net-(IC67A-Q4)") (class "Default")
      (node (ref "IC67") (pin "1") (pinfunction "Q4_1") (pintype "output"))
      (node (ref "IC70") (pin "4") (pinfunction "I4_4") (pintype "input"))
    )
    (net (code "588") (name "Net-(IC67A-Q5)") (class "Default")
      (node (ref "IC67") (pin "6") (pinfunction "Q5_6") (pintype "output"))
      (node (ref "IC70") (pin "3") (pinfunction "I3_3") (pintype "input"))
    )
    (net (code "589") (name "Net-(IC69-ADJ)") (class "Default")
      (node (ref "IC69") (pin "1") (pinfunction "ADJ_1") (pintype "input"))
      (node (ref "R278") (pin "1") (pinfunction "1_1") (pintype "passive"))
      (node (ref "R285") (pin "2") (pinfunction "2_2") (pintype "passive"))
      (node (ref "X19") (pin "7") (pinfunction "7_7") (pintype "passive"))
    )
    (net (code "590") (name "Net-(IC69-VI)") (class "Default")
      (node (ref "IC69") (pin "3") (pinfunction "VI_3") (pintype "input"))
      (node (ref "Q46") (pin "2") (pinfunction "C_2") (pintype "passive"))
    )
    (net (code "591") (name "Net-(IC69-VO)") (class "Default")
      (node (ref "IC69") (pin "2") (pinfunction "VO_2") (pintype "passive"))
      (node (ref "R278") (pin "2") (pinfunction "2_2") (pintype "passive"))
    )
    (net (code "592") (name "Net-(IC70-O2)") (class "Default")
      (node (ref "IC70") (pin "15") (pinfunction "O2_15") (pintype "open_collector"))
      (node (ref "R300") (pin "1") (pinfunction "1_1") (pintype "passive"))
    )
    (net (code "593") (name "Net-(IC71A-+IN)") (class "Default")
      (node (ref "IC71") (pin "5") (pinfunction "+IN_5") (pintype "input"))
      (node (ref "R289") (pin "1") (pinfunction "1_1") (pintype "passive"))
      (node (ref "R290") (pin "2") (pinfunction "2_2") (pintype "passive"))
      (node (ref "R291") (pin "2") (pinfunction "2_2") (pintype "passive"))
    )
    (net (code "594") (name "Net-(IC71A--IN)") (class "Default")
      (node (ref "C62") (pin "1") (pinfunction "1_1") (pintype "passive"))
      (node (ref "IC71") (pin "4") (pinfunction "-IN_4") (pintype "input"))
      (node (ref "R288") (pin "1") (pinfunction "1_1") (pintype "passive"))
    )
    (net (code "595") (name "Net-(IC71B-+IN)") (class "Default")
      (node (ref "IC71") (pin "7") (pinfunction "+IN_7") (pintype "input"))
      (node (ref "R286") (pin "1") (pinfunction "1_1") (pintype "passive"))
      (node (ref "R303") (pin "1") (pinfunction "1_1") (pintype "passive"))
    )
    (net (code "596") (name "Net-(IC71B--IN)") (class "Default")
      (node (ref "IC71") (pin "6") (pinfunction "-IN_6") (pintype "input"))
      (node (ref "IC71") (pin "8") (pinfunction "-IN_8") (pintype "input"))
      (node (ref "R285") (pin "1") (pinfunction "1_1") (pintype "passive"))
    )
    (net (code "597") (name "Net-(IC71B-OUT)") (class "Default")
      (node (ref "IC71") (pin "1") (pinfunction "OUT_1") (pintype "open_collector"))
      (node (ref "R287") (pin "2") (pinfunction "2_2") (pintype "passive"))
      (node (ref "R292") (pin "2") (pinfunction "2_2") (pintype "passive"))
    )
    (net (code "598") (name "Net-(IC71C-+IN)") (class "Default")
      (node (ref "C65") (pin "1") (pinfunction "1_1") (pintype "passive"))
      (node (ref "IC71") (pin "9") (pinfunction "+IN_9") (pintype "input"))
      (node (ref "R294") (pin "2") (pinfunction "2_2") (pintype "passive"))
      (node (ref "R303") (pin "2") (pinfunction "2_2") (pintype "passive"))
    )
    (net (code "599") (name "Net-(IC71C-OUT)") (class "Default")
      (node (ref "C66") (pin "2") (pinfunction "2_2") (pintype "passive"))
      (node (ref "IC71") (pin "14") (pinfunction "OUT_14") (pintype "open_collector"))
      (node (ref "R293") (pin "2") (pinfunction "2_2") (pintype "passive"))
    )
    (net (code "600") (name "Net-(IC73-CV)") (class "Default")
      (node (ref "IC73") (pin "5") (pinfunction "CV_5") (pintype "input"))
      (node (ref "R309") (pin "2") (pinfunction "2_2") (pintype "passive"))
    )
    (net (code "601") (name "Net-(IC73-Q)") (class "Default")
      (node (ref "IC73") (pin "3") (pinfunction "Q_3") (pintype "output"))
      (node (ref "IC74") (pin "12") (pinfunction "A_12") (pintype "input"))
      (node (ref "R309") (pin "1") (pinfunction "1_1") (pintype "passive"))
    )
    (net (code "602") (name "Net-(IC74B-B)") (class "Default")
      (node (ref "IC74") (pin "11") (pinfunction "B_11") (pintype "input"))
      (node (ref "IC74") (pin "9") (pinfunction "~{Q}_9") (pintype "output"))
      (node (ref "R315") (pin "2") (pinfunction "2_2") (pintype "passive"))
    )
    (net (code "603") (name "Net-(IC74B-T2)") (class "Default")
      (node (ref "C69") (pin "1") (pinfunction "1_1") (pintype "passive"))
      (node (ref "IC74") (pin "14") (pinfunction "T2_14") (pintype "input"))
      (node (ref "R313") (pin "1") (pinfunction "1_1") (pintype "passive"))
    )
    (net (code "604") (name "Net-(IC76A-+IN)") (class "Default")
      (node (ref "C64") (pin "1") (pinfunction "1_1") (pintype "passive"))
      (node (ref "IC76") (pin "3") (pinfunction "+IN_3") (pintype "input"))
      (node (ref "R283") (pin "1") (pinfunction "1_1") (pintype "passive"))
    )
    (net (code "605") (name "Net-(IC76A--IN)") (class "Default")
      (node (ref "IC76") (pin "2") (pinfunction "-IN_2") (pintype "input"))
      (node (ref "R284") (pin "2") (pinfunction "2_2") (pintype "passive"))
    )
    (net (code "606") (name "Net-(IC76A-OUT)") (class "Default")
      (node (ref "IC76") (pin "1") (pinfunction "OUT_1") (pintype "output"))
      (node (ref "R316") (pin "2") (pinfunction "2_2") (pintype "passive"))
    )
    (net (code "607") (name "Net-(IC76B-+IN)") (class "Default")
      (node (ref "IC76") (pin "5") (pinfunction "+IN_5") (pintype "input"))
      (node (ref "R317") (pin "2") (pinfunction "2_2") (pintype "passive"))
      (node (ref "R318") (pin "2") (pinfunction "2_2") (pintype "passive"))
    )
    (net (code "608") (name "Net-(IC76B--IN)") (class "Default")
      (node (ref "IC76") (pin "6") (pinfunction "-IN_6") (pintype "input"))
      (node (ref "R319") (pin "1") (pinfunction "1_1") (pintype "passive"))
      (node (ref "R320") (pin "2") (pinfunction "2_2") (pintype "passive"))
    )
    (net (code "609") (name "Net-(IC76B-OUT)") (class "Default")
      (node (ref "IC76") (pin "7") (pinfunction "OUT_7") (pintype "output"))
      (node (ref "R304") (pin "1") (pinfunction "1_1") (pintype "passive"))
      (node (ref "R318") (pin "1") (pinfunction "1_1") (pintype "passive"))
    )
    (net (code "610") (name "Net-(IC78A-A)") (class "Default")
      (node (ref "IC78") (pin "10") (pinfunction "A_10") (pintype "input"))
      (node (ref "IC88") (pin "1") (pinfunction "D1_1") (pintype "passive"))
      (node (ref "R328") (pin "1") (pinfunction "1_1") (pintype "passive"))
      (node (ref "X22") (pin "4") (pinfunction "4_4") (pintype "passive"))
      (node (ref "X23") (pin "2") (pinfunction "S_2") (pintype "passive"))
    )
    (net (code "611") (name "Net-(IC78A-B)") (class "Default")
      (node (ref "IC78") (pin "13") (pinfunction "B_13") (pintype "input"))
      (node (ref "IC88") (pin "4") (pinfunction "D4_4") (pintype "passive"))
      (node (ref "R327") (pin "1") (pinfunction "1_1") (pintype "passive"))
      (node (ref "X22") (pin "3") (pinfunction "3_3") (pintype "passive"))
      (node (ref "X23") (pin "3") (pinfunction "S_3") (pintype "passive"))
    )
    (net (code "612") (name "Net-(IC78A-C)") (class "Default")
      (node (ref "IC78") (pin "12") (pinfunction "C_12") (pintype "input"))
      (node (ref "IC88") (pin "3") (pinfunction "D3_3") (pintype "passive"))
      (node (ref "R326") (pin "1") (pinfunction "1_1") (pintype "passive"))
      (node (ref "X22") (pin "2") (pinfunction "2_2") (pintype "passive"))
      (node (ref "X23") (pin "4") (pinfunction "S_4") (pintype "passive"))
    )
    (net (code "613") (name "Net-(IC78A-Q0)") (class "Default")
      (node (ref "IC78") (pin "3") (pinfunction "Q0_3") (pintype "output"))
      (node (ref "IC81") (pin "1") (pinfunction "I1_1") (pintype "input"))
      (node (ref "IC81") (pin "2") (pinfunction "I2_2") (pintype "input"))
      (node (ref "Q56") (pin "1") (pinfunction "G_1") (pintype "passive"))
    )
    (net (code "614") (name "Net-(IC78A-Q1)") (class "Default")
      (node (ref "IC78") (pin "14") (pinfunction "Q1_14") (pintype "output"))
      (node (ref "IC81") (pin "6") (pinfunction "I6_6") (pintype "input"))
    )
    (net (code "615") (name "Net-(IC78A-Q2)") (class "Default")
      (node (ref "IC78") (pin "2") (pinfunction "Q2_2") (pintype "output"))
      (node (ref "IC81") (pin "7") (pinfunction "I7_7") (pintype "input"))
    )
    (net (code "616") (name "Net-(IC78A-Q3)") (class "Default")
      (node (ref "IC78") (pin "15") (pinfunction "Q3_15") (pintype "output"))
      (node (ref "IC81") (pin "5") (pinfunction "I5_5") (pintype "input"))
    )
    (net (code "617") (name "Net-(IC78A-Q4)") (class "Default")
      (node (ref "IC78") (pin "1") (pinfunction "Q4_1") (pintype "output"))
      (node (ref "IC81") (pin "4") (pinfunction "I4_4") (pintype "input"))
    )
    (net (code "618") (name "Net-(IC78A-Q5)") (class "Default")
      (node (ref "IC78") (pin "6") (pinfunction "Q5_6") (pintype "output"))
      (node (ref "IC81") (pin "3") (pinfunction "I3_3") (pintype "input"))
    )
    (net (code "619") (name "Net-(IC80-ADJ)") (class "Default")
      (node (ref "IC80") (pin "1") (pinfunction "ADJ_1") (pintype "input"))
      (node (ref "R324") (pin "1") (pinfunction "1_1") (pintype "passive"))
      (node (ref "R331") (pin "2") (pinfunction "2_2") (pintype "passive"))
      (node (ref "X22") (pin "7") (pinfunction "7_7") (pintype "passive"))
    )
    (net (code "620") (name "Net-(IC80-VI)") (class "Default")
      (node (ref "IC80") (pin "3") (pinfunction "VI_3") (pintype "input"))
      (node (ref "Q53") (pin "2") (pinfunction "C_2") (pintype "passive"))
    )
    (net (code "621") (name "Net-(IC80-VO)") (class "Default")
      (node (ref "IC80") (pin "2") (pinfunction "VO_2") (pintype "passive"))
      (node (ref "R324") (pin "2") (pinfunction "2_2") (pintype "passive"))
    )
    (net (code "622") (name "Net-(IC81-O2)") (class "Default")
      (node (ref "IC81") (pin "15") (pinfunction "O2_15") (pintype "open_collector"))
      (node (ref "R346") (pin "1") (pinfunction "1_1") (pintype "passive"))
    )
    (net (code "623") (name "Net-(IC82A-+IN)") (class "Default")
      (node (ref "IC82") (pin "5") (pinfunction "+IN_5") (pintype "input"))
      (node (ref "R335") (pin "1") (pinfunction "1_1") (pintype "passive"))
      (node (ref "R336") (pin "2") (pinfunction "2_2") (pintype "passive"))
      (node (ref "R337") (pin "2") (pinfunction "2_2") (pintype "passive"))
    )
    (net (code "624") (name "Net-(IC82A--IN)") (class "Default")
      (node (ref "C72") (pin "1") (pinfunction "1_1") (pintype "passive"))
      (node (ref "IC82") (pin "4") (pinfunction "-IN_4") (pintype "input"))
      (node (ref "R334") (pin "1") (pinfunction "1_1") (pintype "passive"))
    )
    (net (code "625") (name "Net-(IC82B-+IN)") (class "Default")
      (node (ref "IC82") (pin "7") (pinfunction "+IN_7") (pintype "input"))
      (node (ref "R332") (pin "1") (pinfunction "1_1") (pintype "passive"))
      (node (ref "R349") (pin "1") (pinfunction "1_1") (pintype "passive"))
    )
    (net (code "626") (name "Net-(IC82B--IN)") (class "Default")
      (node (ref "IC82") (pin "6") (pinfunction "-IN_6") (pintype "input"))
      (node (ref "IC82") (pin "8") (pinfunction "-IN_8") (pintype "input"))
      (node (ref "R331") (pin "1") (pinfunction "1_1") (pintype "passive"))
    )
    (net (code "627") (name "Net-(IC82B-OUT)") (class "Default")
      (node (ref "IC82") (pin "1") (pinfunction "OUT_1") (pintype "open_collector"))
      (node (ref "R333") (pin "2") (pinfunction "2_2") (pintype "passive"))
      (node (ref "R338") (pin "2") (pinfunction "2_2") (pintype "passive"))
    )
    (net (code "628") (name "Net-(IC82C-+IN)") (class "Default")
      (node (ref "C75") (pin "1") (pinfunction "1_1") (pintype "passive"))
      (node (ref "IC82") (pin "9") (pinfunction "+IN_9") (pintype "input"))
      (node (ref "R340") (pin "2") (pinfunction "2_2") (pintype "passive"))
      (node (ref "R349") (pin "2") (pinfunction "2_2") (pintype "passive"))
    )
    (net (code "629") (name "Net-(IC82C-OUT)") (class "Default")
      (node (ref "C76") (pin "2") (pinfunction "2_2") (pintype "passive"))
      (node (ref "IC82") (pin "14") (pinfunction "OUT_14") (pintype "open_collector"))
      (node (ref "R339") (pin "2") (pinfunction "2_2") (pintype "passive"))
    )
    (net (code "630") (name "Net-(IC84-CV)") (class "Default")
      (node (ref "IC84") (pin "5") (pinfunction "CV_5") (pintype "input"))
      (node (ref "R355") (pin "2") (pinfunction "2_2") (pintype "passive"))
    )
    (net (code "631") (name "Net-(IC84-Q)") (class "Default")
      (node (ref "IC84") (pin "3") (pinfunction "Q_3") (pintype "output"))
      (node (ref "IC85") (pin "12") (pinfunction "A_12") (pintype "input"))
      (node (ref "R355") (pin "1") (pinfunction "1_1") (pintype "passive"))
    )
    (net (code "632") (name "Net-(IC85B-B)") (class "Default")
      (node (ref "IC85") (pin "11") (pinfunction "B_11") (pintype "input"))
      (node (ref "IC85") (pin "9") (pinfunction "~{Q}_9") (pintype "output"))
      (node (ref "R361") (pin "2") (pinfunction "2_2") (pintype "passive"))
    )
    (net (code "633") (name "Net-(IC85B-T2)") (class "Default")
      (node (ref "C79") (pin "1") (pinfunction "1_1") (pintype "passive"))
      (node (ref "IC85") (pin "14") (pinfunction "T2_14") (pintype "input"))
      (node (ref "R359") (pin "1") (pinfunction "1_1") (pintype "passive"))
    )
    (net (code "634") (name "Net-(IC87A-+IN)") (class "Default")
      (node (ref "C74") (pin "1") (pinfunction "1_1") (pintype "passive"))
      (node (ref "IC87") (pin "3") (pinfunction "+IN_3") (pintype "input"))
      (node (ref "R329") (pin "1") (pinfunction "1_1") (pintype "passive"))
    )
    (net (code "635") (name "Net-(IC87A--IN)") (class "Default")
      (node (ref "IC87") (pin "2") (pinfunction "-IN_2") (pintype "input"))
      (node (ref "R330") (pin "2") (pinfunction "2_2") (pintype "passive"))
    )
    (net (code "636") (name "Net-(IC87A-OUT)") (class "Default")
      (node (ref "IC87") (pin "1") (pinfunction "OUT_1") (pintype "output"))
      (node (ref "R362") (pin "2") (pinfunction "2_2") (pintype "passive"))
    )
    (net (code "637") (name "Net-(IC87B-+IN)") (class "Default")
      (node (ref "IC87") (pin "5") (pinfunction "+IN_5") (pintype "input"))
      (node (ref "R363") (pin "2") (pinfunction "2_2") (pintype "passive"))
      (node (ref "R364") (pin "2") (pinfunction "2_2") (pintype "passive"))
    )
    (net (code "638") (name "Net-(IC87B--IN)") (class "Default")
      (node (ref "IC87") (pin "6") (pinfunction "-IN_6") (pintype "input"))
      (node (ref "R365") (pin "1") (pinfunction "1_1") (pintype "passive"))
      (node (ref "R366") (pin "2") (pinfunction "2_2") (pintype "passive"))
    )
    (net (code "639") (name "Net-(IC87B-OUT)") (class "Default")
      (node (ref "IC87") (pin "7") (pinfunction "OUT_7") (pintype "output"))
      (node (ref "R350") (pin "1") (pinfunction "1_1") (pintype "passive"))
      (node (ref "R364") (pin "1") (pinfunction "1_1") (pintype "passive"))
    )
    (net (code "640") (name "Net-(IC89A-A)") (class "Default")
      (node (ref "IC89") (pin "10") (pinfunction "A_10") (pintype "input"))
      (node (ref "IC99") (pin "1") (pinfunction "D1_1") (pintype "passive"))
      (node (ref "R374") (pin "1") (pinfunction "1_1") (pintype "passive"))
      (node (ref "X25") (pin "4") (pinfunction "4_4") (pintype "passive"))
      (node (ref "X26") (pin "2") (pinfunction "S_2") (pintype "passive"))
    )
    (net (code "641") (name "Net-(IC89A-B)") (class "Default")
      (node (ref "IC89") (pin "13") (pinfunction "B_13") (pintype "input"))
      (node (ref "IC99") (pin "4") (pinfunction "D4_4") (pintype "passive"))
      (node (ref "R373") (pin "1") (pinfunction "1_1") (pintype "passive"))
      (node (ref "X25") (pin "3") (pinfunction "3_3") (pintype "passive"))
      (node (ref "X26") (pin "3") (pinfunction "S_3") (pintype "passive"))
    )
    (net (code "642") (name "Net-(IC89A-C)") (class "Default")
      (node (ref "IC89") (pin "12") (pinfunction "C_12") (pintype "input"))
      (node (ref "IC99") (pin "3") (pinfunction "D3_3") (pintype "passive"))
      (node (ref "R372") (pin "1") (pinfunction "1_1") (pintype "passive"))
      (node (ref "X25") (pin "2") (pinfunction "2_2") (pintype "passive"))
      (node (ref "X26") (pin "4") (pinfunction "S_4") (pintype "passive"))
    )
    (net (code "643") (name "Net-(IC89A-Q0)") (class "Default")
      (node (ref "IC89") (pin "3") (pinfunction "Q0_3") (pintype "output"))
      (node (ref "IC92") (pin "1") (pinfunction "I1_1") (pintype "input"))
      (node (ref "IC92") (pin "2") (pinfunction "I2_2") (pintype "input"))
      (node (ref "Q63") (pin "1") (pinfunction "G_1") (pintype "passive"))
    )
    (net (code "644") (name "Net-(IC89A-Q1)") (class "Default")
      (node (ref "IC89") (pin "14") (pinfunction "Q1_14") (pintype "output"))
      (node (ref "IC92") (pin "6") (pinfunction "I6_6") (pintype "input"))
    )
    (net (code "645") (name "Net-(IC89A-Q2)") (class "Default")
      (node (ref "IC89") (pin "2") (pinfunction "Q2_2") (pintype "output"))
      (node (ref "IC92") (pin "7") (pinfunction "I7_7") (pintype "input"))
    )
    (net (code "646") (name "Net-(IC89A-Q3)") (class "Default")
      (node (ref "IC89") (pin "15") (pinfunction "Q3_15") (pintype "output"))
      (node (ref "IC92") (pin "5") (pinfunction "I5_5") (pintype "input"))
    )
    (net (code "647") (name "Net-(IC89A-Q4)") (class "Default")
      (node (ref "IC89") (pin "1") (pinfunction "Q4_1") (pintype "output"))
      (node (ref "IC92") (pin "4") (pinfunction "I4_4") (pintype "input"))
    )
    (net (code "648") (name "Net-(IC89A-Q5)") (class "Default")
      (node (ref "IC89") (pin "6") (pinfunction "Q5_6") (pintype "output"))
      (node (ref "IC92") (pin "3") (pinfunction "I3_3") (pintype "input"))
    )
    (net (code "649") (name "Net-(IC91-ADJ)") (class "Default")
      (node (ref "IC91") (pin "1") (pinfunction "ADJ_1") (pintype "input"))
      (node (ref "R370") (pin "1") (pinfunction "1_1") (pintype "passive"))
      (node (ref "R377") (pin "2") (pinfunction "2_2") (pintype "passive"))
      (node (ref "X25") (pin "7") (pinfunction "7_7") (pintype "passive"))
    )
    (net (code "650") (name "Net-(IC91-VI)") (class "Default")
      (node (ref "IC91") (pin "3") (pinfunction "VI_3") (pintype "input"))
      (node (ref "Q60") (pin "2") (pinfunction "C_2") (pintype "passive"))
    )
    (net (code "651") (name "Net-(IC91-VO)") (class "Default")
      (node (ref "IC91") (pin "2") (pinfunction "VO_2") (pintype "passive"))
      (node (ref "R370") (pin "2") (pinfunction "2_2") (pintype "passive"))
    )
    (net (code "652") (name "Net-(IC92-O2)") (class "Default")
      (node (ref "IC92") (pin "15") (pinfunction "O2_15") (pintype "open_collector"))
      (node (ref "R392") (pin "1") (pinfunction "1_1") (pintype "passive"))
    )
    (net (code "653") (name "Net-(IC93A-+IN)") (class "Default")
      (node (ref "IC93") (pin "5") (pinfunction "+IN_5") (pintype "input"))
      (node (ref "R381") (pin "1") (pinfunction "1_1") (pintype "passive"))
      (node (ref "R382") (pin "2") (pinfunction "2_2") (pintype "passive"))
      (node (ref "R383") (pin "2") (pinfunction "2_2") (pintype "passive"))
    )
    (net (code "654") (name "Net-(IC93A--IN)") (class "Default")
      (node (ref "C82") (pin "1") (pinfunction "1_1") (pintype "passive"))
      (node (ref "IC93") (pin "4") (pinfunction "-IN_4") (pintype "input"))
      (node (ref "R380") (pin "1") (pinfunction "1_1") (pintype "passive"))
    )
    (net (code "655") (name "Net-(IC93B-+IN)") (class "Default")
      (node (ref "IC93") (pin "7") (pinfunction "+IN_7") (pintype "input"))
      (node (ref "R378") (pin "1") (pinfunction "1_1") (pintype "passive"))
      (node (ref "R395") (pin "1") (pinfunction "1_1") (pintype "passive"))
    )
    (net (code "656") (name "Net-(IC93B--IN)") (class "Default")
      (node (ref "IC93") (pin "6") (pinfunction "-IN_6") (pintype "input"))
      (node (ref "IC93") (pin "8") (pinfunction "-IN_8") (pintype "input"))
      (node (ref "R377") (pin "1") (pinfunction "1_1") (pintype "passive"))
    )
    (net (code "657") (name "Net-(IC93B-OUT)") (class "Default")
      (node (ref "IC93") (pin "1") (pinfunction "OUT_1") (pintype "open_collector"))
      (node (ref "R379") (pin "2") (pinfunction "2_2") (pintype "passive"))
      (node (ref "R384") (pin "2") (pinfunction "2_2") (pintype "passive"))
    )
    (net (code "658") (name "Net-(IC93C-+IN)") (class "Default")
      (node (ref "C85") (pin "1") (pinfunction "1_1") (pintype "passive"))
      (node (ref "IC93") (pin "9") (pinfunction "+IN_9") (pintype "input"))
      (node (ref "R386") (pin "2") (pinfunction "2_2") (pintype "passive"))
      (node (ref "R395") (pin "2") (pinfunction "2_2") (pintype "passive"))
    )
    (net (code "659") (name "Net-(IC93C-OUT)") (class "Default")
      (node (ref "C86") (pin "2") (pinfunction "2_2") (pintype "passive"))
      (node (ref "IC93") (pin "14") (pinfunction "OUT_14") (pintype "open_collector"))
      (node (ref "R385") (pin "2") (pinfunction "2_2") (pintype "passive"))
    )
    (net (code "660") (name "Net-(IC95-CV)") (class "Default")
      (node (ref "IC95") (pin "5") (pinfunction "CV_5") (pintype "input"))
      (node (ref "R401") (pin "2") (pinfunction "2_2") (pintype "passive"))
    )
    (net (code "661") (name "Net-(IC95-Q)") (class "Default")
      (node (ref "IC95") (pin "3") (pinfunction "Q_3") (pintype "output"))
      (node (ref "IC96") (pin "12") (pinfunction "A_12") (pintype "input"))
      (node (ref "R401") (pin "1") (pinfunction "1_1") (pintype "passive"))
    )
    (net (code "662") (name "Net-(IC96B-B)") (class "Default")
      (node (ref "IC96") (pin "11") (pinfunction "B_11") (pintype "input"))
      (node (ref "IC96") (pin "9") (pinfunction "~{Q}_9") (pintype "output"))
      (node (ref "R407") (pin "2") (pinfunction "2_2") (pintype "passive"))
    )
    (net (code "663") (name "Net-(IC96B-T2)") (class "Default")
      (node (ref "C89") (pin "1") (pinfunction "1_1") (pintype "passive"))
      (node (ref "IC96") (pin "14") (pinfunction "T2_14") (pintype "input"))
      (node (ref "R405") (pin "1") (pinfunction "1_1") (pintype "passive"))
    )
    (net (code "664") (name "Net-(IC98A-+IN)") (class "Default")
      (node (ref "C84") (pin "1") (pinfunction "1_1") (pintype "passive"))
      (node (ref "IC98") (pin "3") (pinfunction "+IN_3") (pintype "input"))
      (node (ref "R375") (pin "1") (pinfunction "1_1") (pintype "passive"))
    )
    (net (code "665") (name "Net-(IC98A--IN)") (class "Default")
      (node (ref "IC98") (pin "2") (pinfunction "-IN_2") (pintype "input"))
      (node (ref "R376") (pin "2") (pinfunction "2_2") (pintype "passive"))
    )
    (net (code "666") (name "Net-(IC98A-OUT)") (class "Default")
      (node (ref "IC98") (pin "1") (pinfunction "OUT_1") (pintype "output"))
      (node (ref "R408") (pin "2") (pinfunction "2_2") (pintype "passive"))
    )
    (net (code "667") (name "Net-(IC98B-+IN)") (class "Default")
      (node (ref "IC98") (pin "5") (pinfunction "+IN_5") (pintype "input"))
      (node (ref "R409") (pin "2") (pinfunction "2_2") (pintype "passive"))
      (node (ref "R410") (pin "2") (pinfunction "2_2") (pintype "passive"))
    )
    (net (code "668") (name "Net-(IC98B--IN)") (class "Default")
      (node (ref "IC98") (pin "6") (pinfunction "-IN_6") (pintype "input"))
      (node (ref "R411") (pin "1") (pinfunction "1_1") (pintype "passive"))
      (node (ref "R412") (pin "2") (pinfunction "2_2") (pintype "passive"))
    )
    (net (code "669") (name "Net-(IC98B-OUT)") (class "Default")
      (node (ref "IC98") (pin "7") (pinfunction "OUT_7") (pintype "output"))
      (node (ref "R396") (pin "1") (pinfunction "1_1") (pintype "passive"))
      (node (ref "R410") (pin "1") (pinfunction "1_1") (pintype "passive"))
    )
    (net (code "670") (name "Net-(IC100A-A)") (class "Default")
      (node (ref "IC100") (pin "10") (pinfunction "A_10") (pintype "input"))
      (node (ref "IC110") (pin "1") (pinfunction "D1_1") (pintype "passive"))
      (node (ref "R420") (pin "1") (pinfunction "1_1") (pintype "passive"))
      (node (ref "X28") (pin "4") (pinfunction "4_4") (pintype "passive"))
      (node (ref "X29") (pin "2") (pinfunction "S_2") (pintype "passive"))
    )
    (net (code "671") (name "Net-(IC100A-B)") (class "Default")
      (node (ref "IC100") (pin "13") (pinfunction "B_13") (pintype "input"))
      (node (ref "IC110") (pin "4") (pinfunction "D4_4") (pintype "passive"))
      (node (ref "R419") (pin "1") (pinfunction "1_1") (pintype "passive"))
      (node (ref "X28") (pin "3") (pinfunction "3_3") (pintype "passive"))
      (node (ref "X29") (pin "3") (pinfunction "S_3") (pintype "passive"))
    )
    (net (code "672") (name "Net-(IC100A-C)") (class "Default")
      (node (ref "IC100") (pin "12") (pinfunction "C_12") (pintype "input"))
      (node (ref "IC110") (pin "3") (pinfunction "D3_3") (pintype "passive"))
      (node (ref "R418") (pin "1") (pinfunction "1_1") (pintype "passive"))
      (node (ref "X28") (pin "2") (pinfunction "2_2") (pintype "passive"))
      (node (ref "X29") (pin "4") (pinfunction "S_4") (pintype "passive"))
    )
    (net (code "673") (name "Net-(IC100A-Q0)") (class "Default")
      (node (ref "IC100") (pin "3") (pinfunction "Q0_3") (pintype "output"))
      (node (ref "IC103") (pin "1") (pinfunction "I1_1") (pintype "input"))
      (node (ref "IC103") (pin "2") (pinfunction "I2_2") (pintype "input"))
      (node (ref "Q70") (pin "1") (pinfunction "G_1") (pintype "passive"))
    )
    (net (code "674") (name "Net-(IC100A-Q1)") (class "Default")
      (node (ref "IC100") (pin "14") (pinfunction "Q1_14") (pintype "output"))
      (node (ref "IC103") (pin "6") (pinfunction "I6_6") (pintype "input"))
    )
    (net (code "675") (name "Net-(IC100A-Q2)") (class "Default")
      (node (ref "IC100") (pin "2") (pinfunction "Q2_2") (pintype "output"))
      (node (ref "IC103") (pin "7") (pinfunction "I7_7") (pintype "input"))
    )
    (net (code "676") (name "Net-(IC100A-Q3)") (class "Default")
      (node (ref "IC100") (pin "15") (pinfunction "Q3_15") (pintype "output"))
      (node (ref "IC103") (pin "5") (pinfunction "I5_5") (pintype "input"))
    )
    (net (code "677") (name "Net-(IC100A-Q4)") (class "Default")
      (node (ref "IC100") (pin "1") (pinfunction "Q4_1") (pintype "output"))
      (node (ref "IC103") (pin "4") (pinfunction "I4_4") (pintype "input"))
    )
    (net (code "678") (name "Net-(IC100A-Q5)") (class "Default")
      (node (ref "IC100") (pin "6") (pinfunction "Q5_6") (pintype "output"))
      (node (ref "IC103") (pin "3") (pinfunction "I3_3") (pintype "input"))
    )
    (net (code "679") (name "Net-(IC102-ADJ)") (class "Default")
      (node (ref "IC102") (pin "1") (pinfunction "ADJ_1") (pintype "input"))
      (node (ref "R416") (pin "1") (pinfunction "1_1") (pintype "passive"))
      (node (ref "R423") (pin "2") (pinfunction "2_2") (pintype "passive"))
      (node (ref "X28") (pin "7") (pinfunction "7_7") (pintype "passive"))
    )
    (net (code "680") (name "Net-(IC102-VI)") (class "Default")
      (node (ref "IC102") (pin "3") (pinfunction "VI_3") (pintype "input"))
      (node (ref "Q67") (pin "2") (pinfunction "C_2") (pintype "passive"))
    )
    (net (code "681") (name "Net-(IC102-VO)") (class "Default")
      (node (ref "IC102") (pin "2") (pinfunction "VO_2") (pintype "passive"))
      (node (ref "R416") (pin "2") (pinfunction "2_2") (pintype "passive"))
    )
    (net (code "682") (name "Net-(IC103-O2)") (class "Default")
      (node (ref "IC103") (pin "15") (pinfunction "O2_15") (pintype "open_collector"))
      (node (ref "R438") (pin "1") (pinfunction "1_1") (pintype "passive"))
    )
    (net (code "683") (name "Net-(IC104A-+IN)") (class "Default")
      (node (ref "IC104") (pin "5") (pinfunction "+IN_5") (pintype "input"))
      (node (ref "R427") (pin "1") (pinfunction "1_1") (pintype "passive"))
      (node (ref "R428") (pin "2") (pinfunction "2_2") (pintype "passive"))
      (node (ref "R429") (pin "2") (pinfunction "2_2") (pintype "passive"))
    )
    (net (code "684") (name "Net-(IC104A--IN)") (class "Default")
      (node (ref "C92") (pin "1") (pinfunction "1_1") (pintype "passive"))
      (node (ref "IC104") (pin "4") (pinfunction "-IN_4") (pintype "input"))
      (node (ref "R426") (pin "1") (pinfunction "1_1") (pintype "passive"))
    )
    (net (code "685") (name "Net-(IC104B-+IN)") (class "Default")
      (node (ref "IC104") (pin "7") (pinfunction "+IN_7") (pintype "input"))
      (node (ref "R424") (pin "1") (pinfunction "1_1") (pintype "passive"))
      (node (ref "R441") (pin "1") (pinfunction "1_1") (pintype "passive"))
    )
    (net (code "686") (name "Net-(IC104B--IN)") (class "Default")
      (node (ref "IC104") (pin "6") (pinfunction "-IN_6") (pintype "input"))
      (node (ref "IC104") (pin "8") (pinfunction "-IN_8") (pintype "input"))
      (node (ref "R423") (pin "1") (pinfunction "1_1") (pintype "passive"))
    )
    (net (code "687") (name "Net-(IC104B-OUT)") (class "Default")
      (node (ref "IC104") (pin "1") (pinfunction "OUT_1") (pintype "open_collector"))
      (node (ref "R425") (pin "2") (pinfunction "2_2") (pintype "passive"))
      (node (ref "R430") (pin "2") (pinfunction "2_2") (pintype "passive"))
    )
    (net (code "688") (name "Net-(IC104C-+IN)") (class "Default")
      (node (ref "C95") (pin "1") (pinfunction "1_1") (pintype "passive"))
      (node (ref "IC104") (pin "9") (pinfunction "+IN_9") (pintype "input"))
      (node (ref "R432") (pin "2") (pinfunction "2_2") (pintype "passive"))
      (node (ref "R441") (pin "2") (pinfunction "2_2") (pintype "passive"))
    )
    (net (code "689") (name "Net-(IC104C-OUT)") (class "Default")
      (node (ref "C96") (pin "2") (pinfunction "2_2") (pintype "passive"))
      (node (ref "IC104") (pin "14") (pinfunction "OUT_14") (pintype "open_collector"))
      (node (ref "R431") (pin "2") (pinfunction "2_2") (pintype "passive"))
    )
    (net (code "690") (name "Net-(IC106-CV)") (class "Default")
      (node (ref "IC106") (pin "5") (pinfunction "CV_5") (pintype "input"))
      (node (ref "R447") (pin "2") (pinfunction "2_2") (pintype "passive"))
    )
    (net (code "691") (name "Net-(IC106-Q)") (class "Default")
      (node (ref "IC106") (pin "3") (pinfunction "Q_3") (pintype "output"))
      (node (ref "IC107") (pin "12") (pinfunction "A_12") (pintype "input"))
      (node (ref "R447") (pin "1") (pinfunction "1_1") (pintype "passive"))
    )
    (net (code "692") (name "Net-(IC107B-B)") (class "Default")
      (node (ref "IC107") (pin "11") (pinfunction "B_11") (pintype "input"))
      (node (ref "IC107") (pin "9") (pinfunction "~{Q}_9") (pintype "output"))
      (node (ref "R453") (pin "2") (pinfunction "2_2") (pintype "passive"))
    )
    (net (code "693") (name "Net-(IC107B-T2)") (class "Default")
      (node (ref "C99") (pin "1") (pinfunction "1_1") (pintype "passive"))
      (node (ref "IC107") (pin "14") (pinfunction "T2_14") (pintype "input"))
      (node (ref "R451") (pin "1") (pinfunction "1_1") (pintype "passive"))
    )
    (net (code "694") (name "Net-(IC109A-+IN)") (class "Default")
      (node (ref "C94") (pin "1") (pinfunction "1_1") (pintype "passive"))
      (node (ref "IC109") (pin "3") (pinfunction "+IN_3") (pintype "input"))
      (node (ref "R421") (pin "1") (pinfunction "1_1") (pintype "passive"))
    )
    (net (code "695") (name "Net-(IC109A--IN)") (class "Default")
      (node (ref "IC109") (pin "2") (pinfunction "-IN_2") (pintype "input"))
      (node (ref "R422") (pin "2") (pinfunction "2_2") (pintype "passive"))
    )
    (net (code "696") (name "Net-(IC109A-OUT)") (class "Default")
      (node (ref "IC109") (pin "1") (pinfunction "OUT_1") (pintype "output"))
      (node (ref "R454") (pin "2") (pinfunction "2_2") (pintype "passive"))
    )
    (net (code "697") (name "Net-(IC109B-+IN)") (class "Default")
      (node (ref "IC109") (pin "5") (pinfunction "+IN_5") (pintype "input"))
      (node (ref "R455") (pin "2") (pinfunction "2_2") (pintype "passive"))
      (node (ref "R456") (pin "2") (pinfunction "2_2") (pintype "passive"))
    )
    (net (code "698") (name "Net-(IC109B--IN)") (class "Default")
      (node (ref "IC109") (pin "6") (pinfunction "-IN_6") (pintype "input"))
      (node (ref "R457") (pin "1") (pinfunction "1_1") (pintype "passive"))
      (node (ref "R458") (pin "2") (pinfunction "2_2") (pintype "passive"))
    )
    (net (code "699") (name "Net-(IC109B-OUT)") (class "Default")
      (node (ref "IC109") (pin "7") (pinfunction "OUT_7") (pintype "output"))
      (node (ref "R442") (pin "1") (pinfunction "1_1") (pintype "passive"))
      (node (ref "R456") (pin "1") (pinfunction "1_1") (pintype "passive"))
    )
    (net (code "700") (name "Net-(IC111A-A)") (class "Default")
      (node (ref "IC111") (pin "10") (pinfunction "A_10") (pintype "input"))
      (node (ref "IC121") (pin "1") (pinfunction "D1_1") (pintype "passive"))
      (node (ref "R466") (pin "1") (pinfunction "1_1") (pintype "passive"))
      (node (ref "X31") (pin "4") (pinfunction "4_4") (pintype "passive"))
      (node (ref "X32") (pin "2") (pinfunction "S_2") (pintype "passive"))
    )
    (net (code "701") (name "Net-(IC111A-B)") (class "Default")
      (node (ref "IC111") (pin "13") (pinfunction "B_13") (pintype "input"))
      (node (ref "IC121") (pin "4") (pinfunction "D4_4") (pintype "passive"))
      (node (ref "R465") (pin "1") (pinfunction "1_1") (pintype "passive"))
      (node (ref "X31") (pin "3") (pinfunction "3_3") (pintype "passive"))
      (node (ref "X32") (pin "3") (pinfunction "S_3") (pintype "passive"))
    )
    (net (code "702") (name "Net-(IC111A-C)") (class "Default")
      (node (ref "IC111") (pin "12") (pinfunction "C_12") (pintype "input"))
      (node (ref "IC121") (pin "3") (pinfunction "D3_3") (pintype "passive"))
      (node (ref "R464") (pin "1") (pinfunction "1_1") (pintype "passive"))
      (node (ref "X31") (pin "2") (pinfunction "2_2") (pintype "passive"))
      (node (ref "X32") (pin "4") (pinfunction "S_4") (pintype "passive"))
    )
    (net (code "703") (name "Net-(IC111A-Q0)") (class "Default")
      (node (ref "IC111") (pin "3") (pinfunction "Q0_3") (pintype "output"))
      (node (ref "IC114") (pin "1") (pinfunction "I1_1") (pintype "input"))
      (node (ref "IC114") (pin "2") (pinfunction "I2_2") (pintype "input"))
      (node (ref "Q77") (pin "1") (pinfunction "G_1") (pintype "passive"))
    )
    (net (code "704") (name "Net-(IC111A-Q1)") (class "Default")
      (node (ref "IC111") (pin "14") (pinfunction "Q1_14") (pintype "output"))
      (node (ref "IC114") (pin "6") (pinfunction "I6_6") (pintype "input"))
    )
    (net (code "705") (name "Net-(IC111A-Q2)") (class "Default")
      (node (ref "IC111") (pin "2") (pinfunction "Q2_2") (pintype "output"))
      (node (ref "IC114") (pin "7") (pinfunction "I7_7") (pintype "input"))
    )
    (net (code "706") (name "Net-(IC111A-Q3)") (class "Default")
      (node (ref "IC111") (pin "15") (pinfunction "Q3_15") (pintype "output"))
      (node (ref "IC114") (pin "5") (pinfunction "I5_5") (pintype "input"))
    )
    (net (code "707") (name "Net-(IC111A-Q4)") (class "Default")
      (node (ref "IC111") (pin "1") (pinfunction "Q4_1") (pintype "output"))
      (node (ref "IC114") (pin "4") (pinfunction "I4_4") (pintype "input"))
    )
    (net (code "708") (name "Net-(IC111A-Q5)") (class "Default")
      (node (ref "IC111") (pin "6") (pinfunction "Q5_6") (pintype "output"))
      (node (ref "IC114") (pin "3") (pinfunction "I3_3") (pintype "input"))
    )
    (net (code "709") (name "Net-(IC113-ADJ)") (class "Default")
      (node (ref "IC113") (pin "1") (pinfunction "ADJ_1") (pintype "input"))
      (node (ref "R462") (pin "1") (pinfunction "1_1") (pintype "passive"))
      (node (ref "R469") (pin "2") (pinfunction "2_2") (pintype "passive"))
      (node (ref "X31") (pin "7") (pinfunction "7_7") (pintype "passive"))
    )
    (net (code "710") (name "Net-(IC113-VI)") (class "Default")
      (node (ref "IC113") (pin "3") (pinfunction "VI_3") (pintype "input"))
      (node (ref "Q74") (pin "2") (pinfunction "C_2") (pintype "passive"))
    )
    (net (code "711") (name "Net-(IC113-VO)") (class "Default")
      (node (ref "IC113") (pin "2") (pinfunction "VO_2") (pintype "passive"))
      (node (ref "R462") (pin "2") (pinfunction "2_2") (pintype "passive"))
    )
    (net (code "712") (name "Net-(IC114-O2)") (class "Default")
      (node (ref "IC114") (pin "15") (pinfunction "O2_15") (pintype "open_collector"))
      (node (ref "R484") (pin "1") (pinfunction "1_1") (pintype "passive"))
    )
    (net (code "713") (name "Net-(IC115A-+IN)") (class "Default")
      (node (ref "IC115") (pin "5") (pinfunction "+IN_5") (pintype "input"))
      (node (ref "R473") (pin "1") (pinfunction "1_1") (pintype "passive"))
      (node (ref "R474") (pin "2") (pinfunction "2_2") (pintype "passive"))
      (node (ref "R475") (pin "2") (pinfunction "2_2") (pintype "passive"))
    )
    (net (code "714") (name "Net-(IC115A--IN)") (class "Default")
      (node (ref "C102") (pin "1") (pinfunction "1_1") (pintype "passive"))
      (node (ref "IC115") (pin "4") (pinfunction "-IN_4") (pintype "input"))
      (node (ref "R472") (pin "1") (pinfunction "1_1") (pintype "passive"))
    )
    (net (code "715") (name "Net-(IC115B-+IN)") (class "Default")
      (node (ref "IC115") (pin "7") (pinfunction "+IN_7") (pintype "input"))
      (node (ref "R470") (pin "1") (pinfunction "1_1") (pintype "passive"))
      (node (ref "R487") (pin "1") (pinfunction "1_1") (pintype "passive"))
    )
    (net (code "716") (name "Net-(IC115B--IN)") (class "Default")
      (node (ref "IC115") (pin "6") (pinfunction "-IN_6") (pintype "input"))
      (node (ref "IC115") (pin "8") (pinfunction "-IN_8") (pintype "input"))
      (node (ref "R469") (pin "1") (pinfunction "1_1") (pintype "passive"))
    )
    (net (code "717") (name "Net-(IC115B-OUT)") (class "Default")
      (node (ref "IC115") (pin "1") (pinfunction "OUT_1") (pintype "open_collector"))
      (node (ref "R471") (pin "2") (pinfunction "2_2") (pintype "passive"))
      (node (ref "R476") (pin "2") (pinfunction "2_2") (pintype "passive"))
    )
    (net (code "718") (name "Net-(IC115C-+IN)") (class "Default")
      (node (ref "C105") (pin "1") (pinfunction "1_1") (pintype "passive"))
      (node (ref "IC115") (pin "9") (pinfunction "+IN_9") (pintype "input"))
      (node (ref "R478") (pin "2") (pinfunction "2_2") (pintype "passive"))
      (node (ref "R487") (pin "2") (pinfunction "2_2") (pintype "passive"))
    )
    (net (code "719") (name "Net-(IC115C-OUT)") (class "Default")
      (node (ref "C106") (pin "2") (pinfunction "2_2") (pintype "passive"))
      (node (ref "IC115") (pin "14") (pinfunction "OUT_14") (pintype "open_collector"))
      (node (ref "R477") (pin "2") (pinfunction "2_2") (pintype "passive"))
    )
    (net (code "720") (name "Net-(IC117-CV)") (class "Default")
      (node (ref "IC117") (pin "5") (pinfunction "CV_5") (pintype "input"))
      (node (ref "R493") (pin "2") (pinfunction "2_2") (pintype "passive"))
    )
    (net (code "721") (name "Net-(IC117-Q)") (class "Default")
      (node (ref "IC117") (pin "3") (pinfunction "Q_3") (pintype "output"))
      (node (ref "IC118") (pin "12") (pinfunction "A_12") (pintype "input"))
      (node (ref "R493") (pin "1") (pinfunction "1_1") (pintype "passive"))
    )
    (net (code "722") (name "Net-(IC118B-B)") (class "Default")
      (node (ref "IC118") (pin "11") (pinfunction "B_11") (pintype "input"))
      (node (ref "IC118") (pin "9") (pinfunction "~{Q}_9") (pintype "output"))
      (node (ref "R499") (pin "2") (pinfunction "2_2") (pintype "passive"))
    )
    (net (code "723") (name "Net-(IC118B-T2)") (class "Default")
      (node (ref "C109") (pin "1") (pinfunction "1_1") (pintype "passive"))
      (node (ref "IC118") (pin "14") (pinfunction "T2_14") (pintype "input"))
      (node (ref "R497") (pin "1") (pinfunction "1_1") (pintype "passive"))
    )
    (net (code "724") (name "Net-(IC120A-+IN)") (class "Default")
      (node (ref "C104") (pin "1") (pinfunction "1_1") (pintype "passive"))
      (node (ref "IC120") (pin "3") (pinfunction "+IN_3") (pintype "input"))
      (node (ref "R467") (pin "1") (pinfunction "1_1") (pintype "passive"))
    )
    (net (code "725") (name "Net-(IC120A--IN)") (class "Default")
      (node (ref "IC120") (pin "2") (pinfunction "-IN_2") (pintype "input"))
      (node (ref "R468") (pin "2") (pinfunction "2_2") (pintype "passive"))
    )
    (net (code "726") (name "Net-(IC120A-OUT)") (class "Default")
      (node (ref "IC120") (pin "1") (pinfunction "OUT_1") (pintype "output"))
      (node (ref "R500") (pin "2") (pinfunction "2_2") (pintype "passive"))
    )
    (net (code "727") (name "Net-(IC120B-+IN)") (class "Default")
      (node (ref "IC120") (pin "5") (pinfunction "+IN_5") (pintype "input"))
      (node (ref "R501") (pin "2") (pinfunction "2_2") (pintype "passive"))
      (node (ref "R502") (pin "2") (pinfunction "2_2") (pintype "passive"))
    )
    (net (code "728") (name "Net-(IC120B--IN)") (class "Default")
      (node (ref "IC120") (pin "6") (pinfunction "-IN_6") (pintype "input"))
      (node (ref "R503") (pin "1") (pinfunction "1_1") (pintype "passive"))
      (node (ref "R504") (pin "2") (pinfunction "2_2") (pintype "passive"))
    )
    (net (code "729") (name "Net-(IC120B-OUT)") (class "Default")
      (node (ref "IC120") (pin "7") (pinfunction "OUT_7") (pintype "output"))
      (node (ref "R488") (pin "1") (pinfunction "1_1") (pintype "passive"))
      (node (ref "R502") (pin "1") (pinfunction "1_1") (pintype "passive"))
    )
    (net (code "730") (name "Net-(IC122A-A)") (class "Default")
      (node (ref "IC122") (pin "10") (pinfunction "A_10") (pintype "input"))
      (node (ref "IC132") (pin "1") (pinfunction "D1_1") (pintype "passive"))
      (node (ref "R512") (pin "1") (pinfunction "1_1") (pintype "passive"))
      (node (ref "X34") (pin "4") (pinfunction "4_4") (pintype "passive"))
      (node (ref "X35") (pin "2") (pinfunction "S_2") (pintype "passive"))
    )
    (net (code "731") (name "Net-(IC122A-B)") (class "Default")
      (node (ref "IC122") (pin "13") (pinfunction "B_13") (pintype "input"))
      (node (ref "IC132") (pin "4") (pinfunction "D4_4") (pintype "passive"))
      (node (ref "R511") (pin "1") (pinfunction "1_1") (pintype "passive"))
      (node (ref "X34") (pin "3") (pinfunction "3_3") (pintype "passive"))
      (node (ref "X35") (pin "3") (pinfunction "S_3") (pintype "passive"))
    )
    (net (code "732") (name "Net-(IC122A-C)") (class "Default")
      (node (ref "IC122") (pin "12") (pinfunction "C_12") (pintype "input"))
      (node (ref "IC132") (pin "3") (pinfunction "D3_3") (pintype "passive"))
      (node (ref "R510") (pin "1") (pinfunction "1_1") (pintype "passive"))
      (node (ref "X34") (pin "2") (pinfunction "2_2") (pintype "passive"))
      (node (ref "X35") (pin "4") (pinfunction "S_4") (pintype "passive"))
    )
    (net (code "733") (name "Net-(IC122A-Q0)") (class "Default")
      (node (ref "IC122") (pin "3") (pinfunction "Q0_3") (pintype "output"))
      (node (ref "IC125") (pin "1") (pinfunction "I1_1") (pintype "input"))
      (node (ref "IC125") (pin "2") (pinfunction "I2_2") (pintype "input"))
      (node (ref "Q84") (pin "1") (pinfunction "G_1") (pintype "passive"))
    )
    (net (code "734") (name "Net-(IC122A-Q1)") (class "Default")
      (node (ref "IC122") (pin "14") (pinfunction "Q1_14") (pintype "output"))
      (node (ref "IC125") (pin "6") (pinfunction "I6_6") (pintype "input"))
    )
    (net (code "735") (name "Net-(IC122A-Q2)") (class "Default")
      (node (ref "IC122") (pin "2") (pinfunction "Q2_2") (pintype "output"))
      (node (ref "IC125") (pin "7") (pinfunction "I7_7") (pintype "input"))
    )
    (net (code "736") (name "Net-(IC122A-Q3)") (class "Default")
      (node (ref "IC122") (pin "15") (pinfunction "Q3_15") (pintype "output"))
      (node (ref "IC125") (pin "5") (pinfunction "I5_5") (pintype "input"))
    )
    (net (code "737") (name "Net-(IC122A-Q4)") (class "Default")
      (node (ref "IC122") (pin "1") (pinfunction "Q4_1") (pintype "output"))
      (node (ref "IC125") (pin "4") (pinfunction "I4_4") (pintype "input"))
    )
    (net (code "738") (name "Net-(IC122A-Q5)") (class "Default")
      (node (ref "IC122") (pin "6") (pinfunction "Q5_6") (pintype "output"))
      (node (ref "IC125") (pin "3") (pinfunction "I3_3") (pintype "input"))
    )
    (net (code "739") (name "Net-(IC124-ADJ)") (class "Default")
      (node (ref "IC124") (pin "1") (pinfunction "ADJ_1") (pintype "input"))
      (node (ref "R508") (pin "1") (pinfunction "1_1") (pintype "passive"))
      (node (ref "R515") (pin "2") (pinfunction "2_2") (pintype "passive"))
      (node (ref "X34") (pin "7") (pinfunction "7_7") (pintype "passive"))
    )
    (net (code "740") (name "Net-(IC124-VI)") (class "Default")
      (node (ref "IC124") (pin "3") (pinfunction "VI_3") (pintype "input"))
      (node (ref "Q81") (pin "2") (pinfunction "C_2") (pintype "passive"))
    )
    (net (code "741") (name "Net-(IC124-VO)") (class "Default")
      (node (ref "IC124") (pin "2") (pinfunction "VO_2") (pintype "passive"))
      (node (ref "R508") (pin "2") (pinfunction "2_2") (pintype "passive"))
    )
    (net (code "742") (name "Net-(IC125-O2)") (class "Default")
      (node (ref "IC125") (pin "15") (pinfunction "O2_15") (pintype "open_collector"))
      (node (ref "R530") (pin "1") (pinfunction "1_1") (pintype "passive"))
    )
    (net (code "743") (name "Net-(IC126A-+IN)") (class "Default")
      (node (ref "IC126") (pin "5") (pinfunction "+IN_5") (pintype "input"))
      (node (ref "R519") (pin "1") (pinfunction "1_1") (pintype "passive"))
      (node (ref "R520") (pin "2") (pinfunction "2_2") (pintype "passive"))
      (node (ref "R521") (pin "2") (pinfunction "2_2") (pintype "passive"))
    )
    (net (code "744") (name "Net-(IC126A--IN)") (class "Default")
      (node (ref "C112") (pin "1") (pinfunction "1_1") (pintype "passive"))
      (node (ref "IC126") (pin "4") (pinfunction "-IN_4") (pintype "input"))
      (node (ref "R518") (pin "1") (pinfunction "1_1") (pintype "passive"))
    )
    (net (code "745") (name "Net-(IC126B-+IN)") (class "Default")
      (node (ref "IC126") (pin "7") (pinfunction "+IN_7") (pintype "input"))
      (node (ref "R516") (pin "1") (pinfunction "1_1") (pintype "passive"))
      (node (ref "R533") (pin "1") (pinfunction "1_1") (pintype "passive"))
    )
    (net (code "746") (name "Net-(IC126B--IN)") (class "Default")
      (node (ref "IC126") (pin "6") (pinfunction "-IN_6") (pintype "input"))
      (node (ref "IC126") (pin "8") (pinfunction "-IN_8") (pintype "input"))
      (node (ref "R515") (pin "1") (pinfunction "1_1") (pintype "passive"))
    )
    (net (code "747") (name "Net-(IC126B-OUT)") (class "Default")
      (node (ref "IC126") (pin "1") (pinfunction "OUT_1") (pintype "open_collector"))
      (node (ref "R517") (pin "2") (pinfunction "2_2") (pintype "passive"))
      (node (ref "R522") (pin "2") (pinfunction "2_2") (pintype "passive"))
    )
    (net (code "748") (name "Net-(IC126C-+IN)") (class "Default")
      (node (ref "C115") (pin "1") (pinfunction "1_1") (pintype "passive"))
      (node (ref "IC126") (pin "9") (pinfunction "+IN_9") (pintype "input"))
      (node (ref "R524") (pin "2") (pinfunction "2_2") (pintype "passive"))
      (node (ref "R533") (pin "2") (pinfunction "2_2") (pintype "passive"))
    )
    (net (code "749") (name "Net-(IC126C-OUT)") (class "Default")
      (node (ref "C116") (pin "2") (pinfunction "2_2") (pintype "passive"))
      (node (ref "IC126") (pin "14") (pinfunction "OUT_14") (pintype "open_collector"))
      (node (ref "R523") (pin "2") (pinfunction "2_2") (pintype "passive"))
    )
    (net (code "750") (name "Net-(IC128-CV)") (class "Default")
      (node (ref "IC128") (pin "5") (pinfunction "CV_5") (pintype "input"))
      (node (ref "R539") (pin "2") (pinfunction "2_2") (pintype "passive"))
    )
    (net (code "751") (name "Net-(IC128-Q)") (class "Default")
      (node (ref "IC128") (pin "3") (pinfunction "Q_3") (pintype "output"))
      (node (ref "IC129") (pin "12") (pinfunction "A_12") (pintype "input"))
      (node (ref "R539") (pin "1") (pinfunction "1_1") (pintype "passive"))
    )
    (net (code "752") (name "Net-(IC129B-B)") (class "Default")
      (node (ref "IC129") (pin "11") (pinfunction "B_11") (pintype "input"))
      (node (ref "IC129") (pin "9") (pinfunction "~{Q}_9") (pintype "output"))
      (node (ref "R545") (pin "2") (pinfunction "2_2") (pintype "passive"))
    )
    (net (code "753") (name "Net-(IC129B-T2)") (class "Default")
      (node (ref "C119") (pin "1") (pinfunction "1_1") (pintype "passive"))
      (node (ref "IC129") (pin "14") (pinfunction "T2_14") (pintype "input"))
      (node (ref "R543") (pin "1") (pinfunction "1_1") (pintype "passive"))
    )
    (net (code "754") (name "Net-(IC131A-+IN)") (class "Default")
      (node (ref "C114") (pin "1") (pinfunction "1_1") (pintype "passive"))
      (node (ref "IC131") (pin "3") (pinfunction "+IN_3") (pintype "input"))
      (node (ref "R513") (pin "1") (pinfunction "1_1") (pintype "passive"))
    )
    (net (code "755") (name "Net-(IC131A--IN)") (class "Default")
      (node (ref "IC131") (pin "2") (pinfunction "-IN_2") (pintype "input"))
      (node (ref "R514") (pin "2") (pinfunction "2_2") (pintype "passive"))
    )
    (net (code "756") (name "Net-(IC131A-OUT)") (class "Default")
      (node (ref "IC131") (pin "1") (pinfunction "OUT_1") (pintype "output"))
      (node (ref "R546") (pin "2") (pinfunction "2_2") (pintype "passive"))
    )
    (net (code "757") (name "Net-(IC131B-+IN)") (class "Default")
      (node (ref "IC131") (pin "5") (pinfunction "+IN_5") (pintype "input"))
      (node (ref "R547") (pin "2") (pinfunction "2_2") (pintype "passive"))
      (node (ref "R548") (pin "2") (pinfunction "2_2") (pintype "passive"))
    )
    (net (code "758") (name "Net-(IC131B--IN)") (class "Default")
      (node (ref "IC131") (pin "6") (pinfunction "-IN_6") (pintype "input"))
      (node (ref "R549") (pin "1") (pinfunction "1_1") (pintype "passive"))
      (node (ref "R550") (pin "2") (pinfunction "2_2") (pintype "passive"))
    )
    (net (code "759") (name "Net-(IC131B-OUT)") (class "Default")
      (node (ref "IC131") (pin "7") (pinfunction "OUT_7") (pintype "output"))
      (node (ref "R534") (pin "1") (pinfunction "1_1") (pintype "passive"))
      (node (ref "R548") (pin "1") (pinfunction "1_1") (pintype "passive"))
    )
    (net (code "760") (name "Net-(JP1-Pad1)") (class "Default")
      (node (ref "JP1") (pin "1") (pinfunction "1_1") (pintype "passive"))
      (node (ref "R19") (pin "2") (pinfunction "2_2") (pintype "passive"))
    )
    (net (code "761") (name "Net-(JP4-Pad2)") (class "Default")
      (node (ref "JP4") (pin "2") (pinfunction "2_2") (pintype "passive"))
      (node (ref "R36") (pin "2") (pinfunction "2_2") (pintype "passive"))
      (node (ref "R37") (pin "2") (pinfunction "2_2") (pintype "passive"))
      (node (ref "SJ1") (pin "2") (pinfunction "2_2") (pintype "passive"))
    )
    (net (code "762") (name "Net-(JP5-Pad3)") (class "Default")
      (node (ref "JP5") (pin "3") (pinfunction "3_3") (pintype "passive"))
      (node (ref "R38") (pin "1") (pinfunction "1_1") (pintype "passive"))
      (node (ref "R39") (pin "1") (pinfunction "1_1") (pintype "passive"))
    )
    (net (code "763") (name "Net-(JP6-Pad1)") (class "Default")
      (node (ref "JP6") (pin "1") (pinfunction "1_1") (pintype "passive"))
      (node (ref "R84") (pin "2") (pinfunction "2_2") (pintype "passive"))
    )
    (net (code "764") (name "Net-(JP7-Pad3)") (class "Default")
      (node (ref "JP7") (pin "3") (pinfunction "3_3") (pintype "passive"))
      (node (ref "R75") (pin "1") (pinfunction "1_1") (pintype "passive"))
      (node (ref "R76") (pin "1") (pinfunction "1_1") (pintype "passive"))
    )
    (net (code "765") (name "Net-(JP10-Pad2)") (class "Default")
      (node (ref "JP10") (pin "2") (pinfunction "2_2") (pintype "passive"))
      (node (ref "R81") (pin "2") (pinfunction "2_2") (pintype "passive"))
      (node (ref "R82") (pin "2") (pinfunction "2_2") (pintype "passive"))
      (node (ref "SJ2") (pin "2") (pinfunction "2_2") (pintype "passive"))
    )
    (net (code "766") (name "Net-(JP11-Pad1)") (class "Default")
      (node (ref "JP11") (pin "1") (pinfunction "1_1") (pintype "passive"))
      (node (ref "R130") (pin "2") (pinfunction "2_2") (pintype "passive"))
    )
    (net (code "767") (name "Net-(JP12-Pad3)") (class "Default")
      (node (ref "JP12") (pin "3") (pinfunction "3_3") (pintype "passive"))
      (node (ref "R121") (pin "1") (pinfunction "1_1") (pintype "passive"))
      (node (ref "R122") (pin "1") (pinfunction "1_1") (pintype "passive"))
    )
    (net (code "768") (name "Net-(JP15-Pad2)") (class "Default")
      (node (ref "JP15") (pin "2") (pinfunction "2_2") (pintype "passive"))
      (node (ref "R127") (pin "2") (pinfunction "2_2") (pintype "passive"))
      (node (ref "R128") (pin "2") (pinfunction "2_2") (pintype "passive"))
      (node (ref "SJ3") (pin "2") (pinfunction "2_2") (pintype "passive"))
    )
    (net (code "769") (name "Net-(JP16-Pad1)") (class "Default")
      (node (ref "JP16") (pin "1") (pinfunction "1_1") (pintype "passive"))
      (node (ref "R176") (pin "2") (pinfunction "2_2") (pintype "passive"))
    )
    (net (code "770") (name "Net-(JP17-Pad3)") (class "Default")
      (node (ref "JP17") (pin "3") (pinfunction "3_3") (pintype "passive"))
      (node (ref "R167") (pin "1") (pinfunction "1_1") (pintype "passive"))
      (node (ref "R168") (pin "1") (pinfunction "1_1") (pintype "passive"))
    )
    (net (code "771") (name "Net-(JP20-Pad2)") (class "Default")
      (node (ref "JP20") (pin "2") (pinfunction "2_2") (pintype "passive"))
      (node (ref "R173") (pin "2") (pinfunction "2_2") (pintype "passive"))
      (node (ref "R174") (pin "2") (pinfunction "2_2") (pintype "passive"))
      (node (ref "SJ4") (pin "2") (pinfunction "2_2") (pintype "passive"))
    )
    (net (code "772") (name "Net-(JP21-Pad1)") (class "Default")
      (node (ref "JP21") (pin "1") (pinfunction "1_1") (pintype "passive"))
      (node (ref "R222") (pin "2") (pinfunction "2_2") (pintype "passive"))
    )
    (net (code "773") (name "Net-(JP22-Pad3)") (class "Default")
      (node (ref "JP22") (pin "3") (pinfunction "3_3") (pintype "passive"))
      (node (ref "R213") (pin "1") (pinfunction "1_1") (pintype "passive"))
      (node (ref "R214") (pin "1") (pinfunction "1_1") (pintype "passive"))
    )
    (net (code "774") (name "Net-(JP25-Pad2)") (class "Default")
      (node (ref "JP25") (pin "2") (pinfunction "2_2") (pintype "passive"))
      (node (ref "R219") (pin "2") (pinfunction "2_2") (pintype "passive"))
      (node (ref "R220") (pin "2") (pinfunction "2_2") (pintype "passive"))
      (node (ref "SJ5") (pin "2") (pinfunction "2_2") (pintype "passive"))
    )
    (net (code "775") (name "Net-(JP26-Pad1)") (class "Default")
      (node (ref "JP26") (pin "1") (pinfunction "1_1") (pintype "passive"))
      (node (ref "R268") (pin "2") (pinfunction "2_2") (pintype "passive"))
    )
    (net (code "776") (name "Net-(JP27-Pad3)") (class "Default")
      (node (ref "JP27") (pin "3") (pinfunction "3_3") (pintype "passive"))
      (node (ref "R259") (pin "1") (pinfunction "1_1") (pintype "passive"))
      (node (ref "R260") (pin "1") (pinfunction "1_1") (pintype "passive"))
    )
    (net (code "777") (name "Net-(JP30-Pad2)") (class "Default")
      (node (ref "JP30") (pin "2") (pinfunction "2_2") (pintype "passive"))
      (node (ref "R265") (pin "2") (pinfunction "2_2") (pintype "passive"))
      (node (ref "R266") (pin "2") (pinfunction "2_2") (pintype "passive"))
      (node (ref "SJ6") (pin "2") (pinfunction "2_2") (pintype "passive"))
    )
    (net (code "778") (name "Net-(JP31-Pad1)") (class "Default")
      (node (ref "JP31") (pin "1") (pinfunction "1_1") (pintype "passive"))
      (node (ref "R314") (pin "2") (pinfunction "2_2") (pintype "passive"))
    )
    (net (code "779") (name "Net-(JP32-Pad3)") (class "Default")
      (node (ref "JP32") (pin "3") (pinfunction "3_3") (pintype "passive"))
      (node (ref "R305") (pin "1") (pinfunction "1_1") (pintype "passive"))
      (node (ref "R306") (pin "1") (pinfunction "1_1") (pintype "passive"))
    )
    (net (code "780") (name "Net-(JP35-Pad2)") (class "Default")
      (node (ref "JP35") (pin "2") (pinfunction "2_2") (pintype "passive"))
      (node (ref "R311") (pin "2") (pinfunction "2_2") (pintype "passive"))
      (node (ref "R312") (pin "2") (pinfunction "2_2") (pintype "passive"))
      (node (ref "SJ7") (pin "2") (pinfunction "2_2") (pintype "passive"))
    )
    (net (code "781") (name "Net-(JP36-Pad1)") (class "Default")
      (node (ref "JP36") (pin "1") (pinfunction "1_1") (pintype "passive"))
      (node (ref "R360") (pin "2") (pinfunction "2_2") (pintype "passive"))
    )
    (net (code "782") (name "Net-(JP37-Pad3)") (class "Default")
      (node (ref "JP37") (pin "3") (pinfunction "3_3") (pintype "passive"))
      (node (ref "R351") (pin "1") (pinfunction "1_1") (pintype "passive"))
      (node (ref "R352") (pin "1") (pinfunction "1_1") (pintype "passive"))
    )
    (net (code "783") (name "Net-(JP40-Pad2)") (class "Default")
      (node (ref "JP40") (pin "2") (pinfunction "2_2") (pintype "passive"))
      (node (ref "R357") (pin "2") (pinfunction "2_2") (pintype "passive"))
      (node (ref "R358") (pin "2") (pinfunction "2_2") (pintype "passive"))
      (node (ref "SJ8") (pin "2") (pinfunction "2_2") (pintype "passive"))
    )
    (net (code "784") (name "Net-(JP41-Pad1)") (class "Default")
      (node (ref "JP41") (pin "1") (pinfunction "1_1") (pintype "passive"))
      (node (ref "R406") (pin "2") (pinfunction "2_2") (pintype "passive"))
    )
    (net (code "785") (name "Net-(JP42-Pad3)") (class "Default")
      (node (ref "JP42") (pin "3") (pinfunction "3_3") (pintype "passive"))
      (node (ref "R397") (pin "1") (pinfunction "1_1") (pintype "passive"))
      (node (ref "R398") (pin "1") (pinfunction "1_1") (pintype "passive"))
    )
    (net (code "786") (name "Net-(JP45-Pad2)") (class "Default")
      (node (ref "JP45") (pin "2") (pinfunction "2_2") (pintype "passive"))
      (node (ref "R403") (pin "2") (pinfunction "2_2") (pintype "passive"))
      (node (ref "R404") (pin "2") (pinfunction "2_2") (pintype "passive"))
      (node (ref "SJ9") (pin "2") (pinfunction "2_2") (pintype "passive"))
    )
    (net (code "787") (name "Net-(JP46-Pad1)") (class "Default")
      (node (ref "JP46") (pin "1") (pinfunction "1_1") (pintype "passive"))
      (node (ref "R452") (pin "2") (pinfunction "2_2") (pintype "passive"))
    )
    (net (code "788") (name "Net-(JP47-Pad3)") (class "Default")
      (node (ref "JP47") (pin "3") (pinfunction "3_3") (pintype "passive"))
      (node (ref "R443") (pin "1") (pinfunction "1_1") (pintype "passive"))
      (node (ref "R444") (pin "1") (pinfunction "1_1") (pintype "passive"))
    )
    (net (code "789") (name "Net-(JP50-Pad2)") (class "Default")
      (node (ref "JP50") (pin "2") (pinfunction "2_2") (pintype "passive"))
      (node (ref "R449") (pin "2") (pinfunction "2_2") (pintype "passive"))
      (node (ref "R450") (pin "2") (pinfunction "2_2") (pintype "passive"))
      (node (ref "SJ10") (pin "2") (pinfunction "2_2") (pintype "passive"))
    )
    (net (code "790") (name "Net-(JP51-Pad1)") (class "Default")
      (node (ref "JP51") (pin "1") (pinfunction "1_1") (pintype "passive"))
      (node (ref "R498") (pin "2") (pinfunction "2_2") (pintype "passive"))
    )
    (net (code "791") (name "Net-(JP52-Pad3)") (class "Default")
      (node (ref "JP52") (pin "3") (pinfunction "3_3") (pintype "passive"))
      (node (ref "R489") (pin "1") (pinfunction "1_1") (pintype "passive"))
      (node (ref "R490") (pin "1") (pinfunction "1_1") (pintype "passive"))
    )
    (net (code "792") (name "Net-(JP55-Pad2)") (class "Default")
      (node (ref "JP55") (pin "2") (pinfunction "2_2") (pintype "passive"))
      (node (ref "R495") (pin "2") (pinfunction "2_2") (pintype "passive"))
      (node (ref "R496") (pin "2") (pinfunction "2_2") (pintype "passive"))
      (node (ref "SJ11") (pin "2") (pinfunction "2_2") (pintype "passive"))
    )
    (net (code "793") (name "Net-(JP56-Pad1)") (class "Default")
      (node (ref "JP56") (pin "1") (pinfunction "1_1") (pintype "passive"))
      (node (ref "R544") (pin "2") (pinfunction "2_2") (pintype "passive"))
    )
    (net (code "794") (name "Net-(JP57-Pad3)") (class "Default")
      (node (ref "JP57") (pin "3") (pinfunction "3_3") (pintype "passive"))
      (node (ref "R535") (pin "1") (pinfunction "1_1") (pintype "passive"))
      (node (ref "R536") (pin "1") (pinfunction "1_1") (pintype "passive"))
    )
    (net (code "795") (name "Net-(JP60-Pad2)") (class "Default")
      (node (ref "JP60") (pin "2") (pinfunction "2_2") (pintype "passive"))
      (node (ref "R541") (pin "2") (pinfunction "2_2") (pintype "passive"))
      (node (ref "R542") (pin "2") (pinfunction "2_2") (pintype "passive"))
      (node (ref "SJ12") (pin "2") (pinfunction "2_2") (pintype "passive"))
    )
    (net (code "796") (name "Net-(LED1-C)") (class "Default")
      (node (ref "LED1") (pin "K") (pinfunction "C_K") (pintype "passive"))
      (node (ref "R43") (pin "1") (pinfunction "1_1") (pintype "passive"))
    )
    (net (code "797") (name "Net-(LED2-PadA)") (class "Default")
      (node (ref "LED2") (pin "A") (pinfunction "A_A") (pintype "passive"))
      (node (ref "LED3") (pin "A") (pinfunction "A_A") (pintype "passive"))
      (node (ref "LED4") (pin "A") (pinfunction "A_A") (pintype "passive"))
      (node (ref "LED5") (pin "A") (pinfunction "A_A") (pintype "passive"))
      (node (ref "LED6") (pin "A") (pinfunction "A_A") (pintype "passive"))
      (node (ref "R42") (pin "1") (pinfunction "1_1") (pintype "passive"))
    )
    (net (code "798") (name "Net-(LED10-PadA)") (class "Default")
      (node (ref "LED10") (pin "A") (pinfunction "A_A") (pintype "passive"))
      (node (ref "LED12") (pin "A") (pinfunction "A_A") (pintype "passive"))
      (node (ref "LED7") (pin "A") (pinfunction "A_A") (pintype "passive"))
      (node (ref "LED8") (pin "A") (pinfunction "A_A") (pintype "passive"))
      (node (ref "LED9") (pin "A") (pinfunction "A_A") (pintype "passive"))
      (node (ref "R69") (pin "1") (pinfunction "1_1") (pintype "passive"))
    )
    (net (code "799") (name "Net-(LED11-C)") (class "Default")
      (node (ref "LED11") (pin "K") (pinfunction "C_K") (pintype "passive"))
      (node (ref "R68") (pin "1") (pinfunction "1_1") (pintype "passive"))
    )
    (net (code "800") (name "Net-(LED13-PadA)") (class "Default")
      (node (ref "LED13") (pin "A") (pinfunction "A_A") (pintype "passive"))
      (node (ref "LED14") (pin "A") (pinfunction "A_A") (pintype "passive"))
      (node (ref "LED15") (pin "A") (pinfunction "A_A") (pintype "passive"))
      (node (ref "LED16") (pin "A") (pinfunction "A_A") (pintype "passive"))
      (node (ref "LED18") (pin "A") (pinfunction "A_A") (pintype "passive"))
      (node (ref "R115") (pin "1") (pinfunction "1_1") (pintype "passive"))
    )
    (net (code "801") (name "Net-(LED17-C)") (class "Default")
      (node (ref "LED17") (pin "K") (pinfunction "C_K") (pintype "passive"))
      (node (ref "R114") (pin "1") (pinfunction "1_1") (pintype "passive"))
    )
    (net (code "802") (name "Net-(LED19-PadA)") (class "Default")
      (node (ref "LED19") (pin "A") (pinfunction "A_A") (pintype "passive"))
      (node (ref "LED20") (pin "A") (pinfunction "A_A") (pintype "passive"))
      (node (ref "LED21") (pin "A") (pinfunction "A_A") (pintype "passive"))
      (node (ref "LED22") (pin "A") (pinfunction "A_A") (pintype "passive"))
      (node (ref "LED24") (pin "A") (pinfunction "A_A") (pintype "passive"))
      (node (ref "R161") (pin "1") (pinfunction "1_1") (pintype "passive"))
    )
    (net (code "803") (name "Net-(LED23-C)") (class "Default")
      (node (ref "LED23") (pin "K") (pinfunction "C_K") (pintype "passive"))
      (node (ref "R160") (pin "1") (pinfunction "1_1") (pintype "passive"))
    )
    (net (code "804") (name "Net-(LED25-PadA)") (class "Default")
      (node (ref "LED25") (pin "A") (pinfunction "A_A") (pintype "passive"))
      (node (ref "LED26") (pin "A") (pinfunction "A_A") (pintype "passive"))
      (node (ref "LED27") (pin "A") (pinfunction "A_A") (pintype "passive"))
      (node (ref "LED28") (pin "A") (pinfunction "A_A") (pintype "passive"))
      (node (ref "LED30") (pin "A") (pinfunction "A_A") (pintype "passive"))
      (node (ref "R207") (pin "1") (pinfunction "1_1") (pintype "passive"))
    )
    (net (code "805") (name "Net-(LED29-C)") (class "Default")
      (node (ref "LED29") (pin "K") (pinfunction "C_K") (pintype "passive"))
      (node (ref "R206") (pin "1") (pinfunction "1_1") (pintype "passive"))
    )
    (net (code "806") (name "Net-(LED31-PadA)") (class "Default")
      (node (ref "LED31") (pin "A") (pinfunction "A_A") (pintype "passive"))
      (node (ref "LED32") (pin "A") (pinfunction "A_A") (pintype "passive"))
      (node (ref "LED33") (pin "A") (pinfunction "A_A") (pintype "passive"))
      (node (ref "LED34") (pin "A") (pinfunction "A_A") (pintype "passive"))
      (node (ref "LED36") (pin "A") (pinfunction "A_A") (pintype "passive"))
      (node (ref "R253") (pin "1") (pinfunction "1_1") (pintype "passive"))
    )
    (net (code "807") (name "Net-(LED35-C)") (class "Default")
      (node (ref "LED35") (pin "K") (pinfunction "C_K") (pintype "passive"))
      (node (ref "R252") (pin "1") (pinfunction "1_1") (pintype "passive"))
    )
    (net (code "808") (name "Net-(LED37-PadA)") (class "Default")
      (node (ref "LED37") (pin "A") (pinfunction "A_A") (pintype "passive"))
      (node (ref "LED38") (pin "A") (pinfunction "A_A") (pintype "passive"))
      (node (ref "LED39") (pin "A") (pinfunction "A_A") (pintype "passive"))
      (node (ref "LED40") (pin "A") (pinfunction "A_A") (pintype "passive"))
      (node (ref "LED42") (pin "A") (pinfunction "A_A") (pintype "passive"))
      (node (ref "R299") (pin "1") (pinfunction "1_1") (pintype "passive"))
    )
    (net (code "809") (name "Net-(LED41-C)") (class "Default")
      (node (ref "LED41") (pin "K") (pinfunction "C_K") (pintype "passive"))
      (node (ref "R298") (pin "1") (pinfunction "1_1") (pintype "passive"))
    )
    (net (code "810") (name "Net-(LED43-PadA)") (class "Default")
      (node (ref "LED43") (pin "A") (pinfunction "A_A") (pintype "passive"))
      (node (ref "LED44") (pin "A") (pinfunction "A_A") (pintype "passive"))
      (node (ref "LED45") (pin "A") (pinfunction "A_A") (pintype "passive"))
      (node (ref "LED46") (pin "A") (pinfunction "A_A") (pintype "passive"))
      (node (ref "LED48") (pin "A") (pinfunction "A_A") (pintype "passive"))
      (node (ref "R345") (pin "1") (pinfunction "1_1") (pintype "passive"))
    )
    (net (code "811") (name "Net-(LED47-C)") (class "Default")
      (node (ref "LED47") (pin "K") (pinfunction "C_K") (pintype "passive"))
      (node (ref "R344") (pin "1") (pinfunction "1_1") (pintype "passive"))
    )
    (net (code "812") (name "Net-(LED49-PadA)") (class "Default")
      (node (ref "LED49") (pin "A") (pinfunction "A_A") (pintype "passive"))
      (node (ref "LED50") (pin "A") (pinfunction "A_A") (pintype "passive"))
      (node (ref "LED51") (pin "A") (pinfunction "A_A") (pintype "passive"))
      (node (ref "LED52") (pin "A") (pinfunction "A_A") (pintype "passive"))
      (node (ref "LED54") (pin "A") (pinfunction "A_A") (pintype "passive"))
      (node (ref "R391") (pin "1") (pinfunction "1_1") (pintype "passive"))
    )
    (net (code "813") (name "Net-(LED53-C)") (class "Default")
      (node (ref "LED53") (pin "K") (pinfunction "C_K") (pintype "passive"))
      (node (ref "R390") (pin "1") (pinfunction "1_1") (pintype "passive"))
    )
    (net (code "814") (name "Net-(LED55-PadA)") (class "Default")
      (node (ref "LED55") (pin "A") (pinfunction "A_A") (pintype "passive"))
      (node (ref "LED56") (pin "A") (pinfunction "A_A") (pintype "passive"))
      (node (ref "LED57") (pin "A") (pinfunction "A_A") (pintype "passive"))
      (node (ref "LED58") (pin "A") (pinfunction "A_A") (pintype "passive"))
      (node (ref "LED60") (pin "A") (pinfunction "A_A") (pintype "passive"))
      (node (ref "R437") (pin "1") (pinfunction "1_1") (pintype "passive"))
    )
    (net (code "815") (name "Net-(LED59-C)") (class "Default")
      (node (ref "LED59") (pin "K") (pinfunction "C_K") (pintype "passive"))
      (node (ref "R436") (pin "1") (pinfunction "1_1") (pintype "passive"))
    )
    (net (code "816") (name "Net-(LED61-PadA)") (class "Default")
      (node (ref "LED61") (pin "A") (pinfunction "A_A") (pintype "passive"))
      (node (ref "LED62") (pin "A") (pinfunction "A_A") (pintype "passive"))
      (node (ref "LED63") (pin "A") (pinfunction "A_A") (pintype "passive"))
      (node (ref "LED64") (pin "A") (pinfunction "A_A") (pintype "passive"))
      (node (ref "LED66") (pin "A") (pinfunction "A_A") (pintype "passive"))
      (node (ref "R483") (pin "1") (pinfunction "1_1") (pintype "passive"))
    )
    (net (code "817") (name "Net-(LED65-C)") (class "Default")
      (node (ref "LED65") (pin "K") (pinfunction "C_K") (pintype "passive"))
      (node (ref "R482") (pin "1") (pinfunction "1_1") (pintype "passive"))
    )
    (net (code "818") (name "Net-(LED67-PadA)") (class "Default")
      (node (ref "LED67") (pin "A") (pinfunction "A_A") (pintype "passive"))
      (node (ref "LED68") (pin "A") (pinfunction "A_A") (pintype "passive"))
      (node (ref "LED69") (pin "A") (pinfunction "A_A") (pintype "passive"))
      (node (ref "LED70") (pin "A") (pinfunction "A_A") (pintype "passive"))
      (node (ref "LED72") (pin "A") (pinfunction "A_A") (pintype "passive"))
      (node (ref "R529") (pin "1") (pinfunction "1_1") (pintype "passive"))
    )
    (net (code "819") (name "Net-(LED71-C)") (class "Default")
      (node (ref "LED71") (pin "K") (pinfunction "C_K") (pintype "passive"))
      (node (ref "R528") (pin "1") (pinfunction "1_1") (pintype "passive"))
    )
    (net (code "820") (name "Net-(Q1-B)") (class "Default")
      (node (ref "Q1") (pin "1") (pinfunction "B_1") (pintype "passive"))
      (node (ref "Q2") (pin "1") (pinfunction "B_1") (pintype "passive"))
      (node (ref "Q2") (pin "2") (pinfunction "C_2") (pintype "passive"))
      (node (ref "R1") (pin "1") (pinfunction "1_1") (pintype "passive"))
      (node (ref "R3") (pin "1") (pinfunction "1_1") (pintype "passive"))
      (node (ref "R4") (pin "1") (pinfunction "1_1") (pintype "passive"))
      (node (ref "X2") (pin "2") (pinfunction "S_2") (pintype "passive"))
    )
    (net (code "821") (name "Net-(Q1-E)") (class "Default")
      (node (ref "Q1") (pin "3") (pinfunction "E_3") (pintype "passive"))
      (node (ref "R2") (pin "2") (pinfunction "2_2") (pintype "passive"))
    )
    (net (code "822") (name "Net-(Q2-E)") (class "Default")
      (node (ref "Q2") (pin "3") (pinfunction "E_3") (pintype "passive"))
      (node (ref "R6") (pin "2") (pinfunction "2_2") (pintype "passive"))
    )
    (net (code "823") (name "Net-(Q3-B)") (class "Default")
      (node (ref "Q3") (pin "1") (pinfunction "B_1") (pintype "passive"))
      (node (ref "R16") (pin "2") (pinfunction "2_2") (pintype "passive"))
    )
    (net (code "824") (name "Net-(Q3-C)") (class "Default")
      (node (ref "Q3") (pin "2") (pinfunction "C_2") (pintype "passive"))
      (node (ref "R15") (pin "2") (pinfunction "2_2") (pintype "passive"))
      (node (ref "R18") (pin "1") (pinfunction "1_1") (pintype "passive"))
    )
    (net (code "825") (name "Net-(Q4-B)") (class "Default")
      (node (ref "Q4") (pin "1") (pinfunction "B_1") (pintype "passive"))
      (node (ref "R28") (pin "2") (pinfunction "2_2") (pintype "passive"))
    )
    (net (code "826") (name "Net-(Q5-B)") (class "Default")
      (node (ref "Q5") (pin "1") (pinfunction "B_1") (pintype "passive"))
      (node (ref "R26") (pin "1") (pinfunction "1_1") (pintype "passive"))
    )
    (net (code "827") (name "Net-(Q7-D)") (class "Default")
      (node (ref "Q7") (pin "3") (pinfunction "D_3") (pintype "passive"))
      (node (ref "R38") (pin "2") (pinfunction "2_2") (pintype "passive"))
    )
    (net (code "828") (name "Net-(Q8-B)") (class "Default")
      (node (ref "Q8") (pin "1") (pinfunction "B_1") (pintype "passive"))
      (node (ref "R70") (pin "2") (pinfunction "2_2") (pintype "passive"))
    )
    (net (code "829") (name "Net-(Q9-E)") (class "Default")
      (node (ref "Q9") (pin "3") (pinfunction "E_3") (pintype "passive"))
      (node (ref "R71") (pin "2") (pinfunction "2_2") (pintype "passive"))
    )
    (net (code "830") (name "Net-(Q10-B)") (class "Default")
      (node (ref "Q10") (pin "1") (pinfunction "B_1") (pintype "passive"))
      (node (ref "Q9") (pin "1") (pinfunction "B_1") (pintype "passive"))
      (node (ref "Q9") (pin "2") (pinfunction "C_2") (pintype "passive"))
      (node (ref "R65") (pin "1") (pinfunction "1_1") (pintype "passive"))
      (node (ref "R66") (pin "1") (pinfunction "1_1") (pintype "passive"))
      (node (ref "R92") (pin "1") (pinfunction "1_1") (pintype "passive"))
      (node (ref "X6") (pin "2") (pinfunction "S_2") (pintype "passive"))
    )
    (net (code "831") (name "Net-(Q10-E)") (class "Default")
      (node (ref "Q10") (pin "3") (pinfunction "E_3") (pintype "passive"))
      (node (ref "R72") (pin "2") (pinfunction "2_2") (pintype "passive"))
    )
    (net (code "832") (name "Net-(Q11-B)") (class "Default")
      (node (ref "Q11") (pin "1") (pinfunction "B_1") (pintype "passive"))
      (node (ref "R63") (pin "1") (pinfunction "1_1") (pintype "passive"))
    )
    (net (code "833") (name "Net-(Q12-B)") (class "Default")
      (node (ref "Q12") (pin "1") (pinfunction "B_1") (pintype "passive"))
      (node (ref "R74") (pin "2") (pinfunction "2_2") (pintype "passive"))
    )
    (net (code "834") (name "Net-(Q12-C)") (class "Default")
      (node (ref "Q12") (pin "2") (pinfunction "C_2") (pintype "passive"))
      (node (ref "R67") (pin "2") (pinfunction "2_2") (pintype "passive"))
      (node (ref "R91") (pin "1") (pinfunction "1_1") (pintype "passive"))
    )
    (net (code "835") (name "Net-(Q13-D)") (class "Default")
      (node (ref "Q13") (pin "3") (pinfunction "D_3") (pintype "passive"))
      (node (ref "R75") (pin "2") (pinfunction "2_2") (pintype "passive"))
    )
    (net (code "836") (name "Net-(Q15-B)") (class "Default")
      (node (ref "Q15") (pin "1") (pinfunction "B_1") (pintype "passive"))
      (node (ref "R116") (pin "2") (pinfunction "2_2") (pintype "passive"))
    )
    (net (code "837") (name "Net-(Q16-B)") (class "Default")
      (node (ref "Q16") (pin "1") (pinfunction "B_1") (pintype "passive"))
      (node (ref "Q16") (pin "2") (pinfunction "C_2") (pintype "passive"))
      (node (ref "Q17") (pin "1") (pinfunction "B_1") (pintype "passive"))
      (node (ref "R111") (pin "1") (pinfunction "1_1") (pintype "passive"))
      (node (ref "R112") (pin "1") (pinfunction "1_1") (pintype "passive"))
      (node (ref "R138") (pin "1") (pinfunction "1_1") (pintype "passive"))
      (node (ref "X9") (pin "2") (pinfunction "S_2") (pintype "passive"))
    )
    (net (code "838") (name "Net-(Q16-E)") (class "Default")
      (node (ref "Q16") (pin "3") (pinfunction "E_3") (pintype "passive"))
      (node (ref "R117") (pin "2") (pinfunction "2_2") (pintype "passive"))
    )
    (net (code "839") (name "Net-(Q17-E)") (class "Default")
      (node (ref "Q17") (pin "3") (pinfunction "E_3") (pintype "passive"))
      (node (ref "R118") (pin "2") (pinfunction "2_2") (pintype "passive"))
    )
    (net (code "840") (name "Net-(Q18-B)") (class "Default")
      (node (ref "Q18") (pin "1") (pinfunction "B_1") (pintype "passive"))
      (node (ref "R109") (pin "1") (pinfunction "1_1") (pintype "passive"))
    )
    (net (code "841") (name "Net-(Q19-B)") (class "Default")
      (node (ref "Q19") (pin "1") (pinfunction "B_1") (pintype "passive"))
      (node (ref "R120") (pin "2") (pinfunction "2_2") (pintype "passive"))
    )
    (net (code "842") (name "Net-(Q19-C)") (class "Default")
      (node (ref "Q19") (pin "2") (pinfunction "C_2") (pintype "passive"))
      (node (ref "R113") (pin "2") (pinfunction "2_2") (pintype "passive"))
      (node (ref "R137") (pin "1") (pinfunction "1_1") (pintype "passive"))
    )
    (net (code "843") (name "Net-(Q20-D)") (class "Default")
      (node (ref "Q20") (pin "3") (pinfunction "D_3") (pintype "passive"))
      (node (ref "R121") (pin "2") (pinfunction "2_2") (pintype "passive"))
    )
    (net (code "844") (name "Net-(Q22-B)") (class "Default")
      (node (ref "Q22") (pin "1") (pinfunction "B_1") (pintype "passive"))
      (node (ref "R162") (pin "2") (pinfunction "2_2") (pintype "passive"))
    )
    (net (code "845") (name "Net-(Q23-B)") (class "Default")
      (node (ref "Q23") (pin "1") (pinfunction "B_1") (pintype "passive"))
      (node (ref "Q23") (pin "2") (pinfunction "C_2") (pintype "passive"))
      (node (ref "Q24") (pin "1") (pinfunction "B_1") (pintype "passive"))
      (node (ref "R157") (pin "1") (pinfunction "1_1") (pintype "passive"))
      (node (ref "R158") (pin "1") (pinfunction "1_1") (pintype "passive"))
      (node (ref "R184") (pin "1") (pinfunction "1_1") (pintype "passive"))
      (node (ref "X12") (pin "2") (pinfunction "S_2") (pintype "passive"))
    )
    (net (code "846") (name "Net-(Q23-E)") (class "Default")
      (node (ref "Q23") (pin "3") (pinfunction "E_3") (pintype "passive"))
      (node (ref "R163") (pin "2") (pinfunction "2_2") (pintype "passive"))
    )
    (net (code "847") (name "Net-(Q24-E)") (class "Default")
      (node (ref "Q24") (pin "3") (pinfunction "E_3") (pintype "passive"))
      (node (ref "R164") (pin "2") (pinfunction "2_2") (pintype "passive"))
    )
    (net (code "848") (name "Net-(Q25-B)") (class "Default")
      (node (ref "Q25") (pin "1") (pinfunction "B_1") (pintype "passive"))
      (node (ref "R155") (pin "1") (pinfunction "1_1") (pintype "passive"))
    )
    (net (code "849") (name "Net-(Q26-B)") (class "Default")
      (node (ref "Q26") (pin "1") (pinfunction "B_1") (pintype "passive"))
      (node (ref "R166") (pin "2") (pinfunction "2_2") (pintype "passive"))
    )
    (net (code "850") (name "Net-(Q26-C)") (class "Default")
      (node (ref "Q26") (pin "2") (pinfunction "C_2") (pintype "passive"))
      (node (ref "R159") (pin "2") (pinfunction "2_2") (pintype "passive"))
      (node (ref "R183") (pin "1") (pinfunction "1_1") (pintype "passive"))
    )
    (net (code "851") (name "Net-(Q27-D)") (class "Default")
      (node (ref "Q27") (pin "3") (pinfunction "D_3") (pintype "passive"))
      (node (ref "R167") (pin "2") (pinfunction "2_2") (pintype "passive"))
    )
    (net (code "852") (name "Net-(Q29-B)") (class "Default")
      (node (ref "Q29") (pin "1") (pinfunction "B_1") (pintype "passive"))
      (node (ref "R208") (pin "2") (pinfunction "2_2") (pintype "passive"))
    )
    (net (code "853") (name "Net-(Q30-B)") (class "Default")
      (node (ref "Q30") (pin "1") (pinfunction "B_1") (pintype "passive"))
      (node (ref "Q30") (pin "2") (pinfunction "C_2") (pintype "passive"))
      (node (ref "Q31") (pin "1") (pinfunction "B_1") (pintype "passive"))
      (node (ref "R203") (pin "1") (pinfunction "1_1") (pintype "passive"))
      (node (ref "R204") (pin "1") (pinfunction "1_1") (pintype "passive"))
      (node (ref "R230") (pin "1") (pinfunction "1_1") (pintype "passive"))
      (node (ref "X15") (pin "2") (pinfunction "S_2") (pintype "passive"))
    )
    (net (code "854") (name "Net-(Q30-E)") (class "Default")
      (node (ref "Q30") (pin "3") (pinfunction "E_3") (pintype "passive"))
      (node (ref "R209") (pin "2") (pinfunction "2_2") (pintype "passive"))
    )
    (net (code "855") (name "Net-(Q31-E)") (class "Default")
      (node (ref "Q31") (pin "3") (pinfunction "E_3") (pintype "passive"))
      (node (ref "R210") (pin "2") (pinfunction "2_2") (pintype "passive"))
    )
    (net (code "856") (name "Net-(Q32-B)") (class "Default")
      (node (ref "Q32") (pin "1") (pinfunction "B_1") (pintype "passive"))
      (node (ref "R201") (pin "1") (pinfunction "1_1") (pintype "passive"))
    )
    (net (code "857") (name "Net-(Q33-B)") (class "Default")
      (node (ref "Q33") (pin "1") (pinfunction "B_1") (pintype "passive"))
      (node (ref "R212") (pin "2") (pinfunction "2_2") (pintype "passive"))
    )
    (net (code "858") (name "Net-(Q33-C)") (class "Default")
      (node (ref "Q33") (pin "2") (pinfunction "C_2") (pintype "passive"))
      (node (ref "R205") (pin "2") (pinfunction "2_2") (pintype "passive"))
      (node (ref "R229") (pin "1") (pinfunction "1_1") (pintype "passive"))
    )
    (net (code "859") (name "Net-(Q34-D)") (class "Default")
      (node (ref "Q34") (pin "3") (pinfunction "D_3") (pintype "passive"))
      (node (ref "R213") (pin "2") (pinfunction "2_2") (pintype "passive"))
    )
    (net (code "860") (name "Net-(Q36-B)") (class "Default")
      (node (ref "Q36") (pin "1") (pinfunction "B_1") (pintype "passive"))
      (node (ref "R254") (pin "2") (pinfunction "2_2") (pintype "passive"))
    )
    (net (code "861") (name "Net-(Q37-B)") (class "Default")
      (node (ref "Q37") (pin "1") (pinfunction "B_1") (pintype "passive"))
      (node (ref "Q37") (pin "2") (pinfunction "C_2") (pintype "passive"))
      (node (ref "Q38") (pin "1") (pinfunction "B_1") (pintype "passive"))
      (node (ref "R249") (pin "1") (pinfunction "1_1") (pintype "passive"))
      (node (ref "R250") (pin "1") (pinfunction "1_1") (pintype "passive"))
      (node (ref "R276") (pin "1") (pinfunction "1_1") (pintype "passive"))
      (node (ref "X18") (pin "2") (pinfunction "S_2") (pintype "passive"))
    )
    (net (code "862") (name "Net-(Q37-E)") (class "Default")
      (node (ref "Q37") (pin "3") (pinfunction "E_3") (pintype "passive"))
      (node (ref "R255") (pin "2") (pinfunction "2_2") (pintype "passive"))
    )
    (net (code "863") (name "Net-(Q38-E)") (class "Default")
      (node (ref "Q38") (pin "3") (pinfunction "E_3") (pintype "passive"))
      (node (ref "R256") (pin "2") (pinfunction "2_2") (pintype "passive"))
    )
    (net (code "864") (name "Net-(Q39-B)") (class "Default")
      (node (ref "Q39") (pin "1") (pinfunction "B_1") (pintype "passive"))
      (node (ref "R247") (pin "1") (pinfunction "1_1") (pintype "passive"))
    )
    (net (code "865") (name "Net-(Q40-B)") (class "Default")
      (node (ref "Q40") (pin "1") (pinfunction "B_1") (pintype "passive"))
      (node (ref "R258") (pin "2") (pinfunction "2_2") (pintype "passive"))
    )
    (net (code "866") (name "Net-(Q40-C)") (class "Default")
      (node (ref "Q40") (pin "2") (pinfunction "C_2") (pintype "passive"))
      (node (ref "R251") (pin "2") (pinfunction "2_2") (pintype "passive"))
      (node (ref "R275") (pin "1") (pinfunction "1_1") (pintype "passive"))
    )
    (net (code "867") (name "Net-(Q41-D)") (class "Default")
      (node (ref "Q41") (pin "3") (pinfunction "D_3") (pintype "passive"))
      (node (ref "R259") (pin "2") (pinfunction "2_2") (pintype "passive"))
    )
    (net (code "868") (name "Net-(Q43-B)") (class "Default")
      (node (ref "Q43") (pin "1") (pinfunction "B_1") (pintype "passive"))
      (node (ref "R300") (pin "2") (pinfunction "2_2") (pintype "passive"))
    )
    (net (code "869") (name "Net-(Q44-B)") (class "Default")
      (node (ref "Q44") (pin "1") (pinfunction "B_1") (pintype "passive"))
      (node (ref "Q44") (pin "2") (pinfunction "C_2") (pintype "passive"))
      (node (ref "Q45") (pin "1") (pinfunction "B_1") (pintype "passive"))
      (node (ref "R295") (pin "1") (pinfunction "1_1") (pintype "passive"))
      (node (ref "R296") (pin "1") (pinfunction "1_1") (pintype "passive"))
      (node (ref "R322") (pin "1") (pinfunction "1_1") (pintype "passive"))
      (node (ref "X21") (pin "2") (pinfunction "S_2") (pintype "passive"))
    )
    (net (code "870") (name "Net-(Q44-E)") (class "Default")
      (node (ref "Q44") (pin "3") (pinfunction "E_3") (pintype "passive"))
      (node (ref "R301") (pin "2") (pinfunction "2_2") (pintype "passive"))
    )
    (net (code "871") (name "Net-(Q45-E)") (class "Default")
      (node (ref "Q45") (pin "3") (pinfunction "E_3") (pintype "passive"))
      (node (ref "R302") (pin "2") (pinfunction "2_2") (pintype "passive"))
    )
    (net (code "872") (name "Net-(Q46-B)") (class "Default")
      (node (ref "Q46") (pin "1") (pinfunction "B_1") (pintype "passive"))
      (node (ref "R293") (pin "1") (pinfunction "1_1") (pintype "passive"))
    )
    (net (code "873") (name "Net-(Q47-B)") (class "Default")
      (node (ref "Q47") (pin "1") (pinfunction "B_1") (pintype "passive"))
      (node (ref "R304") (pin "2") (pinfunction "2_2") (pintype "passive"))
    )
    (net (code "874") (name "Net-(Q47-C)") (class "Default")
      (node (ref "Q47") (pin "2") (pinfunction "C_2") (pintype "passive"))
      (node (ref "R297") (pin "2") (pinfunction "2_2") (pintype "passive"))
      (node (ref "R321") (pin "1") (pinfunction "1_1") (pintype "passive"))
    )
    (net (code "875") (name "Net-(Q48-D)") (class "Default")
      (node (ref "Q48") (pin "3") (pinfunction "D_3") (pintype "passive"))
      (node (ref "R305") (pin "2") (pinfunction "2_2") (pintype "passive"))
    )
    (net (code "876") (name "Net-(Q50-B)") (class "Default")
      (node (ref "Q50") (pin "1") (pinfunction "B_1") (pintype "passive"))
      (node (ref "R346") (pin "2") (pinfunction "2_2") (pintype "passive"))
    )
    (net (code "877") (name "Net-(Q51-B)") (class "Default")
      (node (ref "Q51") (pin "1") (pinfunction "B_1") (pintype "passive"))
      (node (ref "Q51") (pin "2") (pinfunction "C_2") (pintype "passive"))
      (node (ref "Q52") (pin "1") (pinfunction "B_1") (pintype "passive"))
      (node (ref "R341") (pin "1") (pinfunction "1_1") (pintype "passive"))
      (node (ref "R342") (pin "1") (pinfunction "1_1") (pintype "passive"))
      (node (ref "R368") (pin "1") (pinfunction "1_1") (pintype "passive"))
      (node (ref "X24") (pin "2") (pinfunction "S_2") (pintype "passive"))
    )
    (net (code "878") (name "Net-(Q51-E)") (class "Default")
      (node (ref "Q51") (pin "3") (pinfunction "E_3") (pintype "passive"))
      (node (ref "R347") (pin "2") (pinfunction "2_2") (pintype "passive"))
    )
    (net (code "879") (name "Net-(Q52-E)") (class "Default")
      (node (ref "Q52") (pin "3") (pinfunction "E_3") (pintype "passive"))
      (node (ref "R348") (pin "2") (pinfunction "2_2") (pintype "passive"))
    )
    (net (code "880") (name "Net-(Q53-B)") (class "Default")
      (node (ref "Q53") (pin "1") (pinfunction "B_1") (pintype "passive"))
      (node (ref "R339") (pin "1") (pinfunction "1_1") (pintype "passive"))
    )
    (net (code "881") (name "Net-(Q54-B)") (class "Default")
      (node (ref "Q54") (pin "1") (pinfunction "B_1") (pintype "passive"))
      (node (ref "R350") (pin "2") (pinfunction "2_2") (pintype "passive"))
    )
    (net (code "882") (name "Net-(Q54-C)") (class "Default")
      (node (ref "Q54") (pin "2") (pinfunction "C_2") (pintype "passive"))
      (node (ref "R343") (pin "2") (pinfunction "2_2") (pintype "passive"))
      (node (ref "R367") (pin "1") (pinfunction "1_1") (pintype "passive"))
    )
    (net (code "883") (name "Net-(Q55-D)") (class "Default")
      (node (ref "Q55") (pin "3") (pinfunction "D_3") (pintype "passive"))
      (node (ref "R351") (pin "2") (pinfunction "2_2") (pintype "passive"))
    )
    (net (code "884") (name "Net-(Q57-B)") (class "Default")
      (node (ref "Q57") (pin "1") (pinfunction "B_1") (pintype "passive"))
      (node (ref "R392") (pin "2") (pinfunction "2_2") (pintype "passive"))
    )
    (net (code "885") (name "Net-(Q58-B)") (class "Default")
      (node (ref "Q58") (pin "1") (pinfunction "B_1") (pintype "passive"))
      (node (ref "Q58") (pin "2") (pinfunction "C_2") (pintype "passive"))
      (node (ref "Q59") (pin "1") (pinfunction "B_1") (pintype "passive"))
      (node (ref "R387") (pin "1") (pinfunction "1_1") (pintype "passive"))
      (node (ref "R388") (pin "1") (pinfunction "1_1") (pintype "passive"))
      (node (ref "R414") (pin "1") (pinfunction "1_1") (pintype "passive"))
      (node (ref "X27") (pin "2") (pinfunction "S_2") (pintype "passive"))
    )
    (net (code "886") (name "Net-(Q58-E)") (class "Default")
      (node (ref "Q58") (pin "3") (pinfunction "E_3") (pintype "passive"))
      (node (ref "R393") (pin "2") (pinfunction "2_2") (pintype "passive"))
    )
    (net (code "887") (name "Net-(Q59-E)") (class "Default")
      (node (ref "Q59") (pin "3") (pinfunction "E_3") (pintype "passive"))
      (node (ref "R394") (pin "2") (pinfunction "2_2") (pintype "passive"))
    )
    (net (code "888") (name "Net-(Q60-B)") (class "Default")
      (node (ref "Q60") (pin "1") (pinfunction "B_1") (pintype "passive"))
      (node (ref "R385") (pin "1") (pinfunction "1_1") (pintype "passive"))
    )
    (net (code "889") (name "Net-(Q61-B)") (class "Default")
      (node (ref "Q61") (pin "1") (pinfunction "B_1") (pintype "passive"))
      (node (ref "R396") (pin "2") (pinfunction "2_2") (pintype "passive"))
    )
    (net (code "890") (name "Net-(Q61-C)") (class "Default")
      (node (ref "Q61") (pin "2") (pinfunction "C_2") (pintype "passive"))
      (node (ref "R389") (pin "2") (pinfunction "2_2") (pintype "passive"))
      (node (ref "R413") (pin "1") (pinfunction "1_1") (pintype "passive"))
    )
    (net (code "891") (name "Net-(Q62-D)") (class "Default")
      (node (ref "Q62") (pin "3") (pinfunction "D_3") (pintype "passive"))
      (node (ref "R397") (pin "2") (pinfunction "2_2") (pintype "passive"))
    )
    (net (code "892") (name "Net-(Q64-B)") (class "Default")
      (node (ref "Q64") (pin "1") (pinfunction "B_1") (pintype "passive"))
      (node (ref "R438") (pin "2") (pinfunction "2_2") (pintype "passive"))
    )
    (net (code "893") (name "Net-(Q65-B)") (class "Default")
      (node (ref "Q65") (pin "1") (pinfunction "B_1") (pintype "passive"))
      (node (ref "Q65") (pin "2") (pinfunction "C_2") (pintype "passive"))
      (node (ref "Q66") (pin "1") (pinfunction "B_1") (pintype "passive"))
      (node (ref "R433") (pin "1") (pinfunction "1_1") (pintype "passive"))
      (node (ref "R434") (pin "1") (pinfunction "1_1") (pintype "passive"))
      (node (ref "R460") (pin "1") (pinfunction "1_1") (pintype "passive"))
      (node (ref "X30") (pin "2") (pinfunction "S_2") (pintype "passive"))
    )
    (net (code "894") (name "Net-(Q65-E)") (class "Default")
      (node (ref "Q65") (pin "3") (pinfunction "E_3") (pintype "passive"))
      (node (ref "R439") (pin "2") (pinfunction "2_2") (pintype "passive"))
    )
    (net (code "895") (name "Net-(Q66-E)") (class "Default")
      (node (ref "Q66") (pin "3") (pinfunction "E_3") (pintype "passive"))
      (node (ref "R440") (pin "2") (pinfunction "2_2") (pintype "passive"))
    )
    (net (code "896") (name "Net-(Q67-B)") (class "Default")
      (node (ref "Q67") (pin "1") (pinfunction "B_1") (pintype "passive"))
      (node (ref "R431") (pin "1") (pinfunction "1_1") (pintype "passive"))
    )
    (net (code "897") (name "Net-(Q68-B)") (class "Default")
      (node (ref "Q68") (pin "1") (pinfunction "B_1") (pintype "passive"))
      (node (ref "R442") (pin "2") (pinfunction "2_2") (pintype "passive"))
    )
    (net (code "898") (name "Net-(Q68-C)") (class "Default")
      (node (ref "Q68") (pin "2") (pinfunction "C_2") (pintype "passive"))
      (node (ref "R435") (pin "2") (pinfunction "2_2") (pintype "passive"))
      (node (ref "R459") (pin "1") (pinfunction "1_1") (pintype "passive"))
    )
    (net (code "899") (name "Net-(Q69-D)") (class "Default")
      (node (ref "Q69") (pin "3") (pinfunction "D_3") (pintype "passive"))
      (node (ref "R443") (pin "2") (pinfunction "2_2") (pintype "passive"))
    )
    (net (code "900") (name "Net-(Q71-B)") (class "Default")
      (node (ref "Q71") (pin "1") (pinfunction "B_1") (pintype "passive"))
      (node (ref "R484") (pin "2") (pinfunction "2_2") (pintype "passive"))
    )
    (net (code "901") (name "Net-(Q72-B)") (class "Default")
      (node (ref "Q72") (pin "1") (pinfunction "B_1") (pintype "passive"))
      (node (ref "Q72") (pin "2") (pinfunction "C_2") (pintype "passive"))
      (node (ref "Q73") (pin "1") (pinfunction "B_1") (pintype "passive"))
      (node (ref "R479") (pin "1") (pinfunction "1_1") (pintype "passive"))
      (node (ref "R480") (pin "1") (pinfunction "1_1") (pintype "passive"))
      (node (ref "R506") (pin "1") (pinfunction "1_1") (pintype "passive"))
      (node (ref "X33") (pin "2") (pinfunction "S_2") (pintype "passive"))
    )
    (net (code "902") (name "Net-(Q72-E)") (class "Default")
      (node (ref "Q72") (pin "3") (pinfunction "E_3") (pintype "passive"))
      (node (ref "R485") (pin "2") (pinfunction "2_2") (pintype "passive"))
    )
    (net (code "903") (name "Net-(Q73-E)") (class "Default")
      (node (ref "Q73") (pin "3") (pinfunction "E_3") (pintype "passive"))
      (node (ref "R486") (pin "2") (pinfunction "2_2") (pintype "passive"))
    )
    (net (code "904") (name "Net-(Q74-B)") (class "Default")
      (node (ref "Q74") (pin "1") (pinfunction "B_1") (pintype "passive"))
      (node (ref "R477") (pin "1") (pinfunction "1_1") (pintype "passive"))
    )
    (net (code "905") (name "Net-(Q75-B)") (class "Default")
      (node (ref "Q75") (pin "1") (pinfunction "B_1") (pintype "passive"))
      (node (ref "R488") (pin "2") (pinfunction "2_2") (pintype "passive"))
    )
    (net (code "906") (name "Net-(Q75-C)") (class "Default")
      (node (ref "Q75") (pin "2") (pinfunction "C_2") (pintype "passive"))
      (node (ref "R481") (pin "2") (pinfunction "2_2") (pintype "passive"))
      (node (ref "R505") (pin "1") (pinfunction "1_1") (pintype "passive"))
    )
    (net (code "907") (name "Net-(Q76-D)") (class "Default")
      (node (ref "Q76") (pin "3") (pinfunction "D_3") (pintype "passive"))
      (node (ref "R489") (pin "2") (pinfunction "2_2") (pintype "passive"))
    )
    (net (code "908") (name "Net-(Q78-B)") (class "Default")
      (node (ref "Q78") (pin "1") (pinfunction "B_1") (pintype "passive"))
      (node (ref "R530") (pin "2") (pinfunction "2_2") (pintype "passive"))
    )
    (net (code "909") (name "Net-(Q79-B)") (class "Default")
      (node (ref "Q79") (pin "1") (pinfunction "B_1") (pintype "passive"))
      (node (ref "Q79") (pin "2") (pinfunction "C_2") (pintype "passive"))
      (node (ref "Q80") (pin "1") (pinfunction "B_1") (pintype "passive"))
      (node (ref "R525") (pin "1") (pinfunction "1_1") (pintype "passive"))
      (node (ref "R526") (pin "1") (pinfunction "1_1") (pintype "passive"))
      (node (ref "R552") (pin "1") (pinfunction "1_1") (pintype "passive"))
      (node (ref "X36") (pin "2") (pinfunction "S_2") (pintype "passive"))
    )
    (net (code "910") (name "Net-(Q79-E)") (class "Default")
      (node (ref "Q79") (pin "3") (pinfunction "E_3") (pintype "passive"))
      (node (ref "R531") (pin "2") (pinfunction "2_2") (pintype "passive"))
    )
    (net (code "911") (name "Net-(Q80-E)") (class "Default")
      (node (ref "Q80") (pin "3") (pinfunction "E_3") (pintype "passive"))
      (node (ref "R532") (pin "2") (pinfunction "2_2") (pintype "passive"))
    )
    (net (code "912") (name "Net-(Q81-B)") (class "Default")
      (node (ref "Q81") (pin "1") (pinfunction "B_1") (pintype "passive"))
      (node (ref "R523") (pin "1") (pinfunction "1_1") (pintype "passive"))
    )
    (net (code "913") (name "Net-(Q82-B)") (class "Default")
      (node (ref "Q82") (pin "1") (pinfunction "B_1") (pintype "passive"))
      (node (ref "R534") (pin "2") (pinfunction "2_2") (pintype "passive"))
    )
    (net (code "914") (name "Net-(Q82-C)") (class "Default")
      (node (ref "Q82") (pin "2") (pinfunction "C_2") (pintype "passive"))
      (node (ref "R527") (pin "2") (pinfunction "2_2") (pintype "passive"))
      (node (ref "R551") (pin "1") (pinfunction "1_1") (pintype "passive"))
    )
    (net (code "915") (name "Net-(Q83-D)") (class "Default")
      (node (ref "Q83") (pin "3") (pinfunction "D_3") (pintype "passive"))
      (node (ref "R535") (pin "2") (pinfunction "2_2") (pintype "passive"))
    )
    (net (code "916") (name "Net-(R15-Pad1)") (class "Default")
      (node (ref "R15") (pin "1") (pinfunction "1_1") (pintype "passive"))
      (node (ref "X1") (pin "21") (pinfunction "21_21") (pintype "passive"))
    )
    (net (code "917") (name "Net-(R27-Pad2)") (class "Default")
      (node (ref "R27") (pin "2") (pinfunction "2_2") (pintype "passive"))
      (node (ref "R29") (pin "1") (pinfunction "1_1") (pintype "passive"))
    )
    (net (code "918") (name "Net-(R40-Pad2)") (class "Default")
      (node (ref "R40") (pin "2") (pinfunction "2_2") (pintype "passive"))
      (node (ref "X1") (pin "16") (pinfunction "16_16") (pintype "passive"))
    )
    (net (code "919") (name "Net-(R47-Pad2)") (class "Default")
      (node (ref "R47") (pin "2") (pinfunction "2_2") (pintype "passive"))
      (node (ref "R49") (pin "1") (pinfunction "1_1") (pintype "passive"))
    )
    (net (code "920") (name "Net-(R67-Pad1)") (class "Default")
      (node (ref "R67") (pin "1") (pinfunction "1_1") (pintype "passive"))
      (node (ref "X4") (pin "21") (pinfunction "21_21") (pintype "passive"))
    )
    (net (code "921") (name "Net-(R80-Pad2)") (class "Default")
      (node (ref "R80") (pin "2") (pinfunction "2_2") (pintype "passive"))
      (node (ref "X4") (pin "16") (pinfunction "16_16") (pintype "passive"))
    )
    (net (code "922") (name "Net-(R93-Pad2)") (class "Default")
      (node (ref "R93") (pin "2") (pinfunction "2_2") (pintype "passive"))
      (node (ref "R95") (pin "1") (pinfunction "1_1") (pintype "passive"))
    )
    (net (code "923") (name "Net-(R113-Pad1)") (class "Default")
      (node (ref "R113") (pin "1") (pinfunction "1_1") (pintype "passive"))
      (node (ref "X7") (pin "21") (pinfunction "21_21") (pintype "passive"))
    )
    (net (code "924") (name "Net-(R126-Pad2)") (class "Default")
      (node (ref "R126") (pin "2") (pinfunction "2_2") (pintype "passive"))
      (node (ref "X7") (pin "16") (pinfunction "16_16") (pintype "passive"))
    )
    (net (code "925") (name "Net-(R139-Pad2)") (class "Default")
      (node (ref "R139") (pin "2") (pinfunction "2_2") (pintype "passive"))
      (node (ref "R141") (pin "1") (pinfunction "1_1") (pintype "passive"))
    )
    (net (code "926") (name "Net-(R159-Pad1)") (class "Default")
      (node (ref "R159") (pin "1") (pinfunction "1_1") (pintype "passive"))
      (node (ref "X10") (pin "21") (pinfunction "21_21") (pintype "passive"))
    )
    (net (code "927") (name "Net-(R172-Pad2)") (class "Default")
      (node (ref "R172") (pin "2") (pinfunction "2_2") (pintype "passive"))
      (node (ref "X10") (pin "16") (pinfunction "16_16") (pintype "passive"))
    )
    (net (code "928") (name "Net-(R185-Pad2)") (class "Default")
      (node (ref "R185") (pin "2") (pinfunction "2_2") (pintype "passive"))
      (node (ref "R187") (pin "1") (pinfunction "1_1") (pintype "passive"))
    )
    (net (code "929") (name "Net-(R205-Pad1)") (class "Default")
      (node (ref "R205") (pin "1") (pinfunction "1_1") (pintype "passive"))
      (node (ref "X13") (pin "21") (pinfunction "21_21") (pintype "passive"))
    )
    (net (code "930") (name "Net-(R218-Pad2)") (class "Default")
      (node (ref "R218") (pin "2") (pinfunction "2_2") (pintype "passive"))
      (node (ref "X13") (pin "16") (pinfunction "16_16") (pintype "passive"))
    )
    (net (code "931") (name "Net-(R231-Pad2)") (class "Default")
      (node (ref "R231") (pin "2") (pinfunction "2_2") (pintype "passive"))
      (node (ref "R233") (pin "1") (pinfunction "1_1") (pintype "passive"))
    )
    (net (code "932") (name "Net-(R251-Pad1)") (class "Default")
      (node (ref "R251") (pin "1") (pinfunction "1_1") (pintype "passive"))
      (node (ref "X16") (pin "21") (pinfunction "21_21") (pintype "passive"))
    )
    (net (code "933") (name "Net-(R264-Pad2)") (class "Default")
      (node (ref "R264") (pin "2") (pinfunction "2_2") (pintype "passive"))
      (node (ref "X16") (pin "16") (pinfunction "16_16") (pintype "passive"))
    )
    (net (code "934") (name "Net-(R277-Pad2)") (class "Default")
      (node (ref "R277") (pin "2") (pinfunction "2_2") (pintype "passive"))
      (node (ref "R279") (pin "1") (pinfunction "1_1") (pintype "passive"))
    )
    (net (code "935") (name "Net-(R297-Pad1)") (class "Default")
      (node (ref "R297") (pin "1") (pinfunction "1_1") (pintype "passive"))
      (node (ref "X19") (pin "21") (pinfunction "21_21") (pintype "passive"))
    )
    (net (code "936") (name "Net-(R310-Pad2)") (class "Default")
      (node (ref "R310") (pin "2") (pinfunction "2_2") (pintype "passive"))
      (node (ref "X19") (pin "16") (pinfunction "16_16") (pintype "passive"))
    )
    (net (code "937") (name "Net-(R323-Pad2)") (class "Default")
      (node (ref "R323") (pin "2") (pinfunction "2_2") (pintype "passive"))
      (node (ref "R325") (pin "1") (pinfunction "1_1") (pintype "passive"))
    )
    (net (code "938") (name "Net-(R343-Pad1)") (class "Default")
      (node (ref "R343") (pin "1") (pinfunction "1_1") (pintype "passive"))
      (node (ref "X22") (pin "21") (pinfunction "21_21") (pintype "passive"))
    )
    (net (code "939") (name "Net-(R356-Pad2)") (class "Default")
      (node (ref "R356") (pin "2") (pinfunction "2_2") (pintype "passive"))
      (node (ref "X22") (pin "16") (pinfunction "16_16") (pintype "passive"))
    )
    (net (code "940") (name "Net-(R369-Pad2)") (class "Default")
      (node (ref "R369") (pin "2") (pinfunction "2_2") (pintype "passive"))
      (node (ref "R371") (pin "1") (pinfunction "1_1") (pintype "passive"))
    )
    (net (code "941") (name "Net-(R389-Pad1)") (class "Default")
      (node (ref "R389") (pin "1") (pinfunction "1_1") (pintype "passive"))
      (node (ref "X25") (pin "21") (pinfunction "21_21") (pintype "passive"))
    )
    (net (code "942") (name "Net-(R402-Pad2)") (class "Default")
      (node (ref "R402") (pin "2") (pinfunction "2_2") (pintype "passive"))
      (node (ref "X25") (pin "16") (pinfunction "16_16") (pintype "passive"))
    )
    (net (code "943") (name "Net-(R415-Pad2)") (class "Default")
      (node (ref "R415") (pin "2") (pinfunction "2_2") (pintype "passive"))
      (node (ref "R417") (pin "1") (pinfunction "1_1") (pintype "passive"))
    )
    (net (code "944") (name "Net-(R435-Pad1)") (class "Default")
      (node (ref "R435") (pin "1") (pinfunction "1_1") (pintype "passive"))
      (node (ref "X28") (pin "21") (pinfunction "21_21") (pintype "passive"))
    )
    (net (code "945") (name "Net-(R448-Pad2)") (class "Default")
      (node (ref "R448") (pin "2") (pinfunction "2_2") (pintype "passive"))
      (node (ref "X28") (pin "16") (pinfunction "16_16") (pintype "passive"))
    )
    (net (code "946") (name "Net-(R461-Pad2)") (class "Default")
      (node (ref "R461") (pin "2") (pinfunction "2_2") (pintype "passive"))
      (node (ref "R463") (pin "1") (pinfunction "1_1") (pintype "passive"))
    )
    (net (code "947") (name "Net-(R481-Pad1)") (class "Default")
      (node (ref "R481") (pin "1") (pinfunction "1_1") (pintype "passive"))
      (node (ref "X31") (pin "21") (pinfunction "21_21") (pintype "passive"))
    )
    (net (code "948") (name "Net-(R494-Pad2)") (class "Default")
      (node (ref "R494") (pin "2") (pinfunction "2_2") (pintype "passive"))
      (node (ref "X31") (pin "16") (pinfunction "16_16") (pintype "passive"))
    )
    (net (code "949") (name "Net-(R507-Pad2)") (class "Default")
      (node (ref "R507") (pin "2") (pinfunction "2_2") (pintype "passive"))
      (node (ref "R509") (pin "1") (pinfunction "1_1") (pintype "passive"))
    )
    (net (code "950") (name "Net-(R527-Pad1)") (class "Default")
      (node (ref "R527") (pin "1") (pinfunction "1_1") (pintype "passive"))
      (node (ref "X34") (pin "21") (pinfunction "21_21") (pintype "passive"))
    )
    (net (code "951") (name "Net-(R540-Pad2)") (class "Default")
      (node (ref "R540") (pin "2") (pinfunction "2_2") (pintype "passive"))
      (node (ref "X34") (pin "16") (pinfunction "16_16") (pintype "passive"))
    )
    (net (code "952") (name "VCC") (class "Default")
      (node (ref "6V") (pin "TP") (pinfunction "PP_TP") (pintype "input"))
      (node (ref "6V1") (pin "TP") (pinfunction "PP_TP") (pintype "input"))
      (node (ref "6V10") (pin "TP") (pinfunction "PP_TP") (pintype "input"))
      (node (ref "6V11") (pin "TP") (pinfunction "PP_TP") (pintype "input"))
      (node (ref "6V2") (pin "TP") (pinfunction "PP_TP") (pintype "input"))
      (node (ref "6V3") (pin "TP") (pinfunction "PP_TP") (pintype "input"))
      (node (ref "6V4") (pin "TP") (pinfunction "PP_TP") (pintype "input"))
      (node (ref "6V5") (pin "TP") (pinfunction "PP_TP") (pintype "input"))
      (node (ref "6V6") (pin "TP") (pinfunction "PP_TP") (pintype "input"))
      (node (ref "6V7") (pin "TP") (pinfunction "PP_TP") (pintype "input"))
      (node (ref "6V8") (pin "TP") (pinfunction "PP_TP") (pintype "input"))
      (node (ref "6V9") (pin "TP") (pinfunction "PP_TP") (pintype "input"))
      (node (ref "C103") (pin "1") (pinfunction "1_1") (pintype "passive"))
      (node (ref "C113") (pin "1") (pinfunction "1_1") (pintype "passive"))
      (node (ref "C13") (pin "1") (pinfunction "1_1") (pintype "passive"))
      (node (ref "C23") (pin "1") (pinfunction "1_1") (pintype "passive"))
      (node (ref "C33") (pin "1") (pinfunction "1_1") (pintype "passive"))
      (node (ref "C4") (pin "1") (pinfunction "1_1") (pintype "passive"))
      (node (ref "C43") (pin "1") (pinfunction "1_1") (pintype "passive"))
      (node (ref "C53") (pin "1") (pinfunction "1_1") (pintype "passive"))
      (node (ref "C63") (pin "1") (pinfunction "1_1") (pintype "passive"))
      (node (ref "C73") (pin "1") (pinfunction "1_1") (pintype "passive"))
      (node (ref "C83") (pin "1") (pinfunction "1_1") (pintype "passive"))
      (node (ref "C93") (pin "1") (pinfunction "1_1") (pintype "passive"))
      (node (ref "IC1") (pin "8") (pinfunction "V+_8") (pintype "power_in"))
      (node (ref "IC101") (pin "OUT") (pinfunction "OUT_OUT") (pintype "passive"))
      (node (ref "IC104") (pin "3") (pinfunction "V+_3") (pintype "power_in"))
      (node (ref "IC105") (pin "1") (pinfunction "OUT_1") (pintype "passive"))
      (node (ref "IC109") (pin "8") (pinfunction "V+_8") (pintype "power_in"))
      (node (ref "IC112") (pin "OUT") (pinfunction "OUT_OUT") (pintype "passive"))
      (node (ref "IC115") (pin "3") (pinfunction "V+_3") (pintype "power_in"))
      (node (ref "IC116") (pin "1") (pinfunction "OUT_1") (pintype "passive"))
      (node (ref "IC120") (pin "8") (pinfunction "V+_8") (pintype "power_in"))
      (node (ref "IC123") (pin "OUT") (pinfunction "OUT_OUT") (pintype "passive"))
      (node (ref "IC126") (pin "3") (pinfunction "V+_3") (pintype "power_in"))
      (node (ref "IC127") (pin "1") (pinfunction "OUT_1") (pintype "passive"))
      (node (ref "IC13") (pin "OUT") (pinfunction "OUT_OUT") (pintype "passive"))
      (node (ref "IC131") (pin "8") (pinfunction "V+_8") (pintype "power_in"))
      (node (ref "IC16") (pin "3") (pinfunction "V+_3") (pintype "power_in"))
      (node (ref "IC17") (pin "1") (pinfunction "OUT_1") (pintype "passive"))
      (node (ref "IC2") (pin "1") (pinfunction "OUT_1") (pintype "passive"))
      (node (ref "IC21") (pin "8") (pinfunction "V+_8") (pintype "power_in"))
      (node (ref "IC24") (pin "OUT") (pinfunction "OUT_OUT") (pintype "passive"))
      (node (ref "IC27") (pin "3") (pinfunction "V+_3") (pintype "power_in"))
      (node (ref "IC28") (pin "1") (pinfunction "OUT_1") (pintype "passive"))
      (node (ref "IC3") (pin "OUT") (pinfunction "OUT_OUT") (pintype "passive"))
      (node (ref "IC32") (pin "8") (pinfunction "V+_8") (pintype "power_in"))
      (node (ref "IC35") (pin "OUT") (pinfunction "OUT_OUT") (pintype "passive"))
      (node (ref "IC38") (pin "3") (pinfunction "V+_3") (pintype "power_in"))
      (node (ref "IC39") (pin "1") (pinfunction "OUT_1") (pintype "passive"))
      (node (ref "IC43") (pin "8") (pinfunction "V+_8") (pintype "power_in"))
      (node (ref "IC46") (pin "OUT") (pinfunction "OUT_OUT") (pintype "passive"))
      (node (ref "IC49") (pin "3") (pinfunction "V+_3") (pintype "power_in"))
      (node (ref "IC50") (pin "1") (pinfunction "OUT_1") (pintype "passive"))
      (node (ref "IC54") (pin "8") (pinfunction "V+_8") (pintype "power_in"))
      (node (ref "IC57") (pin "OUT") (pinfunction "OUT_OUT") (pintype "passive"))
      (node (ref "IC60") (pin "3") (pinfunction "V+_3") (pintype "power_in"))
      (node (ref "IC61") (pin "1") (pinfunction "OUT_1") (pintype "passive"))
      (node (ref "IC65") (pin "8") (pinfunction "V+_8") (pintype "power_in"))
      (node (ref "IC68") (pin "OUT") (pinfunction "OUT_OUT") (pintype "passive"))
      (node (ref "IC71") (pin "3") (pinfunction "V+_3") (pintype "power_in"))
      (node (ref "IC72") (pin "1") (pinfunction "OUT_1") (pintype "passive"))
      (node (ref "IC76") (pin "8") (pinfunction "V+_8") (pintype "power_in"))
      (node (ref "IC79") (pin "OUT") (pinfunction "OUT_OUT") (pintype "passive"))
      (node (ref "IC8") (pin "3") (pinfunction "V+_3") (pintype "power_in"))
      (node (ref "IC82") (pin "3") (pinfunction "V+_3") (pintype "power_in"))
      (node (ref "IC83") (pin "1") (pinfunction "OUT_1") (pintype "passive"))
      (node (ref "IC87") (pin "8") (pinfunction "V+_8") (pintype "power_in"))
      (node (ref "IC90") (pin "OUT") (pinfunction "OUT_OUT") (pintype "passive"))
      (node (ref "IC93") (pin "3") (pinfunction "V+_3") (pintype "power_in"))
      (node (ref "IC94") (pin "1") (pinfunction "OUT_1") (pintype "passive"))
      (node (ref "IC98") (pin "8") (pinfunction "V+_8") (pintype "power_in"))
      (node (ref "R102") (pin "2") (pinfunction "2_2") (pintype "passive"))
      (node (ref "R105") (pin "2") (pinfunction "2_2") (pintype "passive"))
      (node (ref "R108") (pin "1") (pinfunction "1_1") (pintype "passive"))
      (node (ref "R115") (pin "2") (pinfunction "2_2") (pintype "passive"))
      (node (ref "R13") (pin "2") (pinfunction "2_2") (pintype "passive"))
      (node (ref "R135") (pin "2") (pinfunction "2_2") (pintype "passive"))
      (node (ref "R148") (pin "2") (pinfunction "2_2") (pintype "passive"))
      (node (ref "R151") (pin "2") (pinfunction "2_2") (pintype "passive"))
      (node (ref "R154") (pin "1") (pinfunction "1_1") (pintype "passive"))
      (node (ref "R161") (pin "2") (pinfunction "2_2") (pintype "passive"))
      (node (ref "R181") (pin "2") (pinfunction "2_2") (pintype "passive"))
      (node (ref "R194") (pin "2") (pinfunction "2_2") (pintype "passive"))
      (node (ref "R197") (pin "2") (pinfunction "2_2") (pintype "passive"))
      (node (ref "R200") (pin "1") (pinfunction "1_1") (pintype "passive"))
      (node (ref "R207") (pin "2") (pinfunction "2_2") (pintype "passive"))
      (node (ref "R21") (pin "2") (pinfunction "2_2") (pintype "passive"))
      (node (ref "R227") (pin "2") (pinfunction "2_2") (pintype "passive"))
      (node (ref "R24") (pin "1") (pinfunction "1_1") (pintype "passive"))
      (node (ref "R240") (pin "2") (pinfunction "2_2") (pintype "passive"))
      (node (ref "R243") (pin "2") (pinfunction "2_2") (pintype "passive"))
      (node (ref "R246") (pin "1") (pinfunction "1_1") (pintype "passive"))
      (node (ref "R253") (pin "2") (pinfunction "2_2") (pintype "passive"))
      (node (ref "R273") (pin "2") (pinfunction "2_2") (pintype "passive"))
      (node (ref "R286") (pin "2") (pinfunction "2_2") (pintype "passive"))
      (node (ref "R289") (pin "2") (pinfunction "2_2") (pintype "passive"))
      (node (ref "R292") (pin "1") (pinfunction "1_1") (pintype "passive"))
      (node (ref "R299") (pin "2") (pinfunction "2_2") (pintype "passive"))
      (node (ref "R31") (pin "2") (pinfunction "2_2") (pintype "passive"))
      (node (ref "R319") (pin "2") (pinfunction "2_2") (pintype "passive"))
      (node (ref "R332") (pin "2") (pinfunction "2_2") (pintype "passive"))
      (node (ref "R335") (pin "2") (pinfunction "2_2") (pintype "passive"))
      (node (ref "R338") (pin "1") (pinfunction "1_1") (pintype "passive"))
      (node (ref "R345") (pin "2") (pinfunction "2_2") (pintype "passive"))
      (node (ref "R365") (pin "2") (pinfunction "2_2") (pintype "passive"))
      (node (ref "R378") (pin "2") (pinfunction "2_2") (pintype "passive"))
      (node (ref "R381") (pin "2") (pinfunction "2_2") (pintype "passive"))
      (node (ref "R384") (pin "1") (pinfunction "1_1") (pintype "passive"))
      (node (ref "R391") (pin "2") (pinfunction "2_2") (pintype "passive"))
      (node (ref "R411") (pin "2") (pinfunction "2_2") (pintype "passive"))
      (node (ref "R42") (pin "2") (pinfunction "2_2") (pintype "passive"))
      (node (ref "R424") (pin "2") (pinfunction "2_2") (pintype "passive"))
      (node (ref "R427") (pin "2") (pinfunction "2_2") (pintype "passive"))
      (node (ref "R430") (pin "1") (pinfunction "1_1") (pintype "passive"))
      (node (ref "R437") (pin "2") (pinfunction "2_2") (pintype "passive"))
      (node (ref "R457") (pin "2") (pinfunction "2_2") (pintype "passive"))
      (node (ref "R470") (pin "2") (pinfunction "2_2") (pintype "passive"))
      (node (ref "R473") (pin "2") (pinfunction "2_2") (pintype "passive"))
      (node (ref "R476") (pin "1") (pinfunction "1_1") (pintype "passive"))
      (node (ref "R483") (pin "2") (pinfunction "2_2") (pintype "passive"))
      (node (ref "R503") (pin "2") (pinfunction "2_2") (pintype "passive"))
      (node (ref "R516") (pin "2") (pinfunction "2_2") (pintype "passive"))
      (node (ref "R519") (pin "2") (pinfunction "2_2") (pintype "passive"))
      (node (ref "R522") (pin "1") (pinfunction "1_1") (pintype "passive"))
      (node (ref "R529") (pin "2") (pinfunction "2_2") (pintype "passive"))
      (node (ref "R549") (pin "2") (pinfunction "2_2") (pintype "passive"))
      (node (ref "R56") (pin "2") (pinfunction "2_2") (pintype "passive"))
      (node (ref "R59") (pin "2") (pinfunction "2_2") (pintype "passive"))
      (node (ref "R62") (pin "1") (pinfunction "1_1") (pintype "passive"))
      (node (ref "R69") (pin "2") (pinfunction "2_2") (pintype "passive"))
      (node (ref "R89") (pin "2") (pinfunction "2_2") (pintype "passive"))
    )
    (net (code "953") (name "unconnected-(IC5A-Q6-Pad7)") (class "Default")
      (node (ref "IC5") (pin "7") (pinfunction "Q6_7") (pintype "output"))
    )
    (net (code "954") (name "unconnected-(IC5A-Q7-Pad4)") (class "Default")
      (node (ref "IC5") (pin "4") (pinfunction "Q7_4") (pintype "output"))
    )
    (net (code "955") (name "unconnected-(IC5A-Q8-Pad9)") (class "Default")
      (node (ref "IC5") (pin "9") (pinfunction "Q8_9") (pintype "output"))
    )
    (net (code "956") (name "unconnected-(IC5A-Q9-Pad5)") (class "Default")
      (node (ref "IC5") (pin "5") (pinfunction "Q9_5") (pintype "output"))
    )
    (net (code "957") (name "unconnected-(IC8D-OUT-Pad13)") (class "Default")
      (node (ref "IC8") (pin "13") (pinfunction "OUT_13") (pintype "open_collector"))
    )
    (net (code "958") (name "unconnected-(IC10-DIS-Pad7)") (class "Default")
      (node (ref "IC10") (pin "7") (pinfunction "DIS_7") (pintype "input"))
    )
    (net (code "959") (name "unconnected-(IC11A-Q-Pad6)") (class "Default")
      (node (ref "IC11") (pin "6") (pinfunction "Q_6") (pintype "output"))
    )
    (net (code "960") (name "unconnected-(IC11A-T2-Pad2)") (class "Default")
      (node (ref "IC11") (pin "2") (pinfunction "T2_2") (pintype "input"))
    )
    (net (code "961") (name "unconnected-(IC11A-~{Q}-Pad7)") (class "Default")
      (node (ref "IC11") (pin "7") (pinfunction "~{Q}_7") (pintype "output"))
    )
    (net (code "962") (name "unconnected-(IC11B-Q-Pad10)") (class "Default")
      (node (ref "IC11") (pin "10") (pinfunction "Q_10") (pintype "output"))
    )
    (net (code "963") (name "unconnected-(IC12A-Q6-Pad7)") (class "Default")
      (node (ref "IC12") (pin "7") (pinfunction "Q6_7") (pintype "output"))
    )
    (net (code "964") (name "unconnected-(IC12A-Q7-Pad4)") (class "Default")
      (node (ref "IC12") (pin "4") (pinfunction "Q7_4") (pintype "output"))
    )
    (net (code "965") (name "unconnected-(IC12A-Q8-Pad9)") (class "Default")
      (node (ref "IC12") (pin "9") (pinfunction "Q8_9") (pintype "output"))
    )
    (net (code "966") (name "unconnected-(IC12A-Q9-Pad5)") (class "Default")
      (node (ref "IC12") (pin "5") (pinfunction "Q9_5") (pintype "output"))
    )
    (net (code "967") (name "unconnected-(IC16D-OUT-Pad13)") (class "Default")
      (node (ref "IC16") (pin "13") (pinfunction "OUT_13") (pintype "open_collector"))
    )
    (net (code "968") (name "unconnected-(IC18-DIS-Pad7)") (class "Default")
      (node (ref "IC18") (pin "7") (pinfunction "DIS_7") (pintype "input"))
    )
    (net (code "969") (name "unconnected-(IC19A-Q-Pad6)") (class "Default")
      (node (ref "IC19") (pin "6") (pinfunction "Q_6") (pintype "output"))
    )
    (net (code "970") (name "unconnected-(IC19A-T2-Pad2)") (class "Default")
      (node (ref "IC19") (pin "2") (pinfunction "T2_2") (pintype "input"))
    )
    (net (code "971") (name "unconnected-(IC19A-~{Q}-Pad7)") (class "Default")
      (node (ref "IC19") (pin "7") (pinfunction "~{Q}_7") (pintype "output"))
    )
    (net (code "972") (name "unconnected-(IC19B-Q-Pad10)") (class "Default")
      (node (ref "IC19") (pin "10") (pinfunction "Q_10") (pintype "output"))
    )
    (net (code "973") (name "unconnected-(IC23A-Q6-Pad7)") (class "Default")
      (node (ref "IC23") (pin "7") (pinfunction "Q6_7") (pintype "output"))
    )
    (net (code "974") (name "unconnected-(IC23A-Q7-Pad4)") (class "Default")
      (node (ref "IC23") (pin "4") (pinfunction "Q7_4") (pintype "output"))
    )
    (net (code "975") (name "unconnected-(IC23A-Q8-Pad9)") (class "Default")
      (node (ref "IC23") (pin "9") (pinfunction "Q8_9") (pintype "output"))
    )
    (net (code "976") (name "unconnected-(IC23A-Q9-Pad5)") (class "Default")
      (node (ref "IC23") (pin "5") (pinfunction "Q9_5") (pintype "output"))
    )
    (net (code "977") (name "unconnected-(IC27D-OUT-Pad13)") (class "Default")
      (node (ref "IC27") (pin "13") (pinfunction "OUT_13") (pintype "open_collector"))
    )
    (net (code "978") (name "unconnected-(IC29-DIS-Pad7)") (class "Default")
      (node (ref "IC29") (pin "7") (pinfunction "DIS_7") (pintype "input"))
    )
    (net (code "979") (name "unconnected-(IC30A-Q-Pad6)") (class "Default")
      (node (ref "IC30") (pin "6") (pinfunction "Q_6") (pintype "output"))
    )
    (net (code "980") (name "unconnected-(IC30A-T2-Pad2)") (class "Default")
      (node (ref "IC30") (pin "2") (pinfunction "T2_2") (pintype "input"))
    )
    (net (code "981") (name "unconnected-(IC30A-~{Q}-Pad7)") (class "Default")
      (node (ref "IC30") (pin "7") (pinfunction "~{Q}_7") (pintype "output"))
    )
    (net (code "982") (name "unconnected-(IC30B-Q-Pad10)") (class "Default")
      (node (ref "IC30") (pin "10") (pinfunction "Q_10") (pintype "output"))
    )
    (net (code "983") (name "unconnected-(IC34A-Q6-Pad7)") (class "Default")
      (node (ref "IC34") (pin "7") (pinfunction "Q6_7") (pintype "output"))
    )
    (net (code "984") (name "unconnected-(IC34A-Q7-Pad4)") (class "Default")
      (node (ref "IC34") (pin "4") (pinfunction "Q7_4") (pintype "output"))
    )
    (net (code "985") (name "unconnected-(IC34A-Q8-Pad9)") (class "Default")
      (node (ref "IC34") (pin "9") (pinfunction "Q8_9") (pintype "output"))
    )
    (net (code "986") (name "unconnected-(IC34A-Q9-Pad5)") (class "Default")
      (node (ref "IC34") (pin "5") (pinfunction "Q9_5") (pintype "output"))
    )
    (net (code "987") (name "unconnected-(IC38D-OUT-Pad13)") (class "Default")
      (node (ref "IC38") (pin "13") (pinfunction "OUT_13") (pintype "open_collector"))
    )
    (net (code "988") (name "unconnected-(IC40-DIS-Pad7)") (class "Default")
      (node (ref "IC40") (pin "7") (pinfunction "DIS_7") (pintype "input"))
    )
    (net (code "989") (name "unconnected-(IC41A-Q-Pad6)") (class "Default")
      (node (ref "IC41") (pin "6") (pinfunction "Q_6") (pintype "output"))
    )
    (net (code "990") (name "unconnected-(IC41A-T2-Pad2)") (class "Default")
      (node (ref "IC41") (pin "2") (pinfunction "T2_2") (pintype "input"))
    )
    (net (code "991") (name "unconnected-(IC41A-~{Q}-Pad7)") (class "Default")
      (node (ref "IC41") (pin "7") (pinfunction "~{Q}_7") (pintype "output"))
    )
    (net (code "992") (name "unconnected-(IC41B-Q-Pad10)") (class "Default")
      (node (ref "IC41") (pin "10") (pinfunction "Q_10") (pintype "output"))
    )
    (net (code "993") (name "unconnected-(IC45A-Q6-Pad7)") (class "Default")
      (node (ref "IC45") (pin "7") (pinfunction "Q6_7") (pintype "output"))
    )
    (net (code "994") (name "unconnected-(IC45A-Q7-Pad4)") (class "Default")
      (node (ref "IC45") (pin "4") (pinfunction "Q7_4") (pintype "output"))
    )
    (net (code "995") (name "unconnected-(IC45A-Q8-Pad9)") (class "Default")
      (node (ref "IC45") (pin "9") (pinfunction "Q8_9") (pintype "output"))
    )
    (net (code "996") (name "unconnected-(IC45A-Q9-Pad5)") (class "Default")
      (node (ref "IC45") (pin "5") (pinfunction "Q9_5") (pintype "output"))
    )
    (net (code "997") (name "unconnected-(IC49D-OUT-Pad13)") (class "Default")
      (node (ref "IC49") (pin "13") (pinfunction "OUT_13") (pintype "open_collector"))
    )
    (net (code "998") (name "unconnected-(IC51-DIS-Pad7)") (class "Default")
      (node (ref "IC51") (pin "7") (pinfunction "DIS_7") (pintype "input"))
    )
    (net (code "999") (name "unconnected-(IC52A-Q-Pad6)") (class "Default")
      (node (ref "IC52") (pin "6") (pinfunction "Q_6") (pintype "output"))
    )
    (net (code "1000") (name "unconnected-(IC52A-T2-Pad2)") (class "Default")
      (node (ref "IC52") (pin "2") (pinfunction "T2_2") (pintype "input"))
    )
    (net (code "1001") (name "unconnected-(IC52A-~{Q}-Pad7)") (class "Default")
      (node (ref "IC52") (pin "7") (pinfunction "~{Q}_7") (pintype "output"))
    )
    (net (code "1002") (name "unconnected-(IC52B-Q-Pad10)") (class "Default")
      (node (ref "IC52") (pin "10") (pinfunction "Q_10") (pintype "output"))
    )
    (net (code "1003") (name "unconnected-(IC56A-Q6-Pad7)") (class "Default")
      (node (ref "IC56") (pin "7") (pinfunction "Q6_7") (pintype "output"))
    )
    (net (code "1004") (name "unconnected-(IC56A-Q7-Pad4)") (class "Default")
      (node (ref "IC56") (pin "4") (pinfunction "Q7_4") (pintype "output"))
    )
    (net (code "1005") (name "unconnected-(IC56A-Q8-Pad9)") (class "Default")
      (node (ref "IC56") (pin "9") (pinfunction "Q8_9") (pintype "output"))
    )
    (net (code "1006") (name "unconnected-(IC56A-Q9-Pad5)") (class "Default")
      (node (ref "IC56") (pin "5") (pinfunction "Q9_5") (pintype "output"))
    )
    (net (code "1007") (name "unconnected-(IC60D-OUT-Pad13)") (class "Default")
      (node (ref "IC60") (pin "13") (pinfunction "OUT_13") (pintype "open_collector"))
    )
    (net (code "1008") (name "unconnected-(IC62-DIS-Pad7)") (class "Default")
      (node (ref "IC62") (pin "7") (pinfunction "DIS_7") (pintype "input"))
    )
    (net (code "1009") (name "unconnected-(IC63A-Q-Pad6)") (class "Default")
      (node (ref "IC63") (pin "6") (pinfunction "Q_6") (pintype "output"))
    )
    (net (code "1010") (name "unconnected-(IC63A-T2-Pad2)") (class "Default")
      (node (ref "IC63") (pin "2") (pinfunction "T2_2") (pintype "input"))
    )
    (net (code "1011") (name "unconnected-(IC63A-~{Q}-Pad7)") (class "Default")
      (node (ref "IC63") (pin "7") (pinfunction "~{Q}_7") (pintype "output"))
    )
    (net (code "1012") (name "unconnected-(IC63B-Q-Pad10)") (class "Default")
      (node (ref "IC63") (pin "10") (pinfunction "Q_10") (pintype "output"))
    )
    (net (code "1013") (name "unconnected-(IC67A-Q6-Pad7)") (class "Default")
      (node (ref "IC67") (pin "7") (pinfunction "Q6_7") (pintype "output"))
    )
    (net (code "1014") (name "unconnected-(IC67A-Q7-Pad4)") (class "Default")
      (node (ref "IC67") (pin "4") (pinfunction "Q7_4") (pintype "output"))
    )
    (net (code "1015") (name "unconnected-(IC67A-Q8-Pad9)") (class "Default")
      (node (ref "IC67") (pin "9") (pinfunction "Q8_9") (pintype "output"))
    )
    (net (code "1016") (name "unconnected-(IC67A-Q9-Pad5)") (class "Default")
      (node (ref "IC67") (pin "5") (pinfunction "Q9_5") (pintype "output"))
    )
    (net (code "1017") (name "unconnected-(IC71D-OUT-Pad13)") (class "Default")
      (node (ref "IC71") (pin "13") (pinfunction "OUT_13") (pintype "open_collector"))
    )
    (net (code "1018") (name "unconnected-(IC73-DIS-Pad7)") (class "Default")
      (node (ref "IC73") (pin "7") (pinfunction "DIS_7") (pintype "input"))
    )
    (net (code "1019") (name "unconnected-(IC74A-Q-Pad6)") (class "Default")
      (node (ref "IC74") (pin "6") (pinfunction "Q_6") (pintype "output"))
    )
    (net (code "1020") (name "unconnected-(IC74A-T2-Pad2)") (class "Default")
      (node (ref "IC74") (pin "2") (pinfunction "T2_2") (pintype "input"))
    )
    (net (code "1021") (name "unconnected-(IC74A-~{Q}-Pad7)") (class "Default")
      (node (ref "IC74") (pin "7") (pinfunction "~{Q}_7") (pintype "output"))
    )
    (net (code "1022") (name "unconnected-(IC74B-Q-Pad10)") (class "Default")
      (node (ref "IC74") (pin "10") (pinfunction "Q_10") (pintype "output"))
    )
    (net (code "1023") (name "unconnected-(IC78A-Q6-Pad7)") (class "Default")
      (node (ref "IC78") (pin "7") (pinfunction "Q6_7") (pintype "output"))
    )
    (net (code "1024") (name "unconnected-(IC78A-Q7-Pad4)") (class "Default")
      (node (ref "IC78") (pin "4") (pinfunction "Q7_4") (pintype "output"))
    )
    (net (code "1025") (name "unconnected-(IC78A-Q8-Pad9)") (class "Default")
      (node (ref "IC78") (pin "9") (pinfunction "Q8_9") (pintype "output"))
    )
    (net (code "1026") (name "unconnected-(IC78A-Q9-Pad5)") (class "Default")
      (node (ref "IC78") (pin "5") (pinfunction "Q9_5") (pintype "output"))
    )
    (net (code "1027") (name "unconnected-(IC82D-OUT-Pad13)") (class "Default")
      (node (ref "IC82") (pin "13") (pinfunction "OUT_13") (pintype "open_collector"))
    )
    (net (code "1028") (name "unconnected-(IC84-DIS-Pad7)") (class "Default")
      (node (ref "IC84") (pin "7") (pinfunction "DIS_7") (pintype "input"))
    )
    (net (code "1029") (name "unconnected-(IC85A-Q-Pad6)") (class "Default")
      (node (ref "IC85") (pin "6") (pinfunction "Q_6") (pintype "output"))
    )
    (net (code "1030") (name "unconnected-(IC85A-T2-Pad2)") (class "Default")
      (node (ref "IC85") (pin "2") (pinfunction "T2_2") (pintype "input"))
    )
    (net (code "1031") (name "unconnected-(IC85A-~{Q}-Pad7)") (class "Default")
      (node (ref "IC85") (pin "7") (pinfunction "~{Q}_7") (pintype "output"))
    )
    (net (code "1032") (name "unconnected-(IC85B-Q-Pad10)") (class "Default")
      (node (ref "IC85") (pin "10") (pinfunction "Q_10") (pintype "output"))
    )
    (net (code "1033") (name "unconnected-(IC89A-Q6-Pad7)") (class "Default")
      (node (ref "IC89") (pin "7") (pinfunction "Q6_7") (pintype "output"))
    )
    (net (code "1034") (name "unconnected-(IC89A-Q7-Pad4)") (class "Default")
      (node (ref "IC89") (pin "4") (pinfunction "Q7_4") (pintype "output"))
    )
    (net (code "1035") (name "unconnected-(IC89A-Q8-Pad9)") (class "Default")
      (node (ref "IC89") (pin "9") (pinfunction "Q8_9") (pintype "output"))
    )
    (net (code "1036") (name "unconnected-(IC89A-Q9-Pad5)") (class "Default")
      (node (ref "IC89") (pin "5") (pinfunction "Q9_5") (pintype "output"))
    )
    (net (code "1037") (name "unconnected-(IC93D-OUT-Pad13)") (class "Default")
      (node (ref "IC93") (pin "13") (pinfunction "OUT_13") (pintype "open_collector"))
    )
    (net (code "1038") (name "unconnected-(IC95-DIS-Pad7)") (class "Default")
      (node (ref "IC95") (pin "7") (pinfunction "DIS_7") (pintype "input"))
    )
    (net (code "1039") (name "unconnected-(IC96A-Q-Pad6)") (class "Default")
      (node (ref "IC96") (pin "6") (pinfunction "Q_6") (pintype "output"))
    )
    (net (code "1040") (name "unconnected-(IC96A-T2-Pad2)") (class "Default")
      (node (ref "IC96") (pin "2") (pinfunction "T2_2") (pintype "input"))
    )
    (net (code "1041") (name "unconnected-(IC96A-~{Q}-Pad7)") (class "Default")
      (node (ref "IC96") (pin "7") (pinfunction "~{Q}_7") (pintype "output"))
    )
    (net (code "1042") (name "unconnected-(IC96B-Q-Pad10)") (class "Default")
      (node (ref "IC96") (pin "10") (pinfunction "Q_10") (pintype "output"))
    )
    (net (code "1043") (name "unconnected-(IC100A-Q6-Pad7)") (class "Default")
      (node (ref "IC100") (pin "7") (pinfunction "Q6_7") (pintype "output"))
    )
    (net (code "1044") (name "unconnected-(IC100A-Q7-Pad4)") (class "Default")
      (node (ref "IC100") (pin "4") (pinfunction "Q7_4") (pintype "output"))
    )
    (net (code "1045") (name "unconnected-(IC100A-Q8-Pad9)") (class "Default")
      (node (ref "IC100") (pin "9") (pinfunction "Q8_9") (pintype "output"))
    )
    (net (code "1046") (name "unconnected-(IC100A-Q9-Pad5)") (class "Default")
      (node (ref "IC100") (pin "5") (pinfunction "Q9_5") (pintype "output"))
    )
    (net (code "1047") (name "unconnected-(IC104D-OUT-Pad13)") (class "Default")
      (node (ref "IC104") (pin "13") (pinfunction "OUT_13") (pintype "open_collector"))
    )
    (net (code "1048") (name "unconnected-(IC106-DIS-Pad7)") (class "Default")
      (node (ref "IC106") (pin "7") (pinfunction "DIS_7") (pintype "input"))
    )
    (net (code "1049") (name "unconnected-(IC107A-Q-Pad6)") (class "Default")
      (node (ref "IC107") (pin "6") (pinfunction "Q_6") (pintype "output"))
    )
    (net (code "1050") (name "unconnected-(IC107A-T2-Pad2)") (class "Default")
      (node (ref "IC107") (pin "2") (pinfunction "T2_2") (pintype "input"))
    )
    (net (code "1051") (name "unconnected-(IC107A-~{Q}-Pad7)") (class "Default")
      (node (ref "IC107") (pin "7") (pinfunction "~{Q}_7") (pintype "output"))
    )
    (net (code "1052") (name "unconnected-(IC107B-Q-Pad10)") (class "Default")
      (node (ref "IC107") (pin "10") (pinfunction "Q_10") (pintype "output"))
    )
    (net (code "1053") (name "unconnected-(IC111A-Q6-Pad7)") (class "Default")
      (node (ref "IC111") (pin "7") (pinfunction "Q6_7") (pintype "output"))
    )
    (net (code "1054") (name "unconnected-(IC111A-Q7-Pad4)") (class "Default")
      (node (ref "IC111") (pin "4") (pinfunction "Q7_4") (pintype "output"))
    )
    (net (code "1055") (name "unconnected-(IC111A-Q8-Pad9)") (class "Default")
      (node (ref "IC111") (pin "9") (pinfunction "Q8_9") (pintype "output"))
    )
    (net (code "1056") (name "unconnected-(IC111A-Q9-Pad5)") (class "Default")
      (node (ref "IC111") (pin "5") (pinfunction "Q9_5") (pintype "output"))
    )
    (net (code "1057") (name "unconnected-(IC115D-OUT-Pad13)") (class "Default")
      (node (ref "IC115") (pin "13") (pinfunction "OUT_13") (pintype "open_collector"))
    )
    (net (code "1058") (name "unconnected-(IC117-DIS-Pad7)") (class "Default")
      (node (ref "IC117") (pin "7") (pinfunction "DIS_7") (pintype "input"))
    )
    (net (code "1059") (name "unconnected-(IC118A-Q-Pad6)") (class "Default")
      (node (ref "IC118") (pin "6") (pinfunction "Q_6") (pintype "output"))
    )
    (net (code "1060") (name "unconnected-(IC118A-T2-Pad2)") (class "Default")
      (node (ref "IC118") (pin "2") (pinfunction "T2_2") (pintype "input"))
    )
    (net (code "1061") (name "unconnected-(IC118A-~{Q}-Pad7)") (class "Default")
      (node (ref "IC118") (pin "7") (pinfunction "~{Q}_7") (pintype "output"))
    )
    (net (code "1062") (name "unconnected-(IC118B-Q-Pad10)") (class "Default")
      (node (ref "IC118") (pin "10") (pinfunction "Q_10") (pintype "output"))
    )
    (net (code "1063") (name "unconnected-(IC122A-Q6-Pad7)") (class "Default")
      (node (ref "IC122") (pin "7") (pinfunction "Q6_7") (pintype "output"))
    )
    (net (code "1064") (name "unconnected-(IC122A-Q7-Pad4)") (class "Default")
      (node (ref "IC122") (pin "4") (pinfunction "Q7_4") (pintype "output"))
    )
    (net (code "1065") (name "unconnected-(IC122A-Q8-Pad9)") (class "Default")
      (node (ref "IC122") (pin "9") (pinfunction "Q8_9") (pintype "output"))
    )
    (net (code "1066") (name "unconnected-(IC122A-Q9-Pad5)") (class "Default")
      (node (ref "IC122") (pin "5") (pinfunction "Q9_5") (pintype "output"))
    )
    (net (code "1067") (name "unconnected-(IC126D-OUT-Pad13)") (class "Default")
      (node (ref "IC126") (pin "13") (pinfunction "OUT_13") (pintype "open_collector"))
    )
    (net (code "1068") (name "unconnected-(IC128-DIS-Pad7)") (class "Default")
      (node (ref "IC128") (pin "7") (pinfunction "DIS_7") (pintype "input"))
    )
    (net (code "1069") (name "unconnected-(IC129A-Q-Pad6)") (class "Default")
      (node (ref "IC129") (pin "6") (pinfunction "Q_6") (pintype "output"))
    )
    (net (code "1070") (name "unconnected-(IC129A-T2-Pad2)") (class "Default")
      (node (ref "IC129") (pin "2") (pinfunction "T2_2") (pintype "input"))
    )
    (net (code "1071") (name "unconnected-(IC129A-~{Q}-Pad7)") (class "Default")
      (node (ref "IC129") (pin "7") (pinfunction "~{Q}_7") (pintype "output"))
    )
    (net (code "1072") (name "unconnected-(IC129B-Q-Pad10)") (class "Default")
      (node (ref "IC129") (pin "10") (pinfunction "Q_10") (pintype "output"))
    )
    (net (code "1073") (name "unconnected-(X1-Pad20)") (class "Default")
      (node (ref "X1") (pin "20") (pinfunction "20_20") (pintype "passive"))
    )
    (net (code "1074") (name "unconnected-(X1-Pad24)") (class "Default")
      (node (ref "X1") (pin "24") (pinfunction "24_24") (pintype "passive"))
    )
    (net (code "1075") (name "unconnected-(X4-Pad20)") (class "Default")
      (node (ref "X4") (pin "20") (pinfunction "20_20") (pintype "passive"))
    )
    (net (code "1076") (name "unconnected-(X4-Pad24)") (class "Default")
      (node (ref "X4") (pin "24") (pinfunction "24_24") (pintype "passive"))
    )
    (net (code "1077") (name "unconnected-(X7-Pad20)") (class "Default")
      (node (ref "X7") (pin "20") (pinfunction "20_20") (pintype "passive"))
    )
    (net (code "1078") (name "unconnected-(X7-Pad24)") (class "Default")
      (node (ref "X7") (pin "24") (pinfunction "24_24") (pintype "passive"))
    )
    (net (code "1079") (name "unconnected-(X10-Pad20)") (class "Default")
      (node (ref "X10") (pin "20") (pinfunction "20_20") (pintype "passive"))
    )
    (net (code "1080") (name "unconnected-(X10-Pad24)") (class "Default")
      (node (ref "X10") (pin "24") (pinfunction "24_24") (pintype "passive"))
    )
    (net (code "1081") (name "unconnected-(X13-Pad20)") (class "Default")
      (node (ref "X13") (pin "20") (pinfunction "20_20") (pintype "passive"))
    )
    (net (code "1082") (name "unconnected-(X13-Pad24)") (class "Default")
      (node (ref "X13") (pin "24") (pinfunction "24_24") (pintype "passive"))
    )
    (net (code "1083") (name "unconnected-(X16-Pad20)") (class "Default")
      (node (ref "X16") (pin "20") (pinfunction "20_20") (pintype "passive"))
    )
    (net (code "1084") (name "unconnected-(X16-Pad24)") (class "Default")
      (node (ref "X16") (pin "24") (pinfunction "24_24") (pintype "passive"))
    )
    (net (code "1085") (name "unconnected-(X19-Pad20)") (class "Default")
      (node (ref "X19") (pin "20") (pinfunction "20_20") (pintype "passive"))
    )
    (net (code "1086") (name "unconnected-(X19-Pad24)") (class "Default")
      (node (ref "X19") (pin "24") (pinfunction "24_24") (pintype "passive"))
    )
    (net (code "1087") (name "unconnected-(X22-Pad20)") (class "Default")
      (node (ref "X22") (pin "20") (pinfunction "20_20") (pintype "passive"))
    )
    (net (code "1088") (name "unconnected-(X22-Pad24)") (class "Default")
      (node (ref "X22") (pin "24") (pinfunction "24_24") (pintype "passive"))
    )
    (net (code "1089") (name "unconnected-(X25-Pad20)") (class "Default")
      (node (ref "X25") (pin "20") (pinfunction "20_20") (pintype "passive"))
    )
    (net (code "1090") (name "unconnected-(X25-Pad24)") (class "Default")
      (node (ref "X25") (pin "24") (pinfunction "24_24") (pintype "passive"))
    )
    (net (code "1091") (name "unconnected-(X28-Pad20)") (class "Default")
      (node (ref "X28") (pin "20") (pinfunction "20_20") (pintype "passive"))
    )
    (net (code "1092") (name "unconnected-(X28-Pad24)") (class "Default")
      (node (ref "X28") (pin "24") (pinfunction "24_24") (pintype "passive"))
    )
    (net (code "1093") (name "unconnected-(X31-Pad20)") (class "Default")
      (node (ref "X31") (pin "20") (pinfunction "20_20") (pintype "passive"))
    )
    (net (code "1094") (name "unconnected-(X31-Pad24)") (class "Default")
      (node (ref "X31") (pin "24") (pinfunction "24_24") (pintype "passive"))
    )
    (net (code "1095") (name "unconnected-(X34-Pad20)") (class "Default")
      (node (ref "X34") (pin "20") (pinfunction "20_20") (pintype "passive"))
    )
    (net (code "1096") (name "unconnected-(X34-Pad24)") (class "Default")
      (node (ref "X34") (pin "24") (pinfunction "24_24") (pintype "passive"))
    )
  )
)
